# pdp8i.net
KiCad netlist of a schematic drawn in EAGLE
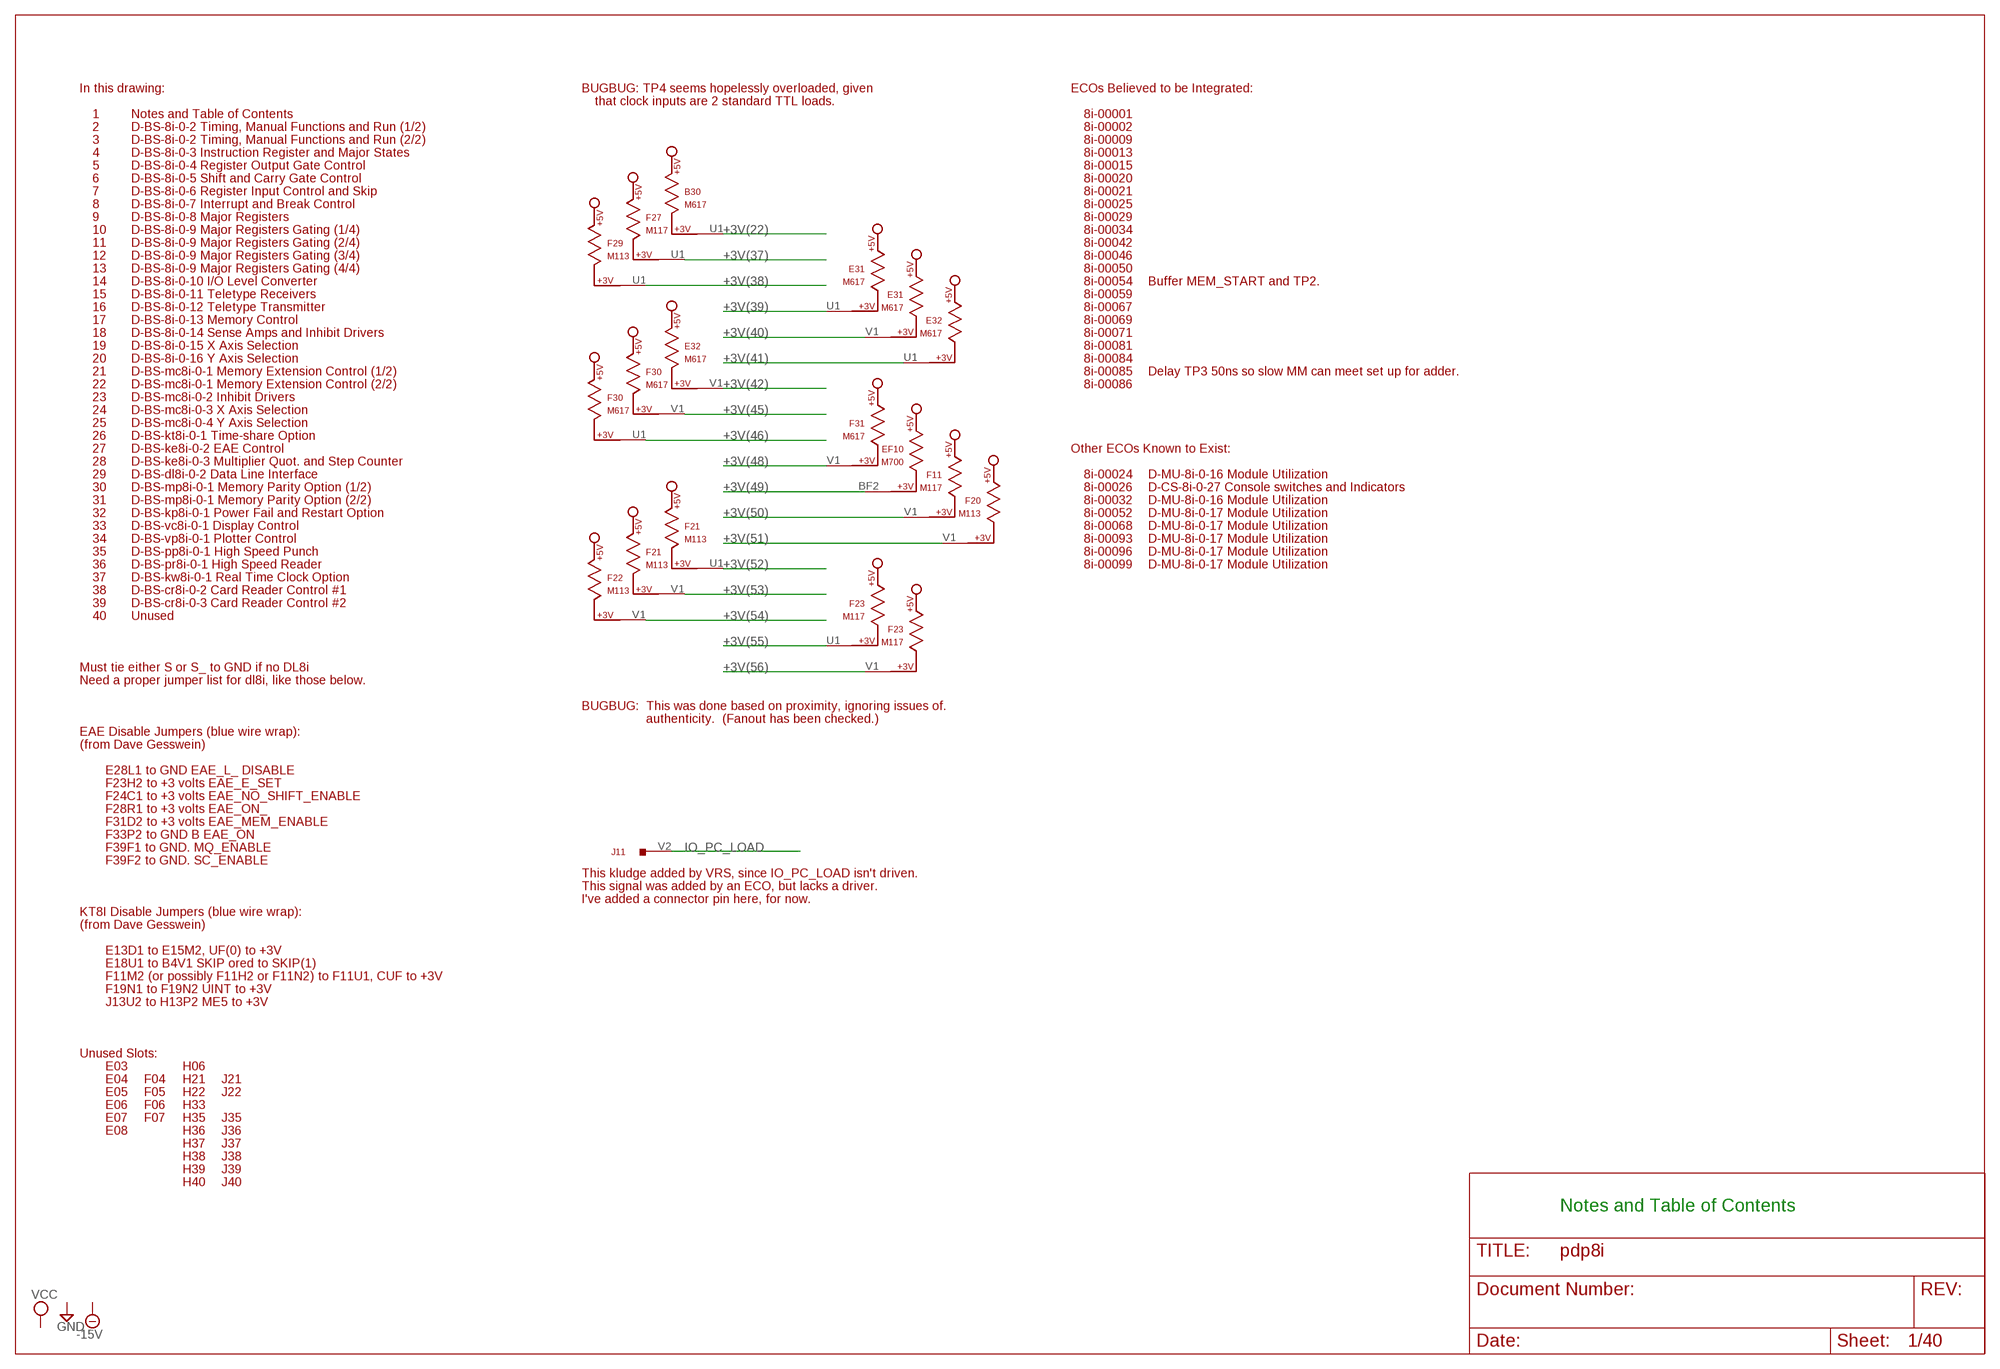
[diagram p0: schematic, sheet 1]
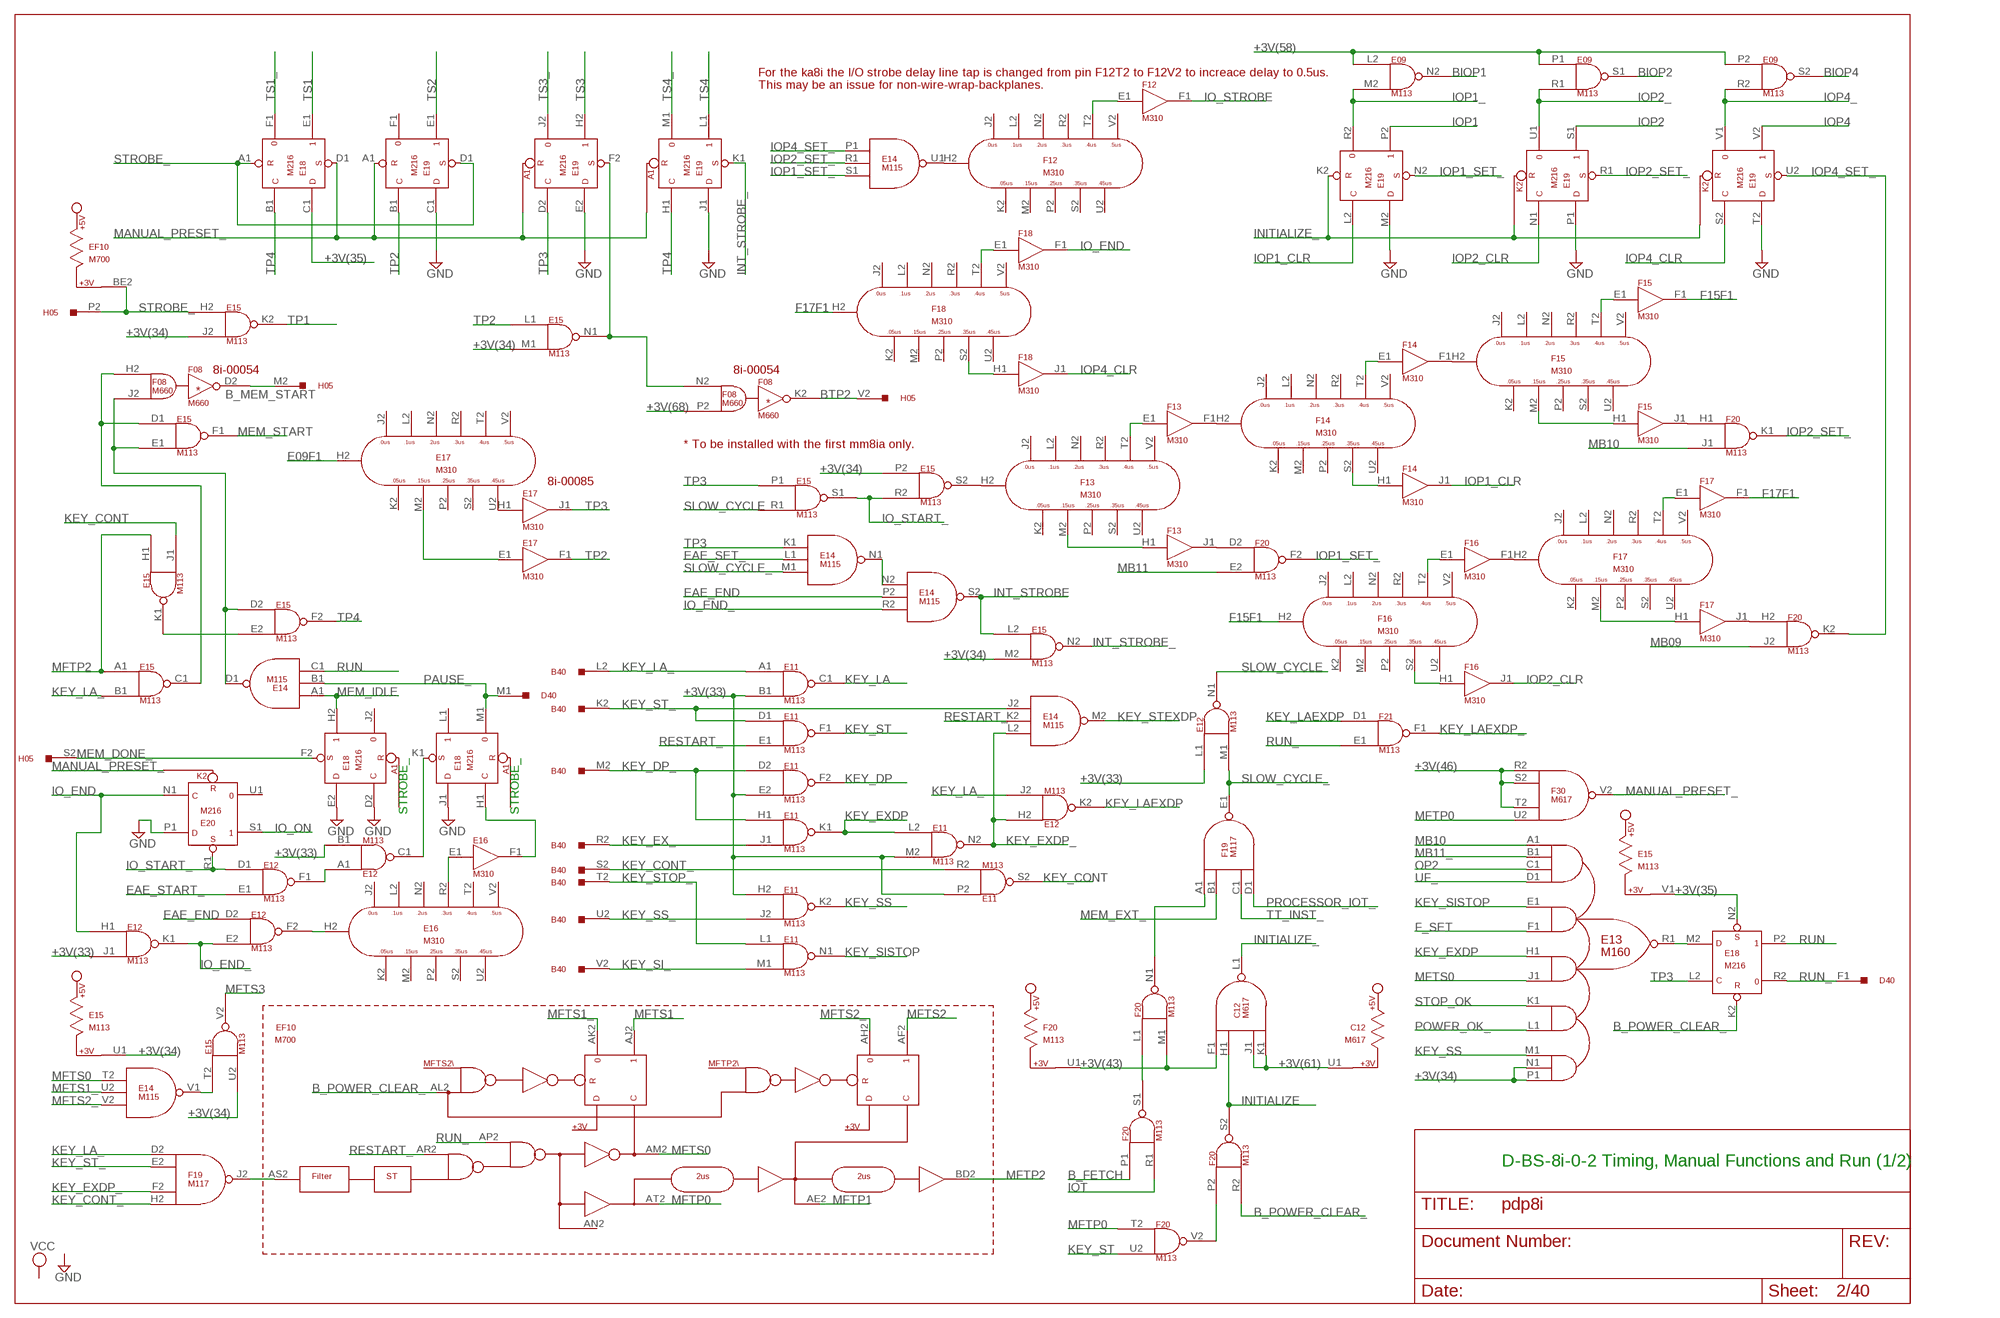
[diagram p1: schematic, sheet 2]
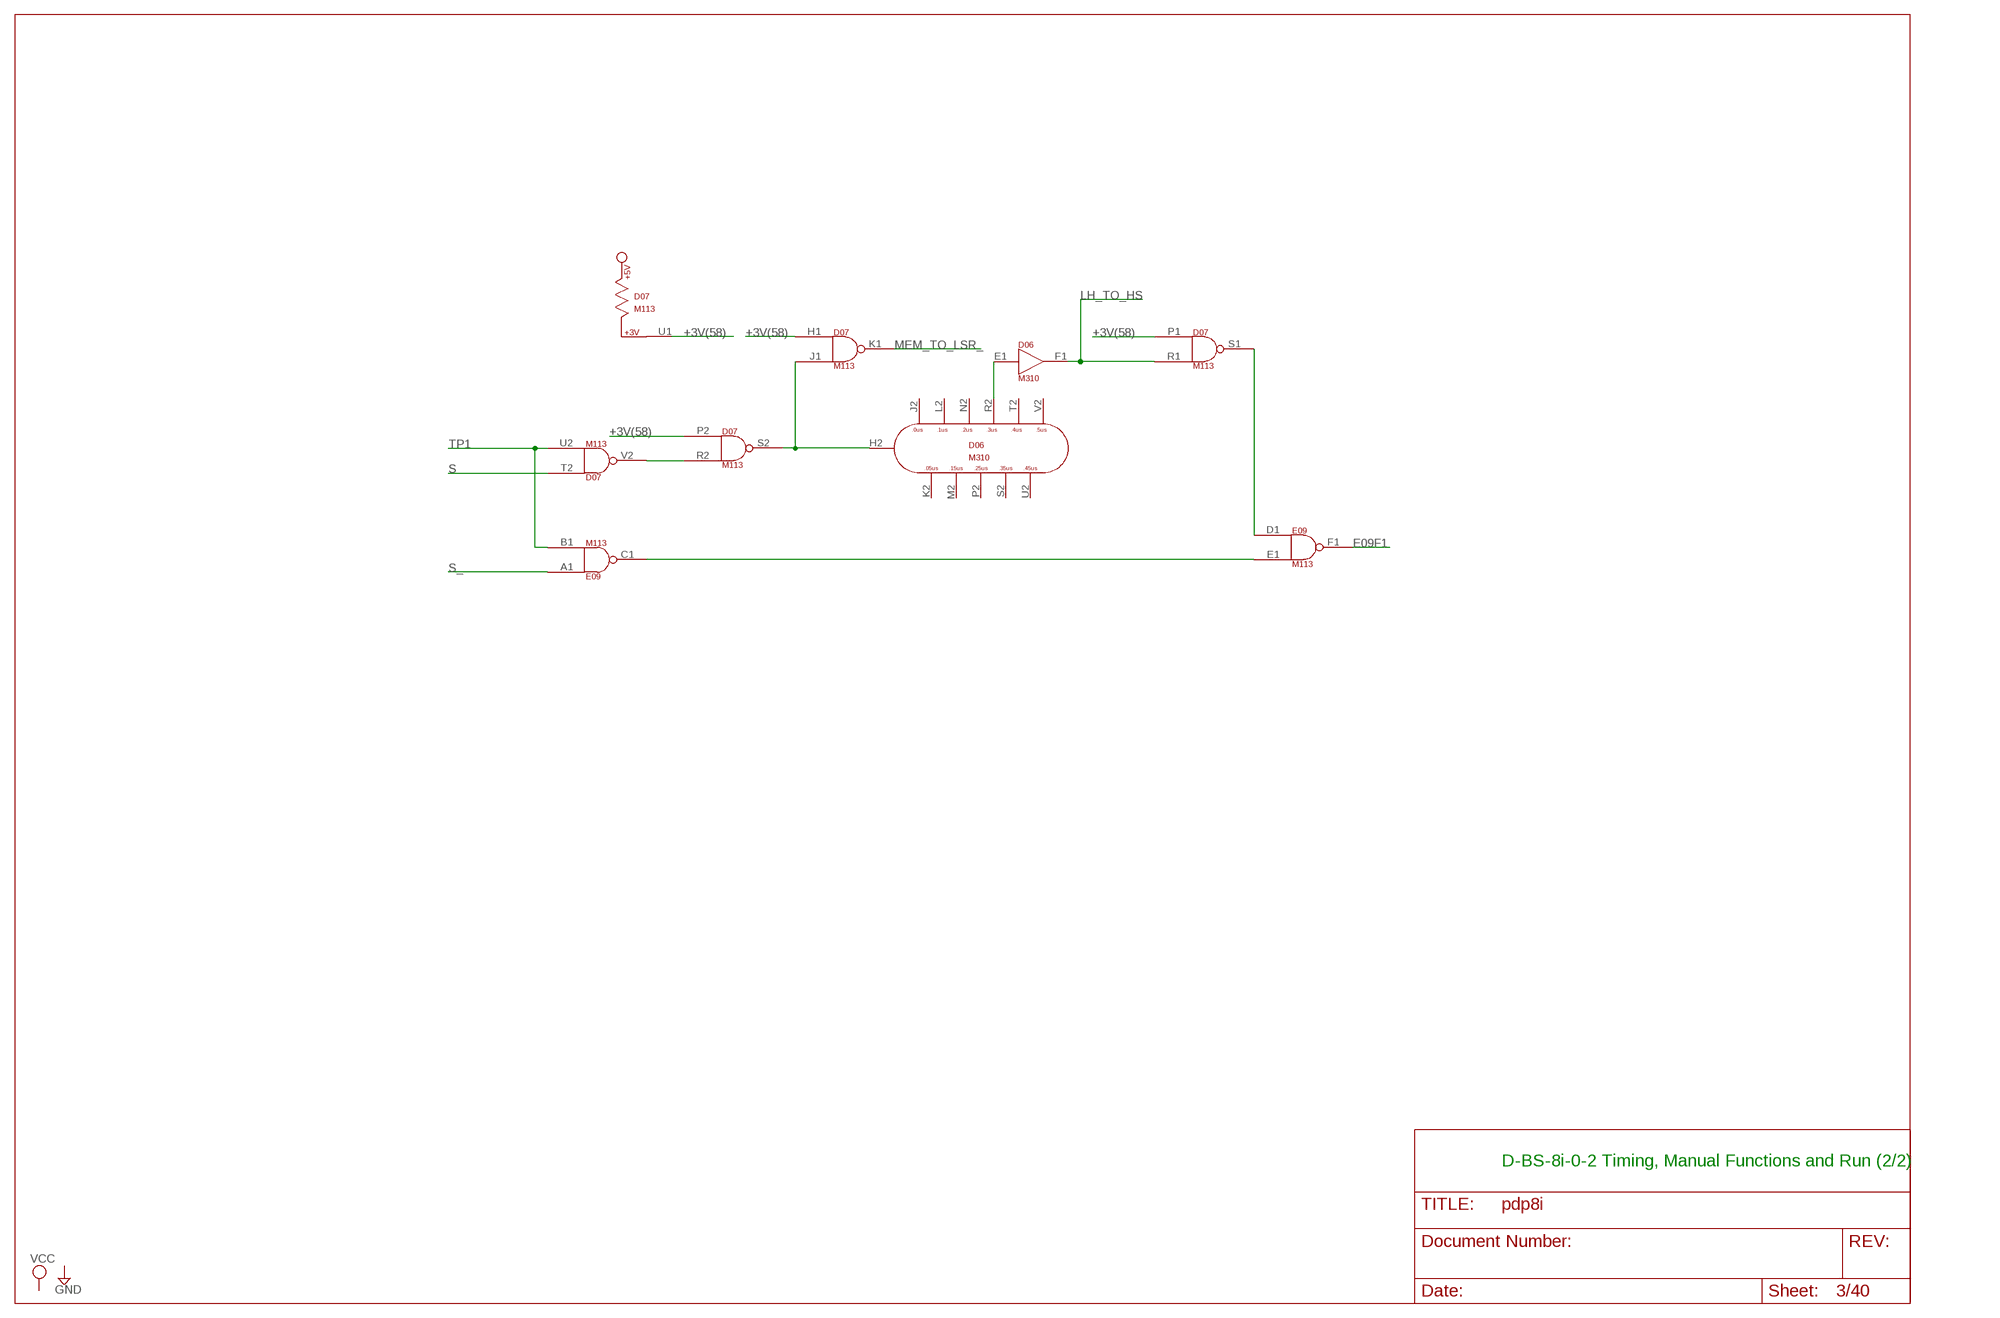
[diagram p2: schematic, sheet 3]
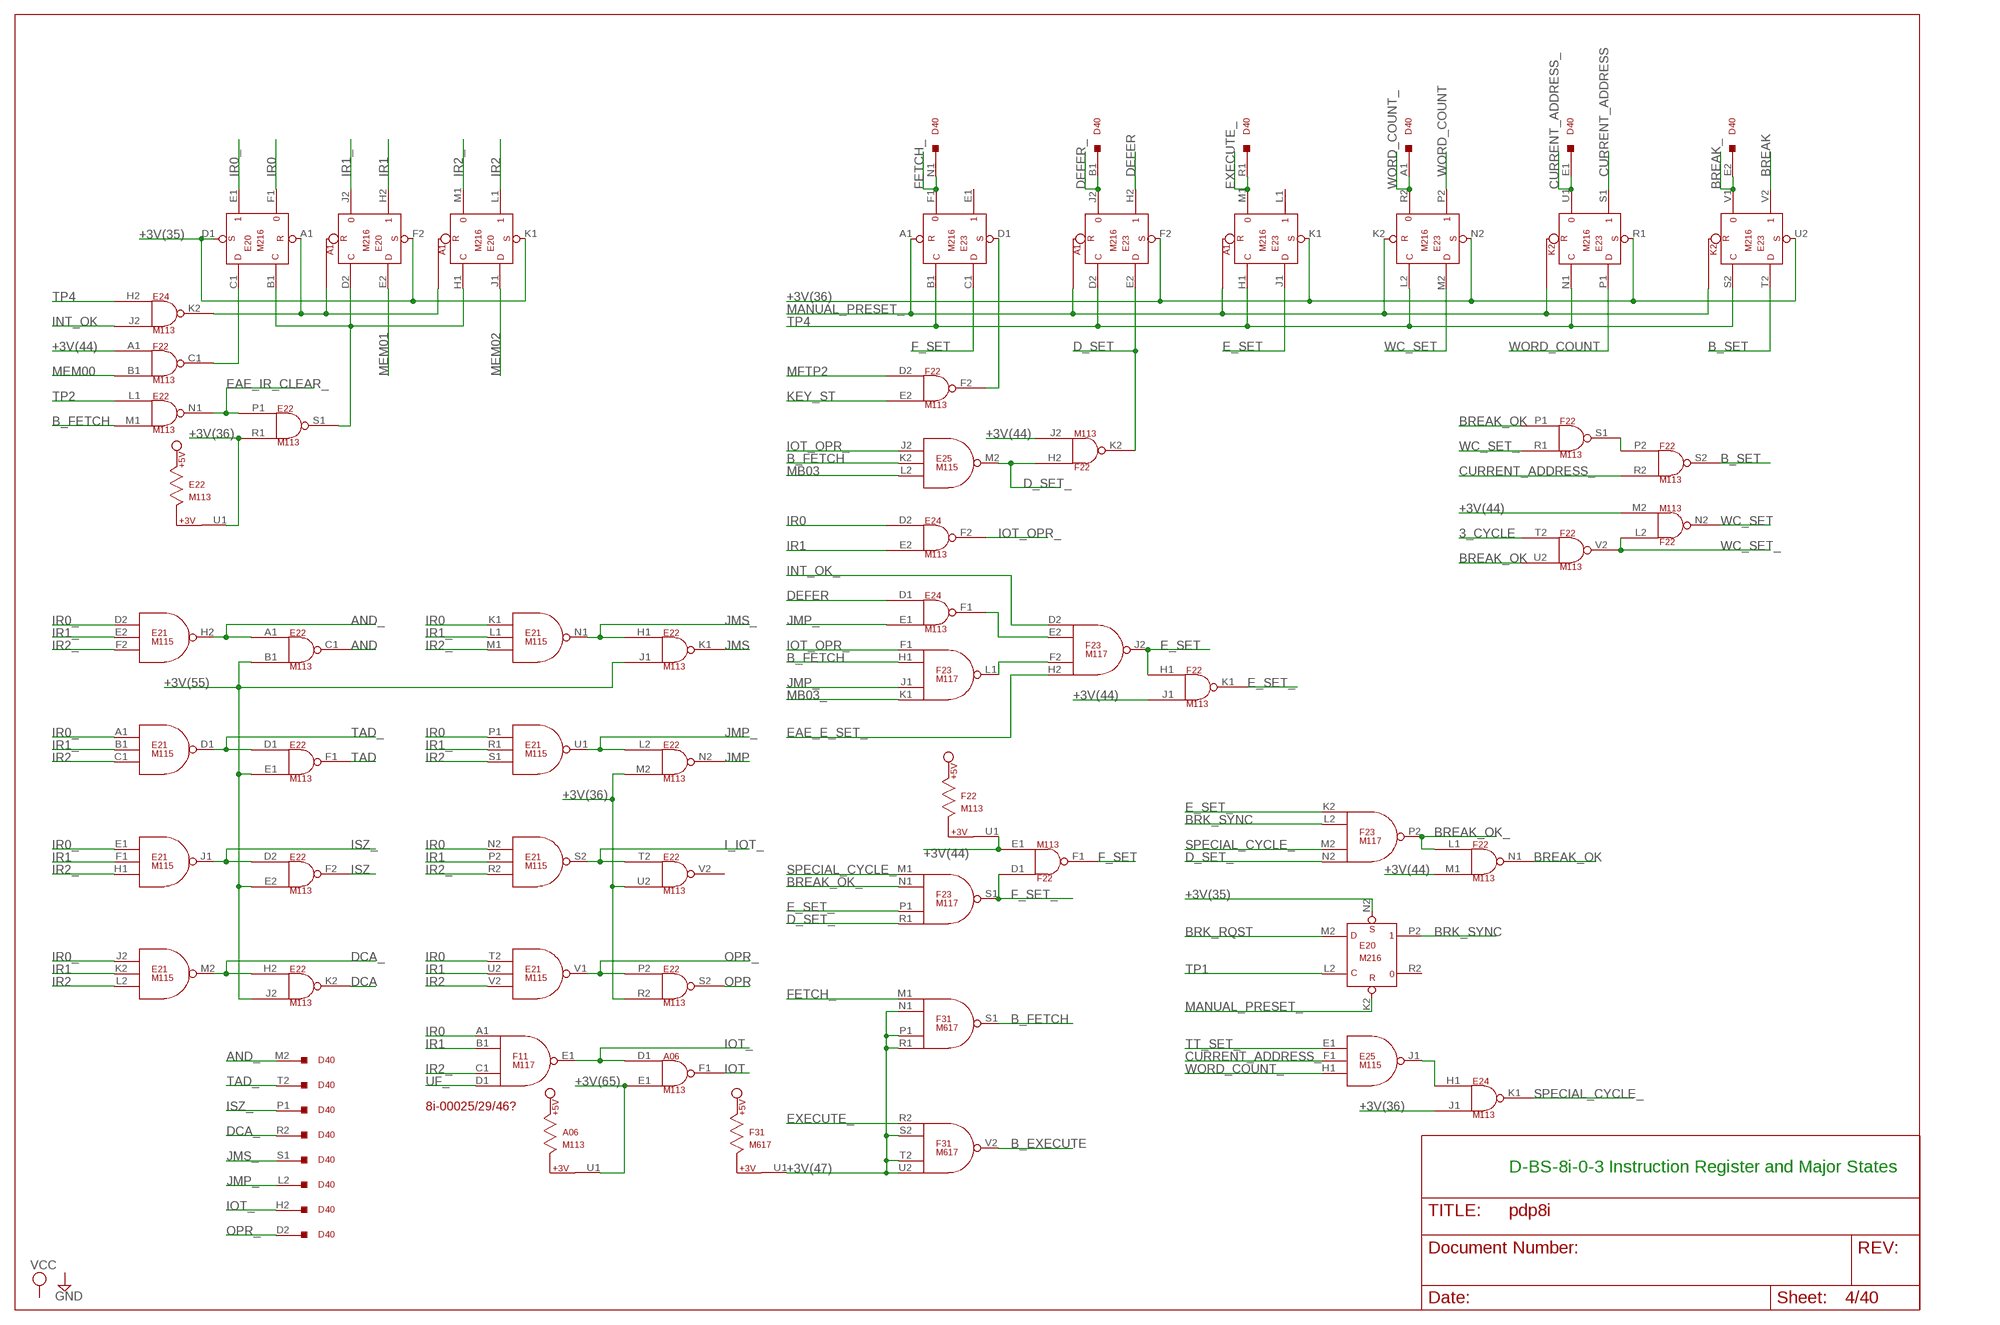
[diagram p3: schematic, sheet 4]
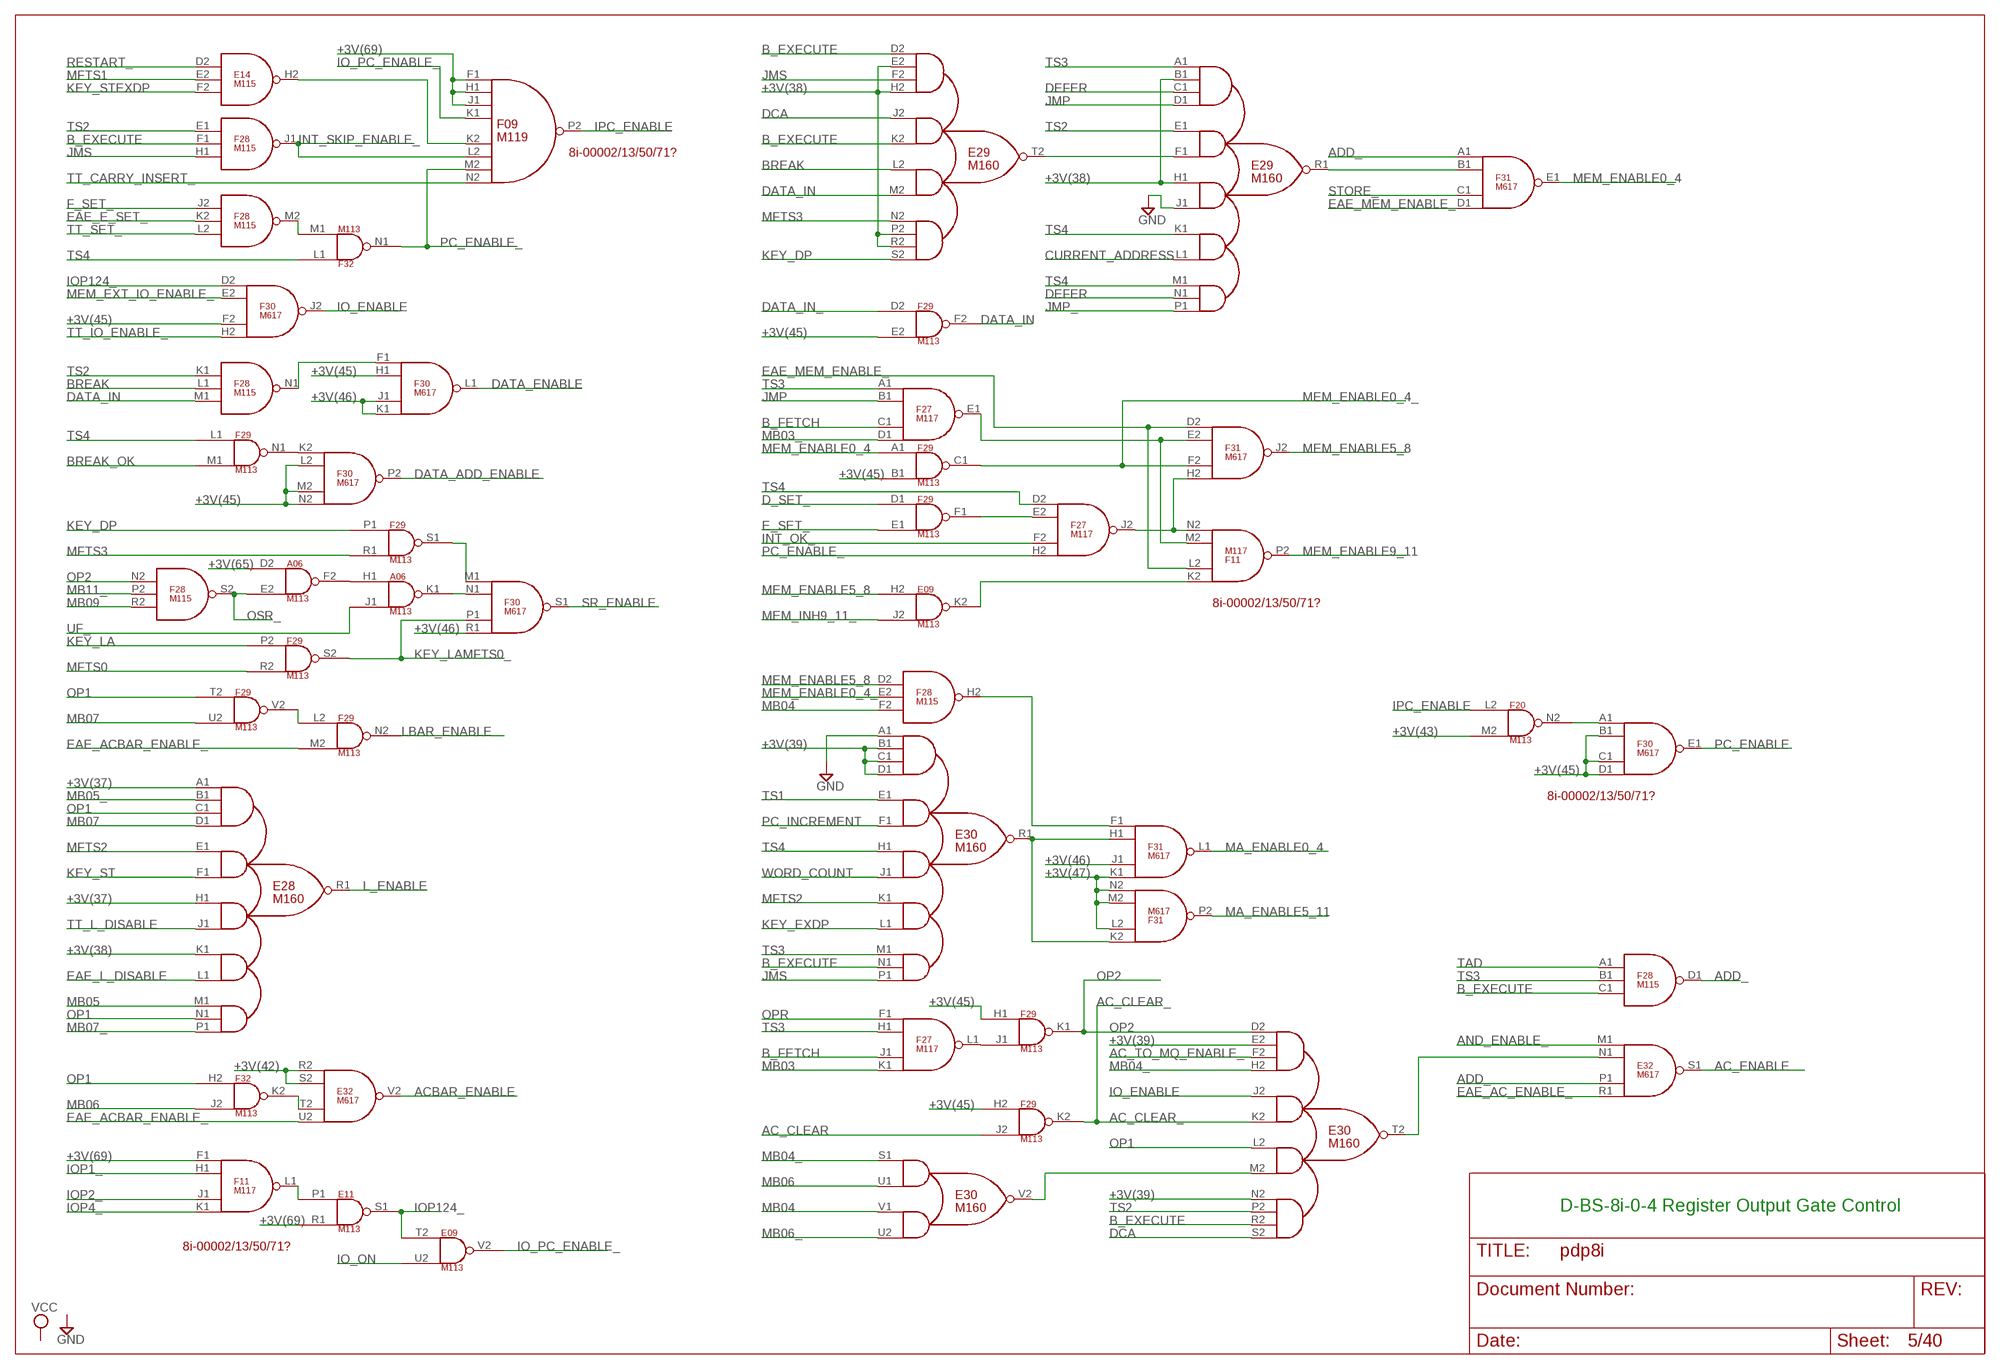
[diagram p4: schematic, sheet 5]
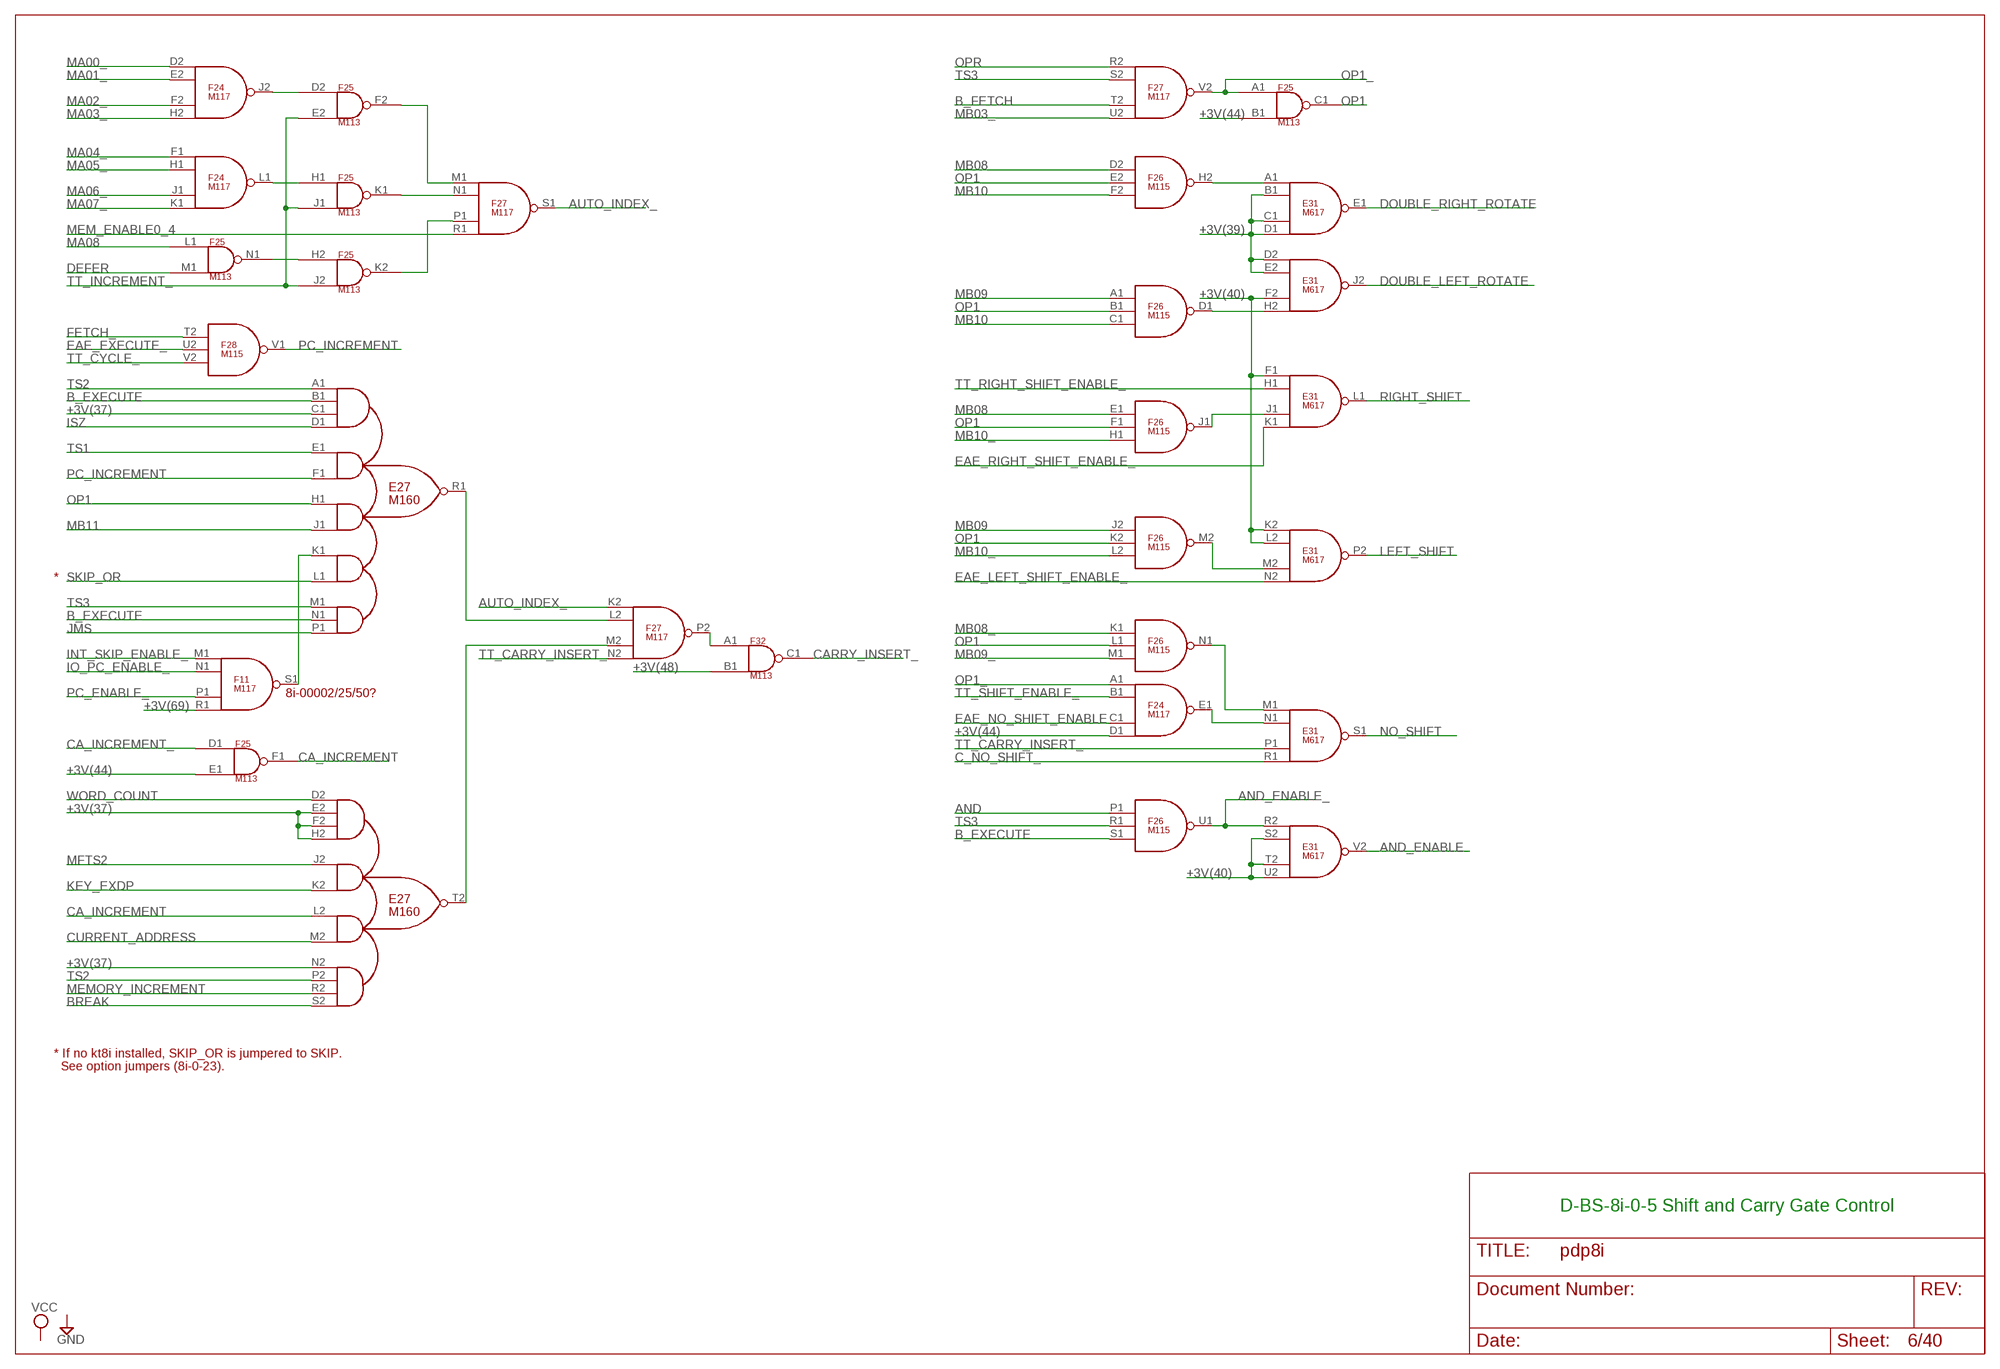
[diagram p5: schematic, sheet 6]
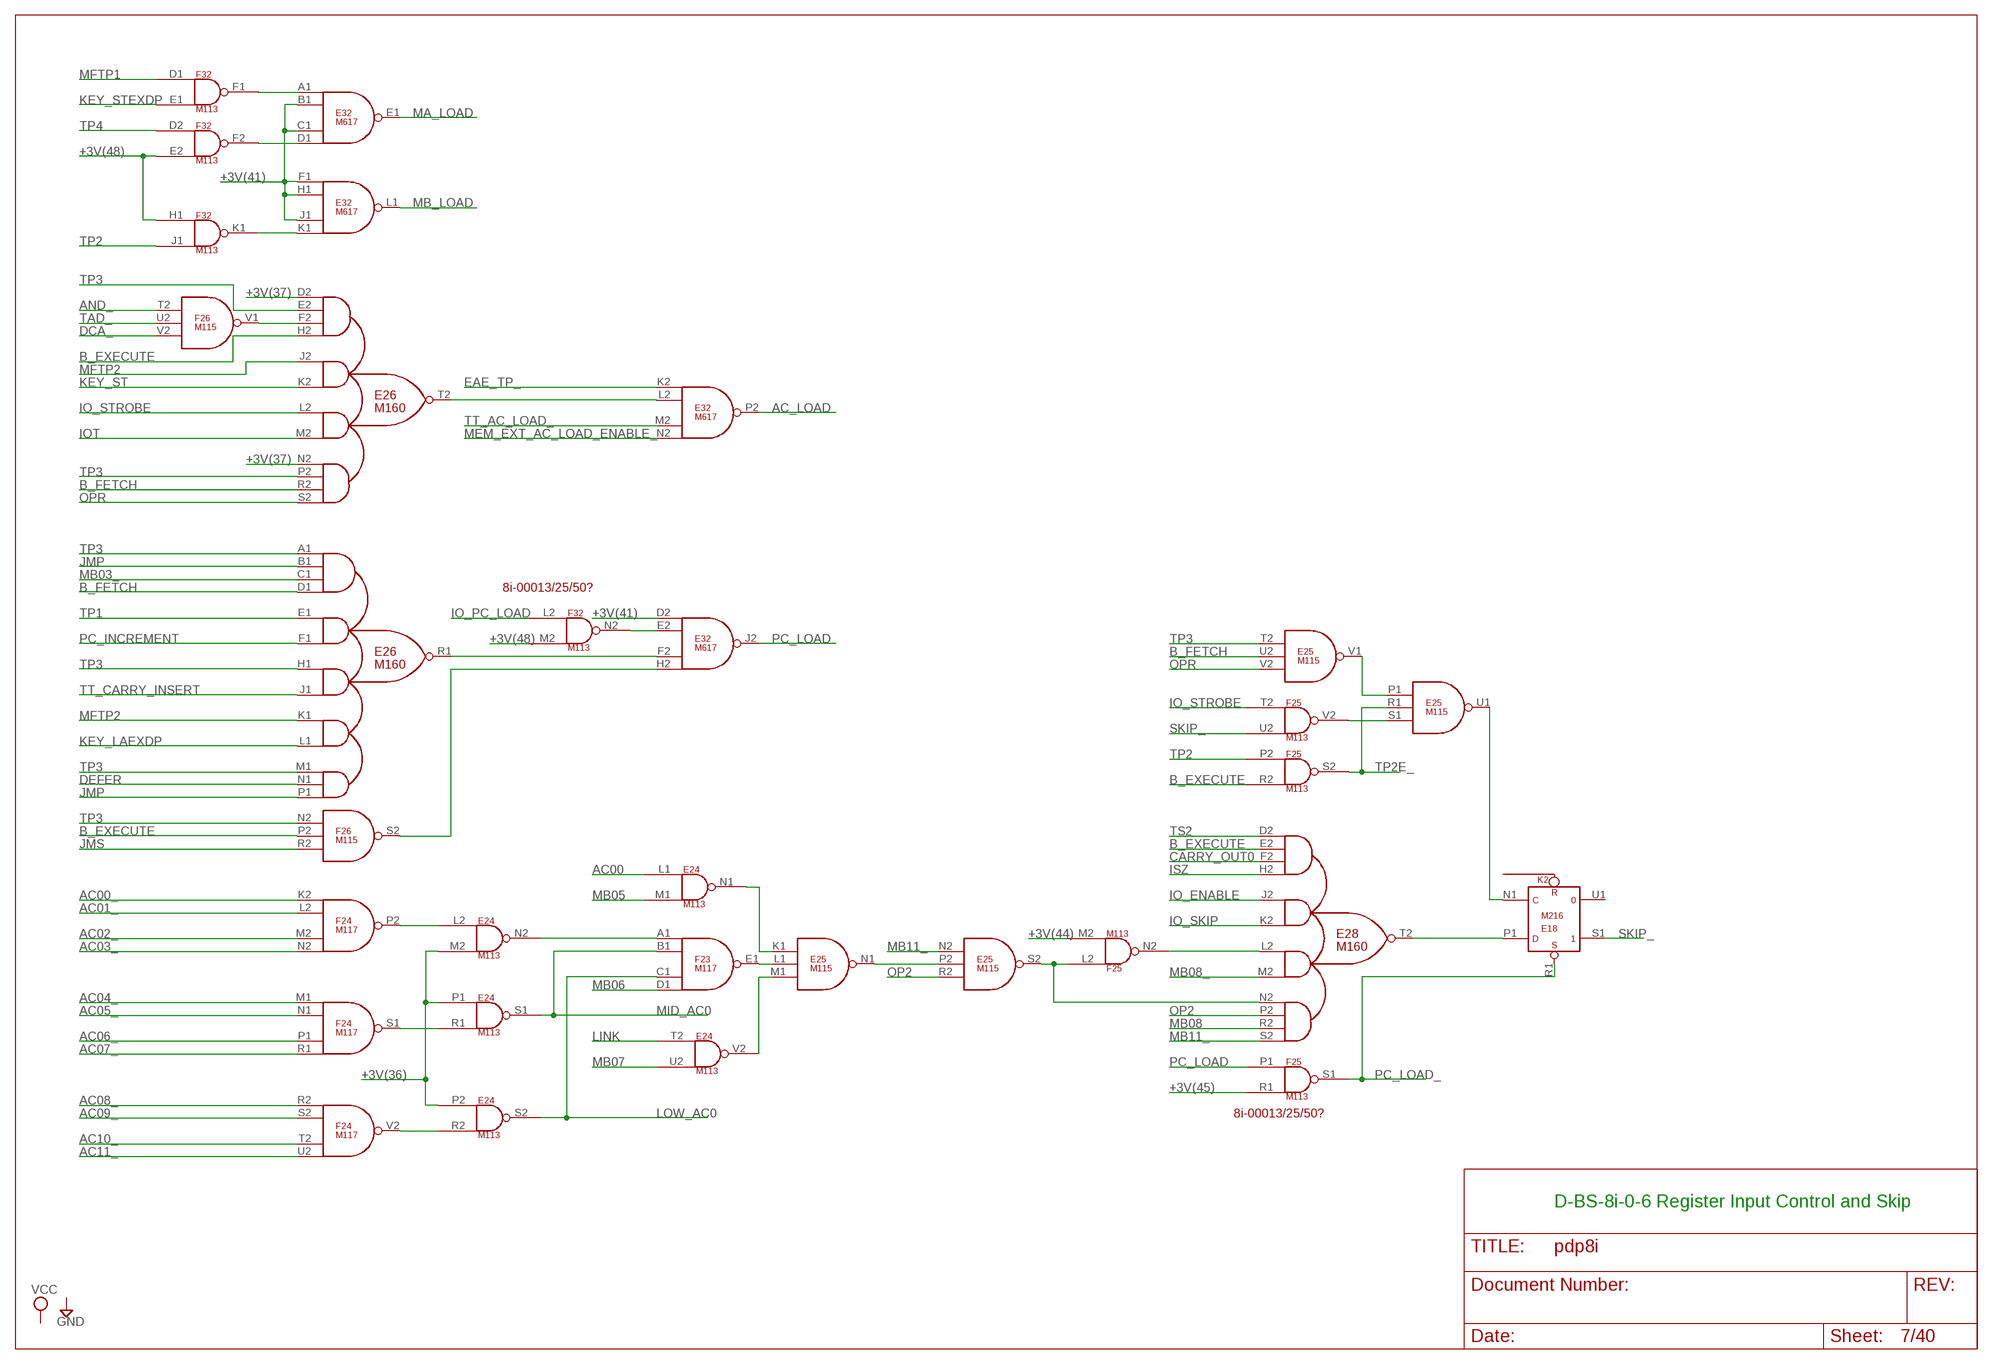
[diagram p6: schematic, sheet 7]
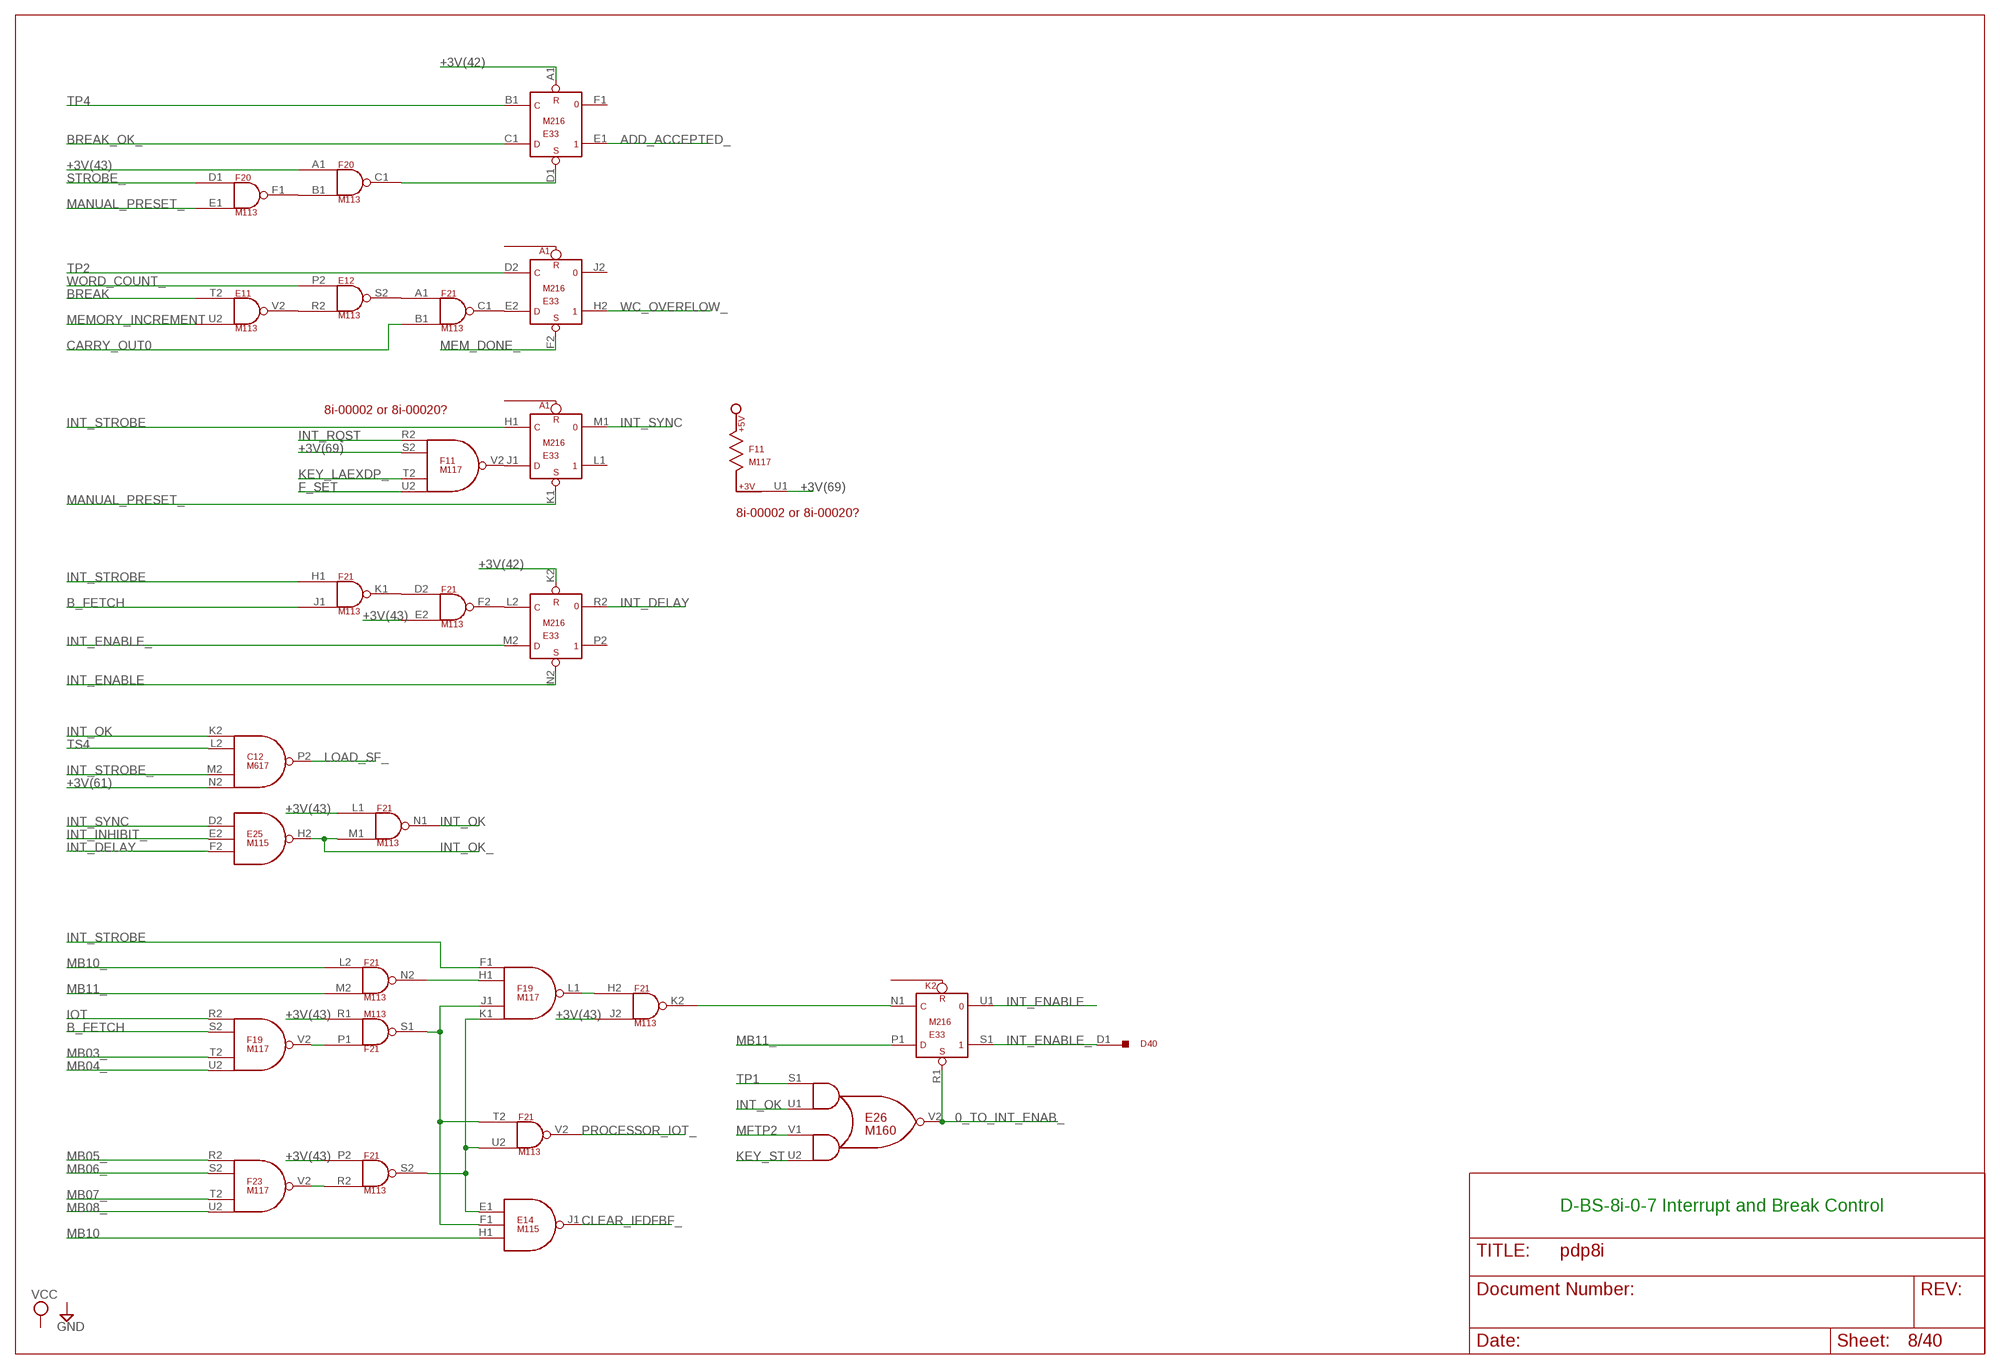
[diagram p7: schematic, sheet 8]
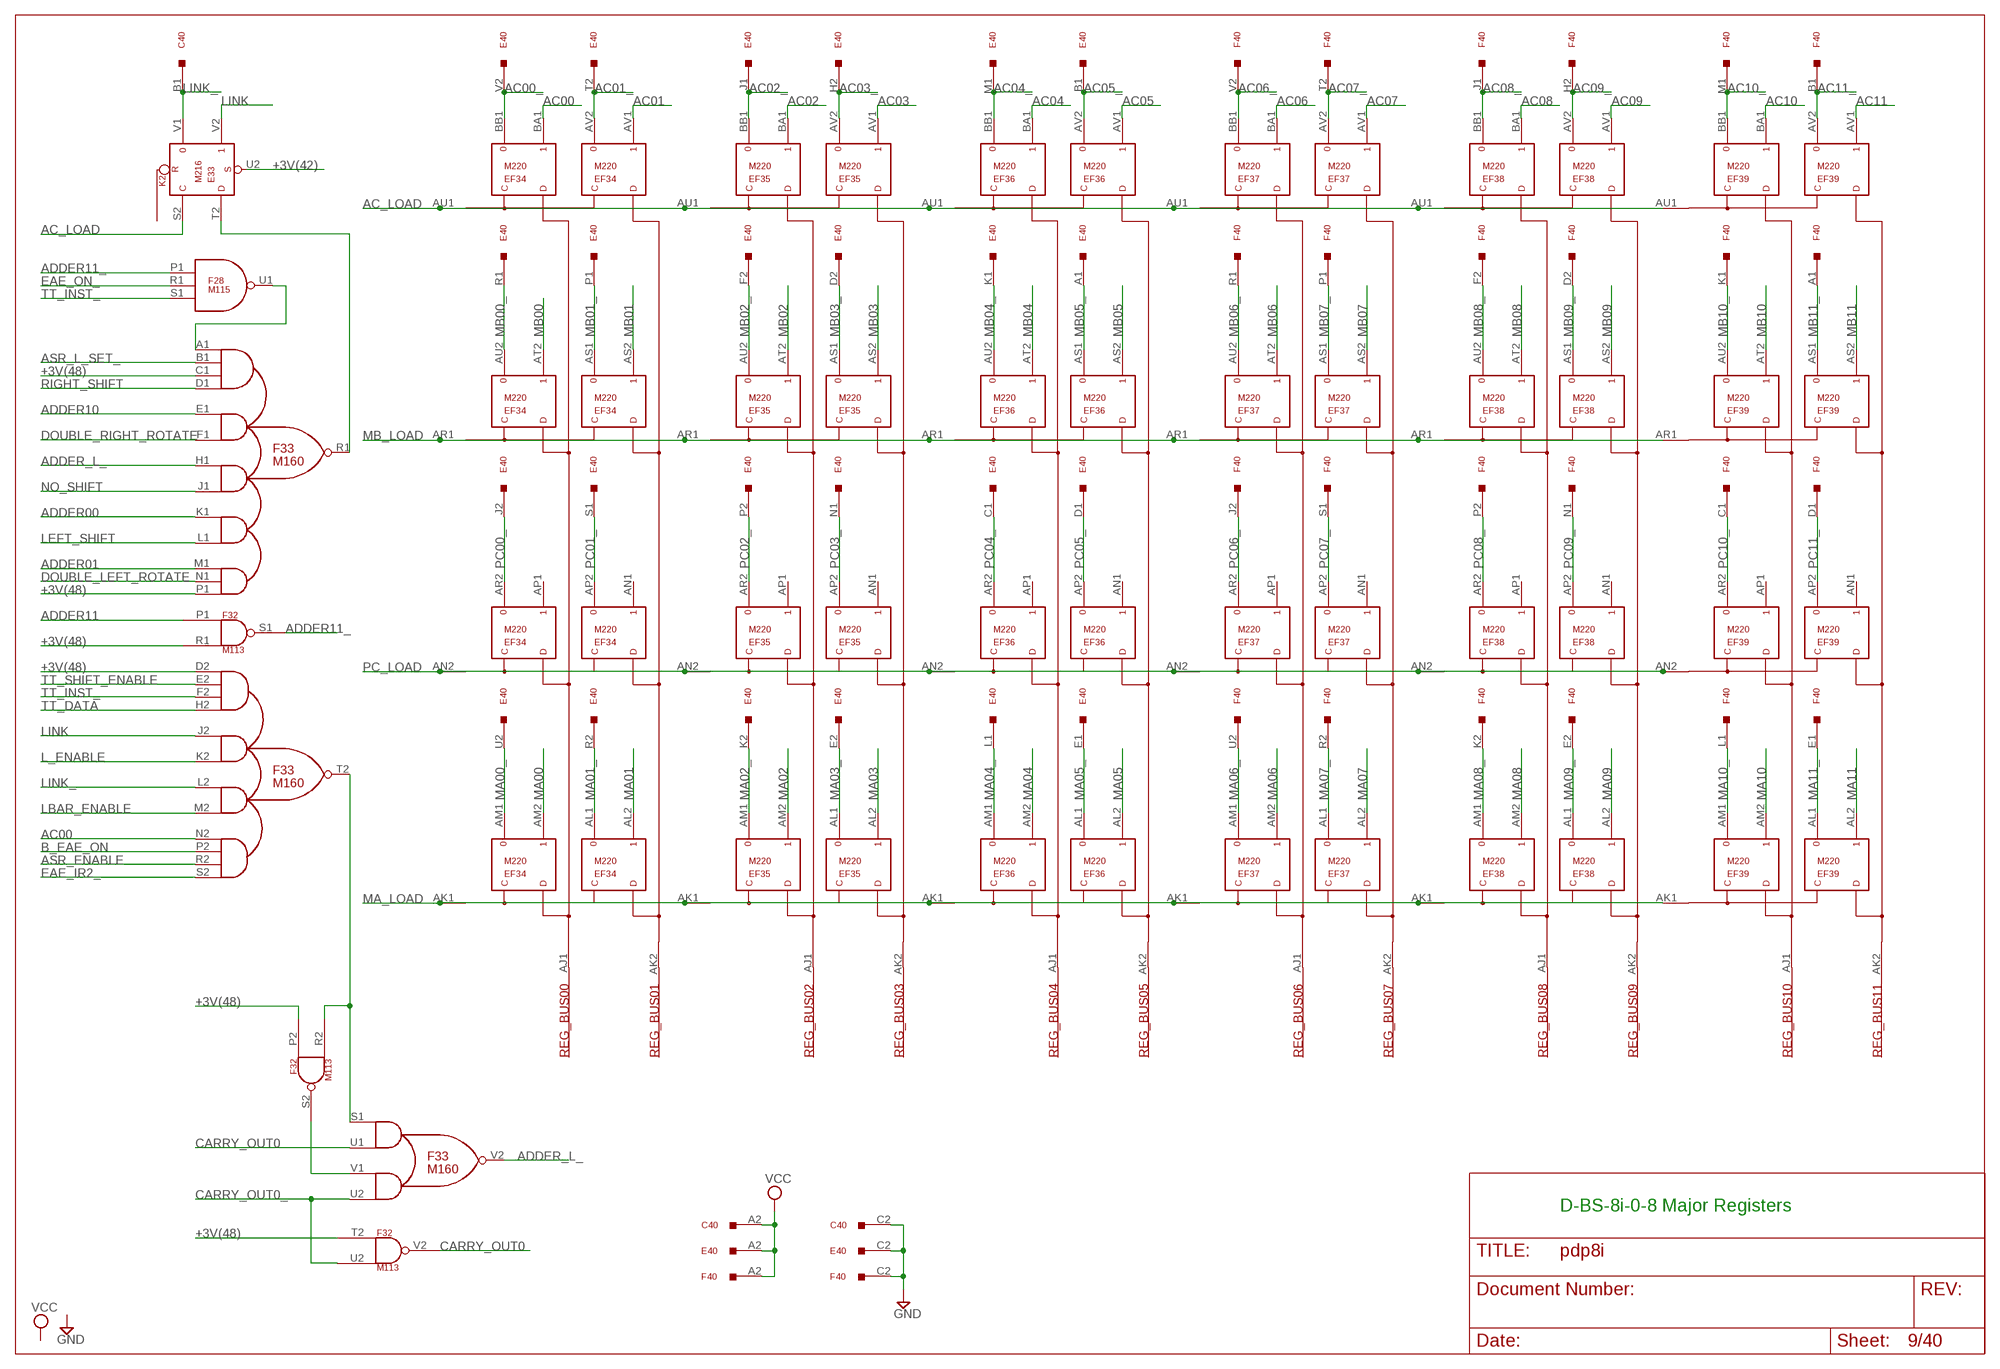
[diagram p8: schematic, sheet 9]
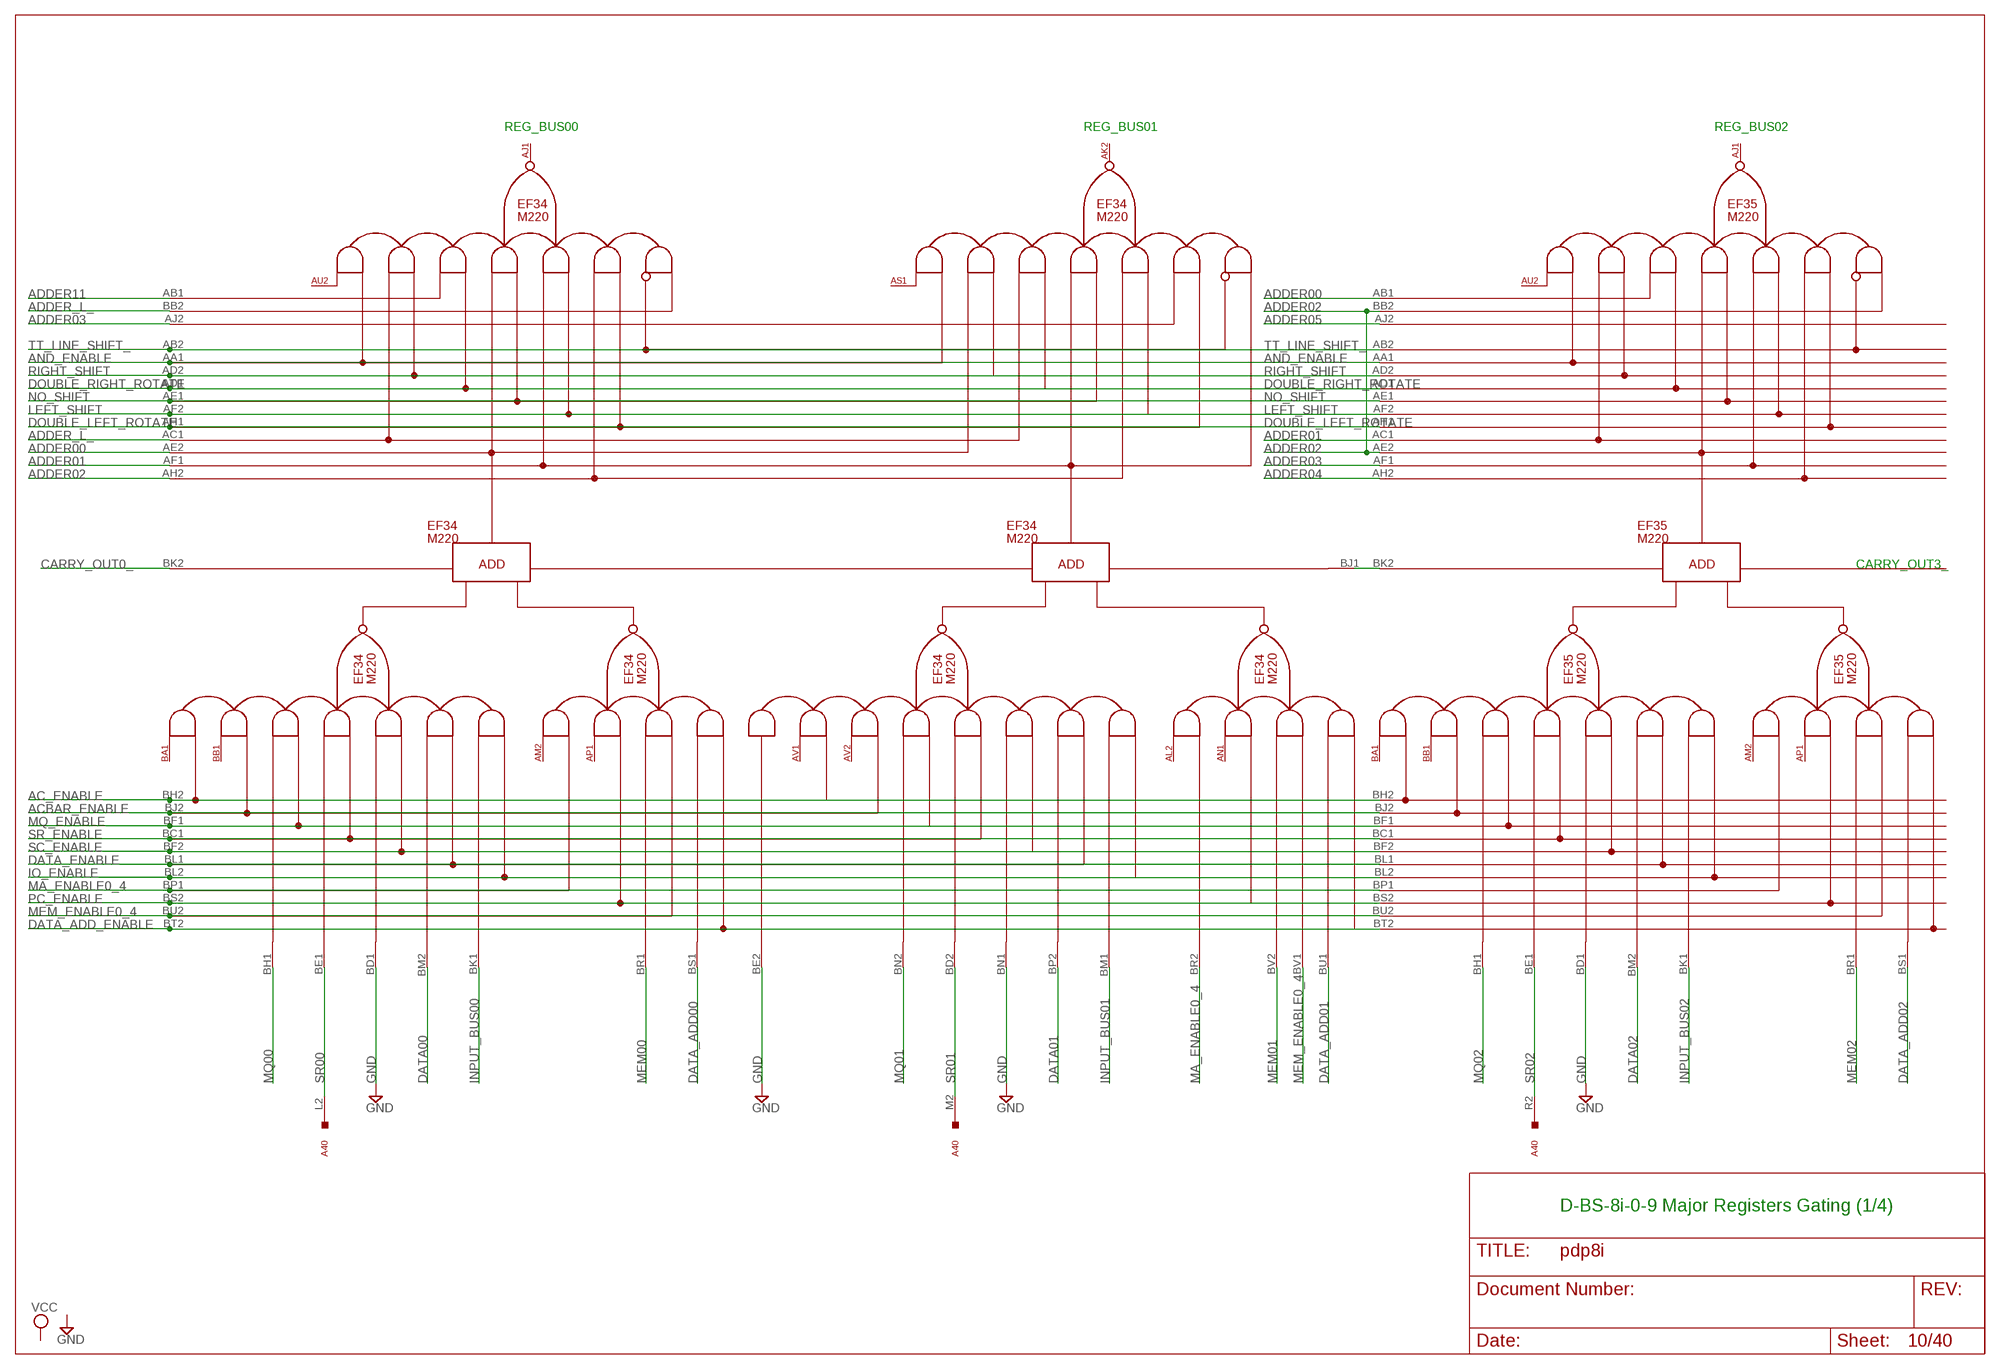
[diagram p9: schematic, sheet 10]
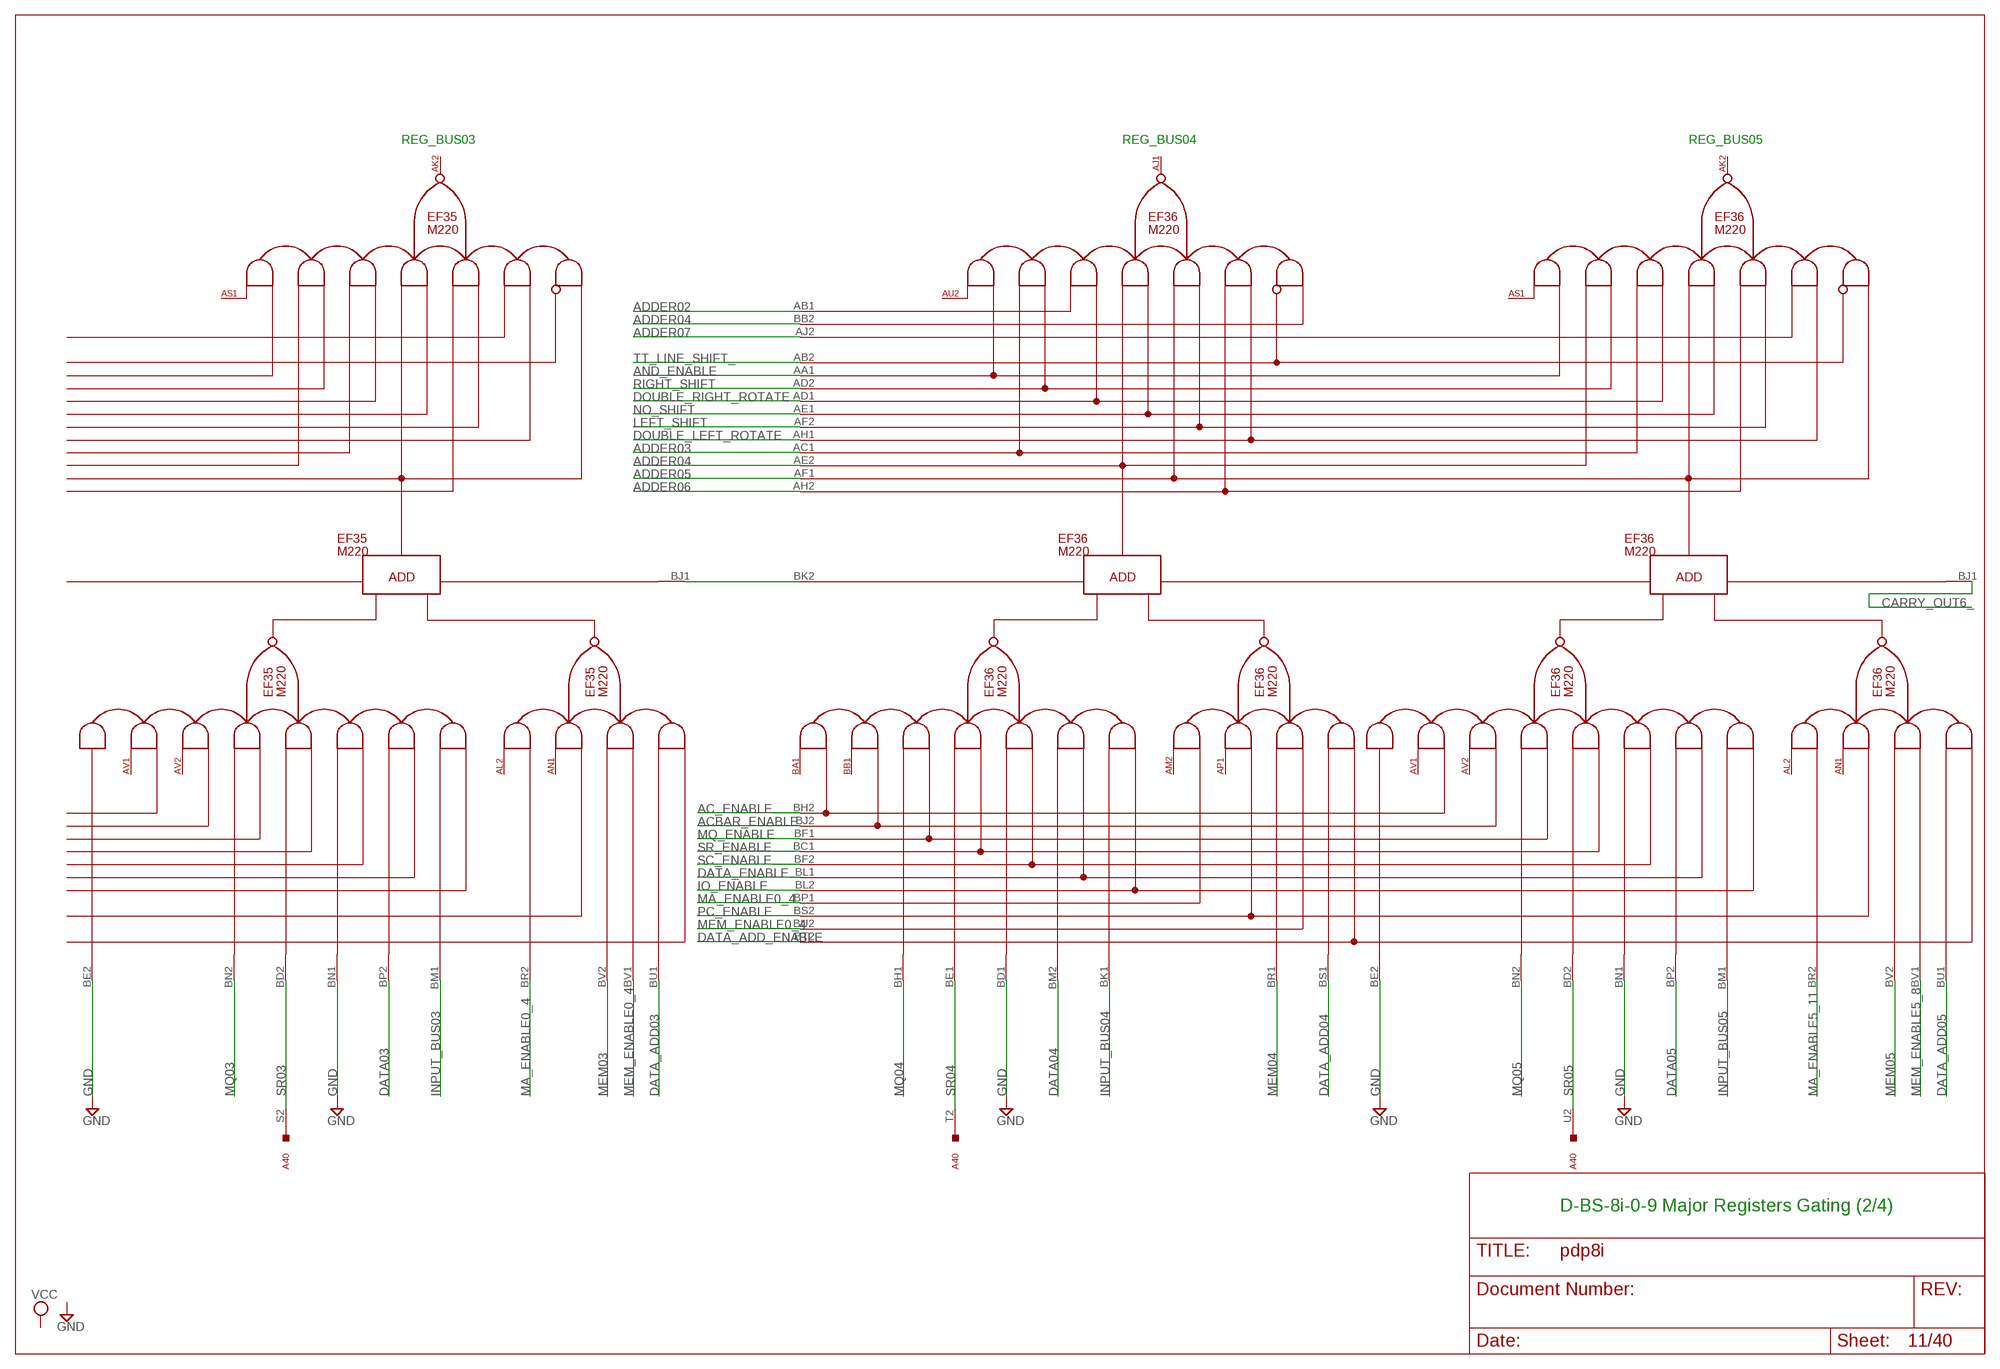
[diagram p10: schematic, sheet 11]
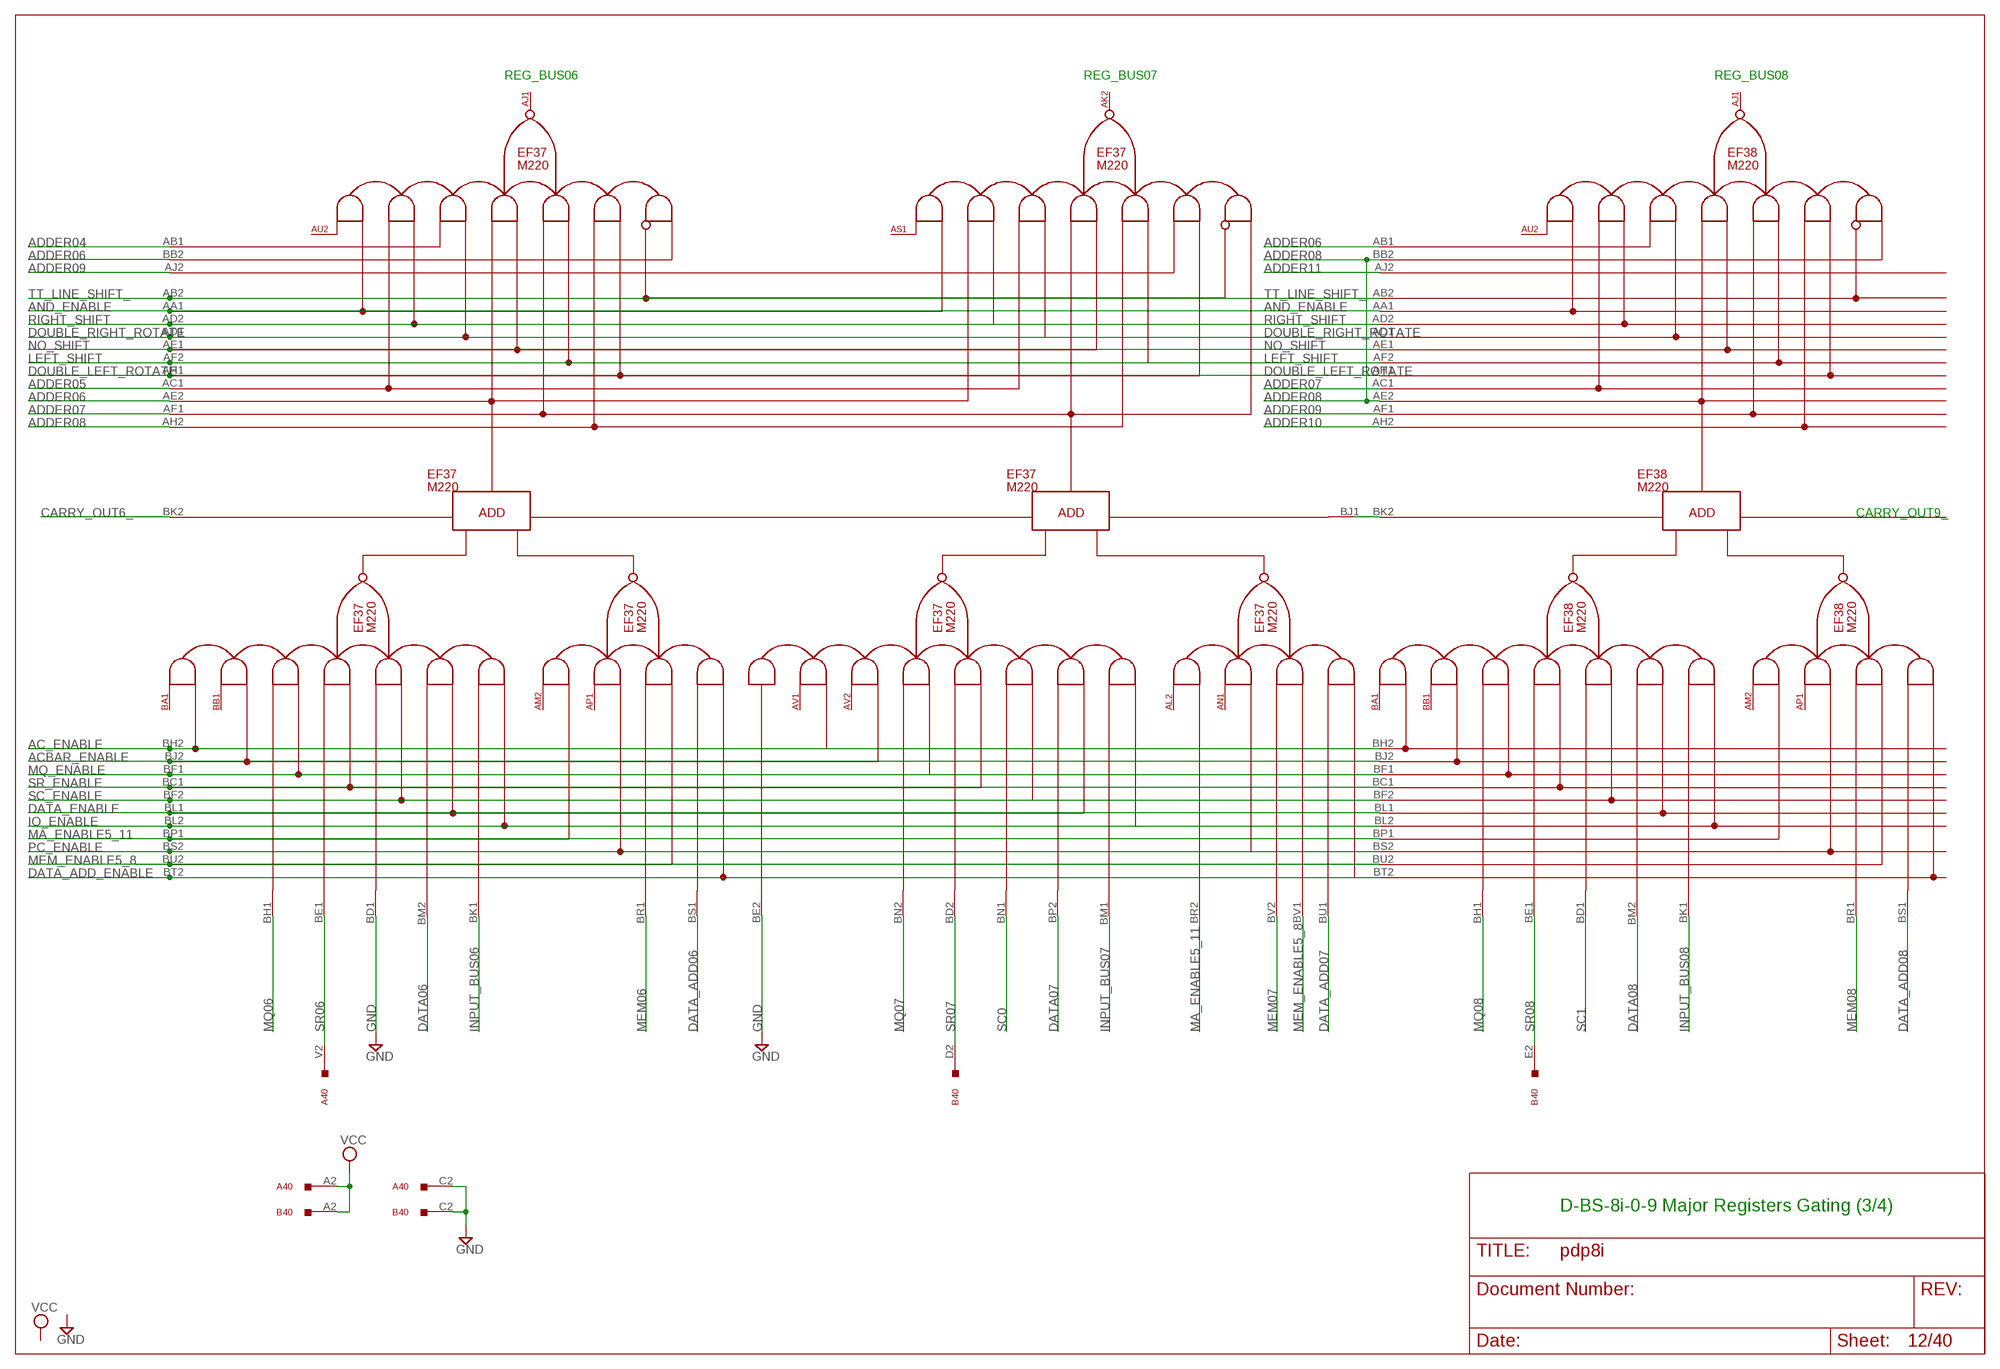
[diagram p11: schematic, sheet 12]
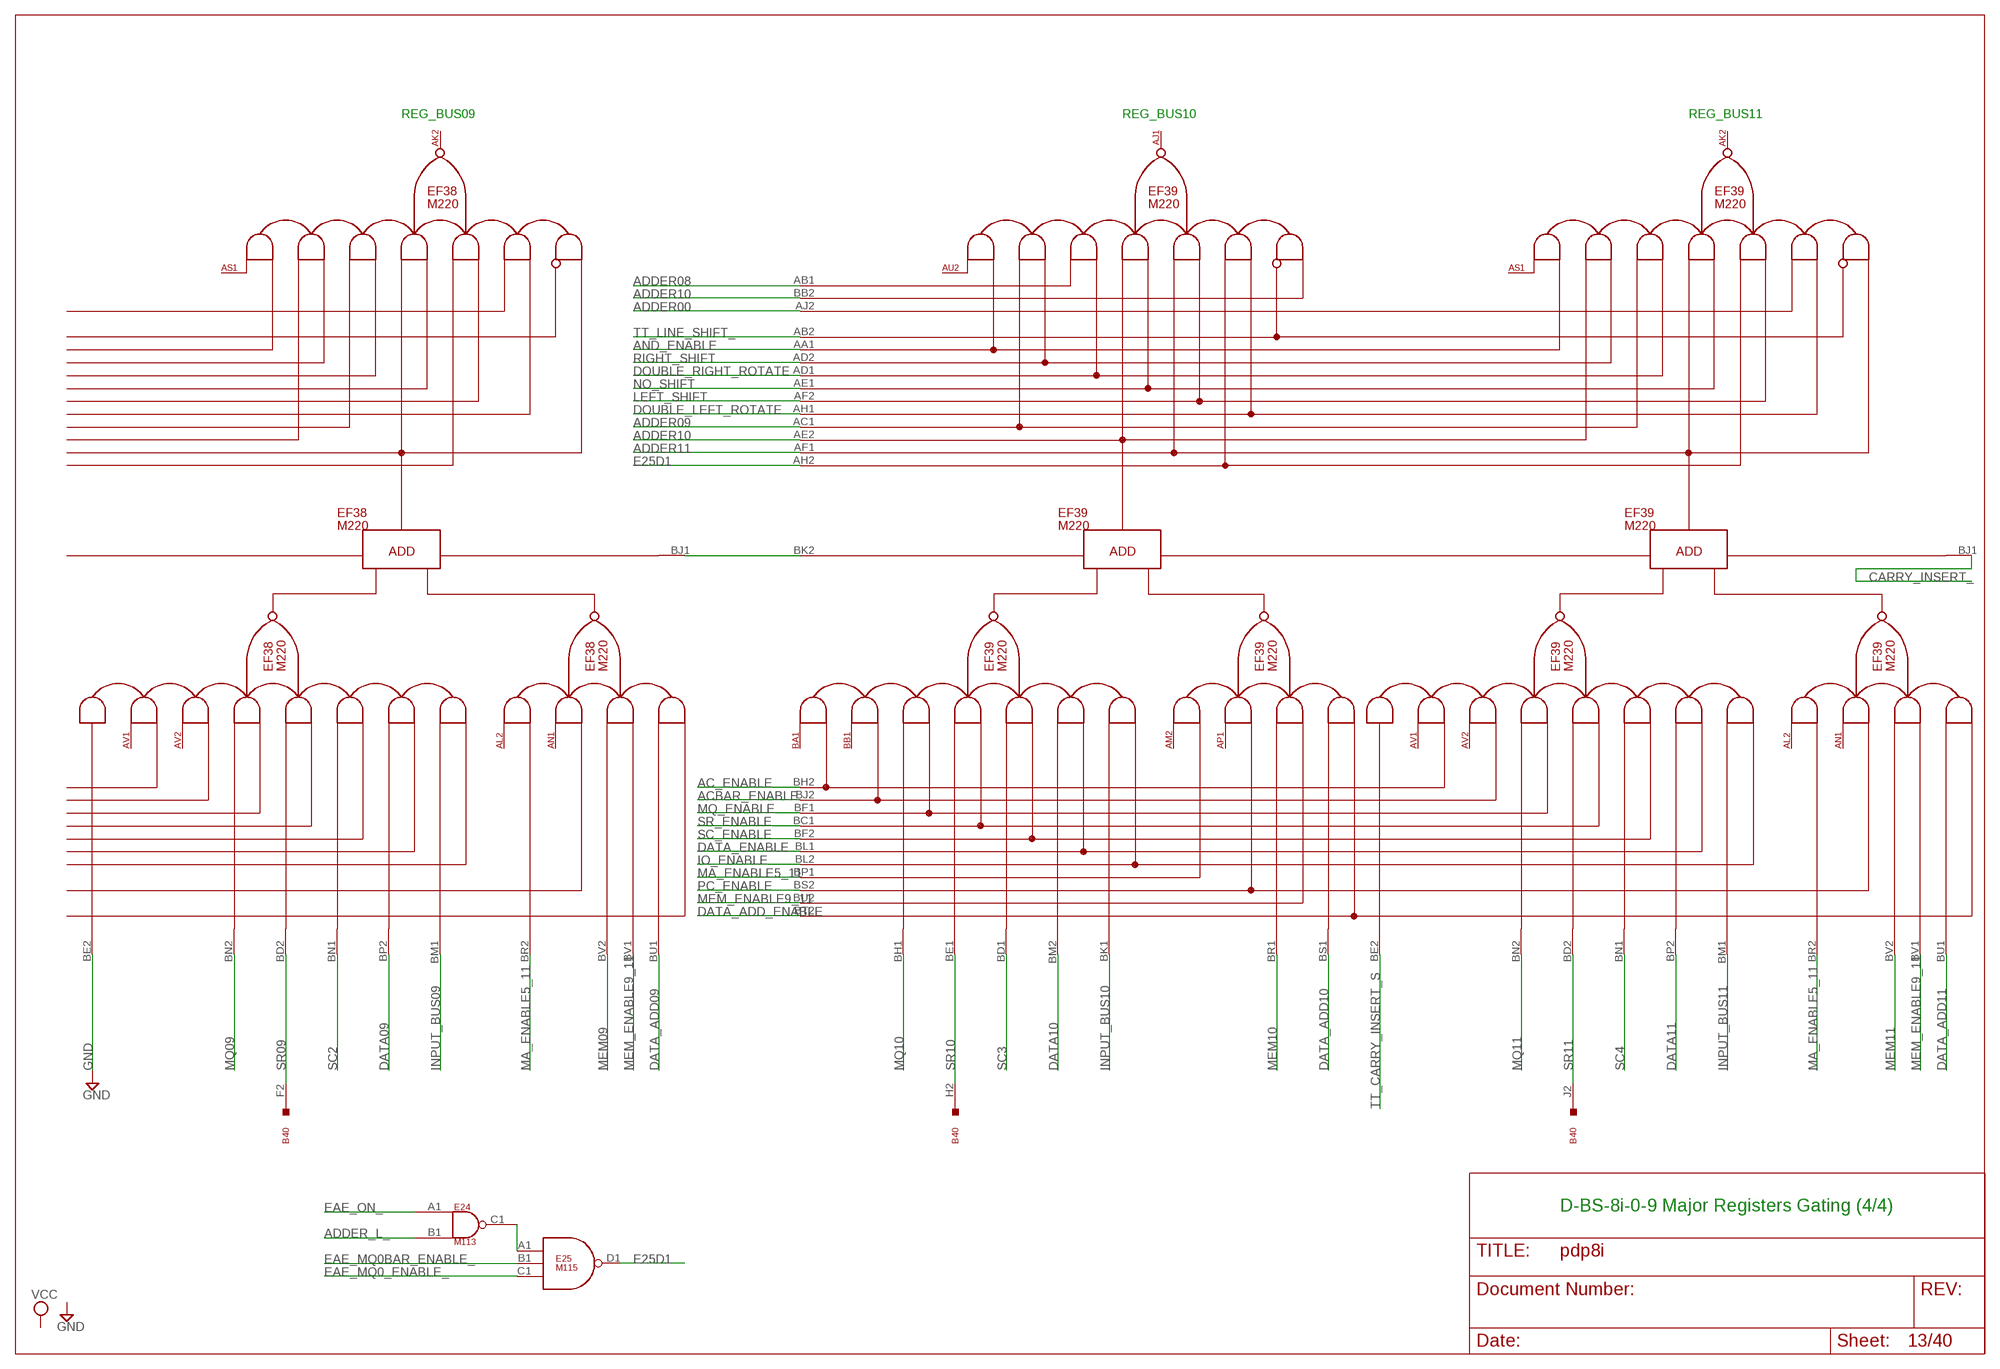
[diagram p12: schematic, sheet 13]
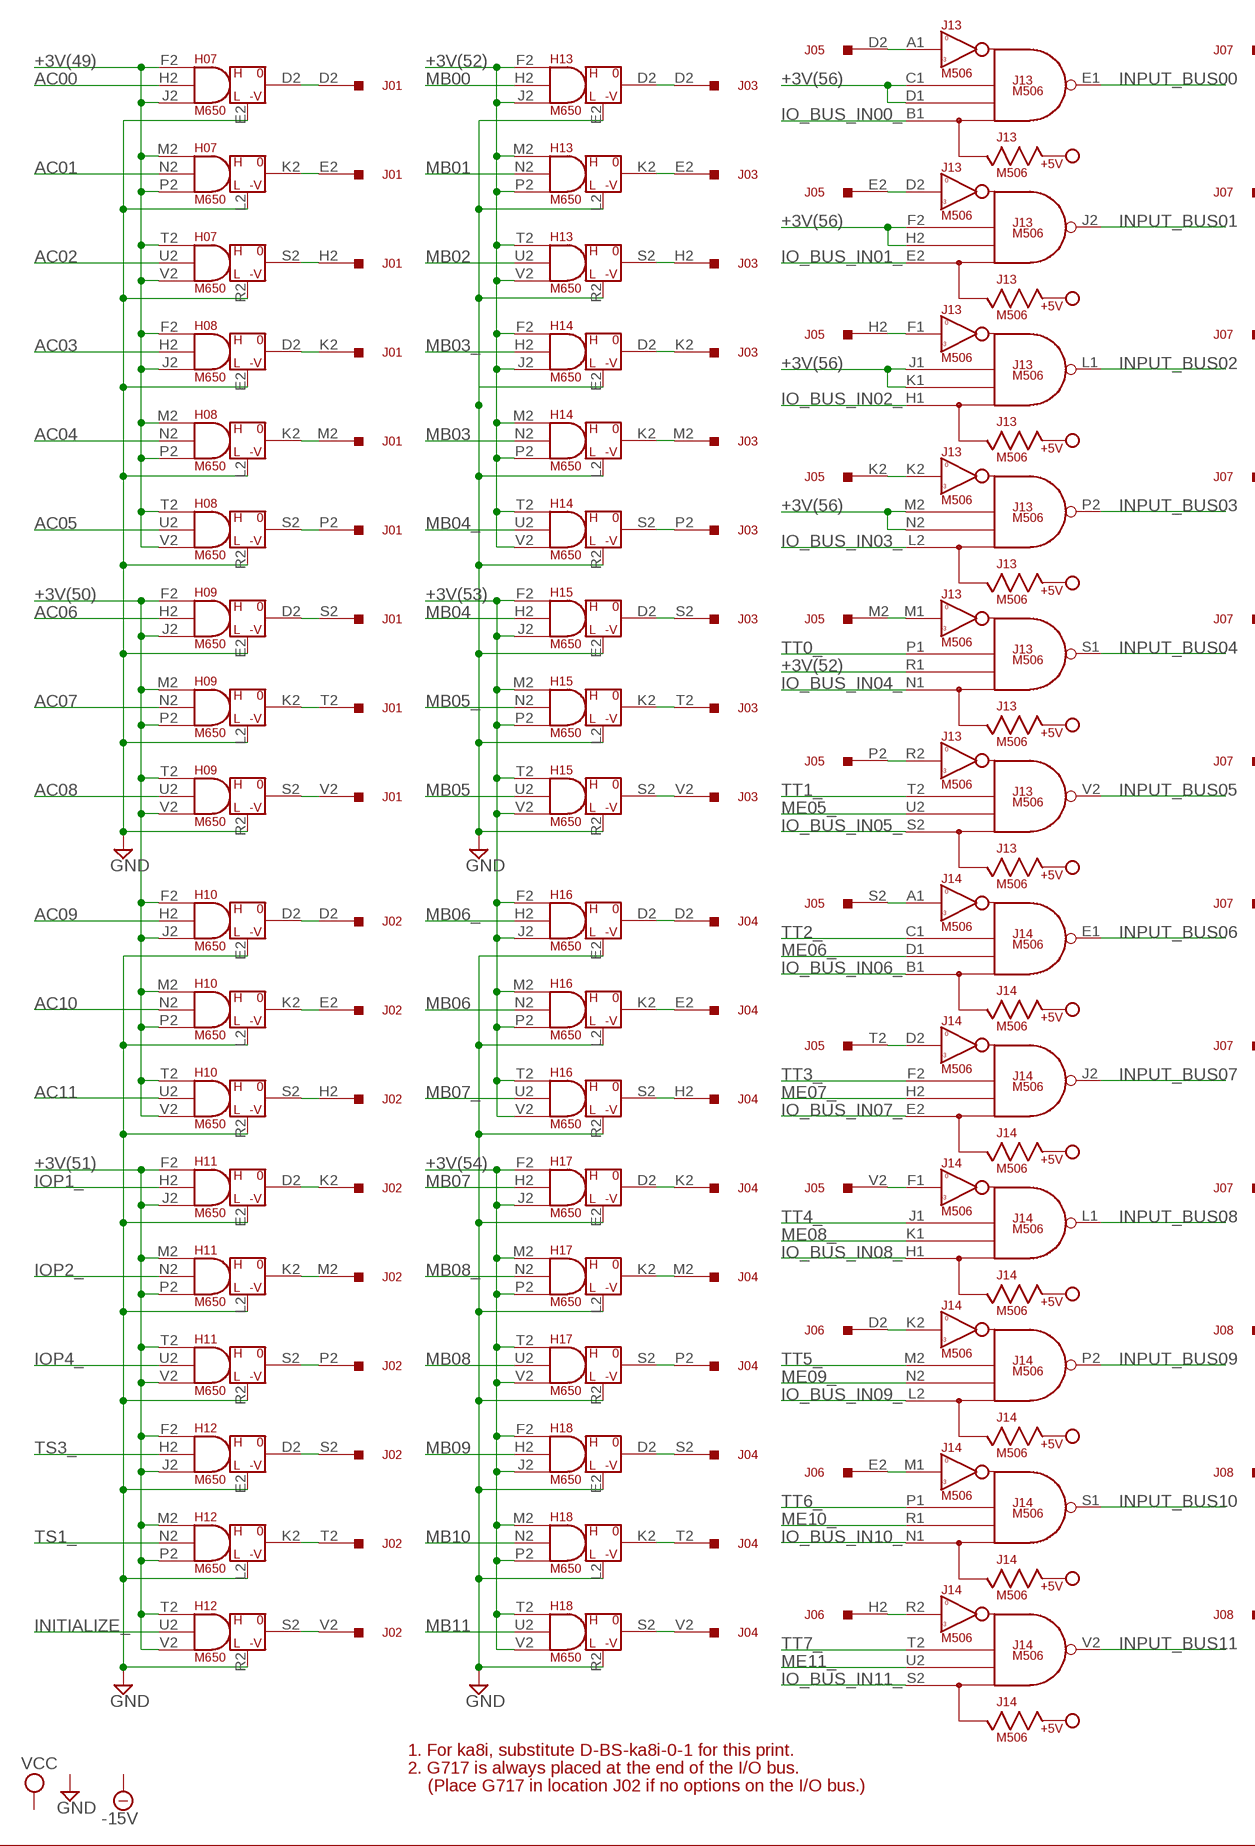
[diagram p13: schematic, sheet 14, part 1 of 2]
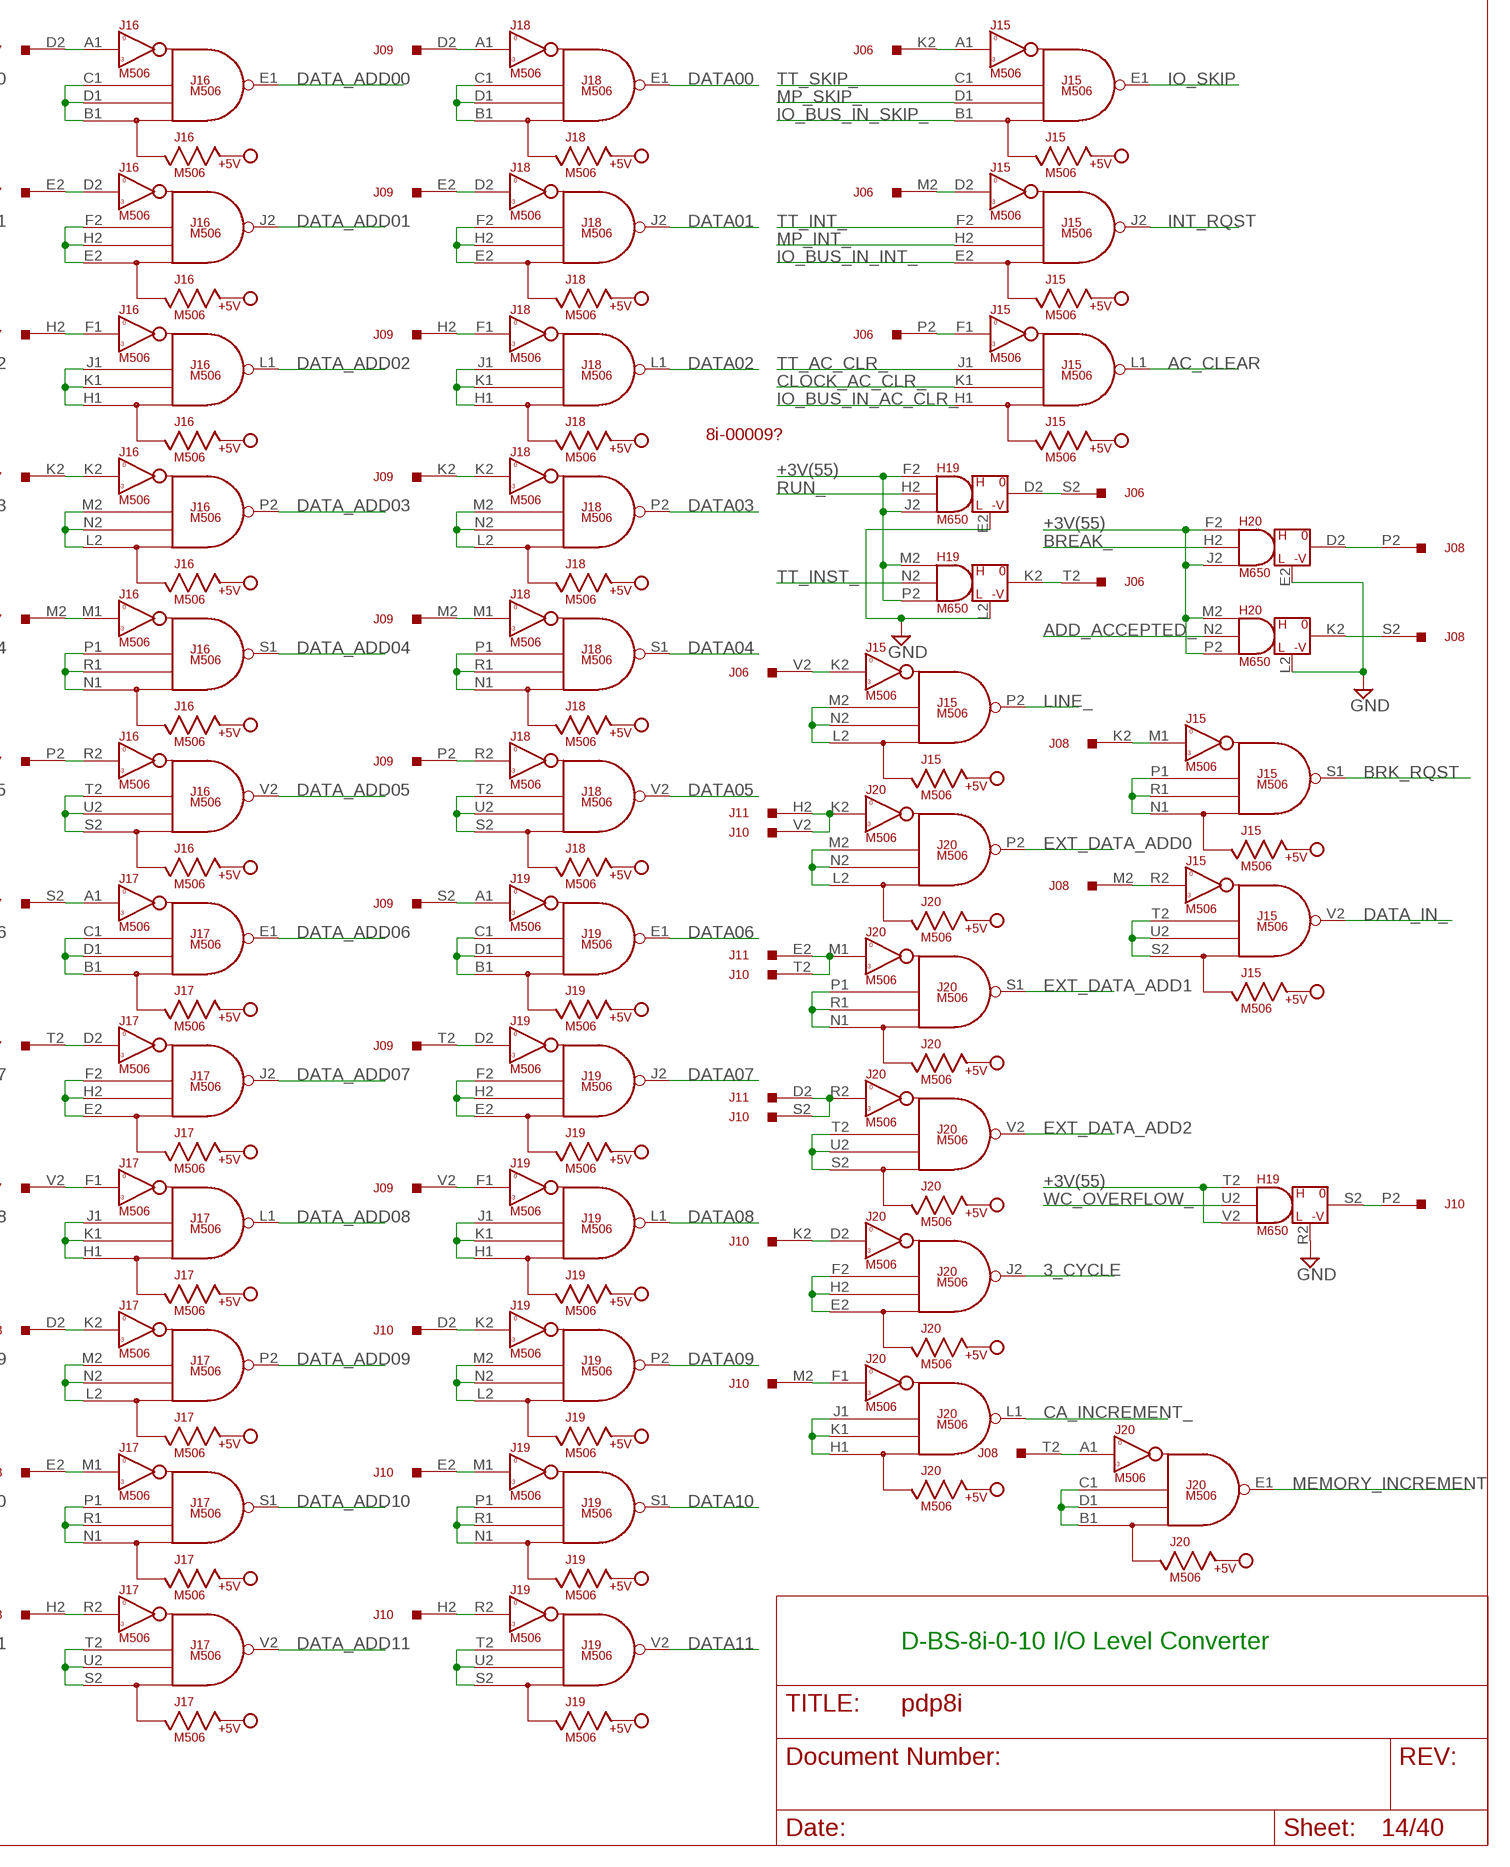
[diagram p14: schematic, sheet 14, part 2 of 2]
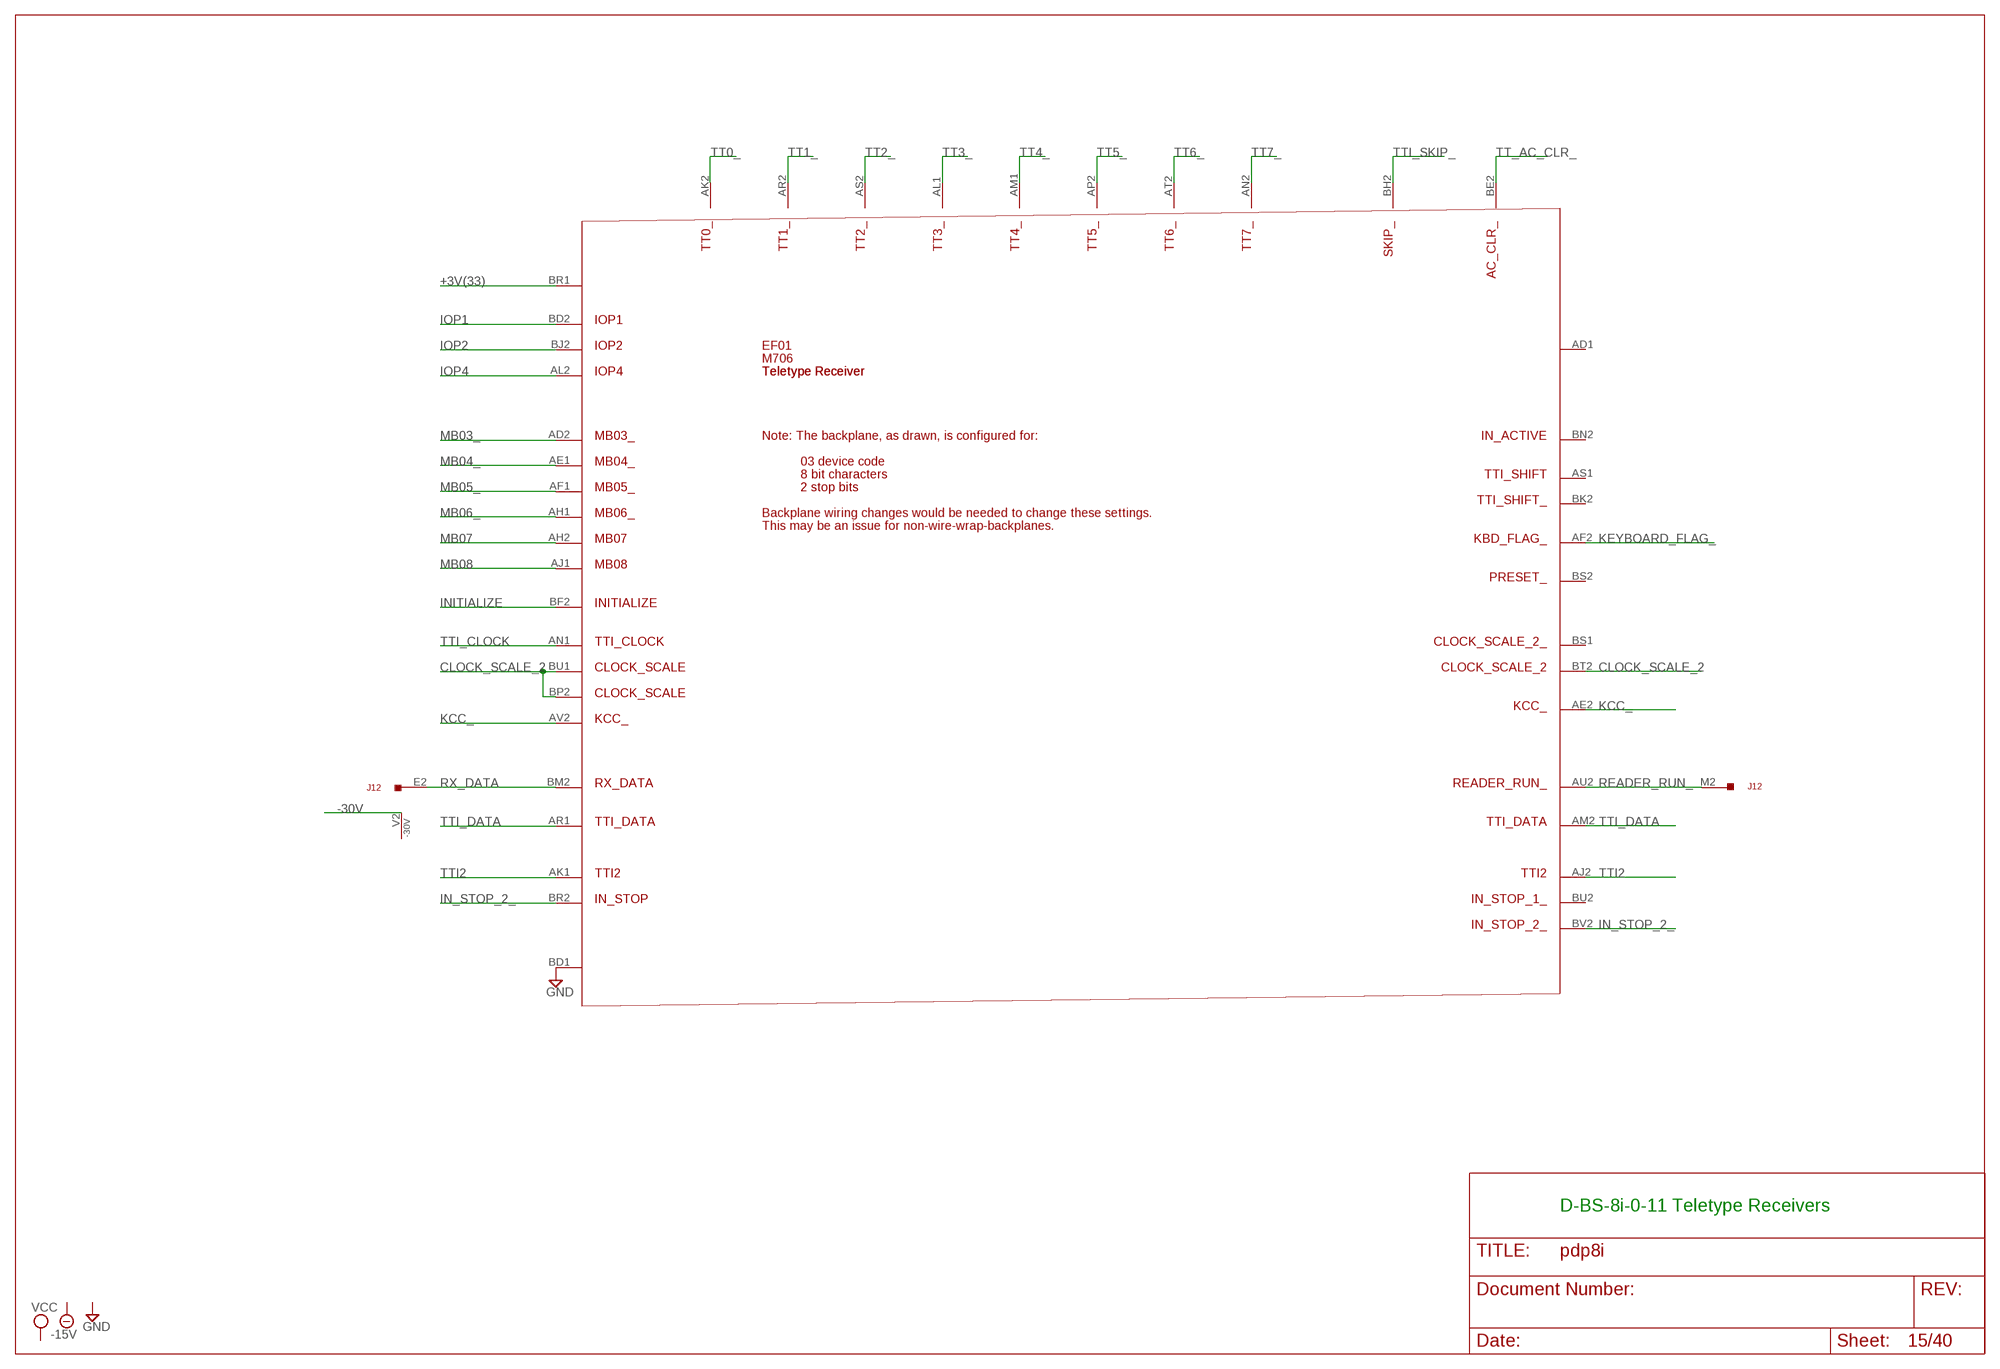
[diagram p15: schematic, sheet 15]
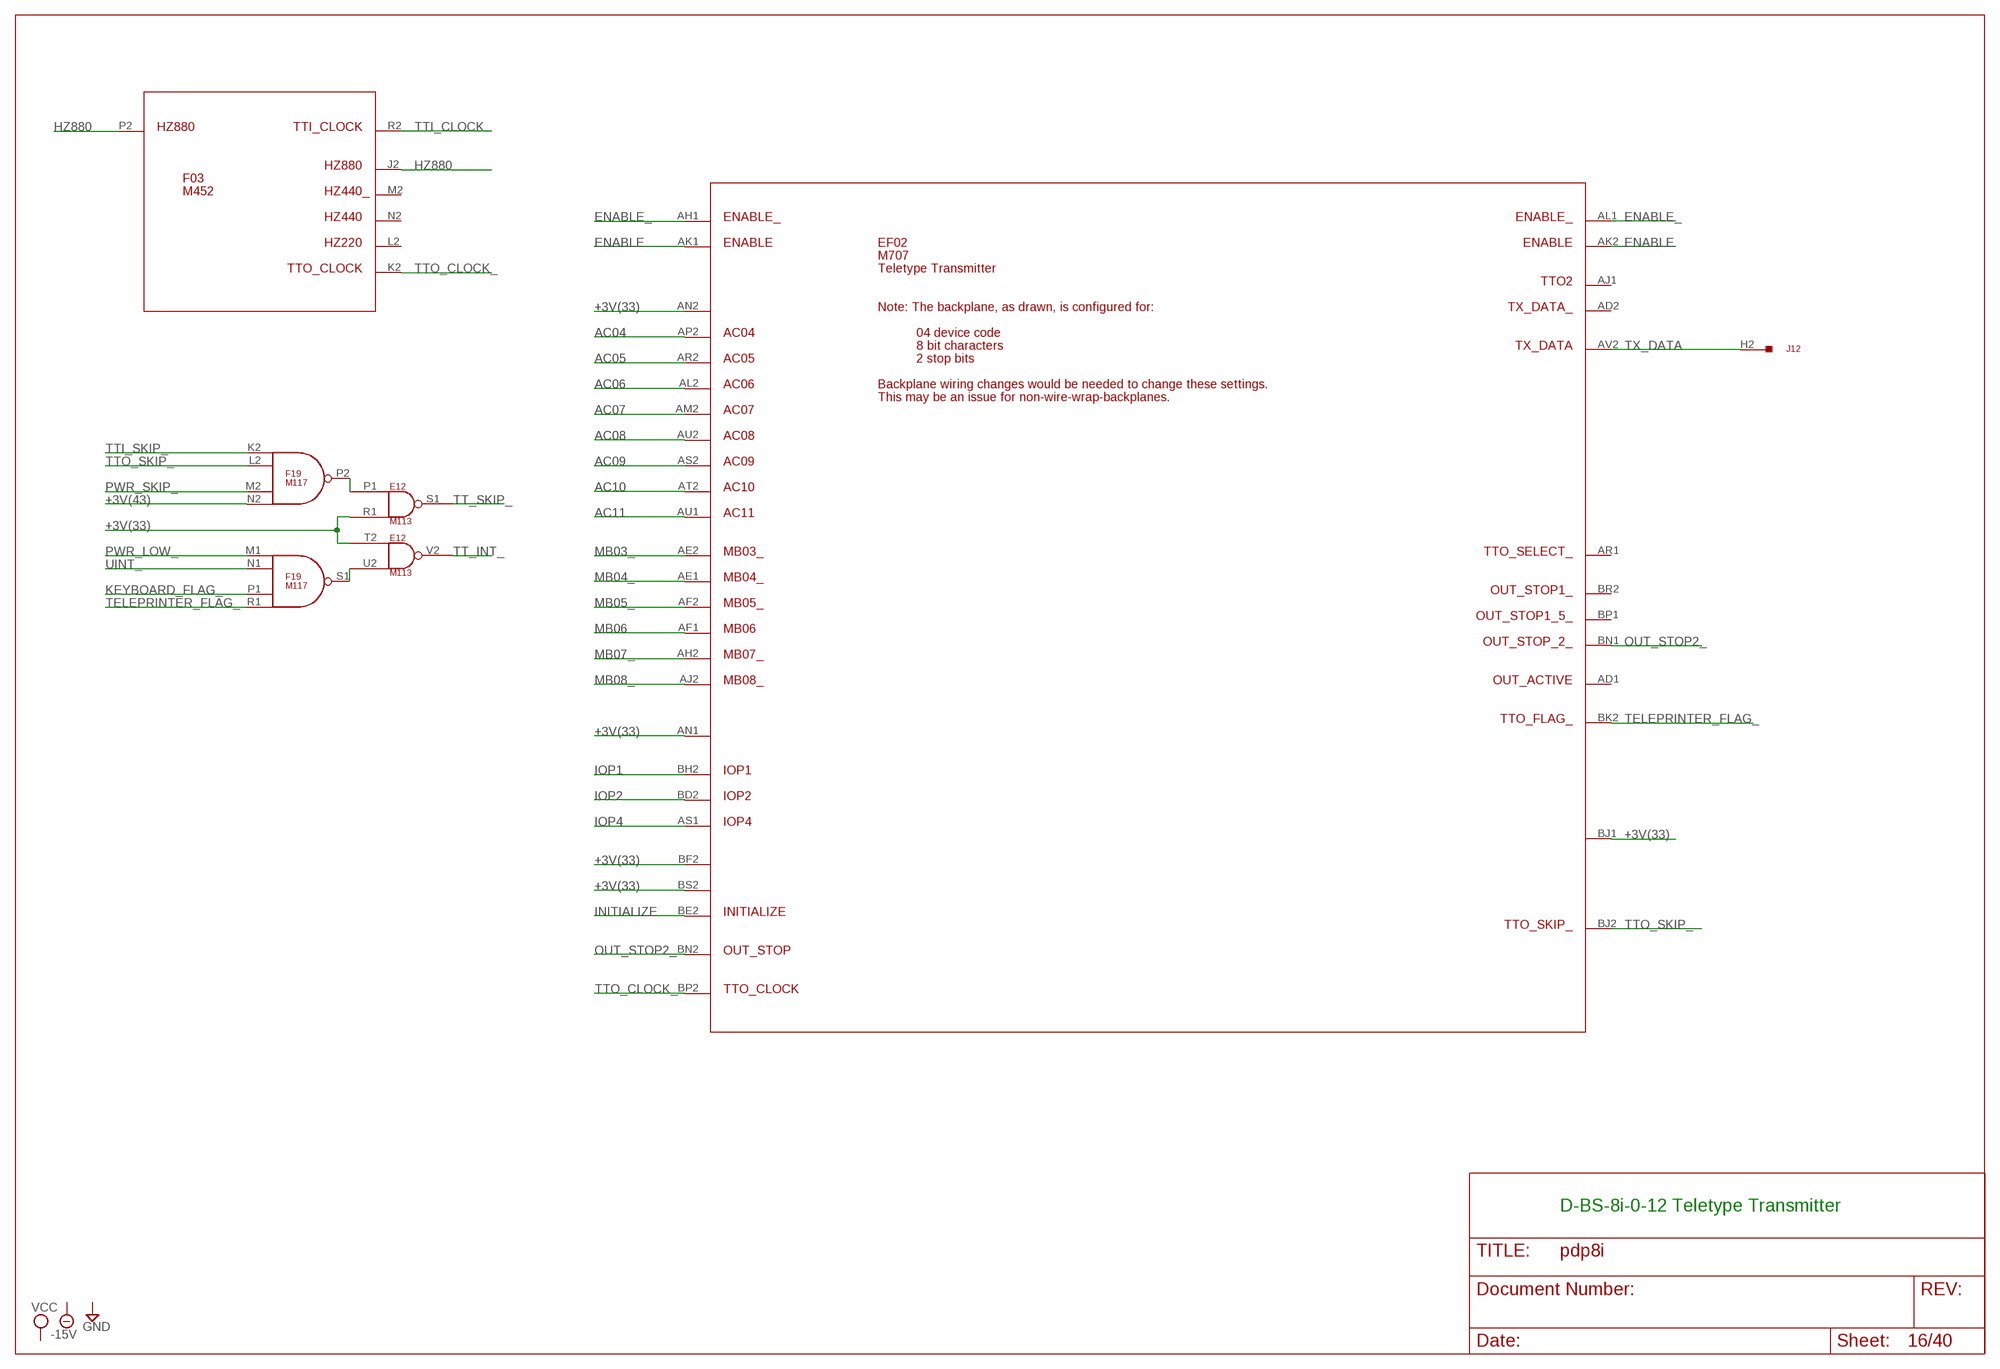
[diagram p16: schematic, sheet 16]
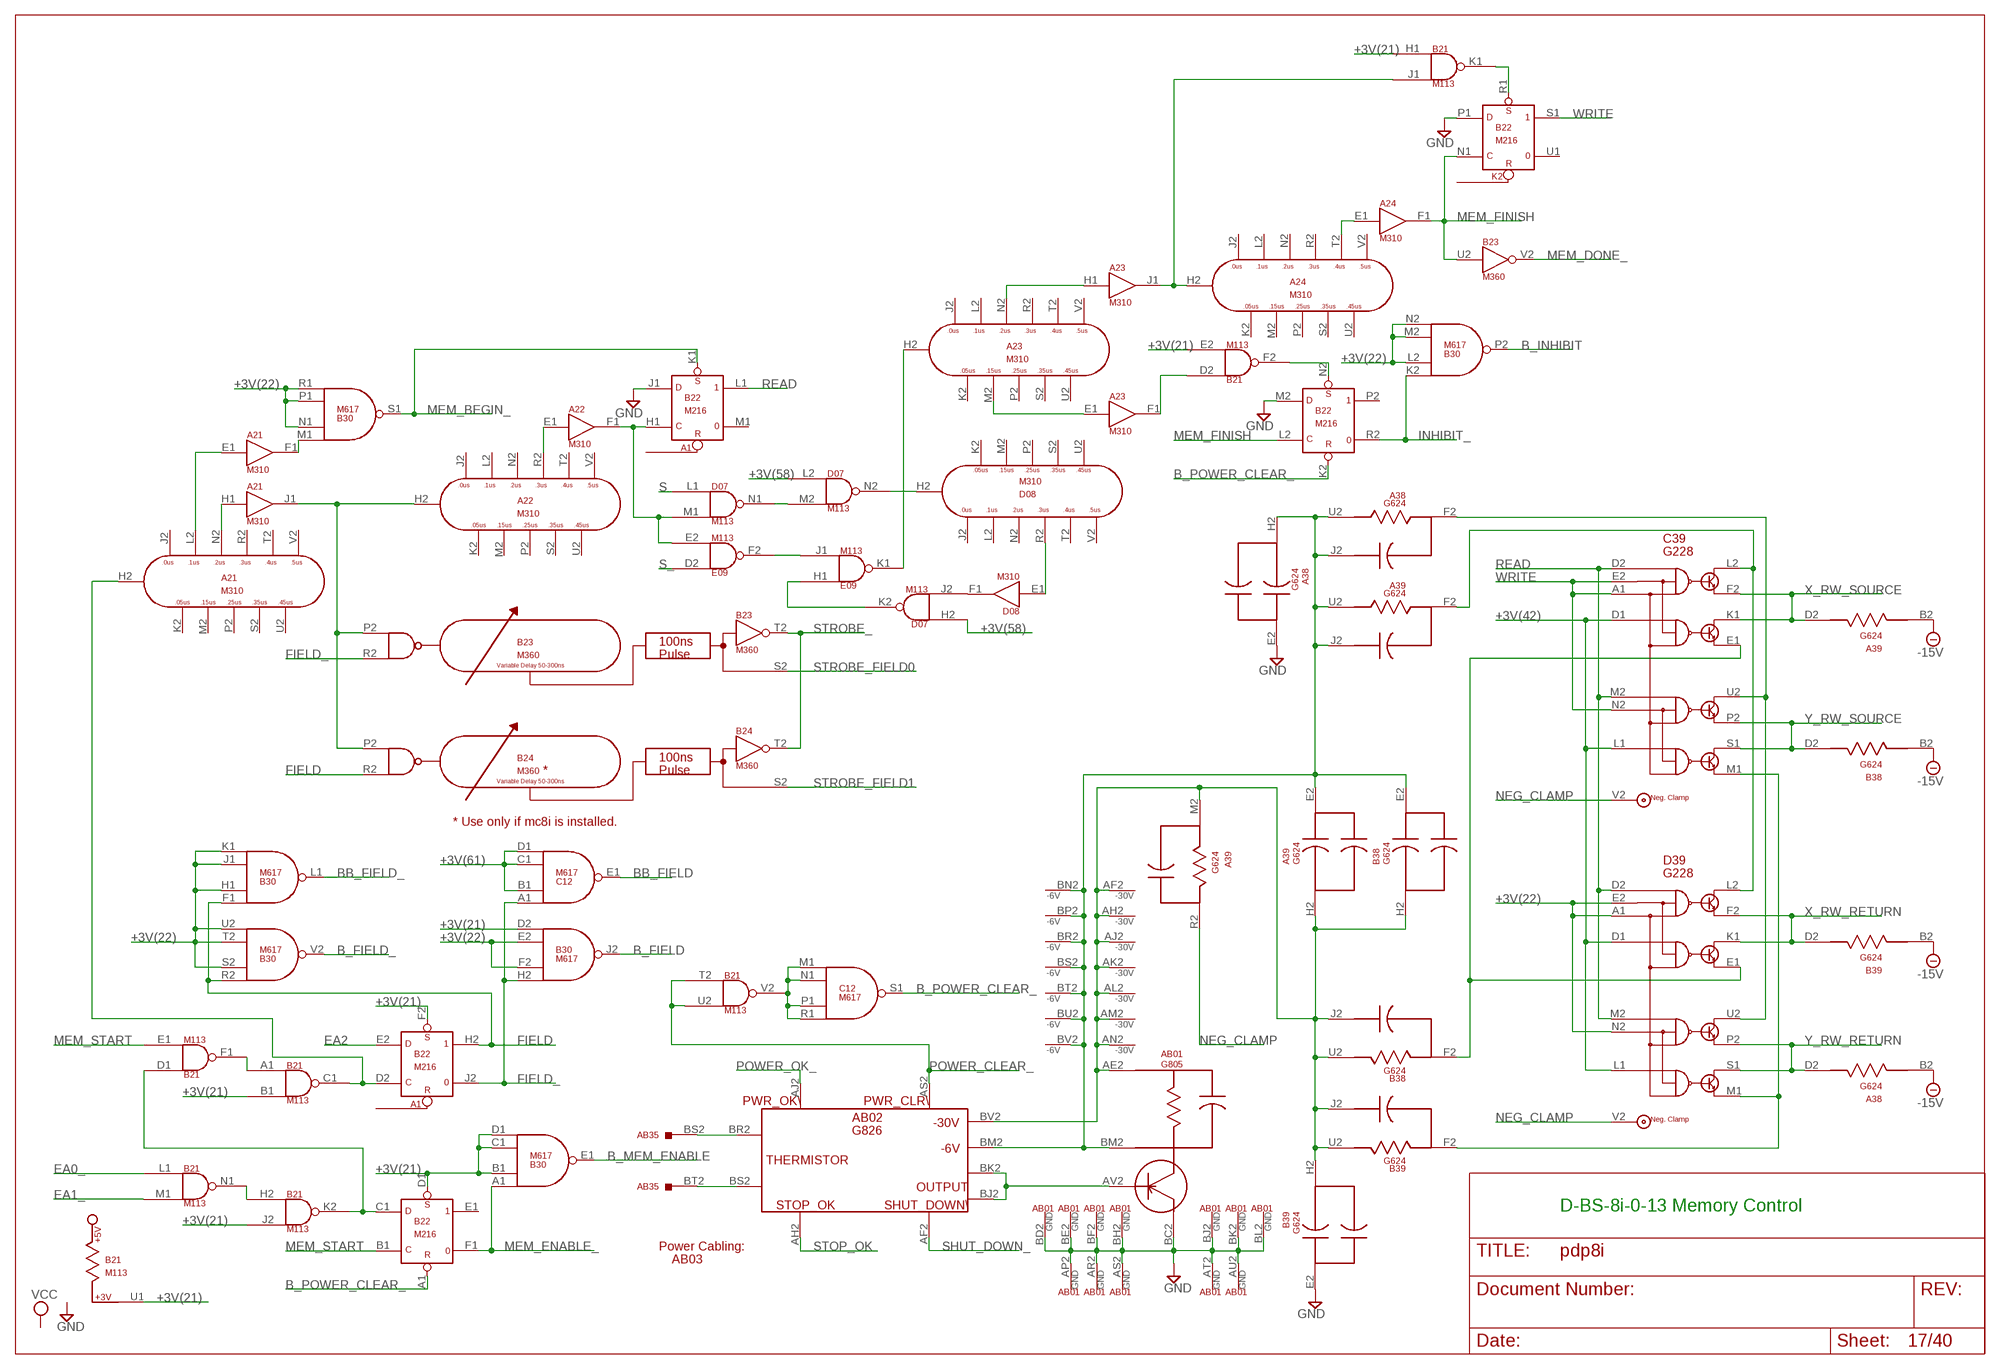
[diagram p17: schematic, sheet 17]
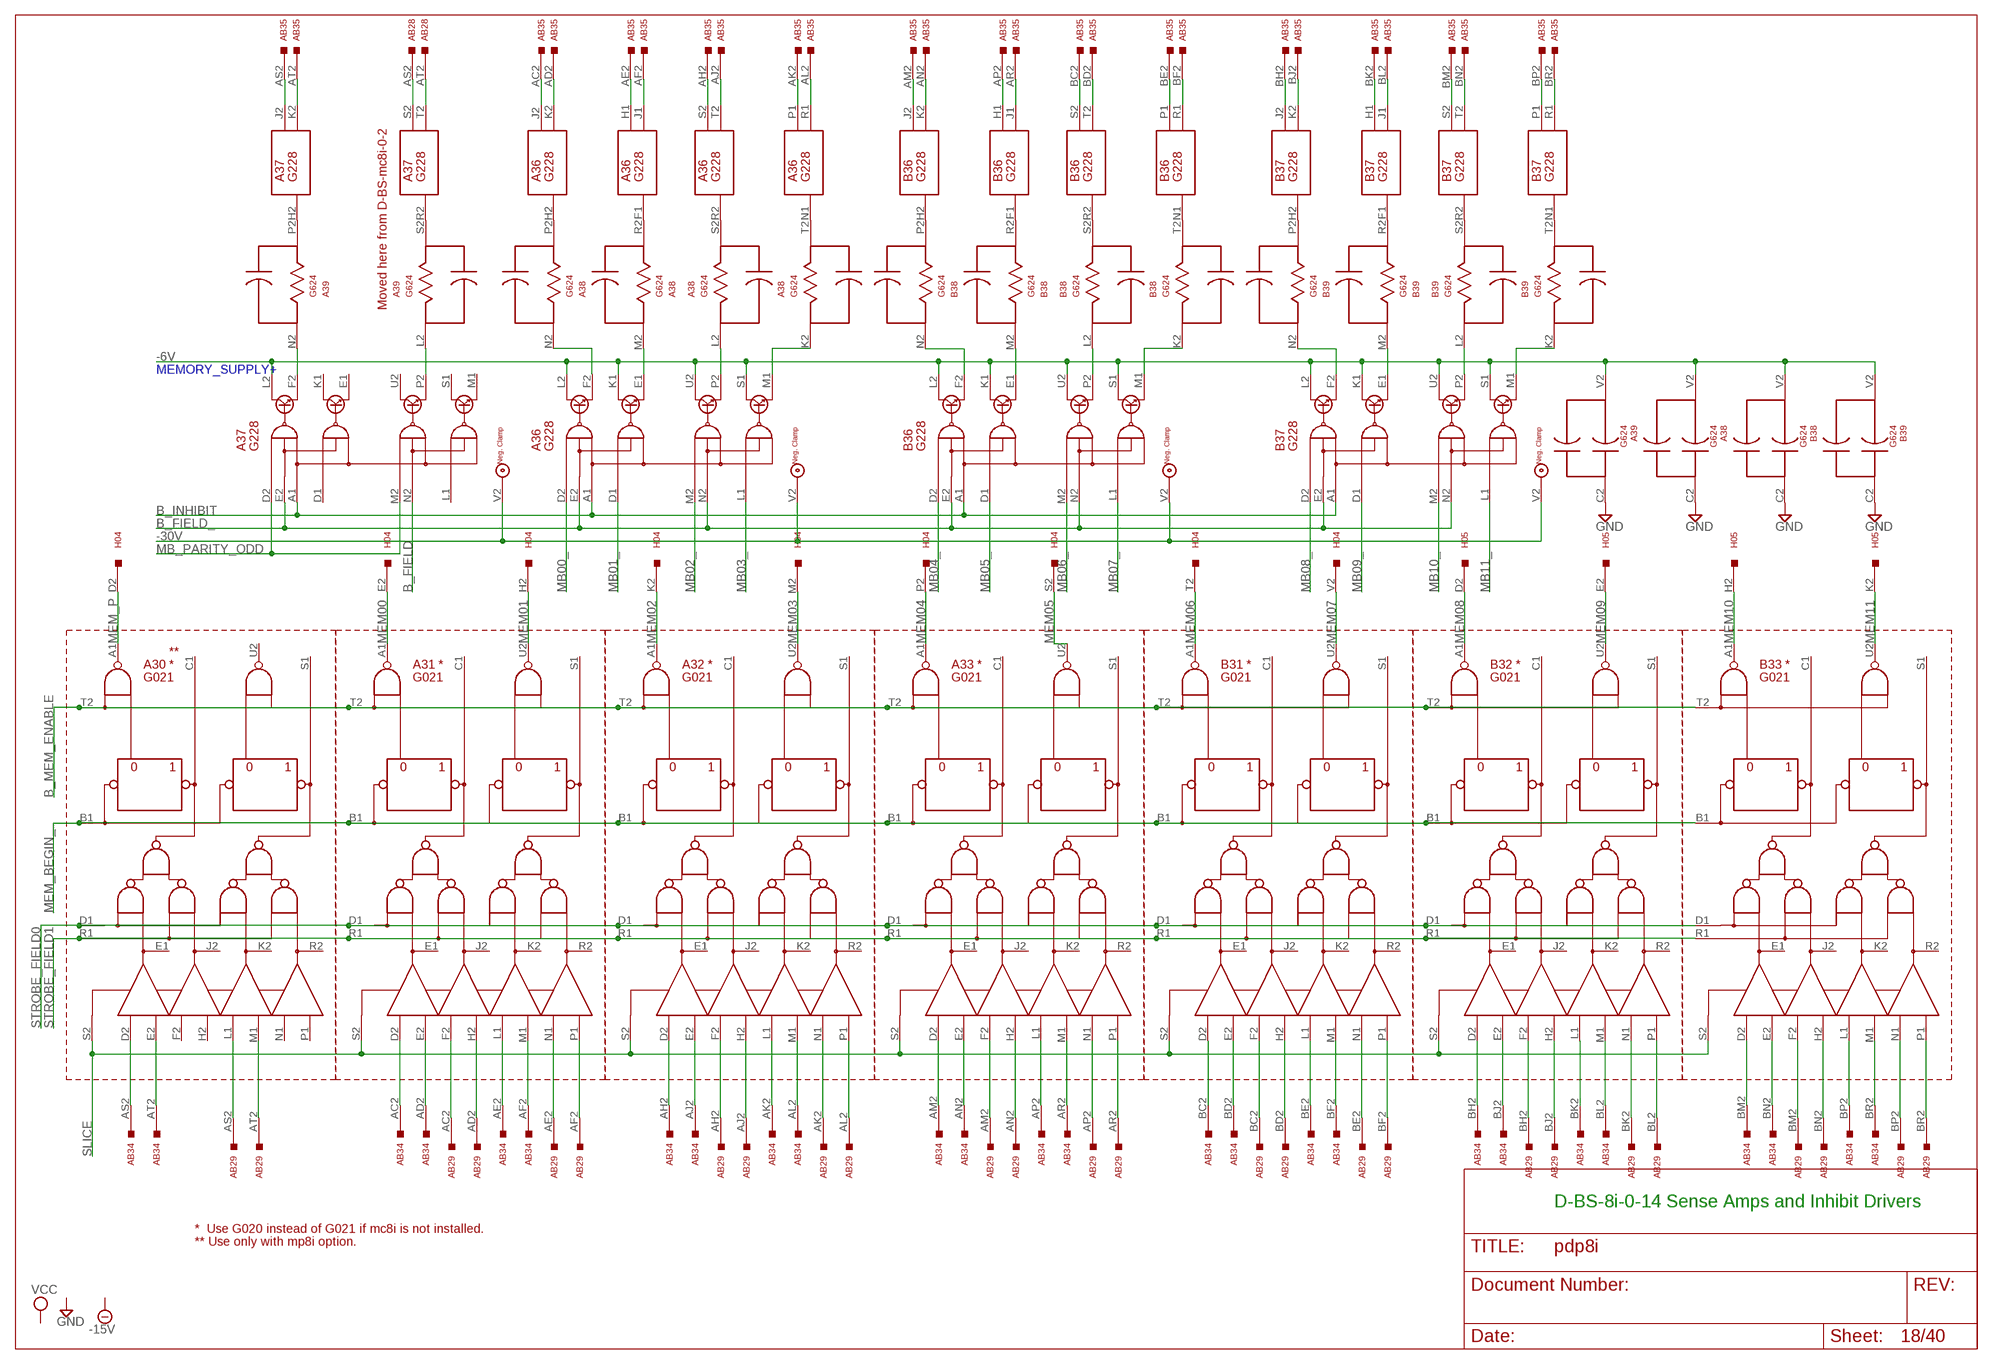
[diagram p18: schematic, sheet 18]
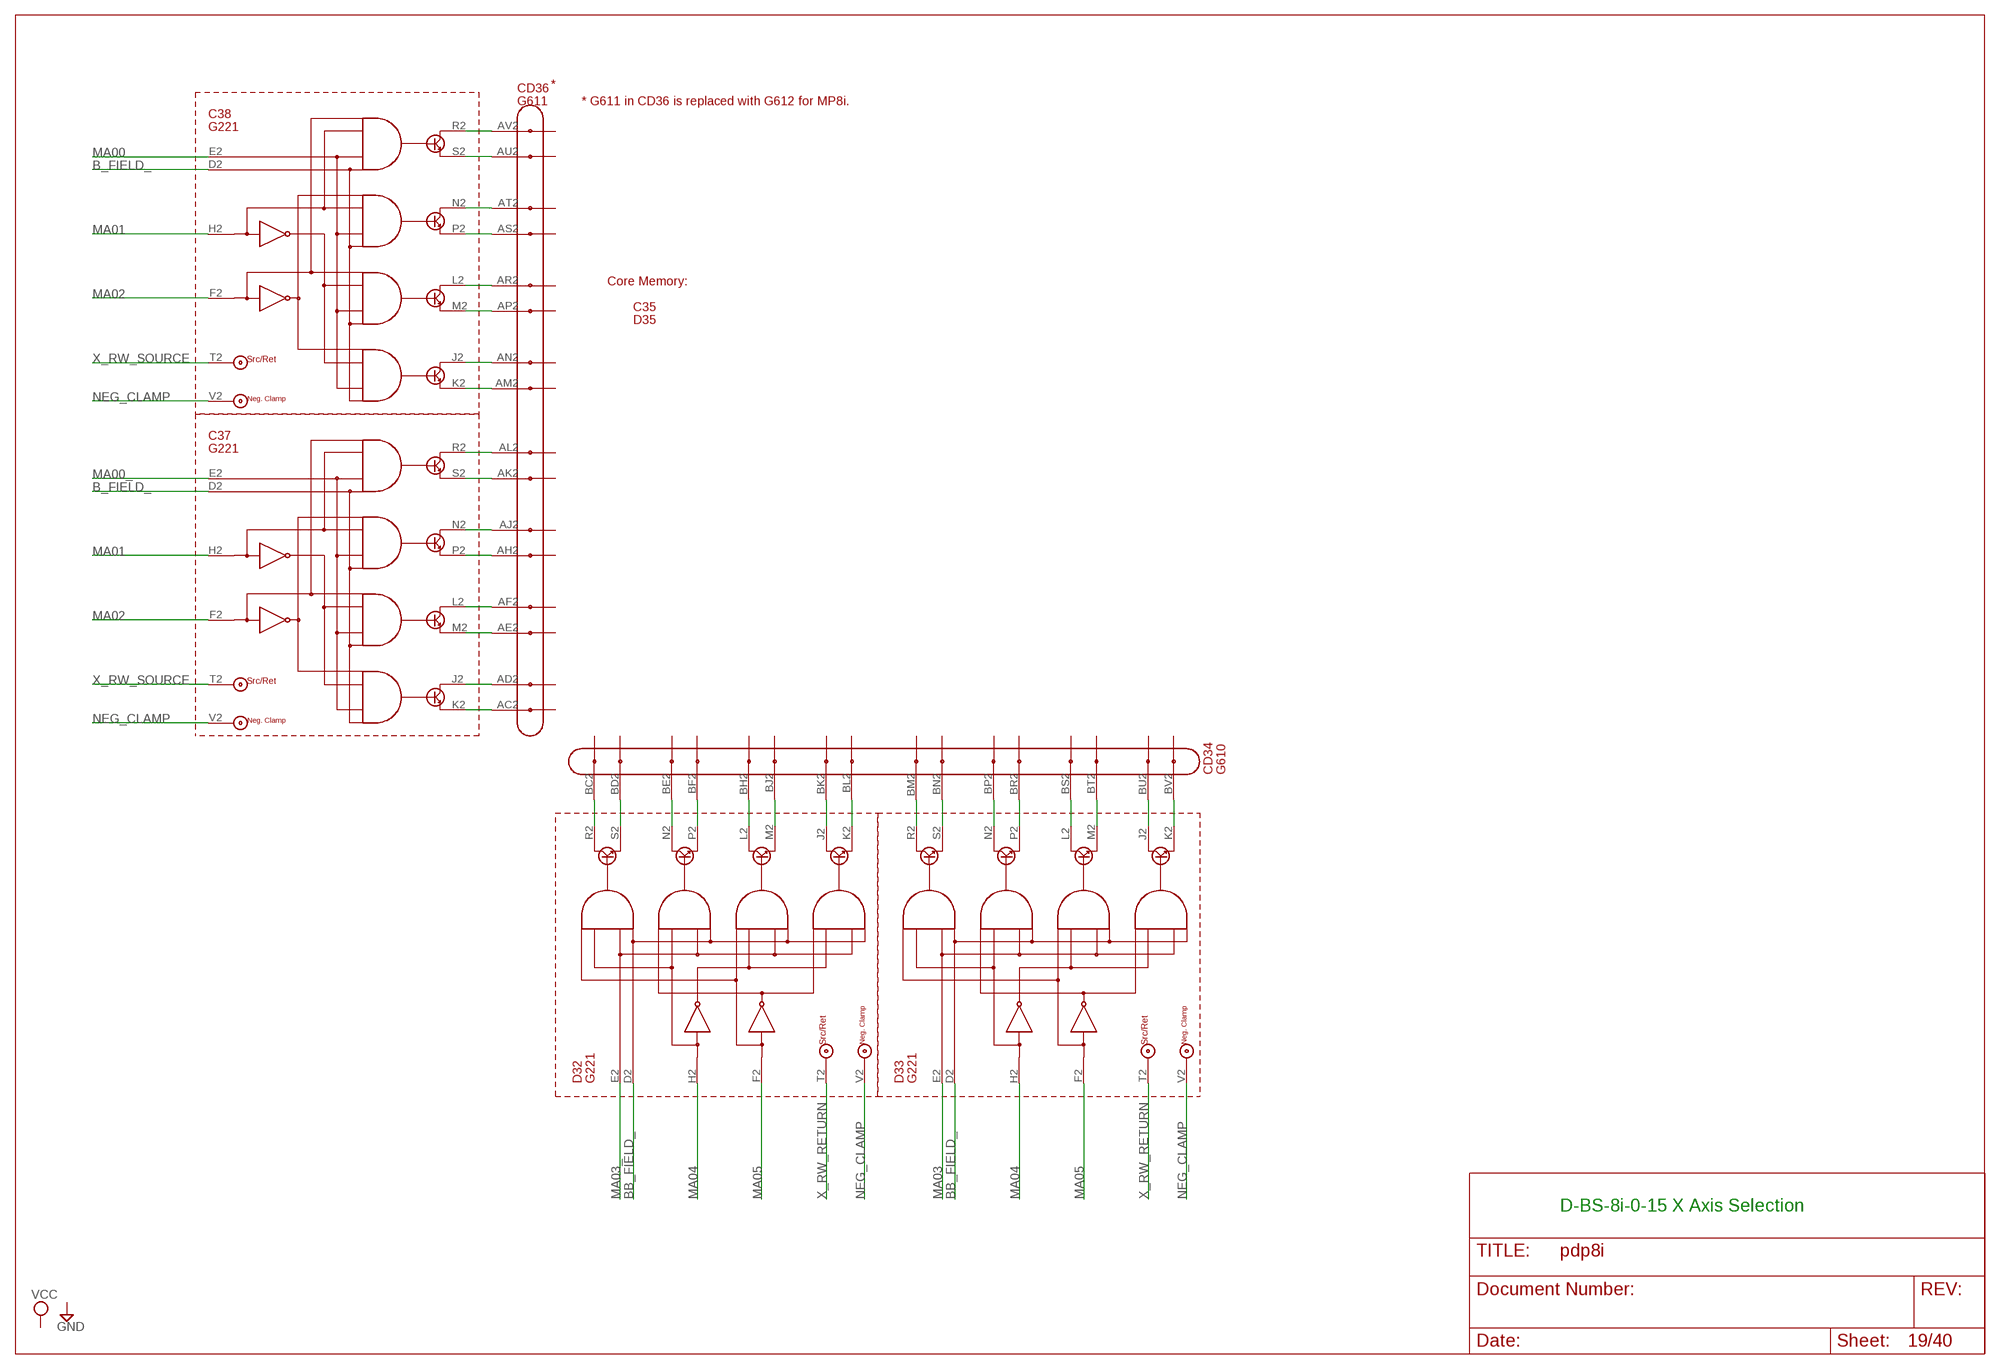
[diagram p19: schematic, sheet 19]
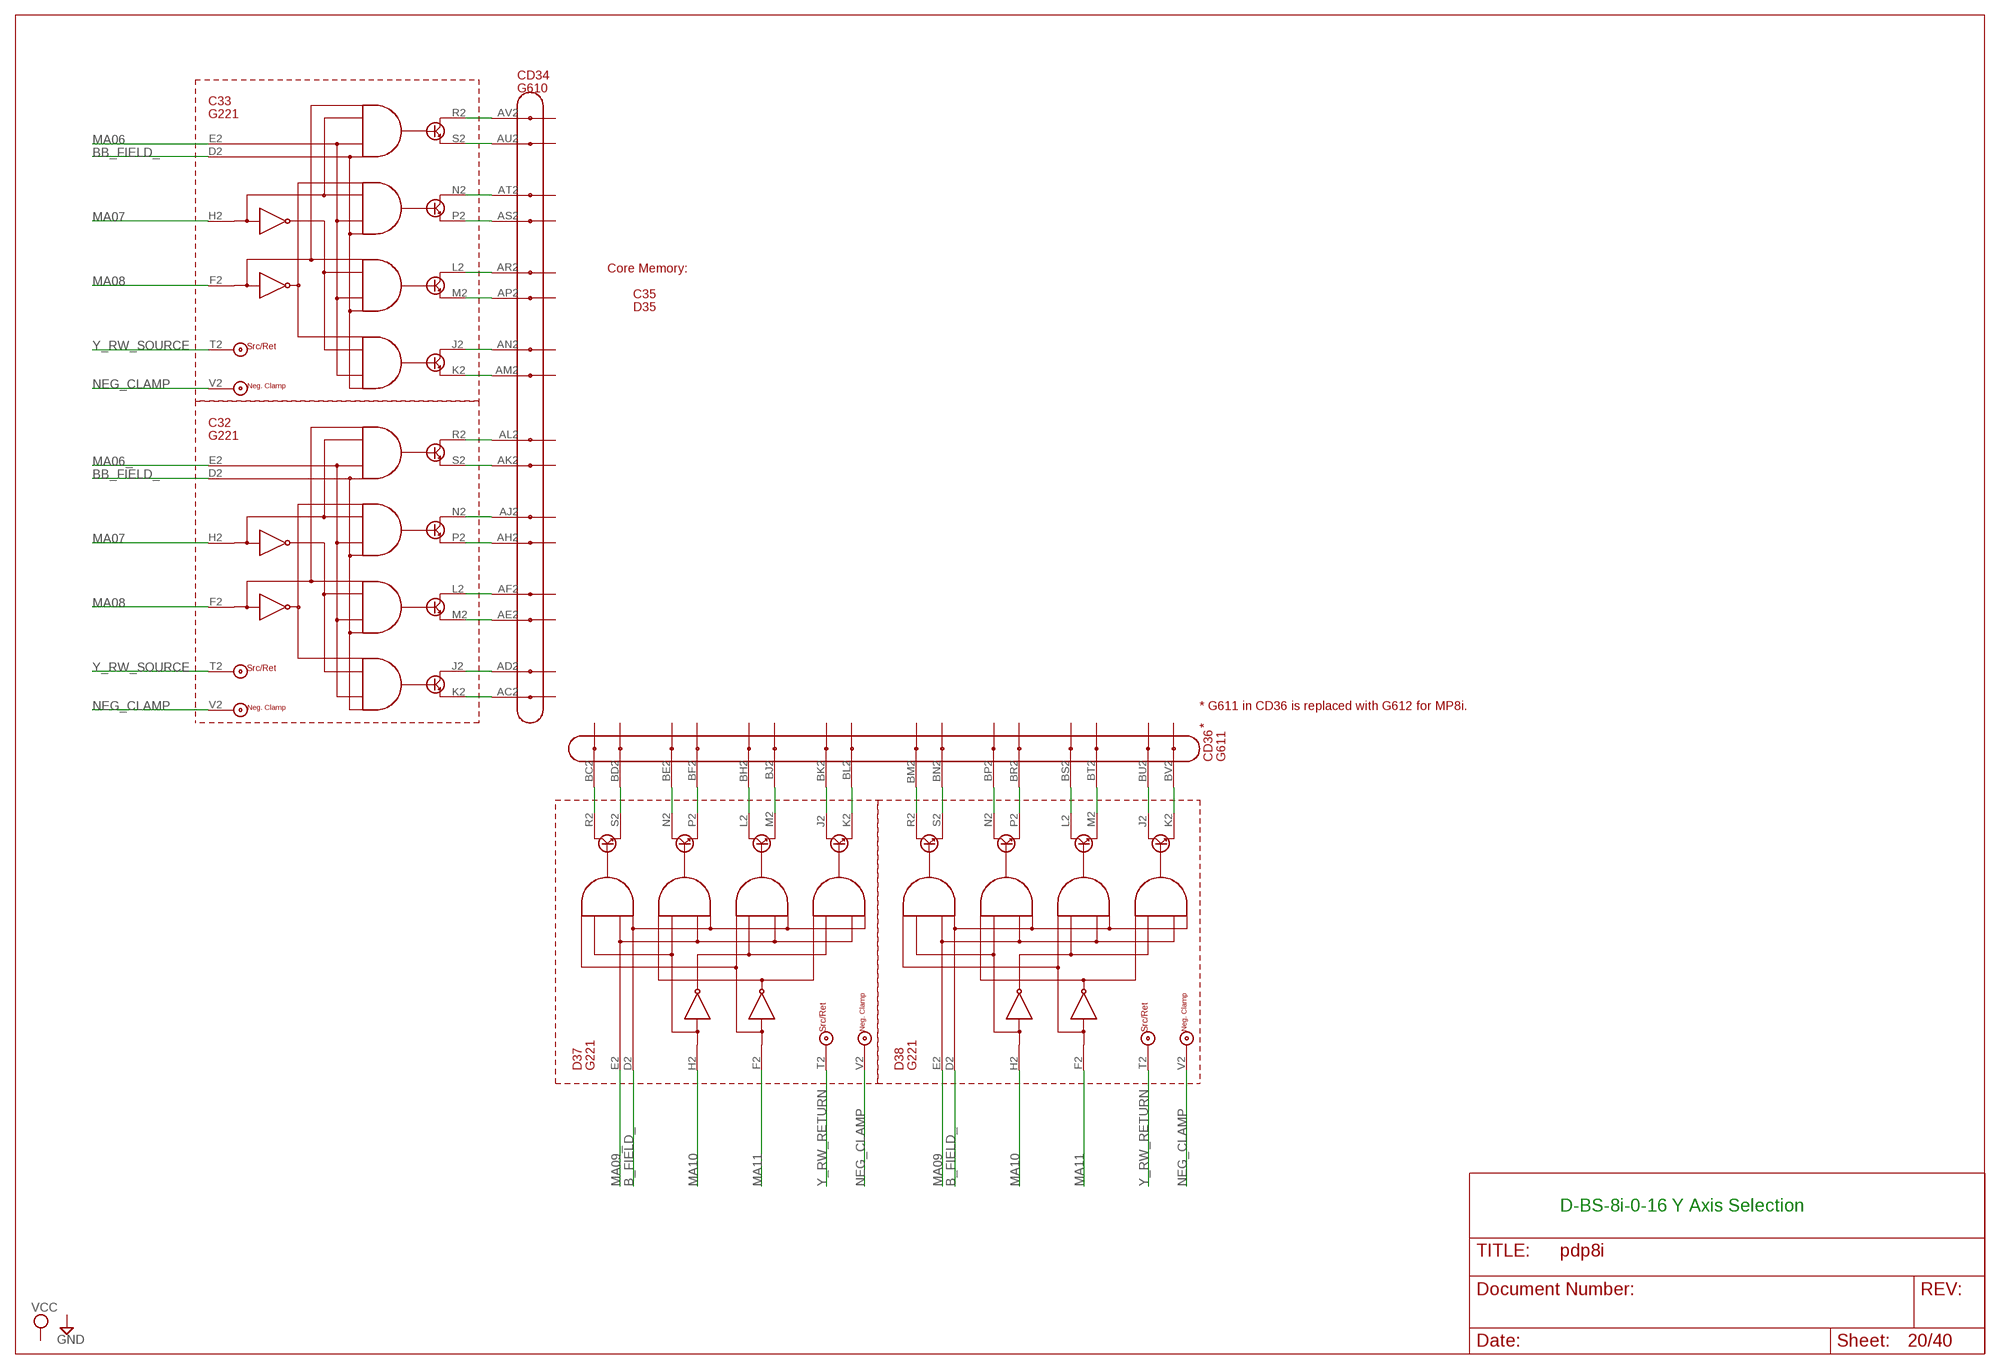
[diagram p20: schematic, sheet 20]
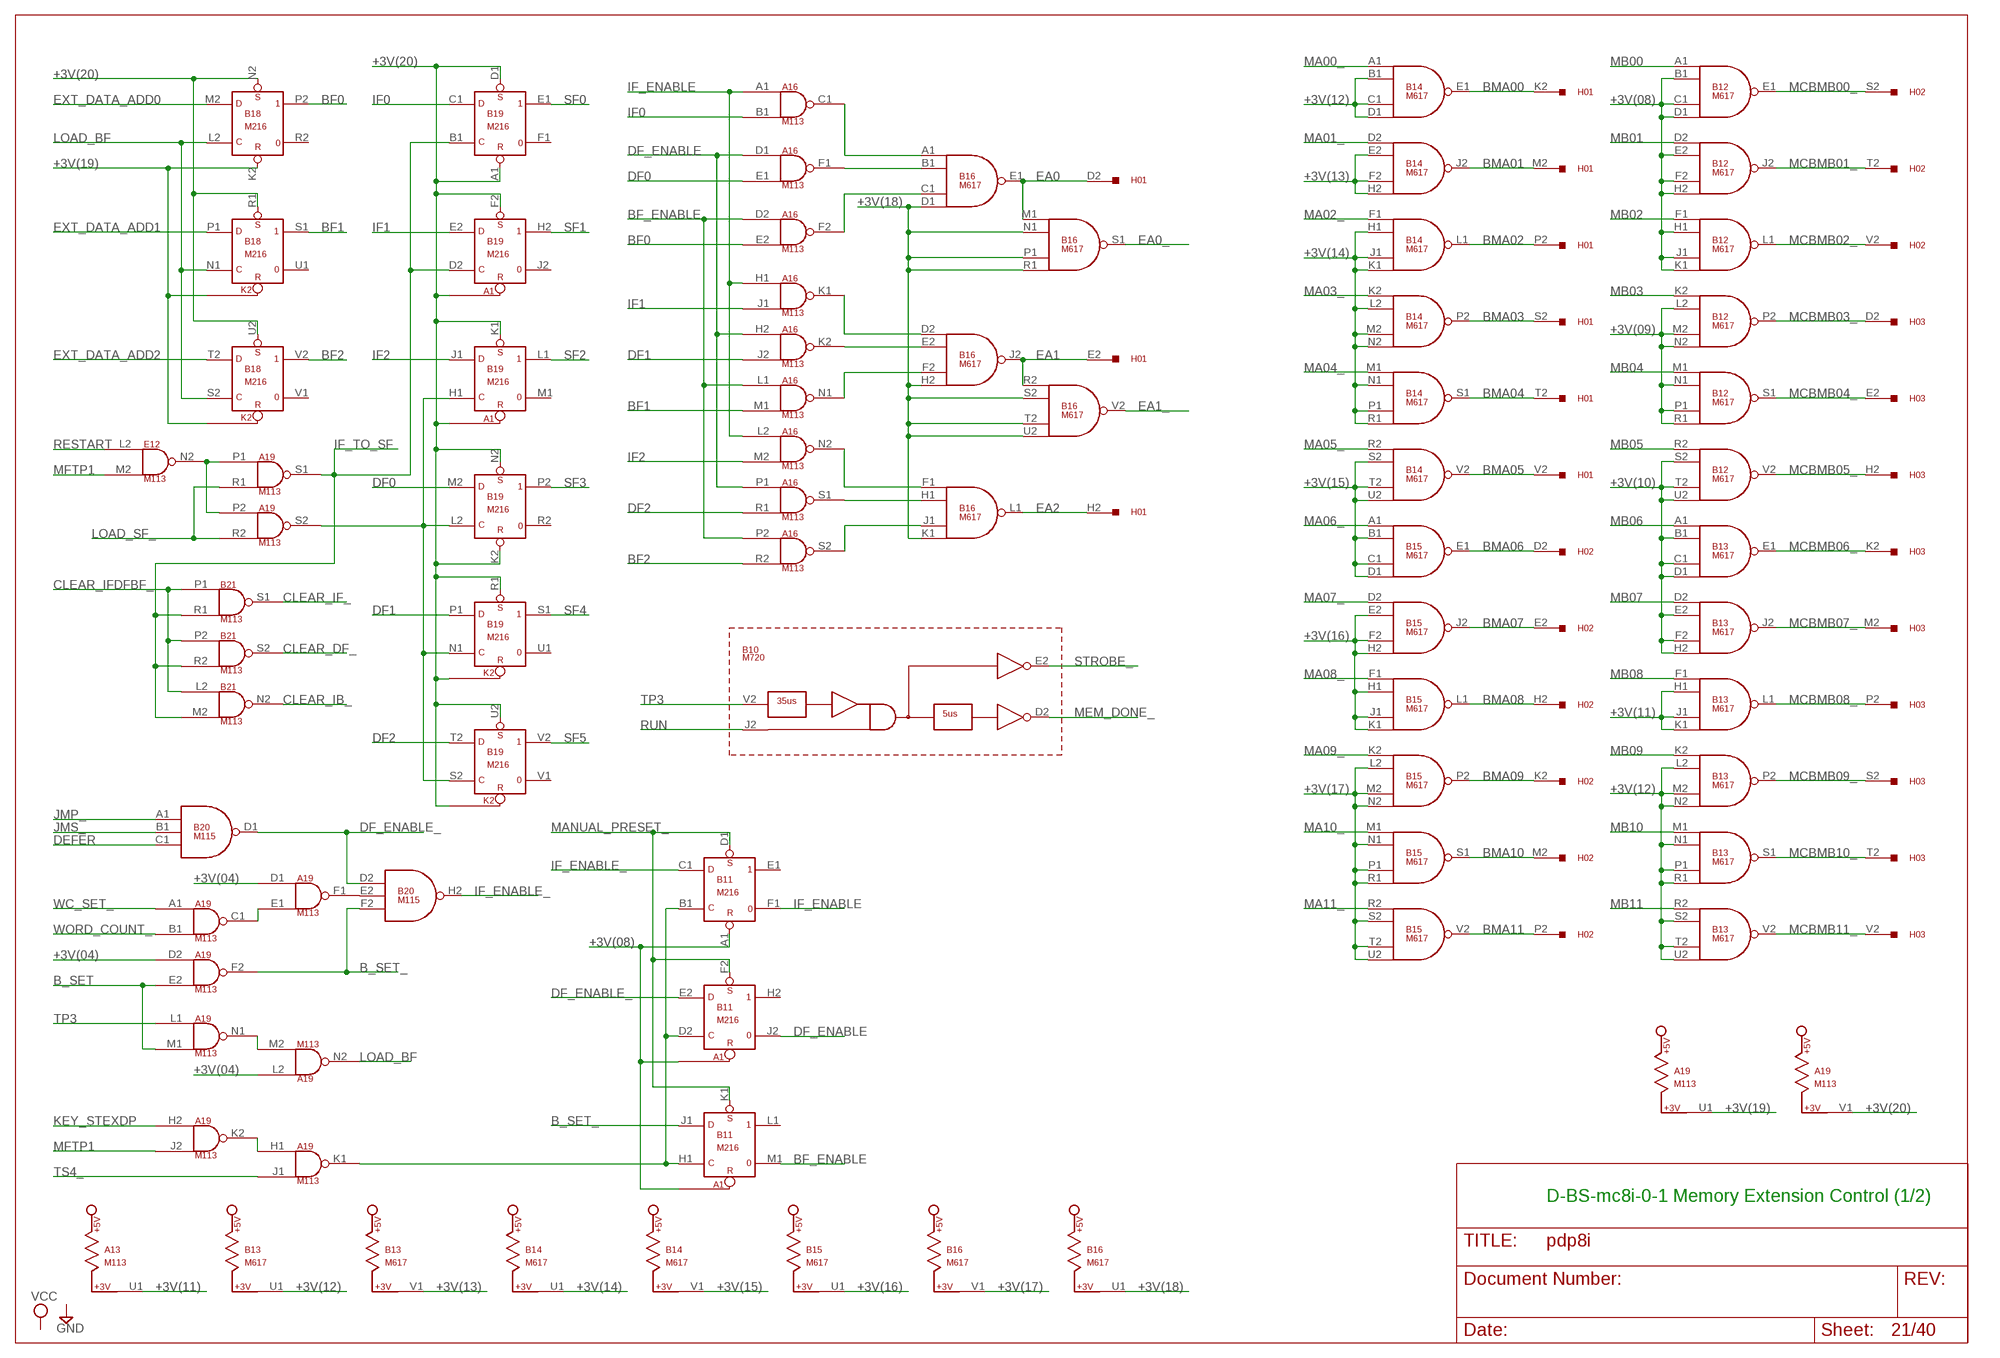
[diagram p21: schematic, sheet 21]
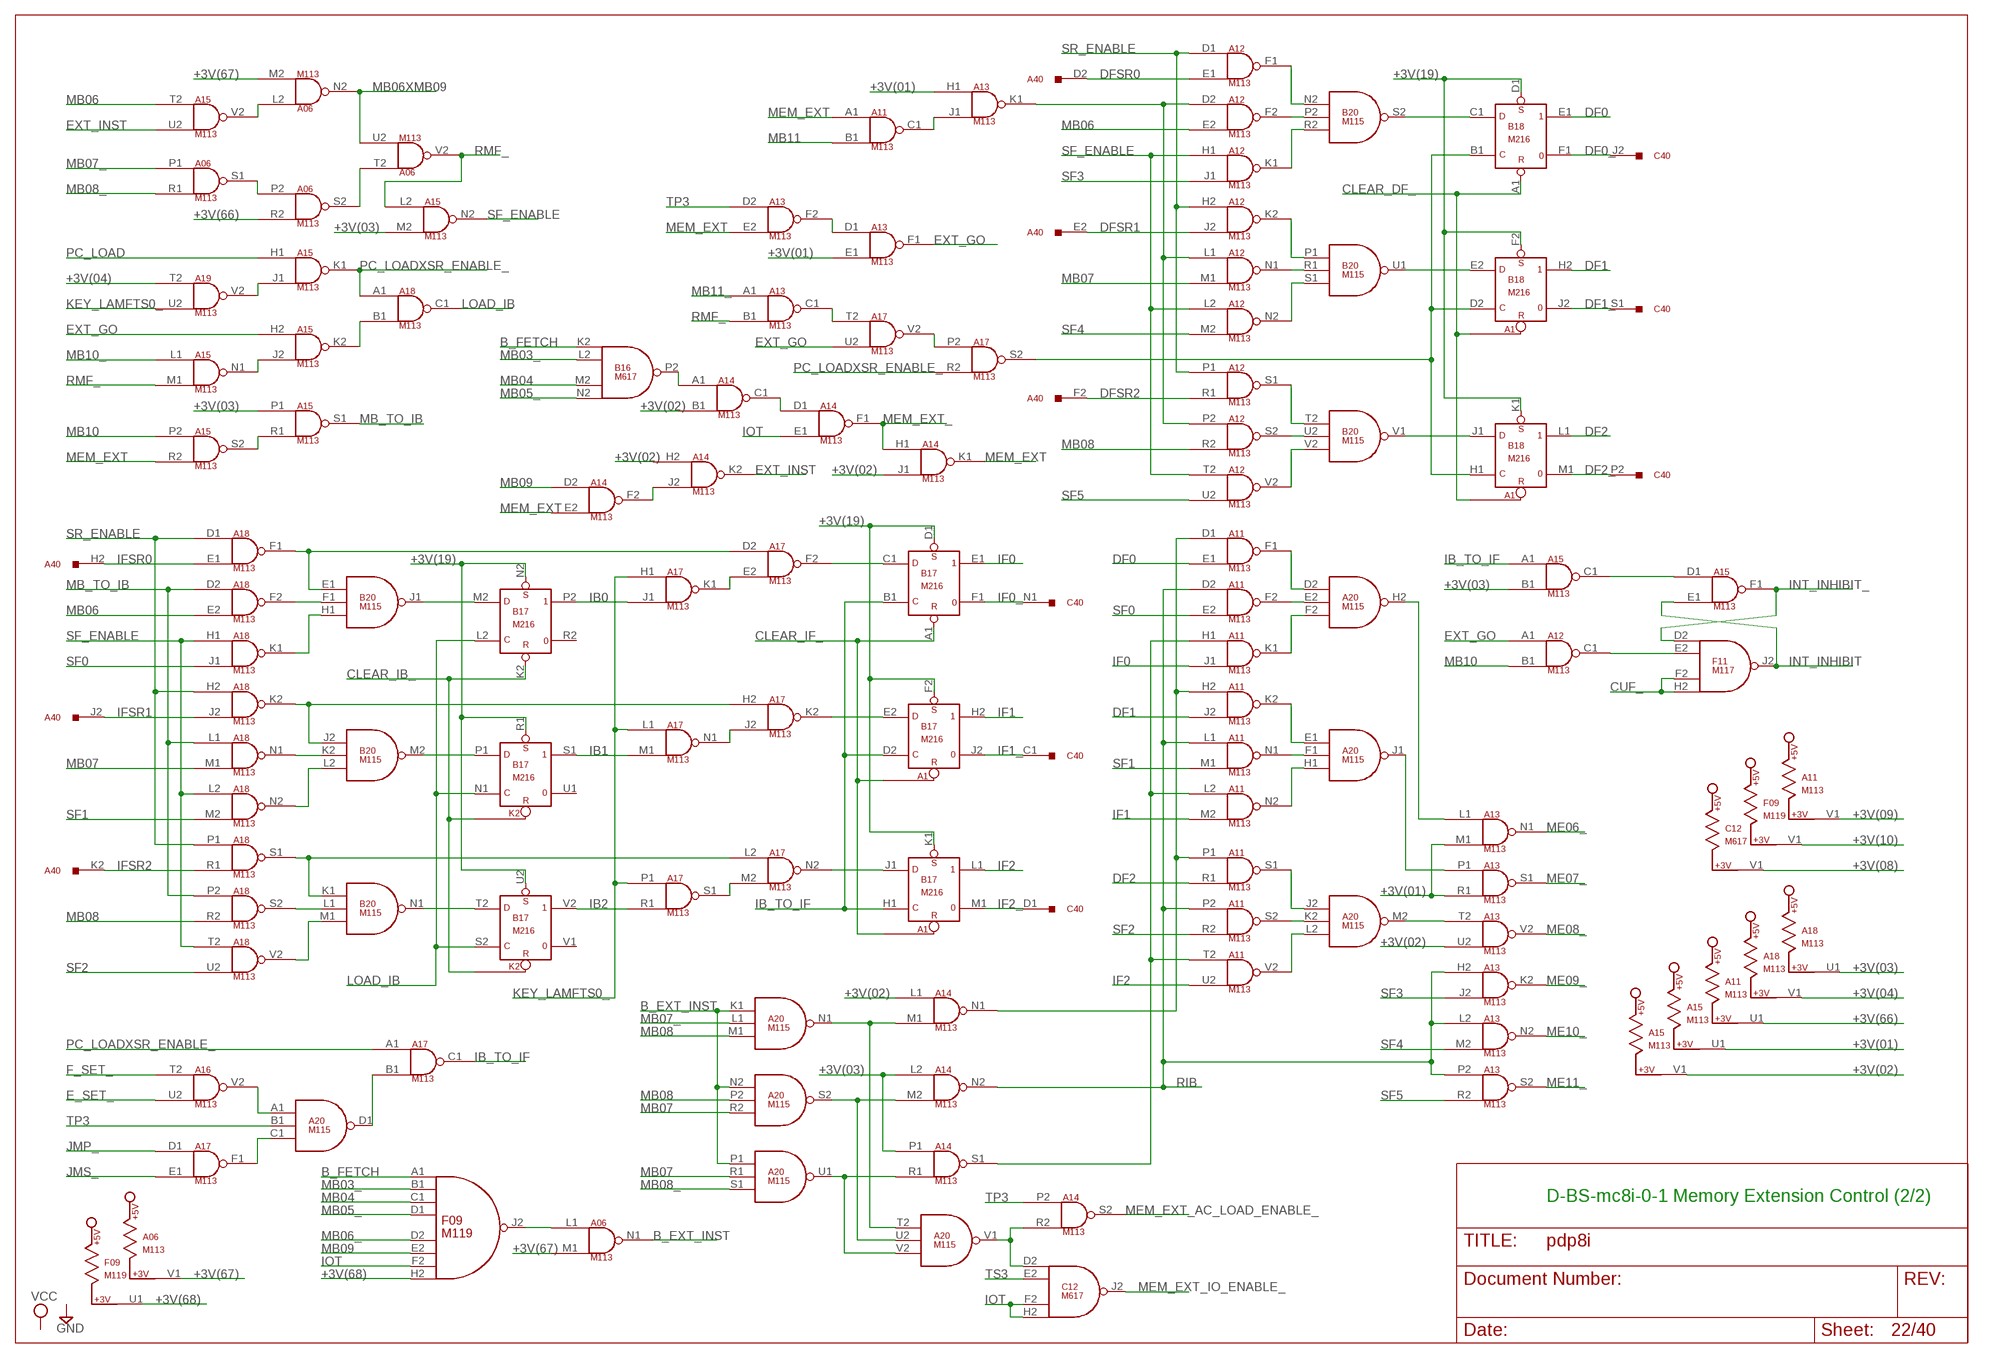
[diagram p22: schematic, sheet 22]
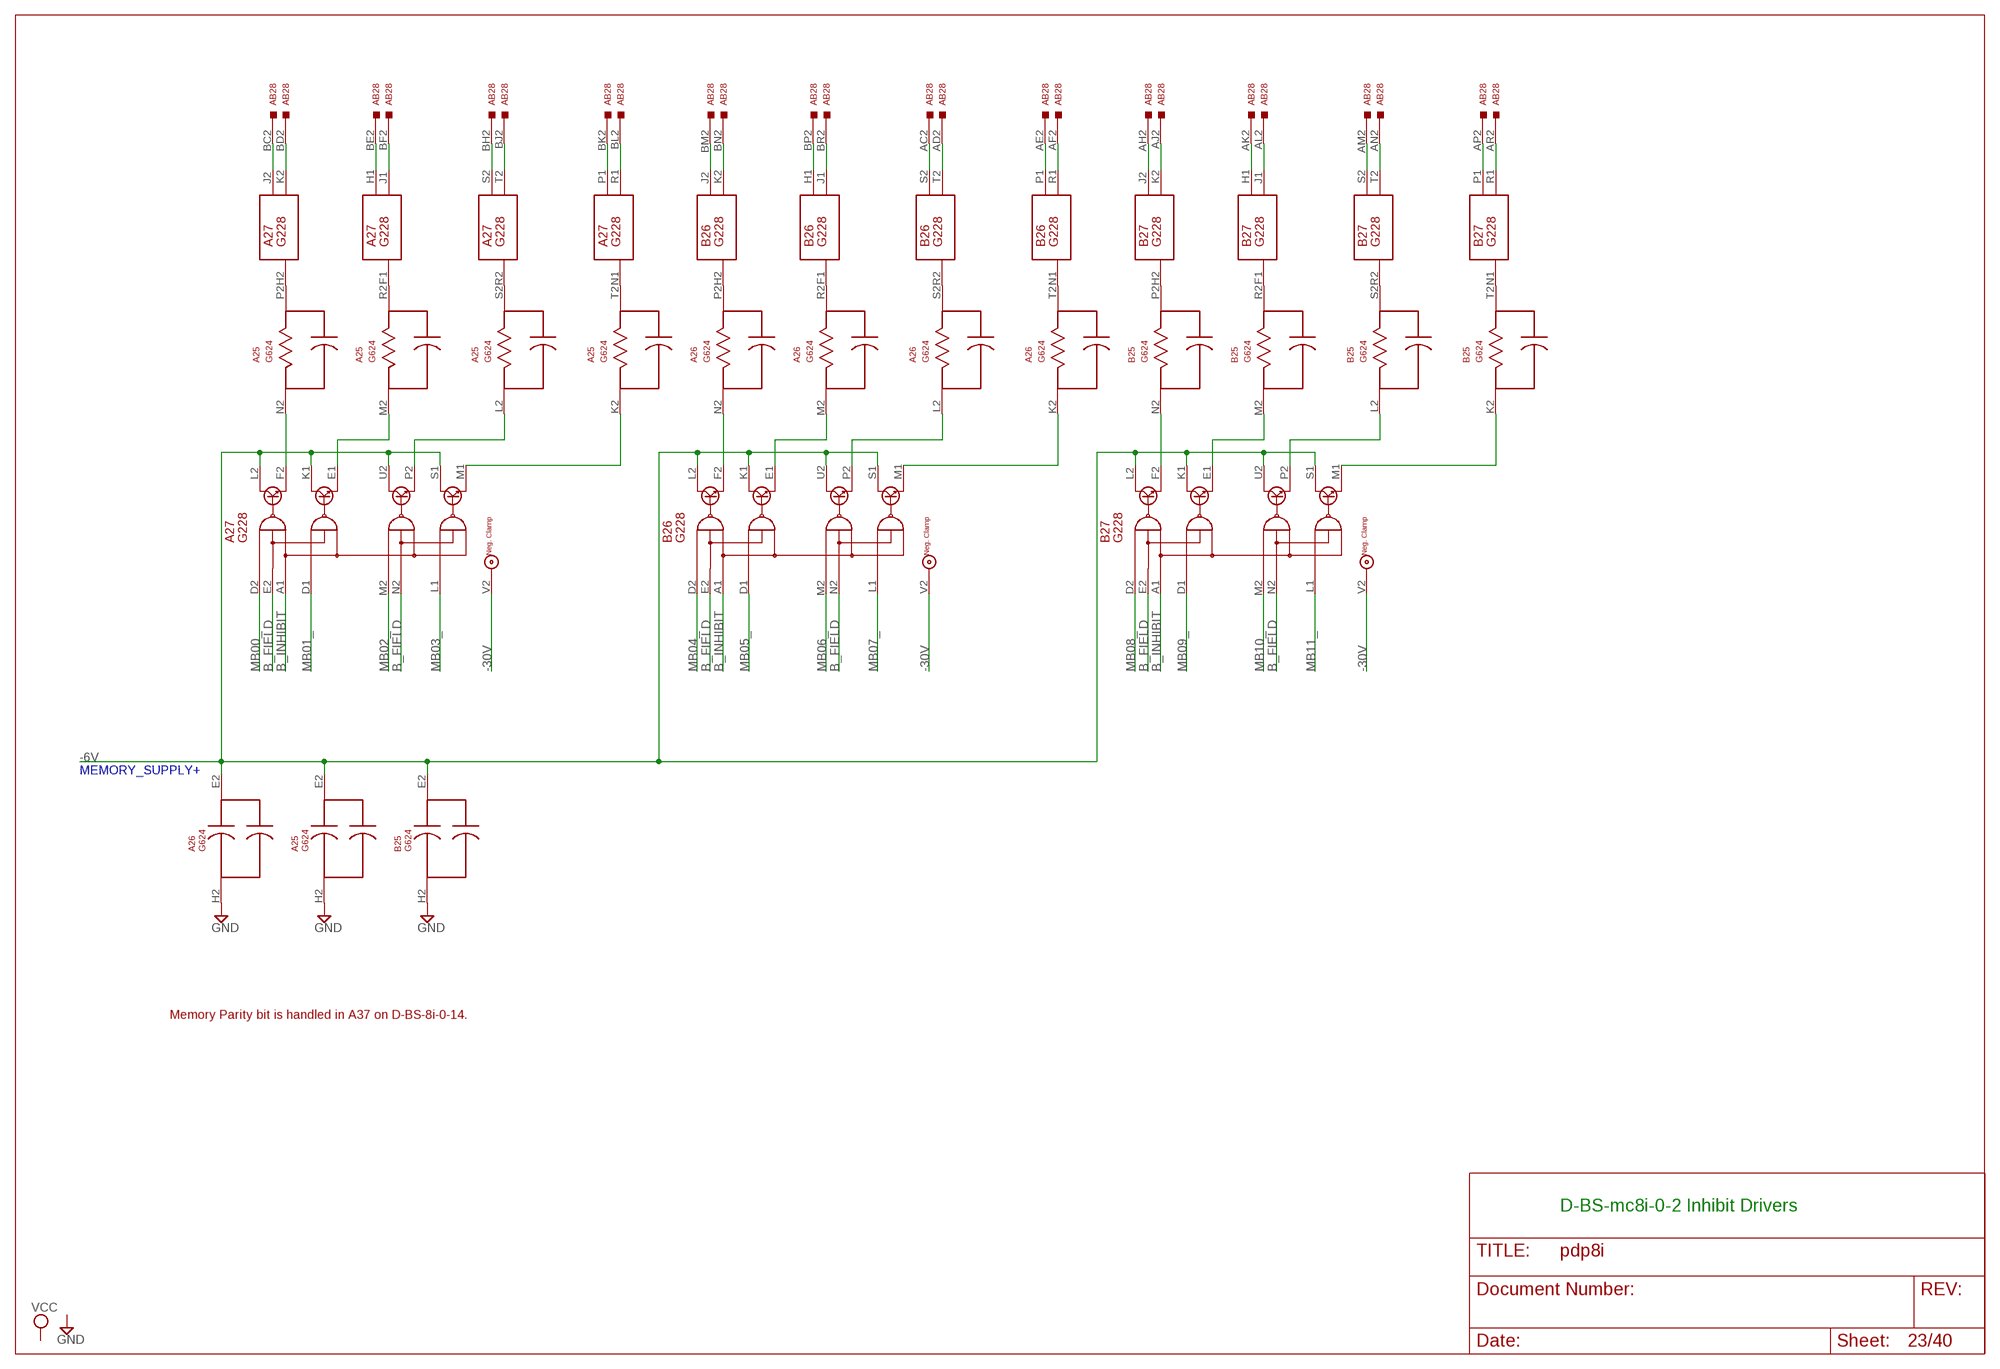
[diagram p23: schematic, sheet 23]
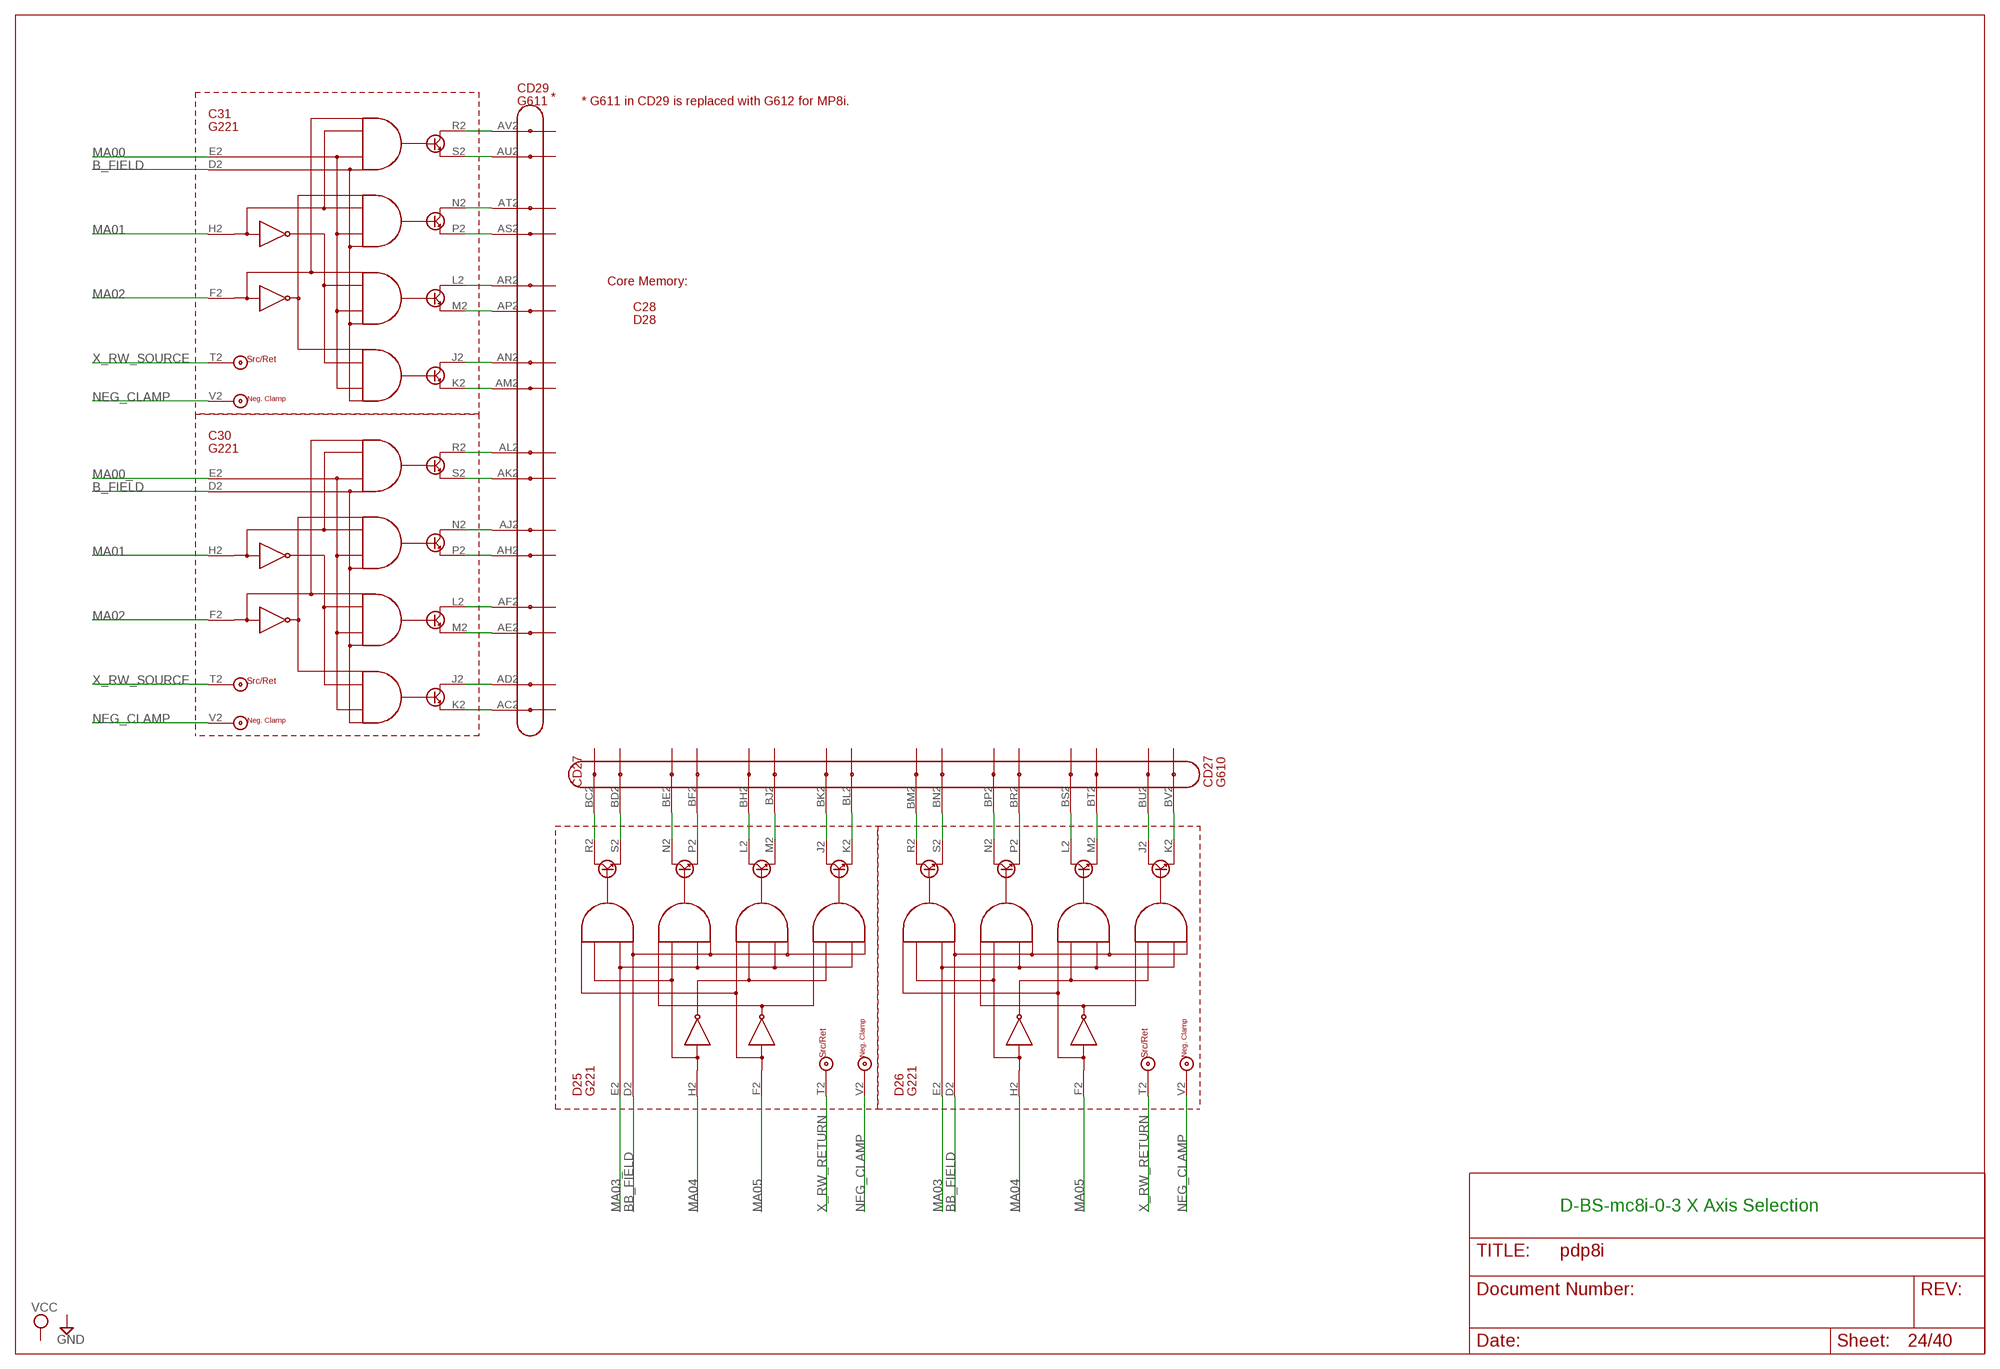
[diagram p24: schematic, sheet 24]
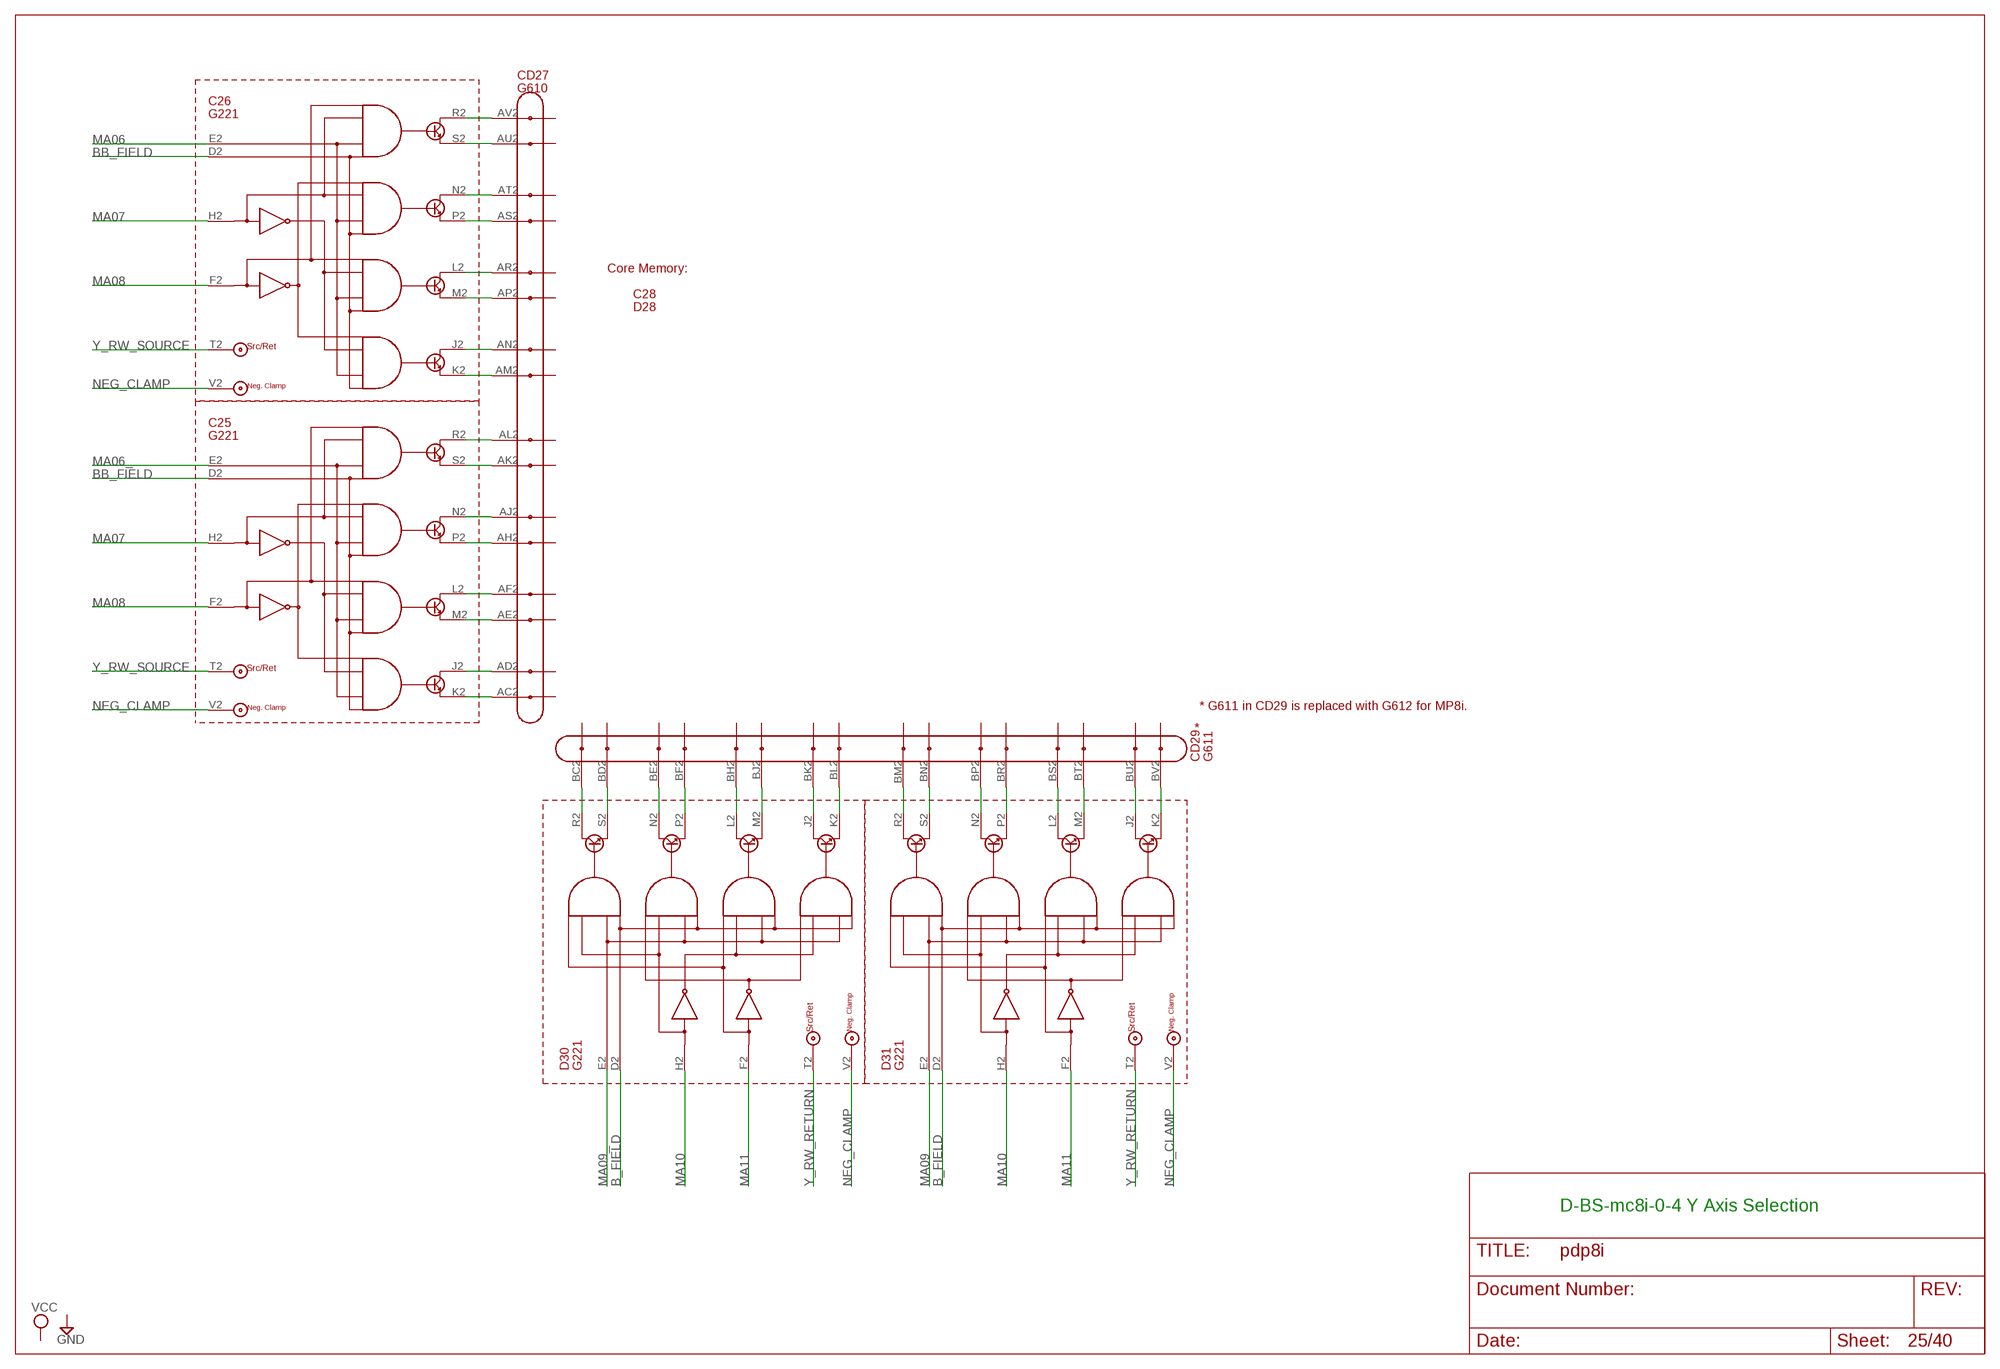
[diagram p25: schematic, sheet 25]
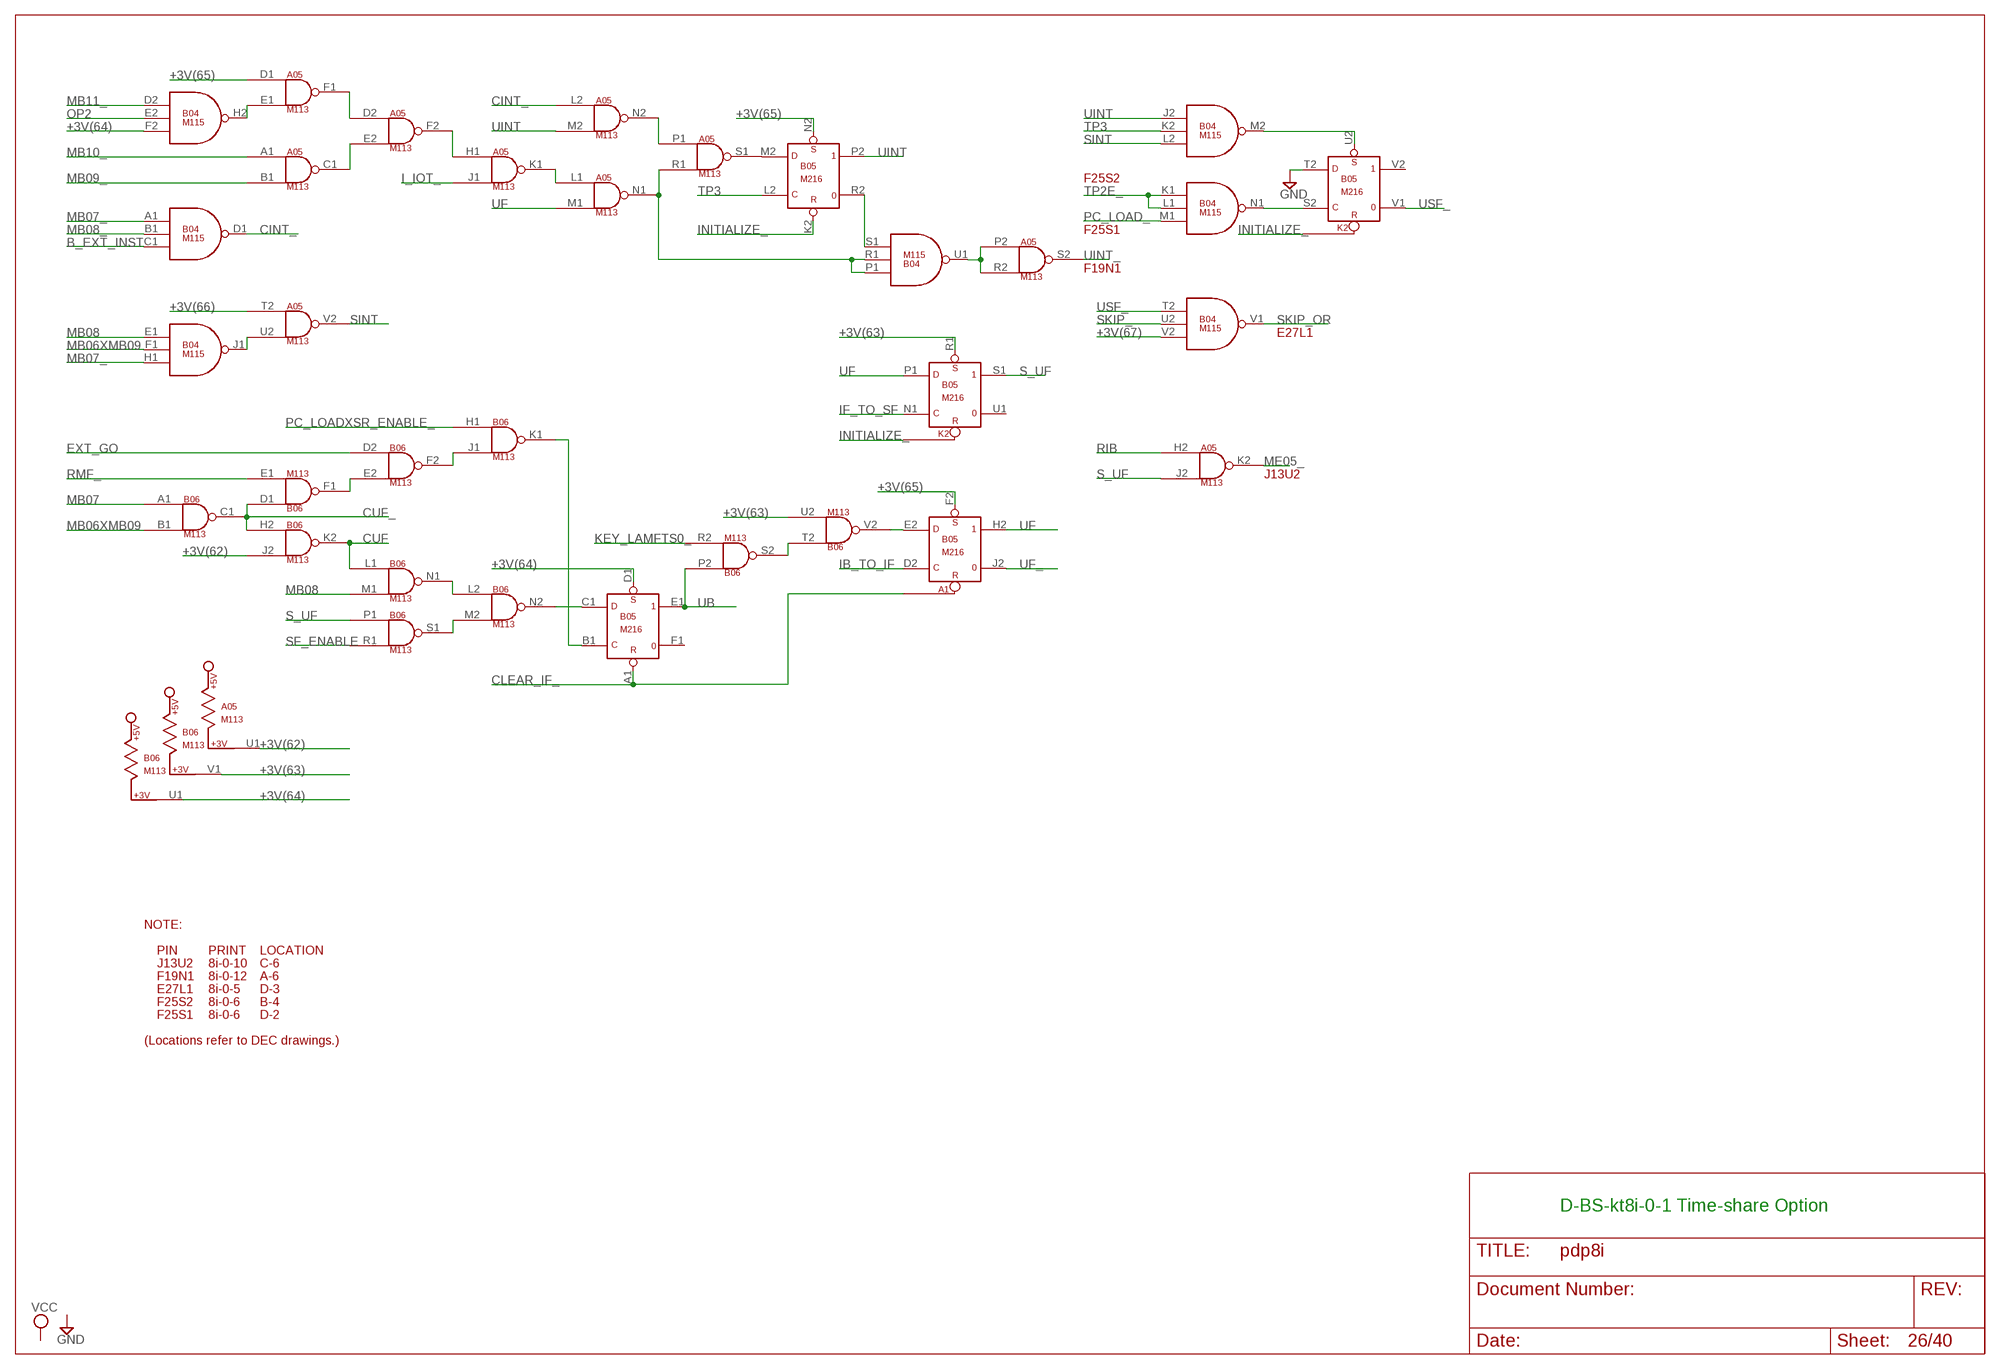
[diagram p26: schematic, sheet 26]
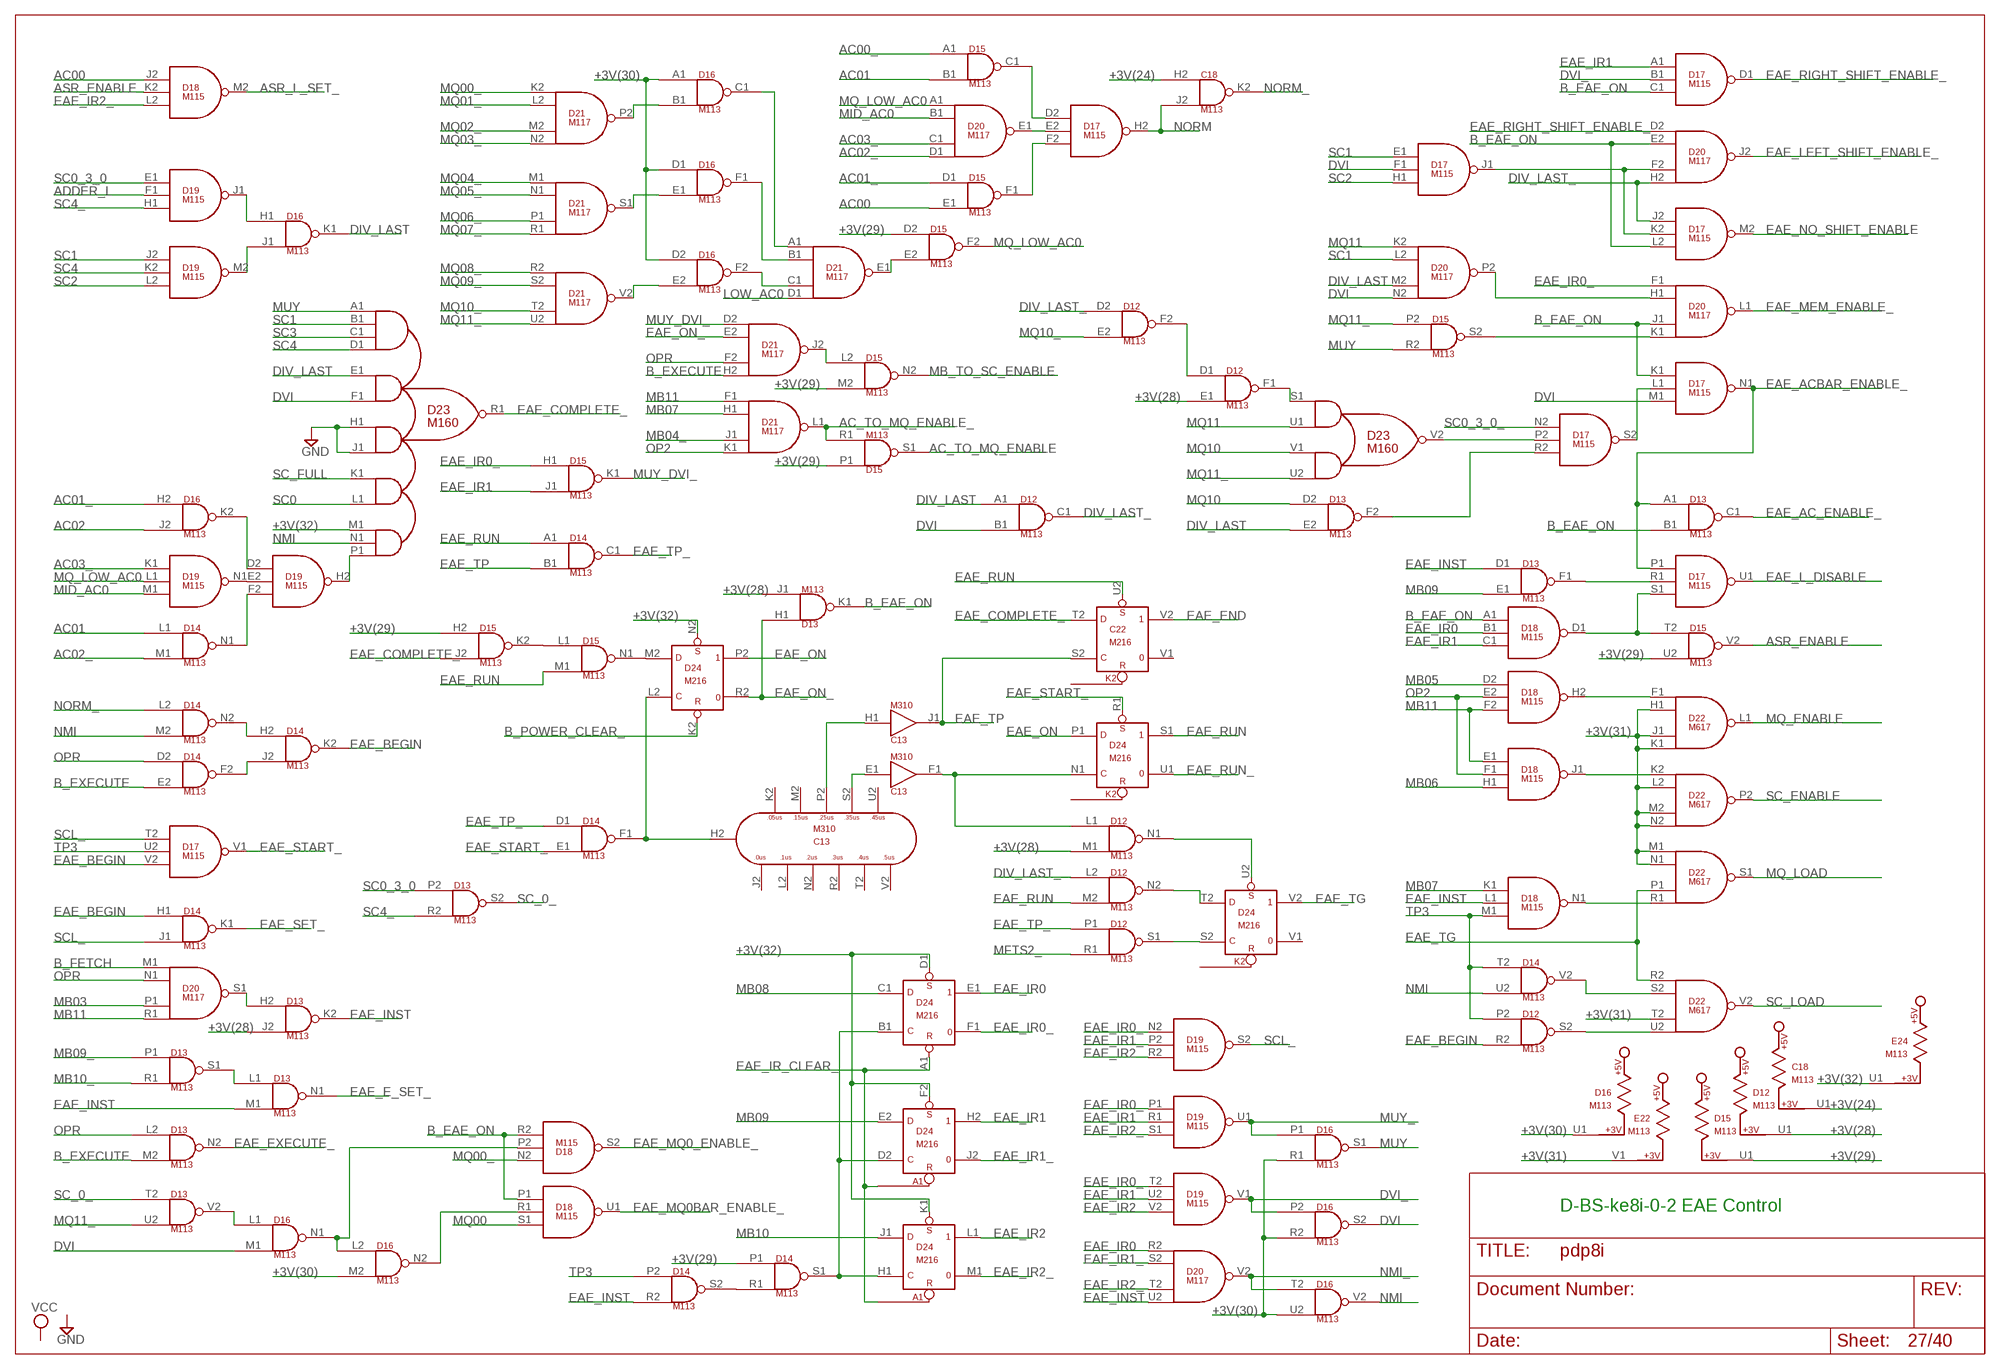
[diagram p27: schematic, sheet 27]
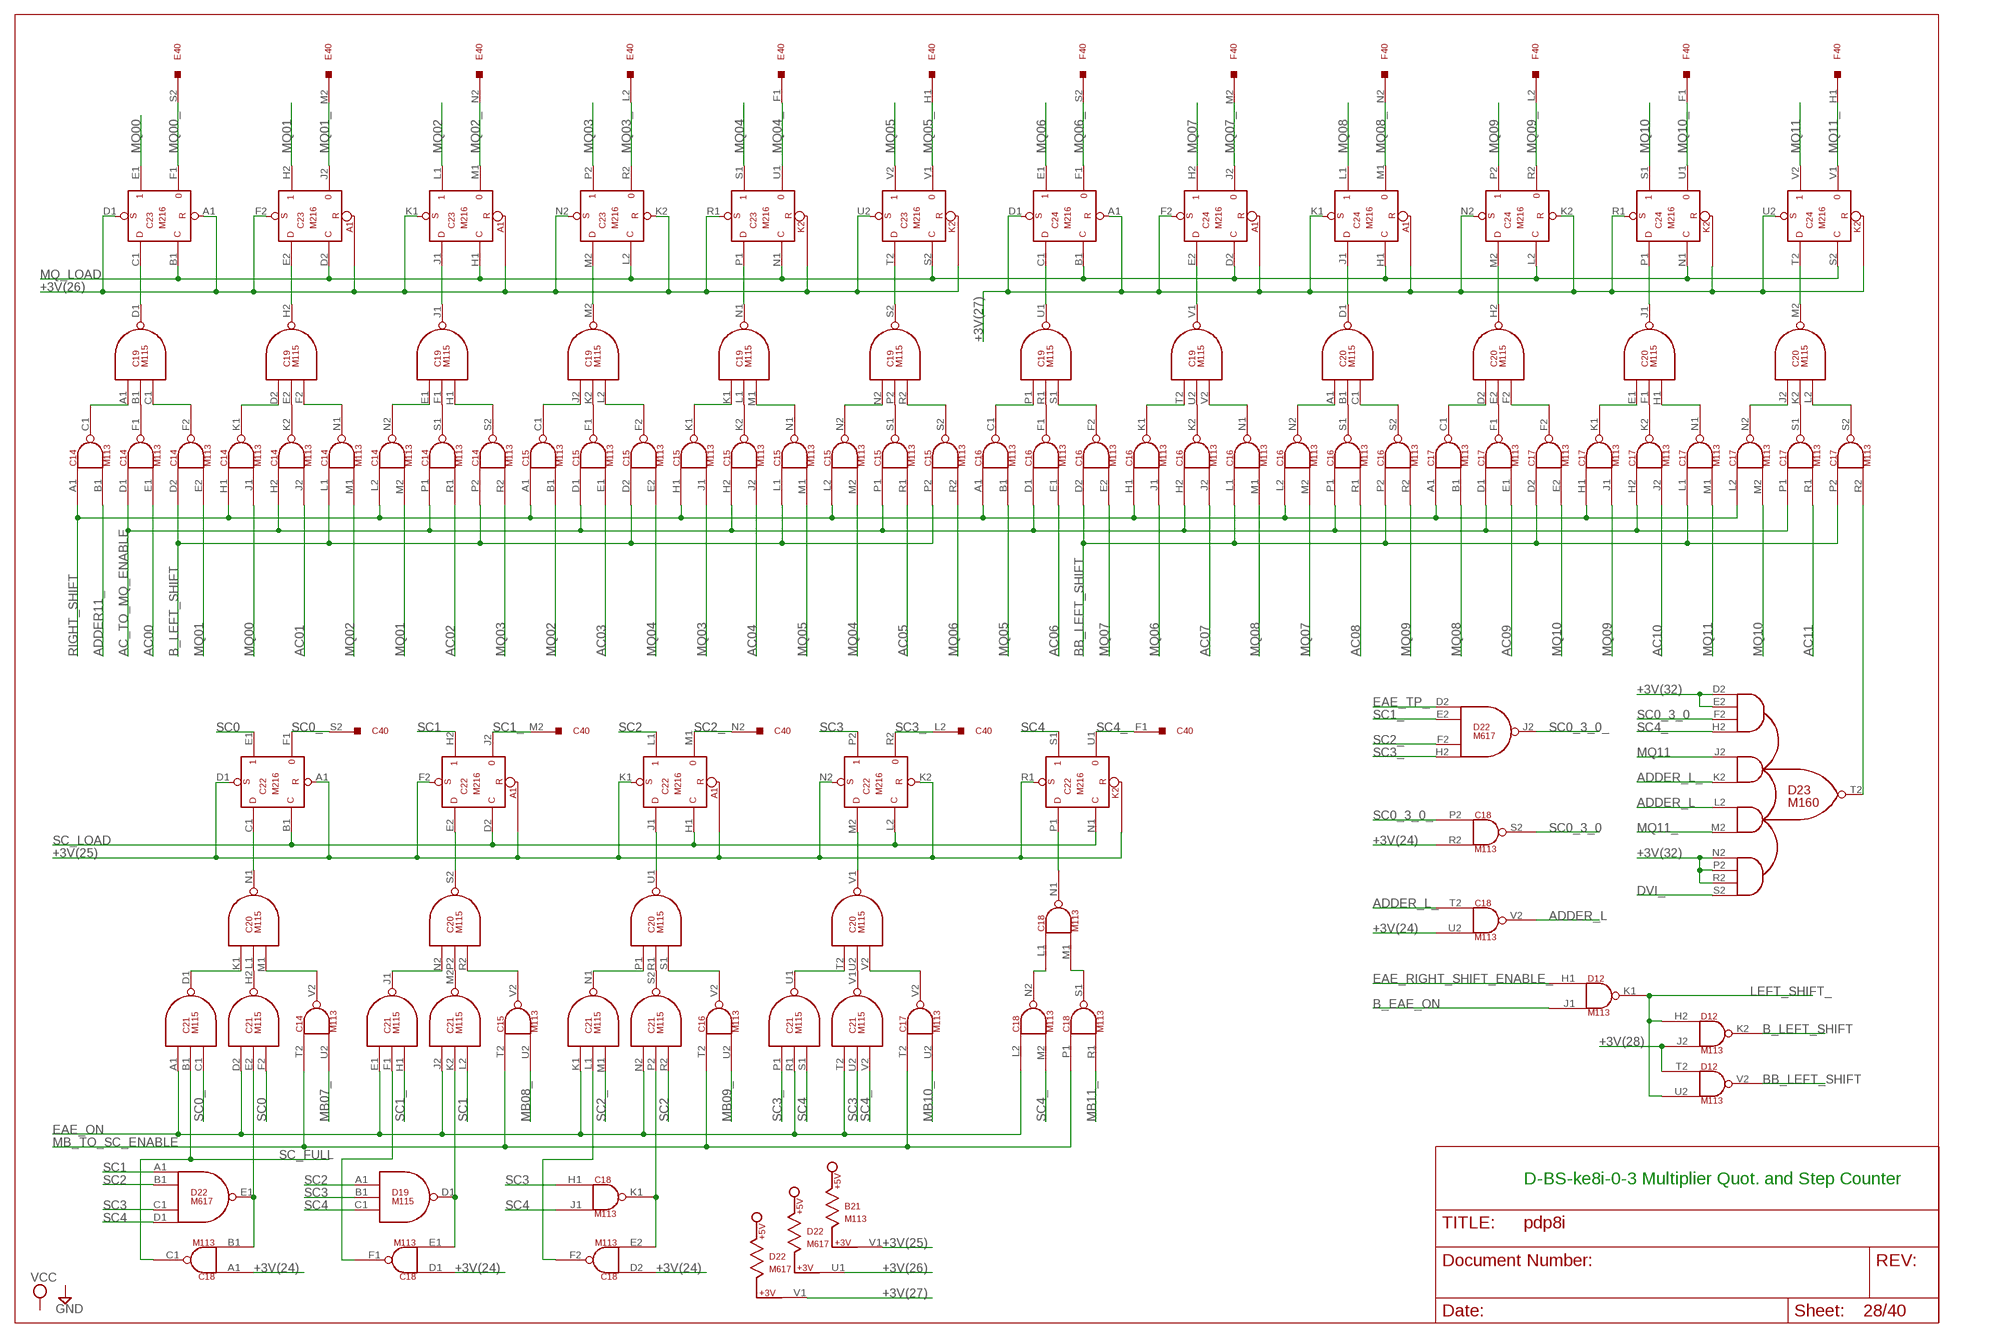
[diagram p28: schematic, sheet 28]
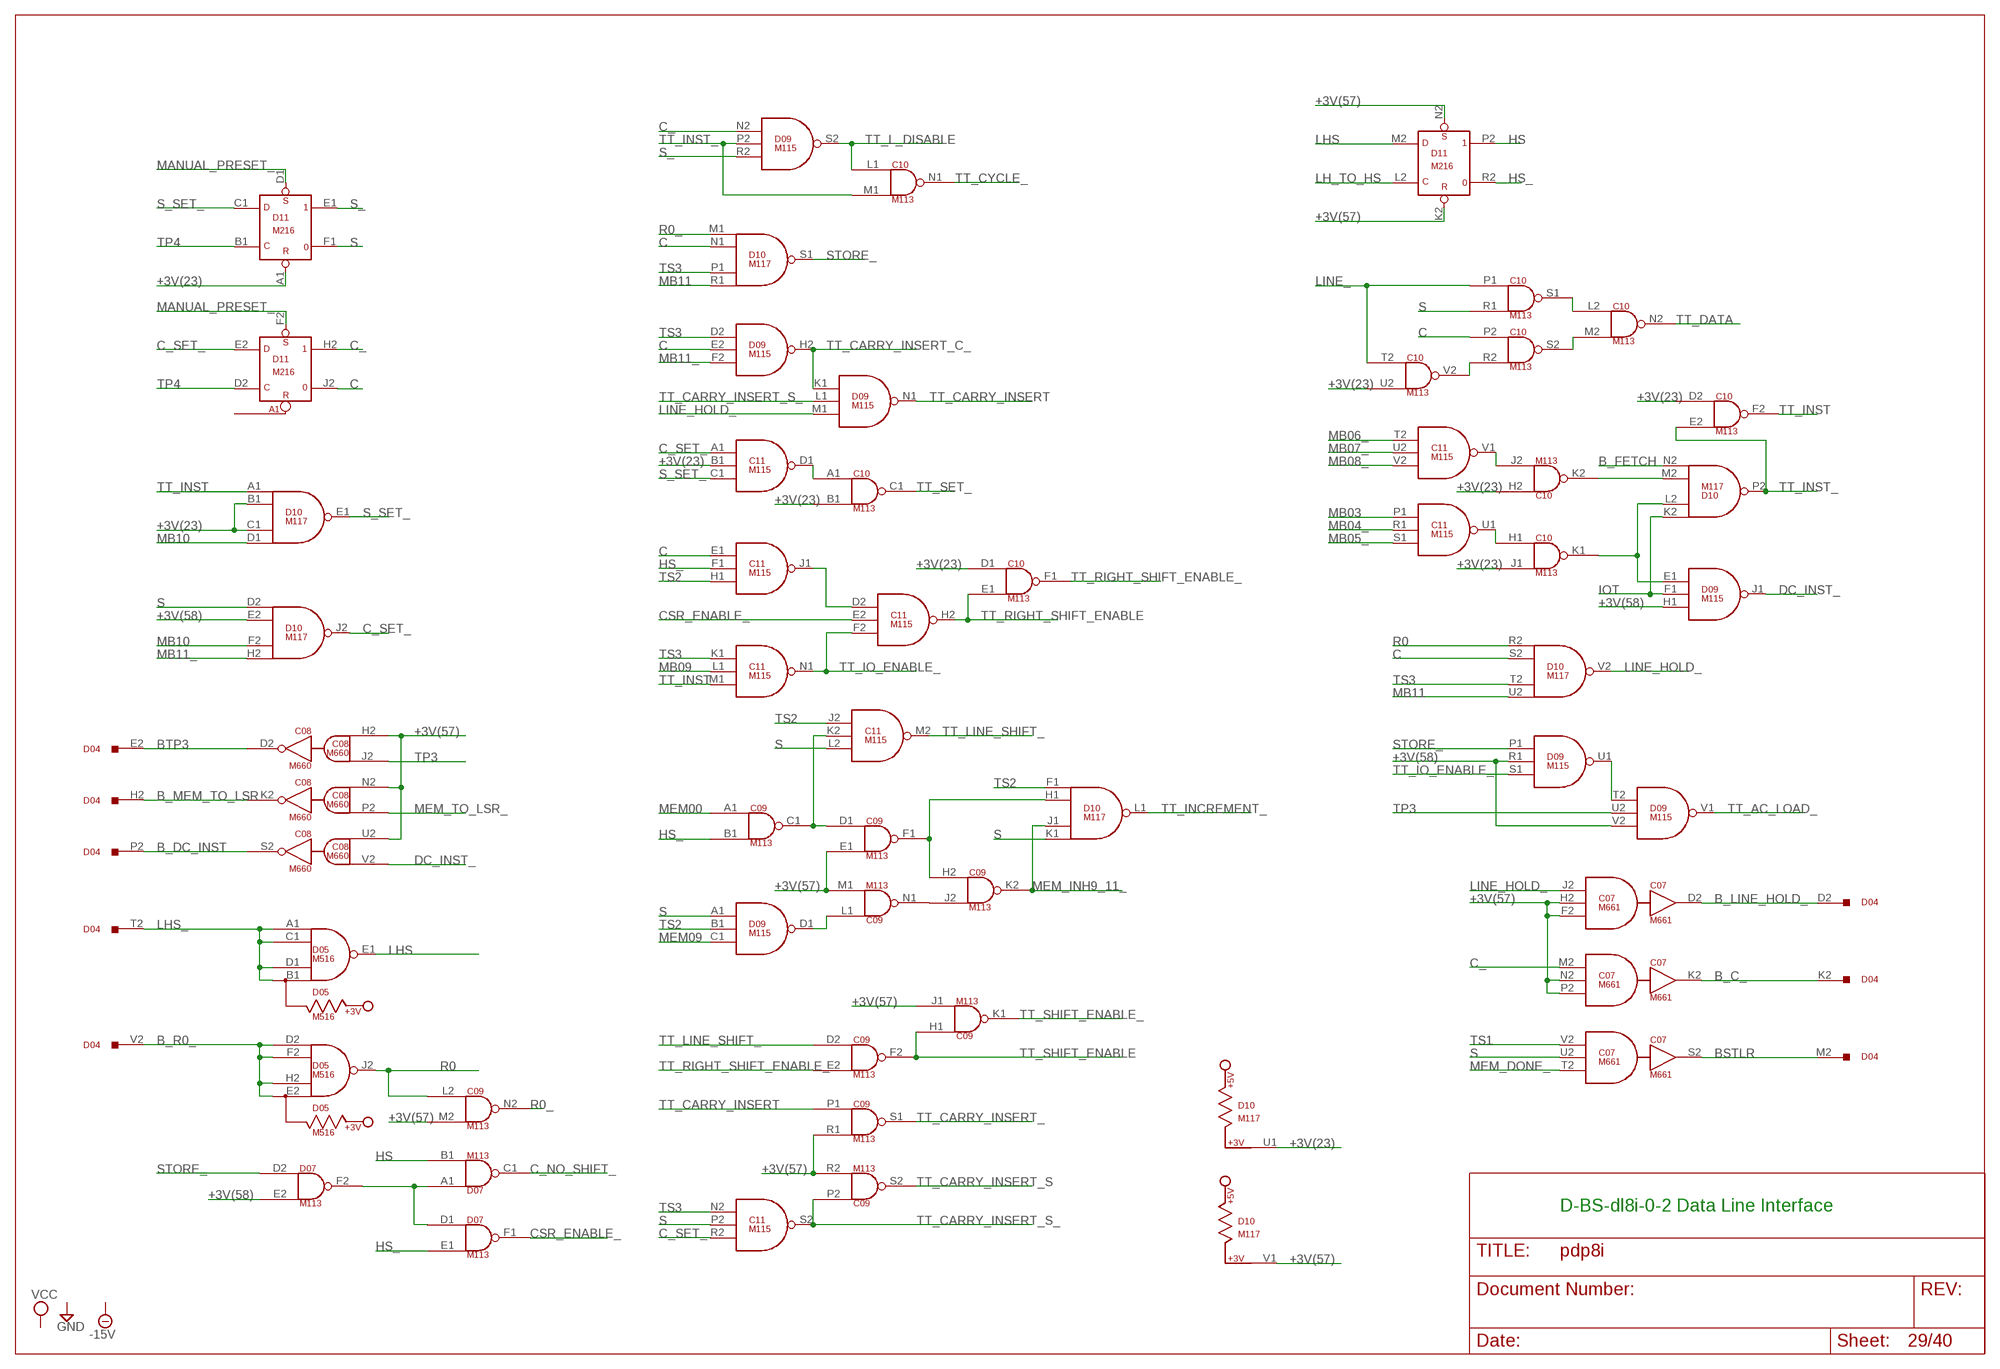
[diagram p29: schematic, sheet 29]
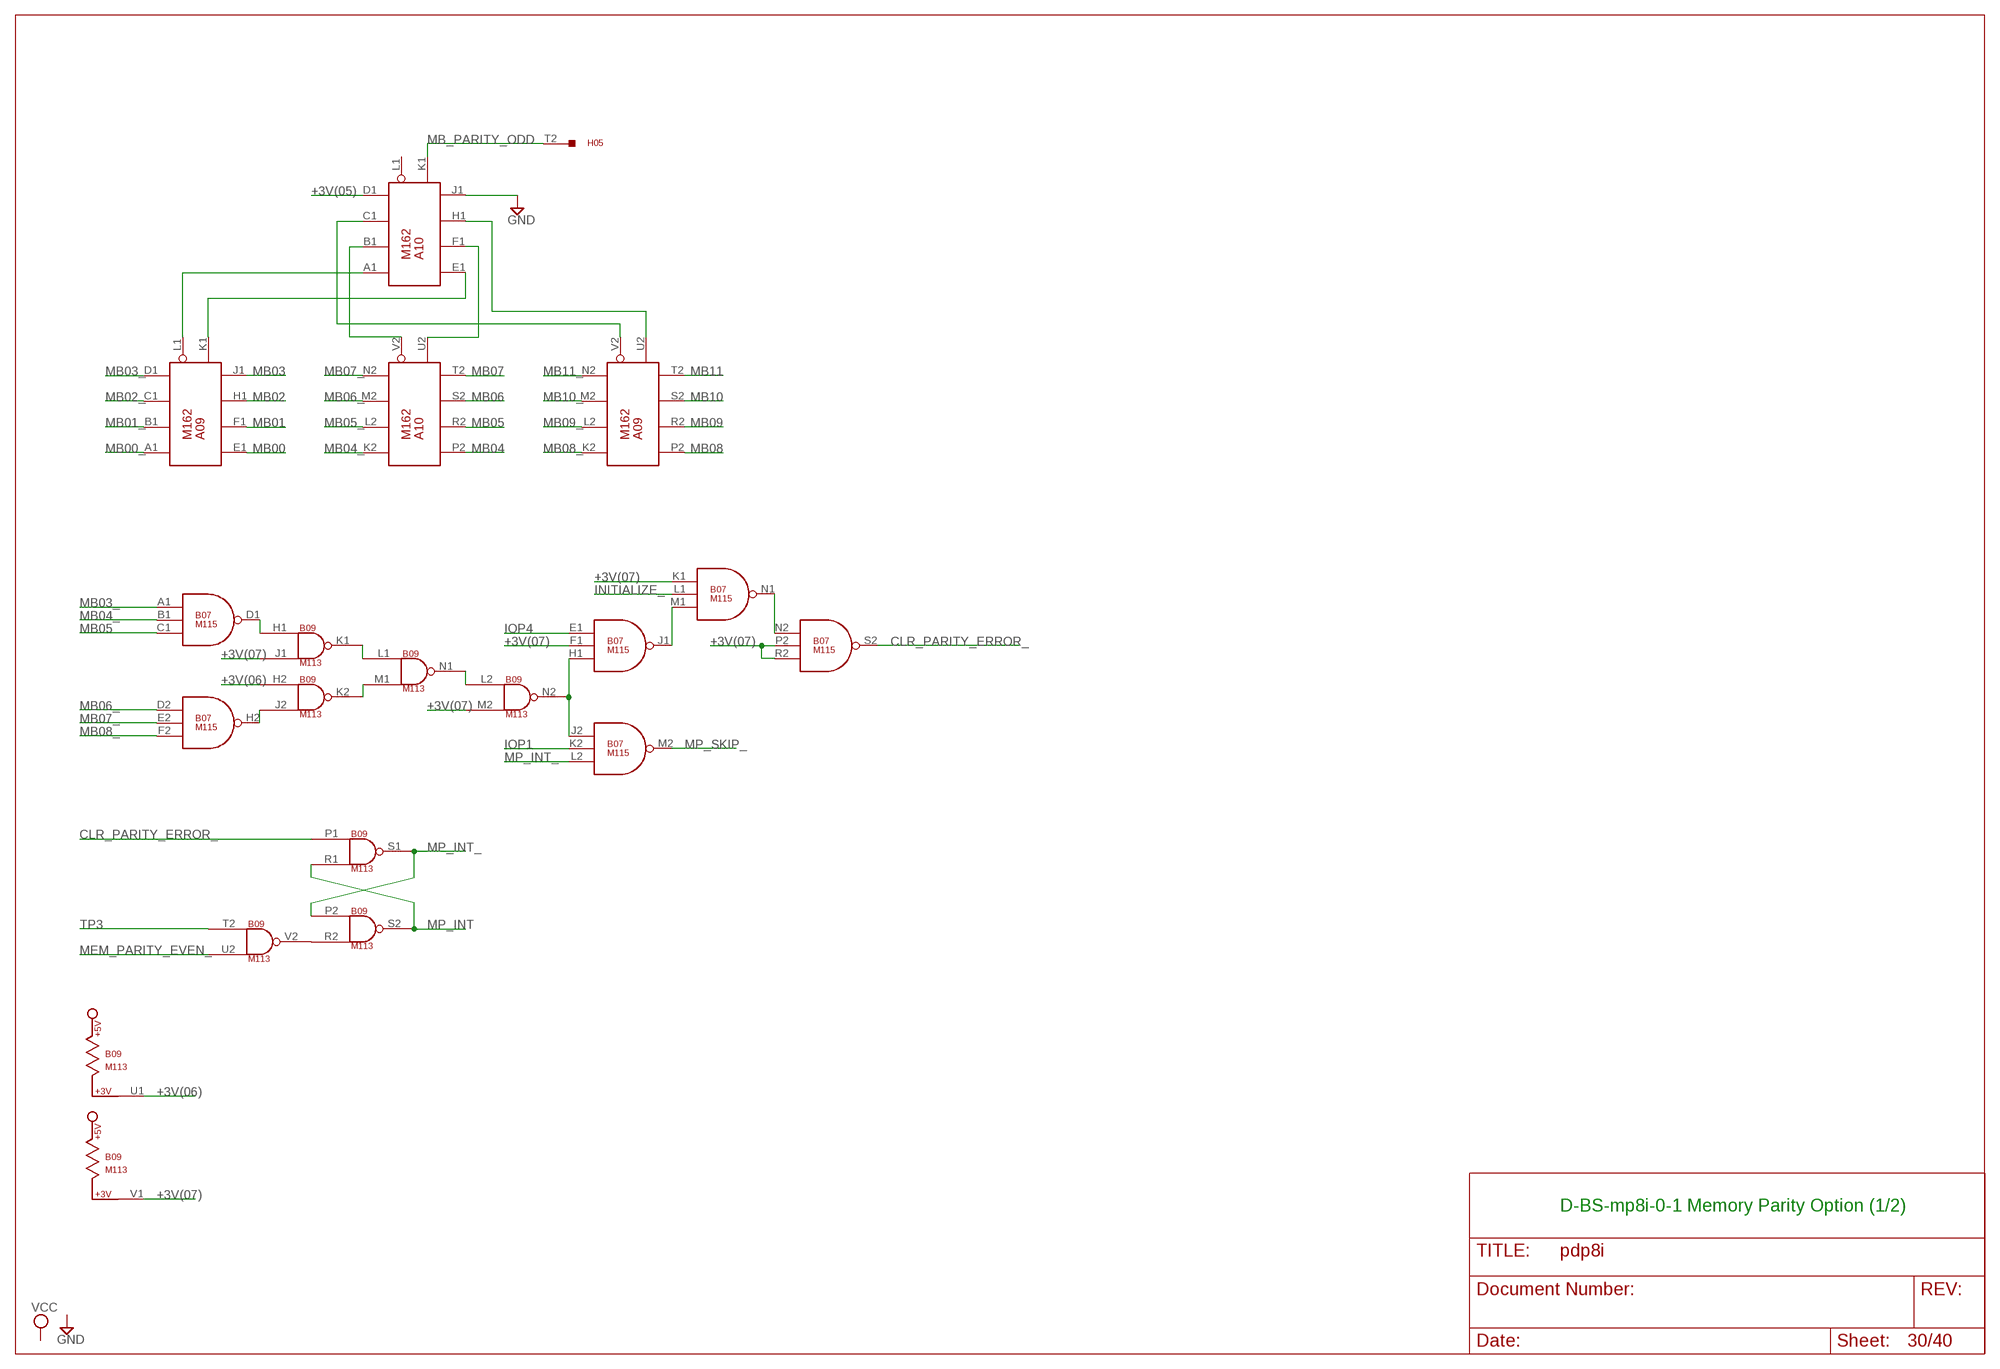
[diagram p30: schematic, sheet 30]
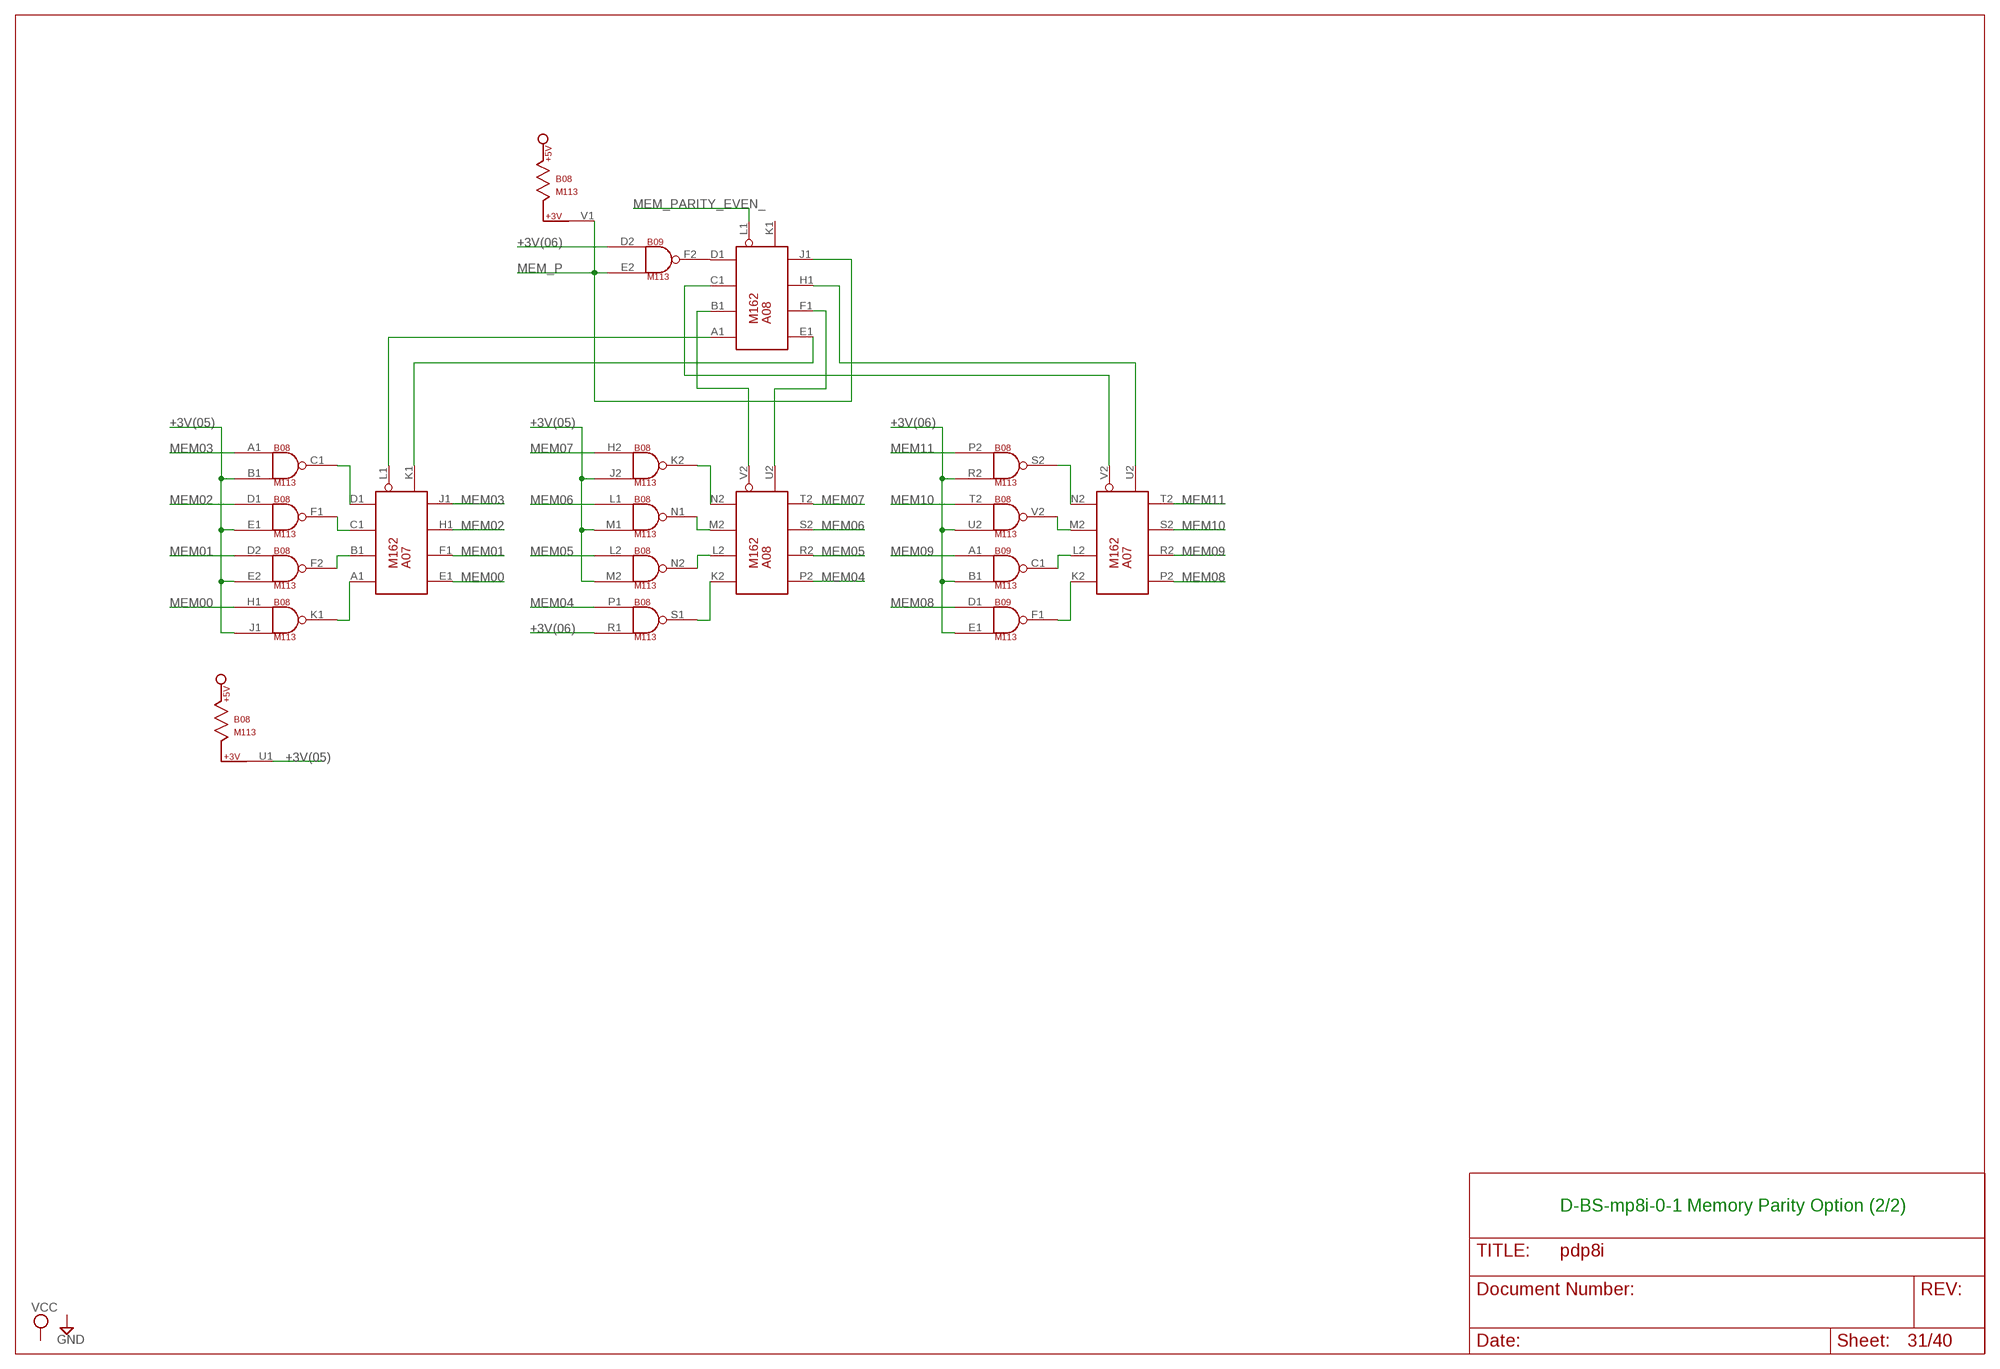
[diagram p31: schematic, sheet 31]
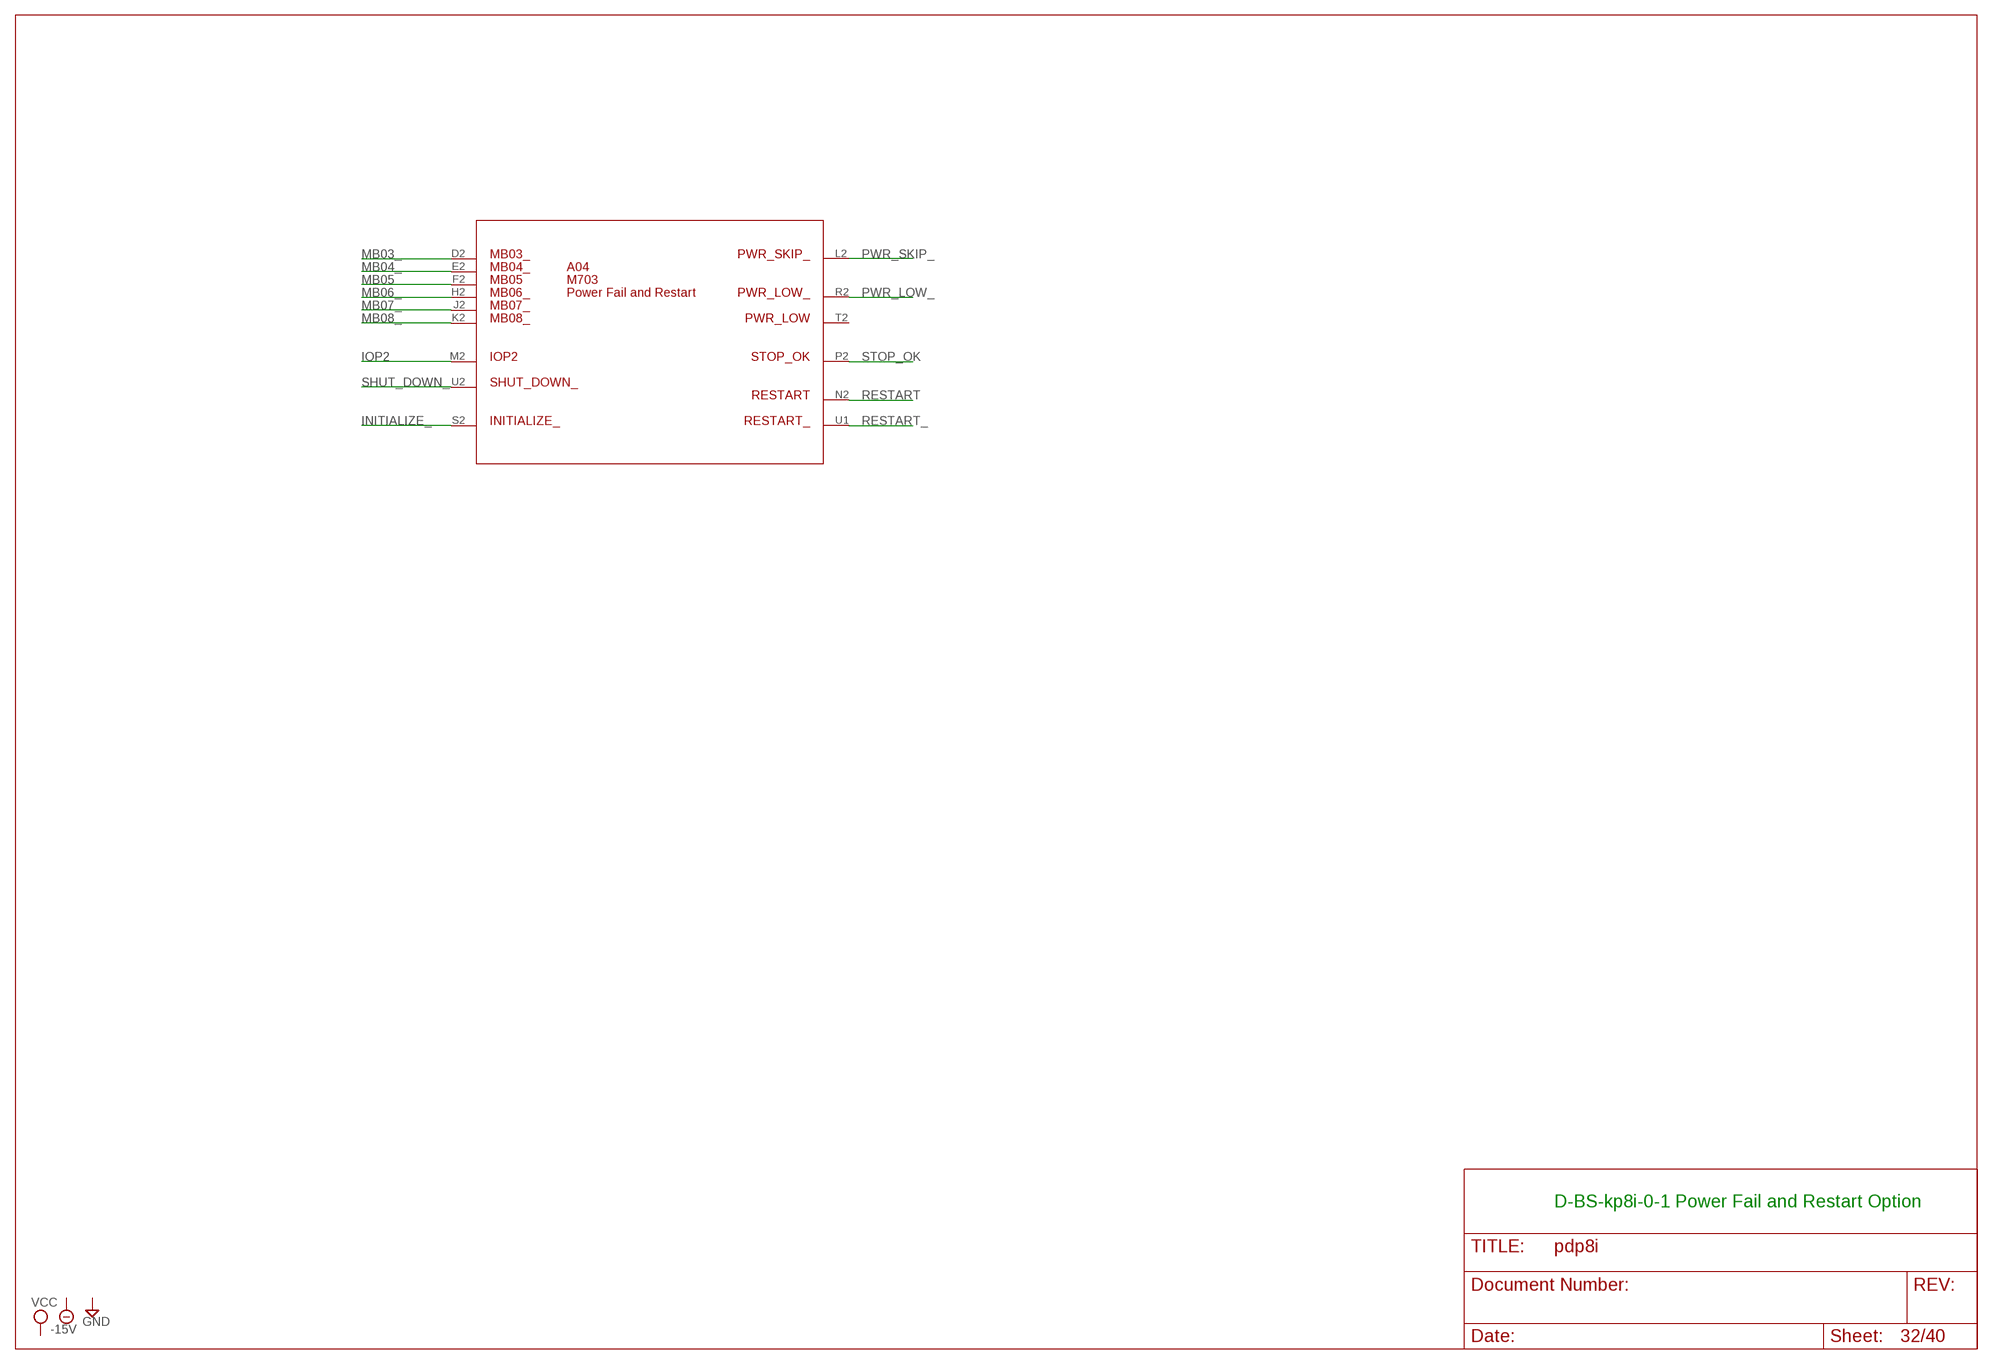
[diagram p32: schematic, sheet 32]
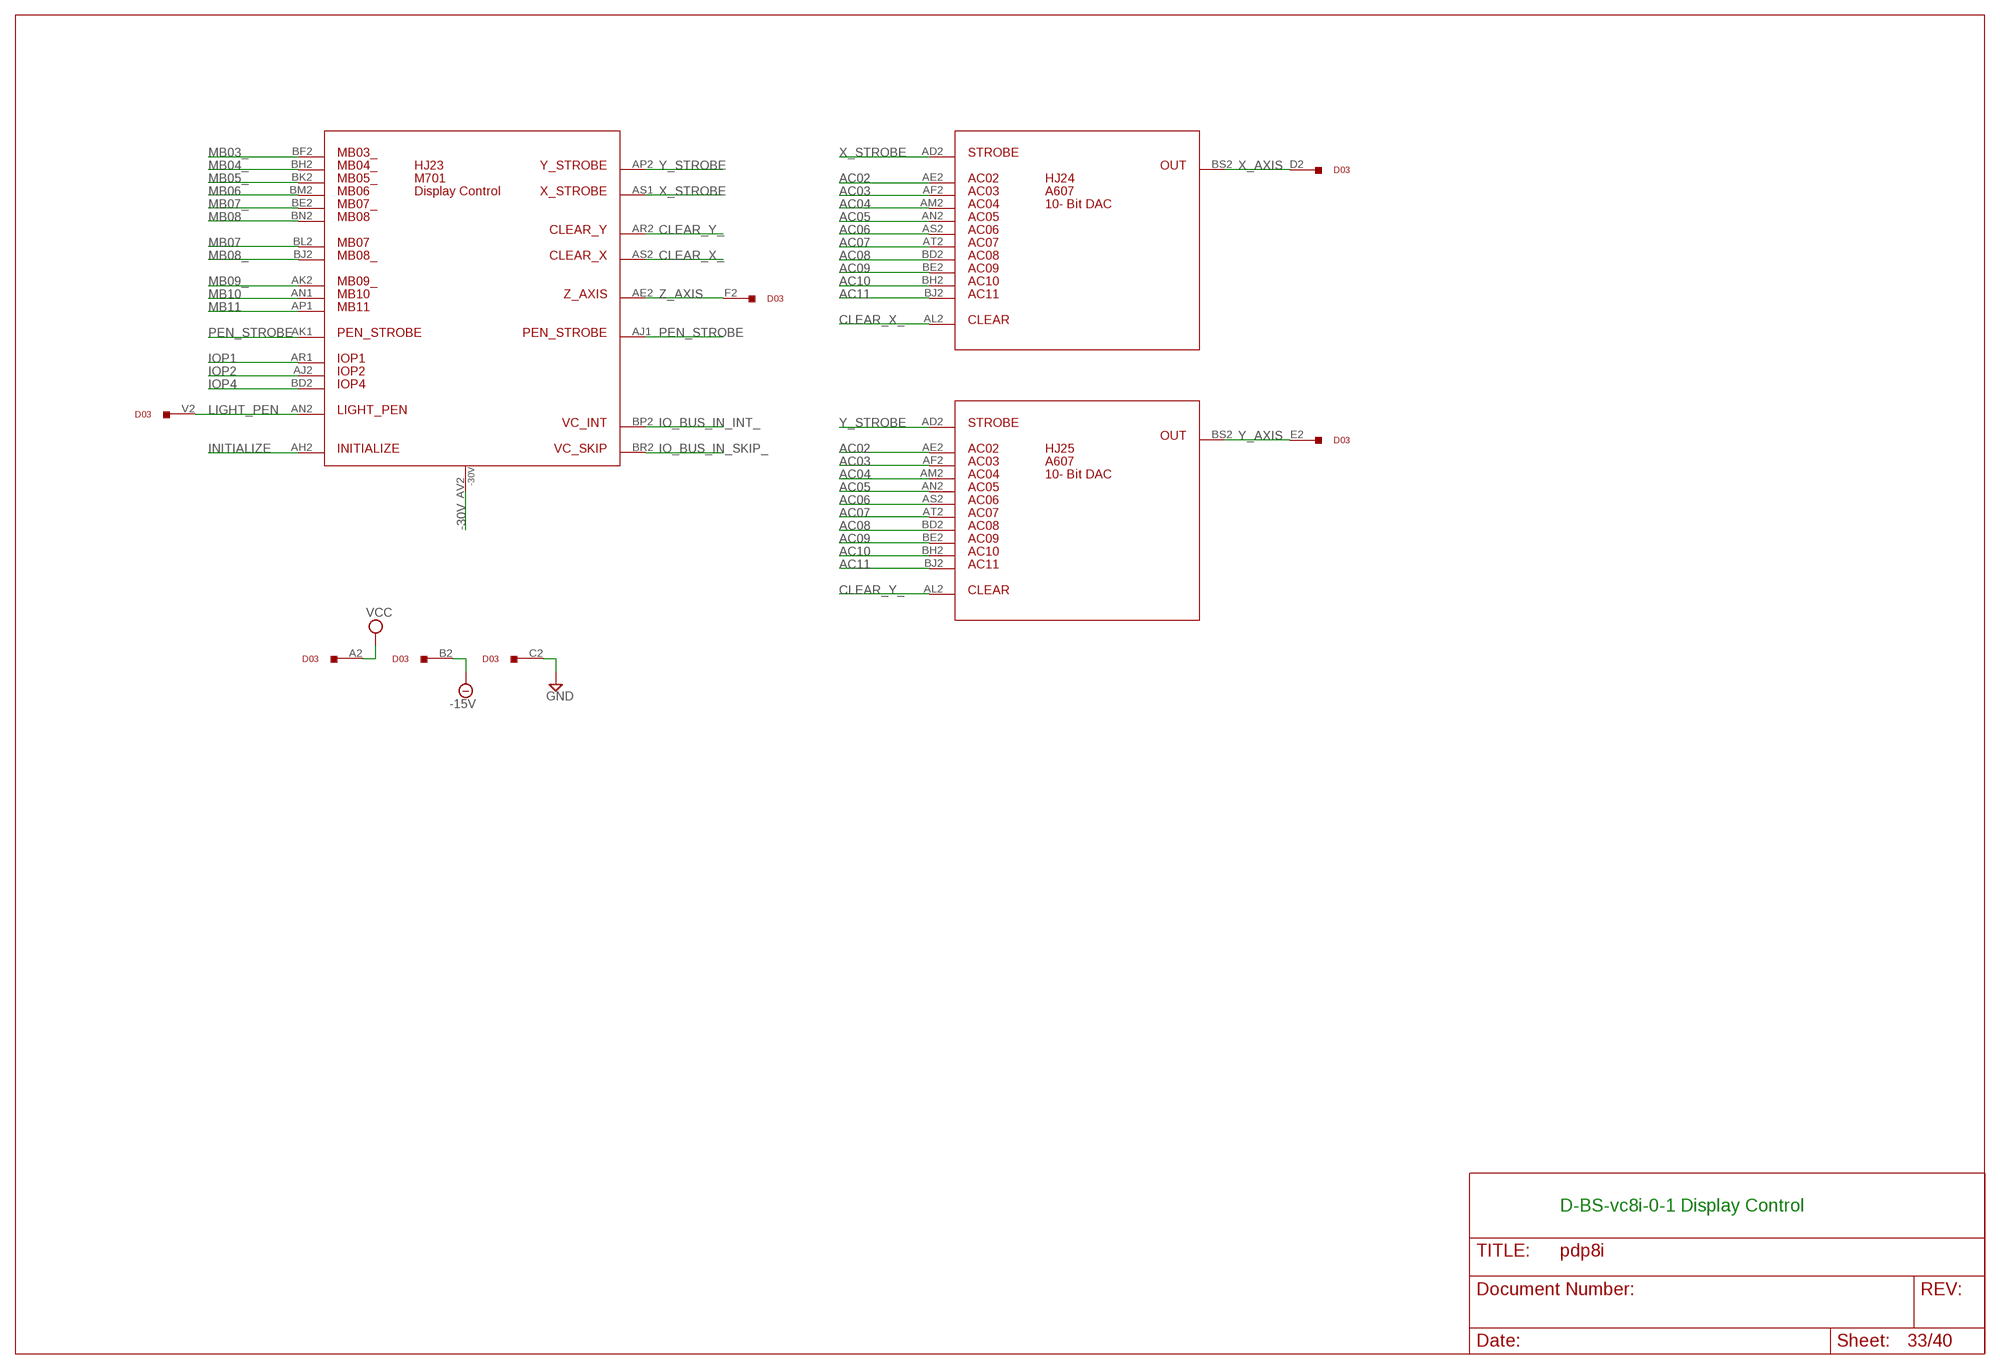
[diagram p33: schematic, sheet 33]
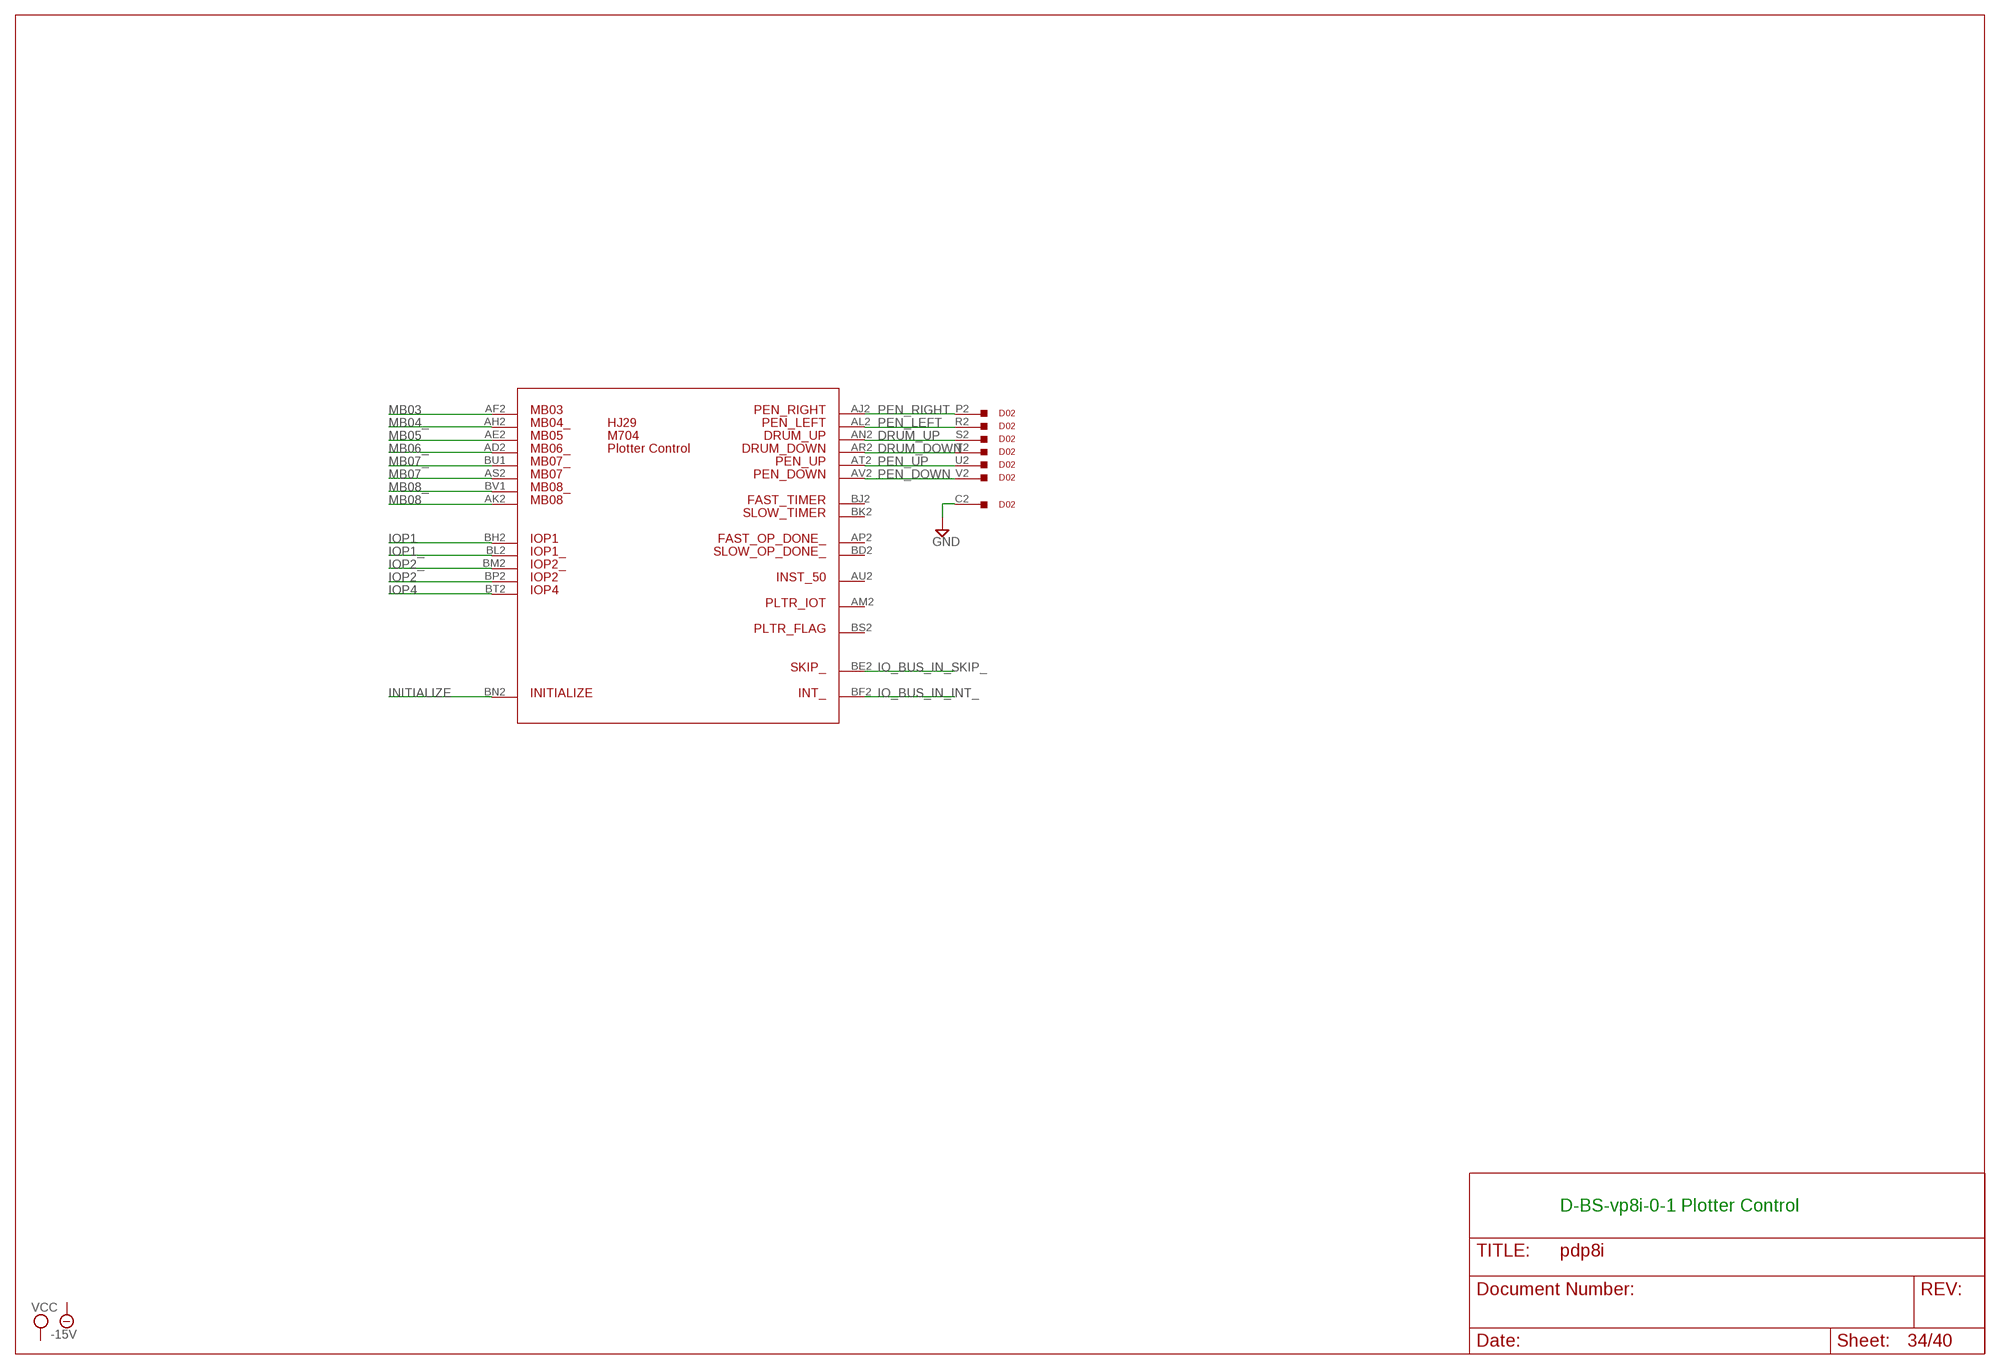
[diagram p34: schematic, sheet 34]
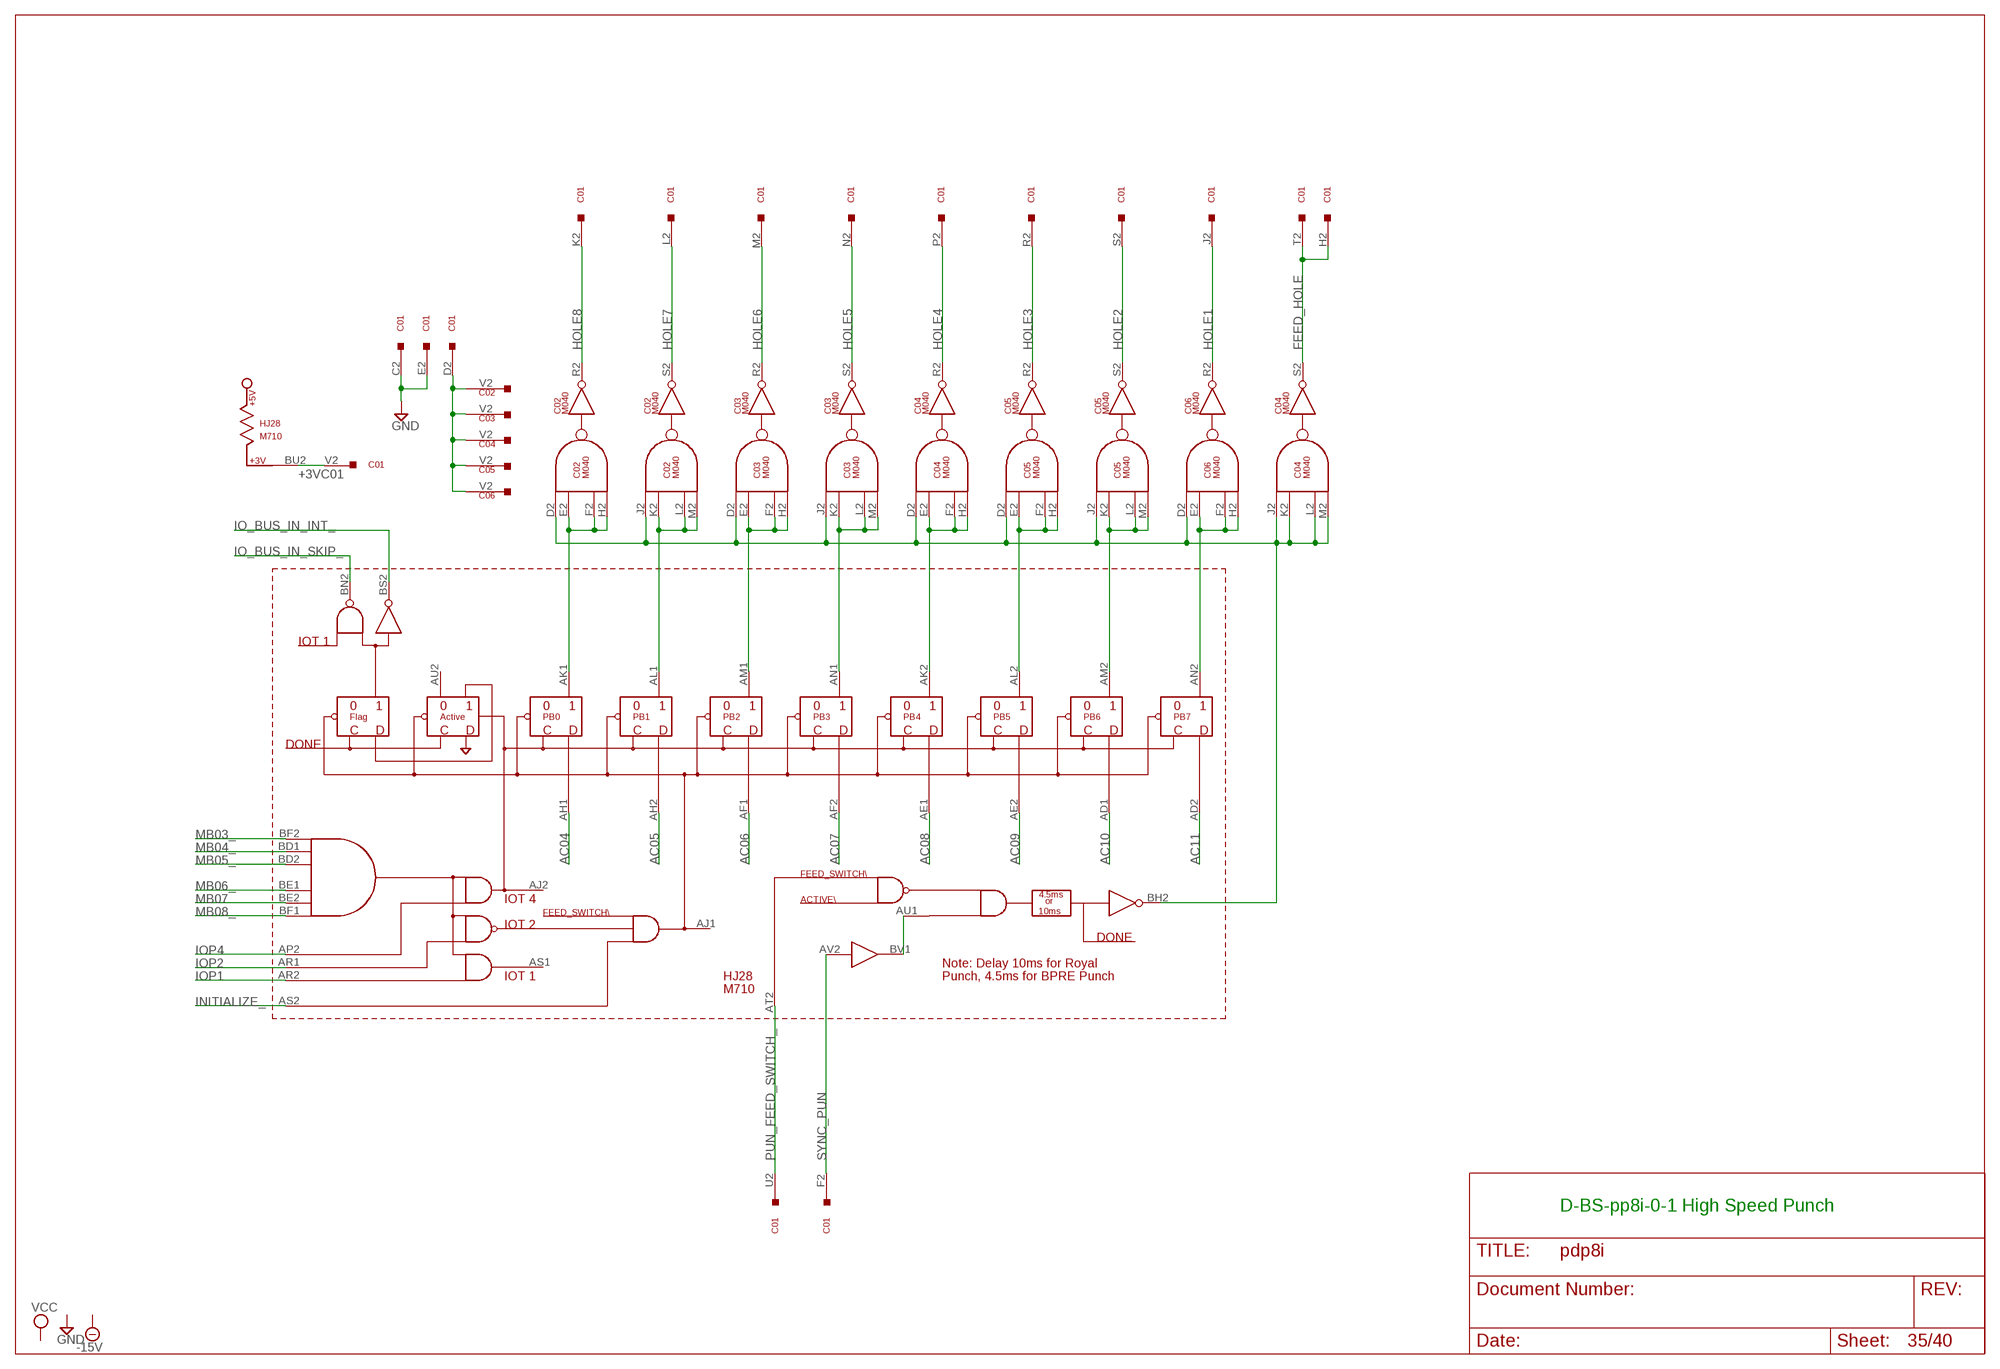
[diagram p35: schematic, sheet 35]
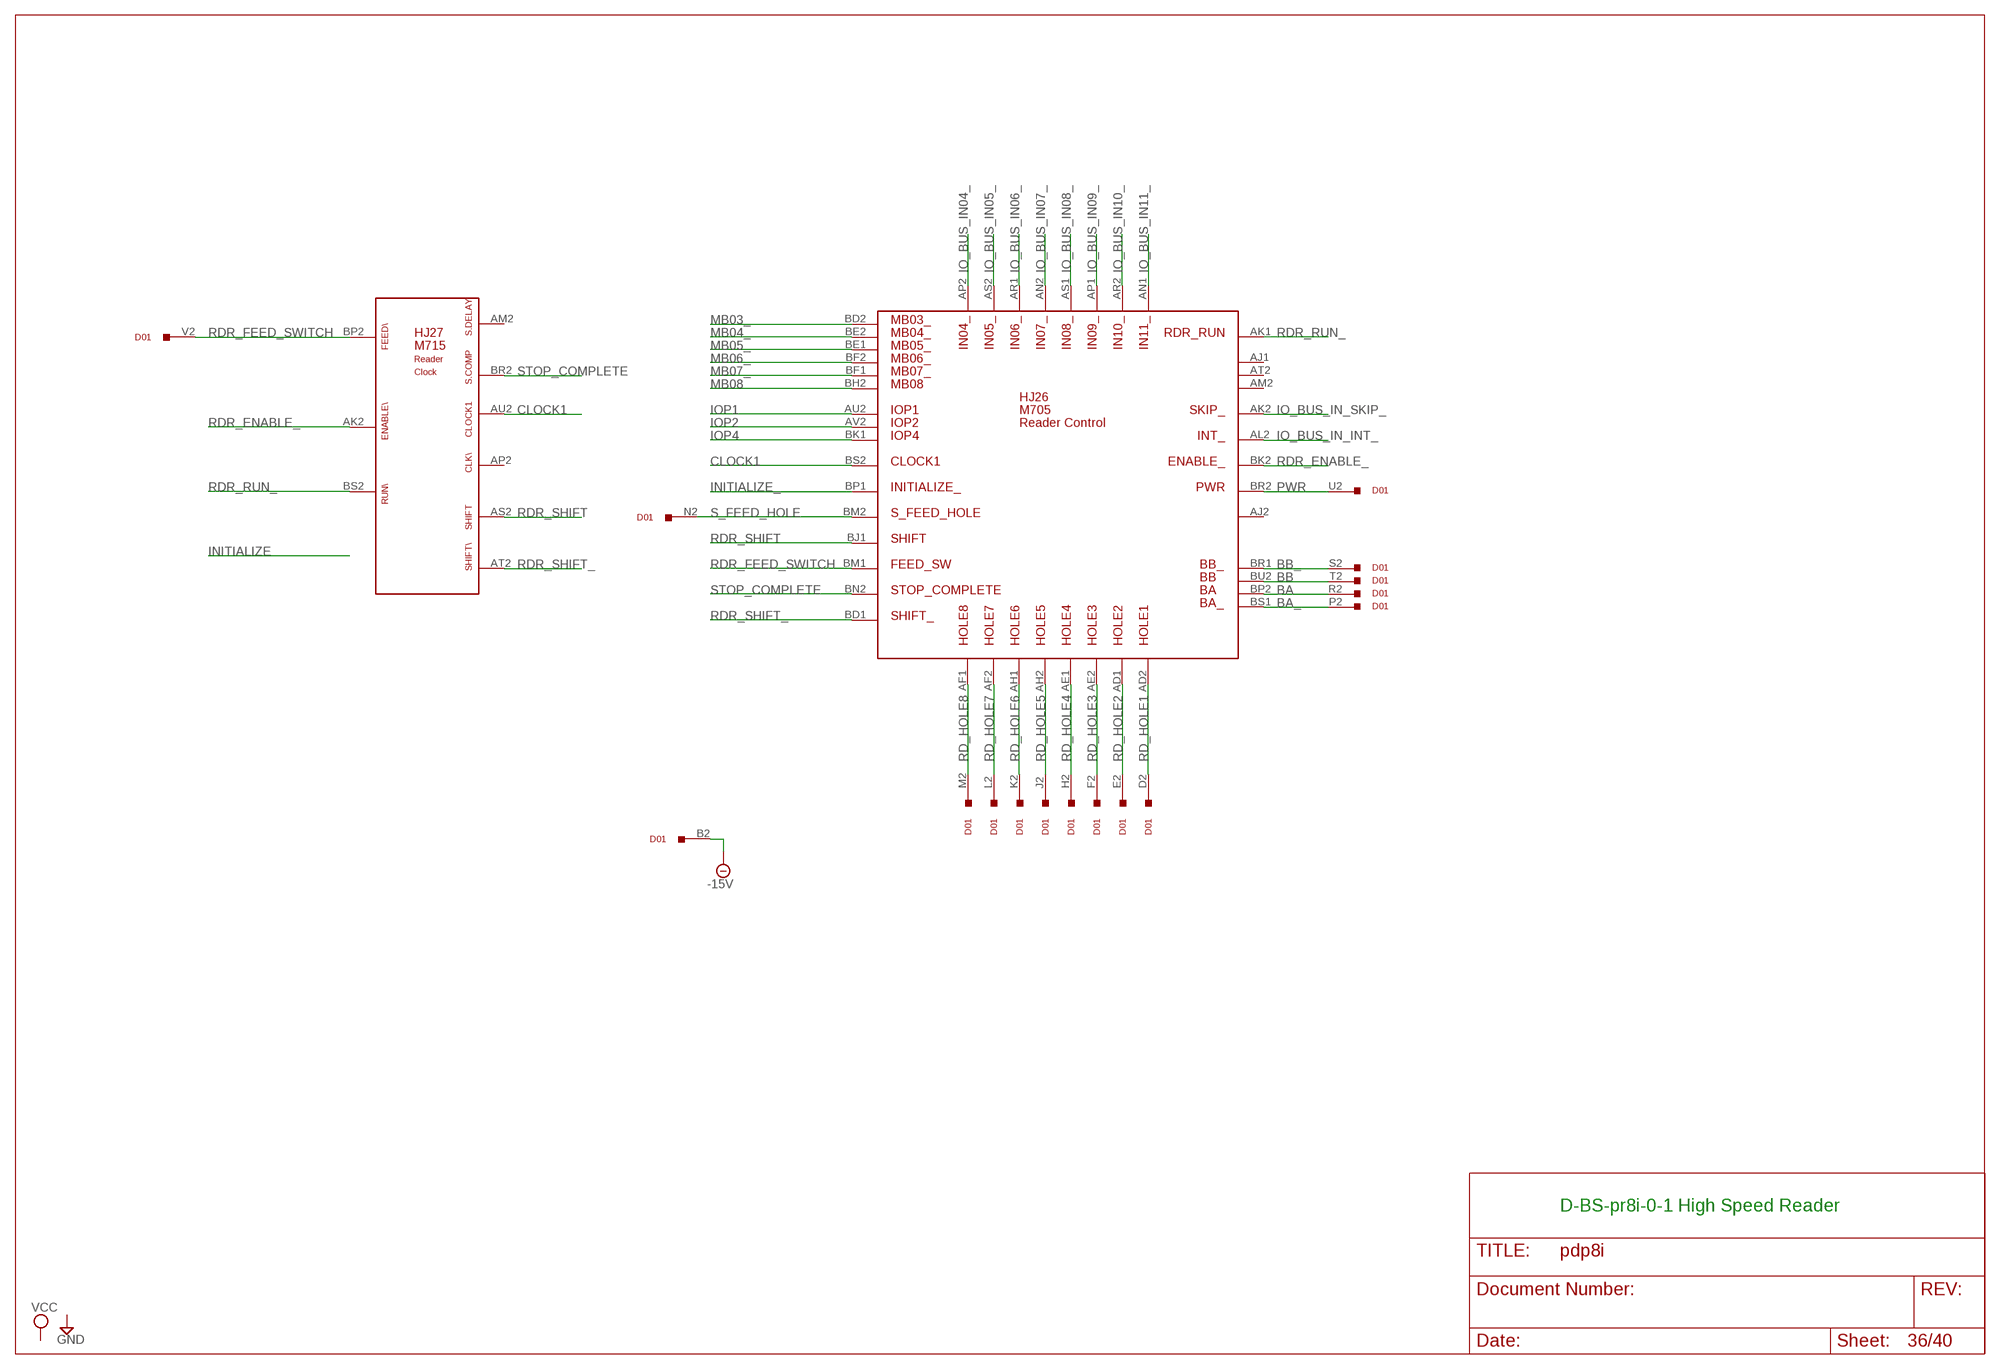
[diagram p36: schematic, sheet 36]
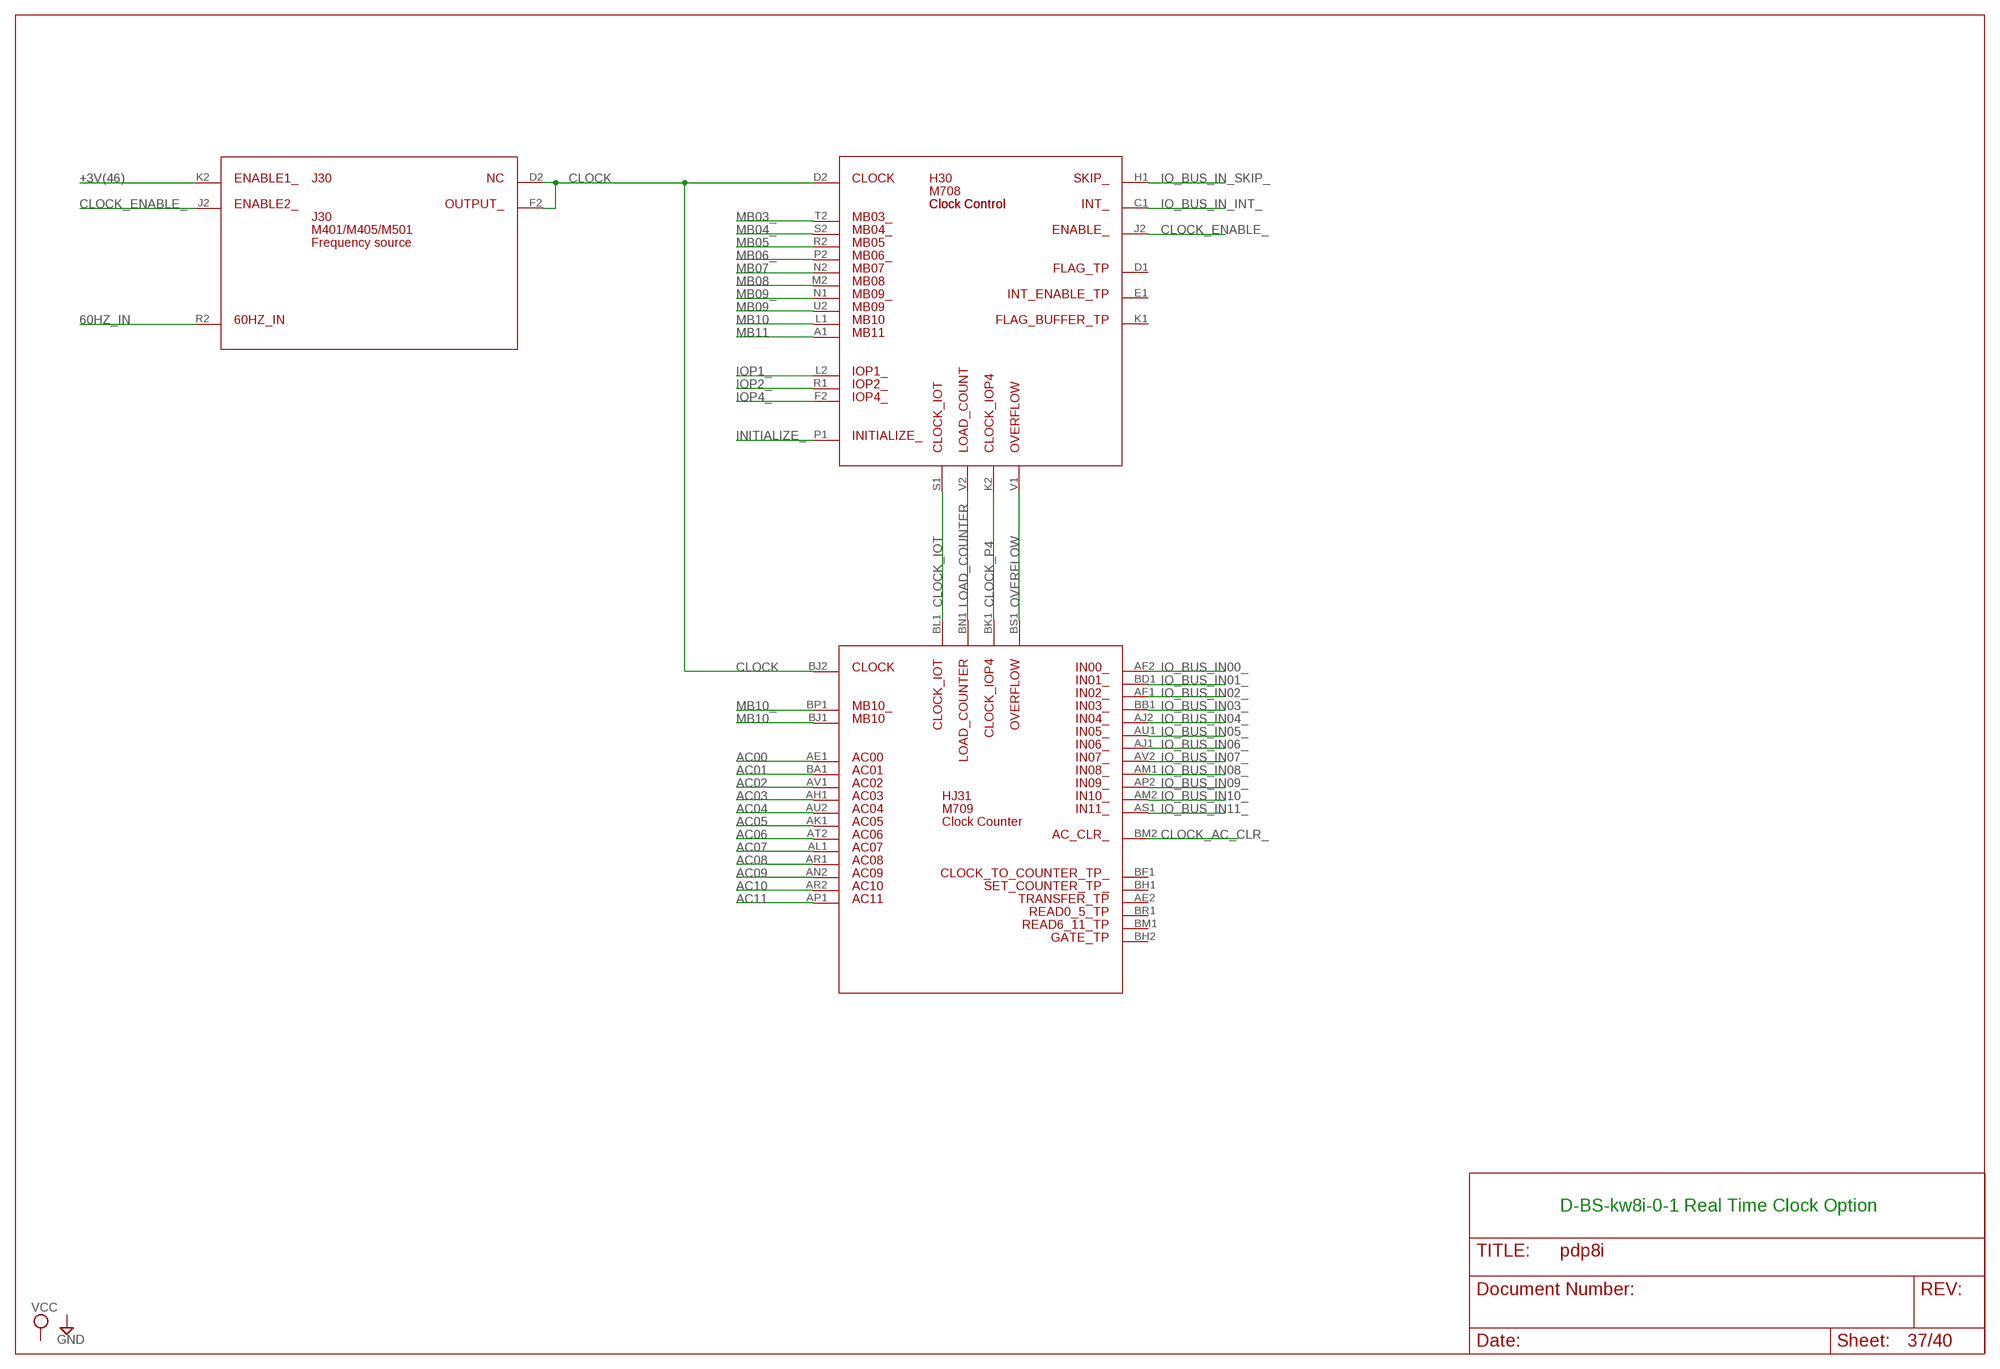
[diagram p37: schematic, sheet 37]
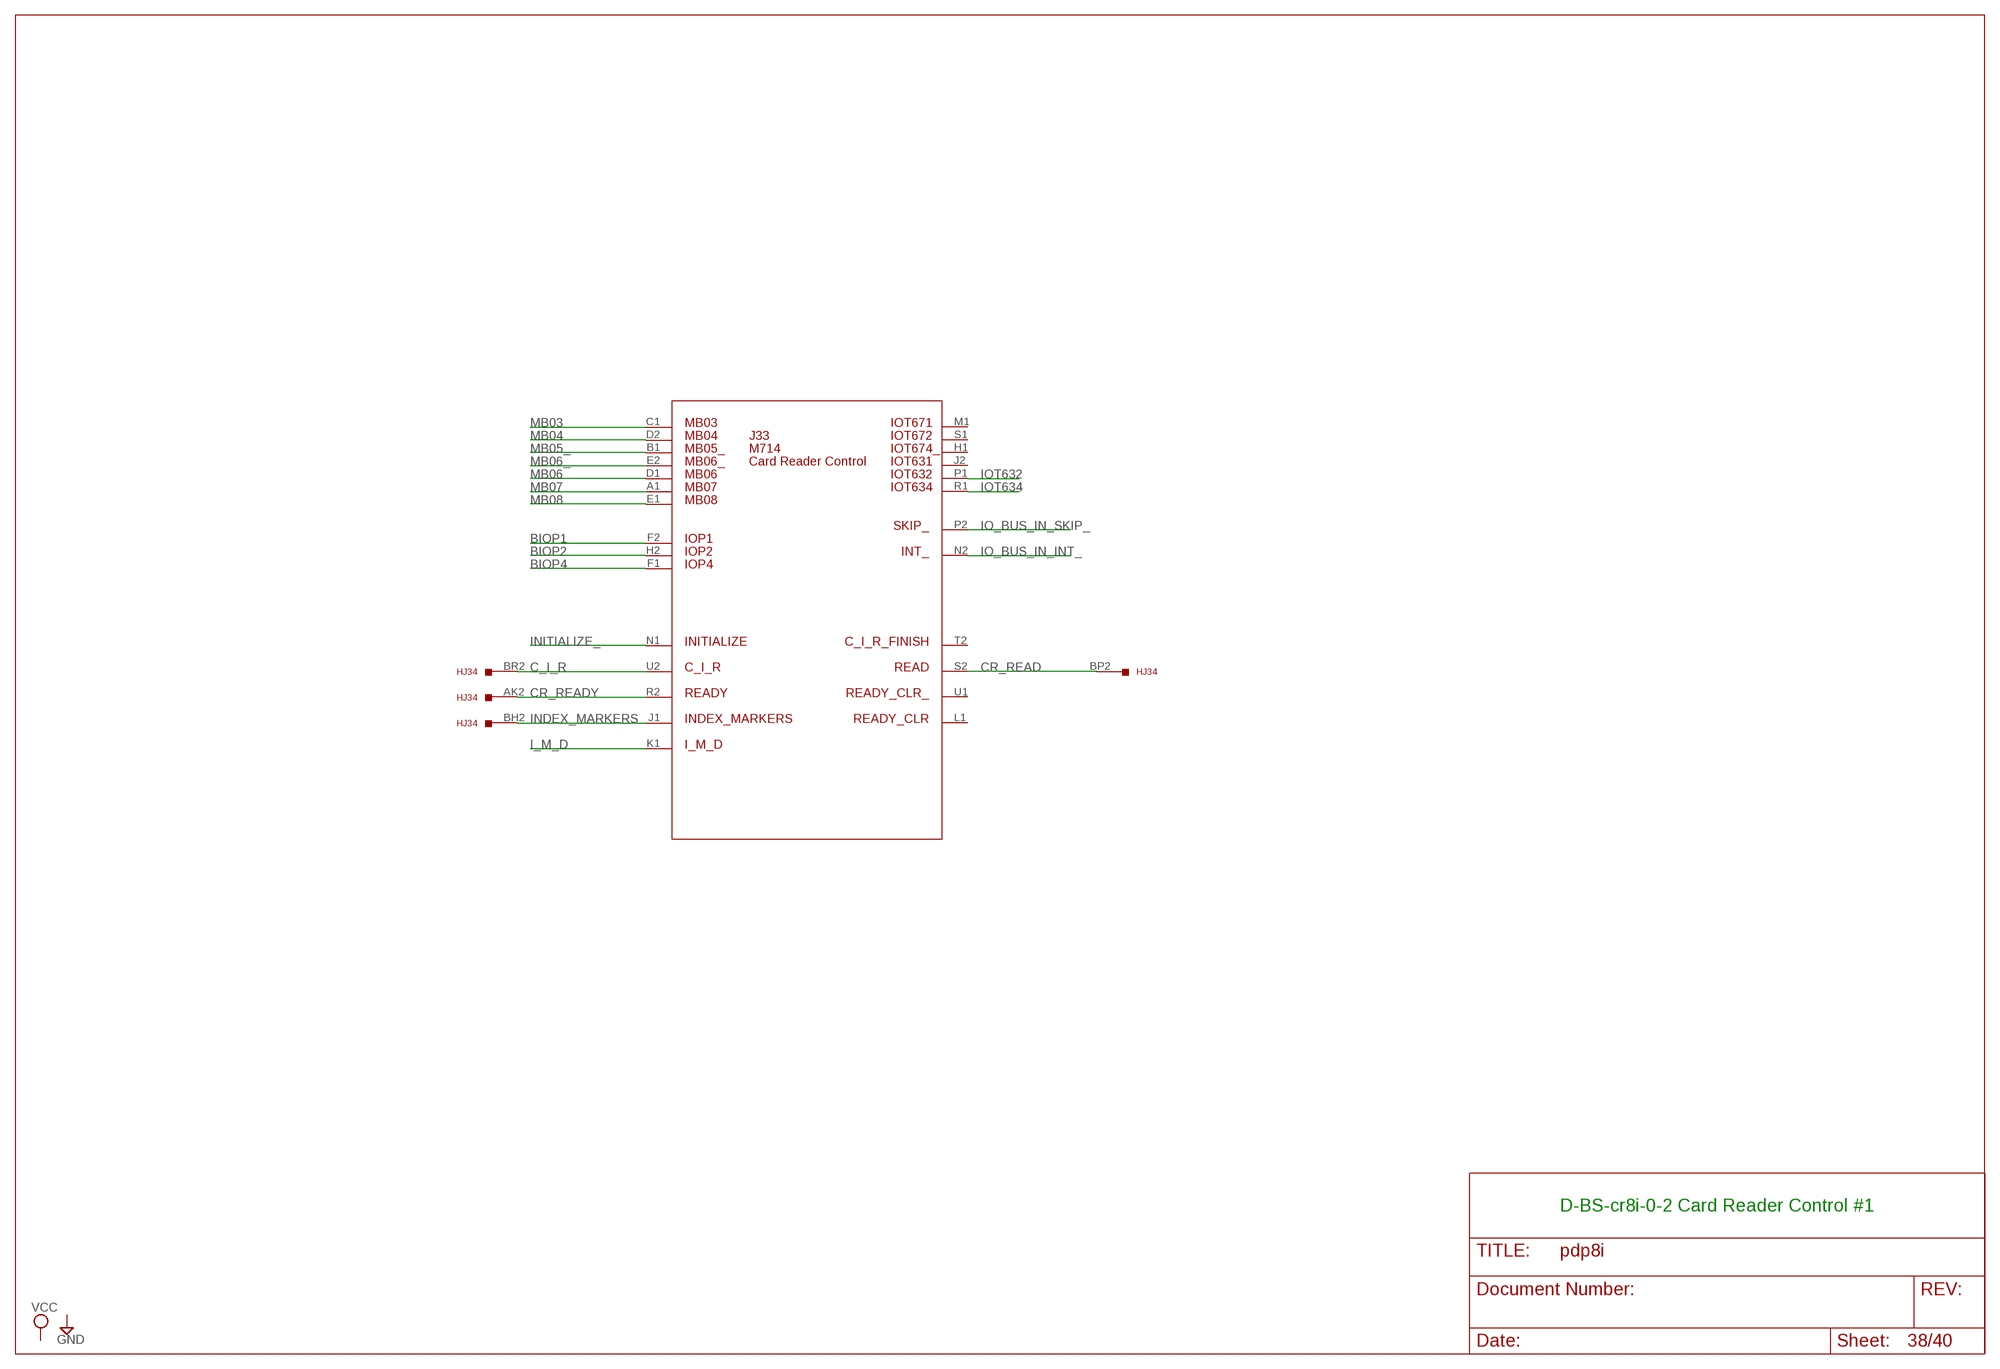
[diagram p38: schematic, sheet 38]
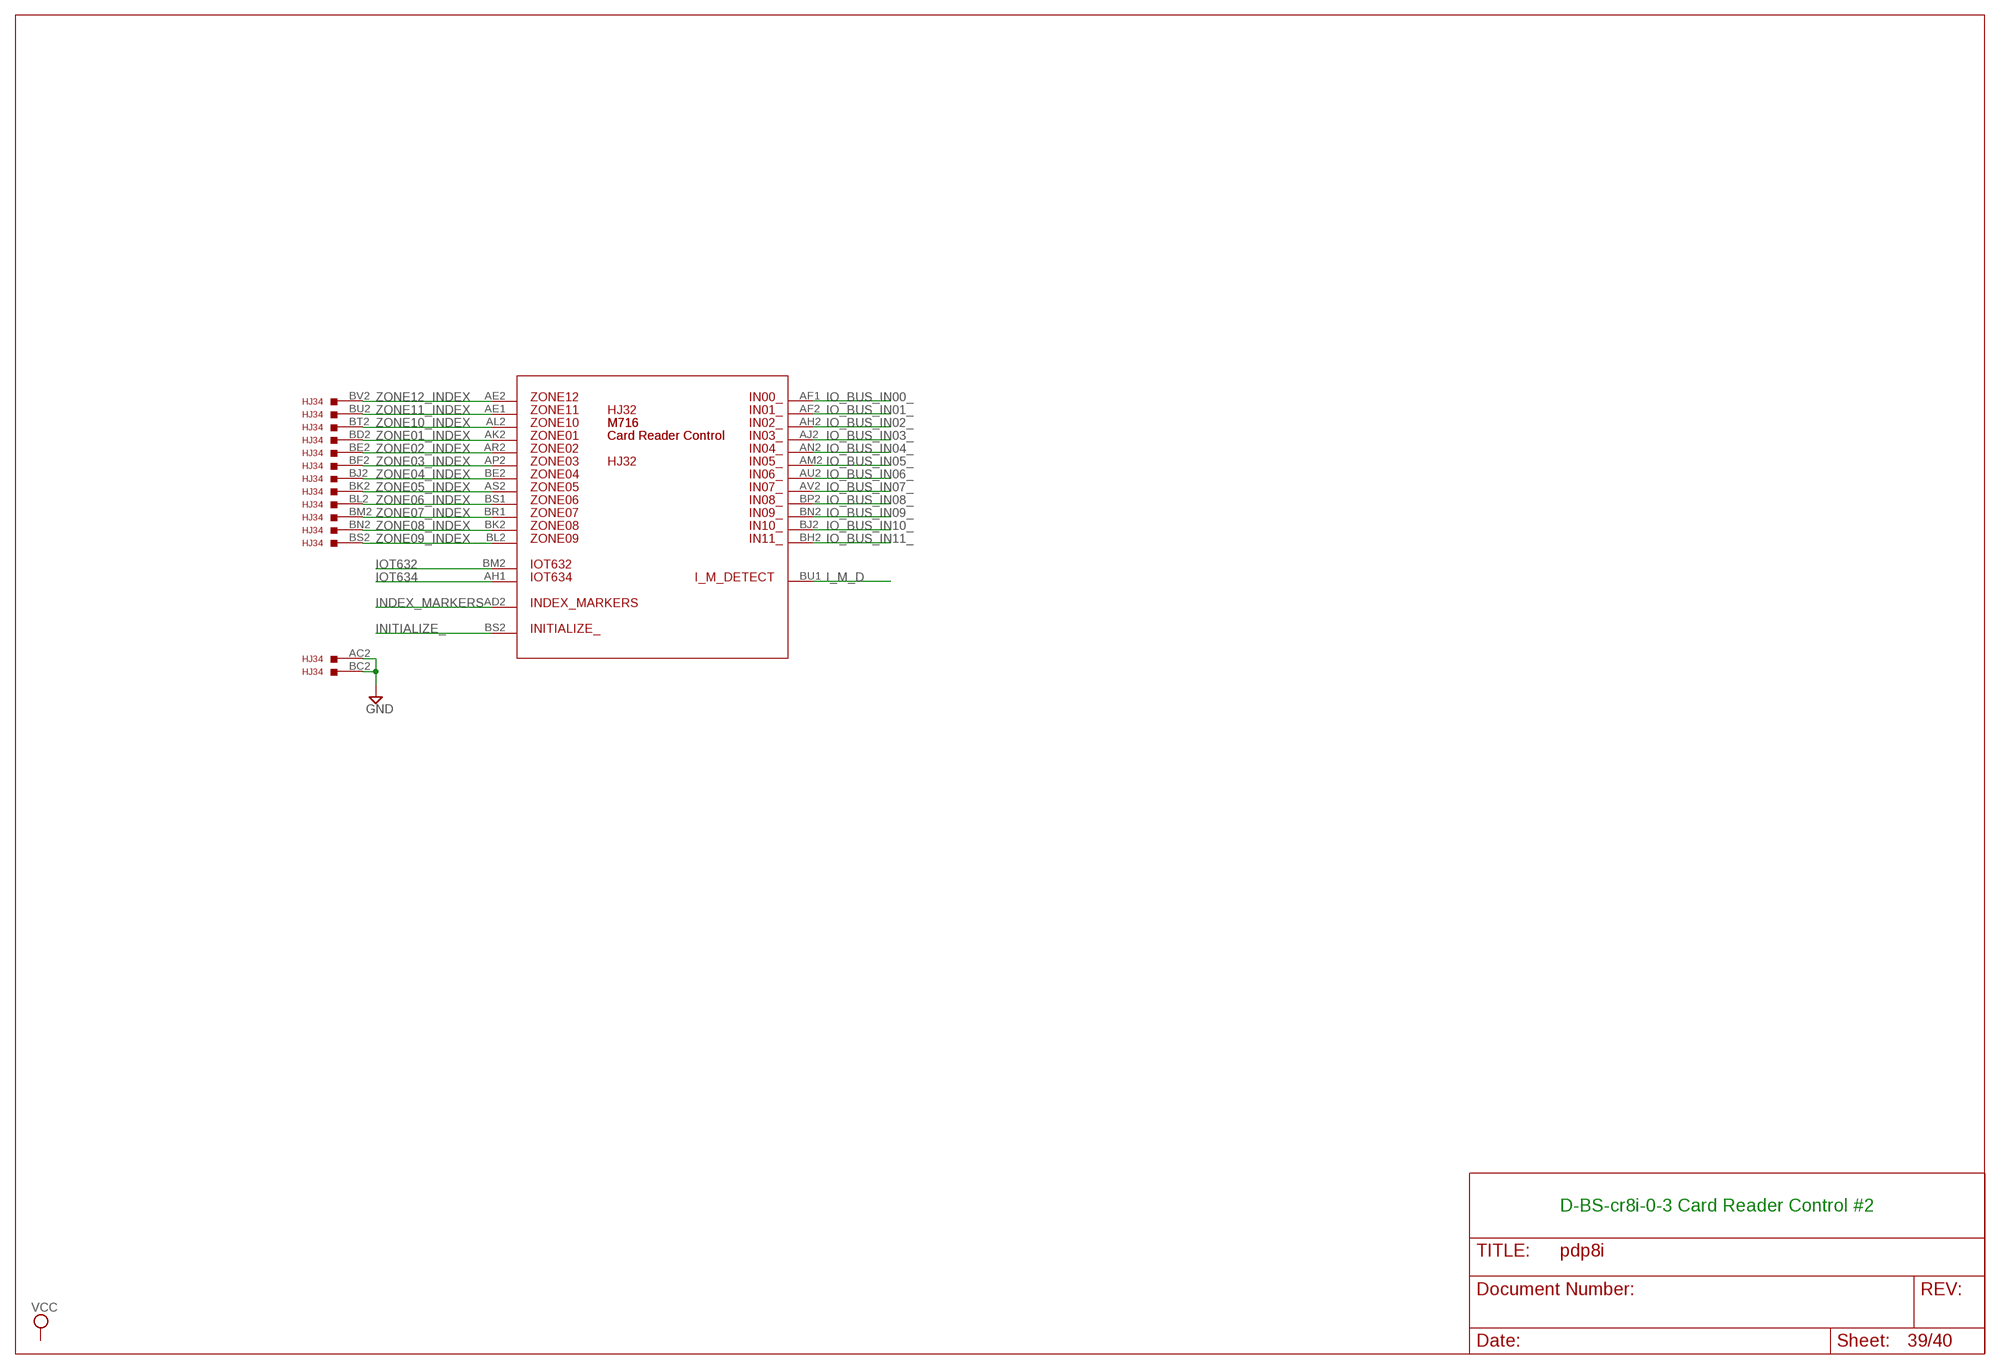
[diagram p39: schematic, sheet 39]
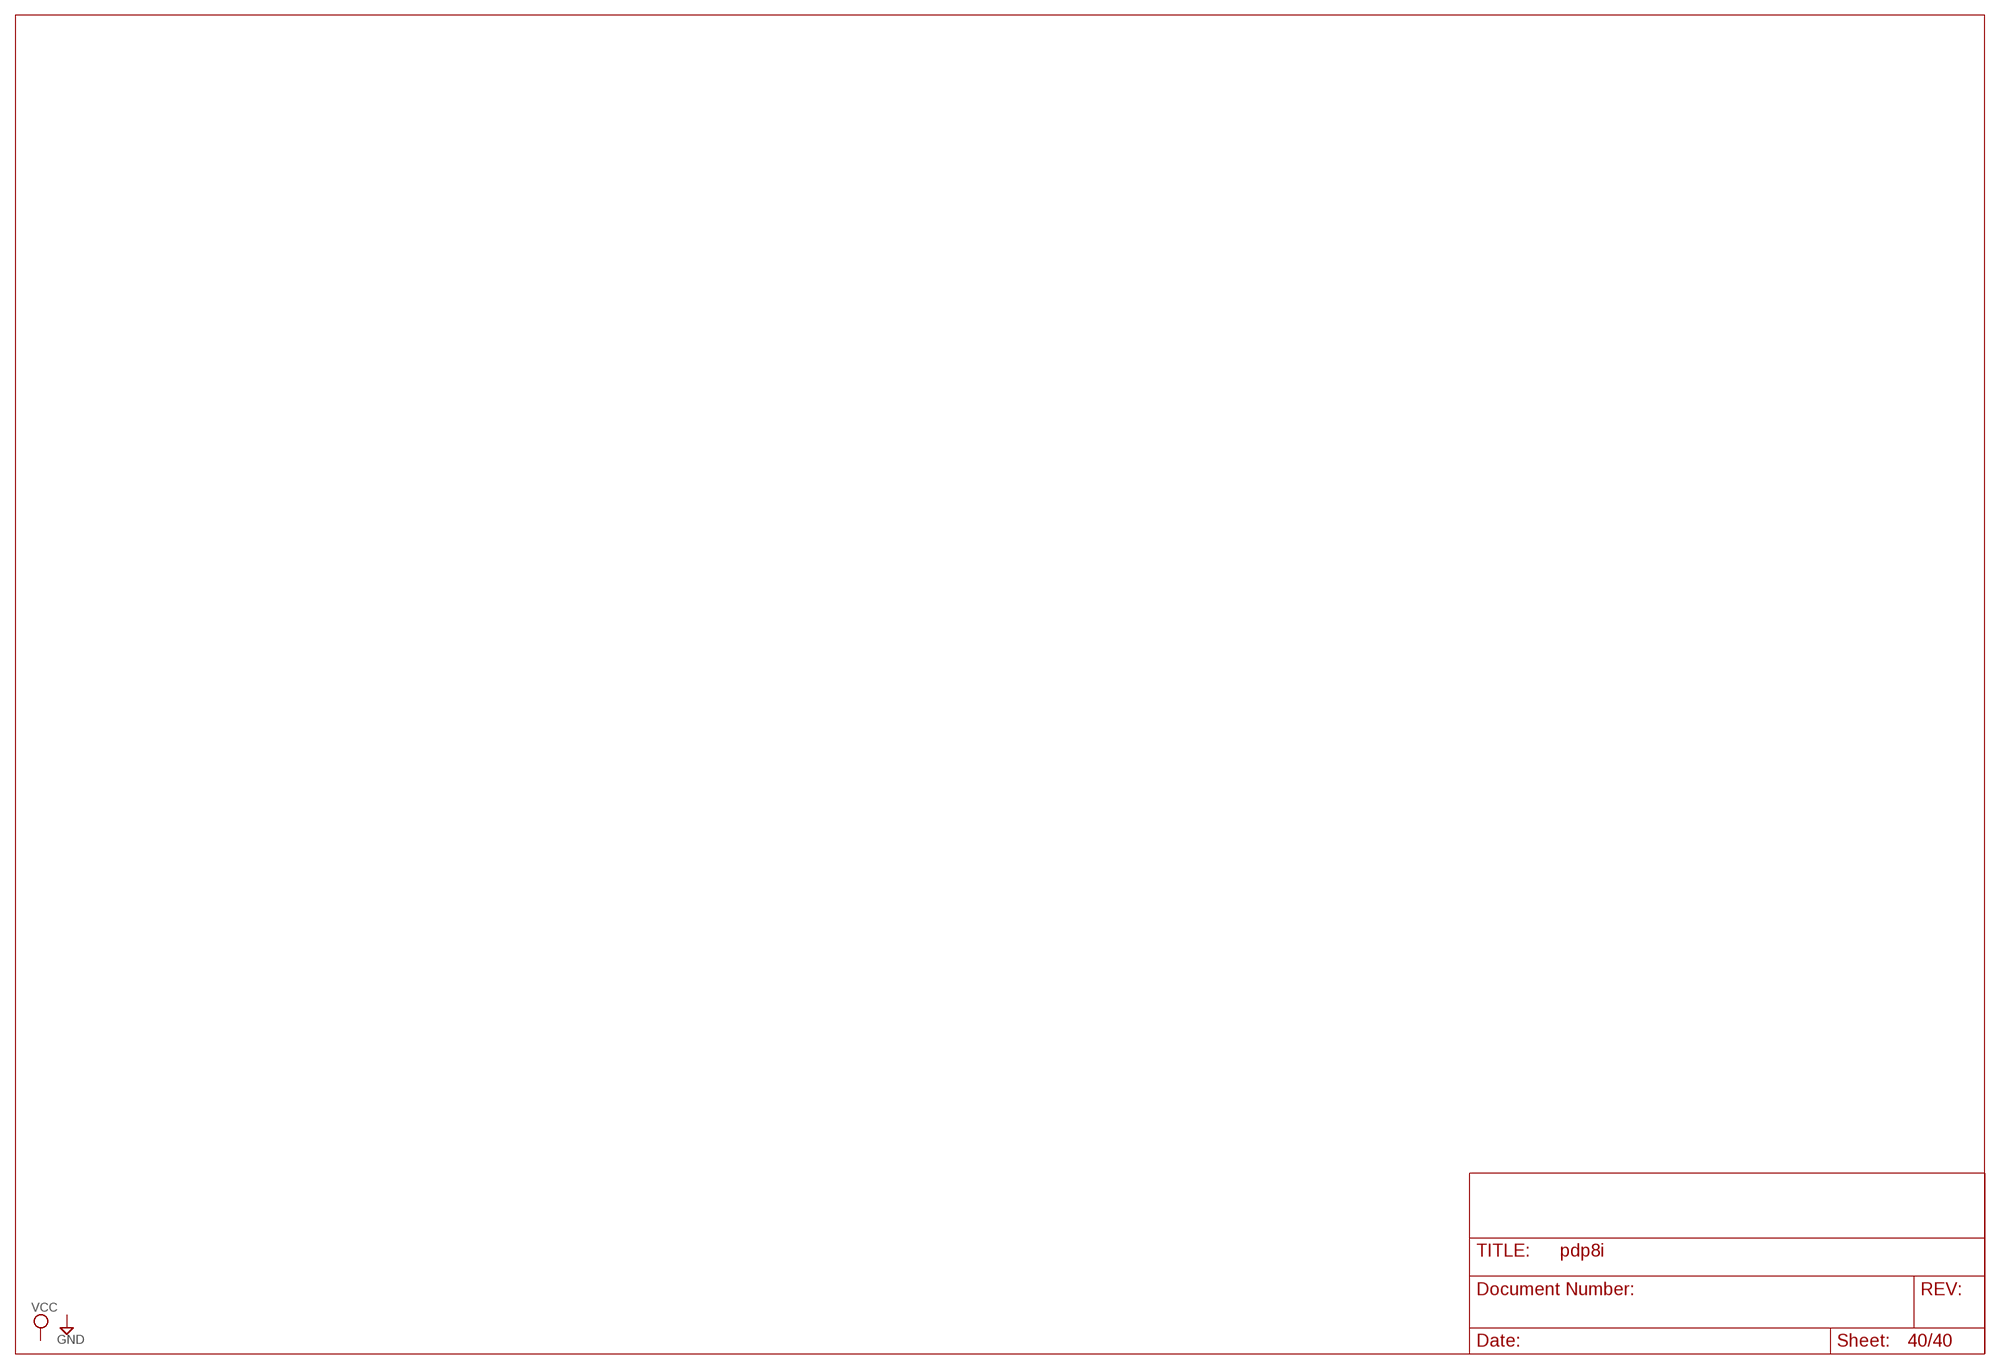
[diagram p40: schematic, sheet 40]

(export (version "E")
  (design (tool "Eeschema 10.0.6"))
  (components
    (comp (ref "E12")
      (value "M113")
      (footprint "eagle-import:H807")
      (libsource (lib "eagle-import") (part "M113"))
    )
    (comp (ref "EF02")
      (value "M707")
      (footprint "eagle-import:H807-2")
      (libsource (lib "eagle-import") (part "M707"))
    )
    (comp (ref "F03")
      (value "M452")
      (footprint "eagle-import:H807")
      (libsource (lib "eagle-import") (part "M452"))
    )
    (comp (ref "F19")
      (value "M117")
      (footprint "eagle-import:H807")
      (libsource (lib "eagle-import") (part "M117"))
    )
    (comp (ref "J12")
      (value "W076")
      (footprint "eagle-import:H807")
      (libsource (lib "eagle-import") (part "W076"))
    )
    (comp (ref "HJ32")
      (value "M716")
      (footprint "eagle-import:H807-2")
      (libsource (lib "eagle-import") (part "M716"))
    )
    (comp (ref "HJ34")
      (value "W991")
      (footprint "eagle-import:H807-2")
      (libsource (lib "eagle-import") (part "W991"))
    )
    (comp (ref "D02")
      (value "W023")
      (footprint "eagle-import:H807")
      (libsource (lib "eagle-import") (part "W023"))
    )
    (comp (ref "HJ29")
      (value "M704")
      (footprint "eagle-import:H807-2")
      (libsource (lib "eagle-import") (part "M704"))
    )
    (comp (ref "B30")
      (value "M617")
      (footprint "eagle-import:H807")
      (libsource (lib "eagle-import") (part "M617"))
    )
    (comp (ref "E03")
      (value "EMPTY")
      (footprint "eagle-import:H807")
      (libsource (lib "eagle-import") (part "EMPTY"))
    )
    (comp (ref "E04")
      (value "EMPTY")
      (footprint "eagle-import:H807")
      (libsource (lib "eagle-import") (part "EMPTY"))
    )
    (comp (ref "E05")
      (value "EMPTY")
      (footprint "eagle-import:H807")
      (libsource (lib "eagle-import") (part "EMPTY"))
    )
    (comp (ref "E06")
      (value "EMPTY")
      (footprint "eagle-import:H807")
      (libsource (lib "eagle-import") (part "EMPTY"))
    )
    (comp (ref "E07")
      (value "EMPTY")
      (footprint "eagle-import:H807")
      (libsource (lib "eagle-import") (part "EMPTY"))
    )
    (comp (ref "E08")
      (value "EMPTY")
      (footprint "eagle-import:H807")
      (libsource (lib "eagle-import") (part "EMPTY"))
    )
    (comp (ref "E31")
      (value "M617")
      (footprint "eagle-import:H807")
      (libsource (lib "eagle-import") (part "M617"))
    )
    (comp (ref "E32")
      (value "M617")
      (footprint "eagle-import:H807")
      (libsource (lib "eagle-import") (part "M617"))
    )
    (comp (ref "EF10")
      (value "M700")
      (footprint "eagle-import:H807-2")
      (libsource (lib "eagle-import") (part "M700"))
    )
    (comp (ref "F04")
      (value "EMPTY")
      (footprint "eagle-import:H807")
      (libsource (lib "eagle-import") (part "EMPTY"))
    )
    (comp (ref "F05")
      (value "EMPTY")
      (footprint "eagle-import:H807")
      (libsource (lib "eagle-import") (part "EMPTY"))
    )
    (comp (ref "F06")
      (value "EMPTY")
      (footprint "eagle-import:H807")
      (libsource (lib "eagle-import") (part "EMPTY"))
    )
    (comp (ref "F07")
      (value "EMPTY")
      (footprint "eagle-import:H807")
      (libsource (lib "eagle-import") (part "EMPTY"))
    )
    (comp (ref "F11")
      (value "M117")
      (footprint "eagle-import:H807")
      (libsource (lib "eagle-import") (part "M117"))
    )
    (comp (ref "F20")
      (value "M113")
      (footprint "eagle-import:H807")
      (libsource (lib "eagle-import") (part "M113"))
    )
    (comp (ref "F21")
      (value "M113")
      (footprint "eagle-import:H807")
      (libsource (lib "eagle-import") (part "M113"))
    )
    (comp (ref "F22")
      (value "M113")
      (footprint "eagle-import:H807")
      (libsource (lib "eagle-import") (part "M113"))
    )
    (comp (ref "F23")
      (value "M117")
      (footprint "eagle-import:H807")
      (libsource (lib "eagle-import") (part "M117"))
    )
    (comp (ref "F27")
      (value "M117")
      (footprint "eagle-import:H807")
      (libsource (lib "eagle-import") (part "M117"))
    )
    (comp (ref "F29")
      (value "M113")
      (footprint "eagle-import:H807")
      (libsource (lib "eagle-import") (part "M113"))
    )
    (comp (ref "F30")
      (value "M617")
      (footprint "eagle-import:H807")
      (libsource (lib "eagle-import") (part "M617"))
    )
    (comp (ref "F31")
      (value "M617")
      (footprint "eagle-import:H807")
      (libsource (lib "eagle-import") (part "M617"))
    )
    (comp (ref "H06")
      (value "EMPTY")
      (footprint "eagle-import:H807")
      (libsource (lib "eagle-import") (part "EMPTY"))
    )
    (comp (ref "H21")
      (value "EMPTY")
      (footprint "eagle-import:H807")
      (libsource (lib "eagle-import") (part "EMPTY"))
    )
    (comp (ref "H22")
      (value "EMPTY")
      (footprint "eagle-import:H807")
      (libsource (lib "eagle-import") (part "EMPTY"))
    )
    (comp (ref "H33")
      (value "EMPTY")
      (footprint "eagle-import:H807")
      (libsource (lib "eagle-import") (part "EMPTY"))
    )
    (comp (ref "H35")
      (value "EMPTY")
      (footprint "eagle-import:H807")
      (libsource (lib "eagle-import") (part "EMPTY"))
    )
    (comp (ref "H36")
      (value "EMPTY")
      (footprint "eagle-import:H807")
      (libsource (lib "eagle-import") (part "EMPTY"))
    )
    (comp (ref "H37")
      (value "EMPTY")
      (footprint "eagle-import:H807")
      (libsource (lib "eagle-import") (part "EMPTY"))
    )
    (comp (ref "H38")
      (value "EMPTY")
      (footprint "eagle-import:H807")
      (libsource (lib "eagle-import") (part "EMPTY"))
    )
    (comp (ref "H39")
      (value "EMPTY")
      (footprint "eagle-import:H807")
      (libsource (lib "eagle-import") (part "EMPTY"))
    )
    (comp (ref "H40")
      (value "EMPTY")
      (footprint "eagle-import:H807")
      (libsource (lib "eagle-import") (part "EMPTY"))
    )
    (comp (ref "J11")
      (value "W011")
      (footprint "eagle-import:H807")
      (libsource (lib "eagle-import") (part "W011"))
    )
    (comp (ref "J21")
      (value "EMPTY")
      (footprint "eagle-import:H807")
      (libsource (lib "eagle-import") (part "EMPTY"))
    )
    (comp (ref "J22")
      (value "EMPTY")
      (footprint "eagle-import:H807")
      (libsource (lib "eagle-import") (part "EMPTY"))
    )
    (comp (ref "J35")
      (value "EMPTY")
      (footprint "eagle-import:H807")
      (libsource (lib "eagle-import") (part "EMPTY"))
    )
    (comp (ref "J36")
      (value "EMPTY")
      (footprint "eagle-import:H807")
      (libsource (lib "eagle-import") (part "EMPTY"))
    )
    (comp (ref "J37")
      (value "EMPTY")
      (footprint "eagle-import:H807")
      (libsource (lib "eagle-import") (part "EMPTY"))
    )
    (comp (ref "J38")
      (value "EMPTY")
      (footprint "eagle-import:H807")
      (libsource (lib "eagle-import") (part "EMPTY"))
    )
    (comp (ref "J39")
      (value "EMPTY")
      (footprint "eagle-import:H807")
      (libsource (lib "eagle-import") (part "EMPTY"))
    )
    (comp (ref "J40")
      (value "EMPTY")
      (footprint "eagle-import:H807")
      (libsource (lib "eagle-import") (part "EMPTY"))
    )
    (comp (ref "A13")
      (value "M113")
      (footprint "eagle-import:H807")
      (libsource (lib "eagle-import") (part "M113"))
    )
    (comp (ref "A16")
      (value "M113")
      (footprint "eagle-import:H807")
      (libsource (lib "eagle-import") (part "M113"))
    )
    (comp (ref "A19")
      (value "M113")
      (footprint "eagle-import:H807")
      (libsource (lib "eagle-import") (part "M113"))
    )
    (comp (ref "B10")
      (value "M720")
      (footprint "eagle-import:H807")
      (libsource (lib "eagle-import") (part "M720"))
    )
    (comp (ref "B11")
      (value "M216")
      (footprint "eagle-import:H807")
      (libsource (lib "eagle-import") (part "M216"))
    )
    (comp (ref "B12")
      (value "M617")
      (footprint "eagle-import:H807")
      (libsource (lib "eagle-import") (part "M617"))
    )
    (comp (ref "B13")
      (value "M617")
      (footprint "eagle-import:H807")
      (libsource (lib "eagle-import") (part "M617"))
    )
    (comp (ref "B14")
      (value "M617")
      (footprint "eagle-import:H807")
      (libsource (lib "eagle-import") (part "M617"))
    )
    (comp (ref "B15")
      (value "M617")
      (footprint "eagle-import:H807")
      (libsource (lib "eagle-import") (part "M617"))
    )
    (comp (ref "B16")
      (value "M617")
      (footprint "eagle-import:H807")
      (libsource (lib "eagle-import") (part "M617"))
    )
    (comp (ref "B18")
      (value "M216")
      (footprint "eagle-import:H807")
      (libsource (lib "eagle-import") (part "M216"))
    )
    (comp (ref "B19")
      (value "M216")
      (footprint "eagle-import:H807")
      (libsource (lib "eagle-import") (part "M216"))
    )
    (comp (ref "B20")
      (value "M115")
      (footprint "eagle-import:H807")
      (libsource (lib "eagle-import") (part "M115"))
    )
    (comp (ref "B21")
      (value "M113")
      (footprint "eagle-import:H807")
      (libsource (lib "eagle-import") (part "M113"))
    )
    (comp (ref "H01")
      (value "W011")
      (footprint "eagle-import:H807")
      (libsource (lib "eagle-import") (part "W011"))
    )
    (comp (ref "H02")
      (value "W011")
      (footprint "eagle-import:H807")
      (libsource (lib "eagle-import") (part "W011"))
    )
    (comp (ref "H03")
      (value "W011")
      (footprint "eagle-import:H807")
      (libsource (lib "eagle-import") (part "W011"))
    )
    (comp (ref "B40")
      (value "W077")
      (footprint "eagle-import:H807")
      (libsource (lib "eagle-import") (part "M916"))
    )
    (comp (ref "C12")
      (value "M617")
      (footprint "eagle-import:H807")
      (libsource (lib "eagle-import") (part "M617"))
    )
    (comp (ref "D40")
      (value "M900")
      (footprint "eagle-import:H807")
      (libsource (lib "eagle-import") (part "M916"))
    )
    (comp (ref "E09")
      (value "M113")
      (footprint "eagle-import:H807")
      (libsource (lib "eagle-import") (part "M113"))
    )
    (comp (ref "E11")
      (value "M113")
      (footprint "eagle-import:H807")
      (libsource (lib "eagle-import") (part "M113"))
    )
    (comp (ref "E13")
      (value "M160")
      (footprint "eagle-import:H807")
      (libsource (lib "eagle-import") (part "M160"))
    )
    (comp (ref "E14")
      (value "M115")
      (footprint "eagle-import:H807")
      (libsource (lib "eagle-import") (part "M115"))
    )
    (comp (ref "E15")
      (value "M113")
      (footprint "eagle-import:H807")
      (libsource (lib "eagle-import") (part "M113"))
    )
    (comp (ref "E16")
      (value "M310")
      (footprint "eagle-import:H807")
      (libsource (lib "eagle-import") (part "M310"))
    )
    (comp (ref "E17")
      (value "M310")
      (footprint "eagle-import:H807")
      (libsource (lib "eagle-import") (part "M310"))
    )
    (comp (ref "E18")
      (value "M216")
      (footprint "eagle-import:H807")
      (libsource (lib "eagle-import") (part "M206X"))
    )
    (comp (ref "E19")
      (value "M216")
      (footprint "eagle-import:H807")
      (libsource (lib "eagle-import") (part "M206X"))
    )
    (comp (ref "E20")
      (value "M216")
      (footprint "eagle-import:H807")
      (libsource (lib "eagle-import") (part "M206X"))
    )
    (comp (ref "F08")
      (value "M660")
      (footprint "eagle-import:H807")
      (libsource (lib "eagle-import") (part "M660"))
    )
    (comp (ref "F12")
      (value "M310")
      (footprint "eagle-import:H807")
      (libsource (lib "eagle-import") (part "M310"))
    )
    (comp (ref "F13")
      (value "M310")
      (footprint "eagle-import:H807")
      (libsource (lib "eagle-import") (part "M310"))
    )
    (comp (ref "F14")
      (value "M310")
      (footprint "eagle-import:H807")
      (libsource (lib "eagle-import") (part "M310"))
    )
    (comp (ref "F15")
      (value "M310")
      (footprint "eagle-import:H807")
      (libsource (lib "eagle-import") (part "M310"))
    )
    (comp (ref "F16")
      (value "M310")
      (footprint "eagle-import:H807")
      (libsource (lib "eagle-import") (part "M310"))
    )
    (comp (ref "F17")
      (value "M310")
      (footprint "eagle-import:H807")
      (libsource (lib "eagle-import") (part "M310"))
    )
    (comp (ref "F18")
      (value "M310")
      (footprint "eagle-import:H807")
      (libsource (lib "eagle-import") (part "M310"))
    )
    (comp (ref "H05")
      (value "W011")
      (footprint "eagle-import:H807")
      (libsource (lib "eagle-import") (part "W011"))
    )
    (comp (ref "A06")
      (value "M113")
      (footprint "eagle-import:H807")
      (libsource (lib "eagle-import") (part "M113"))
    )
    (comp (ref "E21")
      (value "M115")
      (footprint "eagle-import:H807")
      (libsource (lib "eagle-import") (part "M115"))
    )
    (comp (ref "E22")
      (value "M113")
      (footprint "eagle-import:H807")
      (libsource (lib "eagle-import") (part "M113"))
    )
    (comp (ref "E23")
      (value "M216")
      (footprint "eagle-import:H807")
      (libsource (lib "eagle-import") (part "M206X"))
    )
    (comp (ref "E24")
      (value "M113")
      (footprint "eagle-import:H807")
      (libsource (lib "eagle-import") (part "M113"))
    )
    (comp (ref "E25")
      (value "M115")
      (footprint "eagle-import:H807")
      (libsource (lib "eagle-import") (part "M115"))
    )
    (comp (ref "E26")
      (value "M160")
      (footprint "eagle-import:H807")
      (libsource (lib "eagle-import") (part "M160"))
    )
    (comp (ref "E33")
      (value "M216")
      (footprint "eagle-import:H807")
      (libsource (lib "eagle-import") (part "M206X"))
    )
    (comp (ref "C14")
      (value "M113")
      (footprint "eagle-import:H807")
      (libsource (lib "eagle-import") (part "M113"))
    )
    (comp (ref "C15")
      (value "M113")
      (footprint "eagle-import:H807")
      (libsource (lib "eagle-import") (part "M113"))
    )
    (comp (ref "C16")
      (value "M113")
      (footprint "eagle-import:H807")
      (libsource (lib "eagle-import") (part "M113"))
    )
    (comp (ref "C17")
      (value "M113")
      (footprint "eagle-import:H807")
      (libsource (lib "eagle-import") (part "M113"))
    )
    (comp (ref "C18")
      (value "M113")
      (footprint "eagle-import:H807")
      (libsource (lib "eagle-import") (part "M113"))
    )
    (comp (ref "C19")
      (value "M115")
      (footprint "eagle-import:H807")
      (libsource (lib "eagle-import") (part "M115"))
    )
    (comp (ref "C20")
      (value "M115")
      (footprint "eagle-import:H807")
      (libsource (lib "eagle-import") (part "M115"))
    )
    (comp (ref "C21")
      (value "M115")
      (footprint "eagle-import:H807")
      (libsource (lib "eagle-import") (part "M115"))
    )
    (comp (ref "C22")
      (value "M216")
      (footprint "eagle-import:H807")
      (libsource (lib "eagle-import") (part "M216"))
    )
    (comp (ref "C23")
      (value "M216")
      (footprint "eagle-import:H807")
      (libsource (lib "eagle-import") (part "M216"))
    )
    (comp (ref "C24")
      (value "M216")
      (footprint "eagle-import:H807")
      (libsource (lib "eagle-import") (part "M216"))
    )
    (comp (ref "C40")
      (value "M900")
      (footprint "eagle-import:H807")
      (libsource (lib "eagle-import") (part "M916"))
    )
    (comp (ref "D12")
      (value "M113")
      (footprint "eagle-import:H807")
      (libsource (lib "eagle-import") (part "M113"))
    )
    (comp (ref "D19")
      (value "M115")
      (footprint "eagle-import:H807")
      (libsource (lib "eagle-import") (part "M115"))
    )
    (comp (ref "D22")
      (value "M617")
      (footprint "eagle-import:H807")
      (libsource (lib "eagle-import") (part "M617"))
    )
    (comp (ref "D23")
      (value "M160")
      (footprint "eagle-import:H807")
      (libsource (lib "eagle-import") (part "M160"))
    )
    (comp (ref "E40")
      (value "M900")
      (footprint "eagle-import:H807")
      (libsource (lib "eagle-import") (part "M916"))
    )
    (comp (ref "F40")
      (value "M900")
      (footprint "eagle-import:H807")
      (libsource (lib "eagle-import") (part "M916"))
    )
    (comp (ref "A07")
      (value "M162")
      (footprint "eagle-import:H807")
      (libsource (lib "eagle-import") (part "M162"))
    )
    (comp (ref "A08")
      (value "M162")
      (footprint "eagle-import:H807")
      (libsource (lib "eagle-import") (part "M162"))
    )
    (comp (ref "B08")
      (value "M113")
      (footprint "eagle-import:H807")
      (libsource (lib "eagle-import") (part "M113"))
    )
    (comp (ref "B09")
      (value "M113")
      (footprint "eagle-import:H807")
      (libsource (lib "eagle-import") (part "M113"))
    )
    (comp (ref "A25")
      (value "G624")
      (footprint "eagle-import:H807")
      (libsource (lib "eagle-import") (part "G624"))
    )
    (comp (ref "A26")
      (value "G624")
      (footprint "eagle-import:H807")
      (libsource (lib "eagle-import") (part "G624"))
    )
    (comp (ref "A27")
      (value "G228")
      (footprint "eagle-import:H807")
      (libsource (lib "eagle-import") (part "G228"))
    )
    (comp (ref "AB28")
      (value "W025")
      (footprint "eagle-import:H807-2")
      (libsource (lib "eagle-import") (part "W025"))
    )
    (comp (ref "B25")
      (value "G624")
      (footprint "eagle-import:H807")
      (libsource (lib "eagle-import") (part "G624"))
    )
    (comp (ref "B26")
      (value "G228")
      (footprint "eagle-import:H807")
      (libsource (lib "eagle-import") (part "G228"))
    )
    (comp (ref "B27")
      (value "G228")
      (footprint "eagle-import:H807")
      (libsource (lib "eagle-import") (part "G228"))
    )
    (comp (ref "C32")
      (value "G221")
      (footprint "eagle-import:H807")
      (libsource (lib "eagle-import") (part "G221"))
    )
    (comp (ref "C33")
      (value "G221")
      (footprint "eagle-import:H807")
      (libsource (lib "eagle-import") (part "G221"))
    )
    (comp (ref "CD34")
      (value "G610")
      (footprint "eagle-import:H807-2")
      (libsource (lib "eagle-import") (part "G610"))
    )
    (comp (ref "CD36")
      (value "G611")
      (footprint "eagle-import:H807-2")
      (libsource (lib "eagle-import") (part "G610"))
    )
    (comp (ref "D37")
      (value "G221")
      (footprint "eagle-import:H807")
      (libsource (lib "eagle-import") (part "G221"))
    )
    (comp (ref "D38")
      (value "G221")
      (footprint "eagle-import:H807")
      (libsource (lib "eagle-import") (part "G221"))
    )
    (comp (ref "A04")
      (value "M703")
      (footprint "eagle-import:H807")
      (libsource (lib "eagle-import") (part "M703"))
    )
    (comp (ref "H07")
      (value "M650")
      (footprint "eagle-import:H807")
      (libsource (lib "eagle-import") (part "M650"))
    )
    (comp (ref "H08")
      (value "M650")
      (footprint "eagle-import:H807")
      (libsource (lib "eagle-import") (part "M650"))
    )
    (comp (ref "H09")
      (value "M650")
      (footprint "eagle-import:H807")
      (libsource (lib "eagle-import") (part "M650"))
    )
    (comp (ref "H10")
      (value "M650")
      (footprint "eagle-import:H807")
      (libsource (lib "eagle-import") (part "M650"))
    )
    (comp (ref "H11")
      (value "M650")
      (footprint "eagle-import:H807")
      (libsource (lib "eagle-import") (part "M650"))
    )
    (comp (ref "H12")
      (value "M650")
      (footprint "eagle-import:H807")
      (libsource (lib "eagle-import") (part "M650"))
    )
    (comp (ref "H13")
      (value "M650")
      (footprint "eagle-import:H807")
      (libsource (lib "eagle-import") (part "M650"))
    )
    (comp (ref "H14")
      (value "M650")
      (footprint "eagle-import:H807")
      (libsource (lib "eagle-import") (part "M650"))
    )
    (comp (ref "H15")
      (value "M650")
      (footprint "eagle-import:H807")
      (libsource (lib "eagle-import") (part "M650"))
    )
    (comp (ref "H16")
      (value "M650")
      (footprint "eagle-import:H807")
      (libsource (lib "eagle-import") (part "M650"))
    )
    (comp (ref "H17")
      (value "M650")
      (footprint "eagle-import:H807")
      (libsource (lib "eagle-import") (part "M650"))
    )
    (comp (ref "H18")
      (value "M650")
      (footprint "eagle-import:H807")
      (libsource (lib "eagle-import") (part "M650"))
    )
    (comp (ref "H19")
      (value "M650")
      (footprint "eagle-import:H807")
      (libsource (lib "eagle-import") (part "M650"))
    )
    (comp (ref "H20")
      (value "M650")
      (footprint "eagle-import:H807")
      (libsource (lib "eagle-import") (part "M650"))
    )
    (comp (ref "J01")
      (value "W011")
      (footprint "eagle-import:H807")
      (libsource (lib "eagle-import") (part "W011"))
    )
    (comp (ref "J02")
      (value "W011")
      (footprint "eagle-import:H807")
      (libsource (lib "eagle-import") (part "W011"))
    )
    (comp (ref "J03")
      (value "W011")
      (footprint "eagle-import:H807")
      (libsource (lib "eagle-import") (part "W011"))
    )
    (comp (ref "J04")
      (value "W011")
      (footprint "eagle-import:H807")
      (libsource (lib "eagle-import") (part "W011"))
    )
    (comp (ref "J05")
      (value "W011")
      (footprint "eagle-import:H807")
      (libsource (lib "eagle-import") (part "W011"))
    )
    (comp (ref "J06")
      (value "W011")
      (footprint "eagle-import:H807")
      (libsource (lib "eagle-import") (part "W011"))
    )
    (comp (ref "J07")
      (value "W011")
      (footprint "eagle-import:H807")
      (libsource (lib "eagle-import") (part "W011"))
    )
    (comp (ref "J08")
      (value "W011")
      (footprint "eagle-import:H807")
      (libsource (lib "eagle-import") (part "W011"))
    )
    (comp (ref "J09")
      (value "W011")
      (footprint "eagle-import:H807")
      (libsource (lib "eagle-import") (part "W011"))
    )
    (comp (ref "J10")
      (value "W011")
      (footprint "eagle-import:H807")
      (libsource (lib "eagle-import") (part "W011"))
    )
    (comp (ref "J13")
      (value "M506")
      (footprint "eagle-import:H807")
      (libsource (lib "eagle-import") (part "M506"))
    )
    (comp (ref "J14")
      (value "M506")
      (footprint "eagle-import:H807")
      (libsource (lib "eagle-import") (part "M506"))
    )
    (comp (ref "J15")
      (value "M506")
      (footprint "eagle-import:H807")
      (libsource (lib "eagle-import") (part "M506"))
    )
    (comp (ref "J16")
      (value "M506")
      (footprint "eagle-import:H807")
      (libsource (lib "eagle-import") (part "M506"))
    )
    (comp (ref "J17")
      (value "M506")
      (footprint "eagle-import:H807")
      (libsource (lib "eagle-import") (part "M506"))
    )
    (comp (ref "J18")
      (value "M506")
      (footprint "eagle-import:H807")
      (libsource (lib "eagle-import") (part "M506"))
    )
    (comp (ref "J19")
      (value "M506")
      (footprint "eagle-import:H807")
      (libsource (lib "eagle-import") (part "M506"))
    )
    (comp (ref "J20")
      (value "M506")
      (footprint "eagle-import:H807")
      (libsource (lib "eagle-import") (part "M506"))
    )
    (comp (ref "C25")
      (value "G221")
      (footprint "eagle-import:H807")
      (libsource (lib "eagle-import") (part "G221"))
    )
    (comp (ref "C26")
      (value "G221")
      (footprint "eagle-import:H807")
      (libsource (lib "eagle-import") (part "G221"))
    )
    (comp (ref "CD27")
      (value "G610")
      (footprint "eagle-import:H807-2")
      (libsource (lib "eagle-import") (part "G610"))
    )
    (comp (ref "CD29")
      (value "G611")
      (footprint "eagle-import:H807-2")
      (libsource (lib "eagle-import") (part "G610"))
    )
    (comp (ref "D30")
      (value "G221")
      (footprint "eagle-import:H807")
      (libsource (lib "eagle-import") (part "G221"))
    )
    (comp (ref "D31")
      (value "G221")
      (footprint "eagle-import:H807")
      (libsource (lib "eagle-import") (part "G221"))
    )
    (comp (ref "E28")
      (value "M160")
      (footprint "eagle-import:H807")
      (libsource (lib "eagle-import") (part "M160"))
    )
    (comp (ref "E29")
      (value "M160")
      (footprint "eagle-import:H807")
      (libsource (lib "eagle-import") (part "M160"))
    )
    (comp (ref "E30")
      (value "M160")
      (footprint "eagle-import:H807")
      (libsource (lib "eagle-import") (part "M160"))
    )
    (comp (ref "F09")
      (value "M119")
      (footprint "eagle-import:H807")
      (libsource (lib "eagle-import") (part "M119"))
    )
    (comp (ref "F28")
      (value "M115")
      (footprint "eagle-import:H807")
      (libsource (lib "eagle-import") (part "M115"))
    )
    (comp (ref "F32")
      (value "M113")
      (footprint "eagle-import:H807")
      (libsource (lib "eagle-import") (part "M113"))
    )
    (comp (ref "F24")
      (value "M117")
      (footprint "eagle-import:H807")
      (libsource (lib "eagle-import") (part "M117"))
    )
    (comp (ref "F25")
      (value "M113")
      (footprint "eagle-import:H807")
      (libsource (lib "eagle-import") (part "M113"))
    )
    (comp (ref "F26")
      (value "M115")
      (footprint "eagle-import:H807")
      (libsource (lib "eagle-import") (part "M115"))
    )
    (comp (ref "C07")
      (value "M661")
      (footprint "eagle-import:H807")
      (libsource (lib "eagle-import") (part "M661"))
    )
    (comp (ref "C08")
      (value "M660")
      (footprint "eagle-import:H807")
      (libsource (lib "eagle-import") (part "M660"))
    )
    (comp (ref "C09")
      (value "M113")
      (footprint "eagle-import:H807")
      (libsource (lib "eagle-import") (part "M113"))
    )
    (comp (ref "C10")
      (value "M113")
      (footprint "eagle-import:H807")
      (libsource (lib "eagle-import") (part "M113"))
    )
    (comp (ref "C11")
      (value "M115")
      (footprint "eagle-import:H807")
      (libsource (lib "eagle-import") (part "M115"))
    )
    (comp (ref "D04")
      (value "W011")
      (footprint "eagle-import:H807")
      (libsource (lib "eagle-import") (part "W011"))
    )
    (comp (ref "D05")
      (value "M516")
      (footprint "eagle-import:H807")
      (libsource (lib "eagle-import") (part "M516"))
    )
    (comp (ref "D07")
      (value "M113")
      (footprint "eagle-import:H807")
      (libsource (lib "eagle-import") (part "M113"))
    )
    (comp (ref "D09")
      (value "M115")
      (footprint "eagle-import:H807")
      (libsource (lib "eagle-import") (part "M115"))
    )
    (comp (ref "D10")
      (value "M117")
      (footprint "eagle-import:H807")
      (libsource (lib "eagle-import") (part "M117"))
    )
    (comp (ref "D11")
      (value "M216")
      (footprint "eagle-import:H807")
      (libsource (lib "eagle-import") (part "M216"))
    )
    (comp (ref "C13")
      (value "M310")
      (footprint "eagle-import:H807")
      (libsource (lib "eagle-import") (part "M310"))
    )
    (comp (ref "D13")
      (value "M113")
      (footprint "eagle-import:H807")
      (libsource (lib "eagle-import") (part "M113"))
    )
    (comp (ref "D14")
      (value "M113")
      (footprint "eagle-import:H807")
      (libsource (lib "eagle-import") (part "M113"))
    )
    (comp (ref "D15")
      (value "M113")
      (footprint "eagle-import:H807")
      (libsource (lib "eagle-import") (part "M113"))
    )
    (comp (ref "D16")
      (value "M113")
      (footprint "eagle-import:H807")
      (libsource (lib "eagle-import") (part "M113"))
    )
    (comp (ref "D17")
      (value "M115")
      (footprint "eagle-import:H807")
      (libsource (lib "eagle-import") (part "M115"))
    )
    (comp (ref "D18")
      (value "M115")
      (footprint "eagle-import:H807")
      (libsource (lib "eagle-import") (part "M115"))
    )
    (comp (ref "D20")
      (value "M117")
      (footprint "eagle-import:H807")
      (libsource (lib "eagle-import") (part "M117"))
    )
    (comp (ref "D21")
      (value "M117")
      (footprint "eagle-import:H807")
      (libsource (lib "eagle-import") (part "M117"))
    )
    (comp (ref "D24")
      (value "M216")
      (footprint "eagle-import:H807")
      (libsource (lib "eagle-import") (part "M216"))
    )
    (comp (ref "A40")
      (value "W077")
      (footprint "eagle-import:H807")
      (libsource (lib "eagle-import") (part "M916"))
    )
    (comp (ref "EF35")
      (value "M220")
      (footprint "eagle-import:H807-2")
      (libsource (lib "eagle-import") (part "M220"))
    )
    (comp (ref "EF36")
      (value "M220")
      (footprint "eagle-import:H807-2")
      (libsource (lib "eagle-import") (part "M220"))
    )
    (comp (ref "EF38")
      (value "M220")
      (footprint "eagle-import:H807-2")
      (libsource (lib "eagle-import") (part "M220"))
    )
    (comp (ref "EF39")
      (value "M220")
      (footprint "eagle-import:H807-2")
      (libsource (lib "eagle-import") (part "M220"))
    )
    (comp (ref "D06")
      (value "M310")
      (footprint "eagle-import:H807")
      (libsource (lib "eagle-import") (part "M310"))
    )
    (comp (ref "C01")
      (value "W023")
      (footprint "eagle-import:H807")
      (libsource (lib "eagle-import") (part "W023"))
    )
    (comp (ref "C02")
      (value "M040")
      (footprint "eagle-import:H807")
      (libsource (lib "eagle-import") (part "M040"))
    )
    (comp (ref "C03")
      (value "M040")
      (footprint "eagle-import:H807")
      (libsource (lib "eagle-import") (part "M040"))
    )
    (comp (ref "C04")
      (value "M040")
      (footprint "eagle-import:H807")
      (libsource (lib "eagle-import") (part "M040"))
    )
    (comp (ref "C05")
      (value "M040")
      (footprint "eagle-import:H807")
      (libsource (lib "eagle-import") (part "M040"))
    )
    (comp (ref "C06")
      (value "M040")
      (footprint "eagle-import:H807")
      (libsource (lib "eagle-import") (part "M040"))
    )
    (comp (ref "HJ28")
      (value "M710")
      (footprint "eagle-import:H807-2")
      (libsource (lib "eagle-import") (part "M710"))
    )
    (comp (ref "H30")
      (value "M708")
      (footprint "eagle-import:H807")
      (libsource (lib "eagle-import") (part "M708"))
    )
    (comp (ref "HJ31")
      (value "M709")
      (footprint "eagle-import:H807-2")
      (libsource (lib "eagle-import") (part "M709"))
    )
    (comp (ref "J30")
      (value "M401/M405/M501")
      (footprint "eagle-import:H807")
      (libsource (lib "eagle-import") (part "M501"))
    )
    (comp (ref "EF34")
      (value "M220")
      (footprint "eagle-import:H807-2")
      (libsource (lib "eagle-import") (part "M220"))
    )
    (comp (ref "A21")
      (value "M310")
      (footprint "eagle-import:H807")
      (libsource (lib "eagle-import") (part "M310"))
    )
    (comp (ref "A22")
      (value "M310")
      (footprint "eagle-import:H807")
      (libsource (lib "eagle-import") (part "M310"))
    )
    (comp (ref "A23")
      (value "M310")
      (footprint "eagle-import:H807")
      (libsource (lib "eagle-import") (part "M310"))
    )
    (comp (ref "A24")
      (value "M310")
      (footprint "eagle-import:H807")
      (libsource (lib "eagle-import") (part "M310"))
    )
    (comp (ref "A38")
      (value "G624")
      (footprint "eagle-import:H807")
      (libsource (lib "eagle-import") (part "G624"))
    )
    (comp (ref "A39")
      (value "G624")
      (footprint "eagle-import:H807")
      (libsource (lib "eagle-import") (part "G624"))
    )
    (comp (ref "AB01")
      (value "G805")
      (footprint "eagle-import:H807-2")
      (libsource (lib "eagle-import") (part "G805"))
    )
    (comp (ref "AB02")
      (value "G826")
      (footprint "eagle-import:H807-2")
      (libsource (lib "eagle-import") (part "G826"))
    )
    (comp (ref "AB03")
      (value "G792")
      (footprint "eagle-import:H807-2")
      (libsource (lib "eagle-import") (part "G792"))
    )
    (comp (ref "AB35")
      (value "W025")
      (footprint "eagle-import:H807-2")
      (libsource (lib "eagle-import") (part "W025"))
    )
    (comp (ref "B22")
      (value "M216")
      (footprint "eagle-import:H807")
      (libsource (lib "eagle-import") (part "M206X"))
    )
    (comp (ref "B23")
      (value "M360")
      (footprint "eagle-import:H807")
      (libsource (lib "eagle-import") (part "M360"))
    )
    (comp (ref "B24")
      (value "M360")
      (footprint "eagle-import:H807")
      (libsource (lib "eagle-import") (part "M360"))
    )
    (comp (ref "B38")
      (value "G624")
      (footprint "eagle-import:H807")
      (libsource (lib "eagle-import") (part "G624"))
    )
    (comp (ref "B39")
      (value "G624")
      (footprint "eagle-import:H807")
      (libsource (lib "eagle-import") (part "G624"))
    )
    (comp (ref "C39")
      (value "G228")
      (footprint "eagle-import:H807")
      (libsource (lib "eagle-import") (part "G228"))
    )
    (comp (ref "D08")
      (value "M310")
      (footprint "eagle-import:H807")
      (libsource (lib "eagle-import") (part "M310"))
    )
    (comp (ref "D39")
      (value "G228")
      (footprint "eagle-import:H807")
      (libsource (lib "eagle-import") (part "G228"))
    )
    (comp (ref "D03")
      (value "W023")
      (footprint "eagle-import:H807")
      (libsource (lib "eagle-import") (part "W023"))
    )
    (comp (ref "HJ23")
      (value "M701")
      (footprint "eagle-import:H807-2")
      (libsource (lib "eagle-import") (part "M701"))
    )
    (comp (ref "HJ24")
      (value "A607")
      (footprint "eagle-import:H807-2")
      (libsource (lib "eagle-import") (part "A607"))
    )
    (comp (ref "HJ25")
      (value "A607")
      (footprint "eagle-import:H807-2")
      (libsource (lib "eagle-import") (part "A607"))
    )
    (comp (ref "E27")
      (value "M160")
      (footprint "eagle-import:H807")
      (libsource (lib "eagle-import") (part "M160"))
    )
    (comp (ref "EF01")
      (value "M706")
      (footprint "eagle-import:H807-2")
      (libsource (lib "eagle-import") (part "M706"))
    )
    (comp (ref "J33")
      (value "M714")
      (footprint "eagle-import:H807")
      (libsource (lib "eagle-import") (part "M714"))
    )
    (comp (ref "EF37")
      (value "M220")
      (footprint "eagle-import:H807-2")
      (libsource (lib "eagle-import") (part "M220"))
    )
    (comp (ref "F33")
      (value "M160")
      (footprint "eagle-import:H807")
      (libsource (lib "eagle-import") (part "M160"))
    )
    (comp (ref "A09")
      (value "M162")
      (footprint "eagle-import:H807")
      (libsource (lib "eagle-import") (part "M162"))
    )
    (comp (ref "A10")
      (value "M162")
      (footprint "eagle-import:H807")
      (libsource (lib "eagle-import") (part "M162"))
    )
    (comp (ref "B07")
      (value "M115")
      (footprint "eagle-import:H807")
      (libsource (lib "eagle-import") (part "M115"))
    )
    (comp (ref "C35")
      (value "H807")
      (footprint "eagle-import:H807")
      (libsource (lib "eagle-import") (part "H807"))
    )
    (comp (ref "C37")
      (value "G221")
      (footprint "eagle-import:H807")
      (libsource (lib "eagle-import") (part "G221"))
    )
    (comp (ref "C38")
      (value "G221")
      (footprint "eagle-import:H807")
      (libsource (lib "eagle-import") (part "G221"))
    )
    (comp (ref "D32")
      (value "G221")
      (footprint "eagle-import:H807")
      (libsource (lib "eagle-import") (part "G221"))
    )
    (comp (ref "D33")
      (value "G221")
      (footprint "eagle-import:H807")
      (libsource (lib "eagle-import") (part "G221"))
    )
    (comp (ref "D35")
      (value "H807")
      (footprint "eagle-import:H807")
      (libsource (lib "eagle-import") (part "H807"))
    )
    (comp (ref "D01")
      (value "W077")
      (footprint "eagle-import:H807")
      (libsource (lib "eagle-import") (part "W023"))
    )
    (comp (ref "HJ26")
      (value "M705")
      (footprint "eagle-import:H807-2")
      (libsource (lib "eagle-import") (part "M705"))
    )
    (comp (ref "HJ27")
      (value "M715")
      (footprint "eagle-import:H807-2")
      (libsource (lib "eagle-import") (part "M715"))
    )
    (comp (ref "A11")
      (value "M113")
      (footprint "eagle-import:H807")
      (libsource (lib "eagle-import") (part "M113"))
    )
    (comp (ref "A12")
      (value "M113")
      (footprint "eagle-import:H807")
      (libsource (lib "eagle-import") (part "M113"))
    )
    (comp (ref "A14")
      (value "M113")
      (footprint "eagle-import:H807")
      (libsource (lib "eagle-import") (part "M113"))
    )
    (comp (ref "A15")
      (value "M113")
      (footprint "eagle-import:H807")
      (libsource (lib "eagle-import") (part "M113"))
    )
    (comp (ref "A17")
      (value "M113")
      (footprint "eagle-import:H807")
      (libsource (lib "eagle-import") (part "M113"))
    )
    (comp (ref "A18")
      (value "M113")
      (footprint "eagle-import:H807")
      (libsource (lib "eagle-import") (part "M113"))
    )
    (comp (ref "A20")
      (value "M115")
      (footprint "eagle-import:H807")
      (libsource (lib "eagle-import") (part "M115"))
    )
    (comp (ref "B17")
      (value "M216")
      (footprint "eagle-import:H807")
      (libsource (lib "eagle-import") (part "M216"))
    )
    (comp (ref "A30")
      (value "G021")
      (footprint "eagle-import:H807")
      (libsource (lib "eagle-import") (part "G021"))
    )
    (comp (ref "A31")
      (value "G021")
      (footprint "eagle-import:H807")
      (libsource (lib "eagle-import") (part "G021"))
    )
    (comp (ref "A32")
      (value "G021")
      (footprint "eagle-import:H807")
      (libsource (lib "eagle-import") (part "G021"))
    )
    (comp (ref "A33")
      (value "G021")
      (footprint "eagle-import:H807")
      (libsource (lib "eagle-import") (part "G021"))
    )
    (comp (ref "A36")
      (value "G228")
      (footprint "eagle-import:H807")
      (libsource (lib "eagle-import") (part "G228"))
    )
    (comp (ref "A37")
      (value "G228")
      (footprint "eagle-import:H807")
      (libsource (lib "eagle-import") (part "G228"))
    )
    (comp (ref "AB29")
      (value "W025")
      (footprint "eagle-import:H807-2")
      (libsource (lib "eagle-import") (part "W025"))
    )
    (comp (ref "AB34")
      (value "W025")
      (footprint "eagle-import:H807-2")
      (libsource (lib "eagle-import") (part "W025"))
    )
    (comp (ref "B31")
      (value "G021")
      (footprint "eagle-import:H807")
      (libsource (lib "eagle-import") (part "G021"))
    )
    (comp (ref "B32")
      (value "G021")
      (footprint "eagle-import:H807")
      (libsource (lib "eagle-import") (part "G021"))
    )
    (comp (ref "B33")
      (value "G021")
      (footprint "eagle-import:H807")
      (libsource (lib "eagle-import") (part "G021"))
    )
    (comp (ref "B36")
      (value "G228")
      (footprint "eagle-import:H807")
      (libsource (lib "eagle-import") (part "G228"))
    )
    (comp (ref "B37")
      (value "G228")
      (footprint "eagle-import:H807")
      (libsource (lib "eagle-import") (part "G228"))
    )
    (comp (ref "H04")
      (value "W011")
      (footprint "eagle-import:H807")
      (libsource (lib "eagle-import") (part "W011"))
    )
    (comp (ref "A05")
      (value "M113")
      (footprint "eagle-import:H807")
      (libsource (lib "eagle-import") (part "M113"))
    )
    (comp (ref "B04")
      (value "M115")
      (footprint "eagle-import:H807")
      (libsource (lib "eagle-import") (part "M115"))
    )
    (comp (ref "B05")
      (value "M216")
      (footprint "eagle-import:H807")
      (libsource (lib "eagle-import") (part "M216"))
    )
    (comp (ref "B06")
      (value "M113")
      (footprint "eagle-import:H807")
      (libsource (lib "eagle-import") (part "M113"))
    )
    (comp (ref "C28")
      (value "H807")
      (footprint "eagle-import:H807")
      (libsource (lib "eagle-import") (part "H807"))
    )
    (comp (ref "C30")
      (value "G221")
      (footprint "eagle-import:H807")
      (libsource (lib "eagle-import") (part "G221"))
    )
    (comp (ref "C31")
      (value "G221")
      (footprint "eagle-import:H807")
      (libsource (lib "eagle-import") (part "G221"))
    )
    (comp (ref "D25")
      (value "G221")
      (footprint "eagle-import:H807")
      (libsource (lib "eagle-import") (part "G221"))
    )
    (comp (ref "D26")
      (value "G221")
      (footprint "eagle-import:H807")
      (libsource (lib "eagle-import") (part "G221"))
    )
    (comp (ref "D28")
      (value "H807")
      (footprint "eagle-import:H807")
      (libsource (lib "eagle-import") (part "H807"))
    )
  )
  (nets
    (net (code "1") (name "+3V(01)") (class "Default")
      (node (ref "A13") (pin "E1") (pinfunction "IN2_E1") (pintype "input"))
      (node (ref "A13") (pin "H1") (pinfunction "IN1_H1") (pintype "input"))
      (node (ref "A13") (pin "M1") (pinfunction "IN2_M1") (pintype "input"))
      (node (ref "A13") (pin "R1") (pinfunction "IN2_R1") (pintype "input"))
      (node (ref "A15") (pin "U1") (pinfunction "P$1_U1") (pintype "passive"))
    )
    (net (code "2") (name "+3V(02)") (class "Default")
      (node (ref "A13") (pin "U2") (pinfunction "IN2_U2") (pintype "input"))
      (node (ref "A14") (pin "B1") (pinfunction "IN2_B1") (pintype "input"))
      (node (ref "A14") (pin "H2") (pinfunction "IN1_H2") (pintype "input"))
      (node (ref "A14") (pin "J1") (pinfunction "IN2_J1") (pintype "input"))
      (node (ref "A14") (pin "L1") (pinfunction "IN1_L1") (pintype "input"))
      (node (ref "A15") (pin "V1") (pinfunction "P$1_V1") (pintype "passive"))
    )
    (net (code "3") (name "+3V(03)") (class "Default")
      (node (ref "A14") (pin "L2") (pinfunction "IN1_L2") (pintype "input"))
      (node (ref "A14") (pin "P1") (pinfunction "IN1_P1") (pintype "input"))
      (node (ref "A15") (pin "B1") (pinfunction "IN2_B1") (pintype "input"))
      (node (ref "A15") (pin "M2") (pinfunction "IN2_M2") (pintype "input"))
      (node (ref "A15") (pin "P1") (pinfunction "IN1_P1") (pintype "input"))
      (node (ref "A18") (pin "U1") (pinfunction "P$1_U1") (pintype "passive"))
    )
    (net (code "4") (name "+3V(04)") (class "Default")
      (node (ref "A18") (pin "V1") (pinfunction "P$1_V1") (pintype "passive"))
      (node (ref "A19") (pin "D1") (pinfunction "IN1_D1") (pintype "input"))
      (node (ref "A19") (pin "D2") (pinfunction "IN1_D2") (pintype "input"))
      (node (ref "A19") (pin "L2") (pinfunction "IN1_L2") (pintype "input"))
      (node (ref "A19") (pin "T2") (pinfunction "IN1_T2") (pintype "input"))
    )
    (net (code "5") (name "+3V(05)") (class "Default")
      (node (ref "A10") (pin "D1") (pinfunction "8B_D1") (pintype "input"))
      (node (ref "B08") (pin "B1") (pinfunction "IN2_B1") (pintype "input"))
      (node (ref "B08") (pin "E1") (pinfunction "IN2_E1") (pintype "input"))
      (node (ref "B08") (pin "E2") (pinfunction "IN2_E2") (pintype "input"))
      (node (ref "B08") (pin "J1") (pinfunction "IN2_J1") (pintype "input"))
      (node (ref "B08") (pin "J2") (pinfunction "IN2_J2") (pintype "input"))
      (node (ref "B08") (pin "M1") (pinfunction "IN2_M1") (pintype "input"))
      (node (ref "B08") (pin "M2") (pinfunction "IN2_M2") (pintype "input"))
      (node (ref "B08") (pin "U1") (pinfunction "P$1_U1") (pintype "passive"))
    )
    (net (code "6") (name "+3V(06)") (class "Default")
      (node (ref "B08") (pin "R1") (pinfunction "IN2_R1") (pintype "input"))
      (node (ref "B08") (pin "R2") (pinfunction "IN2_R2") (pintype "input"))
      (node (ref "B08") (pin "U2") (pinfunction "IN2_U2") (pintype "input"))
      (node (ref "B09") (pin "B1") (pinfunction "IN2_B1") (pintype "input"))
      (node (ref "B09") (pin "D2") (pinfunction "IN1_D2") (pintype "input"))
      (node (ref "B09") (pin "E1") (pinfunction "IN2_E1") (pintype "input"))
      (node (ref "B09") (pin "H2") (pinfunction "IN1_H2") (pintype "input"))
      (node (ref "B09") (pin "U1") (pinfunction "P$1_U1") (pintype "passive"))
    )
    (net (code "7") (name "+3V(07)") (class "Default")
      (node (ref "B07") (pin "F1") (pinfunction "IN2_F1") (pintype "input"))
      (node (ref "B07") (pin "K1") (pinfunction "IN1_K1") (pintype "input"))
      (node (ref "B07") (pin "P2") (pinfunction "IN2_P2") (pintype "input"))
      (node (ref "B07") (pin "R2") (pinfunction "IN3_R2") (pintype "input"))
      (node (ref "B09") (pin "J1") (pinfunction "IN2_J1") (pintype "input"))
      (node (ref "B09") (pin "M2") (pinfunction "IN2_M2") (pintype "input"))
      (node (ref "B09") (pin "V1") (pinfunction "P$1_V1") (pintype "passive"))
    )
    (net (code "8") (name "+3V(08)") (class "Default")
      (node (ref "B11") (pin "A1") (pinfunction "R_A1") (pintype "input"))
      (node (ref "B12") (pin "B1") (pinfunction "IN2_B1") (pintype "input"))
      (node (ref "B12") (pin "C1") (pinfunction "IN3_C1") (pintype "input"))
      (node (ref "B12") (pin "D1") (pinfunction "IN4_D1") (pintype "input"))
      (node (ref "B12") (pin "E2") (pinfunction "IN2_E2") (pintype "input"))
      (node (ref "B12") (pin "F2") (pinfunction "IN3_F2") (pintype "input"))
      (node (ref "B12") (pin "H1") (pinfunction "IN2_H1") (pintype "input"))
      (node (ref "B12") (pin "H2") (pinfunction "IN4_H2") (pintype "input"))
      (node (ref "B12") (pin "J1") (pinfunction "IN3_J1") (pintype "input"))
      (node (ref "B12") (pin "K1") (pinfunction "IN4_K1") (pintype "input"))
      (node (ref "C12") (pin "V1") (pinfunction "P$1_V1") (pintype "passive"))
    )
    (net (code "9") (name "+3V(09)") (class "Default")
      (node (ref "A11") (pin "V1") (pinfunction "P$1_V1") (pintype "passive"))
      (node (ref "B12") (pin "L2") (pinfunction "IN2_L2") (pintype "input"))
      (node (ref "B12") (pin "M2") (pinfunction "IN3_M2") (pintype "input"))
      (node (ref "B12") (pin "N1") (pinfunction "IN2_N1") (pintype "input"))
      (node (ref "B12") (pin "N2") (pinfunction "IN4_N2") (pintype "input"))
      (node (ref "B12") (pin "P1") (pinfunction "IN3_P1") (pintype "input"))
      (node (ref "B12") (pin "R1") (pinfunction "IN4_R1") (pintype "input"))
    )
    (net (code "10") (name "+3V(10)") (class "Default")
      (node (ref "B12") (pin "S2") (pinfunction "IN2_S2") (pintype "input"))
      (node (ref "B12") (pin "T2") (pinfunction "IN3_T2") (pintype "input"))
      (node (ref "B12") (pin "U2") (pinfunction "IN4_U2") (pintype "input"))
      (node (ref "B13") (pin "B1") (pinfunction "IN2_B1") (pintype "input"))
      (node (ref "B13") (pin "C1") (pinfunction "IN3_C1") (pintype "input"))
      (node (ref "B13") (pin "D1") (pinfunction "IN4_D1") (pintype "input"))
      (node (ref "B13") (pin "E2") (pinfunction "IN2_E2") (pintype "input"))
      (node (ref "B13") (pin "F2") (pinfunction "IN3_F2") (pintype "input"))
      (node (ref "B13") (pin "H2") (pinfunction "IN4_H2") (pintype "input"))
      (node (ref "F09") (pin "V1") (pinfunction "P$1_V1") (pintype "passive"))
    )
    (net (code "11") (name "+3V(11)") (class "Default")
      (node (ref "A13") (pin "U1") (pinfunction "P$1_U1") (pintype "passive"))
      (node (ref "B13") (pin "H1") (pinfunction "IN2_H1") (pintype "input"))
      (node (ref "B13") (pin "J1") (pinfunction "IN3_J1") (pintype "input"))
      (node (ref "B13") (pin "K1") (pinfunction "IN4_K1") (pintype "input"))
    )
    (net (code "12") (name "+3V(12)") (class "Default")
      (node (ref "B13") (pin "L2") (pinfunction "IN2_L2") (pintype "input"))
      (node (ref "B13") (pin "M2") (pinfunction "IN3_M2") (pintype "input"))
      (node (ref "B13") (pin "N1") (pinfunction "IN2_N1") (pintype "input"))
      (node (ref "B13") (pin "N2") (pinfunction "IN4_N2") (pintype "input"))
      (node (ref "B13") (pin "P1") (pinfunction "IN3_P1") (pintype "input"))
      (node (ref "B13") (pin "R1") (pinfunction "IN4_R1") (pintype "input"))
      (node (ref "B13") (pin "S2") (pinfunction "IN2_S2") (pintype "input"))
      (node (ref "B13") (pin "T2") (pinfunction "IN3_T2") (pintype "input"))
      (node (ref "B13") (pin "U1") (pinfunction "P$1_U1") (pintype "passive"))
      (node (ref "B13") (pin "U2") (pinfunction "IN4_U2") (pintype "input"))
      (node (ref "B14") (pin "B1") (pinfunction "IN2_B1") (pintype "input"))
      (node (ref "B14") (pin "C1") (pinfunction "IN3_C1") (pintype "input"))
      (node (ref "B14") (pin "D1") (pinfunction "IN4_D1") (pintype "input"))
    )
    (net (code "13") (name "+3V(13)") (class "Default")
      (node (ref "B13") (pin "V1") (pinfunction "P$1_V1") (pintype "passive"))
      (node (ref "B14") (pin "E2") (pinfunction "IN2_E2") (pintype "input"))
      (node (ref "B14") (pin "F2") (pinfunction "IN3_F2") (pintype "input"))
      (node (ref "B14") (pin "H2") (pinfunction "IN4_H2") (pintype "input"))
    )
    (net (code "14") (name "+3V(14)") (class "Default")
      (node (ref "B14") (pin "H1") (pinfunction "IN2_H1") (pintype "input"))
      (node (ref "B14") (pin "J1") (pinfunction "IN3_J1") (pintype "input"))
      (node (ref "B14") (pin "K1") (pinfunction "IN4_K1") (pintype "input"))
      (node (ref "B14") (pin "L2") (pinfunction "IN2_L2") (pintype "input"))
      (node (ref "B14") (pin "M2") (pinfunction "IN3_M2") (pintype "input"))
      (node (ref "B14") (pin "N1") (pinfunction "IN2_N1") (pintype "input"))
      (node (ref "B14") (pin "N2") (pinfunction "IN4_N2") (pintype "input"))
      (node (ref "B14") (pin "P1") (pinfunction "IN3_P1") (pintype "input"))
      (node (ref "B14") (pin "R1") (pinfunction "IN4_R1") (pintype "input"))
      (node (ref "B14") (pin "U1") (pinfunction "P$1_U1") (pintype "passive"))
    )
    (net (code "15") (name "+3V(15)") (class "Default")
      (node (ref "B14") (pin "S2") (pinfunction "IN2_S2") (pintype "input"))
      (node (ref "B14") (pin "T2") (pinfunction "IN3_T2") (pintype "input"))
      (node (ref "B14") (pin "U2") (pinfunction "IN4_U2") (pintype "input"))
      (node (ref "B14") (pin "V1") (pinfunction "P$1_V1") (pintype "passive"))
      (node (ref "B15") (pin "B1") (pinfunction "IN2_B1") (pintype "input"))
      (node (ref "B15") (pin "C1") (pinfunction "IN3_C1") (pintype "input"))
      (node (ref "B15") (pin "D1") (pinfunction "IN4_D1") (pintype "input"))
    )
    (net (code "16") (name "+3V(16)") (class "Default")
      (node (ref "B15") (pin "E2") (pinfunction "IN2_E2") (pintype "input"))
      (node (ref "B15") (pin "F2") (pinfunction "IN3_F2") (pintype "input"))
      (node (ref "B15") (pin "H1") (pinfunction "IN2_H1") (pintype "input"))
      (node (ref "B15") (pin "H2") (pinfunction "IN4_H2") (pintype "input"))
      (node (ref "B15") (pin "J1") (pinfunction "IN3_J1") (pintype "input"))
      (node (ref "B15") (pin "K1") (pinfunction "IN4_K1") (pintype "input"))
      (node (ref "B15") (pin "U1") (pinfunction "P$1_U1") (pintype "passive"))
    )
    (net (code "17") (name "+3V(17)") (class "Default")
      (node (ref "B15") (pin "L2") (pinfunction "IN2_L2") (pintype "input"))
      (node (ref "B15") (pin "M2") (pinfunction "IN3_M2") (pintype "input"))
      (node (ref "B15") (pin "N1") (pinfunction "IN2_N1") (pintype "input"))
      (node (ref "B15") (pin "N2") (pinfunction "IN4_N2") (pintype "input"))
      (node (ref "B15") (pin "P1") (pinfunction "IN3_P1") (pintype "input"))
      (node (ref "B15") (pin "R1") (pinfunction "IN4_R1") (pintype "input"))
      (node (ref "B15") (pin "S2") (pinfunction "IN2_S2") (pintype "input"))
      (node (ref "B15") (pin "T2") (pinfunction "IN3_T2") (pintype "input"))
      (node (ref "B15") (pin "U2") (pinfunction "IN4_U2") (pintype "input"))
      (node (ref "B16") (pin "V1") (pinfunction "P$1_V1") (pintype "passive"))
    )
    (net (code "18") (name "+3V(18)") (class "Default")
      (node (ref "B16") (pin "D1") (pinfunction "IN4_D1") (pintype "input"))
      (node (ref "B16") (pin "H2") (pinfunction "IN4_H2") (pintype "input"))
      (node (ref "B16") (pin "K1") (pinfunction "IN4_K1") (pintype "input"))
      (node (ref "B16") (pin "N1") (pinfunction "IN2_N1") (pintype "input"))
      (node (ref "B16") (pin "P1") (pinfunction "IN3_P1") (pintype "input"))
      (node (ref "B16") (pin "R1") (pinfunction "IN4_R1") (pintype "input"))
      (node (ref "B16") (pin "S2") (pinfunction "IN2_S2") (pintype "input"))
      (node (ref "B16") (pin "T2") (pinfunction "IN3_T2") (pintype "input"))
      (node (ref "B16") (pin "U1") (pinfunction "P$1_U1") (pintype "passive"))
      (node (ref "B16") (pin "U2") (pinfunction "IN4_U2") (pintype "input"))
    )
    (net (code "19") (name "+3V(19)") (class "Default")
      (node (ref "A19") (pin "U1") (pinfunction "P$1_U1") (pintype "passive"))
      (node (ref "B17") (pin "D1") (pinfunction "S_D1") (pintype "input"))
      (node (ref "B17") (pin "F2") (pinfunction "S_F2") (pintype "input"))
      (node (ref "B17") (pin "K1") (pinfunction "S_K1") (pintype "input"))
      (node (ref "B17") (pin "N2") (pinfunction "S_N2") (pintype "input"))
      (node (ref "B17") (pin "R1") (pinfunction "S_R1") (pintype "input"))
      (node (ref "B17") (pin "U2") (pinfunction "S_U2") (pintype "input"))
      (node (ref "B18") (pin "D1") (pinfunction "S_D1") (pintype "input"))
      (node (ref "B18") (pin "F2") (pinfunction "S_F2") (pintype "input"))
      (node (ref "B18") (pin "K1") (pinfunction "S_K1") (pintype "input"))
      (node (ref "B18") (pin "K2") (pinfunction "R_K2") (pintype "input"))
    )
    (net (code "20") (name "+3V(20)") (class "Default")
      (node (ref "A19") (pin "V1") (pinfunction "P$1_V1") (pintype "passive"))
      (node (ref "B18") (pin "N2") (pinfunction "S_N2") (pintype "input"))
      (node (ref "B18") (pin "R1") (pinfunction "S_R1") (pintype "input"))
      (node (ref "B18") (pin "U2") (pinfunction "S_U2") (pintype "input"))
      (node (ref "B19") (pin "A1") (pinfunction "R_A1") (pintype "input"))
      (node (ref "B19") (pin "D1") (pinfunction "S_D1") (pintype "input"))
      (node (ref "B19") (pin "F2") (pinfunction "S_F2") (pintype "input"))
      (node (ref "B19") (pin "K1") (pinfunction "S_K1") (pintype "input"))
      (node (ref "B19") (pin "K2") (pinfunction "R_K2") (pintype "input"))
      (node (ref "B19") (pin "N2") (pinfunction "S_N2") (pintype "input"))
      (node (ref "B19") (pin "R1") (pinfunction "S_R1") (pintype "input"))
      (node (ref "B19") (pin "U2") (pinfunction "S_U2") (pintype "input"))
    )
    (net (code "21") (name "+3V(21)") (class "Default")
      (node (ref "B21") (pin "B1") (pinfunction "IN2_B1") (pintype "input"))
      (node (ref "B21") (pin "E2") (pinfunction "IN2_E2") (pintype "input"))
      (node (ref "B21") (pin "H1") (pinfunction "IN1_H1") (pintype "input"))
      (node (ref "B21") (pin "J2") (pinfunction "IN2_J2") (pintype "input"))
      (node (ref "B21") (pin "U1") (pinfunction "P$1_U1") (pintype "passive"))
      (node (ref "B22") (pin "D1") (pinfunction "S_D1") (pintype "input"))
      (node (ref "B22") (pin "F2") (pinfunction "S_F2") (pintype "input"))
      (node (ref "B30") (pin "B1") (pinfunction "IN2_B1") (pintype "input"))
      (node (ref "B30") (pin "C1") (pinfunction "IN3_C1") (pintype "input"))
      (node (ref "B30") (pin "D1") (pinfunction "IN4_D1") (pintype "input"))
      (node (ref "B30") (pin "D2") (pinfunction "IN1_D2") (pintype "input"))
    )
    (net (code "22") (name "+3V(22)") (class "Default")
      (node (ref "B30") (pin "E2") (pinfunction "IN2_E2") (pintype "input"))
      (node (ref "B30") (pin "F2") (pinfunction "IN3_F2") (pintype "input"))
      (node (ref "B30") (pin "H1") (pinfunction "IN2_H1") (pintype "input"))
      (node (ref "B30") (pin "J1") (pinfunction "IN3_J1") (pintype "input"))
      (node (ref "B30") (pin "K1") (pinfunction "IN4_K1") (pintype "input"))
      (node (ref "B30") (pin "L2") (pinfunction "IN2_L2") (pintype "input"))
      (node (ref "B30") (pin "M2") (pinfunction "IN3_M2") (pintype "input"))
      (node (ref "B30") (pin "N1") (pinfunction "IN2_N1") (pintype "input"))
      (node (ref "B30") (pin "N2") (pinfunction "IN4_N2") (pintype "input"))
      (node (ref "B30") (pin "P1") (pinfunction "IN3_P1") (pintype "input"))
      (node (ref "B30") (pin "R1") (pinfunction "IN4_R1") (pintype "input"))
      (node (ref "B30") (pin "S2") (pinfunction "IN2_S2") (pintype "input"))
      (node (ref "B30") (pin "T2") (pinfunction "IN3_T2") (pintype "input"))
      (node (ref "B30") (pin "U1") (pinfunction "P$1_U1") (pintype "passive"))
      (node (ref "B30") (pin "U2") (pinfunction "IN4_U2") (pintype "input"))
      (node (ref "D39") (pin "A1") (pinfunction "A1_A1") (pintype "input"))
      (node (ref "D39") (pin "E2") (pinfunction "E2_E2") (pintype "input"))
      (node (ref "D39") (pin "N2") (pinfunction "N2_N2") (pintype "input"))
    )
    (net (code "23") (name "+3V(23)") (class "Default")
      (node (ref "C10") (pin "B1") (pinfunction "IN2_B1") (pintype "input"))
      (node (ref "C10") (pin "D1") (pinfunction "IN1_D1") (pintype "input"))
      (node (ref "C10") (pin "D2") (pinfunction "IN1_D2") (pintype "input"))
      (node (ref "C10") (pin "H2") (pinfunction "IN1_H2") (pintype "input"))
      (node (ref "C10") (pin "J1") (pinfunction "IN2_J1") (pintype "input"))
      (node (ref "C10") (pin "U2") (pinfunction "IN2_U2") (pintype "input"))
      (node (ref "C11") (pin "B1") (pinfunction "IN2_B1") (pintype "input"))
      (node (ref "D10") (pin "B1") (pinfunction "IN2_B1") (pintype "input"))
      (node (ref "D10") (pin "C1") (pinfunction "IN3_C1") (pintype "input"))
      (node (ref "D10") (pin "U1") (pinfunction "P$1_U1") (pintype "passive"))
      (node (ref "D11") (pin "A1") (pinfunction "R_A1") (pintype "input"))
    )
    (net (code "24") (name "+3V(24)") (class "Default")
      (node (ref "C18") (pin "A1") (pinfunction "IN1_A1") (pintype "input"))
      (node (ref "C18") (pin "D1") (pinfunction "IN1_D1") (pintype "input"))
      (node (ref "C18") (pin "D2") (pinfunction "IN1_D2") (pintype "input"))
      (node (ref "C18") (pin "H2") (pinfunction "IN1_H2") (pintype "input"))
      (node (ref "C18") (pin "R2") (pinfunction "IN2_R2") (pintype "input"))
      (node (ref "C18") (pin "U1") (pinfunction "P$1_U1") (pintype "passive"))
      (node (ref "C18") (pin "U2") (pinfunction "IN2_U2") (pintype "input"))
    )
    (net (code "25") (name "+3V(25)") (class "Default")
      (node (ref "B21") (pin "V1") (pinfunction "P$1_V1") (pintype "passive"))
      (node (ref "C22") (pin "A1") (pinfunction "R_A1") (pintype "input"))
      (node (ref "C22") (pin "D1") (pinfunction "S_D1") (pintype "input"))
      (node (ref "C22") (pin "F2") (pinfunction "S_F2") (pintype "input"))
      (node (ref "C22") (pin "K1") (pinfunction "S_K1") (pintype "input"))
      (node (ref "C22") (pin "K2") (pinfunction "R_K2") (pintype "input"))
      (node (ref "C22") (pin "N2") (pinfunction "S_N2") (pintype "input"))
      (node (ref "C22") (pin "R1") (pinfunction "S_R1") (pintype "input"))
    )
    (net (code "26") (name "+3V(26)") (class "Default")
      (node (ref "C23") (pin "A1") (pinfunction "R_A1") (pintype "input"))
      (node (ref "C23") (pin "D1") (pinfunction "S_D1") (pintype "input"))
      (node (ref "C23") (pin "F2") (pinfunction "S_F2") (pintype "input"))
      (node (ref "C23") (pin "K1") (pinfunction "S_K1") (pintype "input"))
      (node (ref "C23") (pin "K2") (pinfunction "R_K2") (pintype "input"))
      (node (ref "C23") (pin "N2") (pinfunction "S_N2") (pintype "input"))
      (node (ref "C23") (pin "R1") (pinfunction "S_R1") (pintype "input"))
      (node (ref "C23") (pin "U2") (pinfunction "S_U2") (pintype "input"))
      (node (ref "D22") (pin "U1") (pinfunction "P$1_U1") (pintype "passive"))
    )
    (net (code "27") (name "+3V(27)") (class "Default")
      (node (ref "C24") (pin "A1") (pinfunction "R_A1") (pintype "input"))
      (node (ref "C24") (pin "D1") (pinfunction "S_D1") (pintype "input"))
      (node (ref "C24") (pin "F2") (pinfunction "S_F2") (pintype "input"))
      (node (ref "C24") (pin "K1") (pinfunction "S_K1") (pintype "input"))
      (node (ref "C24") (pin "K2") (pinfunction "R_K2") (pintype "input"))
      (node (ref "C24") (pin "N2") (pinfunction "S_N2") (pintype "input"))
      (node (ref "C24") (pin "R1") (pinfunction "S_R1") (pintype "input"))
      (node (ref "C24") (pin "U2") (pinfunction "S_U2") (pintype "input"))
      (node (ref "D22") (pin "V1") (pinfunction "P$1_V1") (pintype "passive"))
    )
    (net (code "28") (name "+3V(28)") (class "Default")
      (node (ref "D12") (pin "E1") (pinfunction "IN2_E1") (pintype "input"))
      (node (ref "D12") (pin "J2") (pinfunction "IN2_J2") (pintype "input"))
      (node (ref "D12") (pin "M1") (pinfunction "IN2_M1") (pintype "input"))
      (node (ref "D12") (pin "T2") (pinfunction "IN1_T2") (pintype "input"))
      (node (ref "D12") (pin "U1") (pinfunction "P$1_U1") (pintype "passive"))
      (node (ref "D13") (pin "J1") (pinfunction "IN2_J1") (pintype "input"))
      (node (ref "D13") (pin "J2") (pinfunction "IN2_J2") (pintype "input"))
    )
    (net (code "29") (name "+3V(29)") (class "Default")
      (node (ref "D14") (pin "P1") (pinfunction "IN1_P1") (pintype "input"))
      (node (ref "D15") (pin "D2") (pinfunction "IN1_D2") (pintype "input"))
      (node (ref "D15") (pin "H2") (pinfunction "IN1_H2") (pintype "input"))
      (node (ref "D15") (pin "M2") (pinfunction "IN2_M2") (pintype "input"))
      (node (ref "D15") (pin "P1") (pinfunction "IN1_P1") (pintype "input"))
      (node (ref "D15") (pin "U1") (pinfunction "P$1_U1") (pintype "passive"))
      (node (ref "D15") (pin "U2") (pinfunction "IN2_U2") (pintype "input"))
    )
    (net (code "30") (name "+3V(30)") (class "Default")
      (node (ref "D16") (pin "A1") (pinfunction "IN1_A1") (pintype "input"))
      (node (ref "D16") (pin "D1") (pinfunction "IN1_D1") (pintype "input"))
      (node (ref "D16") (pin "D2") (pinfunction "IN1_D2") (pintype "input"))
      (node (ref "D16") (pin "M2") (pinfunction "IN2_M2") (pintype "input"))
      (node (ref "D16") (pin "R1") (pinfunction "IN2_R1") (pintype "input"))
      (node (ref "D16") (pin "R2") (pinfunction "IN2_R2") (pintype "input"))
      (node (ref "D16") (pin "U1") (pinfunction "P$1_U1") (pintype "passive"))
      (node (ref "D16") (pin "U2") (pinfunction "IN2_U2") (pintype "input"))
    )
    (net (code "31") (name "+3V(31)") (class "Default")
      (node (ref "D22") (pin "H1") (pinfunction "IN2_H1") (pintype "input"))
      (node (ref "D22") (pin "J1") (pinfunction "IN3_J1") (pintype "input"))
      (node (ref "D22") (pin "K1") (pinfunction "IN4_K1") (pintype "input"))
      (node (ref "D22") (pin "L2") (pinfunction "IN2_L2") (pintype "input"))
      (node (ref "D22") (pin "M1") (pinfunction "IN1_M1") (pintype "input"))
      (node (ref "D22") (pin "M2") (pinfunction "IN3_M2") (pintype "input"))
      (node (ref "D22") (pin "N1") (pinfunction "IN2_N1") (pintype "input"))
      (node (ref "D22") (pin "N2") (pinfunction "IN4_N2") (pintype "input"))
      (node (ref "D22") (pin "T2") (pinfunction "IN3_T2") (pintype "input"))
      (node (ref "E22") (pin "V1") (pinfunction "P$1_V1") (pintype "passive"))
    )
    (net (code "32") (name "+3V(32)") (class "Default")
      (node (ref "D23") (pin "D2") (pinfunction "IN1A_D2") (pintype "input"))
      (node (ref "D23") (pin "E2") (pinfunction "IN1B_E2") (pintype "input"))
      (node (ref "D23") (pin "M1") (pinfunction "IN5A_M1") (pintype "input"))
      (node (ref "D23") (pin "N2") (pinfunction "IN4A_N2") (pintype "input"))
      (node (ref "D23") (pin "P2") (pinfunction "IN4B_P2") (pintype "input"))
      (node (ref "D23") (pin "R2") (pinfunction "IN4C_R2") (pintype "input"))
      (node (ref "D24") (pin "D1") (pinfunction "S_D1") (pintype "input"))
      (node (ref "D24") (pin "F2") (pinfunction "S_F2") (pintype "input"))
      (node (ref "D24") (pin "K1") (pinfunction "S_K1") (pintype "input"))
      (node (ref "D24") (pin "N2") (pinfunction "S_N2") (pintype "input"))
      (node (ref "E24") (pin "U1") (pinfunction "P$1_U1") (pintype "passive"))
    )
    (net (code "33") (name "+3V(33)") (class "Default")
      (node (ref "E11") (pin "B1") (pinfunction "IN2_B1") (pintype "input"))
      (node (ref "E11") (pin "E2") (pinfunction "IN2_E2") (pintype "input"))
      (node (ref "E11") (pin "H2") (pinfunction "IN1_H2") (pintype "input"))
      (node (ref "E11") (pin "M2") (pinfunction "IN2_M2") (pintype "input"))
      (node (ref "E11") (pin "P2") (pinfunction "IN1_P2") (pintype "input"))
      (node (ref "E12") (pin "B1") (pinfunction "IN2_B1") (pintype "input"))
      (node (ref "E12") (pin "J1") (pinfunction "IN2_J1") (pintype "input"))
      (node (ref "E12") (pin "L1") (pinfunction "IN1_L1") (pintype "input"))
      (node (ref "E12") (pin "R1") (pinfunction "IN2_R1") (pintype "input"))
      (node (ref "E12") (pin "T2") (pinfunction "IN1_T2") (pintype "input"))
      (node (ref "EF01") (pin "BR1") (pinfunction "BR1_BR1") (pintype "input"))
      (node (ref "EF02") (pin "AN1") (pinfunction "AN1_AN1") (pintype "input"))
      (node (ref "EF02") (pin "AN2") (pinfunction "AN2_AN2") (pintype "input"))
      (node (ref "EF02") (pin "BF2") (pinfunction "BF2_BF2") (pintype "input"))
      (node (ref "EF02") (pin "BJ1") (pinfunction "BJ1_BJ1") (pintype "output"))
      (node (ref "EF02") (pin "BS2") (pinfunction "BS2_BS2") (pintype "input"))
    )
    (net (code "34") (name "+3V(34)") (class "Default")
      (node (ref "E13") (pin "N1") (pinfunction "IN5B_N1") (pintype "input"))
      (node (ref "E13") (pin "P1") (pinfunction "IN5C_P1") (pintype "input"))
      (node (ref "E15") (pin "J2") (pinfunction "IN2_J2") (pintype "input"))
      (node (ref "E15") (pin "M1") (pinfunction "IN2_M1") (pintype "input"))
      (node (ref "E15") (pin "M2") (pinfunction "IN2_M2") (pintype "input"))
      (node (ref "E15") (pin "P2") (pinfunction "IN1_P2") (pintype "input"))
      (node (ref "E15") (pin "U1") (pinfunction "P$1_U1") (pintype "passive"))
      (node (ref "E15") (pin "U2") (pinfunction "IN2_U2") (pintype "input"))
    )
    (net (code "35") (name "+3V(35)") (class "Default")
      (node (ref "E15") (pin "V1") (pinfunction "P$1_V1") (pintype "passive"))
      (node (ref "E18") (pin "C1") (pinfunction "D_C1") (pintype "input"))
      (node (ref "E18") (pin "N2") (pinfunction "S_N2") (pintype "input"))
      (node (ref "E20") (pin "D1") (pinfunction "S_D1") (pintype "input"))
      (node (ref "E20") (pin "F2") (pinfunction "S_F2") (pintype "input"))
      (node (ref "E20") (pin "K1") (pinfunction "S_K1") (pintype "input"))
      (node (ref "E20") (pin "N2") (pinfunction "S_N2") (pintype "input"))
    )
    (net (code "36") (name "+3V(36)") (class "Default")
      (node (ref "E22") (pin "M2") (pinfunction "IN2_M2") (pintype "input"))
      (node (ref "E22") (pin "R1") (pinfunction "IN2_R1") (pintype "input"))
      (node (ref "E22") (pin "R2") (pinfunction "IN2_R2") (pintype "input"))
      (node (ref "E22") (pin "U1") (pinfunction "P$1_U1") (pintype "passive"))
      (node (ref "E22") (pin "U2") (pinfunction "IN2_U2") (pintype "input"))
      (node (ref "E23") (pin "F2") (pinfunction "S_F2") (pintype "input"))
      (node (ref "E23") (pin "K1") (pinfunction "S_K1") (pintype "input"))
      (node (ref "E23") (pin "N2") (pinfunction "S_N2") (pintype "input"))
      (node (ref "E23") (pin "R1") (pinfunction "S_R1") (pintype "input"))
      (node (ref "E23") (pin "U2") (pinfunction "S_U2") (pintype "input"))
      (node (ref "E24") (pin "J1") (pinfunction "IN2_J1") (pintype "input"))
      (node (ref "E24") (pin "M2") (pinfunction "IN2_M2") (pintype "input"))
      (node (ref "E24") (pin "P1") (pinfunction "IN1_P1") (pintype "input"))
      (node (ref "E24") (pin "P2") (pinfunction "IN1_P2") (pintype "input"))
    )
    (net (code "37") (name "+3V(37)") (class "Default")
      (node (ref "E26") (pin "D2") (pinfunction "IN1A_D2") (pintype "input"))
      (node (ref "E26") (pin "N2") (pinfunction "IN4A_N2") (pintype "input"))
      (node (ref "E27") (pin "C1") (pinfunction "IN1C_C1") (pintype "input"))
      (node (ref "E27") (pin "E2") (pinfunction "IN1B_E2") (pintype "input"))
      (node (ref "E27") (pin "F2") (pinfunction "IN1C_F2") (pintype "input"))
      (node (ref "E27") (pin "H2") (pinfunction "IN1D_H2") (pintype "input"))
      (node (ref "E27") (pin "N2") (pinfunction "IN4A_N2") (pintype "input"))
      (node (ref "E28") (pin "A1") (pinfunction "IN1A_A1") (pintype "input"))
      (node (ref "E28") (pin "H1") (pinfunction "IN3A_H1") (pintype "input"))
      (node (ref "F27") (pin "U1") (pinfunction "P$1_U1") (pintype "passive"))
    )
    (net (code "38") (name "+3V(38)") (class "Default")
      (node (ref "E28") (pin "K1") (pinfunction "IN4A_K1") (pintype "input"))
      (node (ref "E29") (pin "B1") (pinfunction "IN1B_B1") (pintype "input"))
      (node (ref "E29") (pin "E2") (pinfunction "IN1B_E2") (pintype "input"))
      (node (ref "E29") (pin "H1") (pinfunction "IN3A_H1") (pintype "input"))
      (node (ref "E29") (pin "H2") (pinfunction "IN1D_H2") (pintype "input"))
      (node (ref "E29") (pin "P2") (pinfunction "IN4B_P2") (pintype "input"))
      (node (ref "E29") (pin "R2") (pinfunction "IN4C_R2") (pintype "input"))
      (node (ref "F29") (pin "U1") (pinfunction "P$1_U1") (pintype "passive"))
    )
    (net (code "39") (name "+3V(39)") (class "Default")
      (node (ref "E30") (pin "B1") (pinfunction "IN1B_B1") (pintype "input"))
      (node (ref "E30") (pin "C1") (pinfunction "IN1C_C1") (pintype "input"))
      (node (ref "E30") (pin "D1") (pinfunction "IN1D_D1") (pintype "input"))
      (node (ref "E30") (pin "E2") (pinfunction "IN1B_E2") (pintype "input"))
      (node (ref "E30") (pin "N2") (pinfunction "IN4A_N2") (pintype "input"))
      (node (ref "E31") (pin "B1") (pinfunction "IN2_B1") (pintype "input"))
      (node (ref "E31") (pin "C1") (pinfunction "IN3_C1") (pintype "input"))
      (node (ref "E31") (pin "D1") (pinfunction "IN4_D1") (pintype "input"))
      (node (ref "E31") (pin "D2") (pinfunction "IN1_D2") (pintype "input"))
      (node (ref "E31") (pin "E2") (pinfunction "IN2_E2") (pintype "input"))
      (node (ref "E31") (pin "U1") (pinfunction "P$1_U1") (pintype "passive"))
    )
    (net (code "40") (name "+3V(40)") (class "Default")
      (node (ref "E31") (pin "F1") (pinfunction "IN1_F1") (pintype "input"))
      (node (ref "E31") (pin "F2") (pinfunction "IN3_F2") (pintype "input"))
      (node (ref "E31") (pin "K2") (pinfunction "IN1_K2") (pintype "input"))
      (node (ref "E31") (pin "L2") (pinfunction "IN2_L2") (pintype "input"))
      (node (ref "E31") (pin "S2") (pinfunction "IN2_S2") (pintype "input"))
      (node (ref "E31") (pin "T2") (pinfunction "IN3_T2") (pintype "input"))
      (node (ref "E31") (pin "U2") (pinfunction "IN4_U2") (pintype "input"))
      (node (ref "E31") (pin "V1") (pinfunction "P$1_V1") (pintype "passive"))
    )
    (net (code "41") (name "+3V(41)") (class "Default")
      (node (ref "E32") (pin "B1") (pinfunction "IN2_B1") (pintype "input"))
      (node (ref "E32") (pin "C1") (pinfunction "IN3_C1") (pintype "input"))
      (node (ref "E32") (pin "D2") (pinfunction "IN1_D2") (pintype "input"))
      (node (ref "E32") (pin "F1") (pinfunction "IN1_F1") (pintype "input"))
      (node (ref "E32") (pin "H1") (pinfunction "IN2_H1") (pintype "input"))
      (node (ref "E32") (pin "J1") (pinfunction "IN3_J1") (pintype "input"))
      (node (ref "E32") (pin "U1") (pinfunction "P$1_U1") (pintype "passive"))
    )
    (net (code "42") (name "+3V(42)") (class "Default")
      (node (ref "C39") (pin "D1") (pinfunction "D1_D1") (pintype "input"))
      (node (ref "C39") (pin "L1") (pinfunction "L1_L1") (pintype "input"))
      (node (ref "D39") (pin "D1") (pinfunction "D1_D1") (pintype "input"))
      (node (ref "D39") (pin "L1") (pinfunction "L1_L1") (pintype "input"))
      (node (ref "E32") (pin "R2") (pinfunction "IN1_R2") (pintype "input"))
      (node (ref "E32") (pin "S2") (pinfunction "IN2_S2") (pintype "input"))
      (node (ref "E32") (pin "V1") (pinfunction "P$1_V1") (pintype "passive"))
      (node (ref "E33") (pin "A1") (pinfunction "R_A1") (pintype "input"))
      (node (ref "E33") (pin "K2") (pinfunction "R_K2") (pintype "input"))
      (node (ref "E33") (pin "U2") (pinfunction "S_U2") (pintype "input"))
    )
    (net (code "43") (name "+3V(43)") (class "Default")
      (node (ref "C12") (pin "F1") (pinfunction "IN1_F1") (pintype "input"))
      (node (ref "F19") (pin "N2") (pinfunction "IN4_N2") (pintype "input"))
      (node (ref "F20") (pin "A1") (pinfunction "IN1_A1") (pintype "input"))
      (node (ref "F20") (pin "M1") (pinfunction "IN2_M1") (pintype "input"))
      (node (ref "F20") (pin "M2") (pinfunction "IN2_M2") (pintype "input"))
      (node (ref "F20") (pin "U1") (pinfunction "P$1_U1") (pintype "passive"))
      (node (ref "F21") (pin "E2") (pinfunction "IN2_E2") (pintype "input"))
      (node (ref "F21") (pin "J2") (pinfunction "IN2_J2") (pintype "input"))
      (node (ref "F21") (pin "L1") (pinfunction "IN1_L1") (pintype "input"))
      (node (ref "F21") (pin "P2") (pinfunction "IN1_P2") (pintype "input"))
      (node (ref "F21") (pin "R1") (pinfunction "IN2_R1") (pintype "input"))
    )
    (net (code "44") (name "+3V(44)") (class "Default")
      (node (ref "F22") (pin "A1") (pinfunction "IN1_A1") (pintype "input"))
      (node (ref "F22") (pin "E1") (pinfunction "IN2_E1") (pintype "input"))
      (node (ref "F22") (pin "J1") (pinfunction "IN2_J1") (pintype "input"))
      (node (ref "F22") (pin "J2") (pinfunction "IN2_J2") (pintype "input"))
      (node (ref "F22") (pin "M1") (pinfunction "IN2_M1") (pintype "input"))
      (node (ref "F22") (pin "M2") (pinfunction "IN2_M2") (pintype "input"))
      (node (ref "F22") (pin "U1") (pinfunction "P$1_U1") (pintype "passive"))
      (node (ref "F24") (pin "D1") (pinfunction "IN4_D1") (pintype "input"))
      (node (ref "F25") (pin "B1") (pinfunction "IN2_B1") (pintype "input"))
      (node (ref "F25") (pin "E1") (pinfunction "IN2_E1") (pintype "input"))
      (node (ref "F25") (pin "M2") (pinfunction "IN2_M2") (pintype "input"))
    )
    (net (code "45") (name "+3V(45)") (class "Default")
      (node (ref "F25") (pin "R1") (pinfunction "IN2_R1") (pintype "input"))
      (node (ref "F29") (pin "B1") (pinfunction "IN2_B1") (pintype "input"))
      (node (ref "F29") (pin "E2") (pinfunction "IN2_E2") (pintype "input"))
      (node (ref "F29") (pin "H1") (pinfunction "IN1_H1") (pintype "input"))
      (node (ref "F29") (pin "H2") (pinfunction "IN1_H2") (pintype "input"))
      (node (ref "F30") (pin "B1") (pinfunction "IN2_B1") (pintype "input"))
      (node (ref "F30") (pin "C1") (pinfunction "IN3_C1") (pintype "input"))
      (node (ref "F30") (pin "D1") (pinfunction "IN4_D1") (pintype "input"))
      (node (ref "F30") (pin "F2") (pinfunction "IN3_F2") (pintype "input"))
      (node (ref "F30") (pin "H1") (pinfunction "IN2_H1") (pintype "input"))
      (node (ref "F30") (pin "L2") (pinfunction "IN2_L2") (pintype "input"))
      (node (ref "F30") (pin "M2") (pinfunction "IN3_M2") (pintype "input"))
      (node (ref "F30") (pin "N2") (pinfunction "IN4_N2") (pintype "input"))
      (node (ref "F30") (pin "V1") (pinfunction "P$1_V1") (pintype "passive"))
    )
    (net (code "46") (name "+3V(46)") (class "Default")
      (node (ref "F30") (pin "J1") (pinfunction "IN3_J1") (pintype "input"))
      (node (ref "F30") (pin "K1") (pinfunction "IN4_K1") (pintype "input"))
      (node (ref "F30") (pin "R1") (pinfunction "IN4_R1") (pintype "input"))
      (node (ref "F30") (pin "R2") (pinfunction "IN1_R2") (pintype "input"))
      (node (ref "F30") (pin "S2") (pinfunction "IN2_S2") (pintype "input"))
      (node (ref "F30") (pin "T2") (pinfunction "IN3_T2") (pintype "input"))
      (node (ref "F30") (pin "U1") (pinfunction "P$1_U1") (pintype "passive"))
      (node (ref "F31") (pin "J1") (pinfunction "IN3_J1") (pintype "input"))
      (node (ref "J30") (pin "K2") (pinfunction "K2_K2") (pintype "input"))
    )
    (net (code "47") (name "+3V(47)") (class "Default")
      (node (ref "F31") (pin "K1") (pinfunction "IN4_K1") (pintype "input"))
      (node (ref "F31") (pin "L2") (pinfunction "IN2_L2") (pintype "input"))
      (node (ref "F31") (pin "M2") (pinfunction "IN3_M2") (pintype "input"))
      (node (ref "F31") (pin "N1") (pinfunction "IN2_N1") (pintype "input"))
      (node (ref "F31") (pin "N2") (pinfunction "IN4_N2") (pintype "input"))
      (node (ref "F31") (pin "P1") (pinfunction "IN3_P1") (pintype "input"))
      (node (ref "F31") (pin "R1") (pinfunction "IN4_R1") (pintype "input"))
      (node (ref "F31") (pin "S2") (pinfunction "IN2_S2") (pintype "input"))
      (node (ref "F31") (pin "T2") (pinfunction "IN3_T2") (pintype "input"))
      (node (ref "F31") (pin "U1") (pinfunction "P$1_U1") (pintype "passive"))
      (node (ref "F31") (pin "U2") (pinfunction "IN4_U2") (pintype "input"))
    )
    (net (code "48") (name "+3V(48)") (class "Default")
      (node (ref "F31") (pin "V1") (pinfunction "P$1_V1") (pintype "passive"))
      (node (ref "F32") (pin "B1") (pinfunction "IN2_B1") (pintype "input"))
      (node (ref "F32") (pin "E2") (pinfunction "IN2_E2") (pintype "input"))
      (node (ref "F32") (pin "H1") (pinfunction "IN1_H1") (pintype "input"))
      (node (ref "F32") (pin "M2") (pinfunction "IN2_M2") (pintype "input"))
      (node (ref "F32") (pin "P2") (pinfunction "IN1_P2") (pintype "input"))
      (node (ref "F32") (pin "R1") (pinfunction "IN2_R1") (pintype "input"))
      (node (ref "F32") (pin "T2") (pinfunction "IN1_T2") (pintype "input"))
      (node (ref "F33") (pin "C1") (pinfunction "IN1C_C1") (pintype "input"))
      (node (ref "F33") (pin "D2") (pinfunction "IN1A_D2") (pintype "input"))
      (node (ref "F33") (pin "P1") (pinfunction "IN5C_P1") (pintype "input"))
    )
    (net (code "49") (name "+3V(49)") (class "Default")
      (node (ref "EF10") (pin "BF2") (pinfunction "P$1_BF2") (pintype "passive"))
      (node (ref "H07") (pin "F2") (pinfunction "IN1_F2") (pintype "input"))
      (node (ref "H07") (pin "J2") (pinfunction "IN3_J2") (pintype "input"))
      (node (ref "H07") (pin "M2") (pinfunction "IN1_M2") (pintype "input"))
      (node (ref "H07") (pin "P2") (pinfunction "IN3_P2") (pintype "input"))
      (node (ref "H07") (pin "T2") (pinfunction "IN1_T2") (pintype "input"))
      (node (ref "H07") (pin "V2") (pinfunction "IN3_V2") (pintype "input"))
      (node (ref "H08") (pin "F2") (pinfunction "IN1_F2") (pintype "input"))
      (node (ref "H08") (pin "J2") (pinfunction "IN3_J2") (pintype "input"))
      (node (ref "H08") (pin "M2") (pinfunction "IN1_M2") (pintype "input"))
      (node (ref "H08") (pin "P2") (pinfunction "IN3_P2") (pintype "input"))
      (node (ref "H08") (pin "T2") (pinfunction "IN1_T2") (pintype "input"))
      (node (ref "H08") (pin "V2") (pinfunction "IN3_V2") (pintype "input"))
    )
    (net (code "50") (name "+3V(50)") (class "Default")
      (node (ref "F11") (pin "V1") (pinfunction "P$1_V1") (pintype "passive"))
      (node (ref "H09") (pin "F2") (pinfunction "IN1_F2") (pintype "input"))
      (node (ref "H09") (pin "J2") (pinfunction "IN3_J2") (pintype "input"))
      (node (ref "H09") (pin "M2") (pinfunction "IN1_M2") (pintype "input"))
      (node (ref "H09") (pin "P2") (pinfunction "IN3_P2") (pintype "input"))
      (node (ref "H09") (pin "T2") (pinfunction "IN1_T2") (pintype "input"))
      (node (ref "H09") (pin "V2") (pinfunction "IN3_V2") (pintype "input"))
      (node (ref "H10") (pin "F2") (pinfunction "IN1_F2") (pintype "input"))
      (node (ref "H10") (pin "J2") (pinfunction "IN3_J2") (pintype "input"))
      (node (ref "H10") (pin "M2") (pinfunction "IN1_M2") (pintype "input"))
      (node (ref "H10") (pin "P2") (pinfunction "IN3_P2") (pintype "input"))
      (node (ref "H10") (pin "T2") (pinfunction "IN1_T2") (pintype "input"))
      (node (ref "H10") (pin "V2") (pinfunction "IN3_V2") (pintype "input"))
    )
    (net (code "51") (name "+3V(51)") (class "Default")
      (node (ref "F20") (pin "V1") (pinfunction "P$1_V1") (pintype "passive"))
      (node (ref "H11") (pin "F2") (pinfunction "IN1_F2") (pintype "input"))
      (node (ref "H11") (pin "J2") (pinfunction "IN3_J2") (pintype "input"))
      (node (ref "H11") (pin "M2") (pinfunction "IN1_M2") (pintype "input"))
      (node (ref "H11") (pin "P2") (pinfunction "IN3_P2") (pintype "input"))
      (node (ref "H11") (pin "T2") (pinfunction "IN1_T2") (pintype "input"))
      (node (ref "H11") (pin "V2") (pinfunction "IN3_V2") (pintype "input"))
      (node (ref "H12") (pin "F2") (pinfunction "IN1_F2") (pintype "input"))
      (node (ref "H12") (pin "J2") (pinfunction "IN3_J2") (pintype "input"))
      (node (ref "H12") (pin "M2") (pinfunction "IN1_M2") (pintype "input"))
      (node (ref "H12") (pin "P2") (pinfunction "IN3_P2") (pintype "input"))
      (node (ref "H12") (pin "T2") (pinfunction "IN1_T2") (pintype "input"))
      (node (ref "H12") (pin "V2") (pinfunction "IN3_V2") (pintype "input"))
    )
    (net (code "52") (name "+3V(52)") (class "Default")
      (node (ref "F21") (pin "U1") (pinfunction "P$1_U1") (pintype "passive"))
      (node (ref "H13") (pin "F2") (pinfunction "IN1_F2") (pintype "input"))
      (node (ref "H13") (pin "J2") (pinfunction "IN3_J2") (pintype "input"))
      (node (ref "H13") (pin "M2") (pinfunction "IN1_M2") (pintype "input"))
      (node (ref "H13") (pin "P2") (pinfunction "IN3_P2") (pintype "input"))
      (node (ref "H13") (pin "T2") (pinfunction "IN1_T2") (pintype "input"))
      (node (ref "H13") (pin "V2") (pinfunction "IN3_V2") (pintype "input"))
      (node (ref "H14") (pin "F2") (pinfunction "IN1_F2") (pintype "input"))
      (node (ref "H14") (pin "J2") (pinfunction "IN3_J2") (pintype "input"))
      (node (ref "H14") (pin "M2") (pinfunction "IN1_M2") (pintype "input"))
      (node (ref "H14") (pin "P2") (pinfunction "IN3_P2") (pintype "input"))
      (node (ref "H14") (pin "T2") (pinfunction "IN1_T2") (pintype "input"))
      (node (ref "H14") (pin "V2") (pinfunction "IN3_V2") (pintype "input"))
      (node (ref "J13") (pin "R1") (pinfunction "IN4_R1") (pintype "input"))
    )
    (net (code "53") (name "+3V(53)") (class "Default")
      (node (ref "F21") (pin "V1") (pinfunction "P$1_V1") (pintype "passive"))
      (node (ref "H15") (pin "F2") (pinfunction "IN1_F2") (pintype "input"))
      (node (ref "H15") (pin "J2") (pinfunction "IN3_J2") (pintype "input"))
      (node (ref "H15") (pin "M2") (pinfunction "IN1_M2") (pintype "input"))
      (node (ref "H15") (pin "P2") (pinfunction "IN3_P2") (pintype "input"))
      (node (ref "H15") (pin "T2") (pinfunction "IN1_T2") (pintype "input"))
      (node (ref "H15") (pin "V2") (pinfunction "IN3_V2") (pintype "input"))
      (node (ref "H16") (pin "F2") (pinfunction "IN1_F2") (pintype "input"))
      (node (ref "H16") (pin "J2") (pinfunction "IN3_J2") (pintype "input"))
      (node (ref "H16") (pin "M2") (pinfunction "IN1_M2") (pintype "input"))
      (node (ref "H16") (pin "P2") (pinfunction "IN3_P2") (pintype "input"))
      (node (ref "H16") (pin "T2") (pinfunction "IN1_T2") (pintype "input"))
      (node (ref "H16") (pin "V2") (pinfunction "IN3_V2") (pintype "input"))
    )
    (net (code "54") (name "+3V(54)") (class "Default")
      (node (ref "F22") (pin "V1") (pinfunction "P$1_V1") (pintype "passive"))
      (node (ref "H17") (pin "F2") (pinfunction "IN1_F2") (pintype "input"))
      (node (ref "H17") (pin "J2") (pinfunction "IN3_J2") (pintype "input"))
      (node (ref "H17") (pin "M2") (pinfunction "IN1_M2") (pintype "input"))
      (node (ref "H17") (pin "P2") (pinfunction "IN3_P2") (pintype "input"))
      (node (ref "H17") (pin "T2") (pinfunction "IN1_T2") (pintype "input"))
      (node (ref "H17") (pin "V2") (pinfunction "IN3_V2") (pintype "input"))
      (node (ref "H18") (pin "F2") (pinfunction "IN1_F2") (pintype "input"))
      (node (ref "H18") (pin "J2") (pinfunction "IN3_J2") (pintype "input"))
      (node (ref "H18") (pin "M2") (pinfunction "IN1_M2") (pintype "input"))
      (node (ref "H18") (pin "P2") (pinfunction "IN3_P2") (pintype "input"))
      (node (ref "H18") (pin "T2") (pinfunction "IN1_T2") (pintype "input"))
      (node (ref "H18") (pin "V2") (pinfunction "IN3_V2") (pintype "input"))
    )
    (net (code "55") (name "+3V(55)") (class "Default")
      (node (ref "E22") (pin "B1") (pinfunction "IN2_B1") (pintype "input"))
      (node (ref "E22") (pin "E1") (pinfunction "IN2_E1") (pintype "input"))
      (node (ref "E22") (pin "E2") (pinfunction "IN2_E2") (pintype "input"))
      (node (ref "E22") (pin "J1") (pinfunction "IN2_J1") (pintype "input"))
      (node (ref "E22") (pin "J2") (pinfunction "IN2_J2") (pintype "input"))
      (node (ref "F23") (pin "U1") (pinfunction "P$1_U1") (pintype "passive"))
      (node (ref "H19") (pin "F2") (pinfunction "IN1_F2") (pintype "input"))
      (node (ref "H19") (pin "J2") (pinfunction "IN3_J2") (pintype "input"))
      (node (ref "H19") (pin "M2") (pinfunction "IN1_M2") (pintype "input"))
      (node (ref "H19") (pin "P2") (pinfunction "IN3_P2") (pintype "input"))
      (node (ref "H19") (pin "T2") (pinfunction "IN1_T2") (pintype "input"))
      (node (ref "H19") (pin "V2") (pinfunction "IN3_V2") (pintype "input"))
      (node (ref "H20") (pin "F2") (pinfunction "IN1_F2") (pintype "input"))
      (node (ref "H20") (pin "J2") (pinfunction "IN3_J2") (pintype "input"))
      (node (ref "H20") (pin "M2") (pinfunction "IN1_M2") (pintype "input"))
      (node (ref "H20") (pin "P2") (pinfunction "IN3_P2") (pintype "input"))
    )
    (net (code "56") (name "+3V(56)") (class "Default")
      (node (ref "F23") (pin "V1") (pinfunction "P$1_V1") (pintype "passive"))
      (node (ref "J13") (pin "C1") (pinfunction "IN3_C1") (pintype "input"))
      (node (ref "J13") (pin "D1") (pinfunction "IN4_D1") (pintype "input"))
      (node (ref "J13") (pin "F2") (pinfunction "IN3_F2") (pintype "input"))
      (node (ref "J13") (pin "H2") (pinfunction "IN4_H2") (pintype "input"))
      (node (ref "J13") (pin "J1") (pinfunction "IN3_J1") (pintype "input"))
      (node (ref "J13") (pin "K1") (pinfunction "IN4_K1") (pintype "input"))
      (node (ref "J13") (pin "M2") (pinfunction "IN3_M2") (pintype "input"))
      (node (ref "J13") (pin "N2") (pinfunction "IN4_N2") (pintype "input"))
    )
    (net (code "57") (name "+3V(57)") (class "Default")
      (node (ref "C07") (pin "F2") (pinfunction "IN3_F2") (pintype "input"))
      (node (ref "C07") (pin "H2") (pinfunction "IN2_H2") (pintype "input"))
      (node (ref "C07") (pin "N2") (pinfunction "IN2_N2") (pintype "input"))
      (node (ref "C07") (pin "P2") (pinfunction "IN3_P2") (pintype "input"))
      (node (ref "C08") (pin "H2") (pinfunction "IN1_H2") (pintype "input"))
      (node (ref "C08") (pin "N2") (pinfunction "IN1_N2") (pintype "input"))
      (node (ref "C08") (pin "U2") (pinfunction "IN1_U2") (pintype "input"))
      (node (ref "C09") (pin "E1") (pinfunction "IN2_E1") (pintype "input"))
      (node (ref "C09") (pin "J1") (pinfunction "IN2_J1") (pintype "input"))
      (node (ref "C09") (pin "M1") (pinfunction "IN2_M1") (pintype "input"))
      (node (ref "C09") (pin "M2") (pinfunction "IN2_M2") (pintype "input"))
      (node (ref "C09") (pin "R1") (pinfunction "IN2_R1") (pintype "input"))
      (node (ref "C09") (pin "R2") (pinfunction "IN2_R2") (pintype "input"))
      (node (ref "D10") (pin "V1") (pinfunction "P$1_V1") (pintype "passive"))
      (node (ref "D11") (pin "K2") (pinfunction "R_K2") (pintype "input"))
      (node (ref "D11") (pin "N2") (pinfunction "S_N2") (pintype "input"))
    )
    (net (code "58") (name "+3V(58)") (class "Default")
      (node (ref "D07") (pin "E2") (pinfunction "IN2_E2") (pintype "input"))
      (node (ref "D07") (pin "H1") (pinfunction "IN1_H1") (pintype "input"))
      (node (ref "D07") (pin "H2") (pinfunction "IN1_H2") (pintype "input"))
      (node (ref "D07") (pin "L2") (pinfunction "IN1_L2") (pintype "input"))
      (node (ref "D07") (pin "P1") (pinfunction "IN1_P1") (pintype "input"))
      (node (ref "D07") (pin "P2") (pinfunction "IN1_P2") (pintype "input"))
      (node (ref "D07") (pin "U1") (pinfunction "P$1_U1") (pintype "passive"))
      (node (ref "D09") (pin "H1") (pinfunction "IN3_H1") (pintype "input"))
      (node (ref "D09") (pin "R1") (pinfunction "IN2_R1") (pintype "input"))
      (node (ref "D09") (pin "V2") (pinfunction "IN3_V2") (pintype "input"))
      (node (ref "D10") (pin "E2") (pinfunction "IN2_E2") (pintype "input"))
      (node (ref "E09") (pin "L2") (pinfunction "IN1_L2") (pintype "input"))
      (node (ref "E09") (pin "P1") (pinfunction "IN1_P1") (pintype "input"))
      (node (ref "E09") (pin "P2") (pinfunction "IN1_P2") (pintype "input"))
    )
    (net (code "59") (name "+3V(61)") (class "Default")
      (node (ref "C12") (pin "B1") (pinfunction "IN2_B1") (pintype "input"))
      (node (ref "C12") (pin "C1") (pinfunction "IN3_C1") (pintype "input"))
      (node (ref "C12") (pin "D1") (pinfunction "IN4_D1") (pintype "input"))
      (node (ref "C12") (pin "J1") (pinfunction "IN3_J1") (pintype "input"))
      (node (ref "C12") (pin "K1") (pinfunction "IN4_K1") (pintype "input"))
      (node (ref "C12") (pin "N2") (pinfunction "IN4_N2") (pintype "input"))
      (node (ref "C12") (pin "U1") (pinfunction "P$1_U1") (pintype "passive"))
    )
    (net (code "60") (name "+3V(62)") (class "Default")
      (node (ref "A05") (pin "U1") (pinfunction "P$1_U1") (pintype "passive"))
      (node (ref "B06") (pin "J2") (pinfunction "IN2_J2") (pintype "input"))
    )
    (net (code "61") (name "+3V(63)") (class "Default")
      (node (ref "B05") (pin "R1") (pinfunction "S_R1") (pintype "input"))
      (node (ref "B06") (pin "U2") (pinfunction "IN2_U2") (pintype "input"))
      (node (ref "B06") (pin "V1") (pinfunction "P$1_V1") (pintype "passive"))
    )
    (net (code "62") (name "+3V(64)") (class "Default")
      (node (ref "B04") (pin "F2") (pinfunction "IN3_F2") (pintype "input"))
      (node (ref "B05") (pin "D1") (pinfunction "S_D1") (pintype "input"))
      (node (ref "B06") (pin "U1") (pinfunction "P$1_U1") (pintype "passive"))
    )
    (net (code "63") (name "+3V(65)") (class "Default")
      (node (ref "A05") (pin "D1") (pinfunction "IN1_D1") (pintype "input"))
      (node (ref "A06") (pin "D2") (pinfunction "IN1_D2") (pintype "input"))
      (node (ref "A06") (pin "E1") (pinfunction "IN2_E1") (pintype "input"))
      (node (ref "A06") (pin "U1") (pinfunction "P$1_U1") (pintype "passive"))
      (node (ref "B05") (pin "F2") (pinfunction "S_F2") (pintype "input"))
      (node (ref "B05") (pin "N2") (pinfunction "S_N2") (pintype "input"))
    )
    (net (code "64") (name "+3V(66)") (class "Default")
      (node (ref "A05") (pin "T2") (pinfunction "IN1_T2") (pintype "input"))
      (node (ref "A06") (pin "R2") (pinfunction "IN2_R2") (pintype "input"))
      (node (ref "A11") (pin "U1") (pinfunction "P$1_U1") (pintype "passive"))
    )
    (net (code "65") (name "+3V(67)") (class "Default")
      (node (ref "A06") (pin "M1") (pinfunction "IN2_M1") (pintype "input"))
      (node (ref "A06") (pin "M2") (pinfunction "IN2_M2") (pintype "input"))
      (node (ref "A06") (pin "V1") (pinfunction "P$1_V1") (pintype "passive"))
      (node (ref "B04") (pin "V2") (pinfunction "IN3_V2") (pintype "input"))
    )
    (net (code "66") (name "+3V(68)") (class "Default")
      (node (ref "F08") (pin "P2") (pinfunction "IN2_P2") (pintype "input"))
      (node (ref "F09") (pin "H2") (pinfunction "IN8_H2") (pintype "input"))
      (node (ref "F09") (pin "U1") (pinfunction "P$1_U1") (pintype "passive"))
    )
    (net (code "67") (name "+3V(69)") (class "Default")
      (node (ref "E11") (pin "R1") (pinfunction "IN2_R1") (pintype "input"))
      (node (ref "F09") (pin "F1") (pinfunction "IN1_F1") (pintype "input"))
      (node (ref "F09") (pin "H1") (pinfunction "IN2_H1") (pintype "input"))
      (node (ref "F09") (pin "J1") (pinfunction "IN3_J1") (pintype "input"))
      (node (ref "F11") (pin "F1") (pinfunction "IN1_F1") (pintype "input"))
      (node (ref "F11") (pin "R1") (pinfunction "IN4_R1") (pintype "input"))
      (node (ref "F11") (pin "S2") (pinfunction "IN2_S2") (pintype "input"))
      (node (ref "F11") (pin "U1") (pinfunction "P$1_U1") (pintype "passive"))
    )
    (net (code "68") (name "+3VC01") (class "Default")
      (node (ref "C01") (pin "V2") (pinfunction "P$2_V2") (pintype "bidirectional"))
      (node (ref "HJ28") (pin "BU2") (pinfunction "P$1_BU2") (pintype "passive"))
    )
    (net (code "69") (name "-6V") (class "Default")
      (node (ref "A25") (pin "E2") (pinfunction "P$2_E2") (pintype "passive"))
      (node (ref "A26") (pin "E2") (pinfunction "P$2_E2") (pintype "passive"))
      (node (ref "A27") (pin "K1") (pinfunction "K1_K1") (pintype "passive"))
      (node (ref "A27") (pin "L2") (pinfunction "L2_L2") (pintype "passive"))
      (node (ref "A27") (pin "S1") (pinfunction "S1_S1") (pintype "passive"))
      (node (ref "A27") (pin "U2") (pinfunction "U2_U2") (pintype "passive"))
      (node (ref "A36") (pin "K1") (pinfunction "K1_K1") (pintype "passive"))
      (node (ref "A36") (pin "L2") (pinfunction "L2_L2") (pintype "passive"))
      (node (ref "A36") (pin "S1") (pinfunction "S1_S1") (pintype "passive"))
      (node (ref "A36") (pin "U2") (pinfunction "U2_U2") (pintype "passive"))
      (node (ref "A37") (pin "L2") (pinfunction "L2_L2") (pintype "passive"))
      (node (ref "A38") (pin "H2") (pinfunction "P$1_H2") (pintype "passive"))
      (node (ref "A38") (pin "J2") (pinfunction "P$3_J2") (pintype "passive"))
      (node (ref "A38") (pin "U2") (pinfunction "P$2_U2") (pintype "passive"))
      (node (ref "A38") (pin "V2") (pinfunction "P$1_V2") (pintype "passive"))
      (node (ref "A39") (pin "E2") (pinfunction "P$2_E2") (pintype "passive"))
      (node (ref "A39") (pin "J2") (pinfunction "P$3_J2") (pintype "passive"))
      (node (ref "A39") (pin "U2") (pinfunction "P$2_U2") (pintype "passive"))
      (node (ref "A39") (pin "V2") (pinfunction "P$1_V2") (pintype "passive"))
      (node (ref "AB01") (pin "BM2") (pinfunction "-6V_BM2") (pintype "power_in"))
      (node (ref "AB01") (pin "BN2") (pinfunction "-6V_BN2") (pintype "power_in"))
      (node (ref "AB01") (pin "BP2") (pinfunction "-6V_BP2") (pintype "power_in"))
      (node (ref "AB01") (pin "BR2") (pinfunction "-6V_BR2") (pintype "power_in"))
      (node (ref "AB01") (pin "BS2") (pinfunction "-6V_BS2") (pintype "power_in"))
      (node (ref "AB01") (pin "BT2") (pinfunction "-6V_BT2") (pintype "power_in"))
      (node (ref "AB01") (pin "BU2") (pinfunction "-6V_BU2") (pintype "power_in"))
      (node (ref "AB01") (pin "BV2") (pinfunction "-6V_BV2") (pintype "power_in"))
      (node (ref "AB02") (pin "BM2") (pinfunction "-6V_BM2") (pintype "power_in"))
      (node (ref "B25") (pin "E2") (pinfunction "P$2_E2") (pintype "passive"))
      (node (ref "B26") (pin "K1") (pinfunction "K1_K1") (pintype "passive"))
      (node (ref "B26") (pin "L2") (pinfunction "L2_L2") (pintype "passive"))
      (node (ref "B26") (pin "S1") (pinfunction "S1_S1") (pintype "passive"))
      (node (ref "B26") (pin "U2") (pinfunction "U2_U2") (pintype "passive"))
      (node (ref "B27") (pin "K1") (pinfunction "K1_K1") (pintype "passive"))
      (node (ref "B27") (pin "L2") (pinfunction "L2_L2") (pintype "passive"))
      (node (ref "B27") (pin "S1") (pinfunction "S1_S1") (pintype "passive"))
      (node (ref "B27") (pin "U2") (pinfunction "U2_U2") (pintype "passive"))
      (node (ref "B36") (pin "K1") (pinfunction "K1_K1") (pintype "passive"))
      (node (ref "B36") (pin "L2") (pinfunction "L2_L2") (pintype "passive"))
      (node (ref "B36") (pin "S1") (pinfunction "S1_S1") (pintype "passive"))
      (node (ref "B36") (pin "U2") (pinfunction "U2_U2") (pintype "passive"))
      (node (ref "B37") (pin "K1") (pinfunction "K1_K1") (pintype "passive"))
      (node (ref "B37") (pin "L2") (pinfunction "L2_L2") (pintype "passive"))
      (node (ref "B37") (pin "S1") (pinfunction "S1_S1") (pintype "passive"))
      (node (ref "B37") (pin "U2") (pinfunction "U2_U2") (pintype "passive"))
      (node (ref "B38") (pin "E2") (pinfunction "P$2_E2") (pintype "passive"))
      (node (ref "B38") (pin "V2") (pinfunction "P$1_V2") (pintype "passive"))
      (node (ref "B39") (pin "V2") (pinfunction "P$1_V2") (pintype "passive"))
    )
    (net (code "70") (name "-15V") (class "Default")
      (node (ref "A38") (pin "B2") (pinfunction "P$1_B2") (pintype "passive"))
      (node (ref "A39") (pin "B2") (pinfunction "P$1_B2") (pintype "passive"))
      (node (ref "B38") (pin "B2") (pinfunction "P$1_B2") (pintype "passive"))
      (node (ref "B39") (pin "B2") (pinfunction "P$1_B2") (pintype "passive"))
      (node (ref "D01") (pin "B2") (pinfunction "P$2_B2") (pintype "bidirectional"))
      (node (ref "D03") (pin "B2") (pinfunction "P$2_B2") (pintype "bidirectional"))
    )
    (net (code "71") (name "-30V") (class "Default")
      (node (ref "A27") (pin "V2") (pinfunction "V2_V2") (pintype "input"))
      (node (ref "A36") (pin "V2") (pinfunction "V2_V2") (pintype "input"))
      (node (ref "A37") (pin "V2") (pinfunction "V2_V2") (pintype "input"))
      (node (ref "A39") (pin "H2") (pinfunction "P$1_H2") (pintype "passive"))
      (node (ref "A39") (pin "M2") (pinfunction "P$1_M2") (pintype "passive"))
      (node (ref "AB01") (pin "AE2") (pinfunction "-30V_AE2") (pintype "power_in"))
      (node (ref "AB01") (pin "AF2") (pinfunction "-30V_AF2") (pintype "power_in"))
      (node (ref "AB01") (pin "AH2") (pinfunction "-30V_AH2") (pintype "power_in"))
      (node (ref "AB01") (pin "AJ2") (pinfunction "-30V_AJ2") (pintype "power_in"))
      (node (ref "AB01") (pin "AK2") (pinfunction "-30V_AK2") (pintype "power_in"))
      (node (ref "AB01") (pin "AL2") (pinfunction "-30V_AL2") (pintype "power_in"))
      (node (ref "AB01") (pin "AM2") (pinfunction "-30V_AM2") (pintype "power_in"))
      (node (ref "AB01") (pin "AN2") (pinfunction "-30V_AN2") (pintype "power_in"))
      (node (ref "AB02") (pin "BV2") (pinfunction "-30V_BV2") (pintype "power_in"))
      (node (ref "B26") (pin "V2") (pinfunction "V2_V2") (pintype "input"))
      (node (ref "B27") (pin "V2") (pinfunction "V2_V2") (pintype "input"))
      (node (ref "B36") (pin "V2") (pinfunction "V2_V2") (pintype "input"))
      (node (ref "B37") (pin "V2") (pinfunction "V2_V2") (pintype "input"))
      (node (ref "B38") (pin "H2") (pinfunction "P$1_H2") (pintype "passive"))
      (node (ref "B38") (pin "J2") (pinfunction "P$3_J2") (pintype "passive"))
      (node (ref "B38") (pin "U2") (pinfunction "P$2_U2") (pintype "passive"))
      (node (ref "B39") (pin "H2") (pinfunction "P$1_H2") (pintype "passive"))
      (node (ref "B39") (pin "J2") (pinfunction "P$3_J2") (pintype "passive"))
      (node (ref "B39") (pin "U2") (pinfunction "P$2_U2") (pintype "passive"))
      (node (ref "HJ23") (pin "AV2") (pinfunction "-30V_AV2") (pintype "power_in"))
      (node (ref "J12") (pin "V2") (pinfunction "-30V_V2") (pintype "power_in"))
    )
    (net (code "72") (name "0_TO_INT_ENAB_") (class "Default")
      (node (ref "E26") (pin "V2") (pinfunction "OUT_V2") (pintype "output"))
      (node (ref "E33") (pin "R1") (pinfunction "S_R1") (pintype "input"))
    )
    (net (code "73") (name "3_CYCLE") (class "Default")
      (node (ref "F22") (pin "T2") (pinfunction "IN1_T2") (pintype "input"))
      (node (ref "J20") (pin "J2") (pinfunction "OUT_J2") (pintype "output"))
    )
    (net (code "74") (name "60HZ_IN") (class "Default")
      (node (ref "J30") (pin "R2") (pinfunction "R2_R2") (pintype "input"))
    )
    (net (code "75") (name "AC00") (class "Default")
      (node (ref "C14") (pin "E1") (pinfunction "IN2_E1") (pintype "input"))
      (node (ref "D15") (pin "E1") (pinfunction "IN2_E1") (pintype "input"))
      (node (ref "D18") (pin "J2") (pinfunction "IN1_J2") (pintype "input"))
      (node (ref "E24") (pin "L1") (pinfunction "IN1_L1") (pintype "input"))
      (node (ref "EF34") (pin "BA1") (pinfunction "BA1_BA1") (pintype "output"))
      (node (ref "F33") (pin "N2") (pinfunction "IN4A_N2") (pintype "input"))
      (node (ref "H07") (pin "H2") (pinfunction "IN2_H2") (pintype "input"))
      (node (ref "HJ31") (pin "AE1") (pinfunction "AE1_AE1") (pintype "input"))
    )
    (net (code "76") (name "AC00_") (class "Default")
      (node (ref "D15") (pin "A1") (pinfunction "IN1_A1") (pintype "input"))
      (node (ref "E40") (pin "V2") (pinfunction "P$2_V2") (pintype "bidirectional"))
      (node (ref "EF34") (pin "BB1") (pinfunction "BB1_BB1") (pintype "output"))
      (node (ref "F24") (pin "K2") (pinfunction "IN1_K2") (pintype "input"))
    )
    (net (code "77") (name "AC01") (class "Default")
      (node (ref "C14") (pin "J2") (pinfunction "IN2_J2") (pintype "input"))
      (node (ref "D14") (pin "L1") (pinfunction "IN1_L1") (pintype "input"))
      (node (ref "D15") (pin "B1") (pinfunction "IN2_B1") (pintype "input"))
      (node (ref "EF34") (pin "AV1") (pinfunction "AV1_AV1") (pintype "output"))
      (node (ref "H07") (pin "N2") (pinfunction "IN2_N2") (pintype "input"))
      (node (ref "HJ31") (pin "BA1") (pinfunction "BA1_BA1") (pintype "input"))
    )
    (net (code "78") (name "AC01_") (class "Default")
      (node (ref "D15") (pin "D1") (pinfunction "IN1_D1") (pintype "input"))
      (node (ref "D16") (pin "H2") (pinfunction "IN1_H2") (pintype "input"))
      (node (ref "E40") (pin "T2") (pinfunction "P$2_T2") (pintype "bidirectional"))
      (node (ref "EF34") (pin "AV2") (pinfunction "AV2_AV2") (pintype "output"))
      (node (ref "F24") (pin "L2") (pinfunction "IN2_L2") (pintype "input"))
    )
    (net (code "79") (name "AC02") (class "Default")
      (node (ref "C14") (pin "R1") (pinfunction "IN2_R1") (pintype "input"))
      (node (ref "D16") (pin "J2") (pinfunction "IN2_J2") (pintype "input"))
      (node (ref "EF35") (pin "BA1") (pinfunction "BA1_BA1") (pintype "output"))
      (node (ref "H07") (pin "U2") (pinfunction "IN2_U2") (pintype "input"))
      (node (ref "HJ24") (pin "AE2") (pinfunction "AE2_AE2") (pintype "input"))
      (node (ref "HJ25") (pin "AE2") (pinfunction "AE2_AE2") (pintype "input"))
      (node (ref "HJ31") (pin "AV1") (pinfunction "AV1_AV1") (pintype "input"))
    )
    (net (code "80") (name "AC02_") (class "Default")
      (node (ref "D14") (pin "M1") (pinfunction "IN2_M1") (pintype "input"))
      (node (ref "D20") (pin "D1") (pinfunction "IN4_D1") (pintype "input"))
      (node (ref "E40") (pin "J1") (pinfunction "P$2_J1") (pintype "bidirectional"))
      (node (ref "EF35") (pin "BB1") (pinfunction "BB1_BB1") (pintype "output"))
      (node (ref "F24") (pin "M2") (pinfunction "IN3_M2") (pintype "input"))
    )
    (net (code "81") (name "AC03") (class "Default")
      (node (ref "C15") (pin "E1") (pinfunction "IN2_E1") (pintype "input"))
      (node (ref "EF35") (pin "AV1") (pinfunction "AV1_AV1") (pintype "output"))
      (node (ref "H08") (pin "H2") (pinfunction "IN2_H2") (pintype "input"))
      (node (ref "HJ24") (pin "AF2") (pinfunction "AF2_AF2") (pintype "input"))
      (node (ref "HJ25") (pin "AF2") (pinfunction "AF2_AF2") (pintype "input"))
      (node (ref "HJ31") (pin "AH1") (pinfunction "AH1_AH1") (pintype "input"))
    )
    (net (code "82") (name "AC03_") (class "Default")
      (node (ref "D19") (pin "K1") (pinfunction "IN1_K1") (pintype "input"))
      (node (ref "D20") (pin "C1") (pinfunction "IN3_C1") (pintype "input"))
      (node (ref "E40") (pin "H2") (pinfunction "P$2_H2") (pintype "bidirectional"))
      (node (ref "EF35") (pin "AV2") (pinfunction "AV2_AV2") (pintype "output"))
      (node (ref "F24") (pin "N2") (pinfunction "IN4_N2") (pintype "input"))
    )
    (net (code "83") (name "AC04") (class "Default")
      (node (ref "C15") (pin "J2") (pinfunction "IN2_J2") (pintype "input"))
      (node (ref "EF02") (pin "AP2") (pinfunction "AP2_AP2") (pintype "input"))
      (node (ref "EF36") (pin "BA1") (pinfunction "BA1_BA1") (pintype "output"))
      (node (ref "H08") (pin "N2") (pinfunction "IN2_N2") (pintype "input"))
      (node (ref "HJ24") (pin "AM2") (pinfunction "AM2_AM2") (pintype "input"))
      (node (ref "HJ25") (pin "AM2") (pinfunction "AM2_AM2") (pintype "input"))
      (node (ref "HJ28") (pin "AH1") (pinfunction "AH1_AH1") (pintype "input"))
      (node (ref "HJ31") (pin "AU2") (pinfunction "AU2_AU2") (pintype "input"))
    )
    (net (code "84") (name "AC04_") (class "Default")
      (node (ref "E40") (pin "M1") (pinfunction "P$2_M1") (pintype "bidirectional"))
      (node (ref "EF36") (pin "BB1") (pinfunction "BB1_BB1") (pintype "output"))
      (node (ref "F24") (pin "M1") (pinfunction "IN1_M1") (pintype "input"))
    )
    (net (code "85") (name "AC05") (class "Default")
      (node (ref "C15") (pin "R1") (pinfunction "IN2_R1") (pintype "input"))
      (node (ref "EF02") (pin "AR2") (pinfunction "AR2_AR2") (pintype "input"))
      (node (ref "EF36") (pin "AV1") (pinfunction "AV1_AV1") (pintype "output"))
      (node (ref "H08") (pin "U2") (pinfunction "IN2_U2") (pintype "input"))
      (node (ref "HJ24") (pin "AN2") (pinfunction "AN2_AN2") (pintype "input"))
      (node (ref "HJ25") (pin "AN2") (pinfunction "AN2_AN2") (pintype "input"))
      (node (ref "HJ28") (pin "AH2") (pinfunction "AH2_AH2") (pintype "input"))
      (node (ref "HJ31") (pin "AK1") (pinfunction "AK1_AK1") (pintype "input"))
    )
    (net (code "86") (name "AC05_") (class "Default")
      (node (ref "E40") (pin "B1") (pinfunction "P$2_B1") (pintype "bidirectional"))
      (node (ref "EF36") (pin "AV2") (pinfunction "AV2_AV2") (pintype "output"))
      (node (ref "F24") (pin "N1") (pinfunction "IN2_N1") (pintype "input"))
    )
    (net (code "87") (name "AC06") (class "Default")
      (node (ref "C16") (pin "E1") (pinfunction "IN2_E1") (pintype "input"))
      (node (ref "EF02") (pin "AL2") (pinfunction "AL2_AL2") (pintype "input"))
      (node (ref "EF37") (pin "BA1") (pinfunction "BA1_BA1") (pintype "output"))
      (node (ref "H09") (pin "H2") (pinfunction "IN2_H2") (pintype "input"))
      (node (ref "HJ24") (pin "AS2") (pinfunction "AS2_AS2") (pintype "input"))
      (node (ref "HJ25") (pin "AS2") (pinfunction "AS2_AS2") (pintype "input"))
      (node (ref "HJ28") (pin "AF1") (pinfunction "AF1_AF1") (pintype "input"))
      (node (ref "HJ31") (pin "AT2") (pinfunction "AT2_AT2") (pintype "input"))
    )
    (net (code "88") (name "AC06_") (class "Default")
      (node (ref "EF37") (pin "BB1") (pinfunction "BB1_BB1") (pintype "output"))
      (node (ref "F24") (pin "P1") (pinfunction "IN3_P1") (pintype "input"))
      (node (ref "F40") (pin "V2") (pinfunction "P$2_V2") (pintype "bidirectional"))
    )
    (net (code "89") (name "AC07") (class "Default")
      (node (ref "C16") (pin "J2") (pinfunction "IN2_J2") (pintype "input"))
      (node (ref "EF02") (pin "AM2") (pinfunction "AM2_AM2") (pintype "input"))
      (node (ref "EF37") (pin "AV1") (pinfunction "AV1_AV1") (pintype "output"))
      (node (ref "H09") (pin "N2") (pinfunction "IN2_N2") (pintype "input"))
      (node (ref "HJ24") (pin "AT2") (pinfunction "AT2_AT2") (pintype "input"))
      (node (ref "HJ25") (pin "AT2") (pinfunction "AT2_AT2") (pintype "input"))
      (node (ref "HJ28") (pin "AF2") (pinfunction "AF2_AF2") (pintype "input"))
      (node (ref "HJ31") (pin "AL1") (pinfunction "AL1_AL1") (pintype "input"))
    )
    (net (code "90") (name "AC07_") (class "Default")
      (node (ref "EF37") (pin "AV2") (pinfunction "AV2_AV2") (pintype "output"))
      (node (ref "F24") (pin "R1") (pinfunction "IN4_R1") (pintype "input"))
      (node (ref "F40") (pin "T2") (pinfunction "P$2_T2") (pintype "bidirectional"))
    )
    (net (code "91") (name "AC08") (class "Default")
      (node (ref "C16") (pin "R1") (pinfunction "IN2_R1") (pintype "input"))
      (node (ref "EF02") (pin "AU2") (pinfunction "AU2_AU2") (pintype "input"))
      (node (ref "EF38") (pin "BA1") (pinfunction "BA1_BA1") (pintype "output"))
      (node (ref "H09") (pin "U2") (pinfunction "IN2_U2") (pintype "input"))
      (node (ref "HJ24") (pin "BD2") (pinfunction "BD2_BD2") (pintype "input"))
      (node (ref "HJ25") (pin "BD2") (pinfunction "BD2_BD2") (pintype "input"))
      (node (ref "HJ28") (pin "AE1") (pinfunction "AE1_AE1") (pintype "input"))
      (node (ref "HJ31") (pin "AR1") (pinfunction "AR1_AR1") (pintype "input"))
    )
    (net (code "92") (name "AC08_") (class "Default")
      (node (ref "EF38") (pin "BB1") (pinfunction "BB1_BB1") (pintype "output"))
      (node (ref "F24") (pin "R2") (pinfunction "IN1_R2") (pintype "input"))
      (node (ref "F40") (pin "J1") (pinfunction "P$2_J1") (pintype "bidirectional"))
    )
    (net (code "93") (name "AC09") (class "Default")
      (node (ref "C17") (pin "E1") (pinfunction "IN2_E1") (pintype "input"))
      (node (ref "EF02") (pin "AS2") (pinfunction "AS2_AS2") (pintype "input"))
      (node (ref "EF38") (pin "AV1") (pinfunction "AV1_AV1") (pintype "output"))
      (node (ref "H10") (pin "H2") (pinfunction "IN2_H2") (pintype "input"))
      (node (ref "HJ24") (pin "BE2") (pinfunction "BE2_BE2") (pintype "input"))
      (node (ref "HJ25") (pin "BE2") (pinfunction "BE2_BE2") (pintype "input"))
      (node (ref "HJ28") (pin "AE2") (pinfunction "AE2_AE2") (pintype "input"))
      (node (ref "HJ31") (pin "AN2") (pinfunction "AN2_AN2") (pintype "input"))
    )
    (net (code "94") (name "AC09_") (class "Default")
      (node (ref "EF38") (pin "AV2") (pinfunction "AV2_AV2") (pintype "output"))
      (node (ref "F24") (pin "S2") (pinfunction "IN2_S2") (pintype "input"))
      (node (ref "F40") (pin "H2") (pinfunction "P$2_H2") (pintype "bidirectional"))
    )
    (net (code "95") (name "AC10") (class "Default")
      (node (ref "C17") (pin "J2") (pinfunction "IN2_J2") (pintype "input"))
      (node (ref "EF02") (pin "AT2") (pinfunction "AT2_AT2") (pintype "input"))
      (node (ref "EF39") (pin "BA1") (pinfunction "BA1_BA1") (pintype "output"))
      (node (ref "H10") (pin "N2") (pinfunction "IN2_N2") (pintype "input"))
      (node (ref "HJ24") (pin "BH2") (pinfunction "BH2_BH2") (pintype "input"))
      (node (ref "HJ25") (pin "BH2") (pinfunction "BH2_BH2") (pintype "input"))
      (node (ref "HJ28") (pin "AD1") (pinfunction "AD1_AD1") (pintype "input"))
      (node (ref "HJ31") (pin "AR2") (pinfunction "AR2_AR2") (pintype "input"))
    )
    (net (code "96") (name "AC10_") (class "Default")
      (node (ref "EF39") (pin "BB1") (pinfunction "BB1_BB1") (pintype "output"))
      (node (ref "F24") (pin "T2") (pinfunction "IN3_T2") (pintype "input"))
      (node (ref "F40") (pin "M1") (pinfunction "P$2_M1") (pintype "bidirectional"))
    )
    (net (code "97") (name "AC11") (class "Default")
      (node (ref "C17") (pin "R1") (pinfunction "IN2_R1") (pintype "input"))
      (node (ref "EF02") (pin "AU1") (pinfunction "AU1_AU1") (pintype "input"))
      (node (ref "EF39") (pin "AV1") (pinfunction "AV1_AV1") (pintype "output"))
      (node (ref "H10") (pin "U2") (pinfunction "IN2_U2") (pintype "input"))
      (node (ref "HJ24") (pin "BJ2") (pinfunction "BJ2_BJ2") (pintype "input"))
      (node (ref "HJ25") (pin "BJ2") (pinfunction "BJ2_BJ2") (pintype "input"))
      (node (ref "HJ28") (pin "AD2") (pinfunction "AD2_AD2") (pintype "input"))
      (node (ref "HJ31") (pin "AP1") (pinfunction "AP1_AP1") (pintype "input"))
    )
    (net (code "98") (name "AC11_") (class "Default")
      (node (ref "EF39") (pin "AV2") (pinfunction "AV2_AV2") (pintype "output"))
      (node (ref "F24") (pin "U2") (pinfunction "IN4_U2") (pintype "input"))
      (node (ref "F40") (pin "B1") (pinfunction "P$2_B1") (pintype "bidirectional"))
    )
    (net (code "99") (name "ACBAR_ENABLE") (class "Default")
      (node (ref "E32") (pin "V2") (pinfunction "OUT_V2") (pintype "open_collector"))
      (node (ref "EF34") (pin "BJ2") (pinfunction "BJ2_BJ2") (pintype "input"))
      (node (ref "EF35") (pin "BJ2") (pinfunction "BJ2_BJ2") (pintype "input"))
      (node (ref "EF36") (pin "BJ2") (pinfunction "BJ2_BJ2") (pintype "input"))
      (node (ref "EF37") (pin "BJ2") (pinfunction "BJ2_BJ2") (pintype "input"))
      (node (ref "EF38") (pin "BJ2") (pinfunction "BJ2_BJ2") (pintype "input"))
      (node (ref "EF39") (pin "BJ2") (pinfunction "BJ2_BJ2") (pintype "input"))
    )
    (net (code "100") (name "AC_CLEAR") (class "Default")
      (node (ref "F29") (pin "J2") (pinfunction "IN2_J2") (pintype "input"))
      (node (ref "J15") (pin "L1") (pinfunction "OUT_L1") (pintype "output"))
    )
    (net (code "101") (name "AC_CLEAR_") (class "Default")
      (node (ref "E30") (pin "K2") (pinfunction "IN2B_K2") (pintype "input"))
      (node (ref "F29") (pin "K2") (pinfunction "OUT_K2") (pintype "output"))
    )
    (net (code "102") (name "AC_ENABLE") (class "Default")
      (node (ref "E32") (pin "S1") (pinfunction "OUT_S1") (pintype "open_collector"))
      (node (ref "EF34") (pin "BH2") (pinfunction "BH2_BH2") (pintype "input"))
      (node (ref "EF35") (pin "BH2") (pinfunction "BH2_BH2") (pintype "input"))
      (node (ref "EF36") (pin "BH2") (pinfunction "BH2_BH2") (pintype "input"))
      (node (ref "EF37") (pin "BH2") (pinfunction "BH2_BH2") (pintype "input"))
      (node (ref "EF38") (pin "BH2") (pinfunction "BH2_BH2") (pintype "input"))
      (node (ref "EF39") (pin "BH2") (pinfunction "BH2_BH2") (pintype "input"))
    )
    (net (code "103") (name "AC_LOAD") (class "Default")
      (node (ref "E32") (pin "P2") (pinfunction "OUT_P2") (pintype "open_collector"))
      (node (ref "E33") (pin "S2") (pinfunction "C_S2") (pintype "input"))
      (node (ref "EF34") (pin "AU1") (pinfunction "AU1_AU1") (pintype "input"))
      (node (ref "EF35") (pin "AU1") (pinfunction "AU1_AU1") (pintype "input"))
      (node (ref "EF36") (pin "AU1") (pinfunction "AU1_AU1") (pintype "input"))
      (node (ref "EF37") (pin "AU1") (pinfunction "AU1_AU1") (pintype "input"))
      (node (ref "EF38") (pin "AU1") (pinfunction "AU1_AU1") (pintype "input"))
      (node (ref "EF39") (pin "AU1") (pinfunction "AU1_AU1") (pintype "input"))
    )
    (net (code "104") (name "AC_TO_MQ_ENABLE") (class "Default")
      (node (ref "C14") (pin "D1") (pinfunction "IN1_D1") (pintype "input"))
      (node (ref "C14") (pin "H2") (pinfunction "IN1_H2") (pintype "input"))
      (node (ref "C14") (pin "P1") (pinfunction "IN1_P1") (pintype "input"))
      (node (ref "C15") (pin "D1") (pinfunction "IN1_D1") (pintype "input"))
      (node (ref "C15") (pin "H2") (pinfunction "IN1_H2") (pintype "input"))
      (node (ref "C15") (pin "P1") (pinfunction "IN1_P1") (pintype "input"))
      (node (ref "C16") (pin "D1") (pinfunction "IN1_D1") (pintype "input"))
      (node (ref "C16") (pin "H2") (pinfunction "IN1_H2") (pintype "input"))
      (node (ref "C16") (pin "P1") (pinfunction "IN1_P1") (pintype "input"))
      (node (ref "C17") (pin "D1") (pinfunction "IN1_D1") (pintype "input"))
      (node (ref "C17") (pin "H2") (pinfunction "IN1_H2") (pintype "input"))
      (node (ref "C17") (pin "P1") (pinfunction "IN1_P1") (pintype "input"))
      (node (ref "D15") (pin "S1") (pinfunction "OUT_S1") (pintype "output"))
    )
    (net (code "105") (name "AC_TO_MQ_ENABLE_") (class "Default")
      (node (ref "D15") (pin "R1") (pinfunction "IN2_R1") (pintype "input"))
      (node (ref "D21") (pin "L1") (pinfunction "OUT_L1") (pintype "output"))
      (node (ref "E30") (pin "F2") (pinfunction "IN1C_F2") (pintype "input"))
    )
    (net (code "106") (name "ADDER00") (class "Default")
      (node (ref "EF34") (pin "AE2") (pinfunction "AE2_AE2") (pintype "output"))
      (node (ref "EF35") (pin "AB1") (pinfunction "AB1_AB1") (pintype "input"))
      (node (ref "EF39") (pin "AJ2") (pinfunction "AJ2_AJ2") (pintype "input"))
      (node (ref "F33") (pin "K1") (pinfunction "IN4A_K1") (pintype "input"))
    )
    (net (code "107") (name "ADDER01") (class "Default")
      (node (ref "EF34") (pin "AF1") (pinfunction "AF1_AF1") (pintype "output"))
      (node (ref "EF35") (pin "AC1") (pinfunction "AC1_AC1") (pintype "input"))
      (node (ref "F33") (pin "M1") (pinfunction "IN5A_M1") (pintype "input"))
    )
    (net (code "108") (name "ADDER02") (class "Default")
      (node (ref "EF34") (pin "AH2") (pinfunction "AH2_AH2") (pintype "input"))
      (node (ref "EF35") (pin "AE2") (pinfunction "AE2_AE2") (pintype "output"))
      (node (ref "EF35") (pin "BB2") (pinfunction "BB2_BB2") (pintype "input"))
      (node (ref "EF36") (pin "AB1") (pinfunction "AB1_AB1") (pintype "input"))
    )
    (net (code "109") (name "ADDER03") (class "Default")
      (node (ref "EF34") (pin "AJ2") (pinfunction "AJ2_AJ2") (pintype "input"))
      (node (ref "EF35") (pin "AF1") (pinfunction "AF1_AF1") (pintype "output"))
      (node (ref "EF36") (pin "AC1") (pinfunction "AC1_AC1") (pintype "input"))
    )
    (net (code "110") (name "ADDER04") (class "Default")
      (node (ref "EF35") (pin "AH2") (pinfunction "AH2_AH2") (pintype "input"))
      (node (ref "EF36") (pin "AE2") (pinfunction "AE2_AE2") (pintype "output"))
      (node (ref "EF36") (pin "BB2") (pinfunction "BB2_BB2") (pintype "input"))
      (node (ref "EF37") (pin "AB1") (pinfunction "AB1_AB1") (pintype "input"))
    )
    (net (code "111") (name "ADDER05") (class "Default")
      (node (ref "EF35") (pin "AJ2") (pinfunction "AJ2_AJ2") (pintype "input"))
      (node (ref "EF36") (pin "AF1") (pinfunction "AF1_AF1") (pintype "output"))
      (node (ref "EF37") (pin "AC1") (pinfunction "AC1_AC1") (pintype "input"))
    )
    (net (code "112") (name "ADDER06") (class "Default")
      (node (ref "EF36") (pin "AH2") (pinfunction "AH2_AH2") (pintype "input"))
      (node (ref "EF37") (pin "AE2") (pinfunction "AE2_AE2") (pintype "output"))
      (node (ref "EF37") (pin "BB2") (pinfunction "BB2_BB2") (pintype "input"))
      (node (ref "EF38") (pin "AB1") (pinfunction "AB1_AB1") (pintype "input"))
    )
    (net (code "113") (name "ADDER07") (class "Default")
      (node (ref "EF36") (pin "AJ2") (pinfunction "AJ2_AJ2") (pintype "input"))
      (node (ref "EF37") (pin "AF1") (pinfunction "AF1_AF1") (pintype "output"))
      (node (ref "EF38") (pin "AC1") (pinfunction "AC1_AC1") (pintype "input"))
    )
    (net (code "114") (name "ADDER08") (class "Default")
      (node (ref "EF37") (pin "AH2") (pinfunction "AH2_AH2") (pintype "input"))
      (node (ref "EF38") (pin "AE2") (pinfunction "AE2_AE2") (pintype "output"))
      (node (ref "EF38") (pin "BB2") (pinfunction "BB2_BB2") (pintype "input"))
      (node (ref "EF39") (pin "AB1") (pinfunction "AB1_AB1") (pintype "input"))
    )
    (net (code "115") (name "ADDER09") (class "Default")
      (node (ref "EF37") (pin "AJ2") (pinfunction "AJ2_AJ2") (pintype "input"))
      (node (ref "EF38") (pin "AF1") (pinfunction "AF1_AF1") (pintype "output"))
      (node (ref "EF39") (pin "AC1") (pinfunction "AC1_AC1") (pintype "input"))
    )
    (net (code "116") (name "ADDER10") (class "Default")
      (node (ref "EF38") (pin "AH2") (pinfunction "AH2_AH2") (pintype "input"))
      (node (ref "EF39") (pin "AE2") (pinfunction "AE2_AE2") (pintype "output"))
      (node (ref "EF39") (pin "BB2") (pinfunction "BB2_BB2") (pintype "input"))
      (node (ref "F33") (pin "E1") (pinfunction "IN2A_E1") (pintype "input"))
    )
    (net (code "117") (name "ADDER11") (class "Default")
      (node (ref "EF34") (pin "AB1") (pinfunction "AB1_AB1") (pintype "input"))
      (node (ref "EF38") (pin "AJ2") (pinfunction "AJ2_AJ2") (pintype "input"))
      (node (ref "EF39") (pin "AF1") (pinfunction "AF1_AF1") (pintype "output"))
      (node (ref "F32") (pin "P1") (pinfunction "IN1_P1") (pintype "input"))
    )
    (net (code "118") (name "ADDER11_") (class "Default")
      (node (ref "C14") (pin "B1") (pinfunction "IN2_B1") (pintype "input"))
      (node (ref "F28") (pin "P1") (pinfunction "IN1_P1") (pintype "input"))
      (node (ref "F32") (pin "S1") (pinfunction "OUT_S1") (pintype "output"))
    )
    (net (code "119") (name "ADDER_L") (class "Default")
      (node (ref "C18") (pin "V2") (pinfunction "OUT_V2") (pintype "output"))
      (node (ref "D19") (pin "F1") (pinfunction "IN2_F1") (pintype "input"))
      (node (ref "D23") (pin "L2") (pinfunction "IN3A_L2") (pintype "input"))
    )
    (net (code "120") (name "ADDER_L_") (class "Default")
      (node (ref "C18") (pin "T2") (pinfunction "IN1_T2") (pintype "input"))
      (node (ref "D23") (pin "K2") (pinfunction "IN2B_K2") (pintype "input"))
      (node (ref "E24") (pin "B1") (pinfunction "IN2_B1") (pintype "input"))
      (node (ref "EF34") (pin "AC1") (pinfunction "AC1_AC1") (pintype "input"))
      (node (ref "EF34") (pin "BB2") (pinfunction "BB2_BB2") (pintype "input"))
      (node (ref "F33") (pin "H1") (pinfunction "IN3A_H1") (pintype "input"))
      (node (ref "F33") (pin "V2") (pinfunction "OUT_V2") (pintype "output"))
    )
    (net (code "121") (name "ADD_") (class "Default")
      (node (ref "E32") (pin "P1") (pinfunction "IN3_P1") (pintype "input"))
      (node (ref "F28") (pin "D1") (pinfunction "OUT_D1") (pintype "output"))
      (node (ref "F31") (pin "A1") (pinfunction "IN1_A1") (pintype "input"))
    )
    (net (code "122") (name "ADD_ACCEPTED_") (class "Default")
      (node (ref "E33") (pin "E1") (pinfunction "1_E1") (pintype "output"))
      (node (ref "H20") (pin "N2") (pinfunction "IN2_N2") (pintype "input"))
    )
    (net (code "123") (name "AND") (class "Default")
      (node (ref "E22") (pin "C1") (pinfunction "OUT_C1") (pintype "output"))
      (node (ref "F26") (pin "P1") (pinfunction "IN1_P1") (pintype "input"))
    )
    (net (code "124") (name "AND_") (class "Default")
      (node (ref "D40") (pin "M2") (pinfunction "P$2_M2") (pintype "bidirectional"))
      (node (ref "E21") (pin "H2") (pinfunction "OUT_H2") (pintype "output"))
      (node (ref "E22") (pin "A1") (pinfunction "IN1_A1") (pintype "input"))
      (node (ref "F26") (pin "T2") (pinfunction "IN1_T2") (pintype "input"))
    )
    (net (code "125") (name "AND_ENABLE") (class "Default")
      (node (ref "E31") (pin "V2") (pinfunction "OUT_V2") (pintype "open_collector"))
      (node (ref "EF34") (pin "AA1") (pinfunction "AA1_AA1") (pintype "input"))
      (node (ref "EF35") (pin "AA1") (pinfunction "AA1_AA1") (pintype "input"))
      (node (ref "EF36") (pin "AA1") (pinfunction "AA1_AA1") (pintype "input"))
      (node (ref "EF37") (pin "AA1") (pinfunction "AA1_AA1") (pintype "input"))
      (node (ref "EF38") (pin "AA1") (pinfunction "AA1_AA1") (pintype "input"))
      (node (ref "EF39") (pin "AA1") (pinfunction "AA1_AA1") (pintype "input"))
    )
    (net (code "126") (name "AND_ENABLE_") (class "Default")
      (node (ref "E31") (pin "R2") (pinfunction "IN1_R2") (pintype "input"))
      (node (ref "E32") (pin "M1") (pinfunction "IN1_M1") (pintype "input"))
      (node (ref "F26") (pin "U1") (pinfunction "OUT_U1") (pintype "output"))
    )
    (net (code "127") (name "ASR_ENABLE") (class "Default")
      (node (ref "D15") (pin "V2") (pinfunction "OUT_V2") (pintype "output"))
      (node (ref "D18") (pin "K2") (pinfunction "IN2_K2") (pintype "input"))
      (node (ref "F33") (pin "R2") (pinfunction "IN4C_R2") (pintype "input"))
    )
    (net (code "128") (name "ASR_L_SET_") (class "Default")
      (node (ref "D18") (pin "M2") (pinfunction "OUT_M2") (pintype "output"))
      (node (ref "F33") (pin "B1") (pinfunction "IN1B_B1") (pintype "input"))
    )
    (net (code "129") (name "AUTO_INDEX_") (class "Default")
      (node (ref "F27") (pin "K2") (pinfunction "IN1_K2") (pintype "input"))
      (node (ref "F27") (pin "S1") (pinfunction "OUT_S1") (pintype "output"))
    )
    (net (code "130") (name "BA") (class "Default")
      (node (ref "D01") (pin "R2") (pinfunction "P$2_R2") (pintype "bidirectional"))
      (node (ref "HJ26") (pin "BP2") (pinfunction "BP2_BP2") (pintype "output"))
    )
    (net (code "131") (name "BA_") (class "Default")
      (node (ref "D01") (pin "P2") (pinfunction "P$2_P2") (pintype "bidirectional"))
      (node (ref "HJ26") (pin "BS1") (pinfunction "BS1_BS1") (pintype "output"))
    )
    (net (code "132") (name "BB") (class "Default")
      (node (ref "D01") (pin "T2") (pinfunction "P$2_T2") (pintype "bidirectional"))
      (node (ref "HJ26") (pin "BU2") (pinfunction "BU2_BU2") (pintype "output"))
    )
    (net (code "133") (name "BB_") (class "Default")
      (node (ref "D01") (pin "S2") (pinfunction "P$2_S2") (pintype "bidirectional"))
      (node (ref "HJ26") (pin "BR1") (pinfunction "BR1_BR1") (pintype "output"))
    )
    (net (code "134") (name "BB_FIELD") (class "Default")
      (node (ref "C12") (pin "E1") (pinfunction "OUT_E1") (pintype "open_collector"))
      (node (ref "C25") (pin "D2") (pinfunction "D2_D2") (pintype "input"))
      (node (ref "C26") (pin "D2") (pinfunction "D2_D2") (pintype "input"))
      (node (ref "D25") (pin "D2") (pinfunction "D2_D2") (pintype "input"))
      (node (ref "D26") (pin "D2") (pinfunction "D2_D2") (pintype "input"))
    )
    (net (code "135") (name "BB_FIELD_") (class "Default")
      (node (ref "B30") (pin "L1") (pinfunction "OUT_L1") (pintype "open_collector"))
      (node (ref "C32") (pin "D2") (pinfunction "D2_D2") (pintype "input"))
      (node (ref "C33") (pin "D2") (pinfunction "D2_D2") (pintype "input"))
      (node (ref "D32") (pin "D2") (pinfunction "D2_D2") (pintype "input"))
      (node (ref "D33") (pin "D2") (pinfunction "D2_D2") (pintype "input"))
    )
    (net (code "136") (name "BB_LEFT_SHIFT") (class "Default")
      (node (ref "C16") (pin "D2") (pinfunction "IN1_D2") (pintype "input"))
      (node (ref "C16") (pin "L1") (pinfunction "IN1_L1") (pintype "input"))
      (node (ref "C16") (pin "P2") (pinfunction "IN1_P2") (pintype "input"))
      (node (ref "C17") (pin "D2") (pinfunction "IN1_D2") (pintype "input"))
      (node (ref "C17") (pin "L1") (pinfunction "IN1_L1") (pintype "input"))
      (node (ref "C17") (pin "P2") (pinfunction "IN1_P2") (pintype "input"))
      (node (ref "D12") (pin "V2") (pinfunction "OUT_V2") (pintype "output"))
    )
    (net (code "137") (name "BF0") (class "Default")
      (node (ref "A16") (pin "E2") (pinfunction "IN2_E2") (pintype "input"))
      (node (ref "B18") (pin "P2") (pinfunction "1_P2") (pintype "output"))
    )
    (net (code "138") (name "BF1") (class "Default")
      (node (ref "A16") (pin "M1") (pinfunction "IN2_M1") (pintype "input"))
      (node (ref "B18") (pin "S1") (pinfunction "1_S1") (pintype "output"))
    )
    (net (code "139") (name "BF2") (class "Default")
      (node (ref "A16") (pin "R2") (pinfunction "IN2_R2") (pintype "input"))
      (node (ref "B18") (pin "V2") (pinfunction "1_V2") (pintype "output"))
    )
    (net (code "140") (name "BF_ENABLE") (class "Default")
      (node (ref "A16") (pin "D2") (pinfunction "IN1_D2") (pintype "input"))
      (node (ref "A16") (pin "L1") (pinfunction "IN1_L1") (pintype "input"))
      (node (ref "A16") (pin "P2") (pinfunction "IN1_P2") (pintype "input"))
      (node (ref "B11") (pin "M1") (pinfunction "0_M1") (pintype "output"))
    )
    (net (code "141") (name "BIOP1") (class "Default")
      (node (ref "E09") (pin "N2") (pinfunction "OUT_N2") (pintype "output"))
      (node (ref "J33") (pin "F2") (pinfunction "F2_F2") (pintype "input"))
    )
    (net (code "142") (name "BIOP2") (class "Default")
      (node (ref "E09") (pin "S1") (pinfunction "OUT_S1") (pintype "output"))
      (node (ref "J33") (pin "H2") (pinfunction "H2_H2") (pintype "input"))
    )
    (net (code "143") (name "BIOP4") (class "Default")
      (node (ref "E09") (pin "S2") (pinfunction "OUT_S2") (pintype "output"))
      (node (ref "J33") (pin "F1") (pinfunction "F1_F1") (pintype "input"))
    )
    (net (code "144") (name "BMA00") (class "Default")
      (node (ref "B14") (pin "E1") (pinfunction "OUT_E1") (pintype "open_collector"))
      (node (ref "H01") (pin "K2") (pinfunction "P$2_K2") (pintype "bidirectional"))
    )
    (net (code "145") (name "BMA01") (class "Default")
      (node (ref "B14") (pin "J2") (pinfunction "OUT_J2") (pintype "open_collector"))
      (node (ref "H01") (pin "M2") (pinfunction "P$2_M2") (pintype "bidirectional"))
    )
    (net (code "146") (name "BMA02") (class "Default")
      (node (ref "B14") (pin "L1") (pinfunction "OUT_L1") (pintype "open_collector"))
      (node (ref "H01") (pin "P2") (pinfunction "P$2_P2") (pintype "bidirectional"))
    )
    (net (code "147") (name "BMA03") (class "Default")
      (node (ref "B14") (pin "P2") (pinfunction "OUT_P2") (pintype "open_collector"))
      (node (ref "H01") (pin "S2") (pinfunction "P$2_S2") (pintype "bidirectional"))
    )
    (net (code "148") (name "BMA04") (class "Default")
      (node (ref "B14") (pin "S1") (pinfunction "OUT_S1") (pintype "open_collector"))
      (node (ref "H01") (pin "T2") (pinfunction "P$2_T2") (pintype "bidirectional"))
    )
    (net (code "149") (name "BMA05") (class "Default")
      (node (ref "B14") (pin "V2") (pinfunction "OUT_V2") (pintype "open_collector"))
      (node (ref "H01") (pin "V2") (pinfunction "P$2_V2") (pintype "bidirectional"))
    )
    (net (code "150") (name "BMA06") (class "Default")
      (node (ref "B15") (pin "E1") (pinfunction "OUT_E1") (pintype "open_collector"))
      (node (ref "H02") (pin "D2") (pinfunction "P$2_D2") (pintype "bidirectional"))
    )
    (net (code "151") (name "BMA07") (class "Default")
      (node (ref "B15") (pin "J2") (pinfunction "OUT_J2") (pintype "open_collector"))
      (node (ref "H02") (pin "E2") (pinfunction "P$2_E2") (pintype "bidirectional"))
    )
    (net (code "152") (name "BMA08") (class "Default")
      (node (ref "B15") (pin "L1") (pinfunction "OUT_L1") (pintype "open_collector"))
      (node (ref "H02") (pin "H2") (pinfunction "P$2_H2") (pintype "bidirectional"))
    )
    (net (code "153") (name "BMA09") (class "Default")
      (node (ref "B15") (pin "P2") (pinfunction "OUT_P2") (pintype "open_collector"))
      (node (ref "H02") (pin "K2") (pinfunction "P$2_K2") (pintype "bidirectional"))
    )
    (net (code "154") (name "BMA10") (class "Default")
      (node (ref "B15") (pin "S1") (pinfunction "OUT_S1") (pintype "open_collector"))
      (node (ref "H02") (pin "M2") (pinfunction "P$2_M2") (pintype "bidirectional"))
    )
    (net (code "155") (name "BMA11") (class "Default")
      (node (ref "B15") (pin "V2") (pinfunction "OUT_V2") (pintype "open_collector"))
      (node (ref "H02") (pin "P2") (pinfunction "P$2_P2") (pintype "bidirectional"))
    )
    (net (code "156") (name "BREAK") (class "Default")
      (node (ref "E11") (pin "T2") (pinfunction "IN1_T2") (pintype "input"))
      (node (ref "E23") (pin "V2") (pinfunction "1_V2") (pintype "output"))
      (node (ref "E27") (pin "S2") (pinfunction "IN4D_S2") (pintype "input"))
      (node (ref "E29") (pin "L2") (pinfunction "IN3A_L2") (pintype "input"))
      (node (ref "F28") (pin "L1") (pinfunction "IN2_L1") (pintype "input"))
    )
    (net (code "157") (name "BREAK_") (class "Default")
      (node (ref "D40") (pin "E2") (pinfunction "P$2_E2") (pintype "bidirectional"))
      (node (ref "E23") (pin "V1") (pinfunction "0_V1") (pintype "output"))
      (node (ref "H20") (pin "H2") (pinfunction "IN2_H2") (pintype "input"))
    )
    (net (code "158") (name "BREAK_OK") (class "Default")
      (node (ref "F22") (pin "N1") (pinfunction "OUT_N1") (pintype "output"))
      (node (ref "F22") (pin "P1") (pinfunction "IN1_P1") (pintype "input"))
      (node (ref "F22") (pin "U2") (pinfunction "IN2_U2") (pintype "input"))
      (node (ref "F29") (pin "M1") (pinfunction "IN2_M1") (pintype "input"))
    )
    (net (code "159") (name "BREAK_OK_") (class "Default")
      (node (ref "E33") (pin "C1") (pinfunction "D_C1") (pintype "input"))
      (node (ref "F22") (pin "L1") (pinfunction "IN1_L1") (pintype "input"))
      (node (ref "F23") (pin "N1") (pinfunction "IN2_N1") (pintype "input"))
      (node (ref "F23") (pin "P2") (pinfunction "OUT_P2") (pintype "output"))
    )
    (net (code "160") (name "BRK_RQST") (class "Default")
      (node (ref "E20") (pin "M2") (pinfunction "D_M2") (pintype "input"))
      (node (ref "J15") (pin "S1") (pinfunction "OUT_S1") (pintype "output"))
    )
    (net (code "161") (name "BRK_SYNC") (class "Default")
      (node (ref "E20") (pin "P2") (pinfunction "1_P2") (pintype "output"))
      (node (ref "F23") (pin "L2") (pinfunction "IN2_L2") (pintype "input"))
    )
    (net (code "162") (name "BSTLR") (class "Default")
      (node (ref "C07") (pin "S2") (pinfunction "OUT_S2") (pintype "output"))
      (node (ref "D04") (pin "M2") (pinfunction "P$2_M2") (pintype "bidirectional"))
    )
    (net (code "163") (name "BTP2") (class "Default")
      (node (ref "F08") (pin "K2") (pinfunction "OUT_K2") (pintype "output"))
      (node (ref "H05") (pin "V2") (pinfunction "P$2_V2") (pintype "bidirectional"))
    )
    (net (code "164") (name "BTP3") (class "Default")
      (node (ref "C08") (pin "D2") (pinfunction "OUT_D2") (pintype "output"))
      (node (ref "D04") (pin "E2") (pinfunction "P$2_E2") (pintype "bidirectional"))
    )
    (net (code "165") (name "B_C_") (class "Default")
      (node (ref "C07") (pin "K2") (pinfunction "OUT_K2") (pintype "output"))
      (node (ref "D04") (pin "K2") (pinfunction "P$2_K2") (pintype "bidirectional"))
    )
    (net (code "166") (name "B_DC_INST") (class "Default")
      (node (ref "C08") (pin "S2") (pinfunction "OUT_S2") (pintype "output"))
      (node (ref "D04") (pin "P2") (pinfunction "P$2_P2") (pintype "bidirectional"))
    )
    (net (code "167") (name "B_EAE_ON") (class "Default")
      (node (ref "D12") (pin "J1") (pinfunction "IN2_J1") (pintype "input"))
      (node (ref "D13") (pin "B1") (pinfunction "IN2_B1") (pintype "input"))
      (node (ref "D13") (pin "K1") (pinfunction "OUT_K1") (pintype "output"))
      (node (ref "D17") (pin "C1") (pinfunction "IN3_C1") (pintype "input"))
      (node (ref "D17") (pin "K1") (pinfunction "IN1_K1") (pintype "input"))
      (node (ref "D17") (pin "L2") (pinfunction "IN3_L2") (pintype "input"))
      (node (ref "D18") (pin "A1") (pinfunction "IN1_A1") (pintype "input"))
      (node (ref "D18") (pin "P1") (pinfunction "IN1_P1") (pintype "input"))
      (node (ref "D18") (pin "R2") (pinfunction "IN3_R2") (pintype "input"))
      (node (ref "D20") (pin "E2") (pinfunction "IN2_E2") (pintype "input"))
      (node (ref "D20") (pin "J1") (pinfunction "IN3_J1") (pintype "input"))
      (node (ref "F33") (pin "P2") (pinfunction "IN4B_P2") (pintype "input"))
    )
    (net (code "168") (name "B_EXECUTE") (class "Default")
      (node (ref "D13") (pin "M2") (pinfunction "IN2_M2") (pintype "input"))
      (node (ref "D14") (pin "E2") (pinfunction "IN2_E2") (pintype "input"))
      (node (ref "D21") (pin "H2") (pinfunction "IN4_H2") (pintype "input"))
      (node (ref "E26") (pin "H2") (pinfunction "IN1D_H2") (pintype "input"))
      (node (ref "E27") (pin "B1") (pinfunction "IN1B_B1") (pintype "input"))
      (node (ref "E27") (pin "N1") (pinfunction "IN5B_N1") (pintype "input"))
      (node (ref "E28") (pin "E2") (pinfunction "IN1B_E2") (pintype "input"))
      (node (ref "E29") (pin "D2") (pinfunction "IN1A_D2") (pintype "input"))
      (node (ref "E29") (pin "K2") (pinfunction "IN2B_K2") (pintype "input"))
      (node (ref "E30") (pin "N1") (pinfunction "IN5B_N1") (pintype "input"))
      (node (ref "E30") (pin "R2") (pinfunction "IN4C_R2") (pintype "input"))
      (node (ref "F25") (pin "R2") (pinfunction "IN2_R2") (pintype "input"))
      (node (ref "F26") (pin "P2") (pinfunction "IN2_P2") (pintype "input"))
      (node (ref "F26") (pin "S1") (pinfunction "IN3_S1") (pintype "input"))
      (node (ref "F28") (pin "C1") (pinfunction "IN3_C1") (pintype "input"))
      (node (ref "F28") (pin "F1") (pinfunction "IN2_F1") (pintype "input"))
      (node (ref "F31") (pin "V2") (pinfunction "OUT_V2") (pintype "open_collector"))
    )
    (net (code "169") (name "B_EXT_INST") (class "Default")
      (node (ref "A06") (pin "N1") (pinfunction "OUT_N1") (pintype "output"))
      (node (ref "A20") (pin "K1") (pinfunction "IN1_K1") (pintype "input"))
      (node (ref "A20") (pin "N2") (pinfunction "IN1_N2") (pintype "input"))
      (node (ref "A20") (pin "P1") (pinfunction "IN1_P1") (pintype "input"))
      (node (ref "B04") (pin "C1") (pinfunction "IN3_C1") (pintype "input"))
    )
    (net (code "170") (name "B_FETCH") (class "Default")
      (node (ref "B16") (pin "K2") (pinfunction "IN1_K2") (pintype "input"))
      (node (ref "D10") (pin "N2") (pinfunction "IN4_N2") (pintype "input"))
      (node (ref "D20") (pin "M1") (pinfunction "IN1_M1") (pintype "input"))
      (node (ref "E22") (pin "M1") (pinfunction "IN2_M1") (pintype "input"))
      (node (ref "E25") (pin "K2") (pinfunction "IN2_K2") (pintype "input"))
      (node (ref "E25") (pin "U2") (pinfunction "IN2_U2") (pintype "input"))
      (node (ref "E26") (pin "D1") (pinfunction "IN1D_D1") (pintype "input"))
      (node (ref "E26") (pin "R2") (pinfunction "IN4C_R2") (pintype "input"))
      (node (ref "F09") (pin "A1") (pinfunction "IN1_A1") (pintype "input"))
      (node (ref "F19") (pin "S2") (pinfunction "IN2_S2") (pintype "input"))
      (node (ref "F20") (pin "P1") (pinfunction "IN1_P1") (pintype "input"))
      (node (ref "F21") (pin "J1") (pinfunction "IN2_J1") (pintype "input"))
      (node (ref "F23") (pin "H1") (pinfunction "IN2_H1") (pintype "input"))
      (node (ref "F27") (pin "C1") (pinfunction "IN3_C1") (pintype "input"))
      (node (ref "F27") (pin "J1") (pinfunction "IN3_J1") (pintype "input"))
      (node (ref "F27") (pin "T2") (pinfunction "IN3_T2") (pintype "input"))
      (node (ref "F31") (pin "S1") (pinfunction "OUT_S1") (pintype "open_collector"))
    )
    (net (code "171") (name "B_FIELD") (class "Default")
      (node (ref "A27") (pin "E2") (pinfunction "E2_E2") (pintype "input"))
      (node (ref "A27") (pin "N2") (pinfunction "N2_N2") (pintype "input"))
      (node (ref "A37") (pin "N2") (pinfunction "N2_N2") (pintype "input"))
      (node (ref "B26") (pin "E2") (pinfunction "E2_E2") (pintype "input"))
      (node (ref "B26") (pin "N2") (pinfunction "N2_N2") (pintype "input"))
      (node (ref "B27") (pin "E2") (pinfunction "E2_E2") (pintype "input"))
      (node (ref "B27") (pin "N2") (pinfunction "N2_N2") (pintype "input"))
      (node (ref "B30") (pin "J2") (pinfunction "OUT_J2") (pintype "open_collector"))
      (node (ref "C30") (pin "D2") (pinfunction "D2_D2") (pintype "input"))
      (node (ref "C31") (pin "D2") (pinfunction "D2_D2") (pintype "input"))
      (node (ref "D30") (pin "D2") (pinfunction "D2_D2") (pintype "input"))
      (node (ref "D31") (pin "D2") (pinfunction "D2_D2") (pintype "input"))
    )
    (net (code "172") (name "B_FIELD_") (class "Default")
      (node (ref "A36") (pin "E2") (pinfunction "E2_E2") (pintype "input"))
      (node (ref "A36") (pin "N2") (pinfunction "N2_N2") (pintype "input"))
      (node (ref "A37") (pin "E2") (pinfunction "E2_E2") (pintype "input"))
      (node (ref "B30") (pin "V2") (pinfunction "OUT_V2") (pintype "open_collector"))
      (node (ref "B36") (pin "E2") (pinfunction "E2_E2") (pintype "input"))
      (node (ref "B36") (pin "N2") (pinfunction "N2_N2") (pintype "input"))
      (node (ref "B37") (pin "E2") (pinfunction "E2_E2") (pintype "input"))
      (node (ref "B37") (pin "N2") (pinfunction "N2_N2") (pintype "input"))
      (node (ref "C37") (pin "D2") (pinfunction "D2_D2") (pintype "input"))
      (node (ref "C38") (pin "D2") (pinfunction "D2_D2") (pintype "input"))
      (node (ref "D37") (pin "D2") (pinfunction "D2_D2") (pintype "input"))
      (node (ref "D38") (pin "D2") (pinfunction "D2_D2") (pintype "input"))
    )
    (net (code "173") (name "B_INHIBIT") (class "Default")
      (node (ref "A27") (pin "A1") (pinfunction "A1_A1") (pintype "input"))
      (node (ref "A36") (pin "A1") (pinfunction "A1_A1") (pintype "input"))
      (node (ref "A37") (pin "A1") (pinfunction "A1_A1") (pintype "input"))
      (node (ref "B26") (pin "A1") (pinfunction "A1_A1") (pintype "input"))
      (node (ref "B27") (pin "A1") (pinfunction "A1_A1") (pintype "input"))
      (node (ref "B30") (pin "P2") (pinfunction "OUT_P2") (pintype "open_collector"))
      (node (ref "B36") (pin "A1") (pinfunction "A1_A1") (pintype "input"))
      (node (ref "B37") (pin "A1") (pinfunction "A1_A1") (pintype "input"))
    )
    (net (code "174") (name "B_LEFT_SHIFT") (class "Default")
      (node (ref "C14") (pin "D2") (pinfunction "IN1_D2") (pintype "input"))
      (node (ref "C14") (pin "L1") (pinfunction "IN1_L1") (pintype "input"))
      (node (ref "C14") (pin "P2") (pinfunction "IN1_P2") (pintype "input"))
      (node (ref "C15") (pin "D2") (pinfunction "IN1_D2") (pintype "input"))
      (node (ref "C15") (pin "L1") (pinfunction "IN1_L1") (pintype "input"))
      (node (ref "C15") (pin "P2") (pinfunction "IN1_P2") (pintype "input"))
      (node (ref "D12") (pin "K2") (pinfunction "OUT_K2") (pintype "output"))
    )
    (net (code "175") (name "B_LINE_HOLD_") (class "Default")
      (node (ref "C07") (pin "D2") (pinfunction "OUT_D2") (pintype "output"))
      (node (ref "D04") (pin "D2") (pinfunction "P$2_D2") (pintype "bidirectional"))
    )
    (net (code "176") (name "B_MEM_ENABLE") (class "Default")
      (node (ref "A30") (pin "T2") (pinfunction "T2_T2") (pintype "input"))
      (node (ref "A31") (pin "T2") (pinfunction "T2_T2") (pintype "input"))
      (node (ref "A32") (pin "T2") (pinfunction "T2_T2") (pintype "input"))
      (node (ref "A33") (pin "T2") (pinfunction "T2_T2") (pintype "input"))
      (node (ref "B30") (pin "E1") (pinfunction "OUT_E1") (pintype "open_collector"))
      (node (ref "B31") (pin "T2") (pinfunction "T2_T2") (pintype "input"))
      (node (ref "B32") (pin "T2") (pinfunction "T2_T2") (pintype "input"))
      (node (ref "B33") (pin "T2") (pinfunction "T2_T2") (pintype "input"))
    )
    (net (code "177") (name "B_MEM_START") (class "Default")
      (node (ref "F08") (pin "D2") (pinfunction "OUT_D2") (pintype "output"))
      (node (ref "H05") (pin "M2") (pinfunction "P$2_M2") (pintype "bidirectional"))
    )
    (net (code "178") (name "B_MEM_TO_LSR") (class "Default")
      (node (ref "C08") (pin "K2") (pinfunction "OUT_K2") (pintype "output"))
      (node (ref "D04") (pin "H2") (pinfunction "P$2_H2") (pintype "bidirectional"))
    )
    (net (code "179") (name "B_POWER_CLEAR_") (class "Default")
      (node (ref "B22") (pin "A1") (pinfunction "R_A1") (pintype "input"))
      (node (ref "B22") (pin "K2") (pinfunction "R_K2") (pintype "input"))
      (node (ref "C12") (pin "S1") (pinfunction "OUT_S1") (pintype "open_collector"))
      (node (ref "D24") (pin "K2") (pinfunction "R_K2") (pintype "input"))
      (node (ref "E18") (pin "K2") (pinfunction "R_K2") (pintype "input"))
      (node (ref "EF10") (pin "AL2") (pinfunction "CL2_AL2") (pintype "input"))
      (node (ref "F20") (pin "R2") (pinfunction "IN2_R2") (pintype "input"))
    )
    (net (code "180") (name "B_R0_") (class "Default")
      (node (ref "D04") (pin "V2") (pinfunction "P$2_V2") (pintype "bidirectional"))
      (node (ref "D05") (pin "D2") (pinfunction "IN_D2") (pintype "input"))
      (node (ref "D05") (pin "E2") (pinfunction "IN2_E2") (pintype "bidirectional"))
      (node (ref "D05") (pin "F2") (pinfunction "IN3_F2") (pintype "input"))
      (node (ref "D05") (pin "H2") (pinfunction "IN4_H2") (pintype "input"))
    )
    (net (code "181") (name "B_SET") (class "Default")
      (node (ref "A19") (pin "E2") (pinfunction "IN2_E2") (pintype "input"))
      (node (ref "A19") (pin "M1") (pinfunction "IN2_M1") (pintype "input"))
      (node (ref "E23") (pin "T2") (pinfunction "D_T2") (pintype "input"))
      (node (ref "F22") (pin "S2") (pinfunction "OUT_S2") (pintype "output"))
    )
    (net (code "182") (name "B_SET_") (class "Default")
      (node (ref "A19") (pin "F2") (pinfunction "OUT_F2") (pintype "output"))
      (node (ref "B11") (pin "J1") (pinfunction "D_J1") (pintype "input"))
      (node (ref "B20") (pin "F2") (pinfunction "IN3_F2") (pintype "input"))
    )
    (net (code "183") (name "C") (class "Default")
      (node (ref "C10") (pin "P2") (pinfunction "IN1_P2") (pintype "input"))
      (node (ref "C11") (pin "E1") (pinfunction "IN1_E1") (pintype "input"))
      (node (ref "D09") (pin "E2") (pinfunction "IN2_E2") (pintype "input"))
      (node (ref "D10") (pin "N1") (pinfunction "IN2_N1") (pintype "input"))
      (node (ref "D10") (pin "S2") (pinfunction "IN2_S2") (pintype "input"))
      (node (ref "D11") (pin "J2") (pinfunction "0_J2") (pintype "output"))
    )
    (net (code "184") (name "CARRY_INSERT_") (class "Default")
      (node (ref "EF39") (pin "BJ1") (pinfunction "BJ1_BJ1") (pintype "input"))
      (node (ref "F32") (pin "C1") (pinfunction "OUT_C1") (pintype "output"))
    )
    (net (code "185") (name "CARRY_OUT0") (class "Default")
      (node (ref "E28") (pin "F2") (pinfunction "IN1C_F2") (pintype "input"))
      (node (ref "F21") (pin "B1") (pinfunction "IN2_B1") (pintype "input"))
      (node (ref "F32") (pin "V2") (pinfunction "OUT_V2") (pintype "output"))
      (node (ref "F33") (pin "U1") (pinfunction "IN1B_U1") (pintype "input"))
    )
    (net (code "186") (name "CARRY_OUT0_") (class "Default")
      (node (ref "EF34") (pin "BK2") (pinfunction "BK2_BK2") (pintype "output"))
      (node (ref "F32") (pin "U2") (pinfunction "IN2_U2") (pintype "input"))
      (node (ref "F33") (pin "U2") (pinfunction "IN2B_U2") (pintype "input"))
    )
    (net (code "187") (name "CARRY_OUT6_") (class "Default")
      (node (ref "EF36") (pin "BJ1") (pinfunction "BJ1_BJ1") (pintype "input"))
      (node (ref "EF37") (pin "BK2") (pinfunction "BK2_BK2") (pintype "output"))
    )
    (net (code "188") (name "CA_INCREMENT") (class "Default")
      (node (ref "E27") (pin "L2") (pinfunction "IN3A_L2") (pintype "input"))
      (node (ref "F25") (pin "F1") (pinfunction "OUT_F1") (pintype "output"))
    )
    (net (code "189") (name "CA_INCREMENT_") (class "Default")
      (node (ref "F25") (pin "D1") (pinfunction "IN1_D1") (pintype "input"))
      (node (ref "J20") (pin "L1") (pinfunction "OUT_L1") (pintype "output"))
    )
    (net (code "190") (name "CINT_") (class "Default")
      (node (ref "A05") (pin "L2") (pinfunction "IN1_L2") (pintype "input"))
      (node (ref "B04") (pin "D1") (pinfunction "OUT_D1") (pintype "output"))
    )
    (net (code "191") (name "CLEAR_DF_") (class "Default")
      (node (ref "B18") (pin "A1") (pinfunction "R_A1") (pintype "input"))
      (node (ref "B21") (pin "S2") (pinfunction "OUT_S2") (pintype "output"))
    )
    (net (code "192") (name "CLEAR_IB_") (class "Default")
      (node (ref "B17") (pin "K2") (pinfunction "R_K2") (pintype "input"))
      (node (ref "B21") (pin "N2") (pinfunction "OUT_N2") (pintype "output"))
    )
    (net (code "193") (name "CLEAR_IFDFBF_") (class "Default")
      (node (ref "B21") (pin "L2") (pinfunction "IN1_L2") (pintype "input"))
      (node (ref "B21") (pin "P1") (pinfunction "IN1_P1") (pintype "input"))
      (node (ref "B21") (pin "P2") (pinfunction "IN1_P2") (pintype "input"))
      (node (ref "E14") (pin "J1") (pinfunction "OUT_J1") (pintype "output"))
    )
    (net (code "194") (name "CLEAR_IF_") (class "Default")
      (node (ref "B05") (pin "A1") (pinfunction "R_A1") (pintype "input"))
      (node (ref "B17") (pin "A1") (pinfunction "R_A1") (pintype "input"))
      (node (ref "B21") (pin "S1") (pinfunction "OUT_S1") (pintype "output"))
    )
    (net (code "195") (name "CLEAR_X_") (class "Default")
      (node (ref "HJ23") (pin "AS2") (pinfunction "AS2_AS2") (pintype "output"))
      (node (ref "HJ24") (pin "AL2") (pinfunction "AL2_AL2") (pintype "bidirectional"))
    )
    (net (code "196") (name "CLEAR_Y_") (class "Default")
      (node (ref "HJ23") (pin "AR2") (pinfunction "AR2_AR2") (pintype "output"))
      (node (ref "HJ25") (pin "AL2") (pinfunction "AL2_AL2") (pintype "bidirectional"))
    )
    (net (code "197") (name "CLOCK") (class "Default")
      (node (ref "H30") (pin "D2") (pinfunction "D2_D2") (pintype "input"))
      (node (ref "HJ31") (pin "BJ2") (pinfunction "BJ2_BJ2") (pintype "input"))
      (node (ref "J30") (pin "D2") (pinfunction "D2_D2") (pintype "output"))
      (node (ref "J30") (pin "F2") (pinfunction "F2_F2") (pintype "bidirectional"))
    )
    (net (code "198") (name "CLOCK1") (class "Default")
      (node (ref "HJ26") (pin "BS2") (pinfunction "BS2_BS2") (pintype "input"))
      (node (ref "HJ27") (pin "AU2") (pinfunction "AU_AU2") (pintype "output"))
    )
    (net (code "199") (name "CLOCK_AC_CLR_") (class "Default")
      (node (ref "HJ31") (pin "BM2") (pinfunction "BM2_BM2") (pintype "open_collector"))
      (node (ref "J15") (pin "K1") (pinfunction "IN4_K1") (pintype "input"))
    )
    (net (code "200") (name "CLOCK_ENABLE_") (class "Default")
      (node (ref "H30") (pin "J2") (pinfunction "J2_J2") (pintype "output"))
      (node (ref "J30") (pin "J2") (pinfunction "J2_J2") (pintype "input"))
    )
    (net (code "201") (name "CLOCK_IOT") (class "Default")
      (node (ref "H30") (pin "S1") (pinfunction "S1_S1") (pintype "output"))
      (node (ref "HJ31") (pin "BL1") (pinfunction "BL1_BL1") (pintype "input"))
    )
    (net (code "202") (name "CLOCK_P4") (class "Default")
      (node (ref "H30") (pin "K2") (pinfunction "K2_K2") (pintype "output"))
      (node (ref "HJ31") (pin "BK1") (pinfunction "BK1_BK1") (pintype "input"))
    )
    (net (code "203") (name "CLOCK_SCALE_2") (class "Default")
      (node (ref "EF01") (pin "BP2") (pinfunction "BP2_BP2") (pintype "input"))
      (node (ref "EF01") (pin "BT2") (pinfunction "BT2_BT2") (pintype "output"))
      (node (ref "EF01") (pin "BU1") (pinfunction "BU1_BU1") (pintype "input"))
    )
    (net (code "204") (name "CLR_PARITY_ERROR_") (class "Default")
      (node (ref "B07") (pin "S2") (pinfunction "OUT_S2") (pintype "output"))
      (node (ref "B09") (pin "P1") (pinfunction "IN1_P1") (pintype "input"))
    )
    (net (code "205") (name "CR_READ") (class "Default")
      (node (ref "HJ34") (pin "BP2") (pinfunction "P$2_BP2") (pintype "bidirectional"))
      (node (ref "J33") (pin "S2") (pinfunction "S2_S2") (pintype "output"))
    )
    (net (code "206") (name "CR_READY") (class "Default")
      (node (ref "HJ34") (pin "AK2") (pinfunction "P$2_AK2") (pintype "bidirectional"))
      (node (ref "J33") (pin "R2") (pinfunction "R2_R2") (pintype "input"))
    )
    (net (code "207") (name "CSR_ENABLE_") (class "Default")
      (node (ref "C11") (pin "E2") (pinfunction "IN2_E2") (pintype "input"))
      (node (ref "D07") (pin "F1") (pinfunction "OUT_F1") (pintype "output"))
    )
    (net (code "208") (name "CUF") (class "Default")
      (node (ref "B06") (pin "K2") (pinfunction "OUT_K2") (pintype "output"))
      (node (ref "B06") (pin "L1") (pinfunction "IN1_L1") (pintype "input"))
    )
    (net (code "209") (name "CUF_") (class "Default")
      (node (ref "B06") (pin "C1") (pinfunction "OUT_C1") (pintype "output"))
      (node (ref "B06") (pin "D1") (pinfunction "IN1_D1") (pintype "input"))
      (node (ref "B06") (pin "H2") (pinfunction "IN1_H2") (pintype "input"))
      (node (ref "F11") (pin "F2") (pinfunction "IN3_F2") (pintype "input"))
      (node (ref "F11") (pin "H2") (pinfunction "IN4_H2") (pintype "input"))
    )
    (net (code "210") (name "CURRENT_ADDRESS") (class "Default")
      (node (ref "E23") (pin "S1") (pinfunction "1_S1") (pintype "output"))
      (node (ref "E27") (pin "M2") (pinfunction "IN3B_M2") (pintype "input"))
      (node (ref "E29") (pin "L1") (pinfunction "IN4B_L1") (pintype "input"))
    )
    (net (code "211") (name "CURRENT_ADDRESS_") (class "Default")
      (node (ref "D40") (pin "E1") (pinfunction "P$2_E1") (pintype "bidirectional"))
      (node (ref "E23") (pin "U1") (pinfunction "0_U1") (pintype "output"))
      (node (ref "E25") (pin "F1") (pinfunction "IN2_F1") (pintype "input"))
      (node (ref "F22") (pin "R2") (pinfunction "IN2_R2") (pintype "input"))
    )
    (net (code "212") (name "C_") (class "Default")
      (node (ref "C07") (pin "M2") (pinfunction "IN1_M2") (pintype "input"))
      (node (ref "D09") (pin "N2") (pinfunction "IN1_N2") (pintype "input"))
      (node (ref "D11") (pin "H2") (pinfunction "1_H2") (pintype "output"))
    )
    (net (code "213") (name "C_I_R") (class "Default")
      (node (ref "HJ34") (pin "BR2") (pinfunction "P$2_BR2") (pintype "bidirectional"))
      (node (ref "J33") (pin "U2") (pinfunction "U2_U2") (pintype "input"))
    )
    (net (code "214") (name "C_NO_SHIFT_") (class "Default")
      (node (ref "D07") (pin "C1") (pinfunction "OUT_C1") (pintype "output"))
      (node (ref "E31") (pin "R1") (pinfunction "IN4_R1") (pintype "input"))
    )
    (net (code "215") (name "C_SET_") (class "Default")
      (node (ref "C11") (pin "A1") (pinfunction "IN1_A1") (pintype "input"))
      (node (ref "C11") (pin "R2") (pinfunction "IN3_R2") (pintype "input"))
      (node (ref "D10") (pin "J2") (pinfunction "OUT_J2") (pintype "output"))
      (node (ref "D11") (pin "E2") (pinfunction "D_E2") (pintype "input"))
    )
    (net (code "216") (name "DATA00") (class "Default")
      (node (ref "EF34") (pin "BM2") (pinfunction "BM2_BM2") (pintype "input"))
      (node (ref "J18") (pin "E1") (pinfunction "OUT_E1") (pintype "output"))
    )
    (net (code "217") (name "DATA01") (class "Default")
      (node (ref "EF34") (pin "BP2") (pinfunction "BP2_BP2") (pintype "input"))
      (node (ref "J18") (pin "J2") (pinfunction "OUT_J2") (pintype "output"))
    )
    (net (code "218") (name "DATA02") (class "Default")
      (node (ref "EF35") (pin "BM2") (pinfunction "BM2_BM2") (pintype "input"))
      (node (ref "J18") (pin "L1") (pinfunction "OUT_L1") (pintype "output"))
    )
    (net (code "219") (name "DATA03") (class "Default")
      (node (ref "EF35") (pin "BP2") (pinfunction "BP2_BP2") (pintype "input"))
      (node (ref "J18") (pin "P2") (pinfunction "OUT_P2") (pintype "output"))
    )
    (net (code "220") (name "DATA04") (class "Default")
      (node (ref "EF36") (pin "BM2") (pinfunction "BM2_BM2") (pintype "input"))
      (node (ref "J18") (pin "S1") (pinfunction "OUT_S1") (pintype "output"))
    )
    (net (code "221") (name "DATA05") (class "Default")
      (node (ref "EF36") (pin "BP2") (pinfunction "BP2_BP2") (pintype "input"))
      (node (ref "J18") (pin "V2") (pinfunction "OUT_V2") (pintype "output"))
    )
    (net (code "222") (name "DATA06") (class "Default")
      (node (ref "EF37") (pin "BM2") (pinfunction "BM2_BM2") (pintype "input"))
      (node (ref "J19") (pin "E1") (pinfunction "OUT_E1") (pintype "output"))
    )
    (net (code "223") (name "DATA07") (class "Default")
      (node (ref "EF37") (pin "BP2") (pinfunction "BP2_BP2") (pintype "input"))
      (node (ref "J19") (pin "J2") (pinfunction "OUT_J2") (pintype "output"))
    )
    (net (code "224") (name "DATA08") (class "Default")
      (node (ref "EF38") (pin "BM2") (pinfunction "BM2_BM2") (pintype "input"))
      (node (ref "J19") (pin "L1") (pinfunction "OUT_L1") (pintype "output"))
    )
    (net (code "225") (name "DATA09") (class "Default")
      (node (ref "EF38") (pin "BP2") (pinfunction "BP2_BP2") (pintype "input"))
      (node (ref "J19") (pin "P2") (pinfunction "OUT_P2") (pintype "output"))
    )
    (net (code "226") (name "DATA10") (class "Default")
      (node (ref "EF39") (pin "BM2") (pinfunction "BM2_BM2") (pintype "input"))
      (node (ref "J19") (pin "S1") (pinfunction "OUT_S1") (pintype "output"))
    )
    (net (code "227") (name "DATA11") (class "Default")
      (node (ref "EF39") (pin "BP2") (pinfunction "BP2_BP2") (pintype "input"))
      (node (ref "J19") (pin "V2") (pinfunction "OUT_V2") (pintype "output"))
    )
    (net (code "228") (name "DATA_ADD00") (class "Default")
      (node (ref "EF34") (pin "BS1") (pinfunction "BS1_BS1") (pintype "input"))
      (node (ref "J16") (pin "E1") (pinfunction "OUT_E1") (pintype "output"))
    )
    (net (code "229") (name "DATA_ADD01") (class "Default")
      (node (ref "EF34") (pin "BU1") (pinfunction "BU1_BU1") (pintype "input"))
      (node (ref "J16") (pin "J2") (pinfunction "OUT_J2") (pintype "output"))
    )
    (net (code "230") (name "DATA_ADD02") (class "Default")
      (node (ref "EF35") (pin "BS1") (pinfunction "BS1_BS1") (pintype "input"))
      (node (ref "J16") (pin "L1") (pinfunction "OUT_L1") (pintype "output"))
    )
    (net (code "231") (name "DATA_ADD03") (class "Default")
      (node (ref "EF35") (pin "BU1") (pinfunction "BU1_BU1") (pintype "input"))
      (node (ref "J16") (pin "P2") (pinfunction "OUT_P2") (pintype "output"))
    )
    (net (code "232") (name "DATA_ADD04") (class "Default")
      (node (ref "EF36") (pin "BS1") (pinfunction "BS1_BS1") (pintype "input"))
      (node (ref "J16") (pin "S1") (pinfunction "OUT_S1") (pintype "output"))
    )
    (net (code "233") (name "DATA_ADD05") (class "Default")
      (node (ref "EF36") (pin "BU1") (pinfunction "BU1_BU1") (pintype "input"))
      (node (ref "J16") (pin "V2") (pinfunction "OUT_V2") (pintype "output"))
    )
    (net (code "234") (name "DATA_ADD06") (class "Default")
      (node (ref "EF37") (pin "BS1") (pinfunction "BS1_BS1") (pintype "input"))
      (node (ref "J17") (pin "E1") (pinfunction "OUT_E1") (pintype "output"))
    )
    (net (code "235") (name "DATA_ADD07") (class "Default")
      (node (ref "EF37") (pin "BU1") (pinfunction "BU1_BU1") (pintype "input"))
      (node (ref "J17") (pin "J2") (pinfunction "OUT_J2") (pintype "output"))
    )
    (net (code "236") (name "DATA_ADD08") (class "Default")
      (node (ref "EF38") (pin "BS1") (pinfunction "BS1_BS1") (pintype "input"))
      (node (ref "J17") (pin "L1") (pinfunction "OUT_L1") (pintype "output"))
    )
    (net (code "237") (name "DATA_ADD09") (class "Default")
      (node (ref "EF38") (pin "BU1") (pinfunction "BU1_BU1") (pintype "input"))
      (node (ref "J17") (pin "P2") (pinfunction "OUT_P2") (pintype "output"))
    )
    (net (code "238") (name "DATA_ADD10") (class "Default")
      (node (ref "EF39") (pin "BS1") (pinfunction "BS1_BS1") (pintype "input"))
      (node (ref "J17") (pin "S1") (pinfunction "OUT_S1") (pintype "output"))
    )
    (net (code "239") (name "DATA_ADD11") (class "Default")
      (node (ref "EF39") (pin "BU1") (pinfunction "BU1_BU1") (pintype "input"))
      (node (ref "J17") (pin "V2") (pinfunction "OUT_V2") (pintype "output"))
    )
    (net (code "240") (name "DATA_ADD_ENABLE") (class "Default")
      (node (ref "EF34") (pin "BT2") (pinfunction "BT2_BT2") (pintype "input"))
      (node (ref "EF35") (pin "BT2") (pinfunction "BT2_BT2") (pintype "input"))
      (node (ref "EF36") (pin "BT2") (pinfunction "BT2_BT2") (pintype "input"))
      (node (ref "EF37") (pin "BT2") (pinfunction "BT2_BT2") (pintype "input"))
      (node (ref "EF38") (pin "BT2") (pinfunction "BT2_BT2") (pintype "input"))
      (node (ref "EF39") (pin "BT2") (pinfunction "BT2_BT2") (pintype "input"))
      (node (ref "F30") (pin "P2") (pinfunction "OUT_P2") (pintype "open_collector"))
    )
    (net (code "241") (name "DATA_ENABLE") (class "Default")
      (node (ref "EF34") (pin "BL1") (pinfunction "BL1_BL1") (pintype "input"))
      (node (ref "EF35") (pin "BL1") (pinfunction "BL1_BL1") (pintype "input"))
      (node (ref "EF36") (pin "BL1") (pinfunction "BL1_BL1") (pintype "input"))
      (node (ref "EF37") (pin "BL1") (pinfunction "BL1_BL1") (pintype "input"))
      (node (ref "EF38") (pin "BL1") (pinfunction "BL1_BL1") (pintype "input"))
      (node (ref "EF39") (pin "BL1") (pinfunction "BL1_BL1") (pintype "input"))
      (node (ref "F30") (pin "L1") (pinfunction "OUT_L1") (pintype "open_collector"))
    )
    (net (code "242") (name "DATA_IN") (class "Default")
      (node (ref "E29") (pin "M2") (pinfunction "IN3B_M2") (pintype "input"))
      (node (ref "F28") (pin "M1") (pinfunction "IN3_M1") (pintype "input"))
      (node (ref "F29") (pin "F2") (pinfunction "OUT_F2") (pintype "output"))
    )
    (net (code "243") (name "DATA_IN_") (class "Default")
      (node (ref "F29") (pin "D2") (pinfunction "IN1_D2") (pintype "input"))
      (node (ref "J15") (pin "V2") (pinfunction "OUT_V2") (pintype "output"))
    )
    (net (code "244") (name "DCA") (class "Default")
      (node (ref "E22") (pin "K2") (pinfunction "OUT_K2") (pintype "output"))
      (node (ref "E29") (pin "J2") (pinfunction "IN2A_J2") (pintype "input"))
      (node (ref "E30") (pin "S2") (pinfunction "IN4D_S2") (pintype "input"))
    )
    (net (code "245") (name "DCA_") (class "Default")
      (node (ref "D40") (pin "R2") (pinfunction "P$2_R2") (pintype "bidirectional"))
      (node (ref "E21") (pin "M2") (pinfunction "OUT_M2") (pintype "output"))
      (node (ref "E22") (pin "H2") (pinfunction "IN1_H2") (pintype "input"))
      (node (ref "F26") (pin "V2") (pinfunction "IN3_V2") (pintype "input"))
    )
    (net (code "246") (name "DC_INST_") (class "Default")
      (node (ref "C08") (pin "V2") (pinfunction "IN2_V2") (pintype "input"))
      (node (ref "D09") (pin "J1") (pinfunction "OUT_J1") (pintype "output"))
    )
    (net (code "247") (name "DEFER") (class "Default")
      (node (ref "B20") (pin "C1") (pinfunction "IN3_C1") (pintype "input"))
      (node (ref "E23") (pin "H2") (pinfunction "1_H2") (pintype "output"))
      (node (ref "E24") (pin "D1") (pinfunction "IN1_D1") (pintype "input"))
      (node (ref "E26") (pin "N1") (pinfunction "IN5B_N1") (pintype "input"))
      (node (ref "E29") (pin "C1") (pinfunction "IN1C_C1") (pintype "input"))
      (node (ref "E29") (pin "N1") (pinfunction "IN5B_N1") (pintype "input"))
      (node (ref "F25") (pin "M1") (pinfunction "IN2_M1") (pintype "input"))
    )
    (net (code "248") (name "DEFER_") (class "Default")
      (node (ref "D40") (pin "B1") (pinfunction "P$2_B1") (pintype "bidirectional"))
      (node (ref "E23") (pin "J2") (pinfunction "0_J2") (pintype "output"))
    )
    (net (code "249") (name "DF0") (class "Default")
      (node (ref "A11") (pin "E1") (pinfunction "IN2_E1") (pintype "input"))
      (node (ref "A16") (pin "E1") (pinfunction "IN2_E1") (pintype "input"))
      (node (ref "B18") (pin "E1") (pinfunction "1_E1") (pintype "output"))
      (node (ref "B19") (pin "M2") (pinfunction "D_M2") (pintype "input"))
    )
    (net (code "250") (name "DF0_") (class "Default")
      (node (ref "B18") (pin "F1") (pinfunction "0_F1") (pintype "output"))
      (node (ref "C40") (pin "J2") (pinfunction "P$2_J2") (pintype "bidirectional"))
    )
    (net (code "251") (name "DF1") (class "Default")
      (node (ref "A11") (pin "J2") (pinfunction "IN2_J2") (pintype "input"))
      (node (ref "A16") (pin "J2") (pinfunction "IN2_J2") (pintype "input"))
      (node (ref "B18") (pin "H2") (pinfunction "1_H2") (pintype "output"))
      (node (ref "B19") (pin "P1") (pinfunction "D_P1") (pintype "input"))
    )
    (net (code "252") (name "DF1_") (class "Default")
      (node (ref "B18") (pin "J2") (pinfunction "0_J2") (pintype "output"))
      (node (ref "C40") (pin "S1") (pinfunction "P$2_S1") (pintype "bidirectional"))
    )
    (net (code "253") (name "DF2") (class "Default")
      (node (ref "A11") (pin "R1") (pinfunction "IN2_R1") (pintype "input"))
      (node (ref "A16") (pin "R1") (pinfunction "IN2_R1") (pintype "input"))
      (node (ref "B18") (pin "L1") (pinfunction "1_L1") (pintype "output"))
      (node (ref "B19") (pin "T2") (pinfunction "D_T2") (pintype "input"))
    )
    (net (code "254") (name "DF2_") (class "Default")
      (node (ref "B18") (pin "M1") (pinfunction "0_M1") (pintype "output"))
      (node (ref "C40") (pin "P2") (pinfunction "P$2_P2") (pintype "bidirectional"))
    )
    (net (code "255") (name "DFSR0") (class "Default")
      (node (ref "A12") (pin "E1") (pinfunction "IN2_E1") (pintype "input"))
      (node (ref "A40") (pin "D2") (pinfunction "P$2_D2") (pintype "bidirectional"))
    )
    (net (code "256") (name "DFSR1") (class "Default")
      (node (ref "A12") (pin "J2") (pinfunction "IN2_J2") (pintype "input"))
      (node (ref "A40") (pin "E2") (pinfunction "P$2_E2") (pintype "bidirectional"))
    )
    (net (code "257") (name "DFSR2") (class "Default")
      (node (ref "A12") (pin "R1") (pinfunction "IN2_R1") (pintype "input"))
      (node (ref "A40") (pin "F2") (pinfunction "P$2_F2") (pintype "bidirectional"))
    )
    (net (code "258") (name "DF_ENABLE") (class "Default")
      (node (ref "A16") (pin "D1") (pinfunction "IN1_D1") (pintype "input"))
      (node (ref "A16") (pin "H2") (pinfunction "IN1_H2") (pintype "input"))
      (node (ref "A16") (pin "P1") (pinfunction "IN1_P1") (pintype "input"))
      (node (ref "B11") (pin "J2") (pinfunction "0_J2") (pintype "output"))
    )
    (net (code "259") (name "DF_ENABLE_") (class "Default")
      (node (ref "B11") (pin "E2") (pinfunction "D_E2") (pintype "input"))
      (node (ref "B20") (pin "D1") (pinfunction "OUT_D1") (pintype "output"))
      (node (ref "B20") (pin "D2") (pinfunction "IN1_D2") (pintype "input"))
    )
    (net (code "260") (name "DIV_LAST") (class "Default")
      (node (ref "D12") (pin "A1") (pinfunction "IN1_A1") (pintype "input"))
      (node (ref "D13") (pin "E2") (pinfunction "IN2_E2") (pintype "input"))
      (node (ref "D16") (pin "K1") (pinfunction "OUT_K1") (pintype "output"))
      (node (ref "D20") (pin "M2") (pinfunction "IN3_M2") (pintype "input"))
      (node (ref "D23") (pin "E1") (pinfunction "IN2A_E1") (pintype "input"))
    )
    (net (code "261") (name "DIV_LAST_") (class "Default")
      (node (ref "D12") (pin "C1") (pinfunction "OUT_C1") (pintype "output"))
      (node (ref "D12") (pin "D2") (pinfunction "IN1_D2") (pintype "input"))
      (node (ref "D12") (pin "L2") (pinfunction "IN1_L2") (pintype "input"))
      (node (ref "D17") (pin "J2") (pinfunction "IN1_J2") (pintype "input"))
      (node (ref "D20") (pin "H2") (pinfunction "IN4_H2") (pintype "input"))
    )
    (net (code "262") (name "DOUBLE_LEFT_ROTATE") (class "Default")
      (node (ref "E31") (pin "J2") (pinfunction "OUT_J2") (pintype "open_collector"))
      (node (ref "EF34") (pin "AH1") (pinfunction "AH1_AH1") (pintype "input"))
      (node (ref "EF35") (pin "AH1") (pinfunction "AH1_AH1") (pintype "input"))
      (node (ref "EF36") (pin "AH1") (pinfunction "AH1_AH1") (pintype "input"))
      (node (ref "EF37") (pin "AH1") (pinfunction "AH1_AH1") (pintype "input"))
      (node (ref "EF38") (pin "AH1") (pinfunction "AH1_AH1") (pintype "input"))
      (node (ref "EF39") (pin "AH1") (pinfunction "AH1_AH1") (pintype "input"))
      (node (ref "F33") (pin "N1") (pinfunction "IN5B_N1") (pintype "input"))
    )
    (net (code "263") (name "DOUBLE_RIGHT_ROTATE") (class "Default")
      (node (ref "E31") (pin "E1") (pinfunction "OUT_E1") (pintype "open_collector"))
      (node (ref "EF34") (pin "AD1") (pinfunction "AD1_AD1") (pintype "input"))
      (node (ref "EF35") (pin "AD1") (pinfunction "AD1_AD1") (pintype "input"))
      (node (ref "EF36") (pin "AD1") (pinfunction "AD1_AD1") (pintype "input"))
      (node (ref "EF37") (pin "AD1") (pinfunction "AD1_AD1") (pintype "input"))
      (node (ref "EF38") (pin "AD1") (pinfunction "AD1_AD1") (pintype "input"))
      (node (ref "EF39") (pin "AD1") (pinfunction "AD1_AD1") (pintype "input"))
      (node (ref "F33") (pin "F1") (pinfunction "IN2B_F1") (pintype "input"))
    )
    (net (code "264") (name "DRUM_DOWN") (class "Default")
      (node (ref "D02") (pin "T2") (pinfunction "P$2_T2") (pintype "bidirectional"))
      (node (ref "HJ29") (pin "AR2") (pinfunction "AR2_AR2") (pintype "output"))
    )
    (net (code "265") (name "DRUM_UP") (class "Default")
      (node (ref "D02") (pin "S2") (pinfunction "P$2_S2") (pintype "bidirectional"))
      (node (ref "HJ29") (pin "AN2") (pinfunction "AN2_AN2") (pintype "output"))
    )
    (net (code "266") (name "DVI") (class "Default")
      (node (ref "D12") (pin "B1") (pinfunction "IN2_B1") (pintype "input"))
      (node (ref "D16") (pin "M1") (pinfunction "IN2_M1") (pintype "input"))
      (node (ref "D16") (pin "S2") (pinfunction "OUT_S2") (pintype "output"))
      (node (ref "D17") (pin "F1") (pinfunction "IN2_F1") (pintype "input"))
      (node (ref "D17") (pin "M1") (pinfunction "IN3_M1") (pintype "input"))
      (node (ref "D20") (pin "N2") (pinfunction "IN4_N2") (pintype "input"))
      (node (ref "D23") (pin "F1") (pinfunction "IN2B_F1") (pintype "input"))
    )
    (net (code "267") (name "DVI_") (class "Default")
      (node (ref "D16") (pin "P2") (pinfunction "IN1_P2") (pintype "input"))
      (node (ref "D17") (pin "B1") (pinfunction "IN2_B1") (pintype "input"))
      (node (ref "D19") (pin "V1") (pinfunction "OUT_V1") (pintype "output"))
      (node (ref "D23") (pin "S2") (pinfunction "IN4D_S2") (pintype "input"))
    )
    (net (code "268") (name "D_SET") (class "Default")
      (node (ref "E23") (pin "E2") (pinfunction "D_E2") (pintype "input"))
      (node (ref "F22") (pin "K2") (pinfunction "OUT_K2") (pintype "output"))
    )
    (net (code "269") (name "D_SET_") (class "Default")
      (node (ref "E25") (pin "M2") (pinfunction "OUT_M2") (pintype "output"))
      (node (ref "F22") (pin "H2") (pinfunction "IN1_H2") (pintype "input"))
      (node (ref "F23") (pin "N2") (pinfunction "IN4_N2") (pintype "input"))
      (node (ref "F23") (pin "R1") (pinfunction "IN4_R1") (pintype "input"))
      (node (ref "F29") (pin "D1") (pinfunction "IN1_D1") (pintype "input"))
    )
    (net (code "270") (name "E09F1") (class "Default")
      (node (ref "E09") (pin "F1") (pinfunction "OUT_F1") (pintype "output"))
      (node (ref "E17") (pin "H2") (pinfunction "H2_H2") (pintype "input"))
    )
    (net (code "271") (name "E25D1") (class "Default")
      (node (ref "E25") (pin "D1") (pinfunction "OUT_D1") (pintype "output"))
      (node (ref "EF39") (pin "AH2") (pinfunction "AH2_AH2") (pintype "input"))
    )
    (net (code "272") (name "EA0") (class "Default")
      (node (ref "B16") (pin "E1") (pinfunction "OUT_E1") (pintype "open_collector"))
      (node (ref "B16") (pin "M1") (pinfunction "IN1_M1") (pintype "input"))
      (node (ref "H01") (pin "D2") (pinfunction "P$2_D2") (pintype "bidirectional"))
    )
    (net (code "273") (name "EA0_") (class "Default")
      (node (ref "B16") (pin "S1") (pinfunction "OUT_S1") (pintype "open_collector"))
      (node (ref "B21") (pin "L1") (pinfunction "IN1_L1") (pintype "input"))
    )
    (net (code "274") (name "EA1") (class "Default")
      (node (ref "B16") (pin "J2") (pinfunction "OUT_J2") (pintype "open_collector"))
      (node (ref "B16") (pin "R2") (pinfunction "IN1_R2") (pintype "input"))
      (node (ref "H01") (pin "E2") (pinfunction "P$2_E2") (pintype "bidirectional"))
    )
    (net (code "275") (name "EA1_") (class "Default")
      (node (ref "B16") (pin "V2") (pinfunction "OUT_V2") (pintype "open_collector"))
      (node (ref "B21") (pin "M1") (pinfunction "IN2_M1") (pintype "input"))
    )
    (net (code "276") (name "EA2") (class "Default")
      (node (ref "B16") (pin "L1") (pinfunction "OUT_L1") (pintype "open_collector"))
      (node (ref "B22") (pin "E2") (pinfunction "D_E2") (pintype "input"))
      (node (ref "H01") (pin "H2") (pinfunction "P$2_H2") (pintype "bidirectional"))
    )
    (net (code "277") (name "EAE_ACBAR_ENABLE_") (class "Default")
      (node (ref "D13") (pin "A1") (pinfunction "IN1_A1") (pintype "input"))
      (node (ref "D17") (pin "N1") (pinfunction "OUT_N1") (pintype "output"))
      (node (ref "D17") (pin "P1") (pinfunction "IN1_P1") (pintype "input"))
      (node (ref "E32") (pin "U2") (pinfunction "IN4_U2") (pintype "input"))
      (node (ref "F29") (pin "M2") (pinfunction "IN2_M2") (pintype "input"))
    )
    (net (code "278") (name "EAE_AC_ENABLE_") (class "Default")
      (node (ref "D13") (pin "C1") (pinfunction "OUT_C1") (pintype "output"))
      (node (ref "E32") (pin "R1") (pinfunction "IN4_R1") (pintype "input"))
    )
    (net (code "279") (name "EAE_BEGIN") (class "Default")
      (node (ref "D12") (pin "R2") (pinfunction "IN2_R2") (pintype "input"))
      (node (ref "D14") (pin "H1") (pinfunction "IN1_H1") (pintype "input"))
      (node (ref "D14") (pin "K2") (pinfunction "OUT_K2") (pintype "output"))
      (node (ref "D17") (pin "V2") (pinfunction "IN3_V2") (pintype "input"))
    )
    (net (code "280") (name "EAE_COMPLETE_") (class "Default")
      (node (ref "C22") (pin "T2") (pinfunction "D_T2") (pintype "input"))
      (node (ref "D15") (pin "J2") (pinfunction "IN2_J2") (pintype "input"))
      (node (ref "D23") (pin "R1") (pinfunction "OUT_R1") (pintype "output"))
    )
    (net (code "281") (name "EAE_END") (class "Default")
      (node (ref "C22") (pin "V2") (pinfunction "1_V2") (pintype "output"))
      (node (ref "E12") (pin "D2") (pinfunction "IN1_D2") (pintype "input"))
      (node (ref "E14") (pin "P2") (pinfunction "IN2_P2") (pintype "input"))
    )
    (net (code "282") (name "EAE_EXECUTE_") (class "Default")
      (node (ref "D13") (pin "N2") (pinfunction "OUT_N2") (pintype "output"))
      (node (ref "F28") (pin "U2") (pinfunction "IN2_U2") (pintype "input"))
    )
    (net (code "283") (name "EAE_E_SET_") (class "Default")
      (node (ref "D13") (pin "N1") (pinfunction "OUT_N1") (pintype "output"))
      (node (ref "F23") (pin "H2") (pinfunction "IN4_H2") (pintype "input"))
      (node (ref "F28") (pin "K2") (pinfunction "IN2_K2") (pintype "input"))
    )
    (net (code "284") (name "EAE_INST") (class "Default")
      (node (ref "D13") (pin "D1") (pinfunction "IN1_D1") (pintype "input"))
      (node (ref "D13") (pin "K2") (pinfunction "OUT_K2") (pintype "output"))
      (node (ref "D13") (pin "M1") (pinfunction "IN2_M1") (pintype "input"))
      (node (ref "D14") (pin "R2") (pinfunction "IN2_R2") (pintype "input"))
      (node (ref "D18") (pin "L1") (pinfunction "IN2_L1") (pintype "input"))
      (node (ref "D20") (pin "U2") (pinfunction "IN4_U2") (pintype "input"))
    )
    (net (code "285") (name "EAE_IR0") (class "Default")
      (node (ref "D18") (pin "B1") (pinfunction "IN2_B1") (pintype "input"))
      (node (ref "D20") (pin "R2") (pinfunction "IN1_R2") (pintype "input"))
      (node (ref "D24") (pin "E1") (pinfunction "1_E1") (pintype "output"))
    )
    (net (code "286") (name "EAE_IR0_") (class "Default")
      (node (ref "D15") (pin "H1") (pinfunction "IN1_H1") (pintype "input"))
      (node (ref "D19") (pin "N2") (pinfunction "IN1_N2") (pintype "input"))
      (node (ref "D19") (pin "P1") (pinfunction "IN1_P1") (pintype "input"))
      (node (ref "D19") (pin "T2") (pinfunction "IN1_T2") (pintype "input"))
      (node (ref "D20") (pin "F1") (pinfunction "IN1_F1") (pintype "input"))
      (node (ref "D24") (pin "F1") (pinfunction "0_F1") (pintype "output"))
    )
    (net (code "287") (name "EAE_IR1") (class "Default")
      (node (ref "D15") (pin "J1") (pinfunction "IN2_J1") (pintype "input"))
      (node (ref "D17") (pin "A1") (pinfunction "IN1_A1") (pintype "input"))
      (node (ref "D18") (pin "C1") (pinfunction "IN3_C1") (pintype "input"))
      (node (ref "D19") (pin "R1") (pinfunction "IN2_R1") (pintype "input"))
      (node (ref "D19") (pin "U2") (pinfunction "IN2_U2") (pintype "input"))
      (node (ref "D24") (pin "H2") (pinfunction "1_H2") (pintype "output"))
    )
    (net (code "288") (name "EAE_IR1_") (class "Default")
      (node (ref "D19") (pin "P2") (pinfunction "IN2_P2") (pintype "input"))
      (node (ref "D20") (pin "S2") (pinfunction "IN2_S2") (pintype "input"))
      (node (ref "D24") (pin "J2") (pinfunction "0_J2") (pintype "output"))
    )
    (net (code "289") (name "EAE_IR2") (class "Default")
      (node (ref "D19") (pin "R2") (pinfunction "IN3_R2") (pintype "input"))
      (node (ref "D19") (pin "V2") (pinfunction "IN3_V2") (pintype "input"))
      (node (ref "D24") (pin "L1") (pinfunction "1_L1") (pintype "output"))
    )
    (net (code "290") (name "EAE_IR2_") (class "Default")
      (node (ref "D18") (pin "L2") (pinfunction "IN3_L2") (pintype "input"))
      (node (ref "D19") (pin "S1") (pinfunction "IN3_S1") (pintype "input"))
      (node (ref "D20") (pin "T2") (pinfunction "IN3_T2") (pintype "input"))
      (node (ref "D24") (pin "M1") (pinfunction "0_M1") (pintype "output"))
      (node (ref "F33") (pin "S2") (pinfunction "IN4D_S2") (pintype "input"))
    )
    (net (code "291") (name "EAE_IR_CLEAR_") (class "Default")
      (node (ref "D24") (pin "A1") (pinfunction "R_A1") (pintype "input"))
      (node (ref "E22") (pin "N1") (pinfunction "OUT_N1") (pintype "output"))
      (node (ref "E22") (pin "P1") (pinfunction "IN1_P1") (pintype "input"))
    )
    (net (code "292") (name "EAE_LEFT_SHIFT_ENABLE_") (class "Default")
      (node (ref "D20") (pin "J2") (pinfunction "OUT_J2") (pintype "output"))
      (node (ref "E31") (pin "N2") (pinfunction "IN4_N2") (pintype "input"))
    )
    (net (code "293") (name "EAE_L_DISABLE") (class "Default")
      (node (ref "D17") (pin "U1") (pinfunction "OUT_U1") (pintype "output"))
      (node (ref "E28") (pin "L1") (pinfunction "IN4B_L1") (pintype "input"))
    )
    (net (code "294") (name "EAE_MEM_ENABLE_") (class "Default")
      (node (ref "D20") (pin "L1") (pinfunction "OUT_L1") (pintype "output"))
      (node (ref "F11") (pin "L2") (pinfunction "IN2_L2") (pintype "input"))
      (node (ref "F31") (pin "D1") (pinfunction "IN4_D1") (pintype "input"))
      (node (ref "F31") (pin "D2") (pinfunction "IN1_D2") (pintype "input"))
    )
    (net (code "295") (name "EAE_MQ0BAR_ENABLE_") (class "Default")
      (node (ref "D18") (pin "U1") (pinfunction "OUT_U1") (pintype "output"))
      (node (ref "E25") (pin "B1") (pinfunction "IN2_B1") (pintype "input"))
    )
    (net (code "296") (name "EAE_MQ0_ENABLE_") (class "Default")
      (node (ref "D18") (pin "S2") (pinfunction "OUT_S2") (pintype "output"))
      (node (ref "E25") (pin "C1") (pinfunction "IN3_C1") (pintype "input"))
    )
    (net (code "297") (name "EAE_NO_SHIFT_ENABLE") (class "Default")
      (node (ref "D17") (pin "M2") (pinfunction "OUT_M2") (pintype "output"))
      (node (ref "F24") (pin "C1") (pinfunction "IN3_C1") (pintype "input"))
    )
    (net (code "298") (name "EAE_ON") (class "Default")
      (node (ref "C18") (pin "L2") (pinfunction "IN1_L2") (pintype "input"))
      (node (ref "C21") (pin "A1") (pinfunction "IN1_A1") (pintype "input"))
      (node (ref "C21") (pin "D2") (pinfunction "IN1_D2") (pintype "input"))
      (node (ref "C21") (pin "E1") (pinfunction "IN1_E1") (pintype "input"))
      (node (ref "C21") (pin "J2") (pinfunction "IN1_J2") (pintype "input"))
      (node (ref "C21") (pin "K1") (pinfunction "IN1_K1") (pintype "input"))
      (node (ref "C21") (pin "N2") (pinfunction "IN1_N2") (pintype "input"))
      (node (ref "C21") (pin "R1") (pinfunction "IN2_R1") (pintype "input"))
      (node (ref "C21") (pin "T2") (pinfunction "IN1_T2") (pintype "input"))
      (node (ref "D24") (pin "P1") (pinfunction "D_P1") (pintype "input"))
      (node (ref "D24") (pin "P2") (pinfunction "1_P2") (pintype "output"))
    )
    (net (code "299") (name "EAE_ON_") (class "Default")
      (node (ref "D13") (pin "H1") (pinfunction "IN1_H1") (pintype "input"))
      (node (ref "D21") (pin "E2") (pinfunction "IN2_E2") (pintype "input"))
      (node (ref "D24") (pin "R2") (pinfunction "0_R2") (pintype "output"))
      (node (ref "E24") (pin "A1") (pinfunction "IN1_A1") (pintype "input"))
      (node (ref "F28") (pin "R1") (pinfunction "IN2_R1") (pintype "input"))
    )
    (net (code "300") (name "EAE_RIGHT_SHIFT_ENABLE_") (class "Default")
      (node (ref "D12") (pin "H1") (pinfunction "IN1_H1") (pintype "input"))
      (node (ref "D17") (pin "D1") (pinfunction "OUT_D1") (pintype "output"))
      (node (ref "D20") (pin "D2") (pinfunction "IN1_D2") (pintype "input"))
      (node (ref "E31") (pin "K1") (pinfunction "IN4_K1") (pintype "input"))
    )
    (net (code "301") (name "EAE_RUN") (class "Default")
      (node (ref "C22") (pin "U2") (pinfunction "S_U2") (pintype "input"))
      (node (ref "D12") (pin "M2") (pinfunction "IN2_M2") (pintype "input"))
      (node (ref "D14") (pin "A1") (pinfunction "IN1_A1") (pintype "input"))
      (node (ref "D15") (pin "M1") (pinfunction "IN2_M1") (pintype "input"))
      (node (ref "D24") (pin "S1") (pinfunction "1_S1") (pintype "output"))
    )
    (net (code "302") (name "EAE_RUN_") (class "Default")
      (node (ref "D24") (pin "U1") (pinfunction "0_U1") (pintype "output"))
    )
    (net (code "303") (name "EAE_SET_") (class "Default")
      (node (ref "D14") (pin "K1") (pinfunction "OUT_K1") (pintype "output"))
      (node (ref "E14") (pin "L1") (pinfunction "IN2_L1") (pintype "input"))
    )
    (net (code "304") (name "EAE_START_") (class "Default")
      (node (ref "D14") (pin "E1") (pinfunction "IN2_E1") (pintype "input"))
      (node (ref "D17") (pin "V1") (pinfunction "OUT_V1") (pintype "output"))
      (node (ref "D24") (pin "R1") (pinfunction "S_R1") (pintype "input"))
      (node (ref "E12") (pin "E1") (pinfunction "IN2_E1") (pintype "input"))
    )
    (net (code "305") (name "EAE_TG") (class "Default")
      (node (ref "D22") (pin "P1") (pinfunction "IN3_P1") (pintype "input"))
      (node (ref "D22") (pin "R2") (pinfunction "IN1_R2") (pintype "input"))
      (node (ref "D24") (pin "V2") (pinfunction "1_V2") (pintype "output"))
    )
    (net (code "306") (name "EAE_TP") (class "Default")
      (node (ref "C13") (pin "J1") (pinfunction "OUT_J1") (pintype "output"))
      (node (ref "C22") (pin "S2") (pinfunction "C_S2") (pintype "input"))
      (node (ref "D14") (pin "B1") (pinfunction "IN2_B1") (pintype "input"))
    )
    (net (code "307") (name "EAE_TP_") (class "Default")
      (node (ref "D12") (pin "P1") (pinfunction "IN1_P1") (pintype "input"))
      (node (ref "D14") (pin "C1") (pinfunction "OUT_C1") (pintype "output"))
      (node (ref "D14") (pin "D1") (pinfunction "IN1_D1") (pintype "input"))
      (node (ref "D22") (pin "D2") (pinfunction "IN1_D2") (pintype "input"))
      (node (ref "E32") (pin "K2") (pinfunction "IN1_K2") (pintype "input"))
    )
    (net (code "308") (name "ENABLE") (class "Default")
      (node (ref "EF02") (pin "AK1") (pinfunction "AK1_AK1") (pintype "input"))
      (node (ref "EF02") (pin "AK2") (pinfunction "AK2_AK2") (pintype "output"))
    )
    (net (code "309") (name "ENABLE_") (class "Default")
      (node (ref "EF02") (pin "AH1") (pinfunction "AH1_AH1") (pintype "input"))
      (node (ref "EF02") (pin "AL1") (pinfunction "AL1_AL1") (pintype "output"))
    )
    (net (code "310") (name "EXECUTE_") (class "Default")
      (node (ref "D40") (pin "R1") (pinfunction "P$2_R1") (pintype "bidirectional"))
      (node (ref "E23") (pin "M1") (pinfunction "0_M1") (pintype "output"))
      (node (ref "F31") (pin "R2") (pinfunction "IN1_R2") (pintype "input"))
    )
    (net (code "311") (name "EXT_DATA_ADD0") (class "Default")
      (node (ref "B18") (pin "M2") (pinfunction "D_M2") (pintype "input"))
      (node (ref "J20") (pin "P2") (pinfunction "OUT_P2") (pintype "output"))
    )
    (net (code "312") (name "EXT_DATA_ADD1") (class "Default")
      (node (ref "B18") (pin "P1") (pinfunction "D_P1") (pintype "input"))
      (node (ref "J20") (pin "S1") (pinfunction "OUT_S1") (pintype "output"))
    )
    (net (code "313") (name "EXT_DATA_ADD2") (class "Default")
      (node (ref "B18") (pin "T2") (pinfunction "D_T2") (pintype "input"))
      (node (ref "J20") (pin "V2") (pinfunction "OUT_V2") (pintype "output"))
    )
    (net (code "314") (name "EXT_GO") (class "Default")
      (node (ref "A12") (pin "A1") (pinfunction "IN1_A1") (pintype "input"))
      (node (ref "A13") (pin "F1") (pinfunction "OUT_F1") (pintype "output"))
      (node (ref "A15") (pin "H2") (pinfunction "IN1_H2") (pintype "input"))
      (node (ref "A17") (pin "U2") (pinfunction "IN2_U2") (pintype "input"))
      (node (ref "B06") (pin "D2") (pinfunction "IN1_D2") (pintype "input"))
    )
    (net (code "315") (name "EXT_INST") (class "Default")
      (node (ref "A14") (pin "K2") (pinfunction "OUT_K2") (pintype "output"))
      (node (ref "A15") (pin "U2") (pinfunction "IN2_U2") (pintype "input"))
    )
    (net (code "316") (name "E_SET") (class "Default")
      (node (ref "E23") (pin "J1") (pinfunction "D_J1") (pintype "input"))
      (node (ref "F22") (pin "H1") (pinfunction "IN1_H1") (pintype "input"))
      (node (ref "F23") (pin "J2") (pinfunction "OUT_J2") (pintype "output"))
    )
    (net (code "317") (name "E_SET_") (class "Default")
      (node (ref "A16") (pin "U2") (pinfunction "IN2_U2") (pintype "input"))
      (node (ref "F22") (pin "K1") (pinfunction "OUT_K1") (pintype "output"))
      (node (ref "F23") (pin "K2") (pinfunction "IN1_K2") (pintype "input"))
      (node (ref "F23") (pin "P1") (pinfunction "IN3_P1") (pintype "input"))
      (node (ref "F29") (pin "E1") (pinfunction "IN2_E1") (pintype "input"))
    )
    (net (code "318") (name "F15F1") (class "Default")
      (node (ref "F15") (pin "F1") (pinfunction "OUT_F1") (pintype "output"))
      (node (ref "F16") (pin "H2") (pinfunction "H2_H2") (pintype "input"))
    )
    (net (code "319") (name "F17F1") (class "Default")
      (node (ref "F17") (pin "F1") (pinfunction "OUT_F1") (pintype "output"))
      (node (ref "F18") (pin "H2") (pinfunction "H2_H2") (pintype "input"))
    )
    (net (code "320") (name "FEED_HOLE") (class "Default")
      (node (ref "C01") (pin "H2") (pinfunction "P$2_H2") (pintype "bidirectional"))
      (node (ref "C01") (pin "T2") (pinfunction "P$2_T2") (pintype "bidirectional"))
      (node (ref "C04") (pin "S2") (pinfunction "R_S2") (pintype "open_collector"))
    )
    (net (code "321") (name "FETCH_") (class "Default")
      (node (ref "D40") (pin "N1") (pinfunction "P$2_N1") (pintype "bidirectional"))
      (node (ref "E23") (pin "F1") (pinfunction "0_F1") (pintype "output"))
      (node (ref "F28") (pin "T2") (pinfunction "IN1_T2") (pintype "input"))
      (node (ref "F31") (pin "M1") (pinfunction "IN1_M1") (pintype "input"))
    )
    (net (code "322") (name "FIELD") (class "Default")
      (node (ref "B22") (pin "H2") (pinfunction "1_H2") (pintype "output"))
      (node (ref "B24") (pin "R2") (pinfunction "R_R2") (pintype "input"))
      (node (ref "B30") (pin "F1") (pinfunction "IN1_F1") (pintype "input"))
      (node (ref "B30") (pin "R2") (pinfunction "IN1_R2") (pintype "input"))
    )
    (net (code "323") (name "FIELD_") (class "Default")
      (node (ref "B22") (pin "J2") (pinfunction "0_J2") (pintype "output"))
      (node (ref "B23") (pin "R2") (pinfunction "R_R2") (pintype "input"))
      (node (ref "B30") (pin "H2") (pinfunction "IN4_H2") (pintype "input"))
      (node (ref "C12") (pin "A1") (pinfunction "IN1_A1") (pintype "input"))
    )
    (net (code "324") (name "F_SET") (class "Default")
      (node (ref "E13") (pin "F1") (pinfunction "IN2B_F1") (pintype "input"))
      (node (ref "E23") (pin "C1") (pinfunction "D_C1") (pintype "input"))
      (node (ref "F11") (pin "U2") (pinfunction "IN4_U2") (pintype "input"))
      (node (ref "F22") (pin "F1") (pinfunction "OUT_F1") (pintype "output"))
    )
    (net (code "325") (name "F_SET_") (class "Default")
      (node (ref "A16") (pin "T2") (pinfunction "IN1_T2") (pintype "input"))
      (node (ref "F22") (pin "D1") (pinfunction "IN1_D1") (pintype "input"))
      (node (ref "F23") (pin "S1") (pinfunction "OUT_S1") (pintype "output"))
      (node (ref "F28") (pin "J2") (pinfunction "IN1_J2") (pintype "input"))
    )
    (net (code "326") (name "GND") (class "Default")
      (node (ref "A10") (pin "J1") (pinfunction "8A_J1") (pintype "input"))
      (node (ref "A25") (pin "H2") (pinfunction "P$1_H2") (pintype "passive"))
      (node (ref "A26") (pin "H2") (pinfunction "P$1_H2") (pintype "passive"))
      (node (ref "A38") (pin "C2") (pinfunction "P$2_C2") (pintype "passive"))
      (node (ref "A38") (pin "E2") (pinfunction "P$2_E2") (pintype "passive"))
      (node (ref "A39") (pin "C2") (pinfunction "P$2_C2") (pintype "passive"))
      (node (ref "A40") (pin "C2") (pinfunction "P$2_C2") (pintype "bidirectional"))
      (node (ref "AB01") (pin "AP2") (pinfunction "GND_AP2") (pintype "power_in"))
      (node (ref "AB01") (pin "AR2") (pinfunction "GND_AR2") (pintype "power_in"))
      (node (ref "AB01") (pin "AS2") (pinfunction "GND_AS2") (pintype "power_in"))
      (node (ref "AB01") (pin "AT2") (pinfunction "GND_AT2") (pintype "power_in"))
      (node (ref "AB01") (pin "AU2") (pinfunction "GND_AU2") (pintype "power_in"))
      (node (ref "AB01") (pin "BC2") (pinfunction "GND_BC2") (pintype "power_in"))
      (node (ref "AB01") (pin "BD2") (pinfunction "GND_BD2") (pintype "power_in"))
      (node (ref "AB01") (pin "BE2") (pinfunction "GND_BE2") (pintype "power_in"))
      (node (ref "AB01") (pin "BF2") (pinfunction "GND_BF2") (pintype "power_in"))
      (node (ref "AB01") (pin "BH2") (pinfunction "GND_BH2") (pintype "power_in"))
      (node (ref "AB01") (pin "BJ2") (pinfunction "GND_BJ2") (pintype "power_in"))
      (node (ref "AB01") (pin "BK2") (pinfunction "GND_BK2") (pintype "power_in"))
      (node (ref "AB01") (pin "BL2") (pinfunction "GND_BL2") (pintype "power_in"))
      (node (ref "B05") (pin "T2") (pinfunction "D_T2") (pintype "input"))
      (node (ref "B22") (pin "J1") (pinfunction "D_J1") (pintype "input"))
      (node (ref "B22") (pin "M2") (pinfunction "D_M2") (pintype "input"))
      (node (ref "B22") (pin "P1") (pinfunction "D_P1") (pintype "input"))
      (node (ref "B25") (pin "H2") (pinfunction "P$1_H2") (pintype "passive"))
      (node (ref "B38") (pin "C2") (pinfunction "P$2_C2") (pintype "passive"))
      (node (ref "B39") (pin "C2") (pinfunction "P$2_C2") (pintype "passive"))
      (node (ref "B39") (pin "E2") (pinfunction "P$2_E2") (pintype "passive"))
      (node (ref "B40") (pin "C2") (pinfunction "P$2_C2") (pintype "bidirectional"))
      (node (ref "C01") (pin "C2") (pinfunction "P$2_C2") (pintype "bidirectional"))
      (node (ref "C01") (pin "E2") (pinfunction "P$2_E2") (pintype "bidirectional"))
      (node (ref "C40") (pin "C2") (pinfunction "P$2_C2") (pintype "bidirectional"))
      (node (ref "D02") (pin "C2") (pinfunction "P$2_C2") (pintype "bidirectional"))
      (node (ref "D03") (pin "C2") (pinfunction "P$2_C2") (pintype "bidirectional"))
      (node (ref "D23") (pin "H1") (pinfunction "IN3A_H1") (pintype "input"))
      (node (ref "D23") (pin "J1") (pinfunction "IN3B_J1") (pintype "input"))
      (node (ref "E18") (pin "D2") (pinfunction "C_D2") (pintype "input"))
      (node (ref "E18") (pin "E2") (pinfunction "D_E2") (pintype "input"))
      (node (ref "E18") (pin "J1") (pinfunction "D_J1") (pintype "input"))
      (node (ref "E19") (pin "C1") (pinfunction "D_C1") (pintype "input"))
      (node (ref "E19") (pin "E2") (pinfunction "D_E2") (pintype "input"))
      (node (ref "E19") (pin "J1") (pinfunction "D_J1") (pintype "input"))
      (node (ref "E19") (pin "M2") (pinfunction "D_M2") (pintype "input"))
      (node (ref "E19") (pin "P1") (pinfunction "D_P1") (pintype "input"))
      (node (ref "E19") (pin "T2") (pinfunction "D_T2") (pintype "input"))
      (node (ref "E20") (pin "P1") (pinfunction "D_P1") (pintype "input"))
      (node (ref "E29") (pin "J1") (pinfunction "IN3B_J1") (pintype "input"))
      (node (ref "E30") (pin "A1") (pinfunction "IN1A_A1") (pintype "input"))
      (node (ref "E40") (pin "C2") (pinfunction "P$2_C2") (pintype "bidirectional"))
      (node (ref "EF01") (pin "BD1") (pinfunction "BD1_BD1") (pintype "input"))
      (node (ref "EF34") (pin "BD1") (pinfunction "BD1_BD1") (pintype "input"))
      (node (ref "EF34") (pin "BE2") (pinfunction "BE2_BE2") (pintype "input"))
      (node (ref "EF34") (pin "BN1") (pinfunction "BN1_BN1") (pintype "input"))
      (node (ref "EF35") (pin "BD1") (pinfunction "BD1_BD1") (pintype "input"))
      (node (ref "EF35") (pin "BE2") (pinfunction "BE2_BE2") (pintype "input"))
      (node (ref "EF35") (pin "BN1") (pinfunction "BN1_BN1") (pintype "input"))
      (node (ref "EF36") (pin "BD1") (pinfunction "BD1_BD1") (pintype "input"))
      (node (ref "EF36") (pin "BE2") (pinfunction "BE2_BE2") (pintype "input"))
      (node (ref "EF36") (pin "BN1") (pinfunction "BN1_BN1") (pintype "input"))
      (node (ref "EF37") (pin "BD1") (pinfunction "BD1_BD1") (pintype "input"))
      (node (ref "EF37") (pin "BE2") (pinfunction "BE2_BE2") (pintype "input"))
      (node (ref "EF38") (pin "BE2") (pinfunction "BE2_BE2") (pintype "input"))
      (node (ref "F40") (pin "C2") (pinfunction "P$2_C2") (pintype "bidirectional"))
      (node (ref "H07") (pin "E2") (pinfunction "SLOW_E2") (pintype "passive"))
      (node (ref "H07") (pin "L2") (pinfunction "SLOW_L2") (pintype "passive"))
      (node (ref "H07") (pin "R2") (pinfunction "SLOW_R2") (pintype "passive"))
      (node (ref "H08") (pin "E2") (pinfunction "SLOW_E2") (pintype "passive"))
      (node (ref "H08") (pin "L2") (pinfunction "SLOW_L2") (pintype "passive"))
      (node (ref "H08") (pin "R2") (pinfunction "SLOW_R2") (pintype "passive"))
      (node (ref "H09") (pin "E2") (pinfunction "SLOW_E2") (pintype "passive"))
      (node (ref "H09") (pin "L2") (pinfunction "SLOW_L2") (pintype "passive"))
      (node (ref "H09") (pin "R2") (pinfunction "SLOW_R2") (pintype "passive"))
      (node (ref "H10") (pin "E2") (pinfunction "SLOW_E2") (pintype "passive"))
      (node (ref "H10") (pin "L2") (pinfunction "SLOW_L2") (pintype "passive"))
      (node (ref "H10") (pin "R2") (pinfunction "SLOW_R2") (pintype "passive"))
      (node (ref "H11") (pin "E2") (pinfunction "SLOW_E2") (pintype "passive"))
      (node (ref "H11") (pin "L2") (pinfunction "SLOW_L2") (pintype "passive"))
      (node (ref "H11") (pin "R2") (pinfunction "SLOW_R2") (pintype "passive"))
      (node (ref "H12") (pin "E2") (pinfunction "SLOW_E2") (pintype "passive"))
      (node (ref "H12") (pin "L2") (pinfunction "SLOW_L2") (pintype "passive"))
      (node (ref "H12") (pin "R2") (pinfunction "SLOW_R2") (pintype "passive"))
      (node (ref "H13") (pin "E2") (pinfunction "SLOW_E2") (pintype "passive"))
      (node (ref "H13") (pin "L2") (pinfunction "SLOW_L2") (pintype "passive"))
      (node (ref "H13") (pin "R2") (pinfunction "SLOW_R2") (pintype "passive"))
      (node (ref "H14") (pin "E2") (pinfunction "SLOW_E2") (pintype "passive"))
      (node (ref "H14") (pin "L2") (pinfunction "SLOW_L2") (pintype "passive"))
      (node (ref "H14") (pin "R2") (pinfunction "SLOW_R2") (pintype "passive"))
      (node (ref "H15") (pin "E2") (pinfunction "SLOW_E2") (pintype "passive"))
      (node (ref "H15") (pin "L2") (pinfunction "SLOW_L2") (pintype "passive"))
      (node (ref "H15") (pin "R2") (pinfunction "SLOW_R2") (pintype "passive"))
      (node (ref "H16") (pin "E2") (pinfunction "SLOW_E2") (pintype "passive"))
      (node (ref "H16") (pin "L2") (pinfunction "SLOW_L2") (pintype "passive"))
      (node (ref "H16") (pin "R2") (pinfunction "SLOW_R2") (pintype "passive"))
      (node (ref "H17") (pin "E2") (pinfunction "SLOW_E2") (pintype "passive"))
      (node (ref "H17") (pin "L2") (pinfunction "SLOW_L2") (pintype "passive"))
      (node (ref "H17") (pin "R2") (pinfunction "SLOW_R2") (pintype "passive"))
      (node (ref "H18") (pin "E2") (pinfunction "SLOW_E2") (pintype "passive"))
      (node (ref "H18") (pin "L2") (pinfunction "SLOW_L2") (pintype "passive"))
      (node (ref "H18") (pin "R2") (pinfunction "SLOW_R2") (pintype "passive"))
      (node (ref "H19") (pin "E2") (pinfunction "SLOW_E2") (pintype "passive"))
      (node (ref "H19") (pin "L2") (pinfunction "SLOW_L2") (pintype "passive"))
      (node (ref "H19") (pin "R2") (pinfunction "SLOW_R2") (pintype "passive"))
      (node (ref "H20") (pin "E2") (pinfunction "SLOW_E2") (pintype "passive"))
      (node (ref "H20") (pin "L2") (pinfunction "SLOW_L2") (pintype "passive"))
      (node (ref "HJ34") (pin "AC2") (pinfunction "P$2_AC2") (pintype "bidirectional"))
      (node (ref "HJ34") (pin "BC2") (pinfunction "P$2_BC2") (pintype "bidirectional"))
    )
    (net (code "327") (name "HOLE1") (class "Default")
      (node (ref "C01") (pin "J2") (pinfunction "P$2_J2") (pintype "bidirectional"))
      (node (ref "C06") (pin "R2") (pinfunction "R_R2") (pintype "open_collector"))
    )
    (net (code "328") (name "HOLE2") (class "Default")
      (node (ref "C01") (pin "S2") (pinfunction "P$2_S2") (pintype "bidirectional"))
      (node (ref "C05") (pin "S2") (pinfunction "R_S2") (pintype "open_collector"))
    )
    (net (code "329") (name "HOLE3") (class "Default")
      (node (ref "C01") (pin "R2") (pinfunction "P$2_R2") (pintype "bidirectional"))
      (node (ref "C05") (pin "R2") (pinfunction "R_R2") (pintype "open_collector"))
    )
    (net (code "330") (name "HOLE4") (class "Default")
      (node (ref "C01") (pin "P2") (pinfunction "P$2_P2") (pintype "bidirectional"))
      (node (ref "C04") (pin "R2") (pinfunction "R_R2") (pintype "open_collector"))
    )
    (net (code "331") (name "HOLE5") (class "Default")
      (node (ref "C01") (pin "N2") (pinfunction "P$2_N2") (pintype "bidirectional"))
      (node (ref "C03") (pin "S2") (pinfunction "R_S2") (pintype "open_collector"))
    )
    (net (code "332") (name "HOLE6") (class "Default")
      (node (ref "C01") (pin "M2") (pinfunction "P$2_M2") (pintype "bidirectional"))
      (node (ref "C03") (pin "R2") (pinfunction "R_R2") (pintype "open_collector"))
    )
    (net (code "333") (name "HOLE7") (class "Default")
      (node (ref "C01") (pin "L2") (pinfunction "P$2_L2") (pintype "bidirectional"))
      (node (ref "C02") (pin "S2") (pinfunction "R_S2") (pintype "open_collector"))
    )
    (net (code "334") (name "HOLE8") (class "Default")
      (node (ref "C01") (pin "K2") (pinfunction "P$2_K2") (pintype "bidirectional"))
      (node (ref "C02") (pin "R2") (pinfunction "R_R2") (pintype "open_collector"))
    )
    (net (code "335") (name "HS") (class "Default")
      (node (ref "D07") (pin "B1") (pinfunction "IN2_B1") (pintype "input"))
      (node (ref "D11") (pin "P2") (pinfunction "1_P2") (pintype "output"))
    )
    (net (code "336") (name "HS_") (class "Default")
      (node (ref "C09") (pin "B1") (pinfunction "IN2_B1") (pintype "input"))
      (node (ref "C11") (pin "F1") (pinfunction "IN2_F1") (pintype "input"))
      (node (ref "D07") (pin "E1") (pinfunction "IN2_E1") (pintype "input"))
      (node (ref "D11") (pin "R2") (pinfunction "0_R2") (pintype "output"))
    )
    (net (code "337") (name "HZ880") (class "Default")
      (node (ref "F03") (pin "J2") (pinfunction "J2_J2") (pintype "output"))
      (node (ref "F03") (pin "P2") (pinfunction "P2_P2") (pintype "input"))
    )
    (net (code "338") (name "IB0") (class "Default")
      (node (ref "A17") (pin "J1") (pinfunction "IN2_J1") (pintype "input"))
      (node (ref "B17") (pin "P2") (pinfunction "1_P2") (pintype "output"))
    )
    (net (code "339") (name "IB1") (class "Default")
      (node (ref "A17") (pin "M1") (pinfunction "IN2_M1") (pintype "input"))
      (node (ref "B17") (pin "S1") (pinfunction "1_S1") (pintype "output"))
    )
    (net (code "340") (name "IB2") (class "Default")
      (node (ref "A17") (pin "R1") (pinfunction "IN2_R1") (pintype "input"))
      (node (ref "B17") (pin "V2") (pinfunction "1_V2") (pintype "output"))
    )
    (net (code "341") (name "IB_TO_IF") (class "Default")
      (node (ref "A15") (pin "A1") (pinfunction "IN1_A1") (pintype "input"))
      (node (ref "A17") (pin "C1") (pinfunction "OUT_C1") (pintype "output"))
      (node (ref "B05") (pin "D2") (pinfunction "C_D2") (pintype "input"))
      (node (ref "B17") (pin "B1") (pinfunction "C_B1") (pintype "input"))
      (node (ref "B17") (pin "D2") (pinfunction "C_D2") (pintype "input"))
      (node (ref "B17") (pin "H1") (pinfunction "C_H1") (pintype "input"))
    )
    (net (code "342") (name "IF0") (class "Default")
      (node (ref "A11") (pin "J1") (pinfunction "IN2_J1") (pintype "input"))
      (node (ref "A16") (pin "B1") (pinfunction "IN2_B1") (pintype "input"))
      (node (ref "B17") (pin "E1") (pinfunction "1_E1") (pintype "output"))
      (node (ref "B19") (pin "C1") (pinfunction "D_C1") (pintype "input"))
    )
    (net (code "343") (name "IF0_") (class "Default")
      (node (ref "B17") (pin "F1") (pinfunction "0_F1") (pintype "output"))
      (node (ref "C40") (pin "N1") (pinfunction "P$2_N1") (pintype "bidirectional"))
    )
    (net (code "344") (name "IF1") (class "Default")
      (node (ref "A11") (pin "M2") (pinfunction "IN2_M2") (pintype "input"))
      (node (ref "A16") (pin "J1") (pinfunction "IN2_J1") (pintype "input"))
      (node (ref "B17") (pin "H2") (pinfunction "1_H2") (pintype "output"))
      (node (ref "B19") (pin "E2") (pinfunction "D_E2") (pintype "input"))
    )
    (net (code "345") (name "IF1_") (class "Default")
      (node (ref "B17") (pin "J2") (pinfunction "0_J2") (pintype "output"))
      (node (ref "C40") (pin "C1") (pinfunction "P$2_C1") (pintype "bidirectional"))
    )
    (net (code "346") (name "IF2") (class "Default")
      (node (ref "A11") (pin "U2") (pinfunction "IN2_U2") (pintype "input"))
      (node (ref "A16") (pin "M2") (pinfunction "IN2_M2") (pintype "input"))
      (node (ref "B17") (pin "L1") (pinfunction "1_L1") (pintype "output"))
      (node (ref "B19") (pin "J1") (pinfunction "D_J1") (pintype "input"))
    )
    (net (code "347") (name "IF2_") (class "Default")
      (node (ref "B17") (pin "M1") (pinfunction "0_M1") (pintype "output"))
      (node (ref "C40") (pin "D1") (pinfunction "P$2_D1") (pintype "bidirectional"))
    )
    (net (code "348") (name "IFSR0") (class "Default")
      (node (ref "A18") (pin "E1") (pinfunction "IN2_E1") (pintype "input"))
      (node (ref "A40") (pin "H2") (pinfunction "P$2_H2") (pintype "bidirectional"))
    )
    (net (code "349") (name "IFSR1") (class "Default")
      (node (ref "A18") (pin "J2") (pinfunction "IN2_J2") (pintype "input"))
      (node (ref "A40") (pin "J2") (pinfunction "P$2_J2") (pintype "bidirectional"))
    )
    (net (code "350") (name "IFSR2") (class "Default")
      (node (ref "A18") (pin "R1") (pinfunction "IN2_R1") (pintype "input"))
      (node (ref "A40") (pin "K2") (pinfunction "P$2_K2") (pintype "bidirectional"))
    )
    (net (code "351") (name "IF_ENABLE") (class "Default")
      (node (ref "A16") (pin "A1") (pinfunction "IN1_A1") (pintype "input"))
      (node (ref "A16") (pin "H1") (pinfunction "IN1_H1") (pintype "input"))
      (node (ref "A16") (pin "L2") (pinfunction "IN1_L2") (pintype "input"))
      (node (ref "B11") (pin "F1") (pinfunction "0_F1") (pintype "output"))
    )
    (net (code "352") (name "IF_ENABLE_") (class "Default")
      (node (ref "B11") (pin "C1") (pinfunction "D_C1") (pintype "input"))
      (node (ref "B20") (pin "H2") (pinfunction "OUT_H2") (pintype "output"))
    )
    (net (code "353") (name "IF_TO_SF") (class "Default")
      (node (ref "A19") (pin "S1") (pinfunction "OUT_S1") (pintype "output"))
      (node (ref "B05") (pin "N1") (pinfunction "C_N1") (pintype "input"))
      (node (ref "B19") (pin "B1") (pinfunction "C_B1") (pintype "input"))
      (node (ref "B19") (pin "D2") (pinfunction "C_D2") (pintype "input"))
      (node (ref "B21") (pin "M2") (pinfunction "IN2_M2") (pintype "input"))
      (node (ref "B21") (pin "R1") (pinfunction "IN2_R1") (pintype "input"))
      (node (ref "B21") (pin "R2") (pinfunction "IN2_R2") (pintype "input"))
    )
    (net (code "354") (name "INDEX_MARKERS") (class "Default")
      (node (ref "HJ32") (pin "AD2") (pinfunction "AD2_AD2") (pintype "input"))
      (node (ref "HJ34") (pin "BH2") (pinfunction "P$2_BH2") (pintype "bidirectional"))
      (node (ref "J33") (pin "J1") (pinfunction "J1_J1") (pintype "input"))
    )
    (net (code "355") (name "INHIBIT_") (class "Default")
      (node (ref "B22") (pin "R2") (pinfunction "0_R2") (pintype "output"))
      (node (ref "B30") (pin "K2") (pinfunction "IN1_K2") (pintype "input"))
    )
    (net (code "356") (name "INITIALIZE") (class "Default")
      (node (ref "C12") (pin "H1") (pinfunction "IN2_H1") (pintype "input"))
      (node (ref "EF01") (pin "BF2") (pinfunction "BF2_BF2") (pintype "input"))
      (node (ref "EF02") (pin "BE2") (pinfunction "BE2_BE2") (pintype "input"))
      (node (ref "F20") (pin "S2") (pinfunction "OUT_S2") (pintype "output"))
      (node (ref "HJ23") (pin "AH2") (pinfunction "AH2_AH2") (pintype "input"))
      (node (ref "HJ29") (pin "BN2") (pinfunction "BN2_BN2") (pintype "input"))
    )
    (net (code "357") (name "INITIALIZE_") (class "Default")
      (node (ref "A04") (pin "S2") (pinfunction "S2_S2") (pintype "input"))
      (node (ref "B05") (pin "K2") (pinfunction "R_K2") (pintype "input"))
      (node (ref "B07") (pin "L1") (pinfunction "IN2_L1") (pintype "input"))
      (node (ref "C12") (pin "L1") (pinfunction "OUT_L1") (pintype "open_collector"))
      (node (ref "E19") (pin "K2") (pinfunction "R_K2") (pintype "input"))
      (node (ref "H12") (pin "U2") (pinfunction "IN2_U2") (pintype "input"))
      (node (ref "H30") (pin "P1") (pinfunction "P1_P1") (pintype "input"))
      (node (ref "HJ26") (pin "BP1") (pinfunction "BP1_BP1") (pintype "input"))
      (node (ref "HJ28") (pin "AS2") (pinfunction "AS2_AS2") (pintype "input"))
      (node (ref "HJ32") (pin "BS2") (pinfunction "BS2_BS2") (pintype "input"))
      (node (ref "J33") (pin "N1") (pinfunction "N1_N1") (pintype "input"))
    )
    (net (code "358") (name "INPUT_BUS00") (class "Default")
      (node (ref "EF34") (pin "BK1") (pinfunction "BK1_BK1") (pintype "input"))
      (node (ref "J13") (pin "E1") (pinfunction "OUT_E1") (pintype "output"))
    )
    (net (code "359") (name "INPUT_BUS01") (class "Default")
      (node (ref "EF34") (pin "BM1") (pinfunction "BM1_BM1") (pintype "input"))
      (node (ref "J13") (pin "J2") (pinfunction "OUT_J2") (pintype "output"))
    )
    (net (code "360") (name "INPUT_BUS02") (class "Default")
      (node (ref "EF35") (pin "BK1") (pinfunction "BK1_BK1") (pintype "input"))
      (node (ref "J13") (pin "L1") (pinfunction "OUT_L1") (pintype "output"))
    )
    (net (code "361") (name "INPUT_BUS03") (class "Default")
      (node (ref "EF35") (pin "BM1") (pinfunction "BM1_BM1") (pintype "input"))
      (node (ref "J13") (pin "P2") (pinfunction "OUT_P2") (pintype "output"))
    )
    (net (code "362") (name "INPUT_BUS04") (class "Default")
      (node (ref "EF36") (pin "BK1") (pinfunction "BK1_BK1") (pintype "input"))
      (node (ref "J13") (pin "S1") (pinfunction "OUT_S1") (pintype "output"))
    )
    (net (code "363") (name "INPUT_BUS05") (class "Default")
      (node (ref "EF36") (pin "BM1") (pinfunction "BM1_BM1") (pintype "input"))
      (node (ref "J13") (pin "V2") (pinfunction "OUT_V2") (pintype "output"))
    )
    (net (code "364") (name "INPUT_BUS06") (class "Default")
      (node (ref "EF37") (pin "BK1") (pinfunction "BK1_BK1") (pintype "input"))
      (node (ref "J14") (pin "E1") (pinfunction "OUT_E1") (pintype "output"))
    )
    (net (code "365") (name "INPUT_BUS07") (class "Default")
      (node (ref "EF37") (pin "BM1") (pinfunction "BM1_BM1") (pintype "input"))
      (node (ref "J14") (pin "J2") (pinfunction "OUT_J2") (pintype "output"))
    )
    (net (code "366") (name "INPUT_BUS08") (class "Default")
      (node (ref "EF38") (pin "BK1") (pinfunction "BK1_BK1") (pintype "input"))
      (node (ref "J14") (pin "L1") (pinfunction "OUT_L1") (pintype "output"))
    )
    (net (code "367") (name "INPUT_BUS09") (class "Default")
      (node (ref "EF38") (pin "BM1") (pinfunction "BM1_BM1") (pintype "input"))
      (node (ref "J14") (pin "P2") (pinfunction "OUT_P2") (pintype "output"))
    )
    (net (code "368") (name "INPUT_BUS10") (class "Default")
      (node (ref "EF39") (pin "BK1") (pinfunction "BK1_BK1") (pintype "input"))
      (node (ref "J14") (pin "S1") (pinfunction "OUT_S1") (pintype "output"))
    )
    (net (code "369") (name "INPUT_BUS11") (class "Default")
      (node (ref "EF39") (pin "BM1") (pinfunction "BM1_BM1") (pintype "input"))
      (node (ref "J14") (pin "V2") (pinfunction "OUT_V2") (pintype "output"))
    )
    (net (code "370") (name "INT_DELAY") (class "Default")
      (node (ref "E25") (pin "F2") (pinfunction "IN3_F2") (pintype "input"))
      (node (ref "E33") (pin "R2") (pinfunction "0_R2") (pintype "output"))
    )
    (net (code "371") (name "INT_ENABLE") (class "Default")
      (node (ref "E33") (pin "N2") (pinfunction "S_N2") (pintype "input"))
      (node (ref "E33") (pin "U1") (pinfunction "0_U1") (pintype "output"))
    )
    (net (code "372") (name "INT_ENABLE_") (class "Default")
      (node (ref "D40") (pin "D1") (pinfunction "P$2_D1") (pintype "bidirectional"))
      (node (ref "E33") (pin "M2") (pinfunction "D_M2") (pintype "input"))
      (node (ref "E33") (pin "S1") (pinfunction "1_S1") (pintype "output"))
    )
    (net (code "373") (name "INT_INHIBIT") (class "Default")
      (node (ref "A15") (pin "E1") (pinfunction "IN2_E1") (pintype "input"))
      (node (ref "F11") (pin "J2") (pinfunction "OUT_J2") (pintype "output"))
    )
    (net (code "374") (name "INT_INHIBIT_") (class "Default")
      (node (ref "A15") (pin "F1") (pinfunction "OUT_F1") (pintype "output"))
      (node (ref "E25") (pin "E2") (pinfunction "IN2_E2") (pintype "input"))
      (node (ref "F11") (pin "D2") (pinfunction "IN1_D2") (pintype "input"))
    )
    (net (code "375") (name "INT_OK") (class "Default")
      (node (ref "C12") (pin "K2") (pinfunction "IN1_K2") (pintype "input"))
      (node (ref "E24") (pin "J2") (pinfunction "IN2_J2") (pintype "input"))
      (node (ref "E26") (pin "U1") (pinfunction "IN1B_U1") (pintype "input"))
      (node (ref "F21") (pin "N1") (pinfunction "OUT_N1") (pintype "output"))
    )
    (net (code "376") (name "INT_OK_") (class "Default")
      (node (ref "E25") (pin "H2") (pinfunction "OUT_H2") (pintype "output"))
      (node (ref "F21") (pin "M1") (pinfunction "IN2_M1") (pintype "input"))
      (node (ref "F23") (pin "D2") (pinfunction "IN1_D2") (pintype "input"))
      (node (ref "F27") (pin "F2") (pinfunction "IN3_F2") (pintype "input"))
    )
    (net (code "377") (name "INT_RQST") (class "Default")
      (node (ref "F11") (pin "R2") (pinfunction "IN1_R2") (pintype "input"))
      (node (ref "J15") (pin "J2") (pinfunction "OUT_J2") (pintype "output"))
    )
    (net (code "378") (name "INT_SKIP_ENABLE_") (class "Default")
      (node (ref "F09") (pin "L2") (pinfunction "IN6_L2") (pintype "input"))
      (node (ref "F11") (pin "M1") (pinfunction "IN1_M1") (pintype "input"))
      (node (ref "F28") (pin "J1") (pinfunction "OUT_J1") (pintype "output"))
    )
    (net (code "379") (name "INT_STROBE") (class "Default")
      (node (ref "E14") (pin "S2") (pinfunction "OUT_S2") (pintype "output"))
      (node (ref "E15") (pin "L2") (pinfunction "IN1_L2") (pintype "input"))
      (node (ref "E33") (pin "H1") (pinfunction "C_H1") (pintype "input"))
      (node (ref "F19") (pin "F1") (pinfunction "IN1_F1") (pintype "input"))
      (node (ref "F21") (pin "H1") (pinfunction "IN1_H1") (pintype "input"))
    )
    (net (code "380") (name "INT_STROBE_") (class "Default")
      (node (ref "C12") (pin "M2") (pinfunction "IN3_M2") (pintype "input"))
      (node (ref "E15") (pin "N2") (pinfunction "OUT_N2") (pintype "output"))
      (node (ref "E19") (pin "K1") (pinfunction "S_K1") (pintype "input"))
    )
    (net (code "381") (name "INT_SYNC") (class "Default")
      (node (ref "E25") (pin "D2") (pinfunction "IN1_D2") (pintype "input"))
      (node (ref "E33") (pin "M1") (pinfunction "0_M1") (pintype "output"))
    )
    (net (code "382") (name "IN_STOP_2_") (class "Default")
      (node (ref "EF01") (pin "BR2") (pinfunction "BR2_BR2") (pintype "input"))
      (node (ref "EF01") (pin "BV2") (pinfunction "BV2_BV2") (pintype "output"))
    )
    (net (code "383") (name "IOP1") (class "Default")
      (node (ref "B07") (pin "K2") (pinfunction "IN2_K2") (pintype "input"))
      (node (ref "E19") (pin "P2") (pinfunction "1_P2") (pintype "output"))
      (node (ref "EF01") (pin "BD2") (pinfunction "BD2_BD2") (pintype "input"))
      (node (ref "EF02") (pin "BH2") (pinfunction "BH2_BH2") (pintype "input"))
      (node (ref "HJ23") (pin "AR1") (pinfunction "AR1_AR1") (pintype "input"))
      (node (ref "HJ26") (pin "AU2") (pinfunction "AU2_AU2") (pintype "input"))
      (node (ref "HJ28") (pin "AR2") (pinfunction "AR2_AR2") (pintype "input"))
      (node (ref "HJ29") (pin "BH2") (pinfunction "BH2_BH2") (pintype "input"))
    )
    (net (code "384") (name "IOP1_") (class "Default")
      (node (ref "E09") (pin "M2") (pinfunction "IN2_M2") (pintype "input"))
      (node (ref "E19") (pin "R2") (pinfunction "0_R2") (pintype "output"))
      (node (ref "F11") (pin "H1") (pinfunction "IN2_H1") (pintype "input"))
      (node (ref "H11") (pin "H2") (pinfunction "IN2_H2") (pintype "input"))
      (node (ref "H30") (pin "L2") (pinfunction "L2_L2") (pintype "input"))
      (node (ref "HJ29") (pin "BL2") (pinfunction "BL2_BL2") (pintype "input"))
    )
    (net (code "385") (name "IOP1_CLR") (class "Default")
      (node (ref "E19") (pin "L2") (pinfunction "C_L2") (pintype "input"))
      (node (ref "F14") (pin "J1") (pinfunction "OUT_J1") (pintype "output"))
    )
    (net (code "386") (name "IOP1_SET_") (class "Default")
      (node (ref "E14") (pin "S1") (pinfunction "IN3_S1") (pintype "input"))
      (node (ref "E19") (pin "N2") (pinfunction "S_N2") (pintype "input"))
      (node (ref "F20") (pin "F2") (pinfunction "OUT_F2") (pintype "output"))
    )
    (net (code "387") (name "IOP2") (class "Default")
      (node (ref "A04") (pin "M2") (pinfunction "M2_M2") (pintype "input"))
      (node (ref "E19") (pin "S1") (pinfunction "1_S1") (pintype "output"))
      (node (ref "EF01") (pin "BJ2") (pinfunction "BJ2_BJ2") (pintype "input"))
      (node (ref "EF02") (pin "BD2") (pinfunction "BD2_BD2") (pintype "input"))
      (node (ref "HJ23") (pin "AJ2") (pinfunction "AJ2_AJ2") (pintype "input"))
      (node (ref "HJ26") (pin "AV2") (pinfunction "AV2_AV2") (pintype "input"))
      (node (ref "HJ28") (pin "AR1") (pinfunction "AR1_AR1") (pintype "input"))
      (node (ref "HJ29") (pin "BP2") (pinfunction "BP2_BP2") (pintype "input"))
    )
    (net (code "388") (name "IOP2_") (class "Default")
      (node (ref "E09") (pin "R1") (pinfunction "IN2_R1") (pintype "input"))
      (node (ref "E19") (pin "U1") (pinfunction "0_U1") (pintype "output"))
      (node (ref "F11") (pin "J1") (pinfunction "IN3_J1") (pintype "input"))
      (node (ref "H11") (pin "N2") (pinfunction "IN2_N2") (pintype "input"))
      (node (ref "H30") (pin "R1") (pinfunction "R1_R1") (pintype "input"))
      (node (ref "HJ29") (pin "BM2") (pinfunction "BM2_BM2") (pintype "input"))
    )
    (net (code "389") (name "IOP2_CLR") (class "Default")
      (node (ref "E19") (pin "N1") (pinfunction "C_N1") (pintype "input"))
      (node (ref "F16") (pin "J1") (pinfunction "OUT_J1") (pintype "output"))
    )
    (net (code "390") (name "IOP2_SET_") (class "Default")
      (node (ref "E14") (pin "R1") (pinfunction "IN2_R1") (pintype "input"))
      (node (ref "E19") (pin "R1") (pinfunction "S_R1") (pintype "input"))
      (node (ref "F20") (pin "K1") (pinfunction "OUT_K1") (pintype "output"))
    )
    (net (code "391") (name "IOP4") (class "Default")
      (node (ref "B07") (pin "E1") (pinfunction "IN1_E1") (pintype "input"))
      (node (ref "E19") (pin "V2") (pinfunction "1_V2") (pintype "output"))
      (node (ref "EF01") (pin "AL2") (pinfunction "AL2_AL2") (pintype "input"))
      (node (ref "EF02") (pin "AS1") (pinfunction "AS1_AS1") (pintype "input"))
      (node (ref "HJ23") (pin "BD2") (pinfunction "BD2_BD2") (pintype "input"))
      (node (ref "HJ26") (pin "BK1") (pinfunction "BK1_BK1") (pintype "input"))
      (node (ref "HJ28") (pin "AP2") (pinfunction "AP2_AP2") (pintype "input"))
      (node (ref "HJ29") (pin "BT2") (pinfunction "BT2_BT2") (pintype "input"))
    )
    (net (code "392") (name "IOP4_") (class "Default")
      (node (ref "E09") (pin "R2") (pinfunction "IN2_R2") (pintype "input"))
      (node (ref "E19") (pin "V1") (pinfunction "0_V1") (pintype "output"))
      (node (ref "F11") (pin "K1") (pinfunction "IN4_K1") (pintype "input"))
      (node (ref "H11") (pin "U2") (pinfunction "IN2_U2") (pintype "input"))
      (node (ref "H30") (pin "F2") (pinfunction "F2_F2") (pintype "input"))
    )
    (net (code "393") (name "IOP4_CLR") (class "Default")
      (node (ref "E19") (pin "S2") (pinfunction "C_S2") (pintype "input"))
      (node (ref "F18") (pin "J1") (pinfunction "OUT_J1") (pintype "output"))
    )
    (net (code "394") (name "IOP4_SET_") (class "Default")
      (node (ref "E14") (pin "P1") (pinfunction "IN1_P1") (pintype "input"))
      (node (ref "E19") (pin "U2") (pinfunction "S_U2") (pintype "input"))
      (node (ref "F20") (pin "K2") (pinfunction "OUT_K2") (pintype "output"))
    )
    (net (code "395") (name "IOP124_") (class "Default")
      (node (ref "E09") (pin "T2") (pinfunction "IN1_T2") (pintype "input"))
      (node (ref "E11") (pin "S1") (pinfunction "OUT_S1") (pintype "output"))
      (node (ref "F30") (pin "D2") (pinfunction "IN1_D2") (pintype "input"))
    )
    (net (code "396") (name "IOT") (class "Default")
      (node (ref "A06") (pin "F1") (pinfunction "OUT_F1") (pintype "output"))
      (node (ref "A14") (pin "E1") (pinfunction "IN2_E1") (pintype "input"))
      (node (ref "C12") (pin "F2") (pinfunction "IN3_F2") (pintype "input"))
      (node (ref "C12") (pin "H2") (pinfunction "IN4_H2") (pintype "input"))
      (node (ref "D09") (pin "F1") (pinfunction "IN2_F1") (pintype "input"))
      (node (ref "D10") (pin "K2") (pinfunction "IN1_K2") (pintype "input"))
      (node (ref "E26") (pin "M2") (pinfunction "IN3B_M2") (pintype "input"))
      (node (ref "F09") (pin "F2") (pinfunction "IN7_F2") (pintype "input"))
      (node (ref "F19") (pin "R2") (pinfunction "IN1_R2") (pintype "input"))
      (node (ref "F20") (pin "R1") (pinfunction "IN2_R1") (pintype "input"))
    )
    (net (code "397") (name "IOT632") (class "Default")
      (node (ref "HJ32") (pin "BM2") (pinfunction "BM2_BM2") (pintype "input"))
      (node (ref "J33") (pin "P1") (pinfunction "P1_P1") (pintype "output"))
    )
    (net (code "398") (name "IOT634") (class "Default")
      (node (ref "HJ32") (pin "AH1") (pinfunction "AH1_AH1") (pintype "input"))
      (node (ref "J33") (pin "R1") (pinfunction "R1_R1") (pintype "output"))
    )
    (net (code "399") (name "IOT_") (class "Default")
      (node (ref "A06") (pin "D1") (pinfunction "IN1_D1") (pintype "input"))
      (node (ref "D40") (pin "H2") (pinfunction "P$2_H2") (pintype "bidirectional"))
      (node (ref "F11") (pin "E1") (pinfunction "OUT_E1") (pintype "output"))
    )
    (net (code "400") (name "IOT_OPR_") (class "Default")
      (node (ref "E24") (pin "F2") (pinfunction "OUT_F2") (pintype "output"))
      (node (ref "E25") (pin "J2") (pinfunction "IN1_J2") (pintype "input"))
      (node (ref "F23") (pin "F1") (pinfunction "IN1_F1") (pintype "input"))
    )
    (net (code "401") (name "IO_BUS_IN00_") (class "Default")
      (node (ref "HJ31") (pin "AF2") (pinfunction "AF2_AF2") (pintype "open_collector"))
      (node (ref "HJ32") (pin "AF1") (pinfunction "AF1_AF1") (pintype "open_collector"))
      (node (ref "J13") (pin "B1") (pinfunction "IN2_B1") (pintype "passive"))
    )
    (net (code "402") (name "IO_BUS_IN01_") (class "Default")
      (node (ref "HJ31") (pin "BD1") (pinfunction "BD1_BD1") (pintype "open_collector"))
      (node (ref "HJ32") (pin "AF2") (pinfunction "AF2_AF2") (pintype "open_collector"))
      (node (ref "J13") (pin "E2") (pinfunction "IN2_E2") (pintype "passive"))
    )
    (net (code "403") (name "IO_BUS_IN02_") (class "Default")
      (node (ref "HJ31") (pin "AF1") (pinfunction "AF1_AF1") (pintype "open_collector"))
      (node (ref "HJ32") (pin "AH2") (pinfunction "AH2_AH2") (pintype "open_collector"))
      (node (ref "J13") (pin "H1") (pinfunction "IN2_H1") (pintype "passive"))
    )
    (net (code "404") (name "IO_BUS_IN03_") (class "Default")
      (node (ref "HJ31") (pin "BB1") (pinfunction "BB1_BB1") (pintype "open_collector"))
      (node (ref "HJ32") (pin "AJ2") (pinfunction "AJ2_AJ2") (pintype "open_collector"))
      (node (ref "J13") (pin "L2") (pinfunction "IN2_L2") (pintype "passive"))
    )
    (net (code "405") (name "IO_BUS_IN04_") (class "Default")
      (node (ref "HJ26") (pin "AP2") (pinfunction "AP2_AP2") (pintype "open_collector"))
      (node (ref "HJ31") (pin "AJ2") (pinfunction "AJ2_AJ2") (pintype "open_collector"))
      (node (ref "HJ32") (pin "AN2") (pinfunction "AN2_AN2") (pintype "open_collector"))
      (node (ref "J13") (pin "N1") (pinfunction "IN2_N1") (pintype "passive"))
    )
    (net (code "406") (name "IO_BUS_IN05_") (class "Default")
      (node (ref "HJ26") (pin "AS2") (pinfunction "AS2_AS2") (pintype "open_collector"))
      (node (ref "HJ31") (pin "AU1") (pinfunction "AU1_AU1") (pintype "open_collector"))
      (node (ref "HJ32") (pin "AM2") (pinfunction "AM2_AM2") (pintype "open_collector"))
      (node (ref "J13") (pin "S2") (pinfunction "IN2_S2") (pintype "passive"))
    )
    (net (code "407") (name "IO_BUS_IN06_") (class "Default")
      (node (ref "HJ26") (pin "AR1") (pinfunction "AR1_AR1") (pintype "open_collector"))
      (node (ref "HJ31") (pin "AJ1") (pinfunction "AJ1_AJ1") (pintype "open_collector"))
      (node (ref "HJ32") (pin "AU2") (pinfunction "AU2_AU2") (pintype "open_collector"))
      (node (ref "J14") (pin "B1") (pinfunction "IN2_B1") (pintype "passive"))
    )
    (net (code "408") (name "IO_BUS_IN07_") (class "Default")
      (node (ref "HJ26") (pin "AN2") (pinfunction "AN2_AN2") (pintype "open_collector"))
      (node (ref "HJ31") (pin "AV2") (pinfunction "AV2_AV2") (pintype "open_collector"))
      (node (ref "HJ32") (pin "AV2") (pinfunction "AV2_AV2") (pintype "open_collector"))
      (node (ref "J14") (pin "E2") (pinfunction "IN2_E2") (pintype "passive"))
    )
    (net (code "409") (name "IO_BUS_IN08_") (class "Default")
      (node (ref "HJ26") (pin "AS1") (pinfunction "AS1_AS1") (pintype "open_collector"))
      (node (ref "HJ31") (pin "AM1") (pinfunction "AM1_AM1") (pintype "open_collector"))
      (node (ref "HJ32") (pin "BP2") (pinfunction "BP2_BP2") (pintype "open_collector"))
      (node (ref "J14") (pin "H1") (pinfunction "IN2_H1") (pintype "passive"))
    )
    (net (code "410") (name "IO_BUS_IN09_") (class "Default")
      (node (ref "HJ26") (pin "AP1") (pinfunction "AP1_AP1") (pintype "open_collector"))
      (node (ref "HJ31") (pin "AP2") (pinfunction "AP2_AP2") (pintype "open_collector"))
      (node (ref "HJ32") (pin "BN2") (pinfunction "BN2_BN2") (pintype "open_collector"))
      (node (ref "J14") (pin "L2") (pinfunction "IN2_L2") (pintype "passive"))
    )
    (net (code "411") (name "IO_BUS_IN10_") (class "Default")
      (node (ref "HJ26") (pin "AR2") (pinfunction "AR2_AR2") (pintype "open_collector"))
      (node (ref "HJ31") (pin "AM2") (pinfunction "AM2_AM2") (pintype "open_collector"))
      (node (ref "HJ32") (pin "BJ2") (pinfunction "BJ2_BJ2") (pintype "open_collector"))
      (node (ref "J14") (pin "N1") (pinfunction "IN2_N1") (pintype "passive"))
    )
    (net (code "412") (name "IO_BUS_IN11_") (class "Default")
      (node (ref "HJ26") (pin "AN1") (pinfunction "AN1_AN1") (pintype "open_collector"))
      (node (ref "HJ31") (pin "AS1") (pinfunction "AS1_AS1") (pintype "open_collector"))
      (node (ref "HJ32") (pin "BH2") (pinfunction "BH2_BH2") (pintype "open_collector"))
      (node (ref "J14") (pin "S2") (pinfunction "IN2_S2") (pintype "passive"))
    )
    (net (code "413") (name "IO_BUS_IN_AC_CLR_") (class "Default")
      (node (ref "J15") (pin "H1") (pinfunction "IN2_H1") (pintype "passive"))
    )
    (net (code "414") (name "IO_BUS_IN_INT_") (class "Default")
      (node (ref "H30") (pin "C1") (pinfunction "C1_C1") (pintype "open_collector"))
      (node (ref "HJ23") (pin "BP2") (pinfunction "BP2_BP2") (pintype "open_collector"))
      (node (ref "HJ26") (pin "AL2") (pinfunction "AL2_AL2") (pintype "open_collector"))
      (node (ref "HJ28") (pin "BS2") (pinfunction "BS2_BS2") (pintype "open_collector"))
      (node (ref "HJ29") (pin "BF2") (pinfunction "BF2_BF2") (pintype "open_collector"))
      (node (ref "J15") (pin "E2") (pinfunction "IN2_E2") (pintype "passive"))
      (node (ref "J33") (pin "N2") (pinfunction "N2_N2") (pintype "open_collector"))
    )
    (net (code "415") (name "IO_BUS_IN_SKIP_") (class "Default")
      (node (ref "H30") (pin "H1") (pinfunction "H1_H1") (pintype "open_collector"))
      (node (ref "HJ23") (pin "BR2") (pinfunction "BR2_BR2") (pintype "open_collector"))
      (node (ref "HJ26") (pin "AK2") (pinfunction "AK2_AK2") (pintype "open_collector"))
      (node (ref "HJ28") (pin "BN2") (pinfunction "BN2_BN2") (pintype "open_collector"))
      (node (ref "HJ29") (pin "BE2") (pinfunction "BE2_BE2") (pintype "open_collector"))
      (node (ref "J15") (pin "B1") (pinfunction "IN2_B1") (pintype "passive"))
      (node (ref "J33") (pin "P2") (pinfunction "P2_P2") (pintype "open_collector"))
    )
    (net (code "416") (name "IO_ENABLE") (class "Default")
      (node (ref "E28") (pin "J2") (pinfunction "IN2A_J2") (pintype "input"))
      (node (ref "E30") (pin "J2") (pinfunction "IN2A_J2") (pintype "input"))
      (node (ref "EF34") (pin "BL2") (pinfunction "BL2_BL2") (pintype "input"))
      (node (ref "EF35") (pin "BL2") (pinfunction "BL2_BL2") (pintype "input"))
      (node (ref "EF36") (pin "BL2") (pinfunction "BL2_BL2") (pintype "input"))
      (node (ref "EF37") (pin "BL2") (pinfunction "BL2_BL2") (pintype "input"))
      (node (ref "EF38") (pin "BL2") (pinfunction "BL2_BL2") (pintype "input"))
      (node (ref "EF39") (pin "BL2") (pinfunction "BL2_BL2") (pintype "input"))
      (node (ref "F30") (pin "J2") (pinfunction "OUT_J2") (pintype "open_collector"))
    )
    (net (code "417") (name "IO_END") (class "Default")
      (node (ref "E12") (pin "H1") (pinfunction "IN1_H1") (pintype "input"))
      (node (ref "E20") (pin "N1") (pinfunction "C_N1") (pintype "input"))
      (node (ref "F18") (pin "F1") (pinfunction "OUT_F1") (pintype "output"))
    )
    (net (code "418") (name "IO_END_") (class "Default")
      (node (ref "E12") (pin "E2") (pinfunction "IN2_E2") (pintype "input"))
      (node (ref "E12") (pin "K1") (pinfunction "OUT_K1") (pintype "output"))
      (node (ref "E14") (pin "R2") (pinfunction "IN3_R2") (pintype "input"))
    )
    (net (code "419") (name "IO_ON") (class "Default")
      (node (ref "E09") (pin "U2") (pinfunction "IN2_U2") (pintype "input"))
      (node (ref "E20") (pin "S1") (pinfunction "1_S1") (pintype "output"))
    )
    (net (code "420") (name "IO_PC_ENABLE_") (class "Default")
      (node (ref "E09") (pin "V2") (pinfunction "OUT_V2") (pintype "output"))
      (node (ref "F09") (pin "K1") (pinfunction "IN4_K1") (pintype "input"))
      (node (ref "F11") (pin "N1") (pinfunction "IN2_N1") (pintype "input"))
    )
    (net (code "421") (name "IO_PC_LOAD") (class "Default")
      (node (ref "F32") (pin "L2") (pinfunction "IN1_L2") (pintype "input"))
      (node (ref "J11") (pin "V2") (pinfunction "P$2_V2") (pintype "bidirectional"))
    )
    (net (code "422") (name "IO_SKIP") (class "Default")
      (node (ref "E28") (pin "K2") (pinfunction "IN2B_K2") (pintype "input"))
      (node (ref "J15") (pin "E1") (pinfunction "OUT_E1") (pintype "output"))
    )
    (net (code "423") (name "IO_START_") (class "Default")
      (node (ref "E12") (pin "D1") (pinfunction "IN1_D1") (pintype "input"))
      (node (ref "E15") (pin "R2") (pinfunction "IN2_R2") (pintype "input"))
      (node (ref "E15") (pin "S1") (pinfunction "OUT_S1") (pintype "output"))
      (node (ref "E20") (pin "R1") (pinfunction "S_R1") (pintype "input"))
    )
    (net (code "424") (name "IO_STROBE") (class "Default")
      (node (ref "E26") (pin "L2") (pinfunction "IN3A_L2") (pintype "input"))
      (node (ref "F12") (pin "F1") (pinfunction "OUT_F1") (pintype "output"))
      (node (ref "F25") (pin "T2") (pinfunction "IN1_T2") (pintype "input"))
    )
    (net (code "425") (name "IPC_ENABLE") (class "Default")
      (node (ref "F09") (pin "P2") (pinfunction "OUT_P2") (pintype "output"))
      (node (ref "F20") (pin "L2") (pinfunction "IN1_L2") (pintype "input"))
    )
    (net (code "426") (name "IR0") (class "Default")
      (node (ref "E20") (pin "F1") (pinfunction "0_F1") (pintype "output"))
      (node (ref "E21") (pin "K1") (pinfunction "IN1_K1") (pintype "input"))
      (node (ref "E21") (pin "N2") (pinfunction "IN1_N2") (pintype "input"))
      (node (ref "E21") (pin "P1") (pinfunction "IN1_P1") (pintype "input"))
      (node (ref "E21") (pin "T2") (pinfunction "IN1_T2") (pintype "input"))
      (node (ref "E24") (pin "D2") (pinfunction "IN1_D2") (pintype "input"))
      (node (ref "F11") (pin "A1") (pinfunction "IN1_A1") (pintype "input"))
    )
    (net (code "427") (name "IR0_") (class "Default")
      (node (ref "E20") (pin "E1") (pinfunction "1_E1") (pintype "output"))
      (node (ref "E21") (pin "A1") (pinfunction "IN1_A1") (pintype "input"))
      (node (ref "E21") (pin "D2") (pinfunction "IN1_D2") (pintype "input"))
      (node (ref "E21") (pin "E1") (pinfunction "IN1_E1") (pintype "input"))
      (node (ref "E21") (pin "J2") (pinfunction "IN1_J2") (pintype "input"))
    )
    (net (code "428") (name "IR1") (class "Default")
      (node (ref "E20") (pin "H2") (pinfunction "1_H2") (pintype "output"))
      (node (ref "E21") (pin "F1") (pinfunction "IN2_F1") (pintype "input"))
      (node (ref "E21") (pin "K2") (pinfunction "IN2_K2") (pintype "input"))
      (node (ref "E21") (pin "P2") (pinfunction "IN2_P2") (pintype "input"))
      (node (ref "E21") (pin "U2") (pinfunction "IN2_U2") (pintype "input"))
      (node (ref "E24") (pin "E2") (pinfunction "IN2_E2") (pintype "input"))
      (node (ref "F11") (pin "B1") (pinfunction "IN2_B1") (pintype "input"))
    )
    (net (code "429") (name "IR1_") (class "Default")
      (node (ref "E20") (pin "J2") (pinfunction "0_J2") (pintype "output"))
      (node (ref "E21") (pin "B1") (pinfunction "IN2_B1") (pintype "input"))
      (node (ref "E21") (pin "E2") (pinfunction "IN2_E2") (pintype "input"))
      (node (ref "E21") (pin "L1") (pinfunction "IN2_L1") (pintype "input"))
      (node (ref "E21") (pin "R1") (pinfunction "IN2_R1") (pintype "input"))
    )
    (net (code "430") (name "IR2") (class "Default")
      (node (ref "E20") (pin "L1") (pinfunction "1_L1") (pintype "output"))
      (node (ref "E21") (pin "C1") (pinfunction "IN3_C1") (pintype "input"))
      (node (ref "E21") (pin "L2") (pinfunction "IN3_L2") (pintype "input"))
      (node (ref "E21") (pin "S1") (pinfunction "IN3_S1") (pintype "input"))
      (node (ref "E21") (pin "V2") (pinfunction "IN3_V2") (pintype "input"))
    )
    (net (code "431") (name "IR2_") (class "Default")
      (node (ref "E20") (pin "M1") (pinfunction "0_M1") (pintype "output"))
      (node (ref "E21") (pin "F2") (pinfunction "IN3_F2") (pintype "input"))
      (node (ref "E21") (pin "H1") (pinfunction "IN3_H1") (pintype "input"))
      (node (ref "E21") (pin "M1") (pinfunction "IN3_M1") (pintype "input"))
      (node (ref "E21") (pin "R2") (pinfunction "IN3_R2") (pintype "input"))
      (node (ref "F11") (pin "C1") (pinfunction "IN3_C1") (pintype "input"))
    )
    (net (code "432") (name "ISZ") (class "Default")
      (node (ref "E22") (pin "F2") (pinfunction "OUT_F2") (pintype "output"))
      (node (ref "E27") (pin "D1") (pinfunction "IN1D_D1") (pintype "input"))
      (node (ref "E28") (pin "H2") (pinfunction "IN1D_H2") (pintype "input"))
    )
    (net (code "433") (name "ISZ_") (class "Default")
      (node (ref "D40") (pin "P1") (pinfunction "P$2_P1") (pintype "bidirectional"))
      (node (ref "E21") (pin "J1") (pinfunction "OUT_J1") (pintype "output"))
      (node (ref "E22") (pin "D2") (pinfunction "IN1_D2") (pintype "input"))
    )
    (net (code "434") (name "I_IOT_") (class "Default")
      (node (ref "A05") (pin "J1") (pinfunction "IN2_J1") (pintype "input"))
      (node (ref "E21") (pin "S2") (pinfunction "OUT_S2") (pintype "output"))
      (node (ref "E22") (pin "T2") (pinfunction "IN1_T2") (pintype "input"))
    )
    (net (code "435") (name "I_M_D") (class "Default")
      (node (ref "HJ32") (pin "BU1") (pinfunction "BU1_BU1") (pintype "output"))
      (node (ref "J33") (pin "K1") (pinfunction "K1_K1") (pintype "input"))
    )
    (net (code "436") (name "JMP") (class "Default")
      (node (ref "E22") (pin "N2") (pinfunction "OUT_N2") (pintype "output"))
      (node (ref "E26") (pin "B1") (pinfunction "IN1B_B1") (pintype "input"))
      (node (ref "E26") (pin "P1") (pinfunction "IN5C_P1") (pintype "input"))
      (node (ref "E29") (pin "D1") (pinfunction "IN1D_D1") (pintype "input"))
      (node (ref "F27") (pin "B1") (pinfunction "IN2_B1") (pintype "input"))
    )
    (net (code "437") (name "JMP_") (class "Default")
      (node (ref "A17") (pin "D1") (pinfunction "IN1_D1") (pintype "input"))
      (node (ref "B20") (pin "A1") (pinfunction "IN1_A1") (pintype "input"))
      (node (ref "D40") (pin "L2") (pinfunction "P$2_L2") (pintype "bidirectional"))
      (node (ref "E21") (pin "U1") (pinfunction "OUT_U1") (pintype "output"))
      (node (ref "E22") (pin "L2") (pinfunction "IN1_L2") (pintype "input"))
      (node (ref "E24") (pin "E1") (pinfunction "IN2_E1") (pintype "input"))
      (node (ref "E29") (pin "P1") (pinfunction "IN5C_P1") (pintype "input"))
      (node (ref "F23") (pin "J1") (pinfunction "IN3_J1") (pintype "input"))
    )
    (net (code "438") (name "JMS") (class "Default")
      (node (ref "E22") (pin "K1") (pinfunction "OUT_K1") (pintype "output"))
      (node (ref "E27") (pin "P1") (pinfunction "IN5C_P1") (pintype "input"))
      (node (ref "E29") (pin "F2") (pinfunction "IN1C_F2") (pintype "input"))
      (node (ref "E30") (pin "P1") (pinfunction "IN5C_P1") (pintype "input"))
      (node (ref "F26") (pin "R2") (pinfunction "IN3_R2") (pintype "input"))
      (node (ref "F28") (pin "H1") (pinfunction "IN3_H1") (pintype "input"))
    )
    (net (code "439") (name "JMS_") (class "Default")
      (node (ref "A17") (pin "E1") (pinfunction "IN2_E1") (pintype "input"))
      (node (ref "B20") (pin "B1") (pinfunction "IN2_B1") (pintype "input"))
      (node (ref "D40") (pin "S1") (pinfunction "P$2_S1") (pintype "bidirectional"))
      (node (ref "E21") (pin "N1") (pinfunction "OUT_N1") (pintype "output"))
      (node (ref "E22") (pin "H1") (pinfunction "IN1_H1") (pintype "input"))
    )
    (net (code "440") (name "KCC_") (class "Default")
      (node (ref "EF01") (pin "AE2") (pinfunction "AE2_AE2") (pintype "output"))
      (node (ref "EF01") (pin "AV2") (pinfunction "AV2_AV2") (pintype "input"))
    )
    (net (code "441") (name "KEYBOARD_FLAG_") (class "Default")
      (node (ref "EF01") (pin "AF2") (pinfunction "AF2_AF2") (pintype "output"))
      (node (ref "F19") (pin "P1") (pinfunction "IN3_P1") (pintype "input"))
    )
    (net (code "442") (name "KEY_CONT") (class "Default")
      (node (ref "E11") (pin "S2") (pinfunction "OUT_S2") (pintype "output"))
      (node (ref "E15") (pin "J1") (pinfunction "IN2_J1") (pintype "input"))
    )
    (net (code "443") (name "KEY_CONT_") (class "Default")
      (node (ref "B40") (pin "S2") (pinfunction "P$2_S2") (pintype "bidirectional"))
      (node (ref "E11") (pin "R2") (pinfunction "IN2_R2") (pintype "input"))
      (node (ref "F19") (pin "H2") (pinfunction "IN4_H2") (pintype "input"))
    )
    (net (code "444") (name "KEY_DP") (class "Default")
      (node (ref "E11") (pin "F2") (pinfunction "OUT_F2") (pintype "output"))
      (node (ref "E29") (pin "S2") (pinfunction "IN4D_S2") (pintype "input"))
      (node (ref "F29") (pin "P1") (pinfunction "IN1_P1") (pintype "input"))
    )
    (net (code "445") (name "KEY_DP_") (class "Default")
      (node (ref "B40") (pin "M2") (pinfunction "P$2_M2") (pintype "bidirectional"))
      (node (ref "E11") (pin "D2") (pinfunction "IN1_D2") (pintype "input"))
      (node (ref "E11") (pin "H1") (pinfunction "IN1_H1") (pintype "input"))
    )
    (net (code "446") (name "KEY_EXDP") (class "Default")
      (node (ref "E11") (pin "K1") (pinfunction "OUT_K1") (pintype "output"))
      (node (ref "E11") (pin "L2") (pinfunction "IN1_L2") (pintype "input"))
      (node (ref "E13") (pin "H1") (pinfunction "IN3A_H1") (pintype "input"))
      (node (ref "E27") (pin "K2") (pinfunction "IN2B_K2") (pintype "input"))
      (node (ref "E30") (pin "L1") (pinfunction "IN4B_L1") (pintype "input"))
    )
    (net (code "447") (name "KEY_EXDP_") (class "Default")
      (node (ref "E11") (pin "N2") (pinfunction "OUT_N2") (pintype "output"))
      (node (ref "E12") (pin "H2") (pinfunction "IN1_H2") (pintype "input"))
      (node (ref "E14") (pin "L2") (pinfunction "IN3_L2") (pintype "input"))
      (node (ref "F19") (pin "F2") (pinfunction "IN3_F2") (pintype "input"))
    )
    (net (code "448") (name "KEY_EX_") (class "Default")
      (node (ref "B40") (pin "R2") (pinfunction "P$2_R2") (pintype "bidirectional"))
      (node (ref "E11") (pin "J1") (pinfunction "IN2_J1") (pintype "input"))
    )
    (net (code "449") (name "KEY_LA") (class "Default")
      (node (ref "E11") (pin "C1") (pinfunction "OUT_C1") (pintype "output"))
      (node (ref "F29") (pin "P2") (pinfunction "IN1_P2") (pintype "input"))
    )
    (net (code "450") (name "KEY_LAEXDP") (class "Default")
      (node (ref "E12") (pin "K2") (pinfunction "OUT_K2") (pintype "output"))
      (node (ref "E26") (pin "L1") (pinfunction "IN4B_L1") (pintype "input"))
      (node (ref "F21") (pin "D1") (pinfunction "IN1_D1") (pintype "input"))
    )
    (net (code "451") (name "KEY_LAEXDP_") (class "Default")
      (node (ref "F11") (pin "T2") (pinfunction "IN3_T2") (pintype "input"))
      (node (ref "F21") (pin "F1") (pinfunction "OUT_F1") (pintype "output"))
    )
    (net (code "452") (name "KEY_LAMFTS0_") (class "Default")
      (node (ref "A17") (pin "H1") (pinfunction "IN1_H1") (pintype "input"))
      (node (ref "A17") (pin "L1") (pinfunction "IN1_L1") (pintype "input"))
      (node (ref "A17") (pin "P1") (pinfunction "IN1_P1") (pintype "input"))
      (node (ref "A19") (pin "U2") (pinfunction "IN2_U2") (pintype "input"))
      (node (ref "B06") (pin "R2") (pinfunction "IN2_R2") (pintype "input"))
      (node (ref "F29") (pin "S2") (pinfunction "OUT_S2") (pintype "output"))
      (node (ref "F30") (pin "P1") (pinfunction "IN3_P1") (pintype "input"))
    )
    (net (code "453") (name "KEY_LA_") (class "Default")
      (node (ref "B40") (pin "L2") (pinfunction "P$2_L2") (pintype "bidirectional"))
      (node (ref "E11") (pin "A1") (pinfunction "IN1_A1") (pintype "input"))
      (node (ref "E12") (pin "J2") (pinfunction "IN2_J2") (pintype "input"))
      (node (ref "E15") (pin "B1") (pinfunction "IN2_B1") (pintype "input"))
      (node (ref "F19") (pin "D2") (pinfunction "IN1_D2") (pintype "input"))
    )
    (net (code "454") (name "KEY_SISTOP") (class "Default")
      (node (ref "E11") (pin "N1") (pinfunction "OUT_N1") (pintype "output"))
      (node (ref "E13") (pin "E1") (pinfunction "IN2A_E1") (pintype "input"))
    )
    (net (code "455") (name "KEY_SI_") (class "Default")
      (node (ref "B40") (pin "V2") (pinfunction "P$2_V2") (pintype "bidirectional"))
      (node (ref "E11") (pin "M1") (pinfunction "IN2_M1") (pintype "input"))
    )
    (net (code "456") (name "KEY_SS") (class "Default")
      (node (ref "E11") (pin "K2") (pinfunction "OUT_K2") (pintype "output"))
      (node (ref "E13") (pin "M1") (pinfunction "IN5A_M1") (pintype "input"))
    )
    (net (code "457") (name "KEY_SS_") (class "Default")
      (node (ref "B40") (pin "U2") (pinfunction "P$2_U2") (pintype "bidirectional"))
      (node (ref "E11") (pin "J2") (pinfunction "IN2_J2") (pintype "input"))
    )
    (net (code "458") (name "KEY_ST") (class "Default")
      (node (ref "E11") (pin "F1") (pinfunction "OUT_F1") (pintype "output"))
      (node (ref "E26") (pin "K2") (pinfunction "IN2B_K2") (pintype "input"))
      (node (ref "E26") (pin "U2") (pinfunction "IN2B_U2") (pintype "input"))
      (node (ref "E28") (pin "F1") (pinfunction "IN2B_F1") (pintype "input"))
      (node (ref "F20") (pin "U2") (pinfunction "IN2_U2") (pintype "input"))
      (node (ref "F22") (pin "E2") (pinfunction "IN2_E2") (pintype "input"))
    )
    (net (code "459") (name "KEY_STEXDP") (class "Default")
      (node (ref "A19") (pin "H2") (pinfunction "IN1_H2") (pintype "input"))
      (node (ref "E14") (pin "F2") (pinfunction "IN3_F2") (pintype "input"))
      (node (ref "E14") (pin "M2") (pinfunction "OUT_M2") (pintype "output"))
      (node (ref "F32") (pin "E1") (pinfunction "IN2_E1") (pintype "input"))
    )
    (net (code "460") (name "KEY_STOP_") (class "Default")
      (node (ref "B40") (pin "T2") (pinfunction "P$2_T2") (pintype "bidirectional"))
      (node (ref "E11") (pin "L1") (pinfunction "IN1_L1") (pintype "input"))
    )
    (net (code "461") (name "KEY_ST_") (class "Default")
      (node (ref "B40") (pin "K2") (pinfunction "P$2_K2") (pintype "bidirectional"))
      (node (ref "E11") (pin "D1") (pinfunction "IN1_D1") (pintype "input"))
      (node (ref "E14") (pin "J2") (pinfunction "IN1_J2") (pintype "input"))
      (node (ref "F19") (pin "E2") (pinfunction "IN2_E2") (pintype "input"))
    )
    (net (code "462") (name "LBAR_ENABLE") (class "Default")
      (node (ref "F29") (pin "N2") (pinfunction "OUT_N2") (pintype "output"))
      (node (ref "F33") (pin "M2") (pinfunction "IN3B_M2") (pintype "input"))
    )
    (net (code "463") (name "LEFT_SHIFT") (class "Default")
      (node (ref "E31") (pin "P2") (pinfunction "OUT_P2") (pintype "open_collector"))
      (node (ref "EF34") (pin "AF2") (pinfunction "AF2_AF2") (pintype "input"))
      (node (ref "EF35") (pin "AF2") (pinfunction "AF2_AF2") (pintype "input"))
      (node (ref "EF36") (pin "AF2") (pinfunction "AF2_AF2") (pintype "input"))
      (node (ref "EF37") (pin "AF2") (pinfunction "AF2_AF2") (pintype "input"))
      (node (ref "EF38") (pin "AF2") (pinfunction "AF2_AF2") (pintype "input"))
      (node (ref "EF39") (pin "AF2") (pinfunction "AF2_AF2") (pintype "input"))
      (node (ref "F33") (pin "L1") (pinfunction "IN4B_L1") (pintype "input"))
    )
    (net (code "464") (name "LEFT_SHIFT_") (class "Default")
      (node (ref "D12") (pin "H2") (pinfunction "IN1_H2") (pintype "input"))
      (node (ref "D12") (pin "K1") (pinfunction "OUT_K1") (pintype "output"))
      (node (ref "D12") (pin "U2") (pinfunction "IN2_U2") (pintype "input"))
    )
    (net (code "465") (name "LHS") (class "Default")
      (node (ref "D05") (pin "E1") (pinfunction "OUT_E1") (pintype "output"))
      (node (ref "D11") (pin "M2") (pinfunction "D_M2") (pintype "input"))
    )
    (net (code "466") (name "LHS_") (class "Default")
      (node (ref "D04") (pin "T2") (pinfunction "P$2_T2") (pintype "bidirectional"))
      (node (ref "D05") (pin "A1") (pinfunction "IN_A1") (pintype "input"))
      (node (ref "D05") (pin "B1") (pinfunction "IN2_B1") (pintype "bidirectional"))
      (node (ref "D05") (pin "C1") (pinfunction "IN3_C1") (pintype "input"))
      (node (ref "D05") (pin "D1") (pinfunction "IN4_D1") (pintype "input"))
    )
    (net (code "467") (name "LH_TO_HS") (class "Default")
      (node (ref "D06") (pin "F1") (pinfunction "OUT_F1") (pintype "output"))
      (node (ref "D07") (pin "R1") (pinfunction "IN2_R1") (pintype "input"))
      (node (ref "D11") (pin "L2") (pinfunction "C_L2") (pintype "input"))
    )
    (net (code "468") (name "LIGHT_PEN") (class "Default")
      (node (ref "D03") (pin "V2") (pinfunction "P$2_V2") (pintype "bidirectional"))
      (node (ref "HJ23") (pin "AN2") (pinfunction "AN2_AN2") (pintype "input"))
    )
    (net (code "469") (name "LINE_") (class "Default")
      (node (ref "C10") (pin "P1") (pinfunction "IN1_P1") (pintype "input"))
      (node (ref "C10") (pin "T2") (pinfunction "IN1_T2") (pintype "input"))
      (node (ref "J15") (pin "P2") (pinfunction "OUT_P2") (pintype "output"))
    )
    (net (code "470") (name "LINE_HOLD_") (class "Default")
      (node (ref "C07") (pin "J2") (pinfunction "IN1_J2") (pintype "input"))
      (node (ref "D09") (pin "M1") (pinfunction "IN3_M1") (pintype "input"))
      (node (ref "D10") (pin "V2") (pinfunction "OUT_V2") (pintype "output"))
    )
    (net (code "471") (name "LINK") (class "Default")
      (node (ref "E24") (pin "T2") (pinfunction "IN1_T2") (pintype "input"))
      (node (ref "E33") (pin "V2") (pinfunction "1_V2") (pintype "output"))
      (node (ref "F33") (pin "J2") (pinfunction "IN2A_J2") (pintype "input"))
    )
    (net (code "472") (name "LINK_") (class "Default")
      (node (ref "C40") (pin "B1") (pinfunction "P$2_B1") (pintype "bidirectional"))
      (node (ref "E33") (pin "V1") (pinfunction "0_V1") (pintype "output"))
      (node (ref "F33") (pin "L2") (pinfunction "IN3A_L2") (pintype "input"))
    )
    (net (code "473") (name "LOAD_BF") (class "Default")
      (node (ref "A19") (pin "N2") (pinfunction "OUT_N2") (pintype "output"))
      (node (ref "B18") (pin "L2") (pinfunction "C_L2") (pintype "input"))
      (node (ref "B18") (pin "N1") (pinfunction "C_N1") (pintype "input"))
      (node (ref "B18") (pin "S2") (pinfunction "C_S2") (pintype "input"))
    )
    (net (code "474") (name "LOAD_COUNTER") (class "Default")
      (node (ref "H30") (pin "V2") (pinfunction "V2_V2") (pintype "input"))
      (node (ref "HJ31") (pin "BN1") (pinfunction "BN1_BN1") (pintype "output"))
    )
    (net (code "475") (name "LOAD_IB") (class "Default")
      (node (ref "A18") (pin "C1") (pinfunction "OUT_C1") (pintype "output"))
      (node (ref "B17") (pin "L2") (pinfunction "C_L2") (pintype "input"))
      (node (ref "B17") (pin "N1") (pinfunction "C_N1") (pintype "input"))
      (node (ref "B17") (pin "S2") (pinfunction "C_S2") (pintype "input"))
    )
    (net (code "476") (name "LOAD_SF_") (class "Default")
      (node (ref "A19") (pin "R1") (pinfunction "IN2_R1") (pintype "input"))
      (node (ref "A19") (pin "R2") (pinfunction "IN2_R2") (pintype "input"))
      (node (ref "C12") (pin "P2") (pinfunction "OUT_P2") (pintype "open_collector"))
    )
    (net (code "477") (name "LOW_AC0") (class "Default")
      (node (ref "D21") (pin "D1") (pinfunction "IN4_D1") (pintype "input"))
      (node (ref "E24") (pin "S2") (pinfunction "OUT_S2") (pintype "output"))
      (node (ref "F23") (pin "C1") (pinfunction "IN3_C1") (pintype "input"))
    )
    (net (code "478") (name "L_ENABLE") (class "Default")
      (node (ref "E28") (pin "R1") (pinfunction "OUT_R1") (pintype "output"))
      (node (ref "F33") (pin "K2") (pinfunction "IN2B_K2") (pintype "input"))
    )
    (net (code "479") (name "MA00") (class "Default")
      (node (ref "C31") (pin "E2") (pinfunction "E2_E2") (pintype "input"))
      (node (ref "C38") (pin "E2") (pinfunction "E2_E2") (pintype "input"))
      (node (ref "EF34") (pin "AM2") (pinfunction "AM2_AM2") (pintype "output"))
    )
    (net (code "480") (name "MA00_") (class "Default")
      (node (ref "B14") (pin "A1") (pinfunction "IN1_A1") (pintype "input"))
      (node (ref "C30") (pin "E2") (pinfunction "E2_E2") (pintype "input"))
      (node (ref "C37") (pin "E2") (pinfunction "E2_E2") (pintype "input"))
      (node (ref "E40") (pin "U2") (pinfunction "P$2_U2") (pintype "bidirectional"))
      (node (ref "EF34") (pin "AM1") (pinfunction "AM1_AM1") (pintype "output"))
      (node (ref "F24") (pin "D2") (pinfunction "IN1_D2") (pintype "input"))
    )
    (net (code "481") (name "MA01") (class "Default")
      (node (ref "C30") (pin "H2") (pinfunction "H2_H2") (pintype "input"))
      (node (ref "C31") (pin "H2") (pinfunction "H2_H2") (pintype "input"))
      (node (ref "C37") (pin "H2") (pinfunction "H2_H2") (pintype "input"))
      (node (ref "C38") (pin "H2") (pinfunction "H2_H2") (pintype "input"))
      (node (ref "EF34") (pin "AL2") (pinfunction "AL2_AL2") (pintype "output"))
    )
    (net (code "482") (name "MA01_") (class "Default")
      (node (ref "B14") (pin "D2") (pinfunction "IN1_D2") (pintype "input"))
      (node (ref "E40") (pin "R2") (pinfunction "P$2_R2") (pintype "bidirectional"))
      (node (ref "EF34") (pin "AL1") (pinfunction "AL1_AL1") (pintype "output"))
      (node (ref "F24") (pin "E2") (pinfunction "IN2_E2") (pintype "input"))
    )
    (net (code "483") (name "MA02") (class "Default")
      (node (ref "C30") (pin "F2") (pinfunction "F2_F2") (pintype "input"))
      (node (ref "C31") (pin "F2") (pinfunction "F2_F2") (pintype "input"))
      (node (ref "C37") (pin "F2") (pinfunction "F2_F2") (pintype "input"))
      (node (ref "C38") (pin "F2") (pinfunction "F2_F2") (pintype "input"))
      (node (ref "EF35") (pin "AM2") (pinfunction "AM2_AM2") (pintype "output"))
    )
    (net (code "484") (name "MA02_") (class "Default")
      (node (ref "B14") (pin "F1") (pinfunction "IN1_F1") (pintype "input"))
      (node (ref "E40") (pin "K2") (pinfunction "P$2_K2") (pintype "bidirectional"))
      (node (ref "EF35") (pin "AM1") (pinfunction "AM1_AM1") (pintype "output"))
      (node (ref "F24") (pin "F2") (pinfunction "IN3_F2") (pintype "input"))
    )
    (net (code "485") (name "MA03") (class "Default")
      (node (ref "D26") (pin "E2") (pinfunction "E2_E2") (pintype "input"))
      (node (ref "D33") (pin "E2") (pinfunction "E2_E2") (pintype "input"))
      (node (ref "EF35") (pin "AL2") (pinfunction "AL2_AL2") (pintype "output"))
    )
    (net (code "486") (name "MA03_") (class "Default")
      (node (ref "B14") (pin "K2") (pinfunction "IN1_K2") (pintype "input"))
      (node (ref "D25") (pin "E2") (pinfunction "E2_E2") (pintype "input"))
      (node (ref "D32") (pin "E2") (pinfunction "E2_E2") (pintype "input"))
      (node (ref "E40") (pin "E2") (pinfunction "P$2_E2") (pintype "bidirectional"))
      (node (ref "EF35") (pin "AL1") (pinfunction "AL1_AL1") (pintype "output"))
      (node (ref "F24") (pin "H2") (pinfunction "IN4_H2") (pintype "input"))
    )
    (net (code "487") (name "MA04") (class "Default")
      (node (ref "D25") (pin "H2") (pinfunction "H2_H2") (pintype "input"))
      (node (ref "D26") (pin "H2") (pinfunction "H2_H2") (pintype "input"))
      (node (ref "D32") (pin "H2") (pinfunction "H2_H2") (pintype "input"))
      (node (ref "D33") (pin "H2") (pinfunction "H2_H2") (pintype "input"))
      (node (ref "EF36") (pin "AM2") (pinfunction "AM2_AM2") (pintype "output"))
    )
    (net (code "488") (name "MA04_") (class "Default")
      (node (ref "B14") (pin "M1") (pinfunction "IN1_M1") (pintype "input"))
      (node (ref "E40") (pin "L1") (pinfunction "P$2_L1") (pintype "bidirectional"))
      (node (ref "EF36") (pin "AM1") (pinfunction "AM1_AM1") (pintype "output"))
      (node (ref "F24") (pin "F1") (pinfunction "IN1_F1") (pintype "input"))
    )
    (net (code "489") (name "MA05") (class "Default")
      (node (ref "D25") (pin "F2") (pinfunction "F2_F2") (pintype "input"))
      (node (ref "D26") (pin "F2") (pinfunction "F2_F2") (pintype "input"))
      (node (ref "D32") (pin "F2") (pinfunction "F2_F2") (pintype "input"))
      (node (ref "D33") (pin "F2") (pinfunction "F2_F2") (pintype "input"))
      (node (ref "EF36") (pin "AL2") (pinfunction "AL2_AL2") (pintype "output"))
    )
    (net (code "490") (name "MA05_") (class "Default")
      (node (ref "B14") (pin "R2") (pinfunction "IN1_R2") (pintype "input"))
      (node (ref "E40") (pin "E1") (pinfunction "P$2_E1") (pintype "bidirectional"))
      (node (ref "EF36") (pin "AL1") (pinfunction "AL1_AL1") (pintype "output"))
      (node (ref "F24") (pin "H1") (pinfunction "IN2_H1") (pintype "input"))
    )
    (net (code "491") (name "MA06") (class "Default")
      (node (ref "C26") (pin "E2") (pinfunction "E2_E2") (pintype "input"))
      (node (ref "C33") (pin "E2") (pinfunction "E2_E2") (pintype "input"))
      (node (ref "EF37") (pin "AM2") (pinfunction "AM2_AM2") (pintype "output"))
    )
    (net (code "492") (name "MA06_") (class "Default")
      (node (ref "B15") (pin "A1") (pinfunction "IN1_A1") (pintype "input"))
      (node (ref "C25") (pin "E2") (pinfunction "E2_E2") (pintype "input"))
      (node (ref "C32") (pin "E2") (pinfunction "E2_E2") (pintype "input"))
      (node (ref "EF37") (pin "AM1") (pinfunction "AM1_AM1") (pintype "output"))
      (node (ref "F24") (pin "J1") (pinfunction "IN3_J1") (pintype "input"))
      (node (ref "F40") (pin "U2") (pinfunction "P$2_U2") (pintype "bidirectional"))
    )
    (net (code "493") (name "MA07") (class "Default")
      (node (ref "C25") (pin "H2") (pinfunction "H2_H2") (pintype "input"))
      (node (ref "C26") (pin "H2") (pinfunction "H2_H2") (pintype "input"))
      (node (ref "C32") (pin "H2") (pinfunction "H2_H2") (pintype "input"))
      (node (ref "C33") (pin "H2") (pinfunction "H2_H2") (pintype "input"))
      (node (ref "EF37") (pin "AL2") (pinfunction "AL2_AL2") (pintype "output"))
    )
    (net (code "494") (name "MA07_") (class "Default")
      (node (ref "B15") (pin "D2") (pinfunction "IN1_D2") (pintype "input"))
      (node (ref "EF37") (pin "AL1") (pinfunction "AL1_AL1") (pintype "output"))
      (node (ref "F24") (pin "K1") (pinfunction "IN4_K1") (pintype "input"))
      (node (ref "F40") (pin "R2") (pinfunction "P$2_R2") (pintype "bidirectional"))
    )
    (net (code "495") (name "MA08") (class "Default")
      (node (ref "C25") (pin "F2") (pinfunction "F2_F2") (pintype "input"))
      (node (ref "C26") (pin "F2") (pinfunction "F2_F2") (pintype "input"))
      (node (ref "C32") (pin "F2") (pinfunction "F2_F2") (pintype "input"))
      (node (ref "C33") (pin "F2") (pinfunction "F2_F2") (pintype "input"))
      (node (ref "EF38") (pin "AM2") (pinfunction "AM2_AM2") (pintype "output"))
      (node (ref "F25") (pin "L1") (pinfunction "IN1_L1") (pintype "input"))
    )
    (net (code "496") (name "MA08_") (class "Default")
      (node (ref "B15") (pin "F1") (pinfunction "IN1_F1") (pintype "input"))
      (node (ref "EF38") (pin "AM1") (pinfunction "AM1_AM1") (pintype "output"))
      (node (ref "F40") (pin "K2") (pinfunction "P$2_K2") (pintype "bidirectional"))
    )
    (net (code "497") (name "MA09") (class "Default")
      (node (ref "D31") (pin "E2") (pinfunction "E2_E2") (pintype "input"))
      (node (ref "D38") (pin "E2") (pinfunction "E2_E2") (pintype "input"))
      (node (ref "EF38") (pin "AL2") (pinfunction "AL2_AL2") (pintype "output"))
    )
    (net (code "498") (name "MA09_") (class "Default")
      (node (ref "B15") (pin "K2") (pinfunction "IN1_K2") (pintype "input"))
      (node (ref "D30") (pin "E2") (pinfunction "E2_E2") (pintype "input"))
      (node (ref "D37") (pin "E2") (pinfunction "E2_E2") (pintype "input"))
      (node (ref "EF38") (pin "AL1") (pinfunction "AL1_AL1") (pintype "output"))
      (node (ref "F40") (pin "E2") (pinfunction "P$2_E2") (pintype "bidirectional"))
    )
    (net (code "499") (name "MA10") (class "Default")
      (node (ref "D30") (pin "H2") (pinfunction "H2_H2") (pintype "input"))
      (node (ref "D31") (pin "H2") (pinfunction "H2_H2") (pintype "input"))
      (node (ref "D37") (pin "H2") (pinfunction "H2_H2") (pintype "input"))
      (node (ref "D38") (pin "H2") (pinfunction "H2_H2") (pintype "input"))
      (node (ref "EF39") (pin "AM2") (pinfunction "AM2_AM2") (pintype "output"))
    )
    (net (code "500") (name "MA10_") (class "Default")
      (node (ref "B15") (pin "M1") (pinfunction "IN1_M1") (pintype "input"))
      (node (ref "EF39") (pin "AM1") (pinfunction "AM1_AM1") (pintype "output"))
      (node (ref "F40") (pin "L1") (pinfunction "P$2_L1") (pintype "bidirectional"))
    )
    (net (code "501") (name "MA11") (class "Default")
      (node (ref "D30") (pin "F2") (pinfunction "F2_F2") (pintype "input"))
      (node (ref "D31") (pin "F2") (pinfunction "F2_F2") (pintype "input"))
      (node (ref "D37") (pin "F2") (pinfunction "F2_F2") (pintype "input"))
      (node (ref "D38") (pin "F2") (pinfunction "F2_F2") (pintype "input"))
      (node (ref "EF39") (pin "AL2") (pinfunction "AL2_AL2") (pintype "output"))
    )
    (net (code "502") (name "MA11_") (class "Default")
      (node (ref "B15") (pin "R2") (pinfunction "IN1_R2") (pintype "input"))
      (node (ref "EF39") (pin "AL1") (pinfunction "AL1_AL1") (pintype "output"))
      (node (ref "F40") (pin "E1") (pinfunction "P$2_E1") (pintype "bidirectional"))
    )
    (net (code "503") (name "MANUAL_PRESET_") (class "Default")
      (node (ref "B11") (pin "D1") (pinfunction "S_D1") (pintype "input"))
      (node (ref "B11") (pin "F2") (pinfunction "S_F2") (pintype "input"))
      (node (ref "B11") (pin "K1") (pinfunction "S_K1") (pintype "input"))
      (node (ref "D11") (pin "D1") (pinfunction "S_D1") (pintype "input"))
      (node (ref "D11") (pin "F2") (pinfunction "S_F2") (pintype "input"))
      (node (ref "E18") (pin "D1") (pinfunction "S_D1") (pintype "input"))
      (node (ref "E19") (pin "A1") (pinfunction "R_A1") (pintype "input"))
      (node (ref "E20") (pin "K2") (pinfunction "R_K2") (pintype "input"))
      (node (ref "E23") (pin "A1") (pinfunction "R_A1") (pintype "input"))
      (node (ref "E23") (pin "K2") (pinfunction "R_K2") (pintype "input"))
      (node (ref "E33") (pin "K1") (pinfunction "S_K1") (pintype "input"))
      (node (ref "F20") (pin "E1") (pinfunction "IN2_E1") (pintype "input"))
      (node (ref "F30") (pin "V2") (pinfunction "OUT_V2") (pintype "open_collector"))
    )
    (net (code "504") (name "MA_ENABLE0_4") (class "Default")
      (node (ref "EF34") (pin "BP1") (pinfunction "BP1_BP1") (pintype "input"))
      (node (ref "EF34") (pin "BR2") (pinfunction "BR2_BR2") (pintype "input"))
      (node (ref "EF35") (pin "BP1") (pinfunction "BP1_BP1") (pintype "input"))
      (node (ref "EF35") (pin "BR2") (pinfunction "BR2_BR2") (pintype "input"))
      (node (ref "EF36") (pin "BP1") (pinfunction "BP1_BP1") (pintype "input"))
      (node (ref "F31") (pin "L1") (pinfunction "OUT_L1") (pintype "open_collector"))
    )
    (net (code "505") (name "MA_ENABLE5_11") (class "Default")
      (node (ref "EF36") (pin "BR2") (pinfunction "BR2_BR2") (pintype "input"))
      (node (ref "EF37") (pin "BP1") (pinfunction "BP1_BP1") (pintype "input"))
      (node (ref "EF37") (pin "BR2") (pinfunction "BR2_BR2") (pintype "input"))
      (node (ref "EF38") (pin "BP1") (pinfunction "BP1_BP1") (pintype "input"))
      (node (ref "EF38") (pin "BR2") (pinfunction "BR2_BR2") (pintype "input"))
      (node (ref "EF39") (pin "BP1") (pinfunction "BP1_BP1") (pintype "input"))
      (node (ref "EF39") (pin "BR2") (pinfunction "BR2_BR2") (pintype "input"))
      (node (ref "F31") (pin "P2") (pinfunction "OUT_P2") (pintype "open_collector"))
    )
    (net (code "506") (name "MA_LOAD") (class "Default")
      (node (ref "E32") (pin "E1") (pinfunction "OUT_E1") (pintype "open_collector"))
      (node (ref "EF34") (pin "AK1") (pinfunction "AK1_AK1") (pintype "input"))
      (node (ref "EF35") (pin "AK1") (pinfunction "AK1_AK1") (pintype "input"))
      (node (ref "EF36") (pin "AK1") (pinfunction "AK1_AK1") (pintype "input"))
      (node (ref "EF37") (pin "AK1") (pinfunction "AK1_AK1") (pintype "input"))
      (node (ref "EF38") (pin "AK1") (pinfunction "AK1_AK1") (pintype "input"))
      (node (ref "EF39") (pin "AK1") (pinfunction "AK1_AK1") (pintype "input"))
    )
    (net (code "507") (name "MB00") (class "Default")
      (node (ref "A09") (pin "E1") (pinfunction "1A_E1") (pintype "input"))
      (node (ref "B12") (pin "A1") (pinfunction "IN1_A1") (pintype "input"))
      (node (ref "EF34") (pin "AT2") (pinfunction "AT2_AT2") (pintype "output"))
      (node (ref "H13") (pin "H2") (pinfunction "IN2_H2") (pintype "input"))
    )
    (net (code "508") (name "MB00_") (class "Default")
      (node (ref "A09") (pin "A1") (pinfunction "1B_A1") (pintype "input"))
      (node (ref "A27") (pin "D2") (pinfunction "D2_D2") (pintype "input"))
      (node (ref "A36") (pin "D2") (pinfunction "D2_D2") (pintype "input"))
      (node (ref "E40") (pin "R1") (pinfunction "P$2_R1") (pintype "bidirectional"))
      (node (ref "EF34") (pin "AU2") (pinfunction "AU2_AU2") (pintype "output"))
    )
    (net (code "509") (name "MB01") (class "Default")
      (node (ref "A09") (pin "F1") (pinfunction "2A_F1") (pintype "input"))
      (node (ref "B12") (pin "D2") (pinfunction "IN1_D2") (pintype "input"))
      (node (ref "EF34") (pin "AS2") (pinfunction "AS2_AS2") (pintype "output"))
      (node (ref "H13") (pin "N2") (pinfunction "IN2_N2") (pintype "input"))
    )
    (net (code "510") (name "MB01_") (class "Default")
      (node (ref "A09") (pin "B1") (pinfunction "2B_B1") (pintype "input"))
      (node (ref "A27") (pin "D1") (pinfunction "D1_D1") (pintype "input"))
      (node (ref "A36") (pin "D1") (pinfunction "D1_D1") (pintype "input"))
      (node (ref "E40") (pin "P1") (pinfunction "P$2_P1") (pintype "bidirectional"))
      (node (ref "EF34") (pin "AS1") (pinfunction "AS1_AS1") (pintype "output"))
    )
    (net (code "511") (name "MB02") (class "Default")
      (node (ref "A09") (pin "H1") (pinfunction "4A_H1") (pintype "input"))
      (node (ref "B12") (pin "F1") (pinfunction "IN1_F1") (pintype "input"))
      (node (ref "EF35") (pin "AT2") (pinfunction "AT2_AT2") (pintype "output"))
      (node (ref "H13") (pin "U2") (pinfunction "IN2_U2") (pintype "input"))
    )
    (net (code "512") (name "MB02_") (class "Default")
      (node (ref "A09") (pin "C1") (pinfunction "4B_C1") (pintype "input"))
      (node (ref "A27") (pin "M2") (pinfunction "M2_M2") (pintype "input"))
      (node (ref "A36") (pin "M2") (pinfunction "M2_M2") (pintype "input"))
      (node (ref "E40") (pin "F2") (pinfunction "P$2_F2") (pintype "bidirectional"))
      (node (ref "EF35") (pin "AU2") (pinfunction "AU2_AU2") (pintype "output"))
    )
    (net (code "513") (name "MB03") (class "Default")
      (node (ref "A09") (pin "J1") (pinfunction "8A_J1") (pintype "input"))
      (node (ref "B12") (pin "K2") (pinfunction "IN1_K2") (pintype "input"))
      (node (ref "C11") (pin "P1") (pinfunction "IN1_P1") (pintype "input"))
      (node (ref "D20") (pin "P1") (pinfunction "IN3_P1") (pintype "input"))
      (node (ref "E25") (pin "L2") (pinfunction "IN3_L2") (pintype "input"))
      (node (ref "EF35") (pin "AS2") (pinfunction "AS2_AS2") (pintype "output"))
      (node (ref "F27") (pin "K1") (pinfunction "IN4_K1") (pintype "input"))
      (node (ref "H14") (pin "N2") (pinfunction "IN2_N2") (pintype "input"))
      (node (ref "HJ29") (pin "AF2") (pinfunction "AF2_AF2") (pintype "input"))
      (node (ref "J33") (pin "C1") (pinfunction "C1_C1") (pintype "input"))
    )
    (net (code "514") (name "MB03_") (class "Default")
      (node (ref "A04") (pin "D2") (pinfunction "D2_D2") (pintype "input"))
      (node (ref "A09") (pin "D1") (pinfunction "8B_D1") (pintype "input"))
      (node (ref "A27") (pin "L1") (pinfunction "L1_L1") (pintype "input"))
      (node (ref "A36") (pin "L1") (pinfunction "L1_L1") (pintype "input"))
      (node (ref "B07") (pin "A1") (pinfunction "IN1_A1") (pintype "input"))
      (node (ref "B16") (pin "L2") (pinfunction "IN2_L2") (pintype "input"))
      (node (ref "E26") (pin "C1") (pinfunction "IN1C_C1") (pintype "input"))
      (node (ref "E40") (pin "D2") (pinfunction "P$2_D2") (pintype "bidirectional"))
      (node (ref "EF01") (pin "AD2") (pinfunction "AD2_AD2") (pintype "input"))
      (node (ref "EF02") (pin "AE2") (pinfunction "AE2_AE2") (pintype "input"))
      (node (ref "EF35") (pin "AS1") (pinfunction "AS1_AS1") (pintype "output"))
      (node (ref "F09") (pin "B1") (pinfunction "IN2_B1") (pintype "input"))
      (node (ref "F19") (pin "T2") (pinfunction "IN3_T2") (pintype "input"))
      (node (ref "F23") (pin "K1") (pinfunction "IN4_K1") (pintype "input"))
      (node (ref "F27") (pin "D1") (pinfunction "IN4_D1") (pintype "input"))
      (node (ref "F27") (pin "U2") (pinfunction "IN4_U2") (pintype "input"))
      (node (ref "H14") (pin "H2") (pinfunction "IN2_H2") (pintype "input"))
      (node (ref "H30") (pin "T2") (pinfunction "T2_T2") (pintype "input"))
      (node (ref "HJ23") (pin "BF2") (pinfunction "BF2_BF2") (pintype "input"))
      (node (ref "HJ26") (pin "BD2") (pinfunction "BD2_BD2") (pintype "input"))
      (node (ref "HJ28") (pin "BF2") (pinfunction "BF2_BF2") (pintype "input"))
    )
    (net (code "515") (name "MB04") (class "Default")
      (node (ref "A10") (pin "P2") (pinfunction "1A_P2") (pintype "input"))
      (node (ref "B12") (pin "M1") (pinfunction "IN1_M1") (pintype "input"))
      (node (ref "B16") (pin "M2") (pinfunction "IN3_M2") (pintype "input"))
      (node (ref "E30") (pin "V1") (pinfunction "IN2A_V1") (pintype "input"))
      (node (ref "EF36") (pin "AT2") (pinfunction "AT2_AT2") (pintype "output"))
      (node (ref "F09") (pin "C1") (pinfunction "IN3_C1") (pintype "input"))
      (node (ref "F28") (pin "F2") (pinfunction "IN3_F2") (pintype "input"))
      (node (ref "H15") (pin "H2") (pinfunction "IN2_H2") (pintype "input"))
      (node (ref "J33") (pin "D2") (pinfunction "D2_D2") (pintype "input"))
    )
    (net (code "516") (name "MB04_") (class "Default")
      (node (ref "A04") (pin "E2") (pinfunction "E2_E2") (pintype "input"))
      (node (ref "A10") (pin "K2") (pinfunction "1B_K2") (pintype "input"))
      (node (ref "B07") (pin "B1") (pinfunction "IN2_B1") (pintype "input"))
      (node (ref "B26") (pin "D2") (pinfunction "D2_D2") (pintype "input"))
      (node (ref "B36") (pin "D2") (pinfunction "D2_D2") (pintype "input"))
      (node (ref "C11") (pin "R1") (pinfunction "IN2_R1") (pintype "input"))
      (node (ref "D21") (pin "J1") (pinfunction "IN3_J1") (pintype "input"))
      (node (ref "E30") (pin "H2") (pinfunction "IN1D_H2") (pintype "input"))
      (node (ref "E30") (pin "S1") (pinfunction "IN1A_S1") (pintype "input"))
      (node (ref "E40") (pin "K1") (pinfunction "P$2_K1") (pintype "bidirectional"))
      (node (ref "EF01") (pin "AE1") (pinfunction "AE1_AE1") (pintype "input"))
      (node (ref "EF02") (pin "AE1") (pinfunction "AE1_AE1") (pintype "input"))
      (node (ref "EF36") (pin "AU2") (pinfunction "AU2_AU2") (pintype "output"))
      (node (ref "F19") (pin "U2") (pinfunction "IN4_U2") (pintype "input"))
      (node (ref "H14") (pin "U2") (pinfunction "IN2_U2") (pintype "input"))
      (node (ref "H30") (pin "S2") (pinfunction "S2_S2") (pintype "input"))
      (node (ref "HJ23") (pin "BH2") (pinfunction "BH2_BH2") (pintype "input"))
      (node (ref "HJ26") (pin "BE2") (pinfunction "BE2_BE2") (pintype "input"))
      (node (ref "HJ28") (pin "BD1") (pinfunction "BD1_BD1") (pintype "input"))
      (node (ref "HJ29") (pin "AH2") (pinfunction "AH2_AH2") (pintype "input"))
    )
    (net (code "517") (name "MB05") (class "Default")
      (node (ref "A04") (pin "F2") (pinfunction "F2_F2") (pintype "input"))
      (node (ref "A10") (pin "R2") (pinfunction "2A_R2") (pintype "input"))
      (node (ref "B07") (pin "C1") (pinfunction "IN3_C1") (pintype "input"))
      (node (ref "B12") (pin "R2") (pinfunction "IN1_R2") (pintype "input"))
      (node (ref "D18") (pin "D2") (pinfunction "IN1_D2") (pintype "input"))
      (node (ref "E24") (pin "M1") (pinfunction "IN2_M1") (pintype "input"))
      (node (ref "E28") (pin "M1") (pinfunction "IN5A_M1") (pintype "input"))
      (node (ref "EF36") (pin "AS2") (pinfunction "AS2_AS2") (pintype "output"))
      (node (ref "H15") (pin "U2") (pinfunction "IN2_U2") (pintype "input"))
      (node (ref "H30") (pin "R2") (pinfunction "R2_R2") (pintype "input"))
      (node (ref "HJ29") (pin "AE2") (pinfunction "AE2_AE2") (pintype "input"))
    )
    (net (code "518") (name "MB05_") (class "Default")
      (node (ref "A10") (pin "L2") (pinfunction "2B_L2") (pintype "input"))
      (node (ref "B16") (pin "N2") (pinfunction "IN4_N2") (pintype "input"))
      (node (ref "B26") (pin "D1") (pinfunction "D1_D1") (pintype "input"))
      (node (ref "B36") (pin "D1") (pinfunction "D1_D1") (pintype "input"))
      (node (ref "C11") (pin "S1") (pinfunction "IN3_S1") (pintype "input"))
      (node (ref "E28") (pin "B1") (pinfunction "IN1B_B1") (pintype "input"))
      (node (ref "E40") (pin "A1") (pinfunction "P$2_A1") (pintype "bidirectional"))
      (node (ref "EF01") (pin "AF1") (pinfunction "AF1_AF1") (pintype "input"))
      (node (ref "EF02") (pin "AF2") (pinfunction "AF2_AF2") (pintype "input"))
      (node (ref "EF36") (pin "AS1") (pinfunction "AS1_AS1") (pintype "output"))
      (node (ref "F09") (pin "D1") (pinfunction "IN4_D1") (pintype "input"))
      (node (ref "F23") (pin "R2") (pinfunction "IN1_R2") (pintype "input"))
      (node (ref "H15") (pin "N2") (pinfunction "IN2_N2") (pintype "input"))
      (node (ref "HJ23") (pin "BK2") (pinfunction "BK2_BK2") (pintype "input"))
      (node (ref "HJ26") (pin "BE1") (pinfunction "BE1_BE1") (pintype "input"))
      (node (ref "HJ28") (pin "BD2") (pinfunction "BD2_BD2") (pintype "input"))
      (node (ref "J33") (pin "B1") (pinfunction "B1_B1") (pintype "input"))
    )
    (net (code "519") (name "MB06") (class "Default")
      (node (ref "A10") (pin "S2") (pinfunction "4A_S2") (pintype "input"))
      (node (ref "A12") (pin "E2") (pinfunction "IN2_E2") (pintype "input"))
      (node (ref "A15") (pin "T2") (pinfunction "IN1_T2") (pintype "input"))
      (node (ref "A18") (pin "E2") (pinfunction "IN2_E2") (pintype "input"))
      (node (ref "B13") (pin "A1") (pinfunction "IN1_A1") (pintype "input"))
      (node (ref "D18") (pin "H1") (pinfunction "IN3_H1") (pintype "input"))
      (node (ref "E30") (pin "U1") (pinfunction "IN1B_U1") (pintype "input"))
      (node (ref "EF02") (pin "AF1") (pinfunction "AF1_AF1") (pintype "input"))
      (node (ref "EF37") (pin "AT2") (pinfunction "AT2_AT2") (pintype "output"))
      (node (ref "F23") (pin "D1") (pinfunction "IN4_D1") (pintype "input"))
      (node (ref "F32") (pin "J2") (pinfunction "IN2_J2") (pintype "input"))
      (node (ref "H16") (pin "N2") (pinfunction "IN2_N2") (pintype "input"))
      (node (ref "HJ23") (pin "BM2") (pinfunction "BM2_BM2") (pintype "input"))
      (node (ref "J33") (pin "D1") (pinfunction "D1_D1") (pintype "input"))
    )
    (net (code "520") (name "MB06XMB09") (class "Default")
      (node (ref "A06") (pin "N2") (pinfunction "OUT_N2") (pintype "output"))
      (node (ref "A06") (pin "U2") (pinfunction "IN2_U2") (pintype "input"))
      (node (ref "B04") (pin "F1") (pinfunction "IN2_F1") (pintype "input"))
      (node (ref "B06") (pin "B1") (pinfunction "IN2_B1") (pintype "input"))
    )
    (net (code "521") (name "MB06_") (class "Default")
      (node (ref "A04") (pin "H2") (pinfunction "H2_H2") (pintype "input"))
      (node (ref "A10") (pin "M2") (pinfunction "4B_M2") (pintype "input"))
      (node (ref "B07") (pin "D2") (pinfunction "IN1_D2") (pintype "input"))
      (node (ref "B26") (pin "M2") (pinfunction "M2_M2") (pintype "input"))
      (node (ref "B36") (pin "M2") (pinfunction "M2_M2") (pintype "input"))
      (node (ref "C11") (pin "T2") (pinfunction "IN1_T2") (pintype "input"))
      (node (ref "E30") (pin "U2") (pinfunction "IN2B_U2") (pintype "input"))
      (node (ref "EF01") (pin "AH1") (pinfunction "AH1_AH1") (pintype "input"))
      (node (ref "EF37") (pin "AU2") (pinfunction "AU2_AU2") (pintype "output"))
      (node (ref "F09") (pin "D2") (pinfunction "IN5_D2") (pintype "input"))
      (node (ref "F23") (pin "S2") (pinfunction "IN2_S2") (pintype "input"))
      (node (ref "F40") (pin "R1") (pinfunction "P$2_R1") (pintype "bidirectional"))
      (node (ref "H16") (pin "H2") (pinfunction "IN2_H2") (pintype "input"))
      (node (ref "H30") (pin "P2") (pinfunction "P2_P2") (pintype "input"))
      (node (ref "HJ26") (pin "BF2") (pinfunction "BF2_BF2") (pintype "input"))
      (node (ref "HJ28") (pin "BE1") (pinfunction "BE1_BE1") (pintype "input"))
      (node (ref "HJ29") (pin "AD2") (pinfunction "AD2_AD2") (pintype "input"))
      (node (ref "J33") (pin "E2") (pinfunction "E2_E2") (pintype "input"))
    )
    (net (code "522") (name "MB07") (class "Default")
      (node (ref "A10") (pin "T2") (pinfunction "8A_T2") (pintype "input"))
      (node (ref "A12") (pin "M1") (pinfunction "IN2_M1") (pintype "input"))
      (node (ref "A18") (pin "M1") (pinfunction "IN2_M1") (pintype "input"))
      (node (ref "A20") (pin "R1") (pinfunction "IN2_R1") (pintype "input"))
      (node (ref "A20") (pin "R2") (pinfunction "IN3_R2") (pintype "input"))
      (node (ref "B06") (pin "A1") (pinfunction "IN1_A1") (pintype "input"))
      (node (ref "B13") (pin "D2") (pinfunction "IN1_D2") (pintype "input"))
      (node (ref "D18") (pin "K1") (pinfunction "IN1_K1") (pintype "input"))
      (node (ref "D21") (pin "H1") (pinfunction "IN2_H1") (pintype "input"))
      (node (ref "E24") (pin "U2") (pinfunction "IN2_U2") (pintype "input"))
      (node (ref "E28") (pin "D1") (pinfunction "IN1D_D1") (pintype "input"))
      (node (ref "EF01") (pin "AH2") (pinfunction "AH2_AH2") (pintype "input"))
      (node (ref "EF37") (pin "AS2") (pinfunction "AS2_AS2") (pintype "output"))
      (node (ref "F29") (pin "U2") (pinfunction "IN2_U2") (pintype "input"))
      (node (ref "H17") (pin "H2") (pinfunction "IN2_H2") (pintype "input"))
      (node (ref "H30") (pin "N2") (pinfunction "N2_N2") (pintype "input"))
      (node (ref "HJ23") (pin "BL2") (pinfunction "BL2_BL2") (pintype "input"))
      (node (ref "HJ28") (pin "BE2") (pinfunction "BE2_BE2") (pintype "input"))
      (node (ref "HJ29") (pin "AS2") (pinfunction "AS2_AS2") (pintype "input"))
      (node (ref "J33") (pin "A1") (pinfunction "A1_A1") (pintype "input"))
    )
    (net (code "523") (name "MB07_") (class "Default")
      (node (ref "A04") (pin "J2") (pinfunction "J2_J2") (pintype "input"))
      (node (ref "A06") (pin "P1") (pinfunction "IN1_P1") (pintype "input"))
      (node (ref "A10") (pin "N2") (pinfunction "8B_N2") (pintype "input"))
      (node (ref "A20") (pin "L1") (pinfunction "IN2_L1") (pintype "input"))
      (node (ref "B04") (pin "A1") (pinfunction "IN1_A1") (pintype "input"))
      (node (ref "B04") (pin "H1") (pinfunction "IN3_H1") (pintype "input"))
      (node (ref "B07") (pin "E2") (pinfunction "IN2_E2") (pintype "input"))
      (node (ref "B26") (pin "L1") (pinfunction "L1_L1") (pintype "input"))
      (node (ref "B36") (pin "L1") (pinfunction "L1_L1") (pintype "input"))
      (node (ref "C11") (pin "U2") (pinfunction "IN2_U2") (pintype "input"))
      (node (ref "C14") (pin "U2") (pinfunction "IN2_U2") (pintype "input"))
      (node (ref "E28") (pin "P1") (pinfunction "IN5C_P1") (pintype "input"))
      (node (ref "EF02") (pin "AH2") (pinfunction "AH2_AH2") (pintype "input"))
      (node (ref "EF37") (pin "AS1") (pinfunction "AS1_AS1") (pintype "output"))
      (node (ref "F23") (pin "T2") (pinfunction "IN3_T2") (pintype "input"))
      (node (ref "F40") (pin "P1") (pinfunction "P$2_P1") (pintype "bidirectional"))
      (node (ref "H16") (pin "U2") (pinfunction "IN2_U2") (pintype "input"))
      (node (ref "HJ23") (pin "BE2") (pinfunction "BE2_BE2") (pintype "input"))
      (node (ref "HJ26") (pin "BF1") (pinfunction "BF1_BF1") (pintype "input"))
      (node (ref "HJ29") (pin "BU1") (pinfunction "BU1_BU1") (pintype "input"))
    )
    (net (code "524") (name "MB08") (class "Default")
      (node (ref "A09") (pin "P2") (pinfunction "1A_P2") (pintype "input"))
      (node (ref "A12") (pin "R2") (pinfunction "IN2_R2") (pintype "input"))
      (node (ref "A18") (pin "R2") (pinfunction "IN2_R2") (pintype "input"))
      (node (ref "A20") (pin "M1") (pinfunction "IN3_M1") (pintype "input"))
      (node (ref "A20") (pin "P2") (pinfunction "IN2_P2") (pintype "input"))
      (node (ref "B04") (pin "E1") (pinfunction "IN1_E1") (pintype "input"))
      (node (ref "B06") (pin "M1") (pinfunction "IN2_M1") (pintype "input"))
      (node (ref "B13") (pin "F1") (pinfunction "IN1_F1") (pintype "input"))
      (node (ref "D24") (pin "C1") (pinfunction "D_C1") (pintype "input"))
      (node (ref "E28") (pin "R2") (pinfunction "IN4C_R2") (pintype "input"))
      (node (ref "EF01") (pin "AJ1") (pinfunction "AJ1_AJ1") (pintype "input"))
      (node (ref "EF38") (pin "AT2") (pinfunction "AT2_AT2") (pintype "output"))
      (node (ref "F26") (pin "D2") (pinfunction "IN1_D2") (pintype "input"))
      (node (ref "F26") (pin "E1") (pinfunction "IN1_E1") (pintype "input"))
      (node (ref "H17") (pin "U2") (pinfunction "IN2_U2") (pintype "input"))
      (node (ref "H30") (pin "M2") (pinfunction "M2_M2") (pintype "input"))
      (node (ref "HJ23") (pin "BN2") (pinfunction "BN2_BN2") (pintype "input"))
      (node (ref "HJ26") (pin "BH2") (pinfunction "BH2_BH2") (pintype "input"))
      (node (ref "HJ29") (pin "AK2") (pinfunction "AK2_AK2") (pintype "input"))
      (node (ref "J33") (pin "E1") (pinfunction "E1_E1") (pintype "input"))
    )
    (net (code "525") (name "MB08_") (class "Default")
      (node (ref "A04") (pin "K2") (pinfunction "K2_K2") (pintype "input"))
      (node (ref "A06") (pin "R1") (pinfunction "IN2_R1") (pintype "input"))
      (node (ref "A09") (pin "K2") (pinfunction "1B_K2") (pintype "input"))
      (node (ref "A20") (pin "S1") (pinfunction "IN3_S1") (pintype "input"))
      (node (ref "B04") (pin "B1") (pinfunction "IN2_B1") (pintype "input"))
      (node (ref "B07") (pin "F2") (pinfunction "IN3_F2") (pintype "input"))
      (node (ref "B27") (pin "D2") (pinfunction "D2_D2") (pintype "input"))
      (node (ref "B37") (pin "D2") (pinfunction "D2_D2") (pintype "input"))
      (node (ref "C11") (pin "V2") (pinfunction "IN3_V2") (pintype "input"))
      (node (ref "C15") (pin "U2") (pinfunction "IN2_U2") (pintype "input"))
      (node (ref "E28") (pin "M2") (pinfunction "IN3B_M2") (pintype "input"))
      (node (ref "EF02") (pin "AJ2") (pinfunction "AJ2_AJ2") (pintype "input"))
      (node (ref "EF38") (pin "AU2") (pinfunction "AU2_AU2") (pintype "output"))
      (node (ref "F23") (pin "U2") (pinfunction "IN4_U2") (pintype "input"))
      (node (ref "F26") (pin "K1") (pinfunction "IN1_K1") (pintype "input"))
      (node (ref "F40") (pin "F2") (pinfunction "P$2_F2") (pintype "bidirectional"))
      (node (ref "H17") (pin "N2") (pinfunction "IN2_N2") (pintype "input"))
      (node (ref "HJ23") (pin "BJ2") (pinfunction "BJ2_BJ2") (pintype "input"))
      (node (ref "HJ28") (pin "BF1") (pinfunction "BF1_BF1") (pintype "input"))
      (node (ref "HJ29") (pin "BV1") (pinfunction "BV1_BV1") (pintype "input"))
    )
    (net (code "526") (name "MB09") (class "Default")
      (node (ref "A09") (pin "R2") (pinfunction "2A_R2") (pintype "input"))
      (node (ref "A14") (pin "D2") (pinfunction "IN1_D2") (pintype "input"))
      (node (ref "B13") (pin "K2") (pinfunction "IN1_K2") (pintype "input"))
      (node (ref "C11") (pin "L1") (pinfunction "IN2_L1") (pintype "input"))
      (node (ref "D13") (pin "E1") (pinfunction "IN2_E1") (pintype "input"))
      (node (ref "D24") (pin "E2") (pinfunction "D_E2") (pintype "input"))
      (node (ref "EF38") (pin "AS2") (pinfunction "AS2_AS2") (pintype "output"))
      (node (ref "F09") (pin "E2") (pinfunction "IN6_E2") (pintype "input"))
      (node (ref "F20") (pin "J2") (pinfunction "IN2_J2") (pintype "input"))
      (node (ref "F26") (pin "A1") (pinfunction "IN1_A1") (pintype "input"))
      (node (ref "F26") (pin "J2") (pinfunction "IN1_J2") (pintype "input"))
      (node (ref "F28") (pin "R2") (pinfunction "IN3_R2") (pintype "input"))
      (node (ref "H18") (pin "H2") (pinfunction "IN2_H2") (pintype "input"))
      (node (ref "H30") (pin "U2") (pinfunction "U2_U2") (pintype "input"))
    )
    (net (code "527") (name "MB09_") (class "Default")
      (node (ref "A05") (pin "B1") (pinfunction "IN2_B1") (pintype "input"))
      (node (ref "A09") (pin "L2") (pinfunction "2B_L2") (pintype "input"))
      (node (ref "B27") (pin "D1") (pinfunction "D1_D1") (pintype "input"))
      (node (ref "B37") (pin "D1") (pinfunction "D1_D1") (pintype "input"))
      (node (ref "C16") (pin "U2") (pinfunction "IN2_U2") (pintype "input"))
      (node (ref "D13") (pin "P1") (pinfunction "IN1_P1") (pintype "input"))
      (node (ref "EF38") (pin "AS1") (pinfunction "AS1_AS1") (pintype "output"))
      (node (ref "F26") (pin "M1") (pinfunction "IN3_M1") (pintype "input"))
      (node (ref "F40") (pin "D2") (pinfunction "P$2_D2") (pintype "bidirectional"))
      (node (ref "H30") (pin "N1") (pinfunction "N1_N1") (pintype "input"))
      (node (ref "HJ23") (pin "AK2") (pinfunction "AK2_AK2") (pintype "input"))
    )
    (net (code "528") (name "MB10") (class "Default")
      (node (ref "A09") (pin "S2") (pinfunction "4A_S2") (pintype "input"))
      (node (ref "A12") (pin "B1") (pinfunction "IN2_B1") (pintype "input"))
      (node (ref "A15") (pin "P2") (pinfunction "IN1_P2") (pintype "input"))
      (node (ref "B13") (pin "M1") (pinfunction "IN1_M1") (pintype "input"))
      (node (ref "D10") (pin "D1") (pinfunction "IN4_D1") (pintype "input"))
      (node (ref "D10") (pin "F2") (pinfunction "IN3_F2") (pintype "input"))
      (node (ref "D24") (pin "J1") (pinfunction "D_J1") (pintype "input"))
      (node (ref "E13") (pin "A1") (pinfunction "IN1A_A1") (pintype "input"))
      (node (ref "E14") (pin "H1") (pinfunction "IN3_H1") (pintype "input"))
      (node (ref "EF39") (pin "AT2") (pinfunction "AT2_AT2") (pintype "output"))
      (node (ref "F20") (pin "J1") (pinfunction "IN2_J1") (pintype "input"))
      (node (ref "F26") (pin "C1") (pinfunction "IN3_C1") (pintype "input"))
      (node (ref "F26") (pin "F2") (pinfunction "IN3_F2") (pintype "input"))
      (node (ref "H18") (pin "N2") (pinfunction "IN2_N2") (pintype "input"))
      (node (ref "H30") (pin "L1") (pinfunction "L1_L1") (pintype "input"))
      (node (ref "HJ23") (pin "AN1") (pinfunction "AN1_AN1") (pintype "input"))
      (node (ref "HJ31") (pin "BJ1") (pinfunction "BJ1_BJ1") (pintype "input"))
    )
    (net (code "529") (name "MB10_") (class "Default")
      (node (ref "A05") (pin "A1") (pinfunction "IN1_A1") (pintype "input"))
      (node (ref "A09") (pin "M2") (pinfunction "4B_M2") (pintype "input"))
      (node (ref "A15") (pin "L1") (pinfunction "IN1_L1") (pintype "input"))
      (node (ref "B27") (pin "M2") (pinfunction "M2_M2") (pintype "input"))
      (node (ref "B37") (pin "M2") (pinfunction "M2_M2") (pintype "input"))
      (node (ref "C17") (pin "U2") (pinfunction "IN2_U2") (pintype "input"))
      (node (ref "D13") (pin "R1") (pinfunction "IN2_R1") (pintype "input"))
      (node (ref "EF39") (pin "AU2") (pinfunction "AU2_AU2") (pintype "output"))
      (node (ref "F21") (pin "L2") (pinfunction "IN1_L2") (pintype "input"))
      (node (ref "F26") (pin "H1") (pinfunction "IN3_H1") (pintype "input"))
      (node (ref "F26") (pin "L2") (pinfunction "IN3_L2") (pintype "input"))
      (node (ref "F40") (pin "K1") (pinfunction "P$2_K1") (pintype "bidirectional"))
      (node (ref "HJ31") (pin "BP1") (pinfunction "BP1_BP1") (pintype "input"))
    )
    (net (code "530") (name "MB11") (class "Default")
      (node (ref "A09") (pin "T2") (pinfunction "8A_T2") (pintype "input"))
      (node (ref "A11") (pin "B1") (pinfunction "IN2_B1") (pintype "input"))
      (node (ref "B13") (pin "R2") (pinfunction "IN1_R2") (pintype "input"))
      (node (ref "D10") (pin "R1") (pinfunction "IN4_R1") (pintype "input"))
      (node (ref "D10") (pin "U2") (pinfunction "IN4_U2") (pintype "input"))
      (node (ref "D18") (pin "E1") (pinfunction "IN1_E1") (pintype "input"))
      (node (ref "D18") (pin "F2") (pinfunction "IN3_F2") (pintype "input"))
      (node (ref "D20") (pin "R1") (pinfunction "IN4_R1") (pintype "input"))
      (node (ref "D21") (pin "F1") (pinfunction "IN1_F1") (pintype "input"))
      (node (ref "E27") (pin "J1") (pinfunction "IN3B_J1") (pintype "input"))
      (node (ref "EF39") (pin "AS2") (pinfunction "AS2_AS2") (pintype "output"))
      (node (ref "F20") (pin "E2") (pinfunction "IN2_E2") (pintype "input"))
      (node (ref "H18") (pin "U2") (pinfunction "IN2_U2") (pintype "input"))
      (node (ref "H30") (pin "A1") (pinfunction "A1_A1") (pintype "input"))
      (node (ref "HJ23") (pin "AP1") (pinfunction "AP1_AP1") (pintype "input"))
    )
    (net (code "531") (name "MB11_") (class "Default")
      (node (ref "A09") (pin "N2") (pinfunction "8B_N2") (pintype "input"))
      (node (ref "A13") (pin "A1") (pinfunction "IN1_A1") (pintype "input"))
      (node (ref "B04") (pin "D2") (pinfunction "IN1_D2") (pintype "input"))
      (node (ref "B27") (pin "L1") (pinfunction "L1_L1") (pintype "input"))
      (node (ref "B37") (pin "L1") (pinfunction "L1_L1") (pintype "input"))
      (node (ref "C18") (pin "R1") (pinfunction "IN2_R1") (pintype "input"))
      (node (ref "D09") (pin "F2") (pinfunction "IN3_F2") (pintype "input"))
      (node (ref "D10") (pin "H2") (pinfunction "IN4_H2") (pintype "input"))
      (node (ref "E13") (pin "B1") (pinfunction "IN1B_B1") (pintype "input"))
      (node (ref "E25") (pin "N2") (pinfunction "IN1_N2") (pintype "input"))
      (node (ref "E28") (pin "S2") (pinfunction "IN4D_S2") (pintype "input"))
      (node (ref "E33") (pin "P1") (pinfunction "D_P1") (pintype "input"))
      (node (ref "EF39") (pin "AS1") (pinfunction "AS1_AS1") (pintype "output"))
      (node (ref "F21") (pin "M2") (pinfunction "IN2_M2") (pintype "input"))
      (node (ref "F28") (pin "P2") (pinfunction "IN2_P2") (pintype "input"))
      (node (ref "F40") (pin "A1") (pinfunction "P$2_A1") (pintype "bidirectional"))
    )
    (net (code "532") (name "MB_LOAD") (class "Default")
      (node (ref "E32") (pin "L1") (pinfunction "OUT_L1") (pintype "open_collector"))
      (node (ref "EF34") (pin "AR1") (pinfunction "AR1_AR1") (pintype "input"))
      (node (ref "EF35") (pin "AR1") (pinfunction "AR1_AR1") (pintype "input"))
      (node (ref "EF36") (pin "AR1") (pinfunction "AR1_AR1") (pintype "input"))
      (node (ref "EF37") (pin "AR1") (pinfunction "AR1_AR1") (pintype "input"))
      (node (ref "EF38") (pin "AR1") (pinfunction "AR1_AR1") (pintype "input"))
      (node (ref "EF39") (pin "AR1") (pinfunction "AR1_AR1") (pintype "input"))
    )
    (net (code "533") (name "MB_PARITY_ODD") (class "Default")
      (node (ref "A10") (pin "K1") (pinfunction "ODD_K1") (pintype "output"))
      (node (ref "A37") (pin "D2") (pinfunction "D2_D2") (pintype "input"))
      (node (ref "A37") (pin "M2") (pinfunction "M2_M2") (pintype "input"))
      (node (ref "H05") (pin "T2") (pinfunction "P$2_T2") (pintype "bidirectional"))
    )
    (net (code "534") (name "MB_TO_IB") (class "Default")
      (node (ref "A15") (pin "S1") (pinfunction "OUT_S1") (pintype "output"))
      (node (ref "A18") (pin "D2") (pinfunction "IN1_D2") (pintype "input"))
      (node (ref "A18") (pin "L1") (pinfunction "IN1_L1") (pintype "input"))
      (node (ref "A18") (pin "P2") (pinfunction "IN1_P2") (pintype "input"))
    )
    (net (code "535") (name "MB_TO_SC_ENABLE") (class "Default")
      (node (ref "C14") (pin "T2") (pinfunction "IN1_T2") (pintype "input"))
      (node (ref "C15") (pin "T2") (pinfunction "IN1_T2") (pintype "input"))
      (node (ref "C16") (pin "T2") (pinfunction "IN1_T2") (pintype "input"))
      (node (ref "C17") (pin "T2") (pinfunction "IN1_T2") (pintype "input"))
      (node (ref "C18") (pin "P1") (pinfunction "IN1_P1") (pintype "input"))
      (node (ref "D15") (pin "N2") (pinfunction "OUT_N2") (pintype "output"))
    )
    (net (code "536") (name "MCBMB00_") (class "Default")
      (node (ref "B12") (pin "E1") (pinfunction "OUT_E1") (pintype "open_collector"))
      (node (ref "H02") (pin "S2") (pinfunction "P$2_S2") (pintype "bidirectional"))
    )
    (net (code "537") (name "MCBMB01_") (class "Default")
      (node (ref "B12") (pin "J2") (pinfunction "OUT_J2") (pintype "open_collector"))
      (node (ref "H02") (pin "T2") (pinfunction "P$2_T2") (pintype "bidirectional"))
    )
    (net (code "538") (name "MCBMB02_") (class "Default")
      (node (ref "B12") (pin "L1") (pinfunction "OUT_L1") (pintype "open_collector"))
      (node (ref "H02") (pin "V2") (pinfunction "P$2_V2") (pintype "bidirectional"))
    )
    (net (code "539") (name "MCBMB03_") (class "Default")
      (node (ref "B12") (pin "P2") (pinfunction "OUT_P2") (pintype "open_collector"))
      (node (ref "H03") (pin "D2") (pinfunction "P$2_D2") (pintype "bidirectional"))
    )
    (net (code "540") (name "MCBMB04_") (class "Default")
      (node (ref "B12") (pin "S1") (pinfunction "OUT_S1") (pintype "open_collector"))
      (node (ref "H03") (pin "E2") (pinfunction "P$2_E2") (pintype "bidirectional"))
    )
    (net (code "541") (name "MCBMB05_") (class "Default")
      (node (ref "B12") (pin "V2") (pinfunction "OUT_V2") (pintype "open_collector"))
      (node (ref "H03") (pin "H2") (pinfunction "P$2_H2") (pintype "bidirectional"))
    )
    (net (code "542") (name "MCBMB06_") (class "Default")
      (node (ref "B13") (pin "E1") (pinfunction "OUT_E1") (pintype "open_collector"))
      (node (ref "H03") (pin "K2") (pinfunction "P$2_K2") (pintype "bidirectional"))
    )
    (net (code "543") (name "MCBMB07_") (class "Default")
      (node (ref "B13") (pin "J2") (pinfunction "OUT_J2") (pintype "open_collector"))
      (node (ref "H03") (pin "M2") (pinfunction "P$2_M2") (pintype "bidirectional"))
    )
    (net (code "544") (name "MCBMB08_") (class "Default")
      (node (ref "B13") (pin "L1") (pinfunction "OUT_L1") (pintype "open_collector"))
      (node (ref "H03") (pin "P2") (pinfunction "P$2_P2") (pintype "bidirectional"))
    )
    (net (code "545") (name "MCBMB09_") (class "Default")
      (node (ref "B13") (pin "P2") (pinfunction "OUT_P2") (pintype "open_collector"))
      (node (ref "H03") (pin "S2") (pinfunction "P$2_S2") (pintype "bidirectional"))
    )
    (net (code "546") (name "MCBMB10_") (class "Default")
      (node (ref "B13") (pin "S1") (pinfunction "OUT_S1") (pintype "open_collector"))
      (node (ref "H03") (pin "T2") (pinfunction "P$2_T2") (pintype "bidirectional"))
    )
    (net (code "547") (name "MCBMB11_") (class "Default")
      (node (ref "B13") (pin "V2") (pinfunction "OUT_V2") (pintype "open_collector"))
      (node (ref "H03") (pin "V2") (pinfunction "P$2_V2") (pintype "bidirectional"))
    )
    (net (code "548") (name "ME05_") (class "Default")
      (node (ref "A05") (pin "K2") (pinfunction "OUT_K2") (pintype "output"))
      (node (ref "J13") (pin "U2") (pinfunction "IN4_U2") (pintype "input"))
    )
    (net (code "549") (name "ME06_") (class "Default")
      (node (ref "A13") (pin "N1") (pinfunction "OUT_N1") (pintype "output"))
      (node (ref "J14") (pin "D1") (pinfunction "IN4_D1") (pintype "input"))
    )
    (net (code "550") (name "ME07_") (class "Default")
      (node (ref "A13") (pin "S1") (pinfunction "OUT_S1") (pintype "output"))
      (node (ref "J14") (pin "H2") (pinfunction "IN4_H2") (pintype "input"))
    )
    (net (code "551") (name "ME08_") (class "Default")
      (node (ref "A13") (pin "V2") (pinfunction "OUT_V2") (pintype "output"))
      (node (ref "J14") (pin "K1") (pinfunction "IN4_K1") (pintype "input"))
    )
    (net (code "552") (name "ME09_") (class "Default")
      (node (ref "A13") (pin "K2") (pinfunction "OUT_K2") (pintype "output"))
      (node (ref "J14") (pin "N2") (pinfunction "IN4_N2") (pintype "input"))
    )
    (net (code "553") (name "ME10_") (class "Default")
      (node (ref "A13") (pin "N2") (pinfunction "OUT_N2") (pintype "output"))
      (node (ref "J14") (pin "R1") (pinfunction "IN4_R1") (pintype "input"))
    )
    (net (code "554") (name "ME11_") (class "Default")
      (node (ref "A13") (pin "S2") (pinfunction "OUT_S2") (pintype "output"))
      (node (ref "J14") (pin "U2") (pinfunction "IN4_U2") (pintype "input"))
    )
    (net (code "555") (name "MEM00") (class "Default")
      (node (ref "A07") (pin "E1") (pinfunction "1A_E1") (pintype "input"))
      (node (ref "A31") (pin "A1") (pinfunction "A1_A1") (pintype "open_collector"))
      (node (ref "B08") (pin "H1") (pinfunction "IN1_H1") (pintype "input"))
      (node (ref "C09") (pin "A1") (pinfunction "IN1_A1") (pintype "input"))
      (node (ref "EF34") (pin "BR1") (pinfunction "BR1_BR1") (pintype "input"))
      (node (ref "F22") (pin "B1") (pinfunction "IN2_B1") (pintype "input"))
      (node (ref "H04") (pin "E2") (pinfunction "P$2_E2") (pintype "bidirectional"))
    )
    (net (code "556") (name "MEM01") (class "Default")
      (node (ref "A07") (pin "F1") (pinfunction "2A_F1") (pintype "input"))
      (node (ref "A31") (pin "U2") (pinfunction "U2_U2") (pintype "open_collector"))
      (node (ref "B08") (pin "D2") (pinfunction "IN1_D2") (pintype "input"))
      (node (ref "E20") (pin "E2") (pinfunction "D_E2") (pintype "input"))
      (node (ref "EF34") (pin "BV2") (pinfunction "BV2_BV2") (pintype "input"))
      (node (ref "H04") (pin "H2") (pinfunction "P$2_H2") (pintype "bidirectional"))
    )
    (net (code "557") (name "MEM02") (class "Default")
      (node (ref "A07") (pin "H1") (pinfunction "4A_H1") (pintype "input"))
      (node (ref "A32") (pin "A1") (pinfunction "A1_A1") (pintype "open_collector"))
      (node (ref "B08") (pin "D1") (pinfunction "IN1_D1") (pintype "input"))
      (node (ref "E20") (pin "J1") (pinfunction "D_J1") (pintype "input"))
      (node (ref "EF35") (pin "BR1") (pinfunction "BR1_BR1") (pintype "input"))
      (node (ref "H04") (pin "K2") (pinfunction "P$2_K2") (pintype "bidirectional"))
    )
    (net (code "558") (name "MEM03") (class "Default")
      (node (ref "A07") (pin "J1") (pinfunction "8A_J1") (pintype "input"))
      (node (ref "A32") (pin "U2") (pinfunction "U2_U2") (pintype "open_collector"))
      (node (ref "B08") (pin "A1") (pinfunction "IN1_A1") (pintype "input"))
      (node (ref "EF35") (pin "BV2") (pinfunction "BV2_BV2") (pintype "input"))
      (node (ref "H04") (pin "M2") (pinfunction "P$2_M2") (pintype "bidirectional"))
    )
    (net (code "559") (name "MEM04") (class "Default")
      (node (ref "A08") (pin "P2") (pinfunction "1A_P2") (pintype "input"))
      (node (ref "A33") (pin "A1") (pinfunction "A1_A1") (pintype "open_collector"))
      (node (ref "B08") (pin "P1") (pinfunction "IN1_P1") (pintype "input"))
      (node (ref "EF36") (pin "BR1") (pinfunction "BR1_BR1") (pintype "input"))
      (node (ref "H04") (pin "P2") (pinfunction "P$2_P2") (pintype "bidirectional"))
    )
    (net (code "560") (name "MEM05") (class "Default")
      (node (ref "A08") (pin "R2") (pinfunction "2A_R2") (pintype "input"))
      (node (ref "A33") (pin "U2") (pinfunction "U2_U2") (pintype "open_collector"))
      (node (ref "B08") (pin "L2") (pinfunction "IN1_L2") (pintype "input"))
      (node (ref "EF36") (pin "BV2") (pinfunction "BV2_BV2") (pintype "input"))
      (node (ref "H04") (pin "S2") (pinfunction "P$2_S2") (pintype "bidirectional"))
    )
    (net (code "561") (name "MEM06") (class "Default")
      (node (ref "A08") (pin "S2") (pinfunction "4A_S2") (pintype "input"))
      (node (ref "B08") (pin "L1") (pinfunction "IN1_L1") (pintype "input"))
      (node (ref "B31") (pin "A1") (pinfunction "A1_A1") (pintype "open_collector"))
      (node (ref "EF37") (pin "BR1") (pinfunction "BR1_BR1") (pintype "input"))
      (node (ref "H04") (pin "T2") (pinfunction "P$2_T2") (pintype "bidirectional"))
    )
    (net (code "562") (name "MEM07") (class "Default")
      (node (ref "A08") (pin "T2") (pinfunction "8A_T2") (pintype "input"))
      (node (ref "B08") (pin "H2") (pinfunction "IN1_H2") (pintype "input"))
      (node (ref "B31") (pin "U2") (pinfunction "U2_U2") (pintype "open_collector"))
      (node (ref "EF37") (pin "BV2") (pinfunction "BV2_BV2") (pintype "input"))
      (node (ref "H04") (pin "V2") (pinfunction "P$2_V2") (pintype "bidirectional"))
    )
    (net (code "563") (name "MEM08") (class "Default")
      (node (ref "A07") (pin "P2") (pinfunction "1A_P2") (pintype "input"))
      (node (ref "B09") (pin "D1") (pinfunction "IN1_D1") (pintype "input"))
      (node (ref "B32") (pin "A1") (pinfunction "A1_A1") (pintype "open_collector"))
      (node (ref "EF38") (pin "BR1") (pinfunction "BR1_BR1") (pintype "input"))
      (node (ref "H05") (pin "D2") (pinfunction "P$2_D2") (pintype "bidirectional"))
    )
    (net (code "564") (name "MEM09") (class "Default")
      (node (ref "A07") (pin "R2") (pinfunction "2A_R2") (pintype "input"))
      (node (ref "B09") (pin "A1") (pinfunction "IN1_A1") (pintype "input"))
      (node (ref "B32") (pin "U2") (pinfunction "U2_U2") (pintype "open_collector"))
      (node (ref "D09") (pin "C1") (pinfunction "IN3_C1") (pintype "input"))
      (node (ref "EF38") (pin "BV2") (pinfunction "BV2_BV2") (pintype "input"))
      (node (ref "H05") (pin "E2") (pinfunction "P$2_E2") (pintype "bidirectional"))
    )
    (net (code "565") (name "MEM10") (class "Default")
      (node (ref "A07") (pin "S2") (pinfunction "4A_S2") (pintype "input"))
      (node (ref "B08") (pin "T2") (pinfunction "IN1_T2") (pintype "input"))
      (node (ref "B33") (pin "A1") (pinfunction "A1_A1") (pintype "open_collector"))
      (node (ref "EF39") (pin "BR1") (pinfunction "BR1_BR1") (pintype "input"))
      (node (ref "H05") (pin "H2") (pinfunction "P$2_H2") (pintype "bidirectional"))
    )
    (net (code "566") (name "MEM11") (class "Default")
      (node (ref "A07") (pin "T2") (pinfunction "8A_T2") (pintype "input"))
      (node (ref "B08") (pin "P2") (pinfunction "IN1_P2") (pintype "input"))
      (node (ref "B33") (pin "U2") (pinfunction "U2_U2") (pintype "open_collector"))
      (node (ref "EF39") (pin "BV2") (pinfunction "BV2_BV2") (pintype "input"))
      (node (ref "H05") (pin "K2") (pinfunction "P$2_K2") (pintype "bidirectional"))
    )
    (net (code "567") (name "MEMORY_INCREMENT") (class "Default")
      (node (ref "E11") (pin "U2") (pinfunction "IN2_U2") (pintype "input"))
      (node (ref "E27") (pin "R2") (pinfunction "IN4C_R2") (pintype "input"))
      (node (ref "J20") (pin "E1") (pinfunction "OUT_E1") (pintype "output"))
    )
    (net (code "568") (name "MEM_BEGIN_") (class "Default")
      (node (ref "A30") (pin "B1") (pinfunction "B1_B1") (pintype "input"))
      (node (ref "A31") (pin "B1") (pinfunction "B1_B1") (pintype "input"))
      (node (ref "A32") (pin "B1") (pinfunction "B1_B1") (pintype "input"))
      (node (ref "A33") (pin "B1") (pinfunction "B1_B1") (pintype "input"))
      (node (ref "B22") (pin "K1") (pinfunction "S_K1") (pintype "input"))
      (node (ref "B30") (pin "S1") (pinfunction "OUT_S1") (pintype "open_collector"))
      (node (ref "B31") (pin "B1") (pinfunction "B1_B1") (pintype "input"))
      (node (ref "B32") (pin "B1") (pinfunction "B1_B1") (pintype "input"))
      (node (ref "B33") (pin "B1") (pinfunction "B1_B1") (pintype "input"))
    )
    (net (code "569") (name "MEM_DONE_") (class "Default")
      (node (ref "B10") (pin "D2") (pinfunction "D2_D2") (pintype "open_collector"))
      (node (ref "B23") (pin "V2") (pinfunction "OUT_V2") (pintype "open_collector"))
      (node (ref "C07") (pin "T2") (pinfunction "IN3_T2") (pintype "input"))
      (node (ref "E18") (pin "F2") (pinfunction "S_F2") (pintype "input"))
      (node (ref "E33") (pin "F2") (pinfunction "S_F2") (pintype "input"))
      (node (ref "H05") (pin "S2") (pinfunction "P$2_S2") (pintype "bidirectional"))
    )
    (net (code "570") (name "MEM_ENABLE0_4") (class "Default")
      (node (ref "EF34") (pin "BU2") (pinfunction "BU2_BU2") (pintype "input"))
      (node (ref "EF34") (pin "BV1") (pinfunction "BV1_BV1") (pintype "input"))
      (node (ref "EF35") (pin "BU2") (pinfunction "BU2_BU2") (pintype "input"))
      (node (ref "EF35") (pin "BV1") (pinfunction "BV1_BV1") (pintype "input"))
      (node (ref "EF36") (pin "BU2") (pinfunction "BU2_BU2") (pintype "input"))
      (node (ref "F27") (pin "R1") (pinfunction "IN4_R1") (pintype "input"))
      (node (ref "F29") (pin "A1") (pinfunction "IN1_A1") (pintype "input"))
      (node (ref "F31") (pin "E1") (pinfunction "OUT_E1") (pintype "open_collector"))
    )
    (net (code "571") (name "MEM_ENABLE0_4_") (class "Default")
      (node (ref "F28") (pin "E2") (pinfunction "IN2_E2") (pintype "input"))
      (node (ref "F29") (pin "C1") (pinfunction "OUT_C1") (pintype "output"))
      (node (ref "F31") (pin "F2") (pinfunction "IN3_F2") (pintype "input"))
    )
    (net (code "572") (name "MEM_ENABLE5_8") (class "Default")
      (node (ref "E09") (pin "H2") (pinfunction "IN1_H2") (pintype "input"))
      (node (ref "EF36") (pin "BV1") (pinfunction "BV1_BV1") (pintype "input"))
      (node (ref "EF37") (pin "BU2") (pinfunction "BU2_BU2") (pintype "input"))
      (node (ref "EF37") (pin "BV1") (pinfunction "BV1_BV1") (pintype "input"))
      (node (ref "EF38") (pin "BU2") (pinfunction "BU2_BU2") (pintype "input"))
      (node (ref "F28") (pin "D2") (pinfunction "IN1_D2") (pintype "input"))
      (node (ref "F31") (pin "J2") (pinfunction "OUT_J2") (pintype "open_collector"))
    )
    (net (code "573") (name "MEM_ENABLE9_11") (class "Default")
      (node (ref "EF38") (pin "BV1") (pinfunction "BV1_BV1") (pintype "input"))
      (node (ref "EF39") (pin "BU2") (pinfunction "BU2_BU2") (pintype "input"))
      (node (ref "EF39") (pin "BV1") (pinfunction "BV1_BV1") (pintype "input"))
      (node (ref "F11") (pin "P2") (pinfunction "OUT_P2") (pintype "output"))
    )
    (net (code "574") (name "MEM_ENABLE_") (class "Default")
      (node (ref "B22") (pin "F1") (pinfunction "0_F1") (pintype "output"))
      (node (ref "B30") (pin "A1") (pinfunction "IN1_A1") (pintype "input"))
    )
    (net (code "575") (name "MEM_EXT") (class "Default")
      (node (ref "A11") (pin "A1") (pinfunction "IN1_A1") (pintype "input"))
      (node (ref "A13") (pin "E2") (pinfunction "IN2_E2") (pintype "input"))
      (node (ref "A14") (pin "E2") (pinfunction "IN2_E2") (pintype "input"))
      (node (ref "A14") (pin "K1") (pinfunction "OUT_K1") (pintype "output"))
      (node (ref "A15") (pin "R2") (pinfunction "IN2_R2") (pintype "input"))
    )
    (net (code "576") (name "MEM_EXT_") (class "Default")
      (node (ref "A14") (pin "F1") (pinfunction "OUT_F1") (pintype "output"))
      (node (ref "A14") (pin "H1") (pinfunction "IN1_H1") (pintype "input"))
      (node (ref "F19") (pin "B1") (pinfunction "IN2_B1") (pintype "input"))
    )
    (net (code "577") (name "MEM_EXT_AC_LOAD_ENABLE_") (class "Default")
      (node (ref "A14") (pin "S2") (pinfunction "OUT_S2") (pintype "output"))
      (node (ref "E32") (pin "N2") (pinfunction "IN4_N2") (pintype "input"))
    )
    (net (code "578") (name "MEM_EXT_IO_ENABLE_") (class "Default")
      (node (ref "C12") (pin "J2") (pinfunction "OUT_J2") (pintype "open_collector"))
      (node (ref "F30") (pin "E2") (pinfunction "IN2_E2") (pintype "input"))
    )
    (net (code "579") (name "MEM_FINISH") (class "Default")
      (node (ref "A24") (pin "F1") (pinfunction "OUT_F1") (pintype "output"))
      (node (ref "B22") (pin "L2") (pinfunction "C_L2") (pintype "input"))
      (node (ref "B22") (pin "N1") (pinfunction "C_N1") (pintype "input"))
      (node (ref "B23") (pin "U2") (pinfunction "IN_U2") (pintype "input"))
    )
    (net (code "580") (name "MEM_IDLE") (class "Default")
      (node (ref "E14") (pin "A1") (pinfunction "IN1_A1") (pintype "input"))
      (node (ref "E18") (pin "H2") (pinfunction "1_H2") (pintype "output"))
    )
    (net (code "581") (name "MEM_INH9_11_") (class "Default")
      (node (ref "C09") (pin "K2") (pinfunction "OUT_K2") (pintype "output"))
      (node (ref "D10") (pin "J1") (pinfunction "IN3_J1") (pintype "input"))
      (node (ref "E09") (pin "J2") (pinfunction "IN2_J2") (pintype "input"))
    )
    (net (code "582") (name "MEM_P") (class "Default")
      (node (ref "A08") (pin "J1") (pinfunction "8A_J1") (pintype "input"))
      (node (ref "A30") (pin "A1") (pinfunction "A1_A1") (pintype "open_collector"))
      (node (ref "B08") (pin "V1") (pinfunction "P$1_V1") (pintype "passive"))
      (node (ref "B09") (pin "E2") (pinfunction "IN2_E2") (pintype "input"))
      (node (ref "H04") (pin "D2") (pinfunction "P$2_D2") (pintype "bidirectional"))
    )
    (net (code "583") (name "MEM_PARITY_EVEN_") (class "Default")
      (node (ref "A08") (pin "L1") (pinfunction "EVEN_L1") (pintype "output"))
      (node (ref "B09") (pin "U2") (pinfunction "IN2_U2") (pintype "input"))
    )
    (net (code "584") (name "MEM_START") (class "Default")
      (node (ref "B21") (pin "E1") (pinfunction "IN2_E1") (pintype "input"))
      (node (ref "B22") (pin "B1") (pinfunction "C_B1") (pintype "input"))
      (node (ref "E15") (pin "F1") (pinfunction "OUT_F1") (pintype "output"))
    )
    (net (code "585") (name "MEM_TO_LSR_") (class "Default")
      (node (ref "C08") (pin "P2") (pinfunction "IN2_P2") (pintype "input"))
      (node (ref "D07") (pin "K1") (pinfunction "OUT_K1") (pintype "output"))
    )
    (net (code "586") (name "MFTP0") (class "Default")
      (node (ref "EF10") (pin "AT2") (pinfunction "CT2_AT2") (pintype "output"))
      (node (ref "F20") (pin "T2") (pinfunction "IN1_T2") (pintype "input"))
      (node (ref "F30") (pin "U2") (pinfunction "IN4_U2") (pintype "input"))
    )
    (net (code "587") (name "MFTP1") (class "Default")
      (node (ref "A19") (pin "J2") (pinfunction "IN2_J2") (pintype "input"))
      (node (ref "E12") (pin "M2") (pinfunction "IN2_M2") (pintype "input"))
      (node (ref "EF10") (pin "AE2") (pinfunction "CE2_AE2") (pintype "output"))
      (node (ref "F32") (pin "D1") (pinfunction "IN1_D1") (pintype "input"))
    )
    (net (code "588") (name "MFTP2") (class "Default")
      (node (ref "E15") (pin "A1") (pinfunction "IN1_A1") (pintype "input"))
      (node (ref "E15") (pin "H1") (pinfunction "IN1_H1") (pintype "input"))
      (node (ref "E26") (pin "J2") (pinfunction "IN2A_J2") (pintype "input"))
      (node (ref "E26") (pin "K1") (pinfunction "IN4A_K1") (pintype "input"))
      (node (ref "E26") (pin "V1") (pinfunction "IN2A_V1") (pintype "input"))
      (node (ref "EF10") (pin "BD2") (pinfunction "DD2_BD2") (pintype "output"))
      (node (ref "F22") (pin "D2") (pinfunction "IN1_D2") (pintype "input"))
    )
    (net (code "589") (name "MFTS0") (class "Default")
      (node (ref "E13") (pin "J1") (pinfunction "IN3B_J1") (pintype "input"))
      (node (ref "E14") (pin "T2") (pinfunction "IN1_T2") (pintype "input"))
      (node (ref "EF10") (pin "AM2") (pinfunction "CM2_AM2") (pintype "output"))
      (node (ref "F29") (pin "R2") (pinfunction "IN2_R2") (pintype "input"))
    )
    (net (code "590") (name "MFTS1") (class "Default")
      (node (ref "E14") (pin "E2") (pinfunction "IN2_E2") (pintype "input"))
      (node (ref "EF10") (pin "AJ2") (pinfunction "CJ2_AJ2") (pintype "output"))
    )
    (net (code "591") (name "MFTS1_") (class "Default")
      (node (ref "E14") (pin "U2") (pinfunction "IN2_U2") (pintype "input"))
      (node (ref "EF10") (pin "AK2") (pinfunction "CK2_AK2") (pintype "output"))
    )
    (net (code "592") (name "MFTS2") (class "Default")
      (node (ref "E27") (pin "J2") (pinfunction "IN2A_J2") (pintype "input"))
      (node (ref "E28") (pin "E1") (pinfunction "IN2A_E1") (pintype "input"))
      (node (ref "E30") (pin "K1") (pinfunction "IN4A_K1") (pintype "input"))
      (node (ref "EF10") (pin "AF2") (pinfunction "CF2_AF2") (pintype "output"))
    )
    (net (code "593") (name "MFTS2_") (class "Default")
      (node (ref "D12") (pin "R1") (pinfunction "IN2_R1") (pintype "input"))
      (node (ref "E14") (pin "V2") (pinfunction "IN3_V2") (pintype "input"))
      (node (ref "EF10") (pin "AH2") (pinfunction "CH2_AH2") (pintype "output"))
    )
    (net (code "594") (name "MFTS3") (class "Default")
      (node (ref "E15") (pin "V2") (pinfunction "OUT_V2") (pintype "output"))
      (node (ref "E29") (pin "N2") (pinfunction "IN4A_N2") (pintype "input"))
      (node (ref "F29") (pin "R1") (pinfunction "IN2_R1") (pintype "input"))
    )
    (net (code "595") (name "MID_AC0") (class "Default")
      (node (ref "D19") (pin "M1") (pinfunction "IN3_M1") (pintype "input"))
      (node (ref "D20") (pin "B1") (pinfunction "IN2_B1") (pintype "input"))
      (node (ref "E24") (pin "S1") (pinfunction "OUT_S1") (pintype "output"))
      (node (ref "F23") (pin "B1") (pinfunction "IN2_B1") (pintype "input"))
    )
    (net (code "596") (name "MP_INT") (class "Default")
      (node (ref "B09") (pin "R1") (pinfunction "IN2_R1") (pintype "input"))
      (node (ref "B09") (pin "S2") (pinfunction "OUT_S2") (pintype "output"))
    )
    (net (code "597") (name "MP_INT_") (class "Default")
      (node (ref "B07") (pin "L2") (pinfunction "IN3_L2") (pintype "input"))
      (node (ref "B09") (pin "P2") (pinfunction "IN1_P2") (pintype "input"))
      (node (ref "B09") (pin "S1") (pinfunction "OUT_S1") (pintype "output"))
      (node (ref "J15") (pin "H2") (pinfunction "IN4_H2") (pintype "input"))
    )
    (net (code "598") (name "MP_SKIP_") (class "Default")
      (node (ref "B07") (pin "M2") (pinfunction "OUT_M2") (pintype "output"))
      (node (ref "J15") (pin "D1") (pinfunction "IN4_D1") (pintype "input"))
    )
    (net (code "599") (name "MQ00") (class "Default")
      (node (ref "C14") (pin "J1") (pinfunction "IN2_J1") (pintype "input"))
      (node (ref "C23") (pin "E1") (pinfunction "1_E1") (pintype "output"))
      (node (ref "D18") (pin "S1") (pinfunction "IN3_S1") (pintype "input"))
      (node (ref "EF34") (pin "BH1") (pinfunction "BH1_BH1") (pintype "input"))
    )
    (net (code "600") (name "MQ00_") (class "Default")
      (node (ref "C23") (pin "F1") (pinfunction "0_F1") (pintype "output"))
      (node (ref "D18") (pin "N2") (pinfunction "IN1_N2") (pintype "input"))
      (node (ref "D21") (pin "K2") (pinfunction "IN1_K2") (pintype "input"))
      (node (ref "E40") (pin "S2") (pinfunction "P$2_S2") (pintype "bidirectional"))
    )
    (net (code "601") (name "MQ01") (class "Default")
      (node (ref "C14") (pin "E2") (pinfunction "IN2_E2") (pintype "input"))
      (node (ref "C14") (pin "M2") (pinfunction "IN2_M2") (pintype "input"))
      (node (ref "C23") (pin "H2") (pinfunction "1_H2") (pintype "output"))
      (node (ref "EF34") (pin "BN2") (pinfunction "BN2_BN2") (pintype "input"))
    )
    (net (code "602") (name "MQ01_") (class "Default")
      (node (ref "C23") (pin "J2") (pinfunction "0_J2") (pintype "output"))
      (node (ref "D21") (pin "L2") (pinfunction "IN2_L2") (pintype "input"))
      (node (ref "E40") (pin "M2") (pinfunction "P$2_M2") (pintype "bidirectional"))
    )
    (net (code "603") (name "MQ02") (class "Default")
      (node (ref "C14") (pin "M1") (pinfunction "IN2_M1") (pintype "input"))
      (node (ref "C15") (pin "B1") (pinfunction "IN2_B1") (pintype "input"))
      (node (ref "C23") (pin "L1") (pinfunction "1_L1") (pintype "output"))
      (node (ref "EF35") (pin "BH1") (pinfunction "BH1_BH1") (pintype "input"))
    )
    (net (code "604") (name "MQ02_") (class "Default")
      (node (ref "C23") (pin "M1") (pinfunction "0_M1") (pintype "output"))
      (node (ref "D21") (pin "M2") (pinfunction "IN3_M2") (pintype "input"))
      (node (ref "E40") (pin "N2") (pinfunction "P$2_N2") (pintype "bidirectional"))
    )
    (net (code "605") (name "MQ03") (class "Default")
      (node (ref "C14") (pin "R2") (pinfunction "IN2_R2") (pintype "input"))
      (node (ref "C15") (pin "J1") (pinfunction "IN2_J1") (pintype "input"))
      (node (ref "C23") (pin "P2") (pinfunction "1_P2") (pintype "output"))
      (node (ref "EF35") (pin "BN2") (pinfunction "BN2_BN2") (pintype "input"))
    )
    (net (code "606") (name "MQ03_") (class "Default")
      (node (ref "C23") (pin "R2") (pinfunction "0_R2") (pintype "output"))
      (node (ref "D21") (pin "N2") (pinfunction "IN4_N2") (pintype "input"))
      (node (ref "E40") (pin "L2") (pinfunction "P$2_L2") (pintype "bidirectional"))
    )
    (net (code "607") (name "MQ04") (class "Default")
      (node (ref "C15") (pin "E2") (pinfunction "IN2_E2") (pintype "input"))
      (node (ref "C15") (pin "M2") (pinfunction "IN2_M2") (pintype "input"))
      (node (ref "C23") (pin "S1") (pinfunction "1_S1") (pintype "output"))
      (node (ref "EF36") (pin "BH1") (pinfunction "BH1_BH1") (pintype "input"))
    )
    (net (code "608") (name "MQ04_") (class "Default")
      (node (ref "C23") (pin "U1") (pinfunction "0_U1") (pintype "output"))
      (node (ref "D21") (pin "M1") (pinfunction "IN1_M1") (pintype "input"))
      (node (ref "E40") (pin "F1") (pinfunction "P$2_F1") (pintype "bidirectional"))
    )
    (net (code "609") (name "MQ05") (class "Default")
      (node (ref "C15") (pin "M1") (pinfunction "IN2_M1") (pintype "input"))
      (node (ref "C16") (pin "B1") (pinfunction "IN2_B1") (pintype "input"))
      (node (ref "C23") (pin "V2") (pinfunction "1_V2") (pintype "output"))
      (node (ref "EF36") (pin "BN2") (pinfunction "BN2_BN2") (pintype "input"))
    )
    (net (code "610") (name "MQ05_") (class "Default")
      (node (ref "C23") (pin "V1") (pinfunction "0_V1") (pintype "output"))
      (node (ref "D21") (pin "N1") (pinfunction "IN2_N1") (pintype "input"))
      (node (ref "E40") (pin "H1") (pinfunction "P$2_H1") (pintype "bidirectional"))
    )
    (net (code "611") (name "MQ06") (class "Default")
      (node (ref "C15") (pin "R2") (pinfunction "IN2_R2") (pintype "input"))
      (node (ref "C16") (pin "J1") (pinfunction "IN2_J1") (pintype "input"))
      (node (ref "C24") (pin "E1") (pinfunction "1_E1") (pintype "output"))
      (node (ref "EF37") (pin "BH1") (pinfunction "BH1_BH1") (pintype "input"))
    )
    (net (code "612") (name "MQ06_") (class "Default")
      (node (ref "C24") (pin "F1") (pinfunction "0_F1") (pintype "output"))
      (node (ref "D21") (pin "P1") (pinfunction "IN3_P1") (pintype "input"))
      (node (ref "F40") (pin "S2") (pinfunction "P$2_S2") (pintype "bidirectional"))
    )
    (net (code "613") (name "MQ07") (class "Default")
      (node (ref "C16") (pin "E2") (pinfunction "IN2_E2") (pintype "input"))
      (node (ref "C16") (pin "M2") (pinfunction "IN2_M2") (pintype "input"))
      (node (ref "C24") (pin "H2") (pinfunction "1_H2") (pintype "output"))
      (node (ref "EF37") (pin "BN2") (pinfunction "BN2_BN2") (pintype "input"))
    )
    (net (code "614") (name "MQ07_") (class "Default")
      (node (ref "C24") (pin "J2") (pinfunction "0_J2") (pintype "output"))
      (node (ref "D21") (pin "R1") (pinfunction "IN4_R1") (pintype "input"))
      (node (ref "F40") (pin "M2") (pinfunction "P$2_M2") (pintype "bidirectional"))
    )
    (net (code "615") (name "MQ08") (class "Default")
      (node (ref "C16") (pin "M1") (pinfunction "IN2_M1") (pintype "input"))
      (node (ref "C17") (pin "B1") (pinfunction "IN2_B1") (pintype "input"))
      (node (ref "C24") (pin "L1") (pinfunction "1_L1") (pintype "output"))
      (node (ref "EF38") (pin "BH1") (pinfunction "BH1_BH1") (pintype "input"))
    )
    (net (code "616") (name "MQ08_") (class "Default")
      (node (ref "C24") (pin "M1") (pinfunction "0_M1") (pintype "output"))
      (node (ref "D21") (pin "R2") (pinfunction "IN1_R2") (pintype "input"))
      (node (ref "F40") (pin "N2") (pinfunction "P$2_N2") (pintype "bidirectional"))
    )
    (net (code "617") (name "MQ09") (class "Default")
      (node (ref "C16") (pin "R2") (pinfunction "IN2_R2") (pintype "input"))
      (node (ref "C17") (pin "J1") (pinfunction "IN2_J1") (pintype "input"))
      (node (ref "C24") (pin "P2") (pinfunction "1_P2") (pintype "output"))
      (node (ref "EF38") (pin "BN2") (pinfunction "BN2_BN2") (pintype "input"))
    )
    (net (code "618") (name "MQ09_") (class "Default")
      (node (ref "C24") (pin "R2") (pinfunction "0_R2") (pintype "output"))
      (node (ref "D21") (pin "S2") (pinfunction "IN2_S2") (pintype "input"))
      (node (ref "F40") (pin "L2") (pinfunction "P$2_L2") (pintype "bidirectional"))
    )
    (net (code "619") (name "MQ10") (class "Default")
      (node (ref "C17") (pin "E2") (pinfunction "IN2_E2") (pintype "input"))
      (node (ref "C17") (pin "M2") (pinfunction "IN2_M2") (pintype "input"))
      (node (ref "C24") (pin "S1") (pinfunction "1_S1") (pintype "output"))
      (node (ref "D13") (pin "D2") (pinfunction "IN1_D2") (pintype "input"))
      (node (ref "D23") (pin "V1") (pinfunction "IN2A_V1") (pintype "input"))
      (node (ref "EF39") (pin "BH1") (pinfunction "BH1_BH1") (pintype "input"))
    )
    (net (code "620") (name "MQ10_") (class "Default")
      (node (ref "C24") (pin "U1") (pinfunction "0_U1") (pintype "output"))
      (node (ref "D12") (pin "E2") (pinfunction "IN2_E2") (pintype "input"))
      (node (ref "D21") (pin "T2") (pinfunction "IN3_T2") (pintype "input"))
      (node (ref "F40") (pin "F1") (pinfunction "P$2_F1") (pintype "bidirectional"))
    )
    (net (code "621") (name "MQ11") (class "Default")
      (node (ref "C17") (pin "M1") (pinfunction "IN2_M1") (pintype "input"))
      (node (ref "C24") (pin "V2") (pinfunction "1_V2") (pintype "output"))
      (node (ref "D20") (pin "K2") (pinfunction "IN1_K2") (pintype "input"))
      (node (ref "D23") (pin "J2") (pinfunction "IN2A_J2") (pintype "input"))
      (node (ref "D23") (pin "U1") (pinfunction "IN1B_U1") (pintype "input"))
      (node (ref "EF39") (pin "BN2") (pinfunction "BN2_BN2") (pintype "input"))
    )
    (net (code "622") (name "MQ11_") (class "Default")
      (node (ref "C24") (pin "V1") (pinfunction "0_V1") (pintype "output"))
      (node (ref "D13") (pin "U2") (pinfunction "IN2_U2") (pintype "input"))
      (node (ref "D15") (pin "P2") (pinfunction "IN1_P2") (pintype "input"))
      (node (ref "D21") (pin "U2") (pinfunction "IN4_U2") (pintype "input"))
      (node (ref "D23") (pin "M2") (pinfunction "IN3B_M2") (pintype "input"))
      (node (ref "D23") (pin "U2") (pinfunction "IN2B_U2") (pintype "input"))
      (node (ref "F40") (pin "H1") (pinfunction "P$2_H1") (pintype "bidirectional"))
    )
    (net (code "623") (name "MQ_ENABLE") (class "Default")
      (node (ref "D22") (pin "L1") (pinfunction "OUT_L1") (pintype "open_collector"))
      (node (ref "EF34") (pin "BF1") (pinfunction "BF1_BF1") (pintype "input"))
      (node (ref "EF35") (pin "BF1") (pinfunction "BF1_BF1") (pintype "input"))
      (node (ref "EF36") (pin "BF1") (pinfunction "BF1_BF1") (pintype "input"))
      (node (ref "EF37") (pin "BF1") (pinfunction "BF1_BF1") (pintype "input"))
      (node (ref "EF38") (pin "BF1") (pinfunction "BF1_BF1") (pintype "input"))
      (node (ref "EF39") (pin "BF1") (pinfunction "BF1_BF1") (pintype "input"))
    )
    (net (code "624") (name "MQ_LOAD") (class "Default")
      (node (ref "C23") (pin "B1") (pinfunction "C_B1") (pintype "input"))
      (node (ref "C23") (pin "D2") (pinfunction "C_D2") (pintype "input"))
      (node (ref "C23") (pin "H1") (pinfunction "C_H1") (pintype "input"))
      (node (ref "C23") (pin "L2") (pinfunction "C_L2") (pintype "input"))
      (node (ref "C23") (pin "N1") (pinfunction "C_N1") (pintype "input"))
      (node (ref "C23") (pin "S2") (pinfunction "C_S2") (pintype "input"))
      (node (ref "C24") (pin "B1") (pinfunction "C_B1") (pintype "input"))
      (node (ref "C24") (pin "D2") (pinfunction "C_D2") (pintype "input"))
      (node (ref "C24") (pin "H1") (pinfunction "C_H1") (pintype "input"))
      (node (ref "C24") (pin "L2") (pinfunction "C_L2") (pintype "input"))
      (node (ref "C24") (pin "N1") (pinfunction "C_N1") (pintype "input"))
      (node (ref "C24") (pin "S2") (pinfunction "C_S2") (pintype "input"))
      (node (ref "D22") (pin "S1") (pinfunction "OUT_S1") (pintype "open_collector"))
    )
    (net (code "625") (name "MQ_LOW_AC0") (class "Default")
      (node (ref "D15") (pin "F2") (pinfunction "OUT_F2") (pintype "output"))
      (node (ref "D19") (pin "L1") (pinfunction "IN2_L1") (pintype "input"))
      (node (ref "D20") (pin "A1") (pinfunction "IN1_A1") (pintype "input"))
    )
    (net (code "626") (name "MUY") (class "Default")
      (node (ref "D15") (pin "R2") (pinfunction "IN2_R2") (pintype "input"))
      (node (ref "D16") (pin "S1") (pinfunction "OUT_S1") (pintype "output"))
      (node (ref "D23") (pin "A1") (pinfunction "IN1A_A1") (pintype "input"))
    )
    (net (code "627") (name "MUY_") (class "Default")
      (node (ref "D16") (pin "P1") (pinfunction "IN1_P1") (pintype "input"))
      (node (ref "D19") (pin "U1") (pinfunction "OUT_U1") (pintype "output"))
    )
    (net (code "628") (name "MUY_DVI_") (class "Default")
      (node (ref "D15") (pin "K1") (pinfunction "OUT_K1") (pintype "output"))
      (node (ref "D21") (pin "D2") (pinfunction "IN1_D2") (pintype "input"))
    )
    (net (code "629") (name "NEG_CLAMP") (class "Default")
      (node (ref "A39") (pin "R2") (pinfunction "P$2_R2") (pintype "passive"))
      (node (ref "C25") (pin "V2") (pinfunction "V2_V2") (pintype "input"))
      (node (ref "C26") (pin "V2") (pinfunction "V2_V2") (pintype "input"))
      (node (ref "C30") (pin "V2") (pinfunction "V2_V2") (pintype "input"))
      (node (ref "C31") (pin "V2") (pinfunction "V2_V2") (pintype "input"))
      (node (ref "C32") (pin "V2") (pinfunction "V2_V2") (pintype "input"))
      (node (ref "C33") (pin "V2") (pinfunction "V2_V2") (pintype "input"))
      (node (ref "C37") (pin "V2") (pinfunction "V2_V2") (pintype "input"))
      (node (ref "C38") (pin "V2") (pinfunction "V2_V2") (pintype "input"))
      (node (ref "C39") (pin "V2") (pinfunction "V2_V2") (pintype "input"))
      (node (ref "D25") (pin "V2") (pinfunction "V2_V2") (pintype "input"))
      (node (ref "D26") (pin "V2") (pinfunction "V2_V2") (pintype "input"))
      (node (ref "D30") (pin "V2") (pinfunction "V2_V2") (pintype "input"))
      (node (ref "D31") (pin "V2") (pinfunction "V2_V2") (pintype "input"))
      (node (ref "D32") (pin "V2") (pinfunction "V2_V2") (pintype "input"))
      (node (ref "D33") (pin "V2") (pinfunction "V2_V2") (pintype "input"))
      (node (ref "D37") (pin "V2") (pinfunction "V2_V2") (pintype "input"))
      (node (ref "D38") (pin "V2") (pinfunction "V2_V2") (pintype "input"))
      (node (ref "D39") (pin "V2") (pinfunction "V2_V2") (pintype "input"))
    )
    (net (code "630") (name "NMI") (class "Default")
      (node (ref "D14") (pin "M2") (pinfunction "IN2_M2") (pintype "input"))
      (node (ref "D14") (pin "U2") (pinfunction "IN2_U2") (pintype "input"))
      (node (ref "D16") (pin "V2") (pinfunction "OUT_V2") (pintype "output"))
      (node (ref "D23") (pin "N1") (pinfunction "IN5B_N1") (pintype "input"))
    )
    (net (code "631") (name "NMI_") (class "Default")
      (node (ref "D16") (pin "T2") (pinfunction "IN1_T2") (pintype "input"))
      (node (ref "D20") (pin "V2") (pinfunction "OUT_V2") (pintype "output"))
    )
    (net (code "632") (name "NORM") (class "Default")
      (node (ref "C18") (pin "J2") (pinfunction "IN2_J2") (pintype "input"))
      (node (ref "D17") (pin "H2") (pinfunction "OUT_H2") (pintype "output"))
    )
    (net (code "633") (name "NORM_") (class "Default")
      (node (ref "C18") (pin "K2") (pinfunction "OUT_K2") (pintype "output"))
      (node (ref "D14") (pin "L2") (pinfunction "IN1_L2") (pintype "input"))
    )
    (net (code "634") (name "NO_SHIFT") (class "Default")
      (node (ref "E31") (pin "S1") (pinfunction "OUT_S1") (pintype "open_collector"))
      (node (ref "EF34") (pin "AE1") (pinfunction "AE1_AE1") (pintype "input"))
      (node (ref "EF35") (pin "AE1") (pinfunction "AE1_AE1") (pintype "input"))
      (node (ref "EF36") (pin "AE1") (pinfunction "AE1_AE1") (pintype "input"))
      (node (ref "EF37") (pin "AE1") (pinfunction "AE1_AE1") (pintype "input"))
      (node (ref "EF38") (pin "AE1") (pinfunction "AE1_AE1") (pintype "input"))
      (node (ref "EF39") (pin "AE1") (pinfunction "AE1_AE1") (pintype "input"))
      (node (ref "F33") (pin "J1") (pinfunction "IN3B_J1") (pintype "input"))
    )
    (net (code "635") (name "Net-(A05A-OUT)") (class "Default")
      (node (ref "A05") (pin "C1") (pinfunction "OUT_C1") (pintype "output"))
      (node (ref "A05") (pin "E2") (pinfunction "IN2_E2") (pintype "input"))
    )
    (net (code "636") (name "Net-(A05B-IN2)") (class "Default")
      (node (ref "A05") (pin "E1") (pinfunction "IN2_E1") (pintype "input"))
      (node (ref "B04") (pin "H2") (pinfunction "OUT_H2") (pintype "output"))
    )
    (net (code "637") (name "Net-(A05B-OUT)") (class "Default")
      (node (ref "A05") (pin "D2") (pinfunction "IN1_D2") (pintype "input"))
      (node (ref "A05") (pin "F1") (pinfunction "OUT_F1") (pintype "output"))
    )
    (net (code "638") (name "Net-(A05C-OUT)") (class "Default")
      (node (ref "A05") (pin "F2") (pinfunction "OUT_F2") (pintype "output"))
      (node (ref "A05") (pin "H1") (pinfunction "IN1_H1") (pintype "input"))
    )
    (net (code "639") (name "Net-(A05F-OUT)") (class "Default")
      (node (ref "A05") (pin "K1") (pinfunction "OUT_K1") (pintype "output"))
      (node (ref "A05") (pin "L1") (pinfunction "IN1_L1") (pintype "input"))
    )
    (net (code "640") (name "Net-(A05H-OUT)") (class "Default")
      (node (ref "A05") (pin "N1") (pinfunction "OUT_N1") (pintype "output"))
      (node (ref "A05") (pin "R1") (pinfunction "IN2_R1") (pintype "input"))
      (node (ref "B04") (pin "P1") (pinfunction "IN1_P1") (pintype "input"))
      (node (ref "B04") (pin "R1") (pinfunction "IN2_R1") (pintype "input"))
    )
    (net (code "641") (name "Net-(A05I-OUT)") (class "Default")
      (node (ref "A05") (pin "N2") (pinfunction "OUT_N2") (pintype "output"))
      (node (ref "A05") (pin "P1") (pinfunction "IN1_P1") (pintype "input"))
    )
    (net (code "642") (name "Net-(A05J-OUT)") (class "Default")
      (node (ref "A05") (pin "S1") (pinfunction "OUT_S1") (pintype "output"))
      (node (ref "B05") (pin "M2") (pinfunction "D_M2") (pintype "input"))
    )
    (net (code "643") (name "Net-(A05K-IN1)") (class "Default")
      (node (ref "A05") (pin "P2") (pinfunction "IN1_P2") (pintype "input"))
      (node (ref "A05") (pin "R2") (pinfunction "IN2_R2") (pintype "input"))
      (node (ref "B04") (pin "U1") (pinfunction "OUT_U1") (pintype "output"))
    )
    (net (code "644") (name "Net-(A05N-IN2)") (class "Default")
      (node (ref "A05") (pin "U2") (pinfunction "IN2_U2") (pintype "input"))
      (node (ref "B04") (pin "J1") (pinfunction "OUT_J1") (pintype "output"))
    )
    (net (code "645") (name "Net-(A06C-OUT)") (class "Default")
      (node (ref "A06") (pin "F2") (pinfunction "OUT_F2") (pintype "output"))
      (node (ref "A06") (pin "H1") (pinfunction "IN1_H1") (pintype "input"))
    )
    (net (code "646") (name "Net-(A06F-OUT)") (class "Default")
      (node (ref "A06") (pin "K1") (pinfunction "OUT_K1") (pintype "output"))
      (node (ref "F30") (pin "N1") (pinfunction "IN2_N1") (pintype "input"))
    )
    (net (code "647") (name "Net-(A06H-IN1)") (class "Default")
      (node (ref "A06") (pin "L1") (pinfunction "IN1_L1") (pintype "input"))
      (node (ref "F09") (pin "J2") (pinfunction "OUT_J2") (pintype "output"))
    )
    (net (code "648") (name "Net-(A06I-IN1)") (class "Default")
      (node (ref "A06") (pin "L2") (pinfunction "IN1_L2") (pintype "input"))
      (node (ref "A15") (pin "V2") (pinfunction "OUT_V2") (pintype "output"))
    )
    (net (code "649") (name "Net-(A06J-OUT)") (class "Default")
      (node (ref "A06") (pin "P2") (pinfunction "IN1_P2") (pintype "input"))
      (node (ref "A06") (pin "S1") (pinfunction "OUT_S1") (pintype "output"))
    )
    (net (code "650") (name "Net-(A06K-OUT)") (class "Default")
      (node (ref "A06") (pin "S2") (pinfunction "OUT_S2") (pintype "output"))
      (node (ref "A06") (pin "T2") (pinfunction "IN1_T2") (pintype "input"))
    )
    (net (code "651") (name "Net-(A07C-1B)") (class "Default")
      (node (ref "A07") (pin "A1") (pinfunction "1B_A1") (pintype "input"))
      (node (ref "B08") (pin "K1") (pinfunction "OUT_K1") (pintype "output"))
    )
    (net (code "652") (name "Net-(A07C-2B)") (class "Default")
      (node (ref "A07") (pin "B1") (pinfunction "2B_B1") (pintype "input"))
      (node (ref "B08") (pin "F2") (pinfunction "OUT_F2") (pintype "output"))
    )
    (net (code "653") (name "Net-(A07C-4B)") (class "Default")
      (node (ref "A07") (pin "C1") (pinfunction "4B_C1") (pintype "input"))
      (node (ref "B08") (pin "F1") (pinfunction "OUT_F1") (pintype "output"))
    )
    (net (code "654") (name "Net-(A07C-8B)") (class "Default")
      (node (ref "A07") (pin "D1") (pinfunction "8B_D1") (pintype "input"))
      (node (ref "B08") (pin "C1") (pinfunction "OUT_C1") (pintype "output"))
    )
    (net (code "655") (name "Net-(A07C-EVEN)") (class "Default")
      (node (ref "A07") (pin "L1") (pinfunction "EVEN_L1") (pintype "output"))
      (node (ref "A08") (pin "A1") (pinfunction "1B_A1") (pintype "input"))
    )
    (net (code "656") (name "Net-(A07C-ODD)") (class "Default")
      (node (ref "A07") (pin "K1") (pinfunction "ODD_K1") (pintype "output"))
      (node (ref "A08") (pin "E1") (pinfunction "1A_E1") (pintype "input"))
    )
    (net (code "657") (name "Net-(A07D-1B)") (class "Default")
      (node (ref "A07") (pin "K2") (pinfunction "1B_K2") (pintype "input"))
      (node (ref "B09") (pin "F1") (pinfunction "OUT_F1") (pintype "output"))
    )
    (net (code "658") (name "Net-(A07D-2B)") (class "Default")
      (node (ref "A07") (pin "L2") (pinfunction "2B_L2") (pintype "input"))
      (node (ref "B09") (pin "C1") (pinfunction "OUT_C1") (pintype "output"))
    )
    (net (code "659") (name "Net-(A07D-4B)") (class "Default")
      (node (ref "A07") (pin "M2") (pinfunction "4B_M2") (pintype "input"))
      (node (ref "B08") (pin "V2") (pinfunction "OUT_V2") (pintype "output"))
    )
    (net (code "660") (name "Net-(A07D-8B)") (class "Default")
      (node (ref "A07") (pin "N2") (pinfunction "8B_N2") (pintype "input"))
      (node (ref "B08") (pin "S2") (pinfunction "OUT_S2") (pintype "output"))
    )
    (net (code "661") (name "Net-(A07D-EVEN)") (class "Default")
      (node (ref "A07") (pin "V2") (pinfunction "EVEN_V2") (pintype "output"))
      (node (ref "A08") (pin "C1") (pinfunction "4B_C1") (pintype "input"))
    )
    (net (code "662") (name "Net-(A07D-ODD)") (class "Default")
      (node (ref "A07") (pin "U2") (pinfunction "ODD_U2") (pintype "output"))
      (node (ref "A08") (pin "H1") (pinfunction "4A_H1") (pintype "input"))
    )
    (net (code "663") (name "Net-(A08C-2A)") (class "Default")
      (node (ref "A08") (pin "F1") (pinfunction "2A_F1") (pintype "input"))
      (node (ref "A08") (pin "U2") (pinfunction "ODD_U2") (pintype "output"))
    )
    (net (code "664") (name "Net-(A08C-2B)") (class "Default")
      (node (ref "A08") (pin "B1") (pinfunction "2B_B1") (pintype "input"))
      (node (ref "A08") (pin "V2") (pinfunction "EVEN_V2") (pintype "output"))
    )
    (net (code "665") (name "Net-(A08C-8B)") (class "Default")
      (node (ref "A08") (pin "D1") (pinfunction "8B_D1") (pintype "input"))
      (node (ref "B09") (pin "F2") (pinfunction "OUT_F2") (pintype "output"))
    )
    (net (code "666") (name "Net-(A08D-1B)") (class "Default")
      (node (ref "A08") (pin "K2") (pinfunction "1B_K2") (pintype "input"))
      (node (ref "B08") (pin "S1") (pinfunction "OUT_S1") (pintype "output"))
    )
    (net (code "667") (name "Net-(A08D-2B)") (class "Default")
      (node (ref "A08") (pin "L2") (pinfunction "2B_L2") (pintype "input"))
      (node (ref "B08") (pin "N2") (pinfunction "OUT_N2") (pintype "output"))
    )
    (net (code "668") (name "Net-(A08D-4B)") (class "Default")
      (node (ref "A08") (pin "M2") (pinfunction "4B_M2") (pintype "input"))
      (node (ref "B08") (pin "N1") (pinfunction "OUT_N1") (pintype "output"))
    )
    (net (code "669") (name "Net-(A08D-8B)") (class "Default")
      (node (ref "A08") (pin "N2") (pinfunction "8B_N2") (pintype "input"))
      (node (ref "B08") (pin "K2") (pinfunction "OUT_K2") (pintype "output"))
    )
    (net (code "670") (name "Net-(A09C-EVEN)") (class "Default")
      (node (ref "A09") (pin "L1") (pinfunction "EVEN_L1") (pintype "output"))
      (node (ref "A10") (pin "A1") (pinfunction "1B_A1") (pintype "input"))
    )
    (net (code "671") (name "Net-(A09C-ODD)") (class "Default")
      (node (ref "A09") (pin "K1") (pinfunction "ODD_K1") (pintype "output"))
      (node (ref "A10") (pin "E1") (pinfunction "1A_E1") (pintype "input"))
    )
    (net (code "672") (name "Net-(A09D-EVEN)") (class "Default")
      (node (ref "A09") (pin "V2") (pinfunction "EVEN_V2") (pintype "output"))
      (node (ref "A10") (pin "C1") (pinfunction "4B_C1") (pintype "input"))
    )
    (net (code "673") (name "Net-(A09D-ODD)") (class "Default")
      (node (ref "A09") (pin "U2") (pinfunction "ODD_U2") (pintype "output"))
      (node (ref "A10") (pin "H1") (pinfunction "4A_H1") (pintype "input"))
    )
    (net (code "674") (name "Net-(A10C-2A)") (class "Default")
      (node (ref "A10") (pin "F1") (pinfunction "2A_F1") (pintype "input"))
      (node (ref "A10") (pin "U2") (pinfunction "ODD_U2") (pintype "output"))
    )
    (net (code "675") (name "Net-(A10C-2B)") (class "Default")
      (node (ref "A10") (pin "B1") (pinfunction "2B_B1") (pintype "input"))
      (node (ref "A10") (pin "V2") (pinfunction "EVEN_V2") (pintype "output"))
    )
    (net (code "676") (name "Net-(A11A-OUT)") (class "Default")
      (node (ref "A11") (pin "C1") (pinfunction "OUT_C1") (pintype "output"))
      (node (ref "A13") (pin "J1") (pinfunction "IN2_J1") (pintype "input"))
    )
    (net (code "677") (name "Net-(A11B-IN1)") (class "Default")
      (node (ref "A11") (pin "D1") (pinfunction "IN1_D1") (pintype "input"))
      (node (ref "A11") (pin "H2") (pinfunction "IN1_H2") (pintype "input"))
      (node (ref "A11") (pin "P1") (pinfunction "IN1_P1") (pintype "input"))
      (node (ref "A14") (pin "N1") (pinfunction "OUT_N1") (pintype "output"))
    )
    (net (code "678") (name "Net-(A11B-OUT)") (class "Default")
      (node (ref "A11") (pin "F1") (pinfunction "OUT_F1") (pintype "output"))
      (node (ref "A20") (pin "D2") (pinfunction "IN1_D2") (pintype "input"))
    )
    (net (code "679") (name "Net-(A11C-OUT)") (class "Default")
      (node (ref "A11") (pin "F2") (pinfunction "OUT_F2") (pintype "output"))
      (node (ref "A20") (pin "E2") (pinfunction "IN2_E2") (pintype "input"))
    )
    (net (code "680") (name "Net-(A11F-IN1)") (class "Default")
      (node (ref "A11") (pin "H1") (pinfunction "IN1_H1") (pintype "input"))
      (node (ref "A11") (pin "L2") (pinfunction "IN1_L2") (pintype "input"))
      (node (ref "A11") (pin "T2") (pinfunction "IN1_T2") (pintype "input"))
      (node (ref "A14") (pin "S1") (pinfunction "OUT_S1") (pintype "output"))
    )
    (net (code "681") (name "Net-(A11F-OUT)") (class "Default")
      (node (ref "A11") (pin "K1") (pinfunction "OUT_K1") (pintype "output"))
      (node (ref "A20") (pin "F2") (pinfunction "IN3_F2") (pintype "input"))
    )
    (net (code "682") (name "Net-(A11G-OUT)") (class "Default")
      (node (ref "A11") (pin "K2") (pinfunction "OUT_K2") (pintype "output"))
      (node (ref "A20") (pin "E1") (pinfunction "IN1_E1") (pintype "input"))
    )
    (net (code "683") (name "Net-(A11H-OUT)") (class "Default")
      (node (ref "A11") (pin "N1") (pinfunction "OUT_N1") (pintype "output"))
      (node (ref "A20") (pin "F1") (pinfunction "IN2_F1") (pintype "input"))
    )
    (net (code "684") (name "Net-(A11I-OUT)") (class "Default")
      (node (ref "A11") (pin "N2") (pinfunction "OUT_N2") (pintype "output"))
      (node (ref "A20") (pin "H1") (pinfunction "IN3_H1") (pintype "input"))
    )
    (net (code "685") (name "Net-(A11J-OUT)") (class "Default")
      (node (ref "A11") (pin "S1") (pinfunction "OUT_S1") (pintype "output"))
      (node (ref "A20") (pin "J2") (pinfunction "IN1_J2") (pintype "input"))
    )
    (net (code "686") (name "Net-(A11K-OUT)") (class "Default")
      (node (ref "A11") (pin "S2") (pinfunction "OUT_S2") (pintype "output"))
      (node (ref "A20") (pin "K2") (pinfunction "IN2_K2") (pintype "input"))
    )
    (net (code "687") (name "Net-(A11N-OUT)") (class "Default")
      (node (ref "A11") (pin "V2") (pinfunction "OUT_V2") (pintype "output"))
      (node (ref "A20") (pin "L2") (pinfunction "IN3_L2") (pintype "input"))
    )
    (net (code "688") (name "Net-(A12A-OUT)") (class "Default")
      (node (ref "A12") (pin "C1") (pinfunction "OUT_C1") (pintype "output"))
      (node (ref "F11") (pin "E2") (pinfunction "IN2_E2") (pintype "input"))
    )
    (net (code "689") (name "Net-(A12B-OUT)") (class "Default")
      (node (ref "A12") (pin "F1") (pinfunction "OUT_F1") (pintype "output"))
      (node (ref "B20") (pin "N2") (pinfunction "IN1_N2") (pintype "input"))
    )
    (net (code "690") (name "Net-(A12C-IN1)") (class "Default")
      (node (ref "A12") (pin "D2") (pinfunction "IN1_D2") (pintype "input"))
      (node (ref "A12") (pin "L1") (pinfunction "IN1_L1") (pintype "input"))
      (node (ref "A12") (pin "P2") (pinfunction "IN1_P2") (pintype "input"))
      (node (ref "A13") (pin "K1") (pinfunction "OUT_K1") (pintype "output"))
    )
    (net (code "691") (name "Net-(A12C-OUT)") (class "Default")
      (node (ref "A12") (pin "F2") (pinfunction "OUT_F2") (pintype "output"))
      (node (ref "B20") (pin "P2") (pinfunction "IN2_P2") (pintype "input"))
    )
    (net (code "692") (name "Net-(A12F-OUT)") (class "Default")
      (node (ref "A12") (pin "K1") (pinfunction "OUT_K1") (pintype "output"))
      (node (ref "B20") (pin "R2") (pinfunction "IN3_R2") (pintype "input"))
    )
    (net (code "693") (name "Net-(A12G-OUT)") (class "Default")
      (node (ref "A12") (pin "K2") (pinfunction "OUT_K2") (pintype "output"))
      (node (ref "B20") (pin "P1") (pinfunction "IN1_P1") (pintype "input"))
    )
    (net (code "694") (name "Net-(A12H-OUT)") (class "Default")
      (node (ref "A12") (pin "N1") (pinfunction "OUT_N1") (pintype "output"))
      (node (ref "B20") (pin "R1") (pinfunction "IN2_R1") (pintype "input"))
    )
    (net (code "695") (name "Net-(A12I-OUT)") (class "Default")
      (node (ref "A12") (pin "N2") (pinfunction "OUT_N2") (pintype "output"))
      (node (ref "B20") (pin "S1") (pinfunction "IN3_S1") (pintype "input"))
    )
    (net (code "696") (name "Net-(A12J-OUT)") (class "Default")
      (node (ref "A12") (pin "S1") (pinfunction "OUT_S1") (pintype "output"))
      (node (ref "B20") (pin "T2") (pinfunction "IN1_T2") (pintype "input"))
    )
    (net (code "697") (name "Net-(A12K-OUT)") (class "Default")
      (node (ref "A12") (pin "S2") (pinfunction "OUT_S2") (pintype "output"))
      (node (ref "B20") (pin "U2") (pinfunction "IN2_U2") (pintype "input"))
    )
    (net (code "698") (name "Net-(A12N-OUT)") (class "Default")
      (node (ref "A12") (pin "V2") (pinfunction "OUT_V2") (pintype "output"))
      (node (ref "B20") (pin "V2") (pinfunction "IN3_V2") (pintype "input"))
    )
    (net (code "699") (name "Net-(A13A-OUT)") (class "Default")
      (node (ref "A13") (pin "C1") (pinfunction "OUT_C1") (pintype "output"))
      (node (ref "A17") (pin "T2") (pinfunction "IN1_T2") (pintype "input"))
    )
    (net (code "700") (name "Net-(A13B-IN1)") (class "Default")
      (node (ref "A13") (pin "D1") (pinfunction "IN1_D1") (pintype "input"))
      (node (ref "A13") (pin "F2") (pinfunction "OUT_F2") (pintype "output"))
    )
    (net (code "701") (name "Net-(A13H-IN1)") (class "Default")
      (node (ref "A13") (pin "L1") (pinfunction "IN1_L1") (pintype "input"))
      (node (ref "A20") (pin "H2") (pinfunction "OUT_H2") (pintype "output"))
    )
    (net (code "702") (name "Net-(A13J-IN1)") (class "Default")
      (node (ref "A13") (pin "P1") (pinfunction "IN1_P1") (pintype "input"))
      (node (ref "A20") (pin "J1") (pinfunction "OUT_J1") (pintype "output"))
    )
    (net (code "703") (name "Net-(A13N-IN1)") (class "Default")
      (node (ref "A13") (pin "T2") (pinfunction "IN1_T2") (pintype "input"))
      (node (ref "A20") (pin "M2") (pinfunction "OUT_M2") (pintype "output"))
    )
    (net (code "704") (name "Net-(A14A-IN1)") (class "Default")
      (node (ref "A14") (pin "A1") (pinfunction "IN1_A1") (pintype "input"))
      (node (ref "B16") (pin "P2") (pinfunction "OUT_P2") (pintype "open_collector"))
    )
    (net (code "705") (name "Net-(A14A-OUT)") (class "Default")
      (node (ref "A14") (pin "C1") (pinfunction "OUT_C1") (pintype "output"))
      (node (ref "A14") (pin "D1") (pinfunction "IN1_D1") (pintype "input"))
    )
    (net (code "706") (name "Net-(A14C-OUT)") (class "Default")
      (node (ref "A14") (pin "F2") (pinfunction "OUT_F2") (pintype "output"))
      (node (ref "A14") (pin "J2") (pinfunction "IN2_J2") (pintype "input"))
    )
    (net (code "707") (name "Net-(A14H-IN2)") (class "Default")
      (node (ref "A14") (pin "M1") (pinfunction "IN2_M1") (pintype "input"))
      (node (ref "A20") (pin "N1") (pinfunction "OUT_N1") (pintype "output"))
      (node (ref "A20") (pin "T2") (pinfunction "IN1_T2") (pintype "input"))
    )
    (net (code "708") (name "Net-(A14I-IN2)") (class "Default")
      (node (ref "A14") (pin "M2") (pinfunction "IN2_M2") (pintype "input"))
      (node (ref "A20") (pin "S2") (pinfunction "OUT_S2") (pintype "output"))
      (node (ref "A20") (pin "U2") (pinfunction "IN2_U2") (pintype "input"))
    )
    (net (code "709") (name "Net-(A14J-IN2)") (class "Default")
      (node (ref "A14") (pin "R1") (pinfunction "IN2_R1") (pintype "input"))
      (node (ref "A20") (pin "U1") (pinfunction "OUT_U1") (pintype "output"))
      (node (ref "A20") (pin "V2") (pinfunction "IN3_V2") (pintype "input"))
    )
    (net (code "710") (name "Net-(A14K-IN2)") (class "Default")
      (node (ref "A14") (pin "R2") (pinfunction "IN2_R2") (pintype "input"))
      (node (ref "A20") (pin "V1") (pinfunction "OUT_V1") (pintype "output"))
      (node (ref "C12") (pin "D2") (pinfunction "IN1_D2") (pintype "input"))
    )
    (net (code "711") (name "Net-(A15A-OUT)") (class "Default")
      (node (ref "A15") (pin "C1") (pinfunction "OUT_C1") (pintype "output"))
      (node (ref "A15") (pin "D1") (pinfunction "IN1_D1") (pintype "input"))
    )
    (net (code "712") (name "Net-(A15F-IN2)") (class "Default")
      (node (ref "A15") (pin "J1") (pinfunction "IN2_J1") (pintype "input"))
      (node (ref "A19") (pin "V2") (pinfunction "OUT_V2") (pintype "output"))
    )
    (net (code "713") (name "Net-(A15G-IN2)") (class "Default")
      (node (ref "A15") (pin "J2") (pinfunction "IN2_J2") (pintype "input"))
      (node (ref "A15") (pin "N1") (pinfunction "OUT_N1") (pintype "output"))
    )
    (net (code "714") (name "Net-(A15G-OUT)") (class "Default")
      (node (ref "A15") (pin "K2") (pinfunction "OUT_K2") (pintype "output"))
      (node (ref "A18") (pin "B1") (pinfunction "IN2_B1") (pintype "input"))
    )
    (net (code "715") (name "Net-(A15J-IN2)") (class "Default")
      (node (ref "A15") (pin "R1") (pinfunction "IN2_R1") (pintype "input"))
      (node (ref "A15") (pin "S2") (pinfunction "OUT_S2") (pintype "output"))
    )
    (net (code "716") (name "Net-(A16A-OUT)") (class "Default")
      (node (ref "A16") (pin "C1") (pinfunction "OUT_C1") (pintype "output"))
      (node (ref "B16") (pin "A1") (pinfunction "IN1_A1") (pintype "input"))
    )
    (net (code "717") (name "Net-(A16B-OUT)") (class "Default")
      (node (ref "A16") (pin "F1") (pinfunction "OUT_F1") (pintype "output"))
      (node (ref "B16") (pin "B1") (pinfunction "IN2_B1") (pintype "input"))
    )
    (net (code "718") (name "Net-(A16C-OUT)") (class "Default")
      (node (ref "A16") (pin "F2") (pinfunction "OUT_F2") (pintype "output"))
      (node (ref "B16") (pin "C1") (pinfunction "IN3_C1") (pintype "input"))
    )
    (net (code "719") (name "Net-(A16F-OUT)") (class "Default")
      (node (ref "A16") (pin "K1") (pinfunction "OUT_K1") (pintype "output"))
      (node (ref "B16") (pin "D2") (pinfunction "IN1_D2") (pintype "input"))
    )
    (net (code "720") (name "Net-(A16G-OUT)") (class "Default")
      (node (ref "A16") (pin "K2") (pinfunction "OUT_K2") (pintype "output"))
      (node (ref "B16") (pin "E2") (pinfunction "IN2_E2") (pintype "input"))
    )
    (net (code "721") (name "Net-(A16H-OUT)") (class "Default")
      (node (ref "A16") (pin "N1") (pinfunction "OUT_N1") (pintype "output"))
      (node (ref "B16") (pin "F2") (pinfunction "IN3_F2") (pintype "input"))
    )
    (net (code "722") (name "Net-(A16I-OUT)") (class "Default")
      (node (ref "A16") (pin "N2") (pinfunction "OUT_N2") (pintype "output"))
      (node (ref "B16") (pin "F1") (pinfunction "IN1_F1") (pintype "input"))
    )
    (net (code "723") (name "Net-(A16J-OUT)") (class "Default")
      (node (ref "A16") (pin "S1") (pinfunction "OUT_S1") (pintype "output"))
      (node (ref "B16") (pin "H1") (pinfunction "IN2_H1") (pintype "input"))
    )
    (net (code "724") (name "Net-(A16K-OUT)") (class "Default")
      (node (ref "A16") (pin "S2") (pinfunction "OUT_S2") (pintype "output"))
      (node (ref "B16") (pin "J1") (pinfunction "IN3_J1") (pintype "input"))
    )
    (net (code "725") (name "Net-(A16N-OUT)") (class "Default")
      (node (ref "A16") (pin "V2") (pinfunction "OUT_V2") (pintype "output"))
      (node (ref "A20") (pin "A1") (pinfunction "IN1_A1") (pintype "input"))
    )
    (net (code "726") (name "Net-(A17A-IN2)") (class "Default")
      (node (ref "A17") (pin "B1") (pinfunction "IN2_B1") (pintype "input"))
      (node (ref "A20") (pin "D1") (pinfunction "OUT_D1") (pintype "output"))
    )
    (net (code "727") (name "Net-(A17B-OUT)") (class "Default")
      (node (ref "A17") (pin "F1") (pinfunction "OUT_F1") (pintype "output"))
      (node (ref "A20") (pin "C1") (pinfunction "IN3_C1") (pintype "input"))
    )
    (net (code "728") (name "Net-(A17C-IN1)") (class "Default")
      (node (ref "A17") (pin "D2") (pinfunction "IN1_D2") (pintype "input"))
      (node (ref "A18") (pin "F1") (pinfunction "OUT_F1") (pintype "output"))
      (node (ref "B20") (pin "E1") (pinfunction "IN1_E1") (pintype "input"))
    )
    (net (code "729") (name "Net-(A17C-IN2)") (class "Default")
      (node (ref "A17") (pin "E2") (pinfunction "IN2_E2") (pintype "input"))
      (node (ref "A17") (pin "K1") (pinfunction "OUT_K1") (pintype "output"))
    )
    (net (code "730") (name "Net-(A17C-OUT)") (class "Default")
      (node (ref "A17") (pin "F2") (pinfunction "OUT_F2") (pintype "output"))
      (node (ref "B17") (pin "C1") (pinfunction "D_C1") (pintype "input"))
    )
    (net (code "731") (name "Net-(A17G-IN1)") (class "Default")
      (node (ref "A17") (pin "H2") (pinfunction "IN1_H2") (pintype "input"))
      (node (ref "A18") (pin "K2") (pinfunction "OUT_K2") (pintype "output"))
      (node (ref "B20") (pin "J2") (pinfunction "IN1_J2") (pintype "input"))
    )
    (net (code "732") (name "Net-(A17G-IN2)") (class "Default")
      (node (ref "A17") (pin "J2") (pinfunction "IN2_J2") (pintype "input"))
      (node (ref "A17") (pin "N1") (pinfunction "OUT_N1") (pintype "output"))
    )
    (net (code "733") (name "Net-(A17G-OUT)") (class "Default")
      (node (ref "A17") (pin "K2") (pinfunction "OUT_K2") (pintype "output"))
      (node (ref "B17") (pin "E2") (pinfunction "D_E2") (pintype "input"))
    )
    (net (code "734") (name "Net-(A17I-IN1)") (class "Default")
      (node (ref "A17") (pin "L2") (pinfunction "IN1_L2") (pintype "input"))
      (node (ref "A18") (pin "S1") (pinfunction "OUT_S1") (pintype "output"))
      (node (ref "B20") (pin "K1") (pinfunction "IN1_K1") (pintype "input"))
    )
    (net (code "735") (name "Net-(A17I-IN2)") (class "Default")
      (node (ref "A17") (pin "M2") (pinfunction "IN2_M2") (pintype "input"))
      (node (ref "A17") (pin "S1") (pinfunction "OUT_S1") (pintype "output"))
    )
    (net (code "736") (name "Net-(A17I-OUT)") (class "Default")
      (node (ref "A17") (pin "N2") (pinfunction "OUT_N2") (pintype "output"))
      (node (ref "B17") (pin "J1") (pinfunction "D_J1") (pintype "input"))
    )
    (net (code "737") (name "Net-(A17K-IN1)") (class "Default")
      (node (ref "A17") (pin "P2") (pinfunction "IN1_P2") (pintype "input"))
      (node (ref "A17") (pin "V2") (pinfunction "OUT_V2") (pintype "output"))
    )
    (net (code "738") (name "Net-(A17K-OUT)") (class "Default")
      (node (ref "A17") (pin "S2") (pinfunction "OUT_S2") (pintype "output"))
      (node (ref "B18") (pin "B1") (pinfunction "C_B1") (pintype "input"))
      (node (ref "B18") (pin "D2") (pinfunction "C_D2") (pintype "input"))
      (node (ref "B18") (pin "H1") (pinfunction "C_H1") (pintype "input"))
    )
    (net (code "739") (name "Net-(A18C-OUT)") (class "Default")
      (node (ref "A18") (pin "F2") (pinfunction "OUT_F2") (pintype "output"))
      (node (ref "B20") (pin "F1") (pinfunction "IN2_F1") (pintype "input"))
    )
    (net (code "740") (name "Net-(A18F-OUT)") (class "Default")
      (node (ref "A18") (pin "K1") (pinfunction "OUT_K1") (pintype "output"))
      (node (ref "B20") (pin "H1") (pinfunction "IN3_H1") (pintype "input"))
    )
    (net (code "741") (name "Net-(A18H-OUT)") (class "Default")
      (node (ref "A18") (pin "N1") (pinfunction "OUT_N1") (pintype "output"))
      (node (ref "B20") (pin "K2") (pinfunction "IN2_K2") (pintype "input"))
    )
    (net (code "742") (name "Net-(A18I-OUT)") (class "Default")
      (node (ref "A18") (pin "N2") (pinfunction "OUT_N2") (pintype "output"))
      (node (ref "B20") (pin "L2") (pinfunction "IN3_L2") (pintype "input"))
    )
    (net (code "743") (name "Net-(A18K-OUT)") (class "Default")
      (node (ref "A18") (pin "S2") (pinfunction "OUT_S2") (pintype "output"))
      (node (ref "B20") (pin "L1") (pinfunction "IN2_L1") (pintype "input"))
    )
    (net (code "744") (name "Net-(A18N-OUT)") (class "Default")
      (node (ref "A18") (pin "V2") (pinfunction "OUT_V2") (pintype "output"))
      (node (ref "B20") (pin "M1") (pinfunction "IN3_M1") (pintype "input"))
    )
    (net (code "745") (name "Net-(A19A-OUT)") (class "Default")
      (node (ref "A19") (pin "C1") (pinfunction "OUT_C1") (pintype "output"))
      (node (ref "A19") (pin "E1") (pinfunction "IN2_E1") (pintype "input"))
    )
    (net (code "746") (name "Net-(A19B-OUT)") (class "Default")
      (node (ref "A19") (pin "F1") (pinfunction "OUT_F1") (pintype "output"))
      (node (ref "B20") (pin "E2") (pinfunction "IN2_E2") (pintype "input"))
    )
    (net (code "747") (name "Net-(A19F-IN1)") (class "Default")
      (node (ref "A19") (pin "H1") (pinfunction "IN1_H1") (pintype "input"))
      (node (ref "A19") (pin "K2") (pinfunction "OUT_K2") (pintype "output"))
    )
    (net (code "748") (name "Net-(A19F-OUT)") (class "Default")
      (node (ref "A19") (pin "K1") (pinfunction "OUT_K1") (pintype "output"))
      (node (ref "B11") (pin "B1") (pinfunction "C_B1") (pintype "input"))
      (node (ref "B11") (pin "D2") (pinfunction "C_D2") (pintype "input"))
      (node (ref "B11") (pin "H1") (pinfunction "C_H1") (pintype "input"))
    )
    (net (code "749") (name "Net-(A19H-OUT)") (class "Default")
      (node (ref "A19") (pin "M2") (pinfunction "IN2_M2") (pintype "input"))
      (node (ref "A19") (pin "N1") (pinfunction "OUT_N1") (pintype "output"))
    )
    (net (code "750") (name "Net-(A19J-IN1)") (class "Default")
      (node (ref "A19") (pin "P1") (pinfunction "IN1_P1") (pintype "input"))
      (node (ref "A19") (pin "P2") (pinfunction "IN1_P2") (pintype "input"))
      (node (ref "E12") (pin "N2") (pinfunction "OUT_N2") (pintype "output"))
    )
    (net (code "751") (name "Net-(A19K-OUT)") (class "Default")
      (node (ref "A19") (pin "S2") (pinfunction "OUT_S2") (pintype "output"))
      (node (ref "B19") (pin "H1") (pinfunction "C_H1") (pintype "input"))
      (node (ref "B19") (pin "L2") (pinfunction "C_L2") (pintype "input"))
      (node (ref "B19") (pin "N1") (pinfunction "C_N1") (pintype "input"))
      (node (ref "B19") (pin "S2") (pinfunction "C_S2") (pintype "input"))
    )
    (net (code "752") (name "Net-(A21A-IN)") (class "Default")
      (node (ref "A21") (pin "E1") (pinfunction "IN_E1") (pintype "input"))
      (node (ref "A21") (pin "L2") (pinfunction "L2_L2") (pintype "output"))
    )
    (net (code "753") (name "Net-(A21A-OUT)") (class "Default")
      (node (ref "A21") (pin "F1") (pinfunction "OUT_F1") (pintype "output"))
      (node (ref "B30") (pin "M1") (pinfunction "IN1_M1") (pintype "input"))
    )
    (net (code "754") (name "Net-(A21E-IN)") (class "Default")
      (node (ref "A21") (pin "H1") (pinfunction "IN_H1") (pintype "input"))
      (node (ref "A21") (pin "N2") (pinfunction "N2_N2") (pintype "output"))
    )
    (net (code "755") (name "Net-(A21E-OUT)") (class "Default")
      (node (ref "A21") (pin "J1") (pinfunction "OUT_J1") (pintype "output"))
      (node (ref "A22") (pin "H2") (pinfunction "H2_H2") (pintype "input"))
      (node (ref "B23") (pin "P2") (pinfunction "P_P2") (pintype "input"))
      (node (ref "B24") (pin "P2") (pinfunction "P_P2") (pintype "input"))
    )
    (net (code "756") (name "Net-(A22A-IN)") (class "Default")
      (node (ref "A22") (pin "E1") (pinfunction "IN_E1") (pintype "input"))
      (node (ref "A22") (pin "R2") (pinfunction "R2_R2") (pintype "output"))
    )
    (net (code "757") (name "Net-(A22A-OUT)") (class "Default")
      (node (ref "A22") (pin "F1") (pinfunction "OUT_F1") (pintype "output"))
      (node (ref "B22") (pin "H1") (pinfunction "C_H1") (pintype "input"))
      (node (ref "D07") (pin "M1") (pinfunction "IN2_M1") (pintype "input"))
      (node (ref "E09") (pin "E2") (pinfunction "IN2_E2") (pintype "input"))
    )
    (net (code "758") (name "Net-(A23A-IN)") (class "Default")
      (node (ref "A23") (pin "E1") (pinfunction "IN_E1") (pintype "input"))
      (node (ref "A23") (pin "M2") (pinfunction "M2_M2") (pintype "output"))
    )
    (net (code "759") (name "Net-(A23A-OUT)") (class "Default")
      (node (ref "A23") (pin "F1") (pinfunction "OUT_F1") (pintype "output"))
      (node (ref "B21") (pin "D2") (pinfunction "IN1_D2") (pintype "input"))
    )
    (net (code "760") (name "Net-(A23E-IN)") (class "Default")
      (node (ref "A23") (pin "H1") (pinfunction "IN_H1") (pintype "input"))
      (node (ref "A23") (pin "N2") (pinfunction "N2_N2") (pintype "output"))
    )
    (net (code "761") (name "Net-(A23E-OUT)") (class "Default")
      (node (ref "A23") (pin "J1") (pinfunction "OUT_J1") (pintype "output"))
      (node (ref "A24") (pin "H2") (pinfunction "H2_H2") (pintype "input"))
      (node (ref "B21") (pin "J1") (pinfunction "IN2_J1") (pintype "input"))
    )
    (net (code "762") (name "Net-(A24A-IN)") (class "Default")
      (node (ref "A24") (pin "E1") (pinfunction "IN_E1") (pintype "input"))
      (node (ref "A24") (pin "T2") (pinfunction "T2_T2") (pintype "output"))
    )
    (net (code "763") (name "Net-(A25D-P$1)") (class "Default")
      (node (ref "A25") (pin "N2") (pinfunction "P$1_N2") (pintype "passive"))
      (node (ref "A27") (pin "F2") (pinfunction "F2_F2") (pintype "passive"))
    )
    (net (code "764") (name "Net-(A25D-P$2)") (class "Default")
      (node (ref "A25") (pin "P2") (pinfunction "P$2_P2") (pintype "passive"))
      (node (ref "A27") (pin "H2") (pinfunction "H_H2") (pintype "input"))
    )
    (net (code "765") (name "Net-(A25E-P$1)") (class "Default")
      (node (ref "A25") (pin "M2") (pinfunction "P$1_M2") (pintype "passive"))
      (node (ref "A27") (pin "E1") (pinfunction "E1_E1") (pintype "passive"))
    )
    (net (code "766") (name "Net-(A25E-P$2)") (class "Default")
      (node (ref "A25") (pin "R2") (pinfunction "P$2_R2") (pintype "passive"))
      (node (ref "A27") (pin "F1") (pinfunction "H_F1") (pintype "input"))
    )
    (net (code "767") (name "Net-(A25F-P$1)") (class "Default")
      (node (ref "A25") (pin "L2") (pinfunction "P$1_L2") (pintype "passive"))
      (node (ref "A27") (pin "P2") (pinfunction "P2_P2") (pintype "passive"))
    )
    (net (code "768") (name "Net-(A25F-P$2)") (class "Default")
      (node (ref "A25") (pin "S2") (pinfunction "P$2_S2") (pintype "passive"))
      (node (ref "A27") (pin "R2") (pinfunction "H_R2") (pintype "input"))
    )
    (net (code "769") (name "Net-(A25G-P$1)") (class "Default")
      (node (ref "A25") (pin "K2") (pinfunction "P$1_K2") (pintype "passive"))
      (node (ref "A27") (pin "M1") (pinfunction "M1_M1") (pintype "passive"))
    )
    (net (code "770") (name "Net-(A25G-P$2)") (class "Default")
      (node (ref "A25") (pin "T2") (pinfunction "P$2_T2") (pintype "passive"))
      (node (ref "A27") (pin "N1") (pinfunction "H_N1") (pintype "input"))
    )
    (net (code "771") (name "Net-(A26D-P$1)") (class "Default")
      (node (ref "A26") (pin "N2") (pinfunction "P$1_N2") (pintype "passive"))
      (node (ref "B26") (pin "F2") (pinfunction "F2_F2") (pintype "passive"))
    )
    (net (code "772") (name "Net-(A26D-P$2)") (class "Default")
      (node (ref "A26") (pin "P2") (pinfunction "P$2_P2") (pintype "passive"))
      (node (ref "B26") (pin "H2") (pinfunction "H_H2") (pintype "input"))
    )
    (net (code "773") (name "Net-(A26E-P$1)") (class "Default")
      (node (ref "A26") (pin "M2") (pinfunction "P$1_M2") (pintype "passive"))
      (node (ref "B26") (pin "E1") (pinfunction "E1_E1") (pintype "passive"))
    )
    (net (code "774") (name "Net-(A26E-P$2)") (class "Default")
      (node (ref "A26") (pin "R2") (pinfunction "P$2_R2") (pintype "passive"))
      (node (ref "B26") (pin "F1") (pinfunction "H_F1") (pintype "input"))
    )
    (net (code "775") (name "Net-(A26F-P$1)") (class "Default")
      (node (ref "A26") (pin "L2") (pinfunction "P$1_L2") (pintype "passive"))
      (node (ref "B26") (pin "P2") (pinfunction "P2_P2") (pintype "passive"))
    )
    (net (code "776") (name "Net-(A26F-P$2)") (class "Default")
      (node (ref "A26") (pin "S2") (pinfunction "P$2_S2") (pintype "passive"))
      (node (ref "B26") (pin "R2") (pinfunction "H_R2") (pintype "input"))
    )
    (net (code "777") (name "Net-(A26G-P$1)") (class "Default")
      (node (ref "A26") (pin "K2") (pinfunction "P$1_K2") (pintype "passive"))
      (node (ref "B26") (pin "M1") (pinfunction "M1_M1") (pintype "passive"))
    )
    (net (code "778") (name "Net-(A26G-P$2)") (class "Default")
      (node (ref "A26") (pin "T2") (pinfunction "P$2_T2") (pintype "passive"))
      (node (ref "B26") (pin "N1") (pinfunction "H_N1") (pintype "input"))
    )
    (net (code "779") (name "Net-(A27B-J)") (class "Default")
      (node (ref "A27") (pin "H1") (pinfunction "J_H1") (pintype "passive"))
      (node (ref "AB28") (pin "BE2") (pinfunction "P$2_BE2") (pintype "passive"))
    )
    (net (code "780") (name "Net-(A27B-K)") (class "Default")
      (node (ref "A27") (pin "J1") (pinfunction "K_J1") (pintype "passive"))
      (node (ref "AB28") (pin "BF2") (pinfunction "P$2_BF2") (pintype "passive"))
    )
    (net (code "781") (name "Net-(A27D-J)") (class "Default")
      (node (ref "A27") (pin "J2") (pinfunction "J_J2") (pintype "passive"))
      (node (ref "AB28") (pin "BC2") (pinfunction "P$2_BC2") (pintype "passive"))
    )
    (net (code "782") (name "Net-(A27D-K)") (class "Default")
      (node (ref "A27") (pin "K2") (pinfunction "K_K2") (pintype "passive"))
      (node (ref "AB28") (pin "BD2") (pinfunction "P$2_BD2") (pintype "passive"))
    )
    (net (code "783") (name "Net-(A27E-J)") (class "Default")
      (node (ref "A27") (pin "P1") (pinfunction "J_P1") (pintype "passive"))
      (node (ref "AB28") (pin "BK2") (pinfunction "P$2_BK2") (pintype "passive"))
    )
    (net (code "784") (name "Net-(A27E-K)") (class "Default")
      (node (ref "A27") (pin "R1") (pinfunction "K_R1") (pintype "passive"))
      (node (ref "AB28") (pin "BL2") (pinfunction "P$2_BL2") (pintype "passive"))
    )
    (net (code "785") (name "Net-(A27F-J)") (class "Default")
      (node (ref "A27") (pin "S2") (pinfunction "J_S2") (pintype "passive"))
      (node (ref "AB28") (pin "BH2") (pinfunction "P$2_BH2") (pintype "passive"))
    )
    (net (code "786") (name "Net-(A27F-K)") (class "Default")
      (node (ref "A27") (pin "T2") (pinfunction "K_T2") (pintype "passive"))
      (node (ref "AB28") (pin "BJ2") (pinfunction "P$2_BJ2") (pintype "passive"))
    )
    (net (code "787") (name "Net-(A36B-H)") (class "Default")
      (node (ref "A36") (pin "F1") (pinfunction "H_F1") (pintype "input"))
      (node (ref "A38") (pin "R2") (pinfunction "P$2_R2") (pintype "passive"))
    )
    (net (code "788") (name "Net-(A36B-J)") (class "Default")
      (node (ref "A36") (pin "H1") (pinfunction "J_H1") (pintype "passive"))
      (node (ref "AB35") (pin "AE2") (pinfunction "P$2_AE2") (pintype "passive"))
    )
    (net (code "789") (name "Net-(A36B-K)") (class "Default")
      (node (ref "A36") (pin "J1") (pinfunction "K_J1") (pintype "passive"))
      (node (ref "AB35") (pin "AF2") (pinfunction "P$2_AF2") (pintype "passive"))
    )
    (net (code "790") (name "Net-(A36D-H)") (class "Default")
      (node (ref "A36") (pin "H2") (pinfunction "H_H2") (pintype "input"))
      (node (ref "A38") (pin "P2") (pinfunction "P$2_P2") (pintype "passive"))
    )
    (net (code "791") (name "Net-(A36D-J)") (class "Default")
      (node (ref "A36") (pin "J2") (pinfunction "J_J2") (pintype "passive"))
      (node (ref "AB35") (pin "AC2") (pinfunction "P$2_AC2") (pintype "passive"))
    )
    (net (code "792") (name "Net-(A36D-K)") (class "Default")
      (node (ref "A36") (pin "K2") (pinfunction "K_K2") (pintype "passive"))
      (node (ref "AB35") (pin "AD2") (pinfunction "P$2_AD2") (pintype "passive"))
    )
    (net (code "793") (name "Net-(A36E-H)") (class "Default")
      (node (ref "A36") (pin "N1") (pinfunction "H_N1") (pintype "input"))
      (node (ref "A38") (pin "T2") (pinfunction "P$2_T2") (pintype "passive"))
    )
    (net (code "794") (name "Net-(A36E-J)") (class "Default")
      (node (ref "A36") (pin "P1") (pinfunction "J_P1") (pintype "passive"))
      (node (ref "AB35") (pin "AK2") (pinfunction "P$2_AK2") (pintype "passive"))
    )
    (net (code "795") (name "Net-(A36E-K)") (class "Default")
      (node (ref "A36") (pin "R1") (pinfunction "K_R1") (pintype "passive"))
      (node (ref "AB35") (pin "AL2") (pinfunction "P$2_AL2") (pintype "passive"))
    )
    (net (code "796") (name "Net-(A36F-H)") (class "Default")
      (node (ref "A36") (pin "R2") (pinfunction "H_R2") (pintype "input"))
      (node (ref "A38") (pin "S2") (pinfunction "P$2_S2") (pintype "passive"))
    )
    (net (code "797") (name "Net-(A36F-J)") (class "Default")
      (node (ref "A36") (pin "S2") (pinfunction "J_S2") (pintype "passive"))
      (node (ref "AB35") (pin "AH2") (pinfunction "P$2_AH2") (pintype "passive"))
    )
    (net (code "798") (name "Net-(A36F-K)") (class "Default")
      (node (ref "A36") (pin "T2") (pinfunction "K_T2") (pintype "passive"))
      (node (ref "AB35") (pin "AJ2") (pinfunction "P$2_AJ2") (pintype "passive"))
    )
    (net (code "799") (name "Net-(A37D-H)") (class "Default")
      (node (ref "A37") (pin "H2") (pinfunction "H_H2") (pintype "input"))
      (node (ref "A39") (pin "P2") (pinfunction "P$2_P2") (pintype "passive"))
    )
    (net (code "800") (name "Net-(A37D-J)") (class "Default")
      (node (ref "A37") (pin "J2") (pinfunction "J_J2") (pintype "passive"))
      (node (ref "AB35") (pin "AS2") (pinfunction "P$2_AS2") (pintype "passive"))
    )
    (net (code "801") (name "Net-(A37D-K)") (class "Default")
      (node (ref "A37") (pin "K2") (pinfunction "K_K2") (pintype "passive"))
      (node (ref "AB35") (pin "AT2") (pinfunction "P$2_AT2") (pintype "passive"))
    )
    (net (code "802") (name "Net-(A37F-H)") (class "Default")
      (node (ref "A37") (pin "R2") (pinfunction "H_R2") (pintype "input"))
      (node (ref "A39") (pin "S2") (pinfunction "P$2_S2") (pintype "passive"))
    )
    (net (code "803") (name "Net-(A37F-J)") (class "Default")
      (node (ref "A37") (pin "S2") (pinfunction "J_S2") (pintype "passive"))
      (node (ref "AB28") (pin "AS2") (pinfunction "P$2_AS2") (pintype "passive"))
    )
    (net (code "804") (name "Net-(A37F-K)") (class "Default")
      (node (ref "A37") (pin "T2") (pinfunction "K_T2") (pintype "passive"))
      (node (ref "AB28") (pin "AT2") (pinfunction "P$2_AT2") (pintype "passive"))
    )
    (net (code "805") (name "Net-(A38D-P$1)") (class "Default")
      (node (ref "A36") (pin "F2") (pinfunction "F2_F2") (pintype "passive"))
      (node (ref "A38") (pin "N2") (pinfunction "P$1_N2") (pintype "passive"))
    )
    (net (code "806") (name "Net-(A38E-P$1)") (class "Default")
      (node (ref "A36") (pin "E1") (pinfunction "E1_E1") (pintype "passive"))
      (node (ref "A38") (pin "M2") (pinfunction "P$1_M2") (pintype "passive"))
    )
    (net (code "807") (name "Net-(A38F-P$1)") (class "Default")
      (node (ref "A36") (pin "P2") (pinfunction "P2_P2") (pintype "passive"))
      (node (ref "A38") (pin "L2") (pinfunction "P$1_L2") (pintype "passive"))
    )
    (net (code "808") (name "Net-(A38G-P$1)") (class "Default")
      (node (ref "A36") (pin "M1") (pinfunction "M1_M1") (pintype "passive"))
      (node (ref "A38") (pin "K2") (pinfunction "P$1_K2") (pintype "passive"))
    )
    (net (code "809") (name "Net-(A38H-P$1)") (class "Default")
      (node (ref "A38") (pin "F2") (pinfunction "P$1_F2") (pintype "passive"))
      (node (ref "C39") (pin "U2") (pinfunction "U2_U2") (pintype "passive"))
      (node (ref "D39") (pin "U2") (pinfunction "U2_U2") (pintype "passive"))
    )
    (net (code "810") (name "Net-(A39D-P$1)") (class "Default")
      (node (ref "A37") (pin "F2") (pinfunction "F2_F2") (pintype "passive"))
      (node (ref "A39") (pin "N2") (pinfunction "P$1_N2") (pintype "passive"))
    )
    (net (code "811") (name "Net-(A39F-P$1)") (class "Default")
      (node (ref "A37") (pin "P2") (pinfunction "P2_P2") (pintype "passive"))
      (node (ref "A39") (pin "L2") (pinfunction "P$1_L2") (pintype "passive"))
    )
    (net (code "812") (name "Net-(A39H-P$1)") (class "Default")
      (node (ref "A39") (pin "F2") (pinfunction "P$1_F2") (pintype "passive"))
      (node (ref "C39") (pin "L2") (pinfunction "L2_L2") (pintype "passive"))
      (node (ref "D39") (pin "L2") (pinfunction "L2_L2") (pintype "passive"))
    )
    (net (code "813") (name "Net-(AB01-PadAV2)") (class "Default")
      (node (ref "AB01") (pin "AV2") (pinfunction "AV2_AV2") (pintype "input"))
      (node (ref "AB02") (pin "BJ2") (pinfunction "BJ2_BJ2") (pintype "output"))
      (node (ref "AB02") (pin "BK2") (pinfunction "BK2_BK2") (pintype "passive"))
    )
    (net (code "814") (name "Net-(AB28AC-P$2)") (class "Default")
      (node (ref "AB28") (pin "BM2") (pinfunction "P$2_BM2") (pintype "passive"))
      (node (ref "B26") (pin "J2") (pinfunction "J_J2") (pintype "passive"))
    )
    (net (code "815") (name "Net-(AB28AD-P$2)") (class "Default")
      (node (ref "AB28") (pin "BN2") (pinfunction "P$2_BN2") (pintype "passive"))
      (node (ref "B26") (pin "K2") (pinfunction "K_K2") (pintype "passive"))
    )
    (net (code "816") (name "Net-(AB28AE-P$2)") (class "Default")
      (node (ref "AB28") (pin "BP2") (pinfunction "P$2_BP2") (pintype "passive"))
      (node (ref "B26") (pin "H1") (pinfunction "J_H1") (pintype "passive"))
    )
    (net (code "817") (name "Net-(AB28AF-P$2)") (class "Default")
      (node (ref "AB28") (pin "BR2") (pinfunction "P$2_BR2") (pintype "passive"))
      (node (ref "B26") (pin "J1") (pinfunction "K_J1") (pintype "passive"))
    )
    (net (code "818") (name "Net-(AB28C-P$2)") (class "Default")
      (node (ref "AB28") (pin "AC2") (pinfunction "P$2_AC2") (pintype "passive"))
      (node (ref "B26") (pin "S2") (pinfunction "J_S2") (pintype "passive"))
    )
    (net (code "819") (name "Net-(AB28D-P$2)") (class "Default")
      (node (ref "AB28") (pin "AD2") (pinfunction "P$2_AD2") (pintype "passive"))
      (node (ref "B26") (pin "T2") (pinfunction "K_T2") (pintype "passive"))
    )
    (net (code "820") (name "Net-(AB28E-P$2)") (class "Default")
      (node (ref "AB28") (pin "AE2") (pinfunction "P$2_AE2") (pintype "passive"))
      (node (ref "B26") (pin "P1") (pinfunction "J_P1") (pintype "passive"))
    )
    (net (code "821") (name "Net-(AB28F-P$2)") (class "Default")
      (node (ref "AB28") (pin "AF2") (pinfunction "P$2_AF2") (pintype "passive"))
      (node (ref "B26") (pin "R1") (pinfunction "K_R1") (pintype "passive"))
    )
    (net (code "822") (name "Net-(AB28G-P$2)") (class "Default")
      (node (ref "AB28") (pin "AH2") (pinfunction "P$2_AH2") (pintype "passive"))
      (node (ref "B27") (pin "J2") (pinfunction "J_J2") (pintype "passive"))
    )
    (net (code "823") (name "Net-(AB28H-P$2)") (class "Default")
      (node (ref "AB28") (pin "AJ2") (pinfunction "P$2_AJ2") (pintype "passive"))
      (node (ref "B27") (pin "K2") (pinfunction "K_K2") (pintype "passive"))
    )
    (net (code "824") (name "Net-(AB28I-P$2)") (class "Default")
      (node (ref "AB28") (pin "AK2") (pinfunction "P$2_AK2") (pintype "passive"))
      (node (ref "B27") (pin "H1") (pinfunction "J_H1") (pintype "passive"))
    )
    (net (code "825") (name "Net-(AB28J-P$2)") (class "Default")
      (node (ref "AB28") (pin "AL2") (pinfunction "P$2_AL2") (pintype "passive"))
      (node (ref "B27") (pin "J1") (pinfunction "K_J1") (pintype "passive"))
    )
    (net (code "826") (name "Net-(AB28K-P$2)") (class "Default")
      (node (ref "AB28") (pin "AM2") (pinfunction "P$2_AM2") (pintype "passive"))
      (node (ref "B27") (pin "S2") (pinfunction "J_S2") (pintype "passive"))
    )
    (net (code "827") (name "Net-(AB28L-P$2)") (class "Default")
      (node (ref "AB28") (pin "AN2") (pinfunction "P$2_AN2") (pintype "passive"))
      (node (ref "B27") (pin "T2") (pinfunction "K_T2") (pintype "passive"))
    )
    (net (code "828") (name "Net-(AB28M-P$2)") (class "Default")
      (node (ref "AB28") (pin "AP2") (pinfunction "P$2_AP2") (pintype "passive"))
      (node (ref "B27") (pin "P1") (pinfunction "J_P1") (pintype "passive"))
    )
    (net (code "829") (name "Net-(AB28N-P$2)") (class "Default")
      (node (ref "AB28") (pin "AR2") (pinfunction "P$2_AR2") (pintype "passive"))
      (node (ref "B27") (pin "R1") (pinfunction "K_R1") (pintype "passive"))
    )
    (net (code "830") (name "Net-(AB29AA-P$2)") (class "Default")
      (node (ref "AB29") (pin "BK2") (pinfunction "P$2_BK2") (pintype "passive"))
      (node (ref "B32") (pin "N1") (pinfunction "N1_N1") (pintype "input"))
    )
    (net (code "831") (name "Net-(AB29AB-P$2)") (class "Default")
      (node (ref "AB29") (pin "BL2") (pinfunction "P$2_BL2") (pintype "passive"))
      (node (ref "B32") (pin "P1") (pinfunction "P1_P1") (pintype "input"))
    )
    (net (code "832") (name "Net-(AB29AC-P$2)") (class "Default")
      (node (ref "AB29") (pin "BM2") (pinfunction "P$2_BM2") (pintype "passive"))
      (node (ref "B33") (pin "F2") (pinfunction "F2_F2") (pintype "input"))
    )
    (net (code "833") (name "Net-(AB29AD-P$2)") (class "Default")
      (node (ref "AB29") (pin "BN2") (pinfunction "P$2_BN2") (pintype "passive"))
      (node (ref "B33") (pin "H2") (pinfunction "H2_H2") (pintype "input"))
    )
    (net (code "834") (name "Net-(AB29AE-P$2)") (class "Default")
      (node (ref "AB29") (pin "BP2") (pinfunction "P$2_BP2") (pintype "passive"))
      (node (ref "B33") (pin "N1") (pinfunction "N1_N1") (pintype "input"))
    )
    (net (code "835") (name "Net-(AB29AF-P$2)") (class "Default")
      (node (ref "AB29") (pin "BR2") (pinfunction "P$2_BR2") (pintype "passive"))
      (node (ref "B33") (pin "P1") (pinfunction "P1_P1") (pintype "input"))
    )
    (net (code "836") (name "Net-(AB29C-P$2)") (class "Default")
      (node (ref "A31") (pin "F2") (pinfunction "F2_F2") (pintype "input"))
      (node (ref "AB29") (pin "AC2") (pinfunction "P$2_AC2") (pintype "passive"))
    )
    (net (code "837") (name "Net-(AB29D-P$2)") (class "Default")
      (node (ref "A31") (pin "H2") (pinfunction "H2_H2") (pintype "input"))
      (node (ref "AB29") (pin "AD2") (pinfunction "P$2_AD2") (pintype "passive"))
    )
    (net (code "838") (name "Net-(AB29E-P$2)") (class "Default")
      (node (ref "A31") (pin "N1") (pinfunction "N1_N1") (pintype "input"))
      (node (ref "AB29") (pin "AE2") (pinfunction "P$2_AE2") (pintype "passive"))
    )
    (net (code "839") (name "Net-(AB29F-P$2)") (class "Default")
      (node (ref "A31") (pin "P1") (pinfunction "P1_P1") (pintype "input"))
      (node (ref "AB29") (pin "AF2") (pinfunction "P$2_AF2") (pintype "passive"))
    )
    (net (code "840") (name "Net-(AB29G-P$2)") (class "Default")
      (node (ref "A32") (pin "F2") (pinfunction "F2_F2") (pintype "input"))
      (node (ref "AB29") (pin "AH2") (pinfunction "P$2_AH2") (pintype "passive"))
    )
    (net (code "841") (name "Net-(AB29H-P$2)") (class "Default")
      (node (ref "A32") (pin "H2") (pinfunction "H2_H2") (pintype "input"))
      (node (ref "AB29") (pin "AJ2") (pinfunction "P$2_AJ2") (pintype "passive"))
    )
    (net (code "842") (name "Net-(AB29I-P$2)") (class "Default")
      (node (ref "A32") (pin "N1") (pinfunction "N1_N1") (pintype "input"))
      (node (ref "AB29") (pin "AK2") (pinfunction "P$2_AK2") (pintype "passive"))
    )
    (net (code "843") (name "Net-(AB29J-P$2)") (class "Default")
      (node (ref "A32") (pin "P1") (pinfunction "P1_P1") (pintype "input"))
      (node (ref "AB29") (pin "AL2") (pinfunction "P$2_AL2") (pintype "passive"))
    )
    (net (code "844") (name "Net-(AB29K-P$2)") (class "Default")
      (node (ref "A33") (pin "F2") (pinfunction "F2_F2") (pintype "input"))
      (node (ref "AB29") (pin "AM2") (pinfunction "P$2_AM2") (pintype "passive"))
    )
    (net (code "845") (name "Net-(AB29L-P$2)") (class "Default")
      (node (ref "A33") (pin "H2") (pinfunction "H2_H2") (pintype "input"))
      (node (ref "AB29") (pin "AN2") (pinfunction "P$2_AN2") (pintype "passive"))
    )
    (net (code "846") (name "Net-(AB29M-P$2)") (class "Default")
      (node (ref "A33") (pin "N1") (pinfunction "N1_N1") (pintype "input"))
      (node (ref "AB29") (pin "AP2") (pinfunction "P$2_AP2") (pintype "passive"))
    )
    (net (code "847") (name "Net-(AB29N-P$2)") (class "Default")
      (node (ref "A33") (pin "P1") (pinfunction "P1_P1") (pintype "input"))
      (node (ref "AB29") (pin "AR2") (pinfunction "P$2_AR2") (pintype "passive"))
    )
    (net (code "848") (name "Net-(AB29O-P$2)") (class "Default")
      (node (ref "A30") (pin "L1") (pinfunction "L1_L1") (pintype "input"))
      (node (ref "AB29") (pin "AS2") (pinfunction "P$2_AS2") (pintype "passive"))
    )
    (net (code "849") (name "Net-(AB29P-P$2)") (class "Default")
      (node (ref "A30") (pin "M1") (pinfunction "M1_M1") (pintype "input"))
      (node (ref "AB29") (pin "AT2") (pinfunction "P$2_AT2") (pintype "passive"))
    )
    (net (code "850") (name "Net-(AB29U-P$2)") (class "Default")
      (node (ref "AB29") (pin "BC2") (pinfunction "P$2_BC2") (pintype "passive"))
      (node (ref "B31") (pin "F2") (pinfunction "F2_F2") (pintype "input"))
    )
    (net (code "851") (name "Net-(AB29V-P$2)") (class "Default")
      (node (ref "AB29") (pin "BD2") (pinfunction "P$2_BD2") (pintype "passive"))
      (node (ref "B31") (pin "H2") (pinfunction "H2_H2") (pintype "input"))
    )
    (net (code "852") (name "Net-(AB29W-P$2)") (class "Default")
      (node (ref "AB29") (pin "BE2") (pinfunction "P$2_BE2") (pintype "passive"))
      (node (ref "B31") (pin "N1") (pinfunction "N1_N1") (pintype "input"))
    )
    (net (code "853") (name "Net-(AB29X-P$2)") (class "Default")
      (node (ref "AB29") (pin "BF2") (pinfunction "P$2_BF2") (pintype "passive"))
      (node (ref "B31") (pin "P1") (pinfunction "P1_P1") (pintype "input"))
    )
    (net (code "854") (name "Net-(AB29Y-P$2)") (class "Default")
      (node (ref "AB29") (pin "BH2") (pinfunction "P$2_BH2") (pintype "passive"))
      (node (ref "B32") (pin "F2") (pinfunction "F2_F2") (pintype "input"))
    )
    (net (code "855") (name "Net-(AB29Z-P$2)") (class "Default")
      (node (ref "AB29") (pin "BJ2") (pinfunction "P$2_BJ2") (pintype "passive"))
      (node (ref "B32") (pin "H2") (pinfunction "H2_H2") (pintype "input"))
    )
    (net (code "856") (name "Net-(AB34AA-P$2)") (class "Default")
      (node (ref "AB34") (pin "BK2") (pinfunction "P$2_BK2") (pintype "passive"))
      (node (ref "B32") (pin "L1") (pinfunction "L1_L1") (pintype "input"))
    )
    (net (code "857") (name "Net-(AB34AB-P$2)") (class "Default")
      (node (ref "AB34") (pin "BL2") (pinfunction "P$2_BL2") (pintype "passive"))
      (node (ref "B32") (pin "M1") (pinfunction "M1_M1") (pintype "input"))
    )
    (net (code "858") (name "Net-(AB34AC-P$2)") (class "Default")
      (node (ref "AB34") (pin "BM2") (pinfunction "P$2_BM2") (pintype "passive"))
      (node (ref "B33") (pin "D2") (pinfunction "D2_D2") (pintype "input"))
    )
    (net (code "859") (name "Net-(AB34AD-P$2)") (class "Default")
      (node (ref "AB34") (pin "BN2") (pinfunction "P$2_BN2") (pintype "passive"))
      (node (ref "B33") (pin "E2") (pinfunction "E2_E2") (pintype "input"))
    )
    (net (code "860") (name "Net-(AB34AE-P$2)") (class "Default")
      (node (ref "AB34") (pin "BP2") (pinfunction "P$2_BP2") (pintype "passive"))
      (node (ref "B33") (pin "L1") (pinfunction "L1_L1") (pintype "input"))
    )
    (net (code "861") (name "Net-(AB34AF-P$2)") (class "Default")
      (node (ref "AB34") (pin "BR2") (pinfunction "P$2_BR2") (pintype "passive"))
      (node (ref "B33") (pin "M1") (pinfunction "M1_M1") (pintype "input"))
    )
    (net (code "862") (name "Net-(AB34C-P$2)") (class "Default")
      (node (ref "A31") (pin "D2") (pinfunction "D2_D2") (pintype "input"))
      (node (ref "AB34") (pin "AC2") (pinfunction "P$2_AC2") (pintype "passive"))
    )
    (net (code "863") (name "Net-(AB34D-P$2)") (class "Default")
      (node (ref "A31") (pin "E2") (pinfunction "E2_E2") (pintype "input"))
      (node (ref "AB34") (pin "AD2") (pinfunction "P$2_AD2") (pintype "passive"))
    )
    (net (code "864") (name "Net-(AB34E-P$2)") (class "Default")
      (node (ref "A31") (pin "L1") (pinfunction "L1_L1") (pintype "input"))
      (node (ref "AB34") (pin "AE2") (pinfunction "P$2_AE2") (pintype "passive"))
    )
    (net (code "865") (name "Net-(AB34F-P$2)") (class "Default")
      (node (ref "A31") (pin "M1") (pinfunction "M1_M1") (pintype "input"))
      (node (ref "AB34") (pin "AF2") (pinfunction "P$2_AF2") (pintype "passive"))
    )
    (net (code "866") (name "Net-(AB34G-P$2)") (class "Default")
      (node (ref "A32") (pin "D2") (pinfunction "D2_D2") (pintype "input"))
      (node (ref "AB34") (pin "AH2") (pinfunction "P$2_AH2") (pintype "passive"))
    )
    (net (code "867") (name "Net-(AB34H-P$2)") (class "Default")
      (node (ref "A32") (pin "E2") (pinfunction "E2_E2") (pintype "input"))
      (node (ref "AB34") (pin "AJ2") (pinfunction "P$2_AJ2") (pintype "passive"))
    )
    (net (code "868") (name "Net-(AB34I-P$2)") (class "Default")
      (node (ref "A32") (pin "L1") (pinfunction "L1_L1") (pintype "input"))
      (node (ref "AB34") (pin "AK2") (pinfunction "P$2_AK2") (pintype "passive"))
    )
    (net (code "869") (name "Net-(AB34J-P$2)") (class "Default")
      (node (ref "A32") (pin "M1") (pinfunction "M1_M1") (pintype "input"))
      (node (ref "AB34") (pin "AL2") (pinfunction "P$2_AL2") (pintype "passive"))
    )
    (net (code "870") (name "Net-(AB34K-P$2)") (class "Default")
      (node (ref "A33") (pin "D2") (pinfunction "D2_D2") (pintype "input"))
      (node (ref "AB34") (pin "AM2") (pinfunction "P$2_AM2") (pintype "passive"))
    )
    (net (code "871") (name "Net-(AB34L-P$2)") (class "Default")
      (node (ref "A33") (pin "E2") (pinfunction "E2_E2") (pintype "input"))
      (node (ref "AB34") (pin "AN2") (pinfunction "P$2_AN2") (pintype "passive"))
    )
    (net (code "872") (name "Net-(AB34M-P$2)") (class "Default")
      (node (ref "A33") (pin "L1") (pinfunction "L1_L1") (pintype "input"))
      (node (ref "AB34") (pin "AP2") (pinfunction "P$2_AP2") (pintype "passive"))
    )
    (net (code "873") (name "Net-(AB34N-P$2)") (class "Default")
      (node (ref "A33") (pin "M1") (pinfunction "M1_M1") (pintype "input"))
      (node (ref "AB34") (pin "AR2") (pinfunction "P$2_AR2") (pintype "passive"))
    )
    (net (code "874") (name "Net-(AB34O-P$2)") (class "Default")
      (node (ref "A30") (pin "D2") (pinfunction "D2_D2") (pintype "input"))
      (node (ref "AB34") (pin "AS2") (pinfunction "P$2_AS2") (pintype "passive"))
    )
    (net (code "875") (name "Net-(AB34P-P$2)") (class "Default")
      (node (ref "A30") (pin "E2") (pinfunction "E2_E2") (pintype "input"))
      (node (ref "AB34") (pin "AT2") (pinfunction "P$2_AT2") (pintype "passive"))
    )
    (net (code "876") (name "Net-(AB34U-P$2)") (class "Default")
      (node (ref "AB34") (pin "BC2") (pinfunction "P$2_BC2") (pintype "passive"))
      (node (ref "B31") (pin "D2") (pinfunction "D2_D2") (pintype "input"))
    )
    (net (code "877") (name "Net-(AB34V-P$2)") (class "Default")
      (node (ref "AB34") (pin "BD2") (pinfunction "P$2_BD2") (pintype "passive"))
      (node (ref "B31") (pin "E2") (pinfunction "E2_E2") (pintype "input"))
    )
    (net (code "878") (name "Net-(AB34W-P$2)") (class "Default")
      (node (ref "AB34") (pin "BE2") (pinfunction "P$2_BE2") (pintype "passive"))
      (node (ref "B31") (pin "L1") (pinfunction "L1_L1") (pintype "input"))
    )
    (net (code "879") (name "Net-(AB34X-P$2)") (class "Default")
      (node (ref "AB34") (pin "BF2") (pinfunction "P$2_BF2") (pintype "passive"))
      (node (ref "B31") (pin "M1") (pinfunction "M1_M1") (pintype "input"))
    )
    (net (code "880") (name "Net-(AB34Y-P$2)") (class "Default")
      (node (ref "AB34") (pin "BH2") (pinfunction "P$2_BH2") (pintype "passive"))
      (node (ref "B32") (pin "D2") (pinfunction "D2_D2") (pintype "input"))
    )
    (net (code "881") (name "Net-(AB34Z-P$2)") (class "Default")
      (node (ref "AB34") (pin "BJ2") (pinfunction "P$2_BJ2") (pintype "passive"))
      (node (ref "B32") (pin "E2") (pinfunction "E2_E2") (pintype "input"))
    )
    (net (code "882") (name "Net-(AB35AA-P$2)") (class "Default")
      (node (ref "AB35") (pin "BK2") (pinfunction "P$2_BK2") (pintype "passive"))
      (node (ref "B37") (pin "H1") (pinfunction "J_H1") (pintype "passive"))
    )
    (net (code "883") (name "Net-(AB35AB-P$2)") (class "Default")
      (node (ref "AB35") (pin "BL2") (pinfunction "P$2_BL2") (pintype "passive"))
      (node (ref "B37") (pin "J1") (pinfunction "K_J1") (pintype "passive"))
    )
    (net (code "884") (name "Net-(AB35AC-P$2)") (class "Default")
      (node (ref "AB35") (pin "BM2") (pinfunction "P$2_BM2") (pintype "passive"))
      (node (ref "B37") (pin "S2") (pinfunction "J_S2") (pintype "passive"))
    )
    (net (code "885") (name "Net-(AB35AD-P$2)") (class "Default")
      (node (ref "AB35") (pin "BN2") (pinfunction "P$2_BN2") (pintype "passive"))
      (node (ref "B37") (pin "T2") (pinfunction "K_T2") (pintype "passive"))
    )
    (net (code "886") (name "Net-(AB35AE-P$2)") (class "Default")
      (node (ref "AB35") (pin "BP2") (pinfunction "P$2_BP2") (pintype "passive"))
      (node (ref "B37") (pin "P1") (pinfunction "J_P1") (pintype "passive"))
    )
    (net (code "887") (name "Net-(AB35AF-P$2)") (class "Default")
      (node (ref "AB35") (pin "BR2") (pinfunction "P$2_BR2") (pintype "passive"))
      (node (ref "B37") (pin "R1") (pinfunction "K_R1") (pintype "passive"))
    )
    (net (code "888") (name "Net-(AB35AG-P$2)") (class "Default")
      (node (ref "AB02") (pin "BR2") (pinfunction "BR2_BR2") (pintype "passive"))
      (node (ref "AB35") (pin "BS2") (pinfunction "P$2_BS2") (pintype "passive"))
    )
    (net (code "889") (name "Net-(AB35AH-P$2)") (class "Default")
      (node (ref "AB02") (pin "BS2") (pinfunction "BS2_BS2") (pintype "passive"))
      (node (ref "AB35") (pin "BT2") (pinfunction "P$2_BT2") (pintype "passive"))
    )
    (net (code "890") (name "Net-(AB35K-P$2)") (class "Default")
      (node (ref "AB35") (pin "AM2") (pinfunction "P$2_AM2") (pintype "passive"))
      (node (ref "B36") (pin "J2") (pinfunction "J_J2") (pintype "passive"))
    )
    (net (code "891") (name "Net-(AB35L-P$2)") (class "Default")
      (node (ref "AB35") (pin "AN2") (pinfunction "P$2_AN2") (pintype "passive"))
      (node (ref "B36") (pin "K2") (pinfunction "K_K2") (pintype "passive"))
    )
    (net (code "892") (name "Net-(AB35M-P$2)") (class "Default")
      (node (ref "AB35") (pin "AP2") (pinfunction "P$2_AP2") (pintype "passive"))
      (node (ref "B36") (pin "H1") (pinfunction "J_H1") (pintype "passive"))
    )
    (net (code "893") (name "Net-(AB35N-P$2)") (class "Default")
      (node (ref "AB35") (pin "AR2") (pinfunction "P$2_AR2") (pintype "passive"))
      (node (ref "B36") (pin "J1") (pinfunction "K_J1") (pintype "passive"))
    )
    (net (code "894") (name "Net-(AB35U-P$2)") (class "Default")
      (node (ref "AB35") (pin "BC2") (pinfunction "P$2_BC2") (pintype "passive"))
      (node (ref "B36") (pin "S2") (pinfunction "J_S2") (pintype "passive"))
    )
    (net (code "895") (name "Net-(AB35V-P$2)") (class "Default")
      (node (ref "AB35") (pin "BD2") (pinfunction "P$2_BD2") (pintype "passive"))
      (node (ref "B36") (pin "T2") (pinfunction "K_T2") (pintype "passive"))
    )
    (net (code "896") (name "Net-(AB35W-P$2)") (class "Default")
      (node (ref "AB35") (pin "BE2") (pinfunction "P$2_BE2") (pintype "passive"))
      (node (ref "B36") (pin "P1") (pinfunction "J_P1") (pintype "passive"))
    )
    (net (code "897") (name "Net-(AB35X-P$2)") (class "Default")
      (node (ref "AB35") (pin "BF2") (pinfunction "P$2_BF2") (pintype "passive"))
      (node (ref "B36") (pin "R1") (pinfunction "K_R1") (pintype "passive"))
    )
    (net (code "898") (name "Net-(AB35Y-P$2)") (class "Default")
      (node (ref "AB35") (pin "BH2") (pinfunction "P$2_BH2") (pintype "passive"))
      (node (ref "B37") (pin "J2") (pinfunction "J_J2") (pintype "passive"))
    )
    (net (code "899") (name "Net-(AB35Z-P$2)") (class "Default")
      (node (ref "AB35") (pin "BJ2") (pinfunction "P$2_BJ2") (pintype "passive"))
      (node (ref "B37") (pin "K2") (pinfunction "K_K2") (pintype "passive"))
    )
    (net (code "900") (name "Net-(B04F-OUT)") (class "Default")
      (node (ref "B04") (pin "M2") (pinfunction "OUT_M2") (pintype "output"))
      (node (ref "B05") (pin "U2") (pinfunction "S_U2") (pintype "input"))
    )
    (net (code "901") (name "Net-(B04G-OUT)") (class "Default")
      (node (ref "B04") (pin "N1") (pinfunction "OUT_N1") (pintype "output"))
      (node (ref "B05") (pin "S2") (pinfunction "C_S2") (pintype "input"))
    )
    (net (code "902") (name "Net-(B04I-IN3)") (class "Default")
      (node (ref "B04") (pin "S1") (pinfunction "IN3_S1") (pintype "input"))
      (node (ref "B05") (pin "R2") (pinfunction "0_R2") (pintype "output"))
    )
    (net (code "903") (name "Net-(B05A-C)") (class "Default")
      (node (ref "B05") (pin "B1") (pinfunction "C_B1") (pintype "input"))
      (node (ref "B06") (pin "K1") (pinfunction "OUT_K1") (pintype "output"))
    )
    (net (code "904") (name "Net-(B05A-D)") (class "Default")
      (node (ref "B05") (pin "C1") (pinfunction "D_C1") (pintype "input"))
      (node (ref "B06") (pin "N2") (pinfunction "OUT_N2") (pintype "output"))
    )
    (net (code "905") (name "Net-(B05D-D)") (class "Default")
      (node (ref "B05") (pin "E2") (pinfunction "D_E2") (pintype "input"))
      (node (ref "B06") (pin "V2") (pinfunction "OUT_V2") (pintype "output"))
    )
    (net (code "906") (name "Net-(B06B-OUT)") (class "Default")
      (node (ref "B06") (pin "E2") (pinfunction "IN2_E2") (pintype "input"))
      (node (ref "B06") (pin "F1") (pinfunction "OUT_F1") (pintype "output"))
    )
    (net (code "907") (name "Net-(B06C-OUT)") (class "Default")
      (node (ref "B06") (pin "F2") (pinfunction "OUT_F2") (pintype "output"))
      (node (ref "B06") (pin "J1") (pinfunction "IN2_J1") (pintype "input"))
    )
    (net (code "908") (name "Net-(B06H-OUT)") (class "Default")
      (node (ref "B06") (pin "L2") (pinfunction "IN1_L2") (pintype "input"))
      (node (ref "B06") (pin "N1") (pinfunction "OUT_N1") (pintype "output"))
    )
    (net (code "909") (name "Net-(B06I-IN2)") (class "Default")
      (node (ref "B06") (pin "M2") (pinfunction "IN2_M2") (pintype "input"))
      (node (ref "B06") (pin "S1") (pinfunction "OUT_S1") (pintype "output"))
    )
    (net (code "910") (name "Net-(B06K-OUT)") (class "Default")
      (node (ref "B06") (pin "S2") (pinfunction "OUT_S2") (pintype "output"))
      (node (ref "B06") (pin "T2") (pinfunction "IN1_T2") (pintype "input"))
    )
    (net (code "911") (name "Net-(B07A-OUT)") (class "Default")
      (node (ref "B07") (pin "D1") (pinfunction "OUT_D1") (pintype "output"))
      (node (ref "B09") (pin "H1") (pinfunction "IN1_H1") (pintype "input"))
    )
    (net (code "912") (name "Net-(B07D-OUT)") (class "Default")
      (node (ref "B07") (pin "H2") (pinfunction "OUT_H2") (pintype "output"))
      (node (ref "B09") (pin "J2") (pinfunction "IN2_J2") (pintype "input"))
    )
    (net (code "913") (name "Net-(B07E-IN3)") (class "Default")
      (node (ref "B07") (pin "H1") (pinfunction "IN3_H1") (pintype "input"))
      (node (ref "B07") (pin "J2") (pinfunction "IN1_J2") (pintype "input"))
      (node (ref "B09") (pin "N2") (pinfunction "OUT_N2") (pintype "output"))
    )
    (net (code "914") (name "Net-(B07E-OUT)") (class "Default")
      (node (ref "B07") (pin "J1") (pinfunction "OUT_J1") (pintype "output"))
      (node (ref "B07") (pin "M1") (pinfunction "IN3_M1") (pintype "input"))
    )
    (net (code "915") (name "Net-(B07G-OUT)") (class "Default")
      (node (ref "B07") (pin "N1") (pinfunction "OUT_N1") (pintype "output"))
      (node (ref "B07") (pin "N2") (pinfunction "IN1_N2") (pintype "input"))
    )
    (net (code "916") (name "Net-(B09F-OUT)") (class "Default")
      (node (ref "B09") (pin "K1") (pinfunction "OUT_K1") (pintype "output"))
      (node (ref "B09") (pin "L1") (pinfunction "IN1_L1") (pintype "input"))
    )
    (net (code "917") (name "Net-(B09G-OUT)") (class "Default")
      (node (ref "B09") (pin "K2") (pinfunction "OUT_K2") (pintype "output"))
      (node (ref "B09") (pin "M1") (pinfunction "IN2_M1") (pintype "input"))
    )
    (net (code "918") (name "Net-(B09H-OUT)") (class "Default")
      (node (ref "B09") (pin "L2") (pinfunction "IN1_L2") (pintype "input"))
      (node (ref "B09") (pin "N1") (pinfunction "OUT_N1") (pintype "output"))
    )
    (net (code "919") (name "Net-(B09K-IN2)") (class "Default")
      (node (ref "B09") (pin "R2") (pinfunction "IN2_R2") (pintype "input"))
      (node (ref "B09") (pin "V2") (pinfunction "OUT_V2") (pintype "output"))
    )
    (net (code "920") (name "Net-(B17F-D)") (class "Default")
      (node (ref "B17") (pin "M2") (pinfunction "D_M2") (pintype "input"))
      (node (ref "B20") (pin "J1") (pinfunction "OUT_J1") (pintype "output"))
    )
    (net (code "921") (name "Net-(B17G-D)") (class "Default")
      (node (ref "B17") (pin "P1") (pinfunction "D_P1") (pintype "input"))
      (node (ref "B20") (pin "M2") (pinfunction "OUT_M2") (pintype "output"))
    )
    (net (code "922") (name "Net-(B17H-D)") (class "Default")
      (node (ref "B17") (pin "T2") (pinfunction "D_T2") (pintype "input"))
      (node (ref "B20") (pin "N1") (pinfunction "OUT_N1") (pintype "output"))
    )
    (net (code "923") (name "Net-(B18A-D)") (class "Default")
      (node (ref "B18") (pin "C1") (pinfunction "D_C1") (pintype "input"))
      (node (ref "B20") (pin "S2") (pinfunction "OUT_S2") (pintype "output"))
    )
    (net (code "924") (name "Net-(B18D-D)") (class "Default")
      (node (ref "B18") (pin "E2") (pinfunction "D_E2") (pintype "input"))
      (node (ref "B20") (pin "U1") (pinfunction "OUT_U1") (pintype "output"))
    )
    (net (code "925") (name "Net-(B18E-D)") (class "Default")
      (node (ref "B18") (pin "J1") (pinfunction "D_J1") (pintype "input"))
      (node (ref "B20") (pin "V1") (pinfunction "OUT_V1") (pintype "output"))
    )
    (net (code "926") (name "Net-(B21A-IN1)") (class "Default")
      (node (ref "B21") (pin "A1") (pinfunction "IN1_A1") (pintype "input"))
      (node (ref "B21") (pin "F1") (pinfunction "OUT_F1") (pintype "output"))
    )
    (net (code "927") (name "Net-(B21A-OUT)") (class "Default")
      (node (ref "A21") (pin "H2") (pinfunction "H2_H2") (pintype "input"))
      (node (ref "B21") (pin "C1") (pinfunction "OUT_C1") (pintype "output"))
      (node (ref "B22") (pin "D2") (pinfunction "C_D2") (pintype "input"))
    )
    (net (code "928") (name "Net-(B21B-IN1)") (class "Default")
      (node (ref "B21") (pin "D1") (pinfunction "IN1_D1") (pintype "input"))
      (node (ref "B21") (pin "K2") (pinfunction "OUT_K2") (pintype "output"))
      (node (ref "B22") (pin "C1") (pinfunction "D_C1") (pintype "input"))
    )
    (net (code "929") (name "Net-(B21C-OUT)") (class "Default")
      (node (ref "B21") (pin "F2") (pinfunction "OUT_F2") (pintype "output"))
      (node (ref "B22") (pin "N2") (pinfunction "S_N2") (pintype "input"))
    )
    (net (code "930") (name "Net-(B21F-OUT)") (class "Default")
      (node (ref "B21") (pin "K1") (pinfunction "OUT_K1") (pintype "output"))
      (node (ref "B22") (pin "R1") (pinfunction "S_R1") (pintype "input"))
    )
    (net (code "931") (name "Net-(B21G-IN1)") (class "Default")
      (node (ref "B21") (pin "H2") (pinfunction "IN1_H2") (pintype "input"))
      (node (ref "B21") (pin "N1") (pinfunction "OUT_N1") (pintype "output"))
    )
    (net (code "932") (name "Net-(B21N-OUT)") (class "Default")
      (node (ref "B21") (pin "V2") (pinfunction "OUT_V2") (pintype "output"))
      (node (ref "C12") (pin "M1") (pinfunction "IN1_M1") (pintype "input"))
      (node (ref "C12") (pin "N1") (pinfunction "IN2_N1") (pintype "input"))
      (node (ref "C12") (pin "P1") (pinfunction "IN3_P1") (pintype "input"))
      (node (ref "C12") (pin "R1") (pinfunction "IN4_R1") (pintype "input"))
    )
    (net (code "933") (name "Net-(B25D-P$1)") (class "Default")
      (node (ref "B25") (pin "N2") (pinfunction "P$1_N2") (pintype "passive"))
      (node (ref "B27") (pin "F2") (pinfunction "F2_F2") (pintype "passive"))
    )
    (net (code "934") (name "Net-(B25D-P$2)") (class "Default")
      (node (ref "B25") (pin "P2") (pinfunction "P$2_P2") (pintype "passive"))
      (node (ref "B27") (pin "H2") (pinfunction "H_H2") (pintype "input"))
    )
    (net (code "935") (name "Net-(B25E-P$1)") (class "Default")
      (node (ref "B25") (pin "M2") (pinfunction "P$1_M2") (pintype "passive"))
      (node (ref "B27") (pin "E1") (pinfunction "E1_E1") (pintype "passive"))
    )
    (net (code "936") (name "Net-(B25E-P$2)") (class "Default")
      (node (ref "B25") (pin "R2") (pinfunction "P$2_R2") (pintype "passive"))
      (node (ref "B27") (pin "F1") (pinfunction "H_F1") (pintype "input"))
    )
    (net (code "937") (name "Net-(B25F-P$1)") (class "Default")
      (node (ref "B25") (pin "L2") (pinfunction "P$1_L2") (pintype "passive"))
      (node (ref "B27") (pin "P2") (pinfunction "P2_P2") (pintype "passive"))
    )
    (net (code "938") (name "Net-(B25F-P$2)") (class "Default")
      (node (ref "B25") (pin "S2") (pinfunction "P$2_S2") (pintype "passive"))
      (node (ref "B27") (pin "R2") (pinfunction "H_R2") (pintype "input"))
    )
    (net (code "939") (name "Net-(B25G-P$1)") (class "Default")
      (node (ref "B25") (pin "K2") (pinfunction "P$1_K2") (pintype "passive"))
      (node (ref "B27") (pin "M1") (pinfunction "M1_M1") (pintype "passive"))
    )
    (net (code "940") (name "Net-(B25G-P$2)") (class "Default")
      (node (ref "B25") (pin "T2") (pinfunction "P$2_T2") (pintype "passive"))
      (node (ref "B27") (pin "N1") (pinfunction "H_N1") (pintype "input"))
    )
    (net (code "941") (name "Net-(B36B-H)") (class "Default")
      (node (ref "B36") (pin "F1") (pinfunction "H_F1") (pintype "input"))
      (node (ref "B38") (pin "R2") (pinfunction "P$2_R2") (pintype "passive"))
    )
    (net (code "942") (name "Net-(B36D-H)") (class "Default")
      (node (ref "B36") (pin "H2") (pinfunction "H_H2") (pintype "input"))
      (node (ref "B38") (pin "P2") (pinfunction "P$2_P2") (pintype "passive"))
    )
    (net (code "943") (name "Net-(B36E-H)") (class "Default")
      (node (ref "B36") (pin "N1") (pinfunction "H_N1") (pintype "input"))
      (node (ref "B38") (pin "T2") (pinfunction "P$2_T2") (pintype "passive"))
    )
    (net (code "944") (name "Net-(B36F-H)") (class "Default")
      (node (ref "B36") (pin "R2") (pinfunction "H_R2") (pintype "input"))
      (node (ref "B38") (pin "S2") (pinfunction "P$2_S2") (pintype "passive"))
    )
    (net (code "945") (name "Net-(B37B-H)") (class "Default")
      (node (ref "B37") (pin "F1") (pinfunction "H_F1") (pintype "input"))
      (node (ref "B39") (pin "R2") (pinfunction "P$2_R2") (pintype "passive"))
    )
    (net (code "946") (name "Net-(B37D-H)") (class "Default")
      (node (ref "B37") (pin "H2") (pinfunction "H_H2") (pintype "input"))
      (node (ref "B39") (pin "P2") (pinfunction "P$2_P2") (pintype "passive"))
    )
    (net (code "947") (name "Net-(B37E-H)") (class "Default")
      (node (ref "B37") (pin "N1") (pinfunction "H_N1") (pintype "input"))
      (node (ref "B39") (pin "T2") (pinfunction "P$2_T2") (pintype "passive"))
    )
    (net (code "948") (name "Net-(B37F-H)") (class "Default")
      (node (ref "B37") (pin "R2") (pinfunction "H_R2") (pintype "input"))
      (node (ref "B39") (pin "S2") (pinfunction "P$2_S2") (pintype "passive"))
    )
    (net (code "949") (name "Net-(B38D-P$1)") (class "Default")
      (node (ref "B36") (pin "F2") (pinfunction "F2_F2") (pintype "passive"))
      (node (ref "B38") (pin "N2") (pinfunction "P$1_N2") (pintype "passive"))
    )
    (net (code "950") (name "Net-(B38E-P$1)") (class "Default")
      (node (ref "B36") (pin "E1") (pinfunction "E1_E1") (pintype "passive"))
      (node (ref "B38") (pin "M2") (pinfunction "P$1_M2") (pintype "passive"))
    )
    (net (code "951") (name "Net-(B38F-P$1)") (class "Default")
      (node (ref "B36") (pin "P2") (pinfunction "P2_P2") (pintype "passive"))
      (node (ref "B38") (pin "L2") (pinfunction "P$1_L2") (pintype "passive"))
    )
    (net (code "952") (name "Net-(B38G-P$1)") (class "Default")
      (node (ref "B36") (pin "M1") (pinfunction "M1_M1") (pintype "passive"))
      (node (ref "B38") (pin "K2") (pinfunction "P$1_K2") (pintype "passive"))
    )
    (net (code "953") (name "Net-(B38H-P$1)") (class "Default")
      (node (ref "B38") (pin "F2") (pinfunction "P$1_F2") (pintype "passive"))
      (node (ref "C39") (pin "E1") (pinfunction "E1_E1") (pintype "passive"))
      (node (ref "D39") (pin "E1") (pinfunction "E1_E1") (pintype "passive"))
    )
    (net (code "954") (name "Net-(B39D-P$1)") (class "Default")
      (node (ref "B37") (pin "F2") (pinfunction "F2_F2") (pintype "passive"))
      (node (ref "B39") (pin "N2") (pinfunction "P$1_N2") (pintype "passive"))
    )
    (net (code "955") (name "Net-(B39E-P$1)") (class "Default")
      (node (ref "B37") (pin "E1") (pinfunction "E1_E1") (pintype "passive"))
      (node (ref "B39") (pin "M2") (pinfunction "P$1_M2") (pintype "passive"))
    )
    (net (code "956") (name "Net-(B39F-P$1)") (class "Default")
      (node (ref "B37") (pin "P2") (pinfunction "P2_P2") (pintype "passive"))
      (node (ref "B39") (pin "L2") (pinfunction "P$1_L2") (pintype "passive"))
    )
    (net (code "957") (name "Net-(B39G-P$1)") (class "Default")
      (node (ref "B37") (pin "M1") (pinfunction "M1_M1") (pintype "passive"))
      (node (ref "B39") (pin "K2") (pinfunction "P$1_K2") (pintype "passive"))
    )
    (net (code "958") (name "Net-(B39H-P$1)") (class "Default")
      (node (ref "B39") (pin "F2") (pinfunction "P$1_F2") (pintype "passive"))
      (node (ref "C39") (pin "M1") (pinfunction "M1_M1") (pintype "passive"))
      (node (ref "D39") (pin "M1") (pinfunction "M1_M1") (pintype "passive"))
    )
    (net (code "959") (name "Net-(C01D-P$2)") (class "Default")
      (node (ref "C01") (pin "D2") (pinfunction "P$2_D2") (pintype "bidirectional"))
      (node (ref "C02") (pin "V2") (pinfunction "P$1_V2") (pintype "input"))
      (node (ref "C03") (pin "V2") (pinfunction "P$1_V2") (pintype "input"))
      (node (ref "C04") (pin "V2") (pinfunction "P$1_V2") (pintype "input"))
      (node (ref "C05") (pin "V2") (pinfunction "P$1_V2") (pintype "input"))
      (node (ref "C06") (pin "V2") (pinfunction "P$1_V2") (pintype "input"))
    )
    (net (code "960") (name "Net-(C02A-D)") (class "Default")
      (node (ref "C02") (pin "D2") (pinfunction "D_D2") (pintype "input"))
      (node (ref "C02") (pin "J2") (pinfunction "D_J2") (pintype "input"))
      (node (ref "C03") (pin "D2") (pinfunction "D_D2") (pintype "input"))
      (node (ref "C03") (pin "J2") (pinfunction "D_J2") (pintype "input"))
      (node (ref "C04") (pin "D2") (pinfunction "D_D2") (pintype "input"))
      (node (ref "C04") (pin "J2") (pinfunction "D_J2") (pintype "input"))
      (node (ref "C04") (pin "K2") (pinfunction "E_K2") (pintype "input"))
      (node (ref "C04") (pin "L2") (pinfunction "F_L2") (pintype "input"))
      (node (ref "C04") (pin "M2") (pinfunction "H_M2") (pintype "input"))
      (node (ref "C05") (pin "D2") (pinfunction "D_D2") (pintype "input"))
      (node (ref "C05") (pin "J2") (pinfunction "D_J2") (pintype "input"))
      (node (ref "C06") (pin "D2") (pinfunction "D_D2") (pintype "input"))
      (node (ref "HJ28") (pin "BH2") (pinfunction "BH2_BH2") (pintype "output"))
    )
    (net (code "961") (name "Net-(C02A-E)") (class "Default")
      (node (ref "C02") (pin "E2") (pinfunction "E_E2") (pintype "input"))
      (node (ref "C02") (pin "F2") (pinfunction "F_F2") (pintype "input"))
      (node (ref "C02") (pin "H2") (pinfunction "H_H2") (pintype "input"))
      (node (ref "HJ28") (pin "AK1") (pinfunction "AK1_AK1") (pintype "output"))
    )
    (net (code "962") (name "Net-(C02B-E)") (class "Default")
      (node (ref "C02") (pin "K2") (pinfunction "E_K2") (pintype "input"))
      (node (ref "C02") (pin "L2") (pinfunction "F_L2") (pintype "input"))
      (node (ref "C02") (pin "M2") (pinfunction "H_M2") (pintype "input"))
      (node (ref "HJ28") (pin "AL1") (pinfunction "AL1_AL1") (pintype "output"))
    )
    (net (code "963") (name "Net-(C03A-E)") (class "Default")
      (node (ref "C03") (pin "E2") (pinfunction "E_E2") (pintype "input"))
      (node (ref "C03") (pin "F2") (pinfunction "F_F2") (pintype "input"))
      (node (ref "C03") (pin "H2") (pinfunction "H_H2") (pintype "input"))
      (node (ref "HJ28") (pin "AM1") (pinfunction "AM1_AM1") (pintype "output"))
    )
    (net (code "964") (name "Net-(C03B-E)") (class "Default")
      (node (ref "C03") (pin "K2") (pinfunction "E_K2") (pintype "input"))
      (node (ref "C03") (pin "L2") (pinfunction "F_L2") (pintype "input"))
      (node (ref "C03") (pin "M2") (pinfunction "H_M2") (pintype "input"))
      (node (ref "HJ28") (pin "AN1") (pinfunction "AN1_AN1") (pintype "output"))
    )
    (net (code "965") (name "Net-(C04A-E)") (class "Default")
      (node (ref "C04") (pin "E2") (pinfunction "E_E2") (pintype "input"))
      (node (ref "C04") (pin "F2") (pinfunction "F_F2") (pintype "input"))
      (node (ref "C04") (pin "H2") (pinfunction "H_H2") (pintype "input"))
      (node (ref "HJ28") (pin "AK2") (pinfunction "AK2_AK2") (pintype "output"))
    )
    (net (code "966") (name "Net-(C05A-E)") (class "Default")
      (node (ref "C05") (pin "E2") (pinfunction "E_E2") (pintype "input"))
      (node (ref "C05") (pin "F2") (pinfunction "F_F2") (pintype "input"))
      (node (ref "C05") (pin "H2") (pinfunction "H_H2") (pintype "input"))
      (node (ref "HJ28") (pin "AL2") (pinfunction "AL2_AL2") (pintype "output"))
    )
    (net (code "967") (name "Net-(C05B-E)") (class "Default")
      (node (ref "C05") (pin "K2") (pinfunction "E_K2") (pintype "input"))
      (node (ref "C05") (pin "L2") (pinfunction "F_L2") (pintype "input"))
      (node (ref "C05") (pin "M2") (pinfunction "H_M2") (pintype "input"))
      (node (ref "HJ28") (pin "AM2") (pinfunction "AM2_AM2") (pintype "output"))
    )
    (net (code "968") (name "Net-(C06A-E)") (class "Default")
      (node (ref "C06") (pin "E2") (pinfunction "E_E2") (pintype "input"))
      (node (ref "C06") (pin "F2") (pinfunction "F_F2") (pintype "input"))
      (node (ref "C06") (pin "H2") (pinfunction "H_H2") (pintype "input"))
      (node (ref "HJ28") (pin "AN2") (pinfunction "AN2_AN2") (pintype "output"))
    )
    (net (code "969") (name "Net-(C09A-OUT)") (class "Default")
      (node (ref "C09") (pin "C1") (pinfunction "OUT_C1") (pintype "output"))
      (node (ref "C09") (pin "D1") (pinfunction "IN1_D1") (pintype "input"))
      (node (ref "C11") (pin "K2") (pinfunction "IN2_K2") (pintype "input"))
    )
    (net (code "970") (name "Net-(C09B-OUT)") (class "Default")
      (node (ref "C09") (pin "F1") (pinfunction "OUT_F1") (pintype "output"))
      (node (ref "C09") (pin "H2") (pinfunction "IN1_H2") (pintype "input"))
      (node (ref "D10") (pin "H1") (pinfunction "IN2_H1") (pintype "input"))
    )
    (net (code "971") (name "Net-(C09G-IN2)") (class "Default")
      (node (ref "C09") (pin "J2") (pinfunction "IN2_J2") (pintype "input"))
      (node (ref "C09") (pin "N1") (pinfunction "OUT_N1") (pintype "output"))
    )
    (net (code "972") (name "Net-(C09H-IN1)") (class "Default")
      (node (ref "C09") (pin "L1") (pinfunction "IN1_L1") (pintype "input"))
      (node (ref "D09") (pin "D1") (pinfunction "OUT_D1") (pintype "output"))
    )
    (net (code "973") (name "Net-(C10A-IN1)") (class "Default")
      (node (ref "C10") (pin "A1") (pinfunction "IN1_A1") (pintype "input"))
      (node (ref "C11") (pin "D1") (pinfunction "OUT_D1") (pintype "output"))
    )
    (net (code "974") (name "Net-(C10F-IN1)") (class "Default")
      (node (ref "C10") (pin "H1") (pinfunction "IN1_H1") (pintype "input"))
      (node (ref "C11") (pin "U1") (pinfunction "OUT_U1") (pintype "output"))
    )
    (net (code "975") (name "Net-(C10F-OUT)") (class "Default")
      (node (ref "C10") (pin "K1") (pinfunction "OUT_K1") (pintype "output"))
      (node (ref "D09") (pin "E1") (pinfunction "IN1_E1") (pintype "input"))
      (node (ref "D10") (pin "L2") (pinfunction "IN2_L2") (pintype "input"))
    )
    (net (code "976") (name "Net-(C10G-IN2)") (class "Default")
      (node (ref "C10") (pin "J2") (pinfunction "IN2_J2") (pintype "input"))
      (node (ref "C11") (pin "V1") (pinfunction "OUT_V1") (pintype "output"))
    )
    (net (code "977") (name "Net-(C10G-OUT)") (class "Default")
      (node (ref "C10") (pin "K2") (pinfunction "OUT_K2") (pintype "output"))
      (node (ref "D10") (pin "M2") (pinfunction "IN3_M2") (pintype "input"))
    )
    (net (code "978") (name "Net-(C10I-IN1)") (class "Default")
      (node (ref "C10") (pin "L2") (pinfunction "IN1_L2") (pintype "input"))
      (node (ref "C10") (pin "S1") (pinfunction "OUT_S1") (pintype "output"))
    )
    (net (code "979") (name "Net-(C10I-IN2)") (class "Default")
      (node (ref "C10") (pin "M2") (pinfunction "IN2_M2") (pintype "input"))
      (node (ref "C10") (pin "S2") (pinfunction "OUT_S2") (pintype "output"))
    )
    (net (code "980") (name "Net-(C10K-IN2)") (class "Default")
      (node (ref "C10") (pin "R2") (pinfunction "IN2_R2") (pintype "input"))
      (node (ref "C10") (pin "V2") (pinfunction "OUT_V2") (pintype "output"))
    )
    (net (code "981") (name "Net-(C11D-IN1)") (class "Default")
      (node (ref "C11") (pin "D2") (pinfunction "IN1_D2") (pintype "input"))
      (node (ref "C11") (pin "J1") (pinfunction "OUT_J1") (pintype "output"))
    )
    (net (code "982") (name "Net-(C13A-IN)") (class "Default")
      (node (ref "C13") (pin "E1") (pinfunction "IN_E1") (pintype "input"))
      (node (ref "C13") (pin "S2") (pinfunction "S2_S2") (pintype "output"))
    )
    (net (code "983") (name "Net-(C13A-OUT)") (class "Default")
      (node (ref "C13") (pin "F1") (pinfunction "OUT_F1") (pintype "output"))
      (node (ref "D12") (pin "L1") (pinfunction "IN1_L1") (pintype "input"))
      (node (ref "D24") (pin "N1") (pinfunction "C_N1") (pintype "input"))
    )
    (net (code "984") (name "Net-(C13E-IN)") (class "Default")
      (node (ref "C13") (pin "H1") (pinfunction "IN_H1") (pintype "input"))
      (node (ref "C13") (pin "P2") (pinfunction "P2_P2") (pintype "output"))
    )
    (net (code "985") (name "Net-(C14A-OUT)") (class "Default")
      (node (ref "C14") (pin "C1") (pinfunction "OUT_C1") (pintype "output"))
      (node (ref "C19") (pin "A1") (pinfunction "IN1_A1") (pintype "input"))
    )
    (net (code "986") (name "Net-(C14B-OUT)") (class "Default")
      (node (ref "C14") (pin "F1") (pinfunction "OUT_F1") (pintype "output"))
      (node (ref "C19") (pin "B1") (pinfunction "IN2_B1") (pintype "input"))
    )
    (net (code "987") (name "Net-(C14C-OUT)") (class "Default")
      (node (ref "C14") (pin "F2") (pinfunction "OUT_F2") (pintype "output"))
      (node (ref "C19") (pin "C1") (pinfunction "IN3_C1") (pintype "input"))
    )
    (net (code "988") (name "Net-(C14F-OUT)") (class "Default")
      (node (ref "C14") (pin "K1") (pinfunction "OUT_K1") (pintype "output"))
      (node (ref "C19") (pin "D2") (pinfunction "IN1_D2") (pintype "input"))
    )
    (net (code "989") (name "Net-(C14G-OUT)") (class "Default")
      (node (ref "C14") (pin "K2") (pinfunction "OUT_K2") (pintype "output"))
      (node (ref "C19") (pin "E2") (pinfunction "IN2_E2") (pintype "input"))
    )
    (net (code "990") (name "Net-(C14H-OUT)") (class "Default")
      (node (ref "C14") (pin "N1") (pinfunction "OUT_N1") (pintype "output"))
      (node (ref "C19") (pin "F2") (pinfunction "IN3_F2") (pintype "input"))
    )
    (net (code "991") (name "Net-(C14I-OUT)") (class "Default")
      (node (ref "C14") (pin "N2") (pinfunction "OUT_N2") (pintype "output"))
      (node (ref "C19") (pin "E1") (pinfunction "IN1_E1") (pintype "input"))
    )
    (net (code "992") (name "Net-(C14J-OUT)") (class "Default")
      (node (ref "C14") (pin "S1") (pinfunction "OUT_S1") (pintype "output"))
      (node (ref "C19") (pin "F1") (pinfunction "IN2_F1") (pintype "input"))
    )
    (net (code "993") (name "Net-(C14K-OUT)") (class "Default")
      (node (ref "C14") (pin "S2") (pinfunction "OUT_S2") (pintype "output"))
      (node (ref "C19") (pin "H1") (pinfunction "IN3_H1") (pintype "input"))
    )
    (net (code "994") (name "Net-(C14N-OUT)") (class "Default")
      (node (ref "C14") (pin "V2") (pinfunction "OUT_V2") (pintype "output"))
      (node (ref "C20") (pin "M1") (pinfunction "IN3_M1") (pintype "input"))
    )
    (net (code "995") (name "Net-(C15A-OUT)") (class "Default")
      (node (ref "C15") (pin "C1") (pinfunction "OUT_C1") (pintype "output"))
      (node (ref "C19") (pin "J2") (pinfunction "IN1_J2") (pintype "input"))
    )
    (net (code "996") (name "Net-(C15B-OUT)") (class "Default")
      (node (ref "C15") (pin "F1") (pinfunction "OUT_F1") (pintype "output"))
      (node (ref "C19") (pin "K2") (pinfunction "IN2_K2") (pintype "input"))
    )
    (net (code "997") (name "Net-(C15C-OUT)") (class "Default")
      (node (ref "C15") (pin "F2") (pinfunction "OUT_F2") (pintype "output"))
      (node (ref "C19") (pin "L2") (pinfunction "IN3_L2") (pintype "input"))
    )
    (net (code "998") (name "Net-(C15F-OUT)") (class "Default")
      (node (ref "C15") (pin "K1") (pinfunction "OUT_K1") (pintype "output"))
      (node (ref "C19") (pin "K1") (pinfunction "IN1_K1") (pintype "input"))
    )
    (net (code "999") (name "Net-(C15G-OUT)") (class "Default")
      (node (ref "C15") (pin "K2") (pinfunction "OUT_K2") (pintype "output"))
      (node (ref "C19") (pin "L1") (pinfunction "IN2_L1") (pintype "input"))
    )
    (net (code "1000") (name "Net-(C15H-OUT)") (class "Default")
      (node (ref "C15") (pin "N1") (pinfunction "OUT_N1") (pintype "output"))
      (node (ref "C19") (pin "M1") (pinfunction "IN3_M1") (pintype "input"))
    )
    (net (code "1001") (name "Net-(C15I-OUT)") (class "Default")
      (node (ref "C15") (pin "N2") (pinfunction "OUT_N2") (pintype "output"))
      (node (ref "C19") (pin "N2") (pinfunction "IN1_N2") (pintype "input"))
    )
    (net (code "1002") (name "Net-(C15J-OUT)") (class "Default")
      (node (ref "C15") (pin "S1") (pinfunction "OUT_S1") (pintype "output"))
      (node (ref "C19") (pin "P2") (pinfunction "IN2_P2") (pintype "input"))
    )
    (net (code "1003") (name "Net-(C15K-OUT)") (class "Default")
      (node (ref "C15") (pin "S2") (pinfunction "OUT_S2") (pintype "output"))
      (node (ref "C19") (pin "R2") (pinfunction "IN3_R2") (pintype "input"))
    )
    (net (code "1004") (name "Net-(C15N-OUT)") (class "Default")
      (node (ref "C15") (pin "V2") (pinfunction "OUT_V2") (pintype "output"))
      (node (ref "C20") (pin "R2") (pinfunction "IN3_R2") (pintype "input"))
    )
    (net (code "1005") (name "Net-(C16A-OUT)") (class "Default")
      (node (ref "C16") (pin "C1") (pinfunction "OUT_C1") (pintype "output"))
      (node (ref "C19") (pin "P1") (pinfunction "IN1_P1") (pintype "input"))
    )
    (net (code "1006") (name "Net-(C16B-OUT)") (class "Default")
      (node (ref "C16") (pin "F1") (pinfunction "OUT_F1") (pintype "output"))
      (node (ref "C19") (pin "R1") (pinfunction "IN2_R1") (pintype "input"))
    )
    (net (code "1007") (name "Net-(C16C-OUT)") (class "Default")
      (node (ref "C16") (pin "F2") (pinfunction "OUT_F2") (pintype "output"))
      (node (ref "C19") (pin "S1") (pinfunction "IN3_S1") (pintype "input"))
    )
    (net (code "1008") (name "Net-(C16F-OUT)") (class "Default")
      (node (ref "C16") (pin "K1") (pinfunction "OUT_K1") (pintype "output"))
      (node (ref "C19") (pin "T2") (pinfunction "IN1_T2") (pintype "input"))
    )
    (net (code "1009") (name "Net-(C16G-OUT)") (class "Default")
      (node (ref "C16") (pin "K2") (pinfunction "OUT_K2") (pintype "output"))
      (node (ref "C19") (pin "U2") (pinfunction "IN2_U2") (pintype "input"))
    )
    (net (code "1010") (name "Net-(C16H-OUT)") (class "Default")
      (node (ref "C16") (pin "N1") (pinfunction "OUT_N1") (pintype "output"))
      (node (ref "C19") (pin "V2") (pinfunction "IN3_V2") (pintype "input"))
    )
    (net (code "1011") (name "Net-(C16I-OUT)") (class "Default")
      (node (ref "C16") (pin "N2") (pinfunction "OUT_N2") (pintype "output"))
      (node (ref "C20") (pin "A1") (pinfunction "IN1_A1") (pintype "input"))
    )
    (net (code "1012") (name "Net-(C16J-OUT)") (class "Default")
      (node (ref "C16") (pin "S1") (pinfunction "OUT_S1") (pintype "output"))
      (node (ref "C20") (pin "B1") (pinfunction "IN2_B1") (pintype "input"))
    )
    (net (code "1013") (name "Net-(C16K-OUT)") (class "Default")
      (node (ref "C16") (pin "S2") (pinfunction "OUT_S2") (pintype "output"))
      (node (ref "C20") (pin "C1") (pinfunction "IN3_C1") (pintype "input"))
    )
    (net (code "1014") (name "Net-(C16N-OUT)") (class "Default")
      (node (ref "C16") (pin "V2") (pinfunction "OUT_V2") (pintype "output"))
      (node (ref "C20") (pin "S1") (pinfunction "IN3_S1") (pintype "input"))
    )
    (net (code "1015") (name "Net-(C17A-OUT)") (class "Default")
      (node (ref "C17") (pin "C1") (pinfunction "OUT_C1") (pintype "output"))
      (node (ref "C20") (pin "D2") (pinfunction "IN1_D2") (pintype "input"))
    )
    (net (code "1016") (name "Net-(C17B-OUT)") (class "Default")
      (node (ref "C17") (pin "F1") (pinfunction "OUT_F1") (pintype "output"))
      (node (ref "C20") (pin "E2") (pinfunction "IN2_E2") (pintype "input"))
    )
    (net (code "1017") (name "Net-(C17C-OUT)") (class "Default")
      (node (ref "C17") (pin "F2") (pinfunction "OUT_F2") (pintype "output"))
      (node (ref "C20") (pin "F2") (pinfunction "IN3_F2") (pintype "input"))
    )
    (net (code "1018") (name "Net-(C17F-OUT)") (class "Default")
      (node (ref "C17") (pin "K1") (pinfunction "OUT_K1") (pintype "output"))
      (node (ref "C20") (pin "E1") (pinfunction "IN1_E1") (pintype "input"))
    )
    (net (code "1019") (name "Net-(C17G-OUT)") (class "Default")
      (node (ref "C17") (pin "K2") (pinfunction "OUT_K2") (pintype "output"))
      (node (ref "C20") (pin "F1") (pinfunction "IN2_F1") (pintype "input"))
    )
    (net (code "1020") (name "Net-(C17H-OUT)") (class "Default")
      (node (ref "C17") (pin "N1") (pinfunction "OUT_N1") (pintype "output"))
      (node (ref "C20") (pin "H1") (pinfunction "IN3_H1") (pintype "input"))
    )
    (net (code "1021") (name "Net-(C17I-OUT)") (class "Default")
      (node (ref "C17") (pin "N2") (pinfunction "OUT_N2") (pintype "output"))
      (node (ref "C20") (pin "J2") (pinfunction "IN1_J2") (pintype "input"))
    )
    (net (code "1022") (name "Net-(C17J-OUT)") (class "Default")
      (node (ref "C17") (pin "S1") (pinfunction "OUT_S1") (pintype "output"))
      (node (ref "C20") (pin "K2") (pinfunction "IN2_K2") (pintype "input"))
    )
    (net (code "1023") (name "Net-(C17K-IN2)") (class "Default")
      (node (ref "C17") (pin "R2") (pinfunction "IN2_R2") (pintype "input"))
      (node (ref "D23") (pin "T2") (pinfunction "OUT_T2") (pintype "output"))
    )
    (net (code "1024") (name "Net-(C17K-OUT)") (class "Default")
      (node (ref "C17") (pin "S2") (pinfunction "OUT_S2") (pintype "output"))
      (node (ref "C20") (pin "L2") (pinfunction "IN3_L2") (pintype "input"))
    )
    (net (code "1025") (name "Net-(C17N-OUT)") (class "Default")
      (node (ref "C17") (pin "V2") (pinfunction "OUT_V2") (pintype "output"))
      (node (ref "C20") (pin "V2") (pinfunction "IN3_V2") (pintype "input"))
    )
    (net (code "1026") (name "Net-(C18A-IN2)") (class "Default")
      (node (ref "C18") (pin "B1") (pinfunction "IN2_B1") (pintype "input"))
      (node (ref "C21") (pin "E2") (pinfunction "IN2_E2") (pintype "input"))
      (node (ref "D22") (pin "E1") (pinfunction "OUT_E1") (pintype "open_collector"))
    )
    (net (code "1027") (name "Net-(C18B-IN2)") (class "Default")
      (node (ref "C18") (pin "E1") (pinfunction "IN2_E1") (pintype "input"))
      (node (ref "C21") (pin "K2") (pinfunction "IN2_K2") (pintype "input"))
      (node (ref "D19") (pin "D1") (pinfunction "OUT_D1") (pintype "output"))
    )
    (net (code "1028") (name "Net-(C18B-OUT)") (class "Default")
      (node (ref "C18") (pin "F1") (pinfunction "OUT_F1") (pintype "output"))
      (node (ref "C21") (pin "F1") (pinfunction "IN2_F1") (pintype "input"))
    )
    (net (code "1029") (name "Net-(C18C-IN2)") (class "Default")
      (node (ref "C18") (pin "E2") (pinfunction "IN2_E2") (pintype "input"))
      (node (ref "C18") (pin "K1") (pinfunction "OUT_K1") (pintype "output"))
      (node (ref "C21") (pin "P2") (pinfunction "IN2_P2") (pintype "input"))
    )
    (net (code "1030") (name "Net-(C18C-OUT)") (class "Default")
      (node (ref "C18") (pin "F2") (pinfunction "OUT_F2") (pintype "output"))
      (node (ref "C21") (pin "L1") (pinfunction "IN2_L1") (pintype "input"))
    )
    (net (code "1031") (name "Net-(C18H-IN1)") (class "Default")
      (node (ref "C18") (pin "L1") (pinfunction "IN1_L1") (pintype "input"))
      (node (ref "C18") (pin "N2") (pinfunction "OUT_N2") (pintype "output"))
    )
    (net (code "1032") (name "Net-(C18H-IN2)") (class "Default")
      (node (ref "C18") (pin "M1") (pinfunction "IN2_M1") (pintype "input"))
      (node (ref "C18") (pin "S1") (pinfunction "OUT_S1") (pintype "output"))
    )
    (net (code "1033") (name "Net-(C18H-OUT)") (class "Default")
      (node (ref "C18") (pin "N1") (pinfunction "OUT_N1") (pintype "output"))
      (node (ref "C22") (pin "P1") (pinfunction "D_P1") (pintype "input"))
    )
    (net (code "1034") (name "Net-(C19A-OUT)") (class "Default")
      (node (ref "C19") (pin "D1") (pinfunction "OUT_D1") (pintype "output"))
      (node (ref "C23") (pin "C1") (pinfunction "D_C1") (pintype "input"))
    )
    (net (code "1035") (name "Net-(C19D-OUT)") (class "Default")
      (node (ref "C19") (pin "H2") (pinfunction "OUT_H2") (pintype "output"))
      (node (ref "C23") (pin "E2") (pinfunction "D_E2") (pintype "input"))
    )
    (net (code "1036") (name "Net-(C19E-OUT)") (class "Default")
      (node (ref "C19") (pin "J1") (pinfunction "OUT_J1") (pintype "output"))
      (node (ref "C23") (pin "J1") (pinfunction "D_J1") (pintype "input"))
    )
    (net (code "1037") (name "Net-(C19F-OUT)") (class "Default")
      (node (ref "C19") (pin "M2") (pinfunction "OUT_M2") (pintype "output"))
      (node (ref "C23") (pin "M2") (pinfunction "D_M2") (pintype "input"))
    )
    (net (code "1038") (name "Net-(C19G-OUT)") (class "Default")
      (node (ref "C19") (pin "N1") (pinfunction "OUT_N1") (pintype "output"))
      (node (ref "C23") (pin "P1") (pinfunction "D_P1") (pintype "input"))
    )
    (net (code "1039") (name "Net-(C19H-OUT)") (class "Default")
      (node (ref "C19") (pin "S2") (pinfunction "OUT_S2") (pintype "output"))
      (node (ref "C23") (pin "T2") (pinfunction "D_T2") (pintype "input"))
    )
    (net (code "1040") (name "Net-(C19I-OUT)") (class "Default")
      (node (ref "C19") (pin "U1") (pinfunction "OUT_U1") (pintype "output"))
      (node (ref "C24") (pin "C1") (pinfunction "D_C1") (pintype "input"))
    )
    (net (code "1041") (name "Net-(C19J-OUT)") (class "Default")
      (node (ref "C19") (pin "V1") (pinfunction "OUT_V1") (pintype "output"))
      (node (ref "C24") (pin "E2") (pinfunction "D_E2") (pintype "input"))
    )
    (net (code "1042") (name "Net-(C20A-OUT)") (class "Default")
      (node (ref "C20") (pin "D1") (pinfunction "OUT_D1") (pintype "output"))
      (node (ref "C24") (pin "J1") (pinfunction "D_J1") (pintype "input"))
    )
    (net (code "1043") (name "Net-(C20D-OUT)") (class "Default")
      (node (ref "C20") (pin "H2") (pinfunction "OUT_H2") (pintype "output"))
      (node (ref "C24") (pin "M2") (pinfunction "D_M2") (pintype "input"))
    )
    (net (code "1044") (name "Net-(C20E-OUT)") (class "Default")
      (node (ref "C20") (pin "J1") (pinfunction "OUT_J1") (pintype "output"))
      (node (ref "C24") (pin "P1") (pinfunction "D_P1") (pintype "input"))
    )
    (net (code "1045") (name "Net-(C20F-OUT)") (class "Default")
      (node (ref "C20") (pin "M2") (pinfunction "OUT_M2") (pintype "output"))
      (node (ref "C24") (pin "T2") (pinfunction "D_T2") (pintype "input"))
    )
    (net (code "1046") (name "Net-(C20G-IN1)") (class "Default")
      (node (ref "C20") (pin "K1") (pinfunction "IN1_K1") (pintype "input"))
      (node (ref "C21") (pin "D1") (pinfunction "OUT_D1") (pintype "output"))
    )
    (net (code "1047") (name "Net-(C20G-IN2)") (class "Default")
      (node (ref "C20") (pin "L1") (pinfunction "IN2_L1") (pintype "input"))
      (node (ref "C21") (pin "H2") (pinfunction "OUT_H2") (pintype "output"))
    )
    (net (code "1048") (name "Net-(C20G-OUT)") (class "Default")
      (node (ref "C20") (pin "N1") (pinfunction "OUT_N1") (pintype "output"))
      (node (ref "C22") (pin "C1") (pinfunction "D_C1") (pintype "input"))
    )
    (net (code "1049") (name "Net-(C20H-IN1)") (class "Default")
      (node (ref "C20") (pin "N2") (pinfunction "IN1_N2") (pintype "input"))
      (node (ref "C21") (pin "J1") (pinfunction "OUT_J1") (pintype "output"))
    )
    (net (code "1050") (name "Net-(C20H-IN2)") (class "Default")
      (node (ref "C20") (pin "P2") (pinfunction "IN2_P2") (pintype "input"))
      (node (ref "C21") (pin "M2") (pinfunction "OUT_M2") (pintype "output"))
    )
    (net (code "1051") (name "Net-(C20H-OUT)") (class "Default")
      (node (ref "C20") (pin "S2") (pinfunction "OUT_S2") (pintype "output"))
      (node (ref "C22") (pin "E2") (pinfunction "D_E2") (pintype "input"))
    )
    (net (code "1052") (name "Net-(C20I-IN1)") (class "Default")
      (node (ref "C20") (pin "P1") (pinfunction "IN1_P1") (pintype "input"))
      (node (ref "C21") (pin "N1") (pinfunction "OUT_N1") (pintype "output"))
    )
    (net (code "1053") (name "Net-(C20I-IN2)") (class "Default")
      (node (ref "C20") (pin "R1") (pinfunction "IN2_R1") (pintype "input"))
      (node (ref "C21") (pin "S2") (pinfunction "OUT_S2") (pintype "output"))
    )
    (net (code "1054") (name "Net-(C20I-OUT)") (class "Default")
      (node (ref "C20") (pin "U1") (pinfunction "OUT_U1") (pintype "output"))
      (node (ref "C22") (pin "J1") (pinfunction "D_J1") (pintype "input"))
    )
    (net (code "1055") (name "Net-(C20J-IN1)") (class "Default")
      (node (ref "C20") (pin "T2") (pinfunction "IN1_T2") (pintype "input"))
      (node (ref "C21") (pin "U1") (pinfunction "OUT_U1") (pintype "output"))
    )
    (net (code "1056") (name "Net-(C20J-IN2)") (class "Default")
      (node (ref "C20") (pin "U2") (pinfunction "IN2_U2") (pintype "input"))
      (node (ref "C21") (pin "V1") (pinfunction "OUT_V1") (pintype "output"))
    )
    (net (code "1057") (name "Net-(C20J-OUT)") (class "Default")
      (node (ref "C20") (pin "V1") (pinfunction "OUT_V1") (pintype "output"))
      (node (ref "C22") (pin "M2") (pinfunction "D_M2") (pintype "input"))
    )
    (net (code "1058") (name "Net-(CD27A-C2)") (class "Default")
      (node (ref "C25") (pin "K2") (pinfunction "K2_K2") (pintype "passive"))
      (node (ref "CD27") (pin "AC2") (pinfunction "C2_AC2") (pintype "passive"))
    )
    (net (code "1059") (name "Net-(CD27A-D2)") (class "Default")
      (node (ref "C25") (pin "J2") (pinfunction "J2_J2") (pintype "passive"))
      (node (ref "CD27") (pin "AD2") (pinfunction "D2_AD2") (pintype "passive"))
    )
    (net (code "1060") (name "Net-(CD27A-E2)") (class "Default")
      (node (ref "C25") (pin "M2") (pinfunction "M2_M2") (pintype "passive"))
      (node (ref "CD27") (pin "AE2") (pinfunction "E2_AE2") (pintype "passive"))
    )
    (net (code "1061") (name "Net-(CD27A-F2)") (class "Default")
      (node (ref "C25") (pin "L2") (pinfunction "L2_L2") (pintype "passive"))
      (node (ref "CD27") (pin "AF2") (pinfunction "F2_AF2") (pintype "passive"))
    )
    (net (code "1062") (name "Net-(CD27A-H2)") (class "Default")
      (node (ref "C25") (pin "P2") (pinfunction "P2_P2") (pintype "passive"))
      (node (ref "CD27") (pin "AH2") (pinfunction "H2_AH2") (pintype "passive"))
    )
    (net (code "1063") (name "Net-(CD27A-J2)") (class "Default")
      (node (ref "C25") (pin "N2") (pinfunction "N2_N2") (pintype "passive"))
      (node (ref "CD27") (pin "AJ2") (pinfunction "J2_AJ2") (pintype "passive"))
    )
    (net (code "1064") (name "Net-(CD27A-K2)") (class "Default")
      (node (ref "C25") (pin "S2") (pinfunction "S2_S2") (pintype "passive"))
      (node (ref "CD27") (pin "AK2") (pinfunction "K2_AK2") (pintype "passive"))
    )
    (net (code "1065") (name "Net-(CD27A-L2)") (class "Default")
      (node (ref "C25") (pin "R2") (pinfunction "R2_R2") (pintype "passive"))
      (node (ref "CD27") (pin "AL2") (pinfunction "L2_AL2") (pintype "passive"))
    )
    (net (code "1066") (name "Net-(CD27A-M2)") (class "Default")
      (node (ref "C26") (pin "K2") (pinfunction "K2_K2") (pintype "passive"))
      (node (ref "CD27") (pin "AM2") (pinfunction "M2_AM2") (pintype "passive"))
    )
    (net (code "1067") (name "Net-(CD27A-N2)") (class "Default")
      (node (ref "C26") (pin "J2") (pinfunction "J2_J2") (pintype "passive"))
      (node (ref "CD27") (pin "AN2") (pinfunction "N2_AN2") (pintype "passive"))
    )
    (net (code "1068") (name "Net-(CD27A-P2)") (class "Default")
      (node (ref "C26") (pin "M2") (pinfunction "M2_M2") (pintype "passive"))
      (node (ref "CD27") (pin "AP2") (pinfunction "P2_AP2") (pintype "passive"))
    )
    (net (code "1069") (name "Net-(CD27A-R2)") (class "Default")
      (node (ref "C26") (pin "L2") (pinfunction "L2_L2") (pintype "passive"))
      (node (ref "CD27") (pin "AR2") (pinfunction "R2_AR2") (pintype "passive"))
    )
    (net (code "1070") (name "Net-(CD27A-S2)") (class "Default")
      (node (ref "C26") (pin "P2") (pinfunction "P2_P2") (pintype "passive"))
      (node (ref "CD27") (pin "AS2") (pinfunction "S2_AS2") (pintype "passive"))
    )
    (net (code "1071") (name "Net-(CD27A-T2)") (class "Default")
      (node (ref "C26") (pin "N2") (pinfunction "N2_N2") (pintype "passive"))
      (node (ref "CD27") (pin "AT2") (pinfunction "T2_AT2") (pintype "passive"))
    )
    (net (code "1072") (name "Net-(CD27A-U2)") (class "Default")
      (node (ref "C26") (pin "S2") (pinfunction "S2_S2") (pintype "passive"))
      (node (ref "CD27") (pin "AU2") (pinfunction "U2_AU2") (pintype "passive"))
    )
    (net (code "1073") (name "Net-(CD27A-V2)") (class "Default")
      (node (ref "C26") (pin "R2") (pinfunction "R2_R2") (pintype "passive"))
      (node (ref "CD27") (pin "AV2") (pinfunction "V2_AV2") (pintype "passive"))
    )
    (net (code "1074") (name "Net-(CD27B-C2)") (class "Default")
      (node (ref "CD27") (pin "BC2") (pinfunction "C2_BC2") (pintype "passive"))
      (node (ref "D25") (pin "R2") (pinfunction "R2_R2") (pintype "passive"))
    )
    (net (code "1075") (name "Net-(CD27B-D2)") (class "Default")
      (node (ref "CD27") (pin "BD2") (pinfunction "D2_BD2") (pintype "passive"))
      (node (ref "D25") (pin "S2") (pinfunction "S2_S2") (pintype "passive"))
    )
    (net (code "1076") (name "Net-(CD27B-E2)") (class "Default")
      (node (ref "CD27") (pin "BE2") (pinfunction "E2_BE2") (pintype "passive"))
      (node (ref "D25") (pin "N2") (pinfunction "N2_N2") (pintype "passive"))
    )
    (net (code "1077") (name "Net-(CD27B-F2)") (class "Default")
      (node (ref "CD27") (pin "BF2") (pinfunction "F2_BF2") (pintype "passive"))
      (node (ref "D25") (pin "P2") (pinfunction "P2_P2") (pintype "passive"))
    )
    (net (code "1078") (name "Net-(CD27B-H2)") (class "Default")
      (node (ref "CD27") (pin "BH2") (pinfunction "H2_BH2") (pintype "passive"))
      (node (ref "D25") (pin "L2") (pinfunction "L2_L2") (pintype "passive"))
    )
    (net (code "1079") (name "Net-(CD27B-J2)") (class "Default")
      (node (ref "CD27") (pin "BJ2") (pinfunction "J2_BJ2") (pintype "passive"))
      (node (ref "D25") (pin "M2") (pinfunction "M2_M2") (pintype "passive"))
    )
    (net (code "1080") (name "Net-(CD27B-K2)") (class "Default")
      (node (ref "CD27") (pin "BK2") (pinfunction "K2_BK2") (pintype "passive"))
      (node (ref "D25") (pin "J2") (pinfunction "J2_J2") (pintype "passive"))
    )
    (net (code "1081") (name "Net-(CD27B-L2)") (class "Default")
      (node (ref "CD27") (pin "BL2") (pinfunction "L2_BL2") (pintype "passive"))
      (node (ref "D25") (pin "K2") (pinfunction "K2_K2") (pintype "passive"))
    )
    (net (code "1082") (name "Net-(CD27B-M2)") (class "Default")
      (node (ref "CD27") (pin "BM2") (pinfunction "M2_BM2") (pintype "passive"))
      (node (ref "D26") (pin "R2") (pinfunction "R2_R2") (pintype "passive"))
    )
    (net (code "1083") (name "Net-(CD27B-N2)") (class "Default")
      (node (ref "CD27") (pin "BN2") (pinfunction "N2_BN2") (pintype "passive"))
      (node (ref "D26") (pin "S2") (pinfunction "S2_S2") (pintype "passive"))
    )
    (net (code "1084") (name "Net-(CD27B-P2)") (class "Default")
      (node (ref "CD27") (pin "BP2") (pinfunction "P2_BP2") (pintype "passive"))
      (node (ref "D26") (pin "N2") (pinfunction "N2_N2") (pintype "passive"))
    )
    (net (code "1085") (name "Net-(CD27B-R2)") (class "Default")
      (node (ref "CD27") (pin "BR2") (pinfunction "R2_BR2") (pintype "passive"))
      (node (ref "D26") (pin "P2") (pinfunction "P2_P2") (pintype "passive"))
    )
    (net (code "1086") (name "Net-(CD27B-S2)") (class "Default")
      (node (ref "CD27") (pin "BS2") (pinfunction "S2_BS2") (pintype "passive"))
      (node (ref "D26") (pin "L2") (pinfunction "L2_L2") (pintype "passive"))
    )
    (net (code "1087") (name "Net-(CD27B-T2)") (class "Default")
      (node (ref "CD27") (pin "BT2") (pinfunction "T2_BT2") (pintype "passive"))
      (node (ref "D26") (pin "M2") (pinfunction "M2_M2") (pintype "passive"))
    )
    (net (code "1088") (name "Net-(CD27B-U2)") (class "Default")
      (node (ref "CD27") (pin "BU2") (pinfunction "U2_BU2") (pintype "passive"))
      (node (ref "D26") (pin "J2") (pinfunction "J2_J2") (pintype "passive"))
    )
    (net (code "1089") (name "Net-(CD27B-V2)") (class "Default")
      (node (ref "CD27") (pin "BV2") (pinfunction "V2_BV2") (pintype "passive"))
      (node (ref "D26") (pin "K2") (pinfunction "K2_K2") (pintype "passive"))
    )
    (net (code "1090") (name "Net-(CD29A-C2)") (class "Default")
      (node (ref "C30") (pin "K2") (pinfunction "K2_K2") (pintype "passive"))
      (node (ref "CD29") (pin "AC2") (pinfunction "C2_AC2") (pintype "passive"))
    )
    (net (code "1091") (name "Net-(CD29A-D2)") (class "Default")
      (node (ref "C30") (pin "J2") (pinfunction "J2_J2") (pintype "passive"))
      (node (ref "CD29") (pin "AD2") (pinfunction "D2_AD2") (pintype "passive"))
    )
    (net (code "1092") (name "Net-(CD29A-E2)") (class "Default")
      (node (ref "C30") (pin "M2") (pinfunction "M2_M2") (pintype "passive"))
      (node (ref "CD29") (pin "AE2") (pinfunction "E2_AE2") (pintype "passive"))
    )
    (net (code "1093") (name "Net-(CD29A-F2)") (class "Default")
      (node (ref "C30") (pin "L2") (pinfunction "L2_L2") (pintype "passive"))
      (node (ref "CD29") (pin "AF2") (pinfunction "F2_AF2") (pintype "passive"))
    )
    (net (code "1094") (name "Net-(CD29A-H2)") (class "Default")
      (node (ref "C30") (pin "P2") (pinfunction "P2_P2") (pintype "passive"))
      (node (ref "CD29") (pin "AH2") (pinfunction "H2_AH2") (pintype "passive"))
    )
    (net (code "1095") (name "Net-(CD29A-J2)") (class "Default")
      (node (ref "C30") (pin "N2") (pinfunction "N2_N2") (pintype "passive"))
      (node (ref "CD29") (pin "AJ2") (pinfunction "J2_AJ2") (pintype "passive"))
    )
    (net (code "1096") (name "Net-(CD29A-K2)") (class "Default")
      (node (ref "C30") (pin "S2") (pinfunction "S2_S2") (pintype "passive"))
      (node (ref "CD29") (pin "AK2") (pinfunction "K2_AK2") (pintype "passive"))
    )
    (net (code "1097") (name "Net-(CD29A-L2)") (class "Default")
      (node (ref "C30") (pin "R2") (pinfunction "R2_R2") (pintype "passive"))
      (node (ref "CD29") (pin "AL2") (pinfunction "L2_AL2") (pintype "passive"))
    )
    (net (code "1098") (name "Net-(CD29A-M2)") (class "Default")
      (node (ref "C31") (pin "K2") (pinfunction "K2_K2") (pintype "passive"))
      (node (ref "CD29") (pin "AM2") (pinfunction "M2_AM2") (pintype "passive"))
    )
    (net (code "1099") (name "Net-(CD29A-N2)") (class "Default")
      (node (ref "C31") (pin "J2") (pinfunction "J2_J2") (pintype "passive"))
      (node (ref "CD29") (pin "AN2") (pinfunction "N2_AN2") (pintype "passive"))
    )
    (net (code "1100") (name "Net-(CD29A-P2)") (class "Default")
      (node (ref "C31") (pin "M2") (pinfunction "M2_M2") (pintype "passive"))
      (node (ref "CD29") (pin "AP2") (pinfunction "P2_AP2") (pintype "passive"))
    )
    (net (code "1101") (name "Net-(CD29A-R2)") (class "Default")
      (node (ref "C31") (pin "L2") (pinfunction "L2_L2") (pintype "passive"))
      (node (ref "CD29") (pin "AR2") (pinfunction "R2_AR2") (pintype "passive"))
    )
    (net (code "1102") (name "Net-(CD29A-S2)") (class "Default")
      (node (ref "C31") (pin "P2") (pinfunction "P2_P2") (pintype "passive"))
      (node (ref "CD29") (pin "AS2") (pinfunction "S2_AS2") (pintype "passive"))
    )
    (net (code "1103") (name "Net-(CD29A-T2)") (class "Default")
      (node (ref "C31") (pin "N2") (pinfunction "N2_N2") (pintype "passive"))
      (node (ref "CD29") (pin "AT2") (pinfunction "T2_AT2") (pintype "passive"))
    )
    (net (code "1104") (name "Net-(CD29A-U2)") (class "Default")
      (node (ref "C31") (pin "S2") (pinfunction "S2_S2") (pintype "passive"))
      (node (ref "CD29") (pin "AU2") (pinfunction "U2_AU2") (pintype "passive"))
    )
    (net (code "1105") (name "Net-(CD29A-V2)") (class "Default")
      (node (ref "C31") (pin "R2") (pinfunction "R2_R2") (pintype "passive"))
      (node (ref "CD29") (pin "AV2") (pinfunction "V2_AV2") (pintype "passive"))
    )
    (net (code "1106") (name "Net-(CD29B-C2)") (class "Default")
      (node (ref "CD29") (pin "BC2") (pinfunction "C2_BC2") (pintype "passive"))
      (node (ref "D30") (pin "R2") (pinfunction "R2_R2") (pintype "passive"))
    )
    (net (code "1107") (name "Net-(CD29B-D2)") (class "Default")
      (node (ref "CD29") (pin "BD2") (pinfunction "D2_BD2") (pintype "passive"))
      (node (ref "D30") (pin "S2") (pinfunction "S2_S2") (pintype "passive"))
    )
    (net (code "1108") (name "Net-(CD29B-E2)") (class "Default")
      (node (ref "CD29") (pin "BE2") (pinfunction "E2_BE2") (pintype "passive"))
      (node (ref "D30") (pin "N2") (pinfunction "N2_N2") (pintype "passive"))
    )
    (net (code "1109") (name "Net-(CD29B-F2)") (class "Default")
      (node (ref "CD29") (pin "BF2") (pinfunction "F2_BF2") (pintype "passive"))
      (node (ref "D30") (pin "P2") (pinfunction "P2_P2") (pintype "passive"))
    )
    (net (code "1110") (name "Net-(CD29B-H2)") (class "Default")
      (node (ref "CD29") (pin "BH2") (pinfunction "H2_BH2") (pintype "passive"))
      (node (ref "D30") (pin "L2") (pinfunction "L2_L2") (pintype "passive"))
    )
    (net (code "1111") (name "Net-(CD29B-J2)") (class "Default")
      (node (ref "CD29") (pin "BJ2") (pinfunction "J2_BJ2") (pintype "passive"))
      (node (ref "D30") (pin "M2") (pinfunction "M2_M2") (pintype "passive"))
    )
    (net (code "1112") (name "Net-(CD29B-K2)") (class "Default")
      (node (ref "CD29") (pin "BK2") (pinfunction "K2_BK2") (pintype "passive"))
      (node (ref "D30") (pin "J2") (pinfunction "J2_J2") (pintype "passive"))
    )
    (net (code "1113") (name "Net-(CD29B-L2)") (class "Default")
      (node (ref "CD29") (pin "BL2") (pinfunction "L2_BL2") (pintype "passive"))
      (node (ref "D30") (pin "K2") (pinfunction "K2_K2") (pintype "passive"))
    )
    (net (code "1114") (name "Net-(CD29B-M2)") (class "Default")
      (node (ref "CD29") (pin "BM2") (pinfunction "M2_BM2") (pintype "passive"))
      (node (ref "D31") (pin "R2") (pinfunction "R2_R2") (pintype "passive"))
    )
    (net (code "1115") (name "Net-(CD29B-N2)") (class "Default")
      (node (ref "CD29") (pin "BN2") (pinfunction "N2_BN2") (pintype "passive"))
      (node (ref "D31") (pin "S2") (pinfunction "S2_S2") (pintype "passive"))
    )
    (net (code "1116") (name "Net-(CD29B-P2)") (class "Default")
      (node (ref "CD29") (pin "BP2") (pinfunction "P2_BP2") (pintype "passive"))
      (node (ref "D31") (pin "N2") (pinfunction "N2_N2") (pintype "passive"))
    )
    (net (code "1117") (name "Net-(CD29B-R2)") (class "Default")
      (node (ref "CD29") (pin "BR2") (pinfunction "R2_BR2") (pintype "passive"))
      (node (ref "D31") (pin "P2") (pinfunction "P2_P2") (pintype "passive"))
    )
    (net (code "1118") (name "Net-(CD29B-S2)") (class "Default")
      (node (ref "CD29") (pin "BS2") (pinfunction "S2_BS2") (pintype "passive"))
      (node (ref "D31") (pin "L2") (pinfunction "L2_L2") (pintype "passive"))
    )
    (net (code "1119") (name "Net-(CD29B-T2)") (class "Default")
      (node (ref "CD29") (pin "BT2") (pinfunction "T2_BT2") (pintype "passive"))
      (node (ref "D31") (pin "M2") (pinfunction "M2_M2") (pintype "passive"))
    )
    (net (code "1120") (name "Net-(CD29B-U2)") (class "Default")
      (node (ref "CD29") (pin "BU2") (pinfunction "U2_BU2") (pintype "passive"))
      (node (ref "D31") (pin "J2") (pinfunction "J2_J2") (pintype "passive"))
    )
    (net (code "1121") (name "Net-(CD29B-V2)") (class "Default")
      (node (ref "CD29") (pin "BV2") (pinfunction "V2_BV2") (pintype "passive"))
      (node (ref "D31") (pin "K2") (pinfunction "K2_K2") (pintype "passive"))
    )
    (net (code "1122") (name "Net-(CD34A-C2)") (class "Default")
      (node (ref "C32") (pin "K2") (pinfunction "K2_K2") (pintype "passive"))
      (node (ref "CD34") (pin "AC2") (pinfunction "C2_AC2") (pintype "passive"))
    )
    (net (code "1123") (name "Net-(CD34A-D2)") (class "Default")
      (node (ref "C32") (pin "J2") (pinfunction "J2_J2") (pintype "passive"))
      (node (ref "CD34") (pin "AD2") (pinfunction "D2_AD2") (pintype "passive"))
    )
    (net (code "1124") (name "Net-(CD34A-E2)") (class "Default")
      (node (ref "C32") (pin "M2") (pinfunction "M2_M2") (pintype "passive"))
      (node (ref "CD34") (pin "AE2") (pinfunction "E2_AE2") (pintype "passive"))
    )
    (net (code "1125") (name "Net-(CD34A-F2)") (class "Default")
      (node (ref "C32") (pin "L2") (pinfunction "L2_L2") (pintype "passive"))
      (node (ref "CD34") (pin "AF2") (pinfunction "F2_AF2") (pintype "passive"))
    )
    (net (code "1126") (name "Net-(CD34A-H2)") (class "Default")
      (node (ref "C32") (pin "P2") (pinfunction "P2_P2") (pintype "passive"))
      (node (ref "CD34") (pin "AH2") (pinfunction "H2_AH2") (pintype "passive"))
    )
    (net (code "1127") (name "Net-(CD34A-J2)") (class "Default")
      (node (ref "C32") (pin "N2") (pinfunction "N2_N2") (pintype "passive"))
      (node (ref "CD34") (pin "AJ2") (pinfunction "J2_AJ2") (pintype "passive"))
    )
    (net (code "1128") (name "Net-(CD34A-K2)") (class "Default")
      (node (ref "C32") (pin "S2") (pinfunction "S2_S2") (pintype "passive"))
      (node (ref "CD34") (pin "AK2") (pinfunction "K2_AK2") (pintype "passive"))
    )
    (net (code "1129") (name "Net-(CD34A-L2)") (class "Default")
      (node (ref "C32") (pin "R2") (pinfunction "R2_R2") (pintype "passive"))
      (node (ref "CD34") (pin "AL2") (pinfunction "L2_AL2") (pintype "passive"))
    )
    (net (code "1130") (name "Net-(CD34A-M2)") (class "Default")
      (node (ref "C33") (pin "K2") (pinfunction "K2_K2") (pintype "passive"))
      (node (ref "CD34") (pin "AM2") (pinfunction "M2_AM2") (pintype "passive"))
    )
    (net (code "1131") (name "Net-(CD34A-N2)") (class "Default")
      (node (ref "C33") (pin "J2") (pinfunction "J2_J2") (pintype "passive"))
      (node (ref "CD34") (pin "AN2") (pinfunction "N2_AN2") (pintype "passive"))
    )
    (net (code "1132") (name "Net-(CD34A-P2)") (class "Default")
      (node (ref "C33") (pin "M2") (pinfunction "M2_M2") (pintype "passive"))
      (node (ref "CD34") (pin "AP2") (pinfunction "P2_AP2") (pintype "passive"))
    )
    (net (code "1133") (name "Net-(CD34A-R2)") (class "Default")
      (node (ref "C33") (pin "L2") (pinfunction "L2_L2") (pintype "passive"))
      (node (ref "CD34") (pin "AR2") (pinfunction "R2_AR2") (pintype "passive"))
    )
    (net (code "1134") (name "Net-(CD34A-S2)") (class "Default")
      (node (ref "C33") (pin "P2") (pinfunction "P2_P2") (pintype "passive"))
      (node (ref "CD34") (pin "AS2") (pinfunction "S2_AS2") (pintype "passive"))
    )
    (net (code "1135") (name "Net-(CD34A-T2)") (class "Default")
      (node (ref "C33") (pin "N2") (pinfunction "N2_N2") (pintype "passive"))
      (node (ref "CD34") (pin "AT2") (pinfunction "T2_AT2") (pintype "passive"))
    )
    (net (code "1136") (name "Net-(CD34A-U2)") (class "Default")
      (node (ref "C33") (pin "S2") (pinfunction "S2_S2") (pintype "passive"))
      (node (ref "CD34") (pin "AU2") (pinfunction "U2_AU2") (pintype "passive"))
    )
    (net (code "1137") (name "Net-(CD34A-V2)") (class "Default")
      (node (ref "C33") (pin "R2") (pinfunction "R2_R2") (pintype "passive"))
      (node (ref "CD34") (pin "AV2") (pinfunction "V2_AV2") (pintype "passive"))
    )
    (net (code "1138") (name "Net-(CD34B-C2)") (class "Default")
      (node (ref "CD34") (pin "BC2") (pinfunction "C2_BC2") (pintype "passive"))
      (node (ref "D32") (pin "R2") (pinfunction "R2_R2") (pintype "passive"))
    )
    (net (code "1139") (name "Net-(CD34B-D2)") (class "Default")
      (node (ref "CD34") (pin "BD2") (pinfunction "D2_BD2") (pintype "passive"))
      (node (ref "D32") (pin "S2") (pinfunction "S2_S2") (pintype "passive"))
    )
    (net (code "1140") (name "Net-(CD34B-E2)") (class "Default")
      (node (ref "CD34") (pin "BE2") (pinfunction "E2_BE2") (pintype "passive"))
      (node (ref "D32") (pin "N2") (pinfunction "N2_N2") (pintype "passive"))
    )
    (net (code "1141") (name "Net-(CD34B-F2)") (class "Default")
      (node (ref "CD34") (pin "BF2") (pinfunction "F2_BF2") (pintype "passive"))
      (node (ref "D32") (pin "P2") (pinfunction "P2_P2") (pintype "passive"))
    )
    (net (code "1142") (name "Net-(CD34B-H2)") (class "Default")
      (node (ref "CD34") (pin "BH2") (pinfunction "H2_BH2") (pintype "passive"))
      (node (ref "D32") (pin "L2") (pinfunction "L2_L2") (pintype "passive"))
    )
    (net (code "1143") (name "Net-(CD34B-J2)") (class "Default")
      (node (ref "CD34") (pin "BJ2") (pinfunction "J2_BJ2") (pintype "passive"))
      (node (ref "D32") (pin "M2") (pinfunction "M2_M2") (pintype "passive"))
    )
    (net (code "1144") (name "Net-(CD34B-K2)") (class "Default")
      (node (ref "CD34") (pin "BK2") (pinfunction "K2_BK2") (pintype "passive"))
      (node (ref "D32") (pin "J2") (pinfunction "J2_J2") (pintype "passive"))
    )
    (net (code "1145") (name "Net-(CD34B-L2)") (class "Default")
      (node (ref "CD34") (pin "BL2") (pinfunction "L2_BL2") (pintype "passive"))
      (node (ref "D32") (pin "K2") (pinfunction "K2_K2") (pintype "passive"))
    )
    (net (code "1146") (name "Net-(CD34B-M2)") (class "Default")
      (node (ref "CD34") (pin "BM2") (pinfunction "M2_BM2") (pintype "passive"))
      (node (ref "D33") (pin "R2") (pinfunction "R2_R2") (pintype "passive"))
    )
    (net (code "1147") (name "Net-(CD34B-N2)") (class "Default")
      (node (ref "CD34") (pin "BN2") (pinfunction "N2_BN2") (pintype "passive"))
      (node (ref "D33") (pin "S2") (pinfunction "S2_S2") (pintype "passive"))
    )
    (net (code "1148") (name "Net-(CD34B-P2)") (class "Default")
      (node (ref "CD34") (pin "BP2") (pinfunction "P2_BP2") (pintype "passive"))
      (node (ref "D33") (pin "N2") (pinfunction "N2_N2") (pintype "passive"))
    )
    (net (code "1149") (name "Net-(CD34B-R2)") (class "Default")
      (node (ref "CD34") (pin "BR2") (pinfunction "R2_BR2") (pintype "passive"))
      (node (ref "D33") (pin "P2") (pinfunction "P2_P2") (pintype "passive"))
    )
    (net (code "1150") (name "Net-(CD34B-S2)") (class "Default")
      (node (ref "CD34") (pin "BS2") (pinfunction "S2_BS2") (pintype "passive"))
      (node (ref "D33") (pin "L2") (pinfunction "L2_L2") (pintype "passive"))
    )
    (net (code "1151") (name "Net-(CD34B-T2)") (class "Default")
      (node (ref "CD34") (pin "BT2") (pinfunction "T2_BT2") (pintype "passive"))
      (node (ref "D33") (pin "M2") (pinfunction "M2_M2") (pintype "passive"))
    )
    (net (code "1152") (name "Net-(CD34B-U2)") (class "Default")
      (node (ref "CD34") (pin "BU2") (pinfunction "U2_BU2") (pintype "passive"))
      (node (ref "D33") (pin "J2") (pinfunction "J2_J2") (pintype "passive"))
    )
    (net (code "1153") (name "Net-(CD34B-V2)") (class "Default")
      (node (ref "CD34") (pin "BV2") (pinfunction "V2_BV2") (pintype "passive"))
      (node (ref "D33") (pin "K2") (pinfunction "K2_K2") (pintype "passive"))
    )
    (net (code "1154") (name "Net-(CD36A-C2)") (class "Default")
      (node (ref "C37") (pin "K2") (pinfunction "K2_K2") (pintype "passive"))
      (node (ref "CD36") (pin "AC2") (pinfunction "C2_AC2") (pintype "passive"))
    )
    (net (code "1155") (name "Net-(CD36A-D2)") (class "Default")
      (node (ref "C37") (pin "J2") (pinfunction "J2_J2") (pintype "passive"))
      (node (ref "CD36") (pin "AD2") (pinfunction "D2_AD2") (pintype "passive"))
    )
    (net (code "1156") (name "Net-(CD36A-E2)") (class "Default")
      (node (ref "C37") (pin "M2") (pinfunction "M2_M2") (pintype "passive"))
      (node (ref "CD36") (pin "AE2") (pinfunction "E2_AE2") (pintype "passive"))
    )
    (net (code "1157") (name "Net-(CD36A-F2)") (class "Default")
      (node (ref "C37") (pin "L2") (pinfunction "L2_L2") (pintype "passive"))
      (node (ref "CD36") (pin "AF2") (pinfunction "F2_AF2") (pintype "passive"))
    )
    (net (code "1158") (name "Net-(CD36A-H2)") (class "Default")
      (node (ref "C37") (pin "P2") (pinfunction "P2_P2") (pintype "passive"))
      (node (ref "CD36") (pin "AH2") (pinfunction "H2_AH2") (pintype "passive"))
    )
    (net (code "1159") (name "Net-(CD36A-J2)") (class "Default")
      (node (ref "C37") (pin "N2") (pinfunction "N2_N2") (pintype "passive"))
      (node (ref "CD36") (pin "AJ2") (pinfunction "J2_AJ2") (pintype "passive"))
    )
    (net (code "1160") (name "Net-(CD36A-K2)") (class "Default")
      (node (ref "C37") (pin "S2") (pinfunction "S2_S2") (pintype "passive"))
      (node (ref "CD36") (pin "AK2") (pinfunction "K2_AK2") (pintype "passive"))
    )
    (net (code "1161") (name "Net-(CD36A-L2)") (class "Default")
      (node (ref "C37") (pin "R2") (pinfunction "R2_R2") (pintype "passive"))
      (node (ref "CD36") (pin "AL2") (pinfunction "L2_AL2") (pintype "passive"))
    )
    (net (code "1162") (name "Net-(CD36A-M2)") (class "Default")
      (node (ref "C38") (pin "K2") (pinfunction "K2_K2") (pintype "passive"))
      (node (ref "CD36") (pin "AM2") (pinfunction "M2_AM2") (pintype "passive"))
    )
    (net (code "1163") (name "Net-(CD36A-N2)") (class "Default")
      (node (ref "C38") (pin "J2") (pinfunction "J2_J2") (pintype "passive"))
      (node (ref "CD36") (pin "AN2") (pinfunction "N2_AN2") (pintype "passive"))
    )
    (net (code "1164") (name "Net-(CD36A-P2)") (class "Default")
      (node (ref "C38") (pin "M2") (pinfunction "M2_M2") (pintype "passive"))
      (node (ref "CD36") (pin "AP2") (pinfunction "P2_AP2") (pintype "passive"))
    )
    (net (code "1165") (name "Net-(CD36A-R2)") (class "Default")
      (node (ref "C38") (pin "L2") (pinfunction "L2_L2") (pintype "passive"))
      (node (ref "CD36") (pin "AR2") (pinfunction "R2_AR2") (pintype "passive"))
    )
    (net (code "1166") (name "Net-(CD36A-S2)") (class "Default")
      (node (ref "C38") (pin "P2") (pinfunction "P2_P2") (pintype "passive"))
      (node (ref "CD36") (pin "AS2") (pinfunction "S2_AS2") (pintype "passive"))
    )
    (net (code "1167") (name "Net-(CD36A-T2)") (class "Default")
      (node (ref "C38") (pin "N2") (pinfunction "N2_N2") (pintype "passive"))
      (node (ref "CD36") (pin "AT2") (pinfunction "T2_AT2") (pintype "passive"))
    )
    (net (code "1168") (name "Net-(CD36A-U2)") (class "Default")
      (node (ref "C38") (pin "S2") (pinfunction "S2_S2") (pintype "passive"))
      (node (ref "CD36") (pin "AU2") (pinfunction "U2_AU2") (pintype "passive"))
    )
    (net (code "1169") (name "Net-(CD36A-V2)") (class "Default")
      (node (ref "C38") (pin "R2") (pinfunction "R2_R2") (pintype "passive"))
      (node (ref "CD36") (pin "AV2") (pinfunction "V2_AV2") (pintype "passive"))
    )
    (net (code "1170") (name "Net-(CD36B-C2)") (class "Default")
      (node (ref "CD36") (pin "BC2") (pinfunction "C2_BC2") (pintype "passive"))
      (node (ref "D37") (pin "R2") (pinfunction "R2_R2") (pintype "passive"))
    )
    (net (code "1171") (name "Net-(CD36B-D2)") (class "Default")
      (node (ref "CD36") (pin "BD2") (pinfunction "D2_BD2") (pintype "passive"))
      (node (ref "D37") (pin "S2") (pinfunction "S2_S2") (pintype "passive"))
    )
    (net (code "1172") (name "Net-(CD36B-E2)") (class "Default")
      (node (ref "CD36") (pin "BE2") (pinfunction "E2_BE2") (pintype "passive"))
      (node (ref "D37") (pin "N2") (pinfunction "N2_N2") (pintype "passive"))
    )
    (net (code "1173") (name "Net-(CD36B-F2)") (class "Default")
      (node (ref "CD36") (pin "BF2") (pinfunction "F2_BF2") (pintype "passive"))
      (node (ref "D37") (pin "P2") (pinfunction "P2_P2") (pintype "passive"))
    )
    (net (code "1174") (name "Net-(CD36B-H2)") (class "Default")
      (node (ref "CD36") (pin "BH2") (pinfunction "H2_BH2") (pintype "passive"))
      (node (ref "D37") (pin "L2") (pinfunction "L2_L2") (pintype "passive"))
    )
    (net (code "1175") (name "Net-(CD36B-J2)") (class "Default")
      (node (ref "CD36") (pin "BJ2") (pinfunction "J2_BJ2") (pintype "passive"))
      (node (ref "D37") (pin "M2") (pinfunction "M2_M2") (pintype "passive"))
    )
    (net (code "1176") (name "Net-(CD36B-K2)") (class "Default")
      (node (ref "CD36") (pin "BK2") (pinfunction "K2_BK2") (pintype "passive"))
      (node (ref "D37") (pin "J2") (pinfunction "J2_J2") (pintype "passive"))
    )
    (net (code "1177") (name "Net-(CD36B-L2)") (class "Default")
      (node (ref "CD36") (pin "BL2") (pinfunction "L2_BL2") (pintype "passive"))
      (node (ref "D37") (pin "K2") (pinfunction "K2_K2") (pintype "passive"))
    )
    (net (code "1178") (name "Net-(CD36B-M2)") (class "Default")
      (node (ref "CD36") (pin "BM2") (pinfunction "M2_BM2") (pintype "passive"))
      (node (ref "D38") (pin "R2") (pinfunction "R2_R2") (pintype "passive"))
    )
    (net (code "1179") (name "Net-(CD36B-N2)") (class "Default")
      (node (ref "CD36") (pin "BN2") (pinfunction "N2_BN2") (pintype "passive"))
      (node (ref "D38") (pin "S2") (pinfunction "S2_S2") (pintype "passive"))
    )
    (net (code "1180") (name "Net-(CD36B-P2)") (class "Default")
      (node (ref "CD36") (pin "BP2") (pinfunction "P2_BP2") (pintype "passive"))
      (node (ref "D38") (pin "N2") (pinfunction "N2_N2") (pintype "passive"))
    )
    (net (code "1181") (name "Net-(CD36B-R2)") (class "Default")
      (node (ref "CD36") (pin "BR2") (pinfunction "R2_BR2") (pintype "passive"))
      (node (ref "D38") (pin "P2") (pinfunction "P2_P2") (pintype "passive"))
    )
    (net (code "1182") (name "Net-(CD36B-S2)") (class "Default")
      (node (ref "CD36") (pin "BS2") (pinfunction "S2_BS2") (pintype "passive"))
      (node (ref "D38") (pin "L2") (pinfunction "L2_L2") (pintype "passive"))
    )
    (net (code "1183") (name "Net-(CD36B-T2)") (class "Default")
      (node (ref "CD36") (pin "BT2") (pinfunction "T2_BT2") (pintype "passive"))
      (node (ref "D38") (pin "M2") (pinfunction "M2_M2") (pintype "passive"))
    )
    (net (code "1184") (name "Net-(CD36B-U2)") (class "Default")
      (node (ref "CD36") (pin "BU2") (pinfunction "U2_BU2") (pintype "passive"))
      (node (ref "D38") (pin "J2") (pinfunction "J2_J2") (pintype "passive"))
    )
    (net (code "1185") (name "Net-(CD36B-V2)") (class "Default")
      (node (ref "CD36") (pin "BV2") (pinfunction "V2_BV2") (pintype "passive"))
      (node (ref "D38") (pin "K2") (pinfunction "K2_K2") (pintype "passive"))
    )
    (net (code "1186") (name "Net-(D06A-IN)") (class "Default")
      (node (ref "D06") (pin "E1") (pinfunction "IN_E1") (pintype "input"))
      (node (ref "D06") (pin "R2") (pinfunction "R2_R2") (pintype "output"))
    )
    (net (code "1187") (name "Net-(D07A-IN1)") (class "Default")
      (node (ref "D07") (pin "A1") (pinfunction "IN1_A1") (pintype "input"))
      (node (ref "D07") (pin "D1") (pinfunction "IN1_D1") (pintype "input"))
      (node (ref "D07") (pin "F2") (pinfunction "OUT_F2") (pintype "output"))
    )
    (net (code "1188") (name "Net-(D07F-IN2)") (class "Default")
      (node (ref "D06") (pin "H2") (pinfunction "H2_H2") (pintype "input"))
      (node (ref "D07") (pin "J1") (pinfunction "IN2_J1") (pintype "input"))
      (node (ref "D07") (pin "S2") (pinfunction "OUT_S2") (pintype "output"))
    )
    (net (code "1189") (name "Net-(D07G-IN2)") (class "Default")
      (node (ref "D07") (pin "J2") (pinfunction "IN2_J2") (pintype "input"))
      (node (ref "D08") (pin "F1") (pinfunction "OUT_F1") (pintype "output"))
    )
    (net (code "1190") (name "Net-(D07G-OUT)") (class "Default")
      (node (ref "D07") (pin "K2") (pinfunction "OUT_K2") (pintype "output"))
      (node (ref "E09") (pin "H1") (pinfunction "IN1_H1") (pintype "input"))
    )
    (net (code "1191") (name "Net-(D07H-OUT)") (class "Default")
      (node (ref "D07") (pin "M2") (pinfunction "IN2_M2") (pintype "input"))
      (node (ref "D07") (pin "N1") (pinfunction "OUT_N1") (pintype "output"))
    )
    (net (code "1192") (name "Net-(D07I-OUT)") (class "Default")
      (node (ref "D07") (pin "N2") (pinfunction "OUT_N2") (pintype "output"))
      (node (ref "D08") (pin "H2") (pinfunction "H2_H2") (pintype "input"))
    )
    (net (code "1193") (name "Net-(D07J-OUT)") (class "Default")
      (node (ref "D07") (pin "S1") (pinfunction "OUT_S1") (pintype "output"))
      (node (ref "E09") (pin "D1") (pinfunction "IN1_D1") (pintype "input"))
    )
    (net (code "1194") (name "Net-(D07K-IN2)") (class "Default")
      (node (ref "D07") (pin "R2") (pinfunction "IN2_R2") (pintype "input"))
      (node (ref "D07") (pin "V2") (pinfunction "OUT_V2") (pintype "output"))
    )
    (net (code "1195") (name "Net-(D08A-IN)") (class "Default")
      (node (ref "D08") (pin "E1") (pinfunction "IN_E1") (pintype "input"))
      (node (ref "D08") (pin "R2") (pinfunction "R2_R2") (pintype "output"))
    )
    (net (code "1196") (name "Net-(D09I-OUT)") (class "Default")
      (node (ref "D09") (pin "T2") (pinfunction "IN1_T2") (pintype "input"))
      (node (ref "D09") (pin "U1") (pinfunction "OUT_U1") (pintype "output"))
    )
    (net (code "1197") (name "Net-(D12B-IN1)") (class "Default")
      (node (ref "D12") (pin "D1") (pinfunction "IN1_D1") (pintype "input"))
      (node (ref "D12") (pin "F2") (pinfunction "OUT_F2") (pintype "output"))
    )
    (net (code "1198") (name "Net-(D12B-OUT)") (class "Default")
      (node (ref "D12") (pin "F1") (pinfunction "OUT_F1") (pintype "output"))
      (node (ref "D23") (pin "S1") (pinfunction "IN1A_S1") (pintype "input"))
    )
    (net (code "1199") (name "Net-(D12H-OUT)") (class "Default")
      (node (ref "D12") (pin "N1") (pinfunction "OUT_N1") (pintype "output"))
      (node (ref "D24") (pin "U2") (pinfunction "S_U2") (pintype "input"))
    )
    (net (code "1200") (name "Net-(D12I-OUT)") (class "Default")
      (node (ref "D12") (pin "N2") (pinfunction "OUT_N2") (pintype "output"))
      (node (ref "D24") (pin "T2") (pinfunction "D_T2") (pintype "input"))
    )
    (net (code "1201") (name "Net-(D12J-OUT)") (class "Default")
      (node (ref "D12") (pin "S1") (pinfunction "OUT_S1") (pintype "output"))
      (node (ref "D24") (pin "S2") (pinfunction "C_S2") (pintype "input"))
    )
    (net (code "1202") (name "Net-(D12K-OUT)") (class "Default")
      (node (ref "D12") (pin "S2") (pinfunction "OUT_S2") (pintype "output"))
      (node (ref "D22") (pin "U2") (pinfunction "IN4_U2") (pintype "input"))
    )
    (net (code "1203") (name "Net-(D13B-OUT)") (class "Default")
      (node (ref "D13") (pin "F1") (pinfunction "OUT_F1") (pintype "output"))
      (node (ref "D17") (pin "R1") (pinfunction "IN2_R1") (pintype "input"))
    )
    (net (code "1204") (name "Net-(D13C-OUT)") (class "Default")
      (node (ref "D13") (pin "F2") (pinfunction "OUT_F2") (pintype "output"))
      (node (ref "D17") (pin "R2") (pinfunction "IN3_R2") (pintype "input"))
    )
    (net (code "1205") (name "Net-(D13G-IN1)") (class "Default")
      (node (ref "D13") (pin "H2") (pinfunction "IN1_H2") (pintype "input"))
      (node (ref "D20") (pin "S1") (pinfunction "OUT_S1") (pintype "output"))
    )
    (net (code "1206") (name "Net-(D13H-IN1)") (class "Default")
      (node (ref "D13") (pin "L1") (pinfunction "IN1_L1") (pintype "input"))
      (node (ref "D13") (pin "S1") (pinfunction "OUT_S1") (pintype "output"))
    )
    (net (code "1207") (name "Net-(D13N-OUT)") (class "Default")
      (node (ref "D13") (pin "V2") (pinfunction "OUT_V2") (pintype "output"))
      (node (ref "D16") (pin "L1") (pinfunction "IN1_L1") (pintype "input"))
    )
    (net (code "1208") (name "Net-(D14B-OUT)") (class "Default")
      (node (ref "C13") (pin "H2") (pinfunction "H2_H2") (pintype "input"))
      (node (ref "D14") (pin "F1") (pinfunction "OUT_F1") (pintype "output"))
      (node (ref "D24") (pin "L2") (pinfunction "C_L2") (pintype "input"))
    )
    (net (code "1209") (name "Net-(D14C-OUT)") (class "Default")
      (node (ref "D14") (pin "F2") (pinfunction "OUT_F2") (pintype "output"))
      (node (ref "D14") (pin "J2") (pinfunction "IN2_J2") (pintype "input"))
    )
    (net (code "1210") (name "Net-(D14G-IN1)") (class "Default")
      (node (ref "D14") (pin "H2") (pinfunction "IN1_H2") (pintype "input"))
      (node (ref "D14") (pin "N2") (pinfunction "OUT_N2") (pintype "output"))
    )
    (net (code "1211") (name "Net-(D14H-OUT)") (class "Default")
      (node (ref "D14") (pin "N1") (pinfunction "OUT_N1") (pintype "output"))
      (node (ref "D19") (pin "F2") (pinfunction "IN3_F2") (pintype "input"))
    )
    (net (code "1212") (name "Net-(D14J-IN2)") (class "Default")
      (node (ref "D14") (pin "R1") (pinfunction "IN2_R1") (pintype "input"))
      (node (ref "D14") (pin "S2") (pinfunction "OUT_S2") (pintype "output"))
    )
    (net (code "1213") (name "Net-(D14J-OUT)") (class "Default")
      (node (ref "D14") (pin "S1") (pinfunction "OUT_S1") (pintype "output"))
      (node (ref "D24") (pin "B1") (pinfunction "C_B1") (pintype "input"))
      (node (ref "D24") (pin "D2") (pinfunction "C_D2") (pintype "input"))
      (node (ref "D24") (pin "H1") (pinfunction "C_H1") (pintype "input"))
    )
    (net (code "1214") (name "Net-(D14N-OUT)") (class "Default")
      (node (ref "D14") (pin "V2") (pinfunction "OUT_V2") (pintype "output"))
      (node (ref "D22") (pin "S2") (pinfunction "IN2_S2") (pintype "input"))
    )
    (net (code "1215") (name "Net-(D15A-OUT)") (class "Default")
      (node (ref "D15") (pin "C1") (pinfunction "OUT_C1") (pintype "output"))
      (node (ref "D17") (pin "D2") (pinfunction "IN1_D2") (pintype "input"))
    )
    (net (code "1216") (name "Net-(D15B-OUT)") (class "Default")
      (node (ref "D15") (pin "F1") (pinfunction "OUT_F1") (pintype "output"))
      (node (ref "D17") (pin "F2") (pinfunction "IN3_F2") (pintype "input"))
    )
    (net (code "1217") (name "Net-(D15C-IN2)") (class "Default")
      (node (ref "D15") (pin "E2") (pinfunction "IN2_E2") (pintype "input"))
      (node (ref "D21") (pin "E1") (pinfunction "OUT_E1") (pintype "output"))
    )
    (net (code "1218") (name "Net-(D15G-OUT)") (class "Default")
      (node (ref "D15") (pin "K2") (pinfunction "OUT_K2") (pintype "output"))
      (node (ref "D15") (pin "L1") (pinfunction "IN1_L1") (pintype "input"))
    )
    (net (code "1219") (name "Net-(D15H-OUT)") (class "Default")
      (node (ref "D15") (pin "N1") (pinfunction "OUT_N1") (pintype "output"))
      (node (ref "D24") (pin "M2") (pinfunction "D_M2") (pintype "input"))
    )
    (net (code "1220") (name "Net-(D15I-IN1)") (class "Default")
      (node (ref "D15") (pin "L2") (pinfunction "IN1_L2") (pintype "input"))
      (node (ref "D21") (pin "J2") (pinfunction "OUT_J2") (pintype "output"))
    )
    (net (code "1221") (name "Net-(D15K-OUT)") (class "Default")
      (node (ref "D15") (pin "S2") (pinfunction "OUT_S2") (pintype "output"))
      (node (ref "D20") (pin "K1") (pinfunction "IN4_K1") (pintype "input"))
    )
    (net (code "1222") (name "Net-(D15N-IN1)") (class "Default")
      (node (ref "D15") (pin "T2") (pinfunction "IN1_T2") (pintype "input"))
      (node (ref "D17") (pin "S1") (pinfunction "IN3_S1") (pintype "input"))
      (node (ref "D18") (pin "D1") (pinfunction "OUT_D1") (pintype "output"))
    )
    (net (code "1223") (name "Net-(D16A-IN2)") (class "Default")
      (node (ref "D16") (pin "B1") (pinfunction "IN2_B1") (pintype "input"))
      (node (ref "D21") (pin "P2") (pinfunction "OUT_P2") (pintype "output"))
    )
    (net (code "1224") (name "Net-(D16A-OUT)") (class "Default")
      (node (ref "D16") (pin "C1") (pinfunction "OUT_C1") (pintype "output"))
      (node (ref "D21") (pin "A1") (pinfunction "IN1_A1") (pintype "input"))
    )
    (net (code "1225") (name "Net-(D16B-IN2)") (class "Default")
      (node (ref "D16") (pin "E1") (pinfunction "IN2_E1") (pintype "input"))
      (node (ref "D21") (pin "S1") (pinfunction "OUT_S1") (pintype "output"))
    )
    (net (code "1226") (name "Net-(D16B-OUT)") (class "Default")
      (node (ref "D16") (pin "F1") (pinfunction "OUT_F1") (pintype "output"))
      (node (ref "D21") (pin "B1") (pinfunction "IN2_B1") (pintype "input"))
    )
    (net (code "1227") (name "Net-(D16C-IN2)") (class "Default")
      (node (ref "D16") (pin "E2") (pinfunction "IN2_E2") (pintype "input"))
      (node (ref "D21") (pin "V2") (pinfunction "OUT_V2") (pintype "output"))
    )
    (net (code "1228") (name "Net-(D16C-OUT)") (class "Default")
      (node (ref "D16") (pin "F2") (pinfunction "OUT_F2") (pintype "output"))
      (node (ref "D21") (pin "C1") (pinfunction "IN3_C1") (pintype "input"))
    )
    (net (code "1229") (name "Net-(D16F-IN1)") (class "Default")
      (node (ref "D16") (pin "H1") (pinfunction "IN1_H1") (pintype "input"))
      (node (ref "D19") (pin "J1") (pinfunction "OUT_J1") (pintype "output"))
    )
    (net (code "1230") (name "Net-(D16F-IN2)") (class "Default")
      (node (ref "D16") (pin "J1") (pinfunction "IN2_J1") (pintype "input"))
      (node (ref "D19") (pin "M2") (pinfunction "OUT_M2") (pintype "output"))
    )
    (net (code "1231") (name "Net-(D16G-OUT)") (class "Default")
      (node (ref "D16") (pin "K2") (pinfunction "OUT_K2") (pintype "output"))
      (node (ref "D19") (pin "D2") (pinfunction "IN1_D2") (pintype "input"))
    )
    (net (code "1232") (name "Net-(D16H-OUT)") (class "Default")
      (node (ref "D16") (pin "L2") (pinfunction "IN1_L2") (pintype "input"))
      (node (ref "D16") (pin "N1") (pinfunction "OUT_N1") (pintype "output"))
      (node (ref "D18") (pin "P2") (pinfunction "IN2_P2") (pintype "input"))
    )
    (net (code "1233") (name "Net-(D16I-OUT)") (class "Default")
      (node (ref "D16") (pin "N2") (pinfunction "OUT_N2") (pintype "output"))
      (node (ref "D18") (pin "R1") (pinfunction "IN2_R1") (pintype "input"))
    )
    (net (code "1234") (name "Net-(D17D-IN2)") (class "Default")
      (node (ref "D17") (pin "E2") (pinfunction "IN2_E2") (pintype "input"))
      (node (ref "D20") (pin "E1") (pinfunction "OUT_E1") (pintype "output"))
    )
    (net (code "1235") (name "Net-(D17E-OUT)") (class "Default")
      (node (ref "D17") (pin "J1") (pinfunction "OUT_J1") (pintype "output"))
      (node (ref "D17") (pin "K2") (pinfunction "IN2_K2") (pintype "input"))
      (node (ref "D20") (pin "F2") (pinfunction "IN3_F2") (pintype "input"))
    )
    (net (code "1236") (name "Net-(D17G-IN2)") (class "Default")
      (node (ref "D17") (pin "L1") (pinfunction "IN2_L1") (pintype "input"))
      (node (ref "D17") (pin "S2") (pinfunction "OUT_S2") (pintype "output"))
    )
    (net (code "1237") (name "Net-(D17H-IN2)") (class "Default")
      (node (ref "D17") (pin "P2") (pinfunction "IN2_P2") (pintype "input"))
      (node (ref "D23") (pin "V2") (pinfunction "OUT_V2") (pintype "output"))
    )
    (net (code "1238") (name "Net-(D18D-OUT)") (class "Default")
      (node (ref "D18") (pin "H2") (pinfunction "OUT_H2") (pintype "output"))
      (node (ref "D22") (pin "F1") (pinfunction "IN1_F1") (pintype "input"))
    )
    (net (code "1239") (name "Net-(D18E-OUT)") (class "Default")
      (node (ref "D18") (pin "J1") (pinfunction "OUT_J1") (pintype "output"))
      (node (ref "D22") (pin "K2") (pinfunction "IN1_K2") (pintype "input"))
    )
    (net (code "1240") (name "Net-(D18G-OUT)") (class "Default")
      (node (ref "D18") (pin "N1") (pinfunction "OUT_N1") (pintype "output"))
      (node (ref "D22") (pin "R1") (pinfunction "IN4_R1") (pintype "input"))
    )
    (net (code "1241") (name "Net-(D19D-IN2)") (class "Default")
      (node (ref "D19") (pin "E2") (pinfunction "IN2_E2") (pintype "input"))
      (node (ref "D19") (pin "N1") (pinfunction "OUT_N1") (pintype "output"))
    )
    (net (code "1242") (name "Net-(D19D-OUT)") (class "Default")
      (node (ref "D19") (pin "H2") (pinfunction "OUT_H2") (pintype "output"))
      (node (ref "D23") (pin "P1") (pinfunction "IN5C_P1") (pintype "input"))
    )
    (net (code "1243") (name "Net-(D20E-IN2)") (class "Default")
      (node (ref "D20") (pin "H1") (pinfunction "IN2_H1") (pintype "input"))
      (node (ref "D20") (pin "P2") (pinfunction "OUT_P2") (pintype "output"))
    )
    (net (code "1244") (name "Net-(E09A-OUT)") (class "Default")
      (node (ref "E09") (pin "C1") (pinfunction "OUT_C1") (pintype "output"))
      (node (ref "E09") (pin "E1") (pinfunction "IN2_E1") (pintype "input"))
    )
    (net (code "1245") (name "Net-(E09C-OUT)") (class "Default")
      (node (ref "E09") (pin "F2") (pinfunction "OUT_F2") (pintype "output"))
      (node (ref "E09") (pin "J1") (pinfunction "IN2_J1") (pintype "input"))
    )
    (net (code "1246") (name "Net-(E09F-OUT)") (class "Default")
      (node (ref "A23") (pin "H2") (pinfunction "H2_H2") (pintype "input"))
      (node (ref "E09") (pin "K1") (pinfunction "OUT_K1") (pintype "output"))
    )
    (net (code "1247") (name "Net-(E09G-OUT)") (class "Default")
      (node (ref "E09") (pin "K2") (pinfunction "OUT_K2") (pintype "output"))
      (node (ref "F11") (pin "K2") (pinfunction "IN1_K2") (pintype "input"))
    )
    (net (code "1248") (name "Net-(E11J-IN1)") (class "Default")
      (node (ref "E11") (pin "P1") (pinfunction "IN1_P1") (pintype "input"))
      (node (ref "F11") (pin "L1") (pinfunction "OUT_L1") (pintype "output"))
    )
    (net (code "1249") (name "Net-(E11N-OUT)") (class "Default")
      (node (ref "E11") (pin "V2") (pinfunction "OUT_V2") (pintype "output"))
      (node (ref "E12") (pin "R2") (pinfunction "IN2_R2") (pintype "input"))
    )
    (net (code "1250") (name "Net-(E12A-IN1)") (class "Default")
      (node (ref "E12") (pin "A1") (pinfunction "IN1_A1") (pintype "input"))
      (node (ref "E12") (pin "F1") (pinfunction "OUT_F1") (pintype "output"))
    )
    (net (code "1251") (name "Net-(E12A-OUT)") (class "Default")
      (node (ref "E12") (pin "C1") (pinfunction "OUT_C1") (pintype "output"))
      (node (ref "E18") (pin "K1") (pinfunction "S_K1") (pintype "input"))
    )
    (net (code "1252") (name "Net-(E12C-OUT)") (class "Default")
      (node (ref "E12") (pin "F2") (pinfunction "OUT_F2") (pintype "output"))
      (node (ref "E16") (pin "H2") (pinfunction "H2_H2") (pintype "input"))
    )
    (net (code "1253") (name "Net-(E12J-IN1)") (class "Default")
      (node (ref "E12") (pin "P1") (pinfunction "IN1_P1") (pintype "input"))
      (node (ref "F19") (pin "P2") (pinfunction "OUT_P2") (pintype "output"))
    )
    (net (code "1254") (name "Net-(E12K-OUT)") (class "Default")
      (node (ref "E12") (pin "S2") (pinfunction "OUT_S2") (pintype "output"))
      (node (ref "F21") (pin "A1") (pinfunction "IN1_A1") (pintype "input"))
    )
    (net (code "1255") (name "Net-(E12N-IN2)") (class "Default")
      (node (ref "E12") (pin "U2") (pinfunction "IN2_U2") (pintype "input"))
      (node (ref "F19") (pin "S1") (pinfunction "OUT_S1") (pintype "output"))
    )
    (net (code "1256") (name "Net-(E13C-OUT)") (class "Default")
      (node (ref "E13") (pin "R1") (pinfunction "OUT_R1") (pintype "output"))
      (node (ref "E18") (pin "M2") (pinfunction "D_M2") (pintype "input"))
    )
    (net (code "1257") (name "Net-(E14A-OUT)") (class "Default")
      (node (ref "E14") (pin "D1") (pinfunction "OUT_D1") (pintype "output"))
      (node (ref "E15") (pin "D2") (pinfunction "IN1_D2") (pintype "input"))
      (node (ref "E15") (pin "E1") (pinfunction "IN2_E1") (pintype "input"))
      (node (ref "F08") (pin "J2") (pinfunction "IN2_J2") (pintype "input"))
    )
    (net (code "1258") (name "Net-(E14D-OUT)") (class "Default")
      (node (ref "E14") (pin "H2") (pinfunction "OUT_H2") (pintype "output"))
      (node (ref "F09") (pin "K2") (pinfunction "IN5_K2") (pintype "input"))
    )
    (net (code "1259") (name "Net-(E14E-IN1)") (class "Default")
      (node (ref "E14") (pin "E1") (pinfunction "IN1_E1") (pintype "input"))
      (node (ref "F19") (pin "K1") (pinfunction "IN4_K1") (pintype "input"))
      (node (ref "F21") (pin "S2") (pinfunction "OUT_S2") (pintype "output"))
      (node (ref "F21") (pin "U2") (pinfunction "IN2_U2") (pintype "input"))
    )
    (net (code "1260") (name "Net-(E14E-IN2)") (class "Default")
      (node (ref "E14") (pin "F1") (pinfunction "IN2_F1") (pintype "input"))
      (node (ref "F19") (pin "J1") (pinfunction "IN3_J1") (pintype "input"))
      (node (ref "F21") (pin "S1") (pinfunction "OUT_S1") (pintype "output"))
      (node (ref "F21") (pin "T2") (pinfunction "IN1_T2") (pintype "input"))
    )
    (net (code "1261") (name "Net-(E14G-OUT)") (class "Default")
      (node (ref "E14") (pin "N1") (pinfunction "OUT_N1") (pintype "output"))
      (node (ref "E14") (pin "N2") (pinfunction "IN1_N2") (pintype "input"))
    )
    (net (code "1262") (name "Net-(E14I-OUT)") (class "Default")
      (node (ref "E14") (pin "U1") (pinfunction "OUT_U1") (pintype "output"))
      (node (ref "F12") (pin "H2") (pinfunction "H2_H2") (pintype "input"))
    )
    (net (code "1263") (name "Net-(E14J-OUT)") (class "Default")
      (node (ref "E14") (pin "V1") (pinfunction "OUT_V1") (pintype "output"))
      (node (ref "E15") (pin "T2") (pinfunction "IN1_T2") (pintype "input"))
    )
    (net (code "1264") (name "Net-(E15A-OUT)") (class "Default")
      (node (ref "E15") (pin "C1") (pinfunction "OUT_C1") (pintype "output"))
      (node (ref "E15") (pin "D1") (pinfunction "IN1_D1") (pintype "input"))
      (node (ref "F08") (pin "H2") (pinfunction "IN1_H2") (pintype "input"))
    )
    (net (code "1265") (name "Net-(E15C-IN2)") (class "Default")
      (node (ref "E15") (pin "E2") (pinfunction "IN2_E2") (pintype "input"))
      (node (ref "E15") (pin "K1") (pinfunction "OUT_K1") (pintype "output"))
    )
    (net (code "1266") (name "Net-(E15H-OUT)") (class "Default")
      (node (ref "E15") (pin "N1") (pinfunction "OUT_N1") (pintype "output"))
      (node (ref "E19") (pin "F2") (pinfunction "S_F2") (pintype "input"))
      (node (ref "F08") (pin "N2") (pinfunction "IN1_N2") (pintype "input"))
    )
    (net (code "1267") (name "Net-(E15K-OUT)") (class "Default")
      (node (ref "E15") (pin "S2") (pinfunction "OUT_S2") (pintype "output"))
      (node (ref "F13") (pin "H2") (pinfunction "H2_H2") (pintype "input"))
    )
    (net (code "1268") (name "Net-(E16A-IN)") (class "Default")
      (node (ref "E16") (pin "E1") (pinfunction "IN_E1") (pintype "input"))
      (node (ref "E16") (pin "R2") (pinfunction "R2_R2") (pintype "output"))
    )
    (net (code "1269") (name "Net-(E16A-OUT)") (class "Default")
      (node (ref "E16") (pin "F1") (pinfunction "OUT_F1") (pintype "output"))
      (node (ref "E18") (pin "H1") (pinfunction "C_H1") (pintype "input"))
    )
    (net (code "1270") (name "Net-(E17A-IN)") (class "Default")
      (node (ref "E17") (pin "E1") (pinfunction "IN_E1") (pintype "input"))
      (node (ref "E17") (pin "M2") (pinfunction "M2_M2") (pintype "output"))
    )
    (net (code "1271") (name "Net-(E17E-IN)") (class "Default")
      (node (ref "E17") (pin "H1") (pinfunction "IN_H1") (pintype "input"))
      (node (ref "E17") (pin "U2") (pinfunction "U2_U2") (pintype "output"))
    )
    (net (code "1272") (name "Net-(E18G-C)") (class "Default")
      (node (ref "E18") (pin "N1") (pinfunction "C_N1") (pintype "input"))
      (node (ref "E25") (pin "U1") (pinfunction "OUT_U1") (pintype "output"))
    )
    (net (code "1273") (name "Net-(E18G-D)") (class "Default")
      (node (ref "E18") (pin "P1") (pinfunction "D_P1") (pintype "input"))
      (node (ref "E28") (pin "T2") (pinfunction "OUT_T2") (pintype "output"))
    )
    (net (code "1274") (name "Net-(E20A-C)") (class "Default")
      (node (ref "E20") (pin "B1") (pinfunction "C_B1") (pintype "input"))
      (node (ref "E20") (pin "D2") (pinfunction "C_D2") (pintype "input"))
      (node (ref "E20") (pin "H1") (pinfunction "C_H1") (pintype "input"))
      (node (ref "E22") (pin "S1") (pinfunction "OUT_S1") (pintype "output"))
    )
    (net (code "1275") (name "Net-(E20A-D)") (class "Default")
      (node (ref "E20") (pin "C1") (pinfunction "D_C1") (pintype "input"))
      (node (ref "F22") (pin "C1") (pinfunction "OUT_C1") (pintype "output"))
    )
    (net (code "1276") (name "Net-(E20A-R)") (class "Default")
      (node (ref "E20") (pin "A1") (pinfunction "R_A1") (pintype "input"))
      (node (ref "E24") (pin "K2") (pinfunction "OUT_K2") (pintype "output"))
    )
    (net (code "1277") (name "Net-(E23A-S)") (class "Default")
      (node (ref "E23") (pin "D1") (pinfunction "S_D1") (pintype "input"))
      (node (ref "F22") (pin "F2") (pinfunction "OUT_F2") (pintype "output"))
    )
    (net (code "1278") (name "Net-(E24A-OUT)") (class "Default")
      (node (ref "E24") (pin "C1") (pinfunction "OUT_C1") (pintype "output"))
      (node (ref "E25") (pin "A1") (pinfunction "IN1_A1") (pintype "input"))
    )
    (net (code "1279") (name "Net-(E24B-OUT)") (class "Default")
      (node (ref "E24") (pin "F1") (pinfunction "OUT_F1") (pintype "output"))
      (node (ref "F23") (pin "E2") (pinfunction "IN2_E2") (pintype "input"))
    )
    (net (code "1280") (name "Net-(E24F-IN1)") (class "Default")
      (node (ref "E24") (pin "H1") (pinfunction "IN1_H1") (pintype "input"))
      (node (ref "E25") (pin "J1") (pinfunction "OUT_J1") (pintype "output"))
    )
    (net (code "1281") (name "Net-(E24H-OUT)") (class "Default")
      (node (ref "E24") (pin "N1") (pinfunction "OUT_N1") (pintype "output"))
      (node (ref "E25") (pin "K1") (pinfunction "IN1_K1") (pintype "input"))
    )
    (net (code "1282") (name "Net-(E24I-IN1)") (class "Default")
      (node (ref "E24") (pin "L2") (pinfunction "IN1_L2") (pintype "input"))
      (node (ref "F24") (pin "P2") (pinfunction "OUT_P2") (pintype "output"))
    )
    (net (code "1283") (name "Net-(E24I-OUT)") (class "Default")
      (node (ref "E24") (pin "N2") (pinfunction "OUT_N2") (pintype "output"))
      (node (ref "F23") (pin "A1") (pinfunction "IN1_A1") (pintype "input"))
    )
    (net (code "1284") (name "Net-(E24J-IN2)") (class "Default")
      (node (ref "E24") (pin "R1") (pinfunction "IN2_R1") (pintype "input"))
      (node (ref "F24") (pin "S1") (pinfunction "OUT_S1") (pintype "output"))
    )
    (net (code "1285") (name "Net-(E24K-IN2)") (class "Default")
      (node (ref "E24") (pin "R2") (pinfunction "IN2_R2") (pintype "input"))
      (node (ref "F24") (pin "V2") (pinfunction "OUT_V2") (pintype "output"))
    )
    (net (code "1286") (name "Net-(E24N-OUT)") (class "Default")
      (node (ref "E24") (pin "V2") (pinfunction "OUT_V2") (pintype "output"))
      (node (ref "E25") (pin "M1") (pinfunction "IN3_M1") (pintype "input"))
    )
    (net (code "1287") (name "Net-(E25G-IN2)") (class "Default")
      (node (ref "E25") (pin "L1") (pinfunction "IN2_L1") (pintype "input"))
      (node (ref "F23") (pin "E1") (pinfunction "OUT_E1") (pintype "output"))
    )
    (net (code "1288") (name "Net-(E25G-OUT)") (class "Default")
      (node (ref "E25") (pin "N1") (pinfunction "OUT_N1") (pintype "output"))
      (node (ref "E25") (pin "P2") (pinfunction "IN2_P2") (pintype "input"))
    )
    (net (code "1289") (name "Net-(E25H-OUT)") (class "Default")
      (node (ref "E25") (pin "S2") (pinfunction "OUT_S2") (pintype "output"))
      (node (ref "E28") (pin "N2") (pinfunction "IN4A_N2") (pintype "input"))
      (node (ref "F25") (pin "L2") (pinfunction "IN1_L2") (pintype "input"))
    )
    (net (code "1290") (name "Net-(E25I-IN1)") (class "Default")
      (node (ref "E25") (pin "P1") (pinfunction "IN1_P1") (pintype "input"))
      (node (ref "E25") (pin "V1") (pinfunction "OUT_V1") (pintype "output"))
    )
    (net (code "1291") (name "Net-(E25I-IN3)") (class "Default")
      (node (ref "E25") (pin "S1") (pinfunction "IN3_S1") (pintype "input"))
      (node (ref "F25") (pin "V2") (pinfunction "OUT_V2") (pintype "output"))
    )
    (net (code "1292") (name "Net-(E26C-OUT)") (class "Default")
      (node (ref "E26") (pin "R1") (pinfunction "OUT_R1") (pintype "output"))
      (node (ref "E32") (pin "F2") (pinfunction "IN3_F2") (pintype "input"))
    )
    (net (code "1293") (name "Net-(E26D-IN1C)") (class "Default")
      (node (ref "E26") (pin "F2") (pinfunction "IN1C_F2") (pintype "input"))
      (node (ref "F26") (pin "V1") (pinfunction "OUT_V1") (pintype "output"))
    )
    (net (code "1294") (name "Net-(E26D-OUT)") (class "Default")
      (node (ref "E26") (pin "T2") (pinfunction "OUT_T2") (pintype "output"))
      (node (ref "E32") (pin "L2") (pinfunction "IN2_L2") (pintype "input"))
    )
    (net (code "1295") (name "Net-(E27C-IN4A)") (class "Default")
      (node (ref "E27") (pin "K1") (pinfunction "IN4A_K1") (pintype "input"))
      (node (ref "F11") (pin "S1") (pinfunction "OUT_S1") (pintype "output"))
    )
    (net (code "1296") (name "Net-(E27C-OUT)") (class "Default")
      (node (ref "E27") (pin "R1") (pinfunction "OUT_R1") (pintype "output"))
      (node (ref "F27") (pin "L2") (pinfunction "IN2_L2") (pintype "input"))
    )
    (net (code "1297") (name "Net-(E27D-OUT)") (class "Default")
      (node (ref "E27") (pin "T2") (pinfunction "OUT_T2") (pintype "output"))
      (node (ref "F27") (pin "M2") (pinfunction "IN3_M2") (pintype "input"))
    )
    (net (code "1298") (name "Net-(E28D-IN3A)") (class "Default")
      (node (ref "E28") (pin "L2") (pinfunction "IN3A_L2") (pintype "input"))
      (node (ref "F25") (pin "N2") (pinfunction "OUT_N2") (pintype "output"))
    )
    (net (code "1299") (name "Net-(E29C-IN2B)") (class "Default")
      (node (ref "E29") (pin "F1") (pinfunction "IN2B_F1") (pintype "input"))
      (node (ref "E29") (pin "T2") (pinfunction "OUT_T2") (pintype "output"))
    )
    (net (code "1300") (name "Net-(E29C-OUT)") (class "Default")
      (node (ref "E29") (pin "R1") (pinfunction "OUT_R1") (pintype "output"))
      (node (ref "F31") (pin "B1") (pinfunction "IN2_B1") (pintype "input"))
    )
    (net (code "1301") (name "Net-(E30C-OUT)") (class "Default")
      (node (ref "E30") (pin "R1") (pinfunction "OUT_R1") (pintype "output"))
      (node (ref "F31") (pin "H1") (pinfunction "IN2_H1") (pintype "input"))
      (node (ref "F31") (pin "K2") (pinfunction "IN1_K2") (pintype "input"))
    )
    (net (code "1302") (name "Net-(E30D-IN3B)") (class "Default")
      (node (ref "E30") (pin "M2") (pinfunction "IN3B_M2") (pintype "input"))
      (node (ref "E30") (pin "V2") (pinfunction "OUT_V2") (pintype "output"))
    )
    (net (code "1303") (name "Net-(E30D-OUT)") (class "Default")
      (node (ref "E30") (pin "T2") (pinfunction "OUT_T2") (pintype "output"))
      (node (ref "E32") (pin "N1") (pinfunction "IN2_N1") (pintype "input"))
    )
    (net (code "1304") (name "Net-(E31A-IN1)") (class "Default")
      (node (ref "E31") (pin "A1") (pinfunction "IN1_A1") (pintype "input"))
      (node (ref "F26") (pin "H2") (pinfunction "OUT_H2") (pintype "output"))
    )
    (net (code "1305") (name "Net-(E31D-IN4)") (class "Default")
      (node (ref "E31") (pin "H2") (pinfunction "IN4_H2") (pintype "input"))
      (node (ref "F26") (pin "D1") (pinfunction "OUT_D1") (pintype "output"))
    )
    (net (code "1306") (name "Net-(E31E-IN3)") (class "Default")
      (node (ref "E31") (pin "J1") (pinfunction "IN3_J1") (pintype "input"))
      (node (ref "F26") (pin "J1") (pinfunction "OUT_J1") (pintype "output"))
    )
    (net (code "1307") (name "Net-(E31F-IN3)") (class "Default")
      (node (ref "E31") (pin "M2") (pinfunction "IN3_M2") (pintype "input"))
      (node (ref "F26") (pin "M2") (pinfunction "OUT_M2") (pintype "output"))
    )
    (net (code "1308") (name "Net-(E31G-IN1)") (class "Default")
      (node (ref "E31") (pin "M1") (pinfunction "IN1_M1") (pintype "input"))
      (node (ref "F26") (pin "N1") (pinfunction "OUT_N1") (pintype "output"))
    )
    (net (code "1309") (name "Net-(E31G-IN2)") (class "Default")
      (node (ref "E31") (pin "N1") (pinfunction "IN2_N1") (pintype "input"))
      (node (ref "F24") (pin "E1") (pinfunction "OUT_E1") (pintype "output"))
    )
    (net (code "1310") (name "Net-(E32A-IN1)") (class "Default")
      (node (ref "E32") (pin "A1") (pinfunction "IN1_A1") (pintype "input"))
      (node (ref "F32") (pin "F1") (pinfunction "OUT_F1") (pintype "output"))
    )
    (net (code "1311") (name "Net-(E32A-IN4)") (class "Default")
      (node (ref "E32") (pin "D1") (pinfunction "IN4_D1") (pintype "input"))
      (node (ref "F32") (pin "F2") (pinfunction "OUT_F2") (pintype "output"))
    )
    (net (code "1312") (name "Net-(E32D-IN2)") (class "Default")
      (node (ref "E32") (pin "E2") (pinfunction "IN2_E2") (pintype "input"))
      (node (ref "F32") (pin "N2") (pinfunction "OUT_N2") (pintype "output"))
    )
    (net (code "1313") (name "Net-(E32D-IN4)") (class "Default")
      (node (ref "E32") (pin "H2") (pinfunction "IN4_H2") (pintype "input"))
      (node (ref "F26") (pin "S2") (pinfunction "OUT_S2") (pintype "output"))
    )
    (net (code "1314") (name "Net-(E32E-IN4)") (class "Default")
      (node (ref "E32") (pin "K1") (pinfunction "IN4_K1") (pintype "input"))
      (node (ref "F32") (pin "K1") (pinfunction "OUT_K1") (pintype "output"))
    )
    (net (code "1315") (name "Net-(E32J-IN3)") (class "Default")
      (node (ref "E32") (pin "T2") (pinfunction "IN3_T2") (pintype "input"))
      (node (ref "F32") (pin "K2") (pinfunction "OUT_K2") (pintype "output"))
    )
    (net (code "1316") (name "Net-(E33A-S)") (class "Default")
      (node (ref "E33") (pin "D1") (pinfunction "S_D1") (pintype "input"))
      (node (ref "F20") (pin "C1") (pinfunction "OUT_C1") (pintype "output"))
    )
    (net (code "1317") (name "Net-(E33D-D)") (class "Default")
      (node (ref "E33") (pin "E2") (pinfunction "D_E2") (pintype "input"))
      (node (ref "F21") (pin "C1") (pinfunction "OUT_C1") (pintype "output"))
    )
    (net (code "1318") (name "Net-(E33E-D)") (class "Default")
      (node (ref "E33") (pin "J1") (pinfunction "D_J1") (pintype "input"))
      (node (ref "F11") (pin "V2") (pinfunction "OUT_V2") (pintype "output"))
    )
    (net (code "1319") (name "Net-(E33F-C)") (class "Default")
      (node (ref "E33") (pin "L2") (pinfunction "C_L2") (pintype "input"))
      (node (ref "F21") (pin "F2") (pinfunction "OUT_F2") (pintype "output"))
    )
    (net (code "1320") (name "Net-(E33G-C)") (class "Default")
      (node (ref "E33") (pin "N1") (pinfunction "C_N1") (pintype "input"))
      (node (ref "F21") (pin "K2") (pinfunction "OUT_K2") (pintype "output"))
    )
    (net (code "1321") (name "Net-(E33H-D)") (class "Default")
      (node (ref "E33") (pin "T2") (pinfunction "D_T2") (pintype "input"))
      (node (ref "F33") (pin "R1") (pinfunction "OUT_R1") (pintype "output"))
    )
    (net (code "1322") (name "Net-(EF10C-CS2)") (class "Default")
      (node (ref "EF10") (pin "AS2") (pinfunction "CS2_AS2") (pintype "input"))
      (node (ref "F19") (pin "J2") (pinfunction "OUT_J2") (pintype "output"))
    )
    (net (code "1323") (name "Net-(EF34-PadBJ1)") (class "Default")
      (node (ref "EF34") (pin "BJ1") (pinfunction "BJ1_BJ1") (pintype "input"))
      (node (ref "EF35") (pin "BK2") (pinfunction "BK2_BK2") (pintype "output"))
    )
    (net (code "1324") (name "Net-(EF35-PadBJ1)") (class "Default")
      (node (ref "EF35") (pin "BJ1") (pinfunction "BJ1_BJ1") (pintype "input"))
      (node (ref "EF36") (pin "BK2") (pinfunction "BK2_BK2") (pintype "output"))
    )
    (net (code "1325") (name "Net-(EF37-PadBJ1)") (class "Default")
      (node (ref "EF37") (pin "BJ1") (pinfunction "BJ1_BJ1") (pintype "input"))
      (node (ref "EF38") (pin "BK2") (pinfunction "BK2_BK2") (pintype "output"))
    )
    (net (code "1326") (name "Net-(EF38-PadBJ1)") (class "Default")
      (node (ref "EF38") (pin "BJ1") (pinfunction "BJ1_BJ1") (pintype "input"))
      (node (ref "EF39") (pin "BK2") (pinfunction "BK2_BK2") (pintype "output"))
    )
    (net (code "1327") (name "Net-(F11F-IN3)") (class "Default")
      (node (ref "F11") (pin "M2") (pinfunction "IN3_M2") (pintype "input"))
      (node (ref "F27") (pin "E1") (pinfunction "OUT_E1") (pintype "output"))
      (node (ref "F31") (pin "E2") (pinfunction "IN2_E2") (pintype "input"))
    )
    (net (code "1328") (name "Net-(F11F-IN4)") (class "Default")
      (node (ref "F11") (pin "N2") (pinfunction "IN4_N2") (pintype "input"))
      (node (ref "F27") (pin "J2") (pinfunction "OUT_J2") (pintype "output"))
      (node (ref "F31") (pin "H2") (pinfunction "IN4_H2") (pintype "input"))
    )
    (net (code "1329") (name "Net-(F12A-IN)") (class "Default")
      (node (ref "F12") (pin "E1") (pinfunction "IN_E1") (pintype "input"))
      (node (ref "F12") (pin "T2") (pinfunction "T2_T2") (pintype "output"))
    )
    (net (code "1330") (name "Net-(F13A-IN)") (class "Default")
      (node (ref "F13") (pin "E1") (pinfunction "IN_E1") (pintype "input"))
      (node (ref "F13") (pin "T2") (pinfunction "T2_T2") (pintype "output"))
    )
    (net (code "1331") (name "Net-(F13A-OUT)") (class "Default")
      (node (ref "F13") (pin "F1") (pinfunction "OUT_F1") (pintype "output"))
      (node (ref "F14") (pin "H2") (pinfunction "H2_H2") (pintype "input"))
    )
    (net (code "1332") (name "Net-(F13E-IN)") (class "Default")
      (node (ref "F13") (pin "H1") (pinfunction "IN_H1") (pintype "input"))
      (node (ref "F13") (pin "M2") (pinfunction "M2_M2") (pintype "output"))
    )
    (net (code "1333") (name "Net-(F13E-OUT)") (class "Default")
      (node (ref "F13") (pin "J1") (pinfunction "OUT_J1") (pintype "output"))
      (node (ref "F20") (pin "D2") (pinfunction "IN1_D2") (pintype "input"))
    )
    (net (code "1334") (name "Net-(F14A-IN)") (class "Default")
      (node (ref "F14") (pin "E1") (pinfunction "IN_E1") (pintype "input"))
      (node (ref "F14") (pin "T2") (pinfunction "T2_T2") (pintype "output"))
    )
    (net (code "1335") (name "Net-(F14A-OUT)") (class "Default")
      (node (ref "F14") (pin "F1") (pinfunction "OUT_F1") (pintype "output"))
      (node (ref "F15") (pin "H2") (pinfunction "H2_H2") (pintype "input"))
    )
    (net (code "1336") (name "Net-(F14E-IN)") (class "Default")
      (node (ref "F14") (pin "H1") (pinfunction "IN_H1") (pintype "input"))
      (node (ref "F14") (pin "S2") (pinfunction "S2_S2") (pintype "output"))
    )
    (net (code "1337") (name "Net-(F15A-IN)") (class "Default")
      (node (ref "F15") (pin "E1") (pinfunction "IN_E1") (pintype "input"))
      (node (ref "F15") (pin "T2") (pinfunction "T2_T2") (pintype "output"))
    )
    (net (code "1338") (name "Net-(F15E-IN)") (class "Default")
      (node (ref "F15") (pin "H1") (pinfunction "IN_H1") (pintype "input"))
      (node (ref "F15") (pin "M2") (pinfunction "M2_M2") (pintype "output"))
    )
    (net (code "1339") (name "Net-(F15E-OUT)") (class "Default")
      (node (ref "F15") (pin "J1") (pinfunction "OUT_J1") (pintype "output"))
      (node (ref "F20") (pin "H1") (pinfunction "IN1_H1") (pintype "input"))
    )
    (net (code "1340") (name "Net-(F16A-IN)") (class "Default")
      (node (ref "F16") (pin "E1") (pinfunction "IN_E1") (pintype "input"))
      (node (ref "F16") (pin "T2") (pinfunction "T2_T2") (pintype "output"))
    )
    (net (code "1341") (name "Net-(F16A-OUT)") (class "Default")
      (node (ref "F16") (pin "F1") (pinfunction "OUT_F1") (pintype "output"))
      (node (ref "F17") (pin "H2") (pinfunction "H2_H2") (pintype "input"))
    )
    (net (code "1342") (name "Net-(F16E-IN)") (class "Default")
      (node (ref "F16") (pin "H1") (pinfunction "IN_H1") (pintype "input"))
      (node (ref "F16") (pin "S2") (pinfunction "S2_S2") (pintype "output"))
    )
    (net (code "1343") (name "Net-(F17A-IN)") (class "Default")
      (node (ref "F17") (pin "E1") (pinfunction "IN_E1") (pintype "input"))
      (node (ref "F17") (pin "T2") (pinfunction "T2_T2") (pintype "output"))
    )
    (net (code "1344") (name "Net-(F17E-IN)") (class "Default")
      (node (ref "F17") (pin "H1") (pinfunction "IN_H1") (pintype "input"))
      (node (ref "F17") (pin "M2") (pinfunction "M2_M2") (pintype "output"))
    )
    (net (code "1345") (name "Net-(F17E-OUT)") (class "Default")
      (node (ref "F17") (pin "J1") (pinfunction "OUT_J1") (pintype "output"))
      (node (ref "F20") (pin "H2") (pinfunction "IN1_H2") (pintype "input"))
    )
    (net (code "1346") (name "Net-(F18A-IN)") (class "Default")
      (node (ref "F18") (pin "E1") (pinfunction "IN_E1") (pintype "input"))
      (node (ref "F18") (pin "T2") (pinfunction "T2_T2") (pintype "output"))
    )
    (net (code "1347") (name "Net-(F18E-IN)") (class "Default")
      (node (ref "F18") (pin "H1") (pinfunction "IN_H1") (pintype "input"))
      (node (ref "F18") (pin "S2") (pinfunction "S2_S2") (pintype "output"))
    )
    (net (code "1348") (name "Net-(F19A-IN1)") (class "Default")
      (node (ref "F19") (pin "A1") (pinfunction "IN1_A1") (pintype "input"))
      (node (ref "F20") (pin "N1") (pinfunction "OUT_N1") (pintype "output"))
    )
    (net (code "1349") (name "Net-(F19E-IN2)") (class "Default")
      (node (ref "F19") (pin "H1") (pinfunction "IN2_H1") (pintype "input"))
      (node (ref "F21") (pin "N2") (pinfunction "OUT_N2") (pintype "output"))
    )
    (net (code "1350") (name "Net-(F19E-OUT)") (class "Default")
      (node (ref "F19") (pin "L1") (pinfunction "OUT_L1") (pintype "output"))
      (node (ref "F21") (pin "H2") (pinfunction "IN1_H2") (pintype "input"))
    )
    (net (code "1351") (name "Net-(F19J-OUT)") (class "Default")
      (node (ref "F19") (pin "V2") (pinfunction "OUT_V2") (pintype "output"))
      (node (ref "F21") (pin "P1") (pinfunction "IN1_P1") (pintype "input"))
    )
    (net (code "1352") (name "Net-(F20A-IN2)") (class "Default")
      (node (ref "F20") (pin "B1") (pinfunction "IN2_B1") (pintype "input"))
      (node (ref "F20") (pin "F1") (pinfunction "OUT_F1") (pintype "output"))
    )
    (net (code "1353") (name "Net-(F20H-IN1)") (class "Default")
      (node (ref "F20") (pin "L1") (pinfunction "IN1_L1") (pintype "input"))
      (node (ref "F20") (pin "S1") (pinfunction "OUT_S1") (pintype "output"))
    )
    (net (code "1354") (name "Net-(F20I-OUT)") (class "Default")
      (node (ref "F20") (pin "N2") (pinfunction "OUT_N2") (pintype "output"))
      (node (ref "F30") (pin "A1") (pinfunction "IN1_A1") (pintype "input"))
    )
    (net (code "1355") (name "Net-(F20K-IN1)") (class "Default")
      (node (ref "F20") (pin "P2") (pinfunction "IN1_P2") (pintype "input"))
      (node (ref "F20") (pin "V2") (pinfunction "OUT_V2") (pintype "output"))
    )
    (net (code "1356") (name "Net-(F21C-IN1)") (class "Default")
      (node (ref "F21") (pin "D2") (pinfunction "IN1_D2") (pintype "input"))
      (node (ref "F21") (pin "K1") (pinfunction "OUT_K1") (pintype "output"))
    )
    (net (code "1357") (name "Net-(F21K-IN2)") (class "Default")
      (node (ref "F21") (pin "R2") (pinfunction "IN2_R2") (pintype "input"))
      (node (ref "F23") (pin "V2") (pinfunction "OUT_V2") (pintype "output"))
    )
    (net (code "1358") (name "Net-(F22J-OUT)") (class "Default")
      (node (ref "F22") (pin "P2") (pinfunction "IN1_P2") (pintype "input"))
      (node (ref "F22") (pin "S1") (pinfunction "OUT_S1") (pintype "output"))
    )
    (net (code "1359") (name "Net-(F23D-IN3)") (class "Default")
      (node (ref "F23") (pin "F2") (pinfunction "IN3_F2") (pintype "input"))
      (node (ref "F23") (pin "L1") (pinfunction "OUT_L1") (pintype "output"))
    )
    (net (code "1360") (name "Net-(F24D-OUT)") (class "Default")
      (node (ref "F24") (pin "J2") (pinfunction "OUT_J2") (pintype "output"))
      (node (ref "F25") (pin "D2") (pinfunction "IN1_D2") (pintype "input"))
    )
    (net (code "1361") (name "Net-(F24E-OUT)") (class "Default")
      (node (ref "F24") (pin "L1") (pinfunction "OUT_L1") (pintype "output"))
      (node (ref "F25") (pin "H1") (pinfunction "IN1_H1") (pintype "input"))
    )
    (net (code "1362") (name "Net-(F25C-OUT)") (class "Default")
      (node (ref "F25") (pin "F2") (pinfunction "OUT_F2") (pintype "output"))
      (node (ref "F27") (pin "M1") (pinfunction "IN1_M1") (pintype "input"))
    )
    (net (code "1363") (name "Net-(F25F-OUT)") (class "Default")
      (node (ref "F25") (pin "K1") (pinfunction "OUT_K1") (pintype "output"))
      (node (ref "F27") (pin "N1") (pinfunction "IN2_N1") (pintype "input"))
    )
    (net (code "1364") (name "Net-(F25G-IN1)") (class "Default")
      (node (ref "F25") (pin "H2") (pinfunction "IN1_H2") (pintype "input"))
      (node (ref "F25") (pin "N1") (pinfunction "OUT_N1") (pintype "output"))
    )
    (net (code "1365") (name "Net-(F25G-OUT)") (class "Default")
      (node (ref "F25") (pin "K2") (pinfunction "OUT_K2") (pintype "output"))
      (node (ref "F27") (pin "P1") (pinfunction "IN3_P1") (pintype "input"))
    )
    (net (code "1366") (name "Net-(F27D-IN2)") (class "Default")
      (node (ref "F27") (pin "E2") (pinfunction "IN2_E2") (pintype "input"))
      (node (ref "F29") (pin "F1") (pinfunction "OUT_F1") (pintype "output"))
    )
    (net (code "1367") (name "Net-(F27E-OUT)") (class "Default")
      (node (ref "F27") (pin "L1") (pinfunction "OUT_L1") (pintype "output"))
      (node (ref "F29") (pin "J1") (pinfunction "IN2_J1") (pintype "input"))
    )
    (net (code "1368") (name "Net-(F27F-OUT)") (class "Default")
      (node (ref "F27") (pin "P2") (pinfunction "OUT_P2") (pintype "output"))
      (node (ref "F32") (pin "A1") (pinfunction "IN1_A1") (pintype "input"))
    )
    (net (code "1369") (name "Net-(F28D-OUT)") (class "Default")
      (node (ref "F28") (pin "H2") (pinfunction "OUT_H2") (pintype "output"))
      (node (ref "F31") (pin "F1") (pinfunction "IN1_F1") (pintype "input"))
    )
    (net (code "1370") (name "Net-(F28F-OUT)") (class "Default")
      (node (ref "F28") (pin "M2") (pinfunction "OUT_M2") (pintype "output"))
      (node (ref "F32") (pin "M1") (pinfunction "IN2_M1") (pintype "input"))
    )
    (net (code "1371") (name "Net-(F28G-OUT)") (class "Default")
      (node (ref "F28") (pin "N1") (pinfunction "OUT_N1") (pintype "output"))
      (node (ref "F30") (pin "F1") (pinfunction "IN1_F1") (pintype "input"))
    )
    (net (code "1372") (name "Net-(F28I-OUT)") (class "Default")
      (node (ref "F28") (pin "U1") (pinfunction "OUT_U1") (pintype "output"))
      (node (ref "F33") (pin "A1") (pinfunction "IN1A_A1") (pintype "input"))
    )
    (net (code "1373") (name "Net-(F29H-OUT)") (class "Default")
      (node (ref "F29") (pin "N1") (pinfunction "OUT_N1") (pintype "output"))
      (node (ref "F30") (pin "K2") (pinfunction "IN1_K2") (pintype "input"))
    )
    (net (code "1374") (name "Net-(F29I-IN1)") (class "Default")
      (node (ref "F29") (pin "L2") (pinfunction "IN1_L2") (pintype "input"))
      (node (ref "F29") (pin "V2") (pinfunction "OUT_V2") (pintype "output"))
    )
    (net (code "1375") (name "Net-(F29J-OUT)") (class "Default")
      (node (ref "F29") (pin "S1") (pinfunction "OUT_S1") (pintype "output"))
      (node (ref "F30") (pin "M1") (pinfunction "IN1_M1") (pintype "input"))
    )
    (net (code "1376") (name "Net-(F32K-IN2)") (class "Default")
      (node (ref "F32") (pin "R2") (pinfunction "IN2_R2") (pintype "input"))
      (node (ref "F33") (pin "S1") (pinfunction "IN1A_S1") (pintype "input"))
      (node (ref "F33") (pin "T2") (pinfunction "OUT_T2") (pintype "output"))
    )
    (net (code "1377") (name "Net-(F32K-OUT)") (class "Default")
      (node (ref "F32") (pin "S2") (pinfunction "OUT_S2") (pintype "output"))
      (node (ref "F33") (pin "V1") (pinfunction "IN2A_V1") (pintype "input"))
    )
    (net (code "1378") (name "Net-(H07A-OUT)") (class "Default")
      (node (ref "H07") (pin "D2") (pinfunction "OUT_D2") (pintype "output"))
      (node (ref "J01") (pin "D2") (pinfunction "P$2_D2") (pintype "bidirectional"))
    )
    (net (code "1379") (name "Net-(H07B-OUT)") (class "Default")
      (node (ref "H07") (pin "K2") (pinfunction "OUT_K2") (pintype "output"))
      (node (ref "J01") (pin "E2") (pinfunction "P$2_E2") (pintype "bidirectional"))
    )
    (net (code "1380") (name "Net-(H07C-OUT)") (class "Default")
      (node (ref "H07") (pin "S2") (pinfunction "OUT_S2") (pintype "output"))
      (node (ref "J01") (pin "H2") (pinfunction "P$2_H2") (pintype "bidirectional"))
    )
    (net (code "1381") (name "Net-(H08A-OUT)") (class "Default")
      (node (ref "H08") (pin "D2") (pinfunction "OUT_D2") (pintype "output"))
      (node (ref "J01") (pin "K2") (pinfunction "P$2_K2") (pintype "bidirectional"))
    )
    (net (code "1382") (name "Net-(H08B-OUT)") (class "Default")
      (node (ref "H08") (pin "K2") (pinfunction "OUT_K2") (pintype "output"))
      (node (ref "J01") (pin "M2") (pinfunction "P$2_M2") (pintype "bidirectional"))
    )
    (net (code "1383") (name "Net-(H08C-OUT)") (class "Default")
      (node (ref "H08") (pin "S2") (pinfunction "OUT_S2") (pintype "output"))
      (node (ref "J01") (pin "P2") (pinfunction "P$2_P2") (pintype "bidirectional"))
    )
    (net (code "1384") (name "Net-(H09A-OUT)") (class "Default")
      (node (ref "H09") (pin "D2") (pinfunction "OUT_D2") (pintype "output"))
      (node (ref "J01") (pin "S2") (pinfunction "P$2_S2") (pintype "bidirectional"))
    )
    (net (code "1385") (name "Net-(H09B-OUT)") (class "Default")
      (node (ref "H09") (pin "K2") (pinfunction "OUT_K2") (pintype "output"))
      (node (ref "J01") (pin "T2") (pinfunction "P$2_T2") (pintype "bidirectional"))
    )
    (net (code "1386") (name "Net-(H09C-OUT)") (class "Default")
      (node (ref "H09") (pin "S2") (pinfunction "OUT_S2") (pintype "output"))
      (node (ref "J01") (pin "V2") (pinfunction "P$2_V2") (pintype "bidirectional"))
    )
    (net (code "1387") (name "Net-(H10A-OUT)") (class "Default")
      (node (ref "H10") (pin "D2") (pinfunction "OUT_D2") (pintype "output"))
      (node (ref "J02") (pin "D2") (pinfunction "P$2_D2") (pintype "bidirectional"))
    )
    (net (code "1388") (name "Net-(H10B-OUT)") (class "Default")
      (node (ref "H10") (pin "K2") (pinfunction "OUT_K2") (pintype "output"))
      (node (ref "J02") (pin "E2") (pinfunction "P$2_E2") (pintype "bidirectional"))
    )
    (net (code "1389") (name "Net-(H10C-OUT)") (class "Default")
      (node (ref "H10") (pin "S2") (pinfunction "OUT_S2") (pintype "output"))
      (node (ref "J02") (pin "H2") (pinfunction "P$2_H2") (pintype "bidirectional"))
    )
    (net (code "1390") (name "Net-(H11A-OUT)") (class "Default")
      (node (ref "H11") (pin "D2") (pinfunction "OUT_D2") (pintype "output"))
      (node (ref "J02") (pin "K2") (pinfunction "P$2_K2") (pintype "bidirectional"))
    )
    (net (code "1391") (name "Net-(H11B-OUT)") (class "Default")
      (node (ref "H11") (pin "K2") (pinfunction "OUT_K2") (pintype "output"))
      (node (ref "J02") (pin "M2") (pinfunction "P$2_M2") (pintype "bidirectional"))
    )
    (net (code "1392") (name "Net-(H11C-OUT)") (class "Default")
      (node (ref "H11") (pin "S2") (pinfunction "OUT_S2") (pintype "output"))
      (node (ref "J02") (pin "P2") (pinfunction "P$2_P2") (pintype "bidirectional"))
    )
    (net (code "1393") (name "Net-(H12A-OUT)") (class "Default")
      (node (ref "H12") (pin "D2") (pinfunction "OUT_D2") (pintype "output"))
      (node (ref "J02") (pin "S2") (pinfunction "P$2_S2") (pintype "bidirectional"))
    )
    (net (code "1394") (name "Net-(H12B-OUT)") (class "Default")
      (node (ref "H12") (pin "K2") (pinfunction "OUT_K2") (pintype "output"))
      (node (ref "J02") (pin "T2") (pinfunction "P$2_T2") (pintype "bidirectional"))
    )
    (net (code "1395") (name "Net-(H12C-OUT)") (class "Default")
      (node (ref "H12") (pin "S2") (pinfunction "OUT_S2") (pintype "output"))
      (node (ref "J02") (pin "V2") (pinfunction "P$2_V2") (pintype "bidirectional"))
    )
    (net (code "1396") (name "Net-(H13A-OUT)") (class "Default")
      (node (ref "H13") (pin "D2") (pinfunction "OUT_D2") (pintype "output"))
      (node (ref "J03") (pin "D2") (pinfunction "P$2_D2") (pintype "bidirectional"))
    )
    (net (code "1397") (name "Net-(H13B-OUT)") (class "Default")
      (node (ref "H13") (pin "K2") (pinfunction "OUT_K2") (pintype "output"))
      (node (ref "J03") (pin "E2") (pinfunction "P$2_E2") (pintype "bidirectional"))
    )
    (net (code "1398") (name "Net-(H13C-OUT)") (class "Default")
      (node (ref "H13") (pin "S2") (pinfunction "OUT_S2") (pintype "output"))
      (node (ref "J03") (pin "H2") (pinfunction "P$2_H2") (pintype "bidirectional"))
    )
    (net (code "1399") (name "Net-(H14A-OUT)") (class "Default")
      (node (ref "H14") (pin "D2") (pinfunction "OUT_D2") (pintype "output"))
      (node (ref "J03") (pin "K2") (pinfunction "P$2_K2") (pintype "bidirectional"))
    )
    (net (code "1400") (name "Net-(H14B-OUT)") (class "Default")
      (node (ref "H14") (pin "K2") (pinfunction "OUT_K2") (pintype "output"))
      (node (ref "J03") (pin "M2") (pinfunction "P$2_M2") (pintype "bidirectional"))
    )
    (net (code "1401") (name "Net-(H14C-OUT)") (class "Default")
      (node (ref "H14") (pin "S2") (pinfunction "OUT_S2") (pintype "output"))
      (node (ref "J03") (pin "P2") (pinfunction "P$2_P2") (pintype "bidirectional"))
    )
    (net (code "1402") (name "Net-(H15A-OUT)") (class "Default")
      (node (ref "H15") (pin "D2") (pinfunction "OUT_D2") (pintype "output"))
      (node (ref "J03") (pin "S2") (pinfunction "P$2_S2") (pintype "bidirectional"))
    )
    (net (code "1403") (name "Net-(H15B-OUT)") (class "Default")
      (node (ref "H15") (pin "K2") (pinfunction "OUT_K2") (pintype "output"))
      (node (ref "J03") (pin "T2") (pinfunction "P$2_T2") (pintype "bidirectional"))
    )
    (net (code "1404") (name "Net-(H15C-OUT)") (class "Default")
      (node (ref "H15") (pin "S2") (pinfunction "OUT_S2") (pintype "output"))
      (node (ref "J03") (pin "V2") (pinfunction "P$2_V2") (pintype "bidirectional"))
    )
    (net (code "1405") (name "Net-(H16A-OUT)") (class "Default")
      (node (ref "H16") (pin "D2") (pinfunction "OUT_D2") (pintype "output"))
      (node (ref "J04") (pin "D2") (pinfunction "P$2_D2") (pintype "bidirectional"))
    )
    (net (code "1406") (name "Net-(H16B-OUT)") (class "Default")
      (node (ref "H16") (pin "K2") (pinfunction "OUT_K2") (pintype "output"))
      (node (ref "J04") (pin "E2") (pinfunction "P$2_E2") (pintype "bidirectional"))
    )
    (net (code "1407") (name "Net-(H16C-OUT)") (class "Default")
      (node (ref "H16") (pin "S2") (pinfunction "OUT_S2") (pintype "output"))
      (node (ref "J04") (pin "H2") (pinfunction "P$2_H2") (pintype "bidirectional"))
    )
    (net (code "1408") (name "Net-(H17A-OUT)") (class "Default")
      (node (ref "H17") (pin "D2") (pinfunction "OUT_D2") (pintype "output"))
      (node (ref "J04") (pin "K2") (pinfunction "P$2_K2") (pintype "bidirectional"))
    )
    (net (code "1409") (name "Net-(H17B-OUT)") (class "Default")
      (node (ref "H17") (pin "K2") (pinfunction "OUT_K2") (pintype "output"))
      (node (ref "J04") (pin "M2") (pinfunction "P$2_M2") (pintype "bidirectional"))
    )
    (net (code "1410") (name "Net-(H17C-OUT)") (class "Default")
      (node (ref "H17") (pin "S2") (pinfunction "OUT_S2") (pintype "output"))
      (node (ref "J04") (pin "P2") (pinfunction "P$2_P2") (pintype "bidirectional"))
    )
    (net (code "1411") (name "Net-(H18A-OUT)") (class "Default")
      (node (ref "H18") (pin "D2") (pinfunction "OUT_D2") (pintype "output"))
      (node (ref "J04") (pin "S2") (pinfunction "P$2_S2") (pintype "bidirectional"))
    )
    (net (code "1412") (name "Net-(H18B-OUT)") (class "Default")
      (node (ref "H18") (pin "K2") (pinfunction "OUT_K2") (pintype "output"))
      (node (ref "J04") (pin "T2") (pinfunction "P$2_T2") (pintype "bidirectional"))
    )
    (net (code "1413") (name "Net-(H18C-OUT)") (class "Default")
      (node (ref "H18") (pin "S2") (pinfunction "OUT_S2") (pintype "output"))
      (node (ref "J04") (pin "V2") (pinfunction "P$2_V2") (pintype "bidirectional"))
    )
    (net (code "1414") (name "Net-(H19A-OUT)") (class "Default")
      (node (ref "H19") (pin "D2") (pinfunction "OUT_D2") (pintype "output"))
      (node (ref "J06") (pin "S2") (pinfunction "P$2_S2") (pintype "bidirectional"))
    )
    (net (code "1415") (name "Net-(H19B-OUT)") (class "Default")
      (node (ref "H19") (pin "K2") (pinfunction "OUT_K2") (pintype "output"))
      (node (ref "J06") (pin "T2") (pinfunction "P$2_T2") (pintype "bidirectional"))
    )
    (net (code "1416") (name "Net-(H19C-OUT)") (class "Default")
      (node (ref "H19") (pin "S2") (pinfunction "OUT_S2") (pintype "output"))
      (node (ref "J10") (pin "P2") (pinfunction "P$2_P2") (pintype "bidirectional"))
    )
    (net (code "1417") (name "Net-(H20A-OUT)") (class "Default")
      (node (ref "H20") (pin "D2") (pinfunction "OUT_D2") (pintype "output"))
      (node (ref "J08") (pin "P2") (pinfunction "P$2_P2") (pintype "bidirectional"))
    )
    (net (code "1418") (name "Net-(H20B-OUT)") (class "Default")
      (node (ref "H20") (pin "K2") (pinfunction "OUT_K2") (pintype "output"))
      (node (ref "J08") (pin "S2") (pinfunction "P$2_S2") (pintype "bidirectional"))
    )
    (net (code "1419") (name "Net-(HJ28-PadAU1)") (class "Default")
      (node (ref "HJ28") (pin "AU1") (pinfunction "AU1_AU1") (pintype "input"))
      (node (ref "HJ28") (pin "BV1") (pinfunction "BV1_BV1") (pintype "output"))
    )
    (net (code "1420") (name "Net-(J05A-P$2)") (class "Default")
      (node (ref "J05") (pin "D2") (pinfunction "P$2_D2") (pintype "bidirectional"))
      (node (ref "J13") (pin "A1") (pinfunction "IN_A1") (pintype "input"))
    )
    (net (code "1421") (name "Net-(J05B-P$2)") (class "Default")
      (node (ref "J05") (pin "E2") (pinfunction "P$2_E2") (pintype "bidirectional"))
      (node (ref "J13") (pin "D2") (pinfunction "IN_D2") (pintype "input"))
    )
    (net (code "1422") (name "Net-(J05J-P$2)") (class "Default")
      (node (ref "J05") (pin "H2") (pinfunction "P$2_H2") (pintype "bidirectional"))
      (node (ref "J13") (pin "F1") (pinfunction "IN_F1") (pintype "input"))
    )
    (net (code "1423") (name "Net-(J05K-P$2)") (class "Default")
      (node (ref "J05") (pin "K2") (pinfunction "P$2_K2") (pintype "bidirectional"))
      (node (ref "J13") (pin "K2") (pinfunction "IN_K2") (pintype "input"))
    )
    (net (code "1424") (name "Net-(J05L-P$2)") (class "Default")
      (node (ref "J05") (pin "M2") (pinfunction "P$2_M2") (pintype "bidirectional"))
      (node (ref "J13") (pin "M1") (pinfunction "IN_M1") (pintype "input"))
    )
    (net (code "1425") (name "Net-(J05M-P$2)") (class "Default")
      (node (ref "J05") (pin "P2") (pinfunction "P$2_P2") (pintype "bidirectional"))
      (node (ref "J13") (pin "R2") (pinfunction "IN_R2") (pintype "input"))
    )
    (net (code "1426") (name "Net-(J05N-P$2)") (class "Default")
      (node (ref "J05") (pin "S2") (pinfunction "P$2_S2") (pintype "bidirectional"))
      (node (ref "J14") (pin "A1") (pinfunction "IN_A1") (pintype "input"))
    )
    (net (code "1427") (name "Net-(J05O-P$2)") (class "Default")
      (node (ref "J05") (pin "T2") (pinfunction "P$2_T2") (pintype "bidirectional"))
      (node (ref "J14") (pin "D2") (pinfunction "IN_D2") (pintype "input"))
    )
    (net (code "1428") (name "Net-(J05P-P$2)") (class "Default")
      (node (ref "J05") (pin "V2") (pinfunction "P$2_V2") (pintype "bidirectional"))
      (node (ref "J14") (pin "F1") (pinfunction "IN_F1") (pintype "input"))
    )
    (net (code "1429") (name "Net-(J06A-P$2)") (class "Default")
      (node (ref "J06") (pin "D2") (pinfunction "P$2_D2") (pintype "bidirectional"))
      (node (ref "J14") (pin "K2") (pinfunction "IN_K2") (pintype "input"))
    )
    (net (code "1430") (name "Net-(J06B-P$2)") (class "Default")
      (node (ref "J06") (pin "E2") (pinfunction "P$2_E2") (pintype "bidirectional"))
      (node (ref "J14") (pin "M1") (pinfunction "IN_M1") (pintype "input"))
    )
    (net (code "1431") (name "Net-(J06J-P$2)") (class "Default")
      (node (ref "J06") (pin "H2") (pinfunction "P$2_H2") (pintype "bidirectional"))
      (node (ref "J14") (pin "R2") (pinfunction "IN_R2") (pintype "input"))
    )
    (net (code "1432") (name "Net-(J06K-P$2)") (class "Default")
      (node (ref "J06") (pin "K2") (pinfunction "P$2_K2") (pintype "bidirectional"))
      (node (ref "J15") (pin "A1") (pinfunction "IN_A1") (pintype "input"))
    )
    (net (code "1433") (name "Net-(J06L-P$2)") (class "Default")
      (node (ref "J06") (pin "M2") (pinfunction "P$2_M2") (pintype "bidirectional"))
      (node (ref "J15") (pin "D2") (pinfunction "IN_D2") (pintype "input"))
    )
    (net (code "1434") (name "Net-(J06M-P$2)") (class "Default")
      (node (ref "J06") (pin "P2") (pinfunction "P$2_P2") (pintype "bidirectional"))
      (node (ref "J15") (pin "F1") (pinfunction "IN_F1") (pintype "input"))
    )
    (net (code "1435") (name "Net-(J06P-P$2)") (class "Default")
      (node (ref "J06") (pin "V2") (pinfunction "P$2_V2") (pintype "bidirectional"))
      (node (ref "J15") (pin "K2") (pinfunction "IN_K2") (pintype "input"))
    )
    (net (code "1436") (name "Net-(J07A-P$2)") (class "Default")
      (node (ref "J07") (pin "D2") (pinfunction "P$2_D2") (pintype "bidirectional"))
      (node (ref "J16") (pin "A1") (pinfunction "IN_A1") (pintype "input"))
    )
    (net (code "1437") (name "Net-(J07B-P$2)") (class "Default")
      (node (ref "J07") (pin "E2") (pinfunction "P$2_E2") (pintype "bidirectional"))
      (node (ref "J16") (pin "D2") (pinfunction "IN_D2") (pintype "input"))
    )
    (net (code "1438") (name "Net-(J07J-P$2)") (class "Default")
      (node (ref "J07") (pin "H2") (pinfunction "P$2_H2") (pintype "bidirectional"))
      (node (ref "J16") (pin "F1") (pinfunction "IN_F1") (pintype "input"))
    )
    (net (code "1439") (name "Net-(J07K-P$2)") (class "Default")
      (node (ref "J07") (pin "K2") (pinfunction "P$2_K2") (pintype "bidirectional"))
      (node (ref "J16") (pin "K2") (pinfunction "IN_K2") (pintype "input"))
    )
    (net (code "1440") (name "Net-(J07L-P$2)") (class "Default")
      (node (ref "J07") (pin "M2") (pinfunction "P$2_M2") (pintype "bidirectional"))
      (node (ref "J16") (pin "M1") (pinfunction "IN_M1") (pintype "input"))
    )
    (net (code "1441") (name "Net-(J07M-P$2)") (class "Default")
      (node (ref "J07") (pin "P2") (pinfunction "P$2_P2") (pintype "bidirectional"))
      (node (ref "J16") (pin "R2") (pinfunction "IN_R2") (pintype "input"))
    )
    (net (code "1442") (name "Net-(J07N-P$2)") (class "Default")
      (node (ref "J07") (pin "S2") (pinfunction "P$2_S2") (pintype "bidirectional"))
      (node (ref "J17") (pin "A1") (pinfunction "IN_A1") (pintype "input"))
    )
    (net (code "1443") (name "Net-(J07O-P$2)") (class "Default")
      (node (ref "J07") (pin "T2") (pinfunction "P$2_T2") (pintype "bidirectional"))
      (node (ref "J17") (pin "D2") (pinfunction "IN_D2") (pintype "input"))
    )
    (net (code "1444") (name "Net-(J07P-P$2)") (class "Default")
      (node (ref "J07") (pin "V2") (pinfunction "P$2_V2") (pintype "bidirectional"))
      (node (ref "J17") (pin "F1") (pinfunction "IN_F1") (pintype "input"))
    )
    (net (code "1445") (name "Net-(J08A-P$2)") (class "Default")
      (node (ref "J08") (pin "D2") (pinfunction "P$2_D2") (pintype "bidirectional"))
      (node (ref "J17") (pin "K2") (pinfunction "IN_K2") (pintype "input"))
    )
    (net (code "1446") (name "Net-(J08B-P$2)") (class "Default")
      (node (ref "J08") (pin "E2") (pinfunction "P$2_E2") (pintype "bidirectional"))
      (node (ref "J17") (pin "M1") (pinfunction "IN_M1") (pintype "input"))
    )
    (net (code "1447") (name "Net-(J08J-P$2)") (class "Default")
      (node (ref "J08") (pin "H2") (pinfunction "P$2_H2") (pintype "bidirectional"))
      (node (ref "J17") (pin "R2") (pinfunction "IN_R2") (pintype "input"))
    )
    (net (code "1448") (name "Net-(J08K-P$2)") (class "Default")
      (node (ref "J08") (pin "K2") (pinfunction "P$2_K2") (pintype "bidirectional"))
      (node (ref "J15") (pin "M1") (pinfunction "IN_M1") (pintype "input"))
    )
    (net (code "1449") (name "Net-(J08L-P$2)") (class "Default")
      (node (ref "J08") (pin "M2") (pinfunction "P$2_M2") (pintype "bidirectional"))
      (node (ref "J15") (pin "R2") (pinfunction "IN_R2") (pintype "input"))
    )
    (net (code "1450") (name "Net-(J08O-P$2)") (class "Default")
      (node (ref "J08") (pin "T2") (pinfunction "P$2_T2") (pintype "bidirectional"))
      (node (ref "J20") (pin "A1") (pinfunction "IN_A1") (pintype "input"))
    )
    (net (code "1451") (name "Net-(J09A-P$2)") (class "Default")
      (node (ref "J09") (pin "D2") (pinfunction "P$2_D2") (pintype "bidirectional"))
      (node (ref "J18") (pin "A1") (pinfunction "IN_A1") (pintype "input"))
    )
    (net (code "1452") (name "Net-(J09B-P$2)") (class "Default")
      (node (ref "J09") (pin "E2") (pinfunction "P$2_E2") (pintype "bidirectional"))
      (node (ref "J18") (pin "D2") (pinfunction "IN_D2") (pintype "input"))
    )
    (net (code "1453") (name "Net-(J09J-P$2)") (class "Default")
      (node (ref "J09") (pin "H2") (pinfunction "P$2_H2") (pintype "bidirectional"))
      (node (ref "J18") (pin "F1") (pinfunction "IN_F1") (pintype "input"))
    )
    (net (code "1454") (name "Net-(J09K-P$2)") (class "Default")
      (node (ref "J09") (pin "K2") (pinfunction "P$2_K2") (pintype "bidirectional"))
      (node (ref "J18") (pin "K2") (pinfunction "IN_K2") (pintype "input"))
    )
    (net (code "1455") (name "Net-(J09L-P$2)") (class "Default")
      (node (ref "J09") (pin "M2") (pinfunction "P$2_M2") (pintype "bidirectional"))
      (node (ref "J18") (pin "M1") (pinfunction "IN_M1") (pintype "input"))
    )
    (net (code "1456") (name "Net-(J09M-P$2)") (class "Default")
      (node (ref "J09") (pin "P2") (pinfunction "P$2_P2") (pintype "bidirectional"))
      (node (ref "J18") (pin "R2") (pinfunction "IN_R2") (pintype "input"))
    )
    (net (code "1457") (name "Net-(J09N-P$2)") (class "Default")
      (node (ref "J09") (pin "S2") (pinfunction "P$2_S2") (pintype "bidirectional"))
      (node (ref "J19") (pin "A1") (pinfunction "IN_A1") (pintype "input"))
    )
    (net (code "1458") (name "Net-(J09O-P$2)") (class "Default")
      (node (ref "J09") (pin "T2") (pinfunction "P$2_T2") (pintype "bidirectional"))
      (node (ref "J19") (pin "D2") (pinfunction "IN_D2") (pintype "input"))
    )
    (net (code "1459") (name "Net-(J09P-P$2)") (class "Default")
      (node (ref "J09") (pin "V2") (pinfunction "P$2_V2") (pintype "bidirectional"))
      (node (ref "J19") (pin "F1") (pinfunction "IN_F1") (pintype "input"))
    )
    (net (code "1460") (name "Net-(J10A-P$2)") (class "Default")
      (node (ref "J10") (pin "D2") (pinfunction "P$2_D2") (pintype "bidirectional"))
      (node (ref "J19") (pin "K2") (pinfunction "IN_K2") (pintype "input"))
    )
    (net (code "1461") (name "Net-(J10B-P$2)") (class "Default")
      (node (ref "J10") (pin "E2") (pinfunction "P$2_E2") (pintype "bidirectional"))
      (node (ref "J19") (pin "M1") (pinfunction "IN_M1") (pintype "input"))
    )
    (net (code "1462") (name "Net-(J10J-P$2)") (class "Default")
      (node (ref "J10") (pin "H2") (pinfunction "P$2_H2") (pintype "bidirectional"))
      (node (ref "J19") (pin "R2") (pinfunction "IN_R2") (pintype "input"))
    )
    (net (code "1463") (name "Net-(J10K-P$2)") (class "Default")
      (node (ref "J10") (pin "K2") (pinfunction "P$2_K2") (pintype "bidirectional"))
      (node (ref "J20") (pin "D2") (pinfunction "IN_D2") (pintype "input"))
    )
    (net (code "1464") (name "Net-(J10L-P$2)") (class "Default")
      (node (ref "J10") (pin "M2") (pinfunction "P$2_M2") (pintype "bidirectional"))
      (node (ref "J20") (pin "F1") (pinfunction "IN_F1") (pintype "input"))
    )
    (net (code "1465") (name "Net-(J10N-P$2)") (class "Default")
      (node (ref "J10") (pin "S2") (pinfunction "P$2_S2") (pintype "bidirectional"))
      (node (ref "J11") (pin "D2") (pinfunction "P$2_D2") (pintype "bidirectional"))
      (node (ref "J20") (pin "R2") (pinfunction "IN_R2") (pintype "input"))
    )
    (net (code "1466") (name "Net-(J10O-P$2)") (class "Default")
      (node (ref "J10") (pin "T2") (pinfunction "P$2_T2") (pintype "bidirectional"))
      (node (ref "J11") (pin "E2") (pinfunction "P$2_E2") (pintype "bidirectional"))
      (node (ref "J20") (pin "M1") (pinfunction "IN_M1") (pintype "input"))
    )
    (net (code "1467") (name "Net-(J10P-P$2)") (class "Default")
      (node (ref "J10") (pin "V2") (pinfunction "P$2_V2") (pintype "bidirectional"))
      (node (ref "J11") (pin "H2") (pinfunction "P$2_H2") (pintype "bidirectional"))
      (node (ref "J20") (pin "K2") (pinfunction "IN_K2") (pintype "input"))
    )
    (net (code "1468") (name "Net-(J15G-IN2)") (class "Default")
      (node (ref "J15") (pin "L2") (pinfunction "IN2_L2") (pintype "passive"))
      (node (ref "J15") (pin "M2") (pinfunction "IN3_M2") (pintype "input"))
      (node (ref "J15") (pin "N2") (pinfunction "IN4_N2") (pintype "input"))
    )
    (net (code "1469") (name "Net-(J15H-IN2)") (class "Default")
      (node (ref "J15") (pin "N1") (pinfunction "IN2_N1") (pintype "passive"))
      (node (ref "J15") (pin "P1") (pinfunction "IN3_P1") (pintype "input"))
      (node (ref "J15") (pin "R1") (pinfunction "IN4_R1") (pintype "input"))
    )
    (net (code "1470") (name "Net-(J15I-IN2)") (class "Default")
      (node (ref "J15") (pin "S2") (pinfunction "IN2_S2") (pintype "passive"))
      (node (ref "J15") (pin "T2") (pinfunction "IN3_T2") (pintype "input"))
      (node (ref "J15") (pin "U2") (pinfunction "IN4_U2") (pintype "input"))
    )
    (net (code "1471") (name "Net-(J16A-IN2)") (class "Default")
      (node (ref "J16") (pin "B1") (pinfunction "IN2_B1") (pintype "passive"))
      (node (ref "J16") (pin "C1") (pinfunction "IN3_C1") (pintype "input"))
      (node (ref "J16") (pin "D1") (pinfunction "IN4_D1") (pintype "input"))
    )
    (net (code "1472") (name "Net-(J16E-IN2)") (class "Default")
      (node (ref "J16") (pin "E2") (pinfunction "IN2_E2") (pintype "passive"))
      (node (ref "J16") (pin "F2") (pinfunction "IN3_F2") (pintype "input"))
      (node (ref "J16") (pin "H2") (pinfunction "IN4_H2") (pintype "input"))
    )
    (net (code "1473") (name "Net-(J16F-IN2)") (class "Default")
      (node (ref "J16") (pin "H1") (pinfunction "IN2_H1") (pintype "passive"))
      (node (ref "J16") (pin "J1") (pinfunction "IN3_J1") (pintype "input"))
      (node (ref "J16") (pin "K1") (pinfunction "IN4_K1") (pintype "input"))
    )
    (net (code "1474") (name "Net-(J16G-IN2)") (class "Default")
      (node (ref "J16") (pin "L2") (pinfunction "IN2_L2") (pintype "passive"))
      (node (ref "J16") (pin "M2") (pinfunction "IN3_M2") (pintype "input"))
      (node (ref "J16") (pin "N2") (pinfunction "IN4_N2") (pintype "input"))
    )
    (net (code "1475") (name "Net-(J16H-IN2)") (class "Default")
      (node (ref "J16") (pin "N1") (pinfunction "IN2_N1") (pintype "passive"))
      (node (ref "J16") (pin "P1") (pinfunction "IN3_P1") (pintype "input"))
      (node (ref "J16") (pin "R1") (pinfunction "IN4_R1") (pintype "input"))
    )
    (net (code "1476") (name "Net-(J16I-IN2)") (class "Default")
      (node (ref "J16") (pin "S2") (pinfunction "IN2_S2") (pintype "passive"))
      (node (ref "J16") (pin "T2") (pinfunction "IN3_T2") (pintype "input"))
      (node (ref "J16") (pin "U2") (pinfunction "IN4_U2") (pintype "input"))
    )
    (net (code "1477") (name "Net-(J17A-IN2)") (class "Default")
      (node (ref "J17") (pin "B1") (pinfunction "IN2_B1") (pintype "passive"))
      (node (ref "J17") (pin "C1") (pinfunction "IN3_C1") (pintype "input"))
      (node (ref "J17") (pin "D1") (pinfunction "IN4_D1") (pintype "input"))
    )
    (net (code "1478") (name "Net-(J17E-IN2)") (class "Default")
      (node (ref "J17") (pin "E2") (pinfunction "IN2_E2") (pintype "passive"))
      (node (ref "J17") (pin "F2") (pinfunction "IN3_F2") (pintype "input"))
      (node (ref "J17") (pin "H2") (pinfunction "IN4_H2") (pintype "input"))
    )
    (net (code "1479") (name "Net-(J17F-IN2)") (class "Default")
      (node (ref "J17") (pin "H1") (pinfunction "IN2_H1") (pintype "passive"))
      (node (ref "J17") (pin "J1") (pinfunction "IN3_J1") (pintype "input"))
      (node (ref "J17") (pin "K1") (pinfunction "IN4_K1") (pintype "input"))
    )
    (net (code "1480") (name "Net-(J17G-IN2)") (class "Default")
      (node (ref "J17") (pin "L2") (pinfunction "IN2_L2") (pintype "passive"))
      (node (ref "J17") (pin "M2") (pinfunction "IN3_M2") (pintype "input"))
      (node (ref "J17") (pin "N2") (pinfunction "IN4_N2") (pintype "input"))
    )
    (net (code "1481") (name "Net-(J17H-IN2)") (class "Default")
      (node (ref "J17") (pin "N1") (pinfunction "IN2_N1") (pintype "passive"))
      (node (ref "J17") (pin "P1") (pinfunction "IN3_P1") (pintype "input"))
      (node (ref "J17") (pin "R1") (pinfunction "IN4_R1") (pintype "input"))
    )
    (net (code "1482") (name "Net-(J17I-IN2)") (class "Default")
      (node (ref "J17") (pin "S2") (pinfunction "IN2_S2") (pintype "passive"))
      (node (ref "J17") (pin "T2") (pinfunction "IN3_T2") (pintype "input"))
      (node (ref "J17") (pin "U2") (pinfunction "IN4_U2") (pintype "input"))
    )
    (net (code "1483") (name "Net-(J18A-IN2)") (class "Default")
      (node (ref "J18") (pin "B1") (pinfunction "IN2_B1") (pintype "passive"))
      (node (ref "J18") (pin "C1") (pinfunction "IN3_C1") (pintype "input"))
      (node (ref "J18") (pin "D1") (pinfunction "IN4_D1") (pintype "input"))
    )
    (net (code "1484") (name "Net-(J18E-IN2)") (class "Default")
      (node (ref "J18") (pin "E2") (pinfunction "IN2_E2") (pintype "passive"))
      (node (ref "J18") (pin "F2") (pinfunction "IN3_F2") (pintype "input"))
      (node (ref "J18") (pin "H2") (pinfunction "IN4_H2") (pintype "input"))
    )
    (net (code "1485") (name "Net-(J18F-IN2)") (class "Default")
      (node (ref "J18") (pin "H1") (pinfunction "IN2_H1") (pintype "passive"))
      (node (ref "J18") (pin "J1") (pinfunction "IN3_J1") (pintype "input"))
      (node (ref "J18") (pin "K1") (pinfunction "IN4_K1") (pintype "input"))
    )
    (net (code "1486") (name "Net-(J18G-IN2)") (class "Default")
      (node (ref "J18") (pin "L2") (pinfunction "IN2_L2") (pintype "passive"))
      (node (ref "J18") (pin "M2") (pinfunction "IN3_M2") (pintype "input"))
      (node (ref "J18") (pin "N2") (pinfunction "IN4_N2") (pintype "input"))
    )
    (net (code "1487") (name "Net-(J18H-IN2)") (class "Default")
      (node (ref "J18") (pin "N1") (pinfunction "IN2_N1") (pintype "passive"))
      (node (ref "J18") (pin "P1") (pinfunction "IN3_P1") (pintype "input"))
      (node (ref "J18") (pin "R1") (pinfunction "IN4_R1") (pintype "input"))
    )
    (net (code "1488") (name "Net-(J18I-IN2)") (class "Default")
      (node (ref "J18") (pin "S2") (pinfunction "IN2_S2") (pintype "passive"))
      (node (ref "J18") (pin "T2") (pinfunction "IN3_T2") (pintype "input"))
      (node (ref "J18") (pin "U2") (pinfunction "IN4_U2") (pintype "input"))
    )
    (net (code "1489") (name "Net-(J19A-IN2)") (class "Default")
      (node (ref "J19") (pin "B1") (pinfunction "IN2_B1") (pintype "passive"))
      (node (ref "J19") (pin "C1") (pinfunction "IN3_C1") (pintype "input"))
      (node (ref "J19") (pin "D1") (pinfunction "IN4_D1") (pintype "input"))
    )
    (net (code "1490") (name "Net-(J19E-IN2)") (class "Default")
      (node (ref "J19") (pin "E2") (pinfunction "IN2_E2") (pintype "passive"))
      (node (ref "J19") (pin "F2") (pinfunction "IN3_F2") (pintype "input"))
      (node (ref "J19") (pin "H2") (pinfunction "IN4_H2") (pintype "input"))
    )
    (net (code "1491") (name "Net-(J19F-IN2)") (class "Default")
      (node (ref "J19") (pin "H1") (pinfunction "IN2_H1") (pintype "passive"))
      (node (ref "J19") (pin "J1") (pinfunction "IN3_J1") (pintype "input"))
      (node (ref "J19") (pin "K1") (pinfunction "IN4_K1") (pintype "input"))
    )
    (net (code "1492") (name "Net-(J19G-IN2)") (class "Default")
      (node (ref "J19") (pin "L2") (pinfunction "IN2_L2") (pintype "passive"))
      (node (ref "J19") (pin "M2") (pinfunction "IN3_M2") (pintype "input"))
      (node (ref "J19") (pin "N2") (pinfunction "IN4_N2") (pintype "input"))
    )
    (net (code "1493") (name "Net-(J19H-IN2)") (class "Default")
      (node (ref "J19") (pin "N1") (pinfunction "IN2_N1") (pintype "passive"))
      (node (ref "J19") (pin "P1") (pinfunction "IN3_P1") (pintype "input"))
      (node (ref "J19") (pin "R1") (pinfunction "IN4_R1") (pintype "input"))
    )
    (net (code "1494") (name "Net-(J19I-IN2)") (class "Default")
      (node (ref "J19") (pin "S2") (pinfunction "IN2_S2") (pintype "passive"))
      (node (ref "J19") (pin "T2") (pinfunction "IN3_T2") (pintype "input"))
      (node (ref "J19") (pin "U2") (pinfunction "IN4_U2") (pintype "input"))
    )
    (net (code "1495") (name "Net-(J20A-IN2)") (class "Default")
      (node (ref "J20") (pin "B1") (pinfunction "IN2_B1") (pintype "passive"))
      (node (ref "J20") (pin "C1") (pinfunction "IN3_C1") (pintype "input"))
      (node (ref "J20") (pin "D1") (pinfunction "IN4_D1") (pintype "input"))
    )
    (net (code "1496") (name "Net-(J20E-IN2)") (class "Default")
      (node (ref "J20") (pin "E2") (pinfunction "IN2_E2") (pintype "passive"))
      (node (ref "J20") (pin "F2") (pinfunction "IN3_F2") (pintype "input"))
      (node (ref "J20") (pin "H2") (pinfunction "IN4_H2") (pintype "input"))
    )
    (net (code "1497") (name "Net-(J20F-IN2)") (class "Default")
      (node (ref "J20") (pin "H1") (pinfunction "IN2_H1") (pintype "passive"))
      (node (ref "J20") (pin "J1") (pinfunction "IN3_J1") (pintype "input"))
      (node (ref "J20") (pin "K1") (pinfunction "IN4_K1") (pintype "input"))
    )
    (net (code "1498") (name "Net-(J20G-IN2)") (class "Default")
      (node (ref "J20") (pin "L2") (pinfunction "IN2_L2") (pintype "passive"))
      (node (ref "J20") (pin "M2") (pinfunction "IN3_M2") (pintype "input"))
      (node (ref "J20") (pin "N2") (pinfunction "IN4_N2") (pintype "input"))
    )
    (net (code "1499") (name "Net-(J20H-IN2)") (class "Default")
      (node (ref "J20") (pin "N1") (pinfunction "IN2_N1") (pintype "passive"))
      (node (ref "J20") (pin "P1") (pinfunction "IN3_P1") (pintype "input"))
      (node (ref "J20") (pin "R1") (pinfunction "IN4_R1") (pintype "input"))
    )
    (net (code "1500") (name "Net-(J20I-IN2)") (class "Default")
      (node (ref "J20") (pin "S2") (pinfunction "IN2_S2") (pintype "passive"))
      (node (ref "J20") (pin "T2") (pinfunction "IN3_T2") (pintype "input"))
      (node (ref "J20") (pin "U2") (pinfunction "IN4_U2") (pintype "input"))
    )
    (net (code "1501") (name "OP1") (class "Default")
      (node (ref "E27") (pin "H1") (pinfunction "IN3A_H1") (pintype "input"))
      (node (ref "E28") (pin "C1") (pinfunction "IN1C_C1") (pintype "input"))
      (node (ref "E28") (pin "N1") (pinfunction "IN5B_N1") (pintype "input"))
      (node (ref "E30") (pin "L2") (pinfunction "IN3A_L2") (pintype "input"))
      (node (ref "F25") (pin "C1") (pinfunction "OUT_C1") (pintype "output"))
      (node (ref "F26") (pin "B1") (pinfunction "IN2_B1") (pintype "input"))
      (node (ref "F26") (pin "E2") (pinfunction "IN2_E2") (pintype "input"))
      (node (ref "F26") (pin "F1") (pinfunction "IN2_F1") (pintype "input"))
      (node (ref "F26") (pin "K2") (pinfunction "IN2_K2") (pintype "input"))
      (node (ref "F26") (pin "L1") (pinfunction "IN2_L1") (pintype "input"))
      (node (ref "F29") (pin "T2") (pinfunction "IN1_T2") (pintype "input"))
      (node (ref "F32") (pin "H2") (pinfunction "IN1_H2") (pintype "input"))
    )
    (net (code "1502") (name "OP1_") (class "Default")
      (node (ref "F24") (pin "A1") (pinfunction "IN1_A1") (pintype "input"))
      (node (ref "F25") (pin "A1") (pinfunction "IN1_A1") (pintype "input"))
      (node (ref "F27") (pin "V2") (pinfunction "OUT_V2") (pintype "output"))
    )
    (net (code "1503") (name "OP2") (class "Default")
      (node (ref "B04") (pin "E2") (pinfunction "IN2_E2") (pintype "input"))
      (node (ref "D18") (pin "E2") (pinfunction "IN2_E2") (pintype "input"))
      (node (ref "D18") (pin "F1") (pinfunction "IN2_F1") (pintype "input"))
      (node (ref "D21") (pin "K1") (pinfunction "IN4_K1") (pintype "input"))
      (node (ref "E13") (pin "C1") (pinfunction "IN1C_C1") (pintype "input"))
      (node (ref "E25") (pin "R2") (pinfunction "IN3_R2") (pintype "input"))
      (node (ref "E28") (pin "P2") (pinfunction "IN4B_P2") (pintype "input"))
      (node (ref "E30") (pin "D2") (pinfunction "IN1A_D2") (pintype "input"))
      (node (ref "F28") (pin "N2") (pinfunction "IN1_N2") (pintype "input"))
      (node (ref "F29") (pin "K1") (pinfunction "OUT_K1") (pintype "output"))
    )
    (net (code "1504") (name "OPR") (class "Default")
      (node (ref "D13") (pin "L2") (pinfunction "IN1_L2") (pintype "input"))
      (node (ref "D14") (pin "D2") (pinfunction "IN1_D2") (pintype "input"))
      (node (ref "D20") (pin "N1") (pinfunction "IN2_N1") (pintype "input"))
      (node (ref "D21") (pin "F2") (pinfunction "IN3_F2") (pintype "input"))
      (node (ref "E22") (pin "S2") (pinfunction "OUT_S2") (pintype "output"))
      (node (ref "E25") (pin "V2") (pinfunction "IN3_V2") (pintype "input"))
      (node (ref "E26") (pin "S2") (pinfunction "IN4D_S2") (pintype "input"))
      (node (ref "F27") (pin "F1") (pinfunction "IN1_F1") (pintype "input"))
      (node (ref "F27") (pin "R2") (pinfunction "IN1_R2") (pintype "input"))
    )
    (net (code "1505") (name "OPR_") (class "Default")
      (node (ref "D40") (pin "D2") (pinfunction "P$2_D2") (pintype "bidirectional"))
      (node (ref "E21") (pin "V1") (pinfunction "OUT_V1") (pintype "output"))
      (node (ref "E22") (pin "P2") (pinfunction "IN1_P2") (pintype "input"))
    )
    (net (code "1506") (name "OSR_") (class "Default")
      (node (ref "A06") (pin "E2") (pinfunction "IN2_E2") (pintype "input"))
      (node (ref "F28") (pin "S2") (pinfunction "OUT_S2") (pintype "output"))
    )
    (net (code "1507") (name "OUT_STOP2_") (class "Default")
      (node (ref "EF02") (pin "BN1") (pinfunction "BN1_BN1") (pintype "output"))
      (node (ref "EF02") (pin "BN2") (pinfunction "BN2_BN2") (pintype "input"))
    )
    (net (code "1508") (name "OVERFLOW") (class "Default")
      (node (ref "H30") (pin "V1") (pinfunction "V1_V1") (pintype "input"))
      (node (ref "HJ31") (pin "BS1") (pinfunction "BS1_BS1") (pintype "output"))
    )
    (net (code "1509") (name "PAUSE_") (class "Default")
      (node (ref "D40") (pin "M1") (pinfunction "P$2_M1") (pintype "bidirectional"))
      (node (ref "E14") (pin "B1") (pinfunction "IN2_B1") (pintype "input"))
      (node (ref "E18") (pin "M1") (pinfunction "0_M1") (pintype "output"))
    )
    (net (code "1510") (name "PC00_") (class "Default")
      (node (ref "E40") (pin "J2") (pinfunction "P$2_J2") (pintype "bidirectional"))
      (node (ref "EF34") (pin "AR2") (pinfunction "AR2_AR2") (pintype "output"))
    )
    (net (code "1511") (name "PC01_") (class "Default")
      (node (ref "E40") (pin "S1") (pinfunction "P$2_S1") (pintype "bidirectional"))
      (node (ref "EF34") (pin "AP2") (pinfunction "AP2_AP2") (pintype "output"))
    )
    (net (code "1512") (name "PC02_") (class "Default")
      (node (ref "E40") (pin "P2") (pinfunction "P$2_P2") (pintype "bidirectional"))
      (node (ref "EF35") (pin "AR2") (pinfunction "AR2_AR2") (pintype "output"))
    )
    (net (code "1513") (name "PC03_") (class "Default")
      (node (ref "E40") (pin "N1") (pinfunction "P$2_N1") (pintype "bidirectional"))
      (node (ref "EF35") (pin "AP2") (pinfunction "AP2_AP2") (pintype "output"))
    )
    (net (code "1514") (name "PC04_") (class "Default")
      (node (ref "E40") (pin "C1") (pinfunction "P$2_C1") (pintype "bidirectional"))
      (node (ref "EF36") (pin "AR2") (pinfunction "AR2_AR2") (pintype "output"))
    )
    (net (code "1515") (name "PC05_") (class "Default")
      (node (ref "E40") (pin "D1") (pinfunction "P$2_D1") (pintype "bidirectional"))
      (node (ref "EF36") (pin "AP2") (pinfunction "AP2_AP2") (pintype "output"))
    )
    (net (code "1516") (name "PC06_") (class "Default")
      (node (ref "EF37") (pin "AR2") (pinfunction "AR2_AR2") (pintype "output"))
      (node (ref "F40") (pin "J2") (pinfunction "P$2_J2") (pintype "bidirectional"))
    )
    (net (code "1517") (name "PC07_") (class "Default")
      (node (ref "EF37") (pin "AP2") (pinfunction "AP2_AP2") (pintype "output"))
      (node (ref "F40") (pin "S1") (pinfunction "P$2_S1") (pintype "bidirectional"))
    )
    (net (code "1518") (name "PC08_") (class "Default")
      (node (ref "EF38") (pin "AR2") (pinfunction "AR2_AR2") (pintype "output"))
      (node (ref "F40") (pin "P2") (pinfunction "P$2_P2") (pintype "bidirectional"))
    )
    (net (code "1519") (name "PC09_") (class "Default")
      (node (ref "EF38") (pin "AP2") (pinfunction "AP2_AP2") (pintype "output"))
      (node (ref "F40") (pin "N1") (pinfunction "P$2_N1") (pintype "bidirectional"))
    )
    (net (code "1520") (name "PC10_") (class "Default")
      (node (ref "EF39") (pin "AR2") (pinfunction "AR2_AR2") (pintype "output"))
      (node (ref "F40") (pin "C1") (pinfunction "P$2_C1") (pintype "bidirectional"))
    )
    (net (code "1521") (name "PC11_") (class "Default")
      (node (ref "EF39") (pin "AP2") (pinfunction "AP2_AP2") (pintype "output"))
      (node (ref "F40") (pin "D1") (pinfunction "P$2_D1") (pintype "bidirectional"))
    )
    (net (code "1522") (name "PC_ENABLE") (class "Default")
      (node (ref "EF34") (pin "BS2") (pinfunction "BS2_BS2") (pintype "input"))
      (node (ref "EF35") (pin "BS2") (pinfunction "BS2_BS2") (pintype "input"))
      (node (ref "EF36") (pin "BS2") (pinfunction "BS2_BS2") (pintype "input"))
      (node (ref "EF37") (pin "BS2") (pinfunction "BS2_BS2") (pintype "input"))
      (node (ref "EF38") (pin "BS2") (pinfunction "BS2_BS2") (pintype "input"))
      (node (ref "EF39") (pin "BS2") (pinfunction "BS2_BS2") (pintype "input"))
      (node (ref "F30") (pin "E1") (pinfunction "OUT_E1") (pintype "open_collector"))
    )
    (net (code "1523") (name "PC_ENABLE_") (class "Default")
      (node (ref "F09") (pin "M2") (pinfunction "IN7_M2") (pintype "input"))
      (node (ref "F11") (pin "P1") (pinfunction "IN3_P1") (pintype "input"))
      (node (ref "F27") (pin "H2") (pinfunction "IN4_H2") (pintype "input"))
      (node (ref "F32") (pin "N1") (pinfunction "OUT_N1") (pintype "output"))
    )
    (net (code "1524") (name "PC_INCREMENT") (class "Default")
      (node (ref "E26") (pin "F1") (pinfunction "IN2B_F1") (pintype "input"))
      (node (ref "E27") (pin "F1") (pinfunction "IN2B_F1") (pintype "input"))
      (node (ref "E30") (pin "F1") (pinfunction "IN2B_F1") (pintype "input"))
      (node (ref "F28") (pin "V1") (pinfunction "OUT_V1") (pintype "output"))
    )
    (net (code "1525") (name "PC_LOAD") (class "Default")
      (node (ref "A15") (pin "H1") (pinfunction "IN1_H1") (pintype "input"))
      (node (ref "E32") (pin "J2") (pinfunction "OUT_J2") (pintype "open_collector"))
      (node (ref "EF34") (pin "AN2") (pinfunction "AN2_AN2") (pintype "input"))
      (node (ref "EF35") (pin "AN2") (pinfunction "AN2_AN2") (pintype "input"))
      (node (ref "EF36") (pin "AN2") (pinfunction "AN2_AN2") (pintype "input"))
      (node (ref "EF37") (pin "AN2") (pinfunction "AN2_AN2") (pintype "input"))
      (node (ref "EF38") (pin "AN2") (pinfunction "AN2_AN2") (pintype "input"))
      (node (ref "EF39") (pin "AN2") (pinfunction "AN2_AN2") (pintype "input"))
      (node (ref "F25") (pin "P1") (pinfunction "IN1_P1") (pintype "input"))
    )
    (net (code "1526") (name "PC_LOADXSR_ENABLE_") (class "Default")
      (node (ref "A15") (pin "K1") (pinfunction "OUT_K1") (pintype "output"))
      (node (ref "A17") (pin "A1") (pinfunction "IN1_A1") (pintype "input"))
      (node (ref "A17") (pin "R2") (pinfunction "IN2_R2") (pintype "input"))
      (node (ref "A18") (pin "A1") (pinfunction "IN1_A1") (pintype "input"))
      (node (ref "B06") (pin "H1") (pinfunction "IN1_H1") (pintype "input"))
    )
    (net (code "1527") (name "PC_LOAD_") (class "Default")
      (node (ref "B04") (pin "M1") (pinfunction "IN3_M1") (pintype "input"))
      (node (ref "E18") (pin "R1") (pinfunction "S_R1") (pintype "input"))
      (node (ref "F25") (pin "S1") (pinfunction "OUT_S1") (pintype "output"))
    )
    (net (code "1528") (name "PEN_DOWN") (class "Default")
      (node (ref "D02") (pin "V2") (pinfunction "P$2_V2") (pintype "bidirectional"))
      (node (ref "HJ29") (pin "AV2") (pinfunction "AV2_AV2") (pintype "output"))
    )
    (net (code "1529") (name "PEN_LEFT") (class "Default")
      (node (ref "D02") (pin "R2") (pinfunction "P$2_R2") (pintype "bidirectional"))
      (node (ref "HJ29") (pin "AL2") (pinfunction "AL2_AL2") (pintype "output"))
    )
    (net (code "1530") (name "PEN_RIGHT") (class "Default")
      (node (ref "D02") (pin "P2") (pinfunction "P$2_P2") (pintype "bidirectional"))
      (node (ref "HJ29") (pin "AJ2") (pinfunction "AJ2_AJ2") (pintype "output"))
    )
    (net (code "1531") (name "PEN_STROBE") (class "Default")
      (node (ref "HJ23") (pin "AJ1") (pinfunction "AJ1_AJ1") (pintype "output"))
      (node (ref "HJ23") (pin "AK1") (pinfunction "AK1_AK1") (pintype "input"))
    )
    (net (code "1532") (name "PEN_UP") (class "Default")
      (node (ref "D02") (pin "U2") (pinfunction "P$2_U2") (pintype "bidirectional"))
      (node (ref "HJ29") (pin "AT2") (pinfunction "AT2_AT2") (pintype "output"))
    )
    (net (code "1533") (name "POWER_CLEAR_") (class "Default")
      (node (ref "AB02") (pin "AS2") (pinfunction "AS2_AS2") (pintype "bidirectional"))
      (node (ref "B21") (pin "T2") (pinfunction "IN1_T2") (pintype "input"))
      (node (ref "B21") (pin "U2") (pinfunction "IN2_U2") (pintype "input"))
    )
    (net (code "1534") (name "POWER_OK_") (class "Default")
      (node (ref "AB02") (pin "AJ2") (pinfunction "AJ2_AJ2") (pintype "bidirectional"))
      (node (ref "E13") (pin "L1") (pinfunction "IN4B_L1") (pintype "input"))
    )
    (net (code "1535") (name "PROCESSOR_IOT_") (class "Default")
      (node (ref "F19") (pin "D1") (pinfunction "IN4_D1") (pintype "input"))
      (node (ref "F21") (pin "V2") (pinfunction "OUT_V2") (pintype "output"))
    )
    (net (code "1536") (name "PUN_FEED_SWITCH_") (class "Default")
      (node (ref "C01") (pin "U2") (pinfunction "P$2_U2") (pintype "bidirectional"))
      (node (ref "HJ28") (pin "AT2") (pinfunction "AT2_AT2") (pintype "input"))
    )
    (net (code "1537") (name "PWR") (class "Default")
      (node (ref "D01") (pin "U2") (pinfunction "P$2_U2") (pintype "bidirectional"))
      (node (ref "HJ26") (pin "BR2") (pinfunction "BR2_BR2") (pintype "output"))
    )
    (net (code "1538") (name "PWR_LOW_") (class "Default")
      (node (ref "A04") (pin "R2") (pinfunction "R2_R2") (pintype "output"))
      (node (ref "F19") (pin "M1") (pinfunction "IN1_M1") (pintype "input"))
    )
    (net (code "1539") (name "PWR_SKIP_") (class "Default")
      (node (ref "A04") (pin "L2") (pinfunction "L2_L2") (pintype "output"))
      (node (ref "F19") (pin "M2") (pinfunction "IN3_M2") (pintype "input"))
    )
    (net (code "1540") (name "R0") (class "Default")
      (node (ref "C09") (pin "L2") (pinfunction "IN1_L2") (pintype "input"))
      (node (ref "D05") (pin "J2") (pinfunction "OUT_J2") (pintype "output"))
      (node (ref "D10") (pin "R2") (pinfunction "IN1_R2") (pintype "input"))
    )
    (net (code "1541") (name "R0_") (class "Default")
      (node (ref "C09") (pin "N2") (pinfunction "OUT_N2") (pintype "output"))
      (node (ref "D10") (pin "M1") (pinfunction "IN1_M1") (pintype "input"))
    )
    (net (code "1542") (name "RDR_ENABLE_") (class "Default")
      (node (ref "HJ26") (pin "BK2") (pinfunction "BK2_BK2") (pintype "output"))
      (node (ref "HJ27") (pin "AK2") (pinfunction "AK_AK2") (pintype "input"))
    )
    (net (code "1543") (name "RDR_FEED_SWITCH") (class "Default")
      (node (ref "D01") (pin "V2") (pinfunction "P$2_V2") (pintype "bidirectional"))
      (node (ref "HJ26") (pin "BM1") (pinfunction "BM1_BM1") (pintype "input"))
      (node (ref "HJ27") (pin "BP2") (pinfunction "BP_BP2") (pintype "input"))
    )
    (net (code "1544") (name "RDR_RUN_") (class "Default")
      (node (ref "HJ26") (pin "AK1") (pinfunction "AK1_AK1") (pintype "output"))
      (node (ref "HJ27") (pin "BS2") (pinfunction "BS_BS2") (pintype "input"))
    )
    (net (code "1545") (name "RDR_SHIFT") (class "Default")
      (node (ref "HJ26") (pin "BJ1") (pinfunction "BJ1_BJ1") (pintype "input"))
      (node (ref "HJ27") (pin "AS2") (pinfunction "AS_AS2") (pintype "output"))
    )
    (net (code "1546") (name "RDR_SHIFT_") (class "Default")
      (node (ref "HJ26") (pin "BD1") (pinfunction "BD1_BD1") (pintype "input"))
      (node (ref "HJ27") (pin "AT2") (pinfunction "AT_AT2") (pintype "output"))
    )
    (net (code "1547") (name "RD_HOLE1") (class "Default")
      (node (ref "D01") (pin "D2") (pinfunction "P$2_D2") (pintype "bidirectional"))
      (node (ref "HJ26") (pin "AD2") (pinfunction "AD2_AD2") (pintype "input"))
    )
    (net (code "1548") (name "RD_HOLE2") (class "Default")
      (node (ref "D01") (pin "E2") (pinfunction "P$2_E2") (pintype "bidirectional"))
      (node (ref "HJ26") (pin "AD1") (pinfunction "AD1_AD1") (pintype "input"))
    )
    (net (code "1549") (name "RD_HOLE3") (class "Default")
      (node (ref "D01") (pin "F2") (pinfunction "P$2_F2") (pintype "bidirectional"))
      (node (ref "HJ26") (pin "AE2") (pinfunction "AE2_AE2") (pintype "input"))
    )
    (net (code "1550") (name "RD_HOLE4") (class "Default")
      (node (ref "D01") (pin "H2") (pinfunction "P$2_H2") (pintype "bidirectional"))
      (node (ref "HJ26") (pin "AE1") (pinfunction "AE1_AE1") (pintype "input"))
    )
    (net (code "1551") (name "RD_HOLE5") (class "Default")
      (node (ref "D01") (pin "J2") (pinfunction "P$2_J2") (pintype "bidirectional"))
      (node (ref "HJ26") (pin "AH2") (pinfunction "AH2_AH2") (pintype "input"))
    )
    (net (code "1552") (name "RD_HOLE6") (class "Default")
      (node (ref "D01") (pin "K2") (pinfunction "P$2_K2") (pintype "bidirectional"))
      (node (ref "HJ26") (pin "AH1") (pinfunction "AH1_AH1") (pintype "input"))
    )
    (net (code "1553") (name "RD_HOLE7") (class "Default")
      (node (ref "D01") (pin "L2") (pinfunction "P$2_L2") (pintype "bidirectional"))
      (node (ref "HJ26") (pin "AF2") (pinfunction "AF2_AF2") (pintype "input"))
    )
    (net (code "1554") (name "RD_HOLE8") (class "Default")
      (node (ref "D01") (pin "M2") (pinfunction "P$2_M2") (pintype "bidirectional"))
      (node (ref "HJ26") (pin "AF1") (pinfunction "AF1_AF1") (pintype "input"))
    )
    (net (code "1555") (name "READ") (class "Default")
      (node (ref "B22") (pin "L1") (pinfunction "1_L1") (pintype "output"))
      (node (ref "C39") (pin "D2") (pinfunction "D2_D2") (pintype "input"))
      (node (ref "C39") (pin "M2") (pinfunction "M2_M2") (pintype "input"))
      (node (ref "D39") (pin "D2") (pinfunction "D2_D2") (pintype "input"))
      (node (ref "D39") (pin "M2") (pinfunction "M2_M2") (pintype "input"))
    )
    (net (code "1556") (name "READER_RUN_") (class "Default")
      (node (ref "EF01") (pin "AU2") (pinfunction "AU2_AU2") (pintype "output"))
      (node (ref "J12") (pin "M2") (pinfunction "P$2_M2") (pintype "bidirectional"))
    )
    (net (code "1557") (name "RESTART") (class "Default")
      (node (ref "A04") (pin "N2") (pinfunction "N2_N2") (pintype "output"))
      (node (ref "E12") (pin "L2") (pinfunction "IN1_L2") (pintype "input"))
    )
    (net (code "1558") (name "RESTART_") (class "Default")
      (node (ref "A04") (pin "U1") (pinfunction "U1_U1") (pintype "output"))
      (node (ref "E11") (pin "E1") (pinfunction "IN2_E1") (pintype "input"))
      (node (ref "E14") (pin "D2") (pinfunction "IN1_D2") (pintype "input"))
      (node (ref "E14") (pin "K2") (pinfunction "IN2_K2") (pintype "input"))
      (node (ref "EF10") (pin "AR2") (pinfunction "CR2_AR2") (pintype "input"))
    )
    (net (code "1559") (name "RIB") (class "Default")
      (node (ref "A05") (pin "H2") (pinfunction "IN1_H2") (pintype "input"))
      (node (ref "A11") (pin "D2") (pinfunction "IN1_D2") (pintype "input"))
      (node (ref "A11") (pin "L1") (pinfunction "IN1_L1") (pintype "input"))
      (node (ref "A11") (pin "P2") (pinfunction "IN1_P2") (pintype "input"))
      (node (ref "A13") (pin "H2") (pinfunction "IN1_H2") (pintype "input"))
      (node (ref "A13") (pin "L2") (pinfunction "IN1_L2") (pintype "input"))
      (node (ref "A13") (pin "P2") (pinfunction "IN1_P2") (pintype "input"))
      (node (ref "A14") (pin "N2") (pinfunction "OUT_N2") (pintype "output"))
    )
    (net (code "1560") (name "RIGHT_SHIFT") (class "Default")
      (node (ref "C14") (pin "A1") (pinfunction "IN1_A1") (pintype "input"))
      (node (ref "C14") (pin "H1") (pinfunction "IN1_H1") (pintype "input"))
      (node (ref "C14") (pin "L2") (pinfunction "IN1_L2") (pintype "input"))
      (node (ref "C15") (pin "A1") (pinfunction "IN1_A1") (pintype "input"))
      (node (ref "C15") (pin "H1") (pinfunction "IN1_H1") (pintype "input"))
      (node (ref "C15") (pin "L2") (pinfunction "IN1_L2") (pintype "input"))
      (node (ref "C16") (pin "A1") (pinfunction "IN1_A1") (pintype "input"))
      (node (ref "C16") (pin "H1") (pinfunction "IN1_H1") (pintype "input"))
      (node (ref "C16") (pin "L2") (pinfunction "IN1_L2") (pintype "input"))
      (node (ref "C17") (pin "A1") (pinfunction "IN1_A1") (pintype "input"))
      (node (ref "C17") (pin "H1") (pinfunction "IN1_H1") (pintype "input"))
      (node (ref "C17") (pin "L2") (pinfunction "IN1_L2") (pintype "input"))
      (node (ref "E31") (pin "L1") (pinfunction "OUT_L1") (pintype "open_collector"))
      (node (ref "EF34") (pin "AD2") (pinfunction "AD2_AD2") (pintype "input"))
      (node (ref "EF35") (pin "AD2") (pinfunction "AD2_AD2") (pintype "input"))
      (node (ref "EF36") (pin "AD2") (pinfunction "AD2_AD2") (pintype "input"))
      (node (ref "EF37") (pin "AD2") (pinfunction "AD2_AD2") (pintype "input"))
      (node (ref "EF38") (pin "AD2") (pinfunction "AD2_AD2") (pintype "input"))
      (node (ref "EF39") (pin "AD2") (pinfunction "AD2_AD2") (pintype "input"))
      (node (ref "F33") (pin "D1") (pinfunction "IN1D_D1") (pintype "input"))
    )
    (net (code "1561") (name "RMF_") (class "Default")
      (node (ref "A06") (pin "V2") (pinfunction "OUT_V2") (pintype "output"))
      (node (ref "A13") (pin "B1") (pinfunction "IN2_B1") (pintype "input"))
      (node (ref "A15") (pin "L2") (pinfunction "IN1_L2") (pintype "input"))
      (node (ref "A15") (pin "M1") (pinfunction "IN2_M1") (pintype "input"))
      (node (ref "B06") (pin "E1") (pinfunction "IN2_E1") (pintype "input"))
    )
    (net (code "1562") (name "RUN") (class "Default")
      (node (ref "B10") (pin "J2") (pinfunction "J2_J2") (pintype "input"))
      (node (ref "E14") (pin "C1") (pinfunction "IN3_C1") (pintype "input"))
      (node (ref "E18") (pin "P2") (pinfunction "1_P2") (pintype "output"))
    )
    (net (code "1563") (name "RUN_") (class "Default")
      (node (ref "D40") (pin "F1") (pinfunction "P$2_F1") (pintype "bidirectional"))
      (node (ref "E18") (pin "R2") (pinfunction "0_R2") (pintype "output"))
      (node (ref "EF10") (pin "AP2") (pinfunction "CP2_AP2") (pintype "input"))
      (node (ref "F21") (pin "E1") (pinfunction "IN2_E1") (pintype "input"))
      (node (ref "H19") (pin "H2") (pinfunction "IN2_H2") (pintype "input"))
    )
    (net (code "1564") (name "RX_DATA") (class "Default")
      (node (ref "EF01") (pin "BM2") (pinfunction "BM2_BM2") (pintype "input"))
      (node (ref "J12") (pin "E2") (pinfunction "P$2_E2") (pintype "bidirectional"))
    )
    (net (code "1565") (name "S") (class "Default")
      (node (ref "C07") (pin "U2") (pinfunction "IN2_U2") (pintype "input"))
      (node (ref "C10") (pin "R1") (pinfunction "IN2_R1") (pintype "input"))
      (node (ref "C11") (pin "L2") (pinfunction "IN3_L2") (pintype "input"))
      (node (ref "C11") (pin "P2") (pinfunction "IN2_P2") (pintype "input"))
      (node (ref "D07") (pin "L1") (pinfunction "IN1_L1") (pintype "input"))
      (node (ref "D07") (pin "T2") (pinfunction "IN1_T2") (pintype "input"))
      (node (ref "D09") (pin "A1") (pinfunction "IN1_A1") (pintype "input"))
      (node (ref "D10") (pin "D2") (pinfunction "IN1_D2") (pintype "input"))
      (node (ref "D10") (pin "K1") (pinfunction "IN4_K1") (pintype "input"))
      (node (ref "D11") (pin "F1") (pinfunction "0_F1") (pintype "output"))
    )
    (net (code "1566") (name "SC0") (class "Default")
      (node (ref "C21") (pin "F2") (pinfunction "IN3_F2") (pintype "input"))
      (node (ref "C22") (pin "E1") (pinfunction "1_E1") (pintype "output"))
      (node (ref "D23") (pin "L1") (pinfunction "IN4B_L1") (pintype "input"))
      (node (ref "EF37") (pin "BN1") (pinfunction "BN1_BN1") (pintype "input"))
    )
    (net (code "1567") (name "SC0_") (class "Default")
      (node (ref "C21") (pin "C1") (pinfunction "IN3_C1") (pintype "input"))
      (node (ref "C22") (pin "F1") (pinfunction "0_F1") (pintype "output"))
      (node (ref "C40") (pin "S2") (pinfunction "P$2_S2") (pintype "bidirectional"))
    )
    (net (code "1568") (name "SC0_3_0") (class "Default")
      (node (ref "C18") (pin "S2") (pinfunction "OUT_S2") (pintype "output"))
      (node (ref "D13") (pin "P2") (pinfunction "IN1_P2") (pintype "input"))
      (node (ref "D19") (pin "E1") (pinfunction "IN1_E1") (pintype "input"))
      (node (ref "D23") (pin "F2") (pinfunction "IN1C_F2") (pintype "input"))
    )
    (net (code "1569") (name "SC0_3_0_") (class "Default")
      (node (ref "C18") (pin "P2") (pinfunction "IN1_P2") (pintype "input"))
      (node (ref "D17") (pin "N2") (pinfunction "IN1_N2") (pintype "input"))
      (node (ref "D22") (pin "J2") (pinfunction "OUT_J2") (pintype "open_collector"))
    )
    (net (code "1570") (name "SC1") (class "Default")
      (node (ref "C21") (pin "L2") (pinfunction "IN3_L2") (pintype "input"))
      (node (ref "C22") (pin "H2") (pinfunction "1_H2") (pintype "output"))
      (node (ref "D17") (pin "E1") (pinfunction "IN1_E1") (pintype "input"))
      (node (ref "D19") (pin "J2") (pinfunction "IN1_J2") (pintype "input"))
      (node (ref "D20") (pin "L2") (pinfunction "IN2_L2") (pintype "input"))
      (node (ref "D22") (pin "A1") (pinfunction "IN1_A1") (pintype "input"))
      (node (ref "D23") (pin "B1") (pinfunction "IN1B_B1") (pintype "input"))
      (node (ref "EF38") (pin "BD1") (pinfunction "BD1_BD1") (pintype "input"))
    )
    (net (code "1571") (name "SC1_") (class "Default")
      (node (ref "C21") (pin "H1") (pinfunction "IN3_H1") (pintype "input"))
      (node (ref "C22") (pin "J2") (pinfunction "0_J2") (pintype "output"))
      (node (ref "C40") (pin "M2") (pinfunction "P$2_M2") (pintype "bidirectional"))
      (node (ref "D22") (pin "E2") (pinfunction "IN2_E2") (pintype "input"))
    )
    (net (code "1572") (name "SC2") (class "Default")
      (node (ref "C21") (pin "R2") (pinfunction "IN3_R2") (pintype "input"))
      (node (ref "C22") (pin "L1") (pinfunction "1_L1") (pintype "output"))
      (node (ref "D17") (pin "H1") (pinfunction "IN3_H1") (pintype "input"))
      (node (ref "D19") (pin "A1") (pinfunction "IN1_A1") (pintype "input"))
      (node (ref "D19") (pin "L2") (pinfunction "IN3_L2") (pintype "input"))
      (node (ref "D22") (pin "B1") (pinfunction "IN2_B1") (pintype "input"))
      (node (ref "EF38") (pin "BN1") (pinfunction "BN1_BN1") (pintype "input"))
    )
    (net (code "1573") (name "SC2_") (class "Default")
      (node (ref "C21") (pin "M1") (pinfunction "IN3_M1") (pintype "input"))
      (node (ref "C22") (pin "M1") (pinfunction "0_M1") (pintype "output"))
      (node (ref "C40") (pin "N2") (pinfunction "P$2_N2") (pintype "bidirectional"))
      (node (ref "D22") (pin "F2") (pinfunction "IN3_F2") (pintype "input"))
    )
    (net (code "1574") (name "SC3") (class "Default")
      (node (ref "C18") (pin "H1") (pinfunction "IN1_H1") (pintype "input"))
      (node (ref "C21") (pin "U2") (pinfunction "IN2_U2") (pintype "input"))
      (node (ref "C22") (pin "P2") (pinfunction "1_P2") (pintype "output"))
      (node (ref "D19") (pin "B1") (pinfunction "IN2_B1") (pintype "input"))
      (node (ref "D22") (pin "C1") (pinfunction "IN3_C1") (pintype "input"))
      (node (ref "D23") (pin "C1") (pinfunction "IN1C_C1") (pintype "input"))
      (node (ref "EF39") (pin "BD1") (pinfunction "BD1_BD1") (pintype "input"))
    )
    (net (code "1575") (name "SC3_") (class "Default")
      (node (ref "C21") (pin "P1") (pinfunction "IN1_P1") (pintype "input"))
      (node (ref "C22") (pin "R2") (pinfunction "0_R2") (pintype "output"))
      (node (ref "C40") (pin "L2") (pinfunction "P$2_L2") (pintype "bidirectional"))
      (node (ref "D22") (pin "H2") (pinfunction "IN4_H2") (pintype "input"))
    )
    (net (code "1576") (name "SC4") (class "Default")
      (node (ref "C18") (pin "J1") (pinfunction "IN2_J1") (pintype "input"))
      (node (ref "C21") (pin "S1") (pinfunction "IN3_S1") (pintype "input"))
      (node (ref "C22") (pin "S1") (pinfunction "1_S1") (pintype "output"))
      (node (ref "D19") (pin "C1") (pinfunction "IN3_C1") (pintype "input"))
      (node (ref "D19") (pin "K2") (pinfunction "IN2_K2") (pintype "input"))
      (node (ref "D22") (pin "D1") (pinfunction "IN4_D1") (pintype "input"))
      (node (ref "D23") (pin "D1") (pinfunction "IN1D_D1") (pintype "input"))
      (node (ref "EF39") (pin "BN1") (pinfunction "BN1_BN1") (pintype "input"))
    )
    (net (code "1577") (name "SC4_") (class "Default")
      (node (ref "C18") (pin "M2") (pinfunction "IN2_M2") (pintype "input"))
      (node (ref "C21") (pin "V2") (pinfunction "IN3_V2") (pintype "input"))
      (node (ref "C22") (pin "U1") (pinfunction "0_U1") (pintype "output"))
      (node (ref "C40") (pin "F1") (pinfunction "P$2_F1") (pintype "bidirectional"))
      (node (ref "D13") (pin "R2") (pinfunction "IN2_R2") (pintype "input"))
      (node (ref "D19") (pin "H1") (pinfunction "IN3_H1") (pintype "input"))
      (node (ref "D23") (pin "H2") (pinfunction "IN1D_H2") (pintype "input"))
    )
    (net (code "1578") (name "SCL_") (class "Default")
      (node (ref "D14") (pin "J1") (pinfunction "IN2_J1") (pintype "input"))
      (node (ref "D17") (pin "T2") (pinfunction "IN1_T2") (pintype "input"))
      (node (ref "D19") (pin "S2") (pinfunction "OUT_S2") (pintype "output"))
    )
    (net (code "1579") (name "SC_0_") (class "Default")
      (node (ref "D13") (pin "S2") (pinfunction "OUT_S2") (pintype "output"))
      (node (ref "D13") (pin "T2") (pinfunction "IN1_T2") (pintype "input"))
    )
    (net (code "1580") (name "SC_ENABLE") (class "Default")
      (node (ref "D22") (pin "P2") (pinfunction "OUT_P2") (pintype "open_collector"))
      (node (ref "EF34") (pin "BF2") (pinfunction "BF2_BF2") (pintype "input"))
      (node (ref "EF35") (pin "BF2") (pinfunction "BF2_BF2") (pintype "input"))
      (node (ref "EF36") (pin "BF2") (pinfunction "BF2_BF2") (pintype "input"))
      (node (ref "EF37") (pin "BF2") (pinfunction "BF2_BF2") (pintype "input"))
      (node (ref "EF38") (pin "BF2") (pinfunction "BF2_BF2") (pintype "input"))
      (node (ref "EF39") (pin "BF2") (pinfunction "BF2_BF2") (pintype "input"))
    )
    (net (code "1581") (name "SC_FULL") (class "Default")
      (node (ref "C18") (pin "C1") (pinfunction "OUT_C1") (pintype "output"))
      (node (ref "C21") (pin "B1") (pinfunction "IN2_B1") (pintype "input"))
      (node (ref "D23") (pin "K1") (pinfunction "IN4A_K1") (pintype "input"))
    )
    (net (code "1582") (name "SC_LOAD") (class "Default")
      (node (ref "C22") (pin "B1") (pinfunction "C_B1") (pintype "input"))
      (node (ref "C22") (pin "D2") (pinfunction "C_D2") (pintype "input"))
      (node (ref "C22") (pin "H1") (pinfunction "C_H1") (pintype "input"))
      (node (ref "C22") (pin "L2") (pinfunction "C_L2") (pintype "input"))
      (node (ref "C22") (pin "N1") (pinfunction "C_N1") (pintype "input"))
      (node (ref "D22") (pin "V2") (pinfunction "OUT_V2") (pintype "open_collector"))
    )
    (net (code "1583") (name "SF0") (class "Default")
      (node (ref "A11") (pin "E2") (pinfunction "IN2_E2") (pintype "input"))
      (node (ref "A18") (pin "J1") (pinfunction "IN2_J1") (pintype "input"))
      (node (ref "B19") (pin "E1") (pinfunction "1_E1") (pintype "output"))
    )
    (net (code "1584") (name "SF1") (class "Default")
      (node (ref "A11") (pin "M1") (pinfunction "IN2_M1") (pintype "input"))
      (node (ref "A18") (pin "M2") (pinfunction "IN2_M2") (pintype "input"))
      (node (ref "B19") (pin "H2") (pinfunction "1_H2") (pintype "output"))
    )
    (net (code "1585") (name "SF2") (class "Default")
      (node (ref "A11") (pin "R2") (pinfunction "IN2_R2") (pintype "input"))
      (node (ref "A18") (pin "U2") (pinfunction "IN2_U2") (pintype "input"))
      (node (ref "B19") (pin "L1") (pinfunction "1_L1") (pintype "output"))
    )
    (net (code "1586") (name "SF3") (class "Default")
      (node (ref "A12") (pin "J1") (pinfunction "IN2_J1") (pintype "input"))
      (node (ref "A13") (pin "J2") (pinfunction "IN2_J2") (pintype "input"))
      (node (ref "B19") (pin "P2") (pinfunction "1_P2") (pintype "output"))
    )
    (net (code "1587") (name "SF4") (class "Default")
      (node (ref "A12") (pin "M2") (pinfunction "IN2_M2") (pintype "input"))
      (node (ref "A13") (pin "M2") (pinfunction "IN2_M2") (pintype "input"))
      (node (ref "B19") (pin "S1") (pinfunction "1_S1") (pintype "output"))
    )
    (net (code "1588") (name "SF5") (class "Default")
      (node (ref "A12") (pin "U2") (pinfunction "IN2_U2") (pintype "input"))
      (node (ref "A13") (pin "R2") (pinfunction "IN2_R2") (pintype "input"))
      (node (ref "B19") (pin "V2") (pinfunction "1_V2") (pintype "output"))
    )
    (net (code "1589") (name "SF_ENABLE") (class "Default")
      (node (ref "A12") (pin "H1") (pinfunction "IN1_H1") (pintype "input"))
      (node (ref "A12") (pin "L2") (pinfunction "IN1_L2") (pintype "input"))
      (node (ref "A12") (pin "T2") (pinfunction "IN1_T2") (pintype "input"))
      (node (ref "A15") (pin "N2") (pinfunction "OUT_N2") (pintype "output"))
      (node (ref "A18") (pin "H1") (pinfunction "IN1_H1") (pintype "input"))
      (node (ref "A18") (pin "L2") (pinfunction "IN1_L2") (pintype "input"))
      (node (ref "A18") (pin "T2") (pinfunction "IN1_T2") (pintype "input"))
      (node (ref "B06") (pin "R1") (pinfunction "IN2_R1") (pintype "input"))
    )
    (net (code "1590") (name "SHUT_DOWN_") (class "Default")
      (node (ref "A04") (pin "U2") (pinfunction "U2_U2") (pintype "input"))
      (node (ref "AB02") (pin "AF2") (pinfunction "AF2_AF2") (pintype "output"))
    )
    (net (code "1591") (name "SINT") (class "Default")
      (node (ref "A05") (pin "V2") (pinfunction "OUT_V2") (pintype "output"))
      (node (ref "B04") (pin "L2") (pinfunction "IN3_L2") (pintype "input"))
    )
    (net (code "1592") (name "SKIP_") (class "Default")
      (node (ref "B04") (pin "U2") (pinfunction "IN2_U2") (pintype "input"))
      (node (ref "E18") (pin "S1") (pinfunction "1_S1") (pintype "output"))
      (node (ref "F25") (pin "U2") (pinfunction "IN2_U2") (pintype "input"))
    )
    (net (code "1593") (name "SKIP_OR") (class "Default")
      (node (ref "B04") (pin "V1") (pinfunction "OUT_V1") (pintype "output"))
      (node (ref "E27") (pin "L1") (pinfunction "IN4B_L1") (pintype "input"))
    )
    (net (code "1594") (name "SLICE") (class "Default")
      (node (ref "A30") (pin "S2") (pinfunction "S2_S2") (pintype "passive"))
      (node (ref "A31") (pin "S2") (pinfunction "S2_S2") (pintype "passive"))
      (node (ref "A32") (pin "S2") (pinfunction "S2_S2") (pintype "passive"))
      (node (ref "A33") (pin "S2") (pinfunction "S2_S2") (pintype "passive"))
      (node (ref "B31") (pin "S2") (pinfunction "S2_S2") (pintype "passive"))
      (node (ref "B32") (pin "S2") (pinfunction "S2_S2") (pintype "passive"))
      (node (ref "B33") (pin "S2") (pinfunction "S2_S2") (pintype "passive"))
    )
    (net (code "1595") (name "SLOW_CYCLE") (class "Default")
      (node (ref "E12") (pin "N1") (pinfunction "OUT_N1") (pintype "output"))
      (node (ref "E15") (pin "R1") (pinfunction "IN2_R1") (pintype "input"))
    )
    (net (code "1596") (name "SLOW_CYCLE_") (class "Default")
      (node (ref "E12") (pin "M1") (pinfunction "IN2_M1") (pintype "input"))
      (node (ref "E14") (pin "M1") (pinfunction "IN3_M1") (pintype "input"))
      (node (ref "F19") (pin "E1") (pinfunction "OUT_E1") (pintype "output"))
    )
    (net (code "1597") (name "SPECIAL_CYCLE_") (class "Default")
      (node (ref "E24") (pin "K1") (pinfunction "OUT_K1") (pintype "output"))
      (node (ref "F23") (pin "M1") (pinfunction "IN1_M1") (pintype "input"))
      (node (ref "F23") (pin "M2") (pinfunction "IN3_M2") (pintype "input"))
    )
    (net (code "1598") (name "SR00") (class "Default")
      (node (ref "A40") (pin "L2") (pinfunction "P$2_L2") (pintype "bidirectional"))
      (node (ref "EF34") (pin "BE1") (pinfunction "BE1_BE1") (pintype "input"))
    )
    (net (code "1599") (name "SR01") (class "Default")
      (node (ref "A40") (pin "M2") (pinfunction "P$2_M2") (pintype "bidirectional"))
      (node (ref "EF34") (pin "BD2") (pinfunction "BD2_BD2") (pintype "input"))
    )
    (net (code "1600") (name "SR02") (class "Default")
      (node (ref "A40") (pin "R2") (pinfunction "P$2_R2") (pintype "bidirectional"))
      (node (ref "EF35") (pin "BE1") (pinfunction "BE1_BE1") (pintype "input"))
    )
    (net (code "1601") (name "SR03") (class "Default")
      (node (ref "A40") (pin "S2") (pinfunction "P$2_S2") (pintype "bidirectional"))
      (node (ref "EF35") (pin "BD2") (pinfunction "BD2_BD2") (pintype "input"))
    )
    (net (code "1602") (name "SR04") (class "Default")
      (node (ref "A40") (pin "T2") (pinfunction "P$2_T2") (pintype "bidirectional"))
      (node (ref "EF36") (pin "BE1") (pinfunction "BE1_BE1") (pintype "input"))
    )
    (net (code "1603") (name "SR05") (class "Default")
      (node (ref "A40") (pin "U2") (pinfunction "P$2_U2") (pintype "bidirectional"))
      (node (ref "EF36") (pin "BD2") (pinfunction "BD2_BD2") (pintype "input"))
    )
    (net (code "1604") (name "SR06") (class "Default")
      (node (ref "A40") (pin "V2") (pinfunction "P$2_V2") (pintype "bidirectional"))
      (node (ref "EF37") (pin "BE1") (pinfunction "BE1_BE1") (pintype "input"))
    )
    (net (code "1605") (name "SR07") (class "Default")
      (node (ref "B40") (pin "D2") (pinfunction "P$2_D2") (pintype "bidirectional"))
      (node (ref "EF37") (pin "BD2") (pinfunction "BD2_BD2") (pintype "input"))
    )
    (net (code "1606") (name "SR08") (class "Default")
      (node (ref "B40") (pin "E2") (pinfunction "P$2_E2") (pintype "bidirectional"))
      (node (ref "EF38") (pin "BE1") (pinfunction "BE1_BE1") (pintype "input"))
    )
    (net (code "1607") (name "SR09") (class "Default")
      (node (ref "B40") (pin "F2") (pinfunction "P$2_F2") (pintype "bidirectional"))
      (node (ref "EF38") (pin "BD2") (pinfunction "BD2_BD2") (pintype "input"))
    )
    (net (code "1608") (name "SR10") (class "Default")
      (node (ref "B40") (pin "H2") (pinfunction "P$2_H2") (pintype "bidirectional"))
      (node (ref "EF39") (pin "BE1") (pinfunction "BE1_BE1") (pintype "input"))
    )
    (net (code "1609") (name "SR11") (class "Default")
      (node (ref "B40") (pin "J2") (pinfunction "P$2_J2") (pintype "bidirectional"))
      (node (ref "EF39") (pin "BD2") (pinfunction "BD2_BD2") (pintype "input"))
    )
    (net (code "1610") (name "SR_ENABLE") (class "Default")
      (node (ref "A12") (pin "D1") (pinfunction "IN1_D1") (pintype "input"))
      (node (ref "A12") (pin "H2") (pinfunction "IN1_H2") (pintype "input"))
      (node (ref "A12") (pin "P1") (pinfunction "IN1_P1") (pintype "input"))
      (node (ref "A18") (pin "D1") (pinfunction "IN1_D1") (pintype "input"))
      (node (ref "A18") (pin "H2") (pinfunction "IN1_H2") (pintype "input"))
      (node (ref "A18") (pin "P1") (pinfunction "IN1_P1") (pintype "input"))
      (node (ref "EF34") (pin "BC1") (pinfunction "BC1_BC1") (pintype "input"))
      (node (ref "EF35") (pin "BC1") (pinfunction "BC1_BC1") (pintype "input"))
      (node (ref "EF36") (pin "BC1") (pinfunction "BC1_BC1") (pintype "input"))
      (node (ref "EF37") (pin "BC1") (pinfunction "BC1_BC1") (pintype "input"))
      (node (ref "EF38") (pin "BC1") (pinfunction "BC1_BC1") (pintype "input"))
      (node (ref "EF39") (pin "BC1") (pinfunction "BC1_BC1") (pintype "input"))
      (node (ref "F30") (pin "S1") (pinfunction "OUT_S1") (pintype "open_collector"))
    )
    (net (code "1611") (name "STOP_COMPLETE") (class "Default")
      (node (ref "HJ26") (pin "BN2") (pinfunction "BN2_BN2") (pintype "input"))
      (node (ref "HJ27") (pin "BR2") (pinfunction "BR_BR2") (pintype "output"))
    )
    (net (code "1612") (name "STOP_OK") (class "Default")
      (node (ref "A04") (pin "P2") (pinfunction "P2_P2") (pintype "output"))
      (node (ref "AB02") (pin "AH2") (pinfunction "AH2_AH2") (pintype "input"))
      (node (ref "E13") (pin "K1") (pinfunction "IN4A_K1") (pintype "input"))
    )
    (net (code "1613") (name "STORE_") (class "Default")
      (node (ref "D07") (pin "D2") (pinfunction "IN1_D2") (pintype "input"))
      (node (ref "D09") (pin "P1") (pinfunction "IN1_P1") (pintype "input"))
      (node (ref "D10") (pin "S1") (pinfunction "OUT_S1") (pintype "output"))
      (node (ref "F31") (pin "C1") (pinfunction "IN3_C1") (pintype "input"))
    )
    (net (code "1614") (name "STROBE_") (class "Default")
      (node (ref "B10") (pin "E2") (pinfunction "E2_E2") (pintype "open_collector"))
      (node (ref "B23") (pin "T2") (pinfunction "T_T2") (pintype "open_collector"))
      (node (ref "B24") (pin "T2") (pinfunction "T_T2") (pintype "open_collector"))
      (node (ref "E15") (pin "H2") (pinfunction "IN1_H2") (pintype "input"))
      (node (ref "E18") (pin "A1") (pinfunction "R_A1") (pintype "input"))
      (node (ref "E19") (pin "D1") (pinfunction "S_D1") (pintype "input"))
      (node (ref "EF10") (pin "BE2") (pinfunction "P$1_BE2") (pintype "passive"))
      (node (ref "F20") (pin "D1") (pinfunction "IN1_D1") (pintype "input"))
      (node (ref "H05") (pin "P2") (pinfunction "P$2_P2") (pintype "bidirectional"))
    )
    (net (code "1615") (name "STROBE_FIELD0") (class "Default")
      (node (ref "A30") (pin "D1") (pinfunction "D1_D1") (pintype "input"))
      (node (ref "A31") (pin "D1") (pinfunction "D1_D1") (pintype "input"))
      (node (ref "A32") (pin "D1") (pinfunction "D1_D1") (pintype "input"))
      (node (ref "A33") (pin "D1") (pinfunction "D1_D1") (pintype "input"))
      (node (ref "B23") (pin "S2") (pinfunction "S_S2") (pintype "output"))
      (node (ref "B31") (pin "D1") (pinfunction "D1_D1") (pintype "input"))
      (node (ref "B32") (pin "D1") (pinfunction "D1_D1") (pintype "input"))
      (node (ref "B33") (pin "D1") (pinfunction "D1_D1") (pintype "input"))
    )
    (net (code "1616") (name "STROBE_FIELD1") (class "Default")
      (node (ref "A30") (pin "R1") (pinfunction "R1_R1") (pintype "input"))
      (node (ref "A31") (pin "R1") (pinfunction "R1_R1") (pintype "input"))
      (node (ref "A32") (pin "R1") (pinfunction "R1_R1") (pintype "input"))
      (node (ref "A33") (pin "R1") (pinfunction "R1_R1") (pintype "input"))
      (node (ref "B24") (pin "S2") (pinfunction "S_S2") (pintype "output"))
      (node (ref "B31") (pin "R1") (pinfunction "R1_R1") (pintype "input"))
      (node (ref "B32") (pin "R1") (pinfunction "R1_R1") (pintype "input"))
      (node (ref "B33") (pin "R1") (pinfunction "R1_R1") (pintype "input"))
    )
    (net (code "1617") (name "SYNC_PUN") (class "Default")
      (node (ref "C01") (pin "F2") (pinfunction "P$2_F2") (pintype "bidirectional"))
      (node (ref "HJ28") (pin "AV2") (pinfunction "AV2_AV2") (pintype "input"))
    )
    (net (code "1618") (name "S_") (class "Default")
      (node (ref "D09") (pin "R2") (pinfunction "IN3_R2") (pintype "input"))
      (node (ref "D11") (pin "E1") (pinfunction "1_E1") (pintype "output"))
      (node (ref "E09") (pin "A1") (pinfunction "IN1_A1") (pintype "input"))
      (node (ref "E09") (pin "D2") (pinfunction "IN1_D2") (pintype "input"))
    )
    (net (code "1619") (name "S_FEED_HOLE") (class "Default")
      (node (ref "D01") (pin "N2") (pinfunction "P$2_N2") (pintype "bidirectional"))
      (node (ref "HJ26") (pin "BM2") (pinfunction "BM2_BM2") (pintype "input"))
    )
    (net (code "1620") (name "S_SET_") (class "Default")
      (node (ref "C11") (pin "C1") (pinfunction "IN3_C1") (pintype "input"))
      (node (ref "D10") (pin "E1") (pinfunction "OUT_E1") (pintype "output"))
      (node (ref "D11") (pin "C1") (pinfunction "D_C1") (pintype "input"))
    )
    (net (code "1621") (name "S_UF") (class "Default")
      (node (ref "A05") (pin "J2") (pinfunction "IN2_J2") (pintype "input"))
      (node (ref "B05") (pin "S1") (pinfunction "1_S1") (pintype "output"))
      (node (ref "B06") (pin "P1") (pinfunction "IN1_P1") (pintype "input"))
    )
    (net (code "1622") (name "TAD") (class "Default")
      (node (ref "E22") (pin "F1") (pinfunction "OUT_F1") (pintype "output"))
      (node (ref "F28") (pin "A1") (pinfunction "IN1_A1") (pintype "input"))
    )
    (net (code "1623") (name "TAD_") (class "Default")
      (node (ref "D40") (pin "T2") (pinfunction "P$2_T2") (pintype "bidirectional"))
      (node (ref "E21") (pin "D1") (pinfunction "OUT_D1") (pintype "output"))
      (node (ref "E22") (pin "D1") (pinfunction "IN1_D1") (pintype "input"))
      (node (ref "F26") (pin "U2") (pinfunction "IN2_U2") (pintype "input"))
    )
    (net (code "1624") (name "TELEPRINTER_FLAG_") (class "Default")
      (node (ref "EF02") (pin "BK2") (pinfunction "BK2_BK2") (pintype "output"))
      (node (ref "F19") (pin "R1") (pinfunction "IN4_R1") (pintype "input"))
    )
    (net (code "1625") (name "TP1") (class "Default")
      (node (ref "D07") (pin "U2") (pinfunction "IN2_U2") (pintype "input"))
      (node (ref "E09") (pin "B1") (pinfunction "IN2_B1") (pintype "input"))
      (node (ref "E15") (pin "K2") (pinfunction "OUT_K2") (pintype "output"))
      (node (ref "E20") (pin "L2") (pinfunction "C_L2") (pintype "input"))
      (node (ref "E26") (pin "E1") (pinfunction "IN2A_E1") (pintype "input"))
      (node (ref "E26") (pin "S1") (pinfunction "IN1A_S1") (pintype "input"))
    )
    (net (code "1626") (name "TP2") (class "Default")
      (node (ref "E15") (pin "L1") (pinfunction "IN1_L1") (pintype "input"))
      (node (ref "E17") (pin "F1") (pinfunction "OUT_F1") (pintype "output"))
      (node (ref "E19") (pin "B1") (pinfunction "C_B1") (pintype "input"))
      (node (ref "E22") (pin "L1") (pinfunction "IN1_L1") (pintype "input"))
      (node (ref "E33") (pin "D2") (pinfunction "C_D2") (pintype "input"))
      (node (ref "F25") (pin "P2") (pinfunction "IN1_P2") (pintype "input"))
      (node (ref "F32") (pin "J1") (pinfunction "IN2_J1") (pintype "input"))
    )
    (net (code "1627") (name "TP2E_") (class "Default")
      (node (ref "B04") (pin "K1") (pinfunction "IN1_K1") (pintype "input"))
      (node (ref "B04") (pin "L1") (pinfunction "IN2_L1") (pintype "input"))
      (node (ref "E25") (pin "R1") (pinfunction "IN2_R1") (pintype "input"))
      (node (ref "F25") (pin "S2") (pinfunction "OUT_S2") (pintype "output"))
    )
    (net (code "1628") (name "TP3") (class "Default")
      (node (ref "A13") (pin "D2") (pinfunction "IN1_D2") (pintype "input"))
      (node (ref "A14") (pin "P2") (pinfunction "IN1_P2") (pintype "input"))
      (node (ref "A19") (pin "L1") (pinfunction "IN1_L1") (pintype "input"))
      (node (ref "A20") (pin "B1") (pinfunction "IN2_B1") (pintype "input"))
      (node (ref "B04") (pin "K2") (pinfunction "IN2_K2") (pintype "input"))
      (node (ref "B05") (pin "L2") (pinfunction "C_L2") (pintype "input"))
      (node (ref "B09") (pin "T2") (pinfunction "IN1_T2") (pintype "input"))
      (node (ref "B10") (pin "V2") (pinfunction "V2_V2") (pintype "input"))
      (node (ref "C08") (pin "J2") (pinfunction "IN2_J2") (pintype "input"))
      (node (ref "D09") (pin "U2") (pinfunction "IN2_U2") (pintype "input"))
      (node (ref "D12") (pin "P2") (pinfunction "IN1_P2") (pintype "input"))
      (node (ref "D14") (pin "P2") (pinfunction "IN1_P2") (pintype "input"))
      (node (ref "D14") (pin "T2") (pinfunction "IN1_T2") (pintype "input"))
      (node (ref "D17") (pin "U2") (pinfunction "IN2_U2") (pintype "input"))
      (node (ref "D18") (pin "M1") (pinfunction "IN3_M1") (pintype "input"))
      (node (ref "E14") (pin "K1") (pinfunction "IN1_K1") (pintype "input"))
      (node (ref "E15") (pin "P1") (pinfunction "IN1_P1") (pintype "input"))
      (node (ref "E17") (pin "J1") (pinfunction "OUT_J1") (pintype "output"))
      (node (ref "E18") (pin "L2") (pinfunction "C_L2") (pintype "input"))
      (node (ref "E19") (pin "D2") (pinfunction "C_D2") (pintype "input"))
      (node (ref "E25") (pin "T2") (pinfunction "IN1_T2") (pintype "input"))
      (node (ref "E26") (pin "A1") (pinfunction "IN1A_A1") (pintype "input"))
      (node (ref "E26") (pin "E2") (pinfunction "IN1B_E2") (pintype "input"))
      (node (ref "E26") (pin "H1") (pinfunction "IN3A_H1") (pintype "input"))
      (node (ref "E26") (pin "M1") (pinfunction "IN5A_M1") (pintype "input"))
      (node (ref "E26") (pin "P2") (pinfunction "IN4B_P2") (pintype "input"))
      (node (ref "F26") (pin "N2") (pinfunction "IN1_N2") (pintype "input"))
    )
    (net (code "1629") (name "TP4") (class "Default")
      (node (ref "D11") (pin "B1") (pinfunction "C_B1") (pintype "input"))
      (node (ref "D11") (pin "D2") (pinfunction "C_D2") (pintype "input"))
      (node (ref "E15") (pin "F2") (pinfunction "OUT_F2") (pintype "output"))
      (node (ref "E18") (pin "B1") (pinfunction "C_B1") (pintype "input"))
      (node (ref "E19") (pin "H1") (pinfunction "C_H1") (pintype "input"))
      (node (ref "E23") (pin "B1") (pinfunction "C_B1") (pintype "input"))
      (node (ref "E23") (pin "D2") (pinfunction "C_D2") (pintype "input"))
      (node (ref "E23") (pin "H1") (pinfunction "C_H1") (pintype "input"))
      (node (ref "E23") (pin "L2") (pinfunction "C_L2") (pintype "input"))
      (node (ref "E23") (pin "N1") (pinfunction "C_N1") (pintype "input"))
      (node (ref "E23") (pin "S2") (pinfunction "C_S2") (pintype "input"))
      (node (ref "E24") (pin "H2") (pinfunction "IN1_H2") (pintype "input"))
      (node (ref "E33") (pin "B1") (pinfunction "C_B1") (pintype "input"))
      (node (ref "F32") (pin "D2") (pinfunction "IN1_D2") (pintype "input"))
    )
    (net (code "1630") (name "TS1") (class "Default")
      (node (ref "C07") (pin "V2") (pinfunction "IN1_V2") (pintype "input"))
      (node (ref "E18") (pin "E1") (pinfunction "1_E1") (pintype "output"))
      (node (ref "E27") (pin "E1") (pinfunction "IN2A_E1") (pintype "input"))
      (node (ref "E30") (pin "E1") (pinfunction "IN2A_E1") (pintype "input"))
    )
    (net (code "1631") (name "TS1_") (class "Default")
      (node (ref "E18") (pin "F1") (pinfunction "0_F1") (pintype "output"))
      (node (ref "H12") (pin "N2") (pinfunction "IN2_N2") (pintype "input"))
    )
    (net (code "1632") (name "TS2") (class "Default")
      (node (ref "C11") (pin "H1") (pinfunction "IN3_H1") (pintype "input"))
      (node (ref "C11") (pin "J2") (pinfunction "IN1_J2") (pintype "input"))
      (node (ref "D09") (pin "B1") (pinfunction "IN2_B1") (pintype "input"))
      (node (ref "D10") (pin "F1") (pinfunction "IN1_F1") (pintype "input"))
      (node (ref "E19") (pin "E1") (pinfunction "1_E1") (pintype "output"))
      (node (ref "E27") (pin "A1") (pinfunction "IN1A_A1") (pintype "input"))
      (node (ref "E27") (pin "P2") (pinfunction "IN4B_P2") (pintype "input"))
      (node (ref "E28") (pin "D2") (pinfunction "IN1A_D2") (pintype "input"))
      (node (ref "E29") (pin "E1") (pinfunction "IN2A_E1") (pintype "input"))
      (node (ref "E30") (pin "P2") (pinfunction "IN4B_P2") (pintype "input"))
      (node (ref "F28") (pin "E1") (pinfunction "IN1_E1") (pintype "input"))
      (node (ref "F28") (pin "K1") (pinfunction "IN1_K1") (pintype "input"))
    )
    (net (code "1633") (name "TS3") (class "Default")
      (node (ref "C11") (pin "K1") (pinfunction "IN1_K1") (pintype "input"))
      (node (ref "C11") (pin "N2") (pinfunction "IN1_N2") (pintype "input"))
      (node (ref "C12") (pin "E2") (pinfunction "IN2_E2") (pintype "input"))
      (node (ref "D09") (pin "D2") (pinfunction "IN1_D2") (pintype "input"))
      (node (ref "D10") (pin "P1") (pinfunction "IN3_P1") (pintype "input"))
      (node (ref "D10") (pin "T2") (pinfunction "IN3_T2") (pintype "input"))
      (node (ref "E19") (pin "H2") (pinfunction "1_H2") (pintype "output"))
      (node (ref "E27") (pin "M1") (pinfunction "IN5A_M1") (pintype "input"))
      (node (ref "E29") (pin "A1") (pinfunction "IN1A_A1") (pintype "input"))
      (node (ref "E30") (pin "M1") (pinfunction "IN5A_M1") (pintype "input"))
      (node (ref "F26") (pin "R1") (pinfunction "IN2_R1") (pintype "input"))
      (node (ref "F27") (pin "A1") (pinfunction "IN1_A1") (pintype "input"))
      (node (ref "F27") (pin "H1") (pinfunction "IN2_H1") (pintype "input"))
      (node (ref "F27") (pin "S2") (pinfunction "IN2_S2") (pintype "input"))
      (node (ref "F28") (pin "B1") (pinfunction "IN2_B1") (pintype "input"))
    )
    (net (code "1634") (name "TS3_") (class "Default")
      (node (ref "E19") (pin "J2") (pinfunction "0_J2") (pintype "output"))
      (node (ref "H12") (pin "H2") (pinfunction "IN2_H2") (pintype "input"))
    )
    (net (code "1635") (name "TS4") (class "Default")
      (node (ref "C12") (pin "L2") (pinfunction "IN2_L2") (pintype "input"))
      (node (ref "E19") (pin "L1") (pinfunction "1_L1") (pintype "output"))
      (node (ref "E29") (pin "K1") (pinfunction "IN4A_K1") (pintype "input"))
      (node (ref "E29") (pin "M1") (pinfunction "IN5A_M1") (pintype "input"))
      (node (ref "E30") (pin "H1") (pinfunction "IN3A_H1") (pintype "input"))
      (node (ref "F27") (pin "D2") (pinfunction "IN1_D2") (pintype "input"))
      (node (ref "F29") (pin "L1") (pinfunction "IN1_L1") (pintype "input"))
      (node (ref "F32") (pin "L1") (pinfunction "IN1_L1") (pintype "input"))
    )
    (net (code "1636") (name "TS4_") (class "Default")
      (node (ref "A19") (pin "J1") (pinfunction "IN2_J1") (pintype "input"))
      (node (ref "E19") (pin "M1") (pinfunction "0_M1") (pintype "output"))
    )
    (net (code "1637") (name "TT0_") (class "Default")
      (node (ref "EF01") (pin "AK2") (pinfunction "AK2_AK2") (pintype "output"))
      (node (ref "J13") (pin "P1") (pinfunction "IN3_P1") (pintype "input"))
    )
    (net (code "1638") (name "TT1_") (class "Default")
      (node (ref "EF01") (pin "AR2") (pinfunction "AR2_AR2") (pintype "output"))
      (node (ref "J13") (pin "T2") (pinfunction "IN3_T2") (pintype "input"))
    )
    (net (code "1639") (name "TT2_") (class "Default")
      (node (ref "EF01") (pin "AS2") (pinfunction "AS2_AS2") (pintype "output"))
      (node (ref "J14") (pin "C1") (pinfunction "IN3_C1") (pintype "input"))
    )
    (net (code "1640") (name "TT3_") (class "Default")
      (node (ref "EF01") (pin "AL1") (pinfunction "AL1_AL1") (pintype "output"))
      (node (ref "J14") (pin "F2") (pinfunction "IN3_F2") (pintype "input"))
    )
    (net (code "1641") (name "TT4_") (class "Default")
      (node (ref "EF01") (pin "AM1") (pinfunction "AM1_AM1") (pintype "output"))
      (node (ref "J14") (pin "J1") (pinfunction "IN3_J1") (pintype "input"))
    )
    (net (code "1642") (name "TT5_") (class "Default")
      (node (ref "EF01") (pin "AP2") (pinfunction "AP2_AP2") (pintype "output"))
      (node (ref "J14") (pin "M2") (pinfunction "IN3_M2") (pintype "input"))
    )
    (net (code "1643") (name "TT6_") (class "Default")
      (node (ref "EF01") (pin "AT2") (pinfunction "AT2_AT2") (pintype "output"))
      (node (ref "J14") (pin "P1") (pinfunction "IN3_P1") (pintype "input"))
    )
    (net (code "1644") (name "TT7_") (class "Default")
      (node (ref "EF01") (pin "AN2") (pinfunction "AN2_AN2") (pintype "output"))
      (node (ref "J14") (pin "T2") (pinfunction "IN3_T2") (pintype "input"))
    )
    (net (code "1645") (name "TTI2") (class "Default")
      (node (ref "EF01") (pin "AJ2") (pinfunction "AJ2_AJ2") (pintype "output"))
      (node (ref "EF01") (pin "AK1") (pinfunction "AK1_AK1") (pintype "input"))
    )
    (net (code "1646") (name "TTI_CLOCK") (class "Default")
      (node (ref "EF01") (pin "AN1") (pinfunction "AN1_AN1") (pintype "input"))
      (node (ref "F03") (pin "R2") (pinfunction "R2_R2") (pintype "output"))
    )
    (net (code "1647") (name "TTI_DATA") (class "Default")
      (node (ref "EF01") (pin "AM2") (pinfunction "AM2_AM2") (pintype "output"))
      (node (ref "EF01") (pin "AR1") (pinfunction "AR1_AR1") (pintype "input"))
    )
    (net (code "1648") (name "TTI_SKIP_") (class "Default")
      (node (ref "EF01") (pin "BH2") (pinfunction "BH2_BH2") (pintype "output"))
      (node (ref "F19") (pin "K2") (pinfunction "IN1_K2") (pintype "input"))
    )
    (net (code "1649") (name "TTO_CLOCK_") (class "Default")
      (node (ref "EF02") (pin "BP2") (pinfunction "BP2_BP2") (pintype "input"))
      (node (ref "F03") (pin "K2") (pinfunction "K2_K2") (pintype "output"))
    )
    (net (code "1650") (name "TTO_SKIP_") (class "Default")
      (node (ref "EF02") (pin "BJ2") (pinfunction "BJ2_BJ2") (pintype "output"))
      (node (ref "F19") (pin "L2") (pinfunction "IN2_L2") (pintype "input"))
    )
    (net (code "1651") (name "TT_AC_CLR_") (class "Default")
      (node (ref "EF01") (pin "BE2") (pinfunction "BE2_BE2") (pintype "output"))
      (node (ref "J15") (pin "J1") (pinfunction "IN3_J1") (pintype "input"))
    )
    (net (code "1652") (name "TT_AC_LOAD_") (class "Default")
      (node (ref "D09") (pin "V1") (pinfunction "OUT_V1") (pintype "output"))
      (node (ref "E32") (pin "M2") (pinfunction "IN3_M2") (pintype "input"))
    )
    (net (code "1653") (name "TT_CARRY_INSERT") (class "Default")
      (node (ref "C09") (pin "P1") (pinfunction "IN1_P1") (pintype "input"))
      (node (ref "D09") (pin "N1") (pinfunction "OUT_N1") (pintype "output"))
      (node (ref "E26") (pin "J1") (pinfunction "IN3B_J1") (pintype "input"))
    )
    (net (code "1654") (name "TT_CARRY_INSERT_") (class "Default")
      (node (ref "C09") (pin "S1") (pinfunction "OUT_S1") (pintype "output"))
      (node (ref "E31") (pin "P1") (pinfunction "IN3_P1") (pintype "input"))
      (node (ref "F09") (pin "N2") (pinfunction "IN8_N2") (pintype "input"))
      (node (ref "F27") (pin "N2") (pinfunction "IN4_N2") (pintype "input"))
    )
    (net (code "1655") (name "TT_CARRY_INSERT_C_") (class "Default")
      (node (ref "D09") (pin "H2") (pinfunction "OUT_H2") (pintype "output"))
      (node (ref "D09") (pin "K1") (pinfunction "IN1_K1") (pintype "input"))
    )
    (net (code "1656") (name "TT_CARRY_INSERT_S") (class "Default")
      (node (ref "C09") (pin "S2") (pinfunction "OUT_S2") (pintype "output"))
      (node (ref "EF39") (pin "BE2") (pinfunction "BE2_BE2") (pintype "input"))
    )
    (net (code "1657") (name "TT_CARRY_INSERT_S_") (class "Default")
      (node (ref "C09") (pin "P2") (pinfunction "IN1_P2") (pintype "input"))
      (node (ref "C11") (pin "S2") (pinfunction "OUT_S2") (pintype "output"))
      (node (ref "D09") (pin "L1") (pinfunction "IN2_L1") (pintype "input"))
    )
    (net (code "1658") (name "TT_CYCLE_") (class "Default")
      (node (ref "C10") (pin "N1") (pinfunction "OUT_N1") (pintype "output"))
      (node (ref "F28") (pin "V2") (pinfunction "IN3_V2") (pintype "input"))
    )
    (net (code "1659") (name "TT_DATA") (class "Default")
      (node (ref "C10") (pin "N2") (pinfunction "OUT_N2") (pintype "output"))
      (node (ref "F33") (pin "H2") (pinfunction "IN1D_H2") (pintype "input"))
    )
    (net (code "1660") (name "TT_INCREMENT_") (class "Default")
      (node (ref "D10") (pin "L1") (pinfunction "OUT_L1") (pintype "output"))
      (node (ref "F25") (pin "E2") (pinfunction "IN2_E2") (pintype "input"))
      (node (ref "F25") (pin "J1") (pinfunction "IN2_J1") (pintype "input"))
      (node (ref "F25") (pin "J2") (pinfunction "IN2_J2") (pintype "input"))
    )
    (net (code "1661") (name "TT_INST") (class "Default")
      (node (ref "C10") (pin "F2") (pinfunction "OUT_F2") (pintype "output"))
      (node (ref "C11") (pin "M1") (pinfunction "IN3_M1") (pintype "input"))
      (node (ref "D10") (pin "A1") (pinfunction "IN1_A1") (pintype "input"))
    )
    (net (code "1662") (name "TT_INST_") (class "Default")
      (node (ref "C10") (pin "E2") (pinfunction "IN2_E2") (pintype "input"))
      (node (ref "C10") (pin "M1") (pinfunction "IN2_M1") (pintype "input"))
      (node (ref "D09") (pin "P2") (pinfunction "IN2_P2") (pintype "input"))
      (node (ref "D10") (pin "P2") (pinfunction "OUT_P2") (pintype "output"))
      (node (ref "F19") (pin "C1") (pinfunction "IN3_C1") (pintype "input"))
      (node (ref "F28") (pin "S1") (pinfunction "IN3_S1") (pintype "input"))
      (node (ref "F33") (pin "F2") (pinfunction "IN1C_F2") (pintype "input"))
      (node (ref "H19") (pin "N2") (pinfunction "IN2_N2") (pintype "input"))
    )
    (net (code "1663") (name "TT_INT_") (class "Default")
      (node (ref "E12") (pin "V2") (pinfunction "OUT_V2") (pintype "output"))
      (node (ref "J15") (pin "F2") (pinfunction "IN3_F2") (pintype "input"))
    )
    (net (code "1664") (name "TT_IO_ENABLE_") (class "Default")
      (node (ref "C11") (pin "F2") (pinfunction "IN3_F2") (pintype "input"))
      (node (ref "C11") (pin "N1") (pinfunction "OUT_N1") (pintype "output"))
      (node (ref "D09") (pin "S1") (pinfunction "IN3_S1") (pintype "input"))
      (node (ref "F30") (pin "H2") (pinfunction "IN4_H2") (pintype "input"))
    )
    (net (code "1665") (name "TT_LINE_SHIFT_") (class "Default")
      (node (ref "C09") (pin "D2") (pinfunction "IN1_D2") (pintype "input"))
      (node (ref "C11") (pin "M2") (pinfunction "OUT_M2") (pintype "output"))
      (node (ref "EF34") (pin "AB2") (pinfunction "AB2_AB2") (pintype "input"))
      (node (ref "EF35") (pin "AB2") (pinfunction "AB2_AB2") (pintype "input"))
      (node (ref "EF36") (pin "AB2") (pinfunction "AB2_AB2") (pintype "input"))
      (node (ref "EF37") (pin "AB2") (pinfunction "AB2_AB2") (pintype "input"))
      (node (ref "EF38") (pin "AB2") (pinfunction "AB2_AB2") (pintype "input"))
      (node (ref "EF39") (pin "AB2") (pinfunction "AB2_AB2") (pintype "input"))
    )
    (net (code "1666") (name "TT_L_DISABLE") (class "Default")
      (node (ref "C10") (pin "L1") (pinfunction "IN1_L1") (pintype "input"))
      (node (ref "D09") (pin "S2") (pinfunction "OUT_S2") (pintype "output"))
      (node (ref "E28") (pin "J1") (pinfunction "IN3B_J1") (pintype "input"))
    )
    (net (code "1667") (name "TT_RIGHT_SHIFT_ENABLE") (class "Default")
      (node (ref "C10") (pin "E1") (pinfunction "IN2_E1") (pintype "input"))
      (node (ref "C11") (pin "H2") (pinfunction "OUT_H2") (pintype "output"))
    )
    (net (code "1668") (name "TT_RIGHT_SHIFT_ENABLE_") (class "Default")
      (node (ref "C09") (pin "E2") (pinfunction "IN2_E2") (pintype "input"))
      (node (ref "C10") (pin "F1") (pinfunction "OUT_F1") (pintype "output"))
      (node (ref "E31") (pin "H1") (pinfunction "IN2_H1") (pintype "input"))
    )
    (net (code "1669") (name "TT_SET_") (class "Default")
      (node (ref "C10") (pin "C1") (pinfunction "OUT_C1") (pintype "output"))
      (node (ref "E25") (pin "E1") (pinfunction "IN1_E1") (pintype "input"))
      (node (ref "F28") (pin "L2") (pinfunction "IN3_L2") (pintype "input"))
    )
    (net (code "1670") (name "TT_SHIFT_ENABLE") (class "Default")
      (node (ref "C09") (pin "F2") (pinfunction "OUT_F2") (pintype "output"))
      (node (ref "C09") (pin "H1") (pinfunction "IN1_H1") (pintype "input"))
      (node (ref "F33") (pin "E2") (pinfunction "IN1B_E2") (pintype "input"))
    )
    (net (code "1671") (name "TT_SHIFT_ENABLE_") (class "Default")
      (node (ref "C09") (pin "K1") (pinfunction "OUT_K1") (pintype "output"))
      (node (ref "F24") (pin "B1") (pinfunction "IN2_B1") (pintype "input"))
    )
    (net (code "1672") (name "TT_SKIP_") (class "Default")
      (node (ref "E12") (pin "S1") (pinfunction "OUT_S1") (pintype "output"))
      (node (ref "J15") (pin "C1") (pinfunction "IN3_C1") (pintype "input"))
    )
    (net (code "1673") (name "TX_DATA") (class "Default")
      (node (ref "EF02") (pin "AV2") (pinfunction "AV2_AV2") (pintype "output"))
      (node (ref "J12") (pin "H2") (pinfunction "P$2_H2") (pintype "bidirectional"))
    )
    (net (code "1674") (name "UB") (class "Default")
      (node (ref "B05") (pin "E1") (pinfunction "1_E1") (pintype "output"))
      (node (ref "B06") (pin "P2") (pinfunction "IN1_P2") (pintype "input"))
    )
    (net (code "1675") (name "UF") (class "Default")
      (node (ref "A05") (pin "M1") (pinfunction "IN2_M1") (pintype "input"))
      (node (ref "B05") (pin "H2") (pinfunction "1_H2") (pintype "output"))
      (node (ref "B05") (pin "P1") (pinfunction "D_P1") (pintype "input"))
    )
    (net (code "1676") (name "UF_") (class "Default")
      (node (ref "A06") (pin "J1") (pinfunction "IN2_J1") (pintype "input"))
      (node (ref "B05") (pin "J2") (pinfunction "0_J2") (pintype "output"))
      (node (ref "E13") (pin "D1") (pinfunction "IN1D_D1") (pintype "input"))
      (node (ref "F11") (pin "D1") (pinfunction "IN4_D1") (pintype "input"))
    )
    (net (code "1677") (name "UINT") (class "Default")
      (node (ref "A05") (pin "M2") (pinfunction "IN2_M2") (pintype "input"))
      (node (ref "B04") (pin "J2") (pinfunction "IN1_J2") (pintype "input"))
      (node (ref "B05") (pin "P2") (pinfunction "1_P2") (pintype "output"))
    )
    (net (code "1678") (name "UINT_") (class "Default")
      (node (ref "A05") (pin "S2") (pinfunction "OUT_S2") (pintype "output"))
      (node (ref "F19") (pin "N1") (pinfunction "IN2_N1") (pintype "input"))
    )
    (net (code "1679") (name "USF_") (class "Default")
      (node (ref "B04") (pin "T2") (pinfunction "IN1_T2") (pintype "input"))
      (node (ref "B05") (pin "V1") (pinfunction "0_V1") (pintype "output"))
    )
    (net (code "1680") (name "VCC") (class "Default")
      (node (ref "A40") (pin "A2") (pinfunction "P$2_A2") (pintype "bidirectional"))
      (node (ref "B40") (pin "A2") (pinfunction "P$2_A2") (pintype "bidirectional"))
      (node (ref "C40") (pin "A2") (pinfunction "P$2_A2") (pintype "bidirectional"))
      (node (ref "D03") (pin "A2") (pinfunction "P$2_A2") (pintype "bidirectional"))
      (node (ref "E40") (pin "A2") (pinfunction "P$2_A2") (pintype "bidirectional"))
      (node (ref "F40") (pin "A2") (pinfunction "P$2_A2") (pintype "bidirectional"))
    )
    (net (code "1681") (name "WC_OVERFLOW_") (class "Default")
      (node (ref "E33") (pin "H2") (pinfunction "1_H2") (pintype "output"))
      (node (ref "H19") (pin "U2") (pinfunction "IN2_U2") (pintype "input"))
    )
    (net (code "1682") (name "WC_SET") (class "Default")
      (node (ref "E23") (pin "M2") (pinfunction "D_M2") (pintype "input"))
      (node (ref "F22") (pin "N2") (pinfunction "OUT_N2") (pintype "output"))
    )
    (net (code "1683") (name "WC_SET_") (class "Default")
      (node (ref "A19") (pin "A1") (pinfunction "IN1_A1") (pintype "input"))
      (node (ref "F22") (pin "L2") (pinfunction "IN1_L2") (pintype "input"))
      (node (ref "F22") (pin "R1") (pinfunction "IN2_R1") (pintype "input"))
      (node (ref "F22") (pin "V2") (pinfunction "OUT_V2") (pintype "output"))
    )
    (net (code "1684") (name "WORD_COUNT") (class "Default")
      (node (ref "E23") (pin "P1") (pinfunction "D_P1") (pintype "input"))
      (node (ref "E23") (pin "P2") (pinfunction "1_P2") (pintype "output"))
      (node (ref "E27") (pin "D2") (pinfunction "IN1A_D2") (pintype "input"))
      (node (ref "E30") (pin "J1") (pinfunction "IN3B_J1") (pintype "input"))
    )
    (net (code "1685") (name "WORD_COUNT_") (class "Default")
      (node (ref "A19") (pin "B1") (pinfunction "IN2_B1") (pintype "input"))
      (node (ref "D40") (pin "A1") (pinfunction "P$2_A1") (pintype "bidirectional"))
      (node (ref "E12") (pin "P2") (pinfunction "IN1_P2") (pintype "input"))
      (node (ref "E23") (pin "R2") (pinfunction "0_R2") (pintype "output"))
      (node (ref "E25") (pin "H1") (pinfunction "IN3_H1") (pintype "input"))
    )
    (net (code "1686") (name "WRITE") (class "Default")
      (node (ref "B22") (pin "S1") (pinfunction "1_S1") (pintype "output"))
      (node (ref "C39") (pin "A1") (pinfunction "A1_A1") (pintype "input"))
      (node (ref "C39") (pin "E2") (pinfunction "E2_E2") (pintype "input"))
      (node (ref "C39") (pin "N2") (pinfunction "N2_N2") (pintype "input"))
    )
    (net (code "1687") (name "X_AXIS") (class "Default")
      (node (ref "D03") (pin "D2") (pinfunction "P$2_D2") (pintype "bidirectional"))
      (node (ref "HJ24") (pin "BS2") (pinfunction "BS2_BS2") (pintype "output"))
    )
    (net (code "1688") (name "X_RW_RETURN") (class "Default")
      (node (ref "B39") (pin "D2") (pinfunction "P$2_D2") (pintype "passive"))
      (node (ref "D25") (pin "T2") (pinfunction "T2_T2") (pintype "input"))
      (node (ref "D26") (pin "T2") (pinfunction "T2_T2") (pintype "input"))
      (node (ref "D32") (pin "T2") (pinfunction "T2_T2") (pintype "input"))
      (node (ref "D33") (pin "T2") (pinfunction "T2_T2") (pintype "input"))
      (node (ref "D39") (pin "F2") (pinfunction "F2_F2") (pintype "passive"))
      (node (ref "D39") (pin "K1") (pinfunction "K1_K1") (pintype "passive"))
    )
    (net (code "1689") (name "X_RW_SOURCE") (class "Default")
      (node (ref "A39") (pin "D2") (pinfunction "P$2_D2") (pintype "passive"))
      (node (ref "C30") (pin "T2") (pinfunction "T2_T2") (pintype "input"))
      (node (ref "C31") (pin "T2") (pinfunction "T2_T2") (pintype "input"))
      (node (ref "C37") (pin "T2") (pinfunction "T2_T2") (pintype "input"))
      (node (ref "C38") (pin "T2") (pinfunction "T2_T2") (pintype "input"))
      (node (ref "C39") (pin "F2") (pinfunction "F2_F2") (pintype "passive"))
      (node (ref "C39") (pin "K1") (pinfunction "K1_K1") (pintype "passive"))
    )
    (net (code "1690") (name "X_STROBE") (class "Default")
      (node (ref "HJ23") (pin "AS1") (pinfunction "AS1_AS1") (pintype "output"))
      (node (ref "HJ24") (pin "AD2") (pinfunction "AD2_AD2") (pintype "bidirectional"))
    )
    (net (code "1691") (name "Y_AXIS") (class "Default")
      (node (ref "D03") (pin "E2") (pinfunction "P$2_E2") (pintype "bidirectional"))
      (node (ref "HJ25") (pin "BS2") (pinfunction "BS2_BS2") (pintype "output"))
    )
    (net (code "1692") (name "Y_RW_RETURN") (class "Default")
      (node (ref "A38") (pin "D2") (pinfunction "P$2_D2") (pintype "passive"))
      (node (ref "D30") (pin "T2") (pinfunction "T2_T2") (pintype "input"))
      (node (ref "D31") (pin "T2") (pinfunction "T2_T2") (pintype "input"))
      (node (ref "D37") (pin "T2") (pinfunction "T2_T2") (pintype "input"))
      (node (ref "D38") (pin "T2") (pinfunction "T2_T2") (pintype "input"))
      (node (ref "D39") (pin "P2") (pinfunction "P2_P2") (pintype "passive"))
      (node (ref "D39") (pin "S1") (pinfunction "S1_S1") (pintype "passive"))
    )
    (net (code "1693") (name "Y_RW_SOURCE") (class "Default")
      (node (ref "B38") (pin "D2") (pinfunction "P$2_D2") (pintype "passive"))
      (node (ref "C25") (pin "T2") (pinfunction "T2_T2") (pintype "input"))
      (node (ref "C26") (pin "T2") (pinfunction "T2_T2") (pintype "input"))
      (node (ref "C32") (pin "T2") (pinfunction "T2_T2") (pintype "input"))
      (node (ref "C33") (pin "T2") (pinfunction "T2_T2") (pintype "input"))
      (node (ref "C39") (pin "P2") (pinfunction "P2_P2") (pintype "passive"))
      (node (ref "C39") (pin "S1") (pinfunction "S1_S1") (pintype "passive"))
    )
    (net (code "1694") (name "Y_STROBE") (class "Default")
      (node (ref "HJ23") (pin "AP2") (pinfunction "AP2_AP2") (pintype "output"))
      (node (ref "HJ25") (pin "AD2") (pinfunction "AD2_AD2") (pintype "bidirectional"))
    )
    (net (code "1695") (name "ZONE01_INDEX") (class "Default")
      (node (ref "HJ32") (pin "AK2") (pinfunction "AK2_AK2") (pintype "input"))
      (node (ref "HJ34") (pin "BD2") (pinfunction "P$2_BD2") (pintype "bidirectional"))
    )
    (net (code "1696") (name "ZONE02_INDEX") (class "Default")
      (node (ref "HJ32") (pin "AR2") (pinfunction "AR2_AR2") (pintype "input"))
      (node (ref "HJ34") (pin "BE2") (pinfunction "P$2_BE2") (pintype "bidirectional"))
    )
    (net (code "1697") (name "ZONE03_INDEX") (class "Default")
      (node (ref "HJ32") (pin "AP2") (pinfunction "AP2_AP2") (pintype "input"))
      (node (ref "HJ34") (pin "BF2") (pinfunction "P$2_BF2") (pintype "bidirectional"))
    )
    (net (code "1698") (name "ZONE04_INDEX") (class "Default")
      (node (ref "HJ32") (pin "BE2") (pinfunction "BE2_BE2") (pintype "input"))
      (node (ref "HJ34") (pin "BJ2") (pinfunction "P$2_BJ2") (pintype "bidirectional"))
    )
    (net (code "1699") (name "ZONE05_INDEX") (class "Default")
      (node (ref "HJ32") (pin "AS2") (pinfunction "AS2_AS2") (pintype "input"))
      (node (ref "HJ34") (pin "BK2") (pinfunction "P$2_BK2") (pintype "bidirectional"))
    )
    (net (code "1700") (name "ZONE06_INDEX") (class "Default")
      (node (ref "HJ32") (pin "BS1") (pinfunction "BS1_BS1") (pintype "input"))
      (node (ref "HJ34") (pin "BL2") (pinfunction "P$2_BL2") (pintype "bidirectional"))
    )
    (net (code "1701") (name "ZONE07_INDEX") (class "Default")
      (node (ref "HJ32") (pin "BR1") (pinfunction "BR1_BR1") (pintype "input"))
      (node (ref "HJ34") (pin "BM2") (pinfunction "P$2_BM2") (pintype "bidirectional"))
    )
    (net (code "1702") (name "ZONE08_INDEX") (class "Default")
      (node (ref "HJ32") (pin "BK2") (pinfunction "BK2_BK2") (pintype "input"))
      (node (ref "HJ34") (pin "BN2") (pinfunction "P$2_BN2") (pintype "bidirectional"))
    )
    (net (code "1703") (name "ZONE09_INDEX") (class "Default")
      (node (ref "HJ32") (pin "BL2") (pinfunction "BL2_BL2") (pintype "input"))
      (node (ref "HJ34") (pin "BS2") (pinfunction "P$2_BS2") (pintype "bidirectional"))
    )
    (net (code "1704") (name "ZONE10_INDEX") (class "Default")
      (node (ref "HJ32") (pin "AL2") (pinfunction "AL2_AL2") (pintype "input"))
      (node (ref "HJ34") (pin "BT2") (pinfunction "P$2_BT2") (pintype "bidirectional"))
    )
    (net (code "1705") (name "ZONE11_INDEX") (class "Default")
      (node (ref "HJ32") (pin "AE1") (pinfunction "AE1_AE1") (pintype "input"))
      (node (ref "HJ34") (pin "BU2") (pinfunction "P$2_BU2") (pintype "bidirectional"))
    )
    (net (code "1706") (name "ZONE12_INDEX") (class "Default")
      (node (ref "HJ32") (pin "AE2") (pinfunction "AE2_AE2") (pintype "input"))
      (node (ref "HJ34") (pin "BV2") (pinfunction "P$2_BV2") (pintype "bidirectional"))
    )
    (net (code "1707") (name "Z_AXIS") (class "Default")
      (node (ref "D03") (pin "F2") (pinfunction "P$2_F2") (pintype "bidirectional"))
      (node (ref "HJ23") (pin "AE2") (pinfunction "AE2_AE2") (pintype "output"))
    )
    (net (code "1708") (name "unconnected-(A04-PadT2)") (class "Default")
      (node (ref "A04") (pin "T2") (pinfunction "T2_T2") (pintype "output"))
    )
    (net (code "1709") (name "unconnected-(A08C-ODD-PadK1)") (class "Default")
      (node (ref "A08") (pin "K1") (pinfunction "ODD_K1") (pintype "output"))
    )
    (net (code "1710") (name "unconnected-(A10C-EVEN-PadL1)") (class "Default")
      (node (ref "A10") (pin "L1") (pinfunction "EVEN_L1") (pintype "output"))
    )
    (net (code "1711") (name "unconnected-(A21-PadJ2)") (class "Default")
      (node (ref "A21") (pin "J2") (pinfunction "J2_J2") (pintype "output"))
    )
    (net (code "1712") (name "unconnected-(A21-PadK2)") (class "Default")
      (node (ref "A21") (pin "K2") (pinfunction "K2_K2") (pintype "output"))
    )
    (net (code "1713") (name "unconnected-(A21-PadM2)") (class "Default")
      (node (ref "A21") (pin "M2") (pinfunction "M2_M2") (pintype "output"))
    )
    (net (code "1714") (name "unconnected-(A21-PadP2)") (class "Default")
      (node (ref "A21") (pin "P2") (pinfunction "P2_P2") (pintype "output"))
    )
    (net (code "1715") (name "unconnected-(A21-PadR2)") (class "Default")
      (node (ref "A21") (pin "R2") (pinfunction "R2_R2") (pintype "output"))
    )
    (net (code "1716") (name "unconnected-(A21-PadS2)") (class "Default")
      (node (ref "A21") (pin "S2") (pinfunction "S2_S2") (pintype "output"))
    )
    (net (code "1717") (name "unconnected-(A21-PadT2)") (class "Default")
      (node (ref "A21") (pin "T2") (pinfunction "T2_T2") (pintype "output"))
    )
    (net (code "1718") (name "unconnected-(A21-PadU2)") (class "Default")
      (node (ref "A21") (pin "U2") (pinfunction "U2_U2") (pintype "output"))
    )
    (net (code "1719") (name "unconnected-(A21-PadV2)") (class "Default")
      (node (ref "A21") (pin "V2") (pinfunction "V2_V2") (pintype "output"))
    )
    (net (code "1720") (name "unconnected-(A22-PadJ2)") (class "Default")
      (node (ref "A22") (pin "J2") (pinfunction "J2_J2") (pintype "output"))
    )
    (net (code "1721") (name "unconnected-(A22-PadK2)") (class "Default")
      (node (ref "A22") (pin "K2") (pinfunction "K2_K2") (pintype "output"))
    )
    (net (code "1722") (name "unconnected-(A22-PadL2)") (class "Default")
      (node (ref "A22") (pin "L2") (pinfunction "L2_L2") (pintype "output"))
    )
    (net (code "1723") (name "unconnected-(A22-PadM2)") (class "Default")
      (node (ref "A22") (pin "M2") (pinfunction "M2_M2") (pintype "output"))
    )
    (net (code "1724") (name "unconnected-(A22-PadN2)") (class "Default")
      (node (ref "A22") (pin "N2") (pinfunction "N2_N2") (pintype "output"))
    )
    (net (code "1725") (name "unconnected-(A22-PadP2)") (class "Default")
      (node (ref "A22") (pin "P2") (pinfunction "P2_P2") (pintype "output"))
    )
    (net (code "1726") (name "unconnected-(A22-PadS2)") (class "Default")
      (node (ref "A22") (pin "S2") (pinfunction "S2_S2") (pintype "output"))
    )
    (net (code "1727") (name "unconnected-(A22-PadT2)") (class "Default")
      (node (ref "A22") (pin "T2") (pinfunction "T2_T2") (pintype "output"))
    )
    (net (code "1728") (name "unconnected-(A22-PadU2)") (class "Default")
      (node (ref "A22") (pin "U2") (pinfunction "U2_U2") (pintype "output"))
    )
    (net (code "1729") (name "unconnected-(A22-PadV2)") (class "Default")
      (node (ref "A22") (pin "V2") (pinfunction "V2_V2") (pintype "output"))
    )
    (net (code "1730") (name "unconnected-(A23-PadJ2)") (class "Default")
      (node (ref "A23") (pin "J2") (pinfunction "J2_J2") (pintype "output"))
    )
    (net (code "1731") (name "unconnected-(A23-PadK2)") (class "Default")
      (node (ref "A23") (pin "K2") (pinfunction "K2_K2") (pintype "output"))
    )
    (net (code "1732") (name "unconnected-(A23-PadL2)") (class "Default")
      (node (ref "A23") (pin "L2") (pinfunction "L2_L2") (pintype "output"))
    )
    (net (code "1733") (name "unconnected-(A23-PadP2)") (class "Default")
      (node (ref "A23") (pin "P2") (pinfunction "P2_P2") (pintype "output"))
    )
    (net (code "1734") (name "unconnected-(A23-PadR2)") (class "Default")
      (node (ref "A23") (pin "R2") (pinfunction "R2_R2") (pintype "output"))
    )
    (net (code "1735") (name "unconnected-(A23-PadS2)") (class "Default")
      (node (ref "A23") (pin "S2") (pinfunction "S2_S2") (pintype "output"))
    )
    (net (code "1736") (name "unconnected-(A23-PadT2)") (class "Default")
      (node (ref "A23") (pin "T2") (pinfunction "T2_T2") (pintype "output"))
    )
    (net (code "1737") (name "unconnected-(A23-PadU2)") (class "Default")
      (node (ref "A23") (pin "U2") (pinfunction "U2_U2") (pintype "output"))
    )
    (net (code "1738") (name "unconnected-(A23-PadV2)") (class "Default")
      (node (ref "A23") (pin "V2") (pinfunction "V2_V2") (pintype "output"))
    )
    (net (code "1739") (name "unconnected-(A24-PadJ2)") (class "Default")
      (node (ref "A24") (pin "J2") (pinfunction "J2_J2") (pintype "output"))
    )
    (net (code "1740") (name "unconnected-(A24-PadK2)") (class "Default")
      (node (ref "A24") (pin "K2") (pinfunction "K2_K2") (pintype "output"))
    )
    (net (code "1741") (name "unconnected-(A24-PadL2)") (class "Default")
      (node (ref "A24") (pin "L2") (pinfunction "L2_L2") (pintype "output"))
    )
    (net (code "1742") (name "unconnected-(A24-PadM2)") (class "Default")
      (node (ref "A24") (pin "M2") (pinfunction "M2_M2") (pintype "output"))
    )
    (net (code "1743") (name "unconnected-(A24-PadN2)") (class "Default")
      (node (ref "A24") (pin "N2") (pinfunction "N2_N2") (pintype "output"))
    )
    (net (code "1744") (name "unconnected-(A24-PadP2)") (class "Default")
      (node (ref "A24") (pin "P2") (pinfunction "P2_P2") (pintype "output"))
    )
    (net (code "1745") (name "unconnected-(A24-PadR2)") (class "Default")
      (node (ref "A24") (pin "R2") (pinfunction "R2_R2") (pintype "output"))
    )
    (net (code "1746") (name "unconnected-(A24-PadS2)") (class "Default")
      (node (ref "A24") (pin "S2") (pinfunction "S2_S2") (pintype "output"))
    )
    (net (code "1747") (name "unconnected-(A24-PadU2)") (class "Default")
      (node (ref "A24") (pin "U2") (pinfunction "U2_U2") (pintype "output"))
    )
    (net (code "1748") (name "unconnected-(A24-PadV2)") (class "Default")
      (node (ref "A24") (pin "V2") (pinfunction "V2_V2") (pintype "output"))
    )
    (net (code "1749") (name "unconnected-(A30-PadC1)") (class "Default")
      (node (ref "A30") (pin "C1") (pinfunction "C1_C1") (pintype "output"))
    )
    (net (code "1750") (name "unconnected-(A30-PadE1)") (class "Default")
      (node (ref "A30") (pin "E1") (pinfunction "E1_E1") (pintype "output"))
    )
    (net (code "1751") (name "unconnected-(A30-PadF2)") (class "Default")
      (node (ref "A30") (pin "F2") (pinfunction "F2_F2") (pintype "input"))
    )
    (net (code "1752") (name "unconnected-(A30-PadH2)") (class "Default")
      (node (ref "A30") (pin "H2") (pinfunction "H2_H2") (pintype "input"))
    )
    (net (code "1753") (name "unconnected-(A30-PadJ2)") (class "Default")
      (node (ref "A30") (pin "J2") (pinfunction "J2_J2") (pintype "output"))
    )
    (net (code "1754") (name "unconnected-(A30-PadK2)") (class "Default")
      (node (ref "A30") (pin "K2") (pinfunction "K2_K2") (pintype "output"))
    )
    (net (code "1755") (name "unconnected-(A30-PadN1)") (class "Default")
      (node (ref "A30") (pin "N1") (pinfunction "N1_N1") (pintype "input"))
    )
    (net (code "1756") (name "unconnected-(A30-PadP1)") (class "Default")
      (node (ref "A30") (pin "P1") (pinfunction "P1_P1") (pintype "input"))
    )
    (net (code "1757") (name "unconnected-(A30-PadR2)") (class "Default")
      (node (ref "A30") (pin "R2") (pinfunction "R2_R2") (pintype "output"))
    )
    (net (code "1758") (name "unconnected-(A30-PadS1)") (class "Default")
      (node (ref "A30") (pin "S1") (pinfunction "S1_S1") (pintype "output"))
    )
    (net (code "1759") (name "unconnected-(A30-PadU2)") (class "Default")
      (node (ref "A30") (pin "U2") (pinfunction "U2_U2") (pintype "open_collector"))
    )
    (net (code "1760") (name "unconnected-(A31-PadC1)") (class "Default")
      (node (ref "A31") (pin "C1") (pinfunction "C1_C1") (pintype "output"))
    )
    (net (code "1761") (name "unconnected-(A31-PadE1)") (class "Default")
      (node (ref "A31") (pin "E1") (pinfunction "E1_E1") (pintype "output"))
    )
    (net (code "1762") (name "unconnected-(A31-PadJ2)") (class "Default")
      (node (ref "A31") (pin "J2") (pinfunction "J2_J2") (pintype "output"))
    )
    (net (code "1763") (name "unconnected-(A31-PadK2)") (class "Default")
      (node (ref "A31") (pin "K2") (pinfunction "K2_K2") (pintype "output"))
    )
    (net (code "1764") (name "unconnected-(A31-PadR2)") (class "Default")
      (node (ref "A31") (pin "R2") (pinfunction "R2_R2") (pintype "output"))
    )
    (net (code "1765") (name "unconnected-(A31-PadS1)") (class "Default")
      (node (ref "A31") (pin "S1") (pinfunction "S1_S1") (pintype "output"))
    )
    (net (code "1766") (name "unconnected-(A32-PadC1)") (class "Default")
      (node (ref "A32") (pin "C1") (pinfunction "C1_C1") (pintype "output"))
    )
    (net (code "1767") (name "unconnected-(A32-PadE1)") (class "Default")
      (node (ref "A32") (pin "E1") (pinfunction "E1_E1") (pintype "output"))
    )
    (net (code "1768") (name "unconnected-(A32-PadJ2)") (class "Default")
      (node (ref "A32") (pin "J2") (pinfunction "J2_J2") (pintype "output"))
    )
    (net (code "1769") (name "unconnected-(A32-PadK2)") (class "Default")
      (node (ref "A32") (pin "K2") (pinfunction "K2_K2") (pintype "output"))
    )
    (net (code "1770") (name "unconnected-(A32-PadR2)") (class "Default")
      (node (ref "A32") (pin "R2") (pinfunction "R2_R2") (pintype "output"))
    )
    (net (code "1771") (name "unconnected-(A32-PadS1)") (class "Default")
      (node (ref "A32") (pin "S1") (pinfunction "S1_S1") (pintype "output"))
    )
    (net (code "1772") (name "unconnected-(A33-PadC1)") (class "Default")
      (node (ref "A33") (pin "C1") (pinfunction "C1_C1") (pintype "output"))
    )
    (net (code "1773") (name "unconnected-(A33-PadE1)") (class "Default")
      (node (ref "A33") (pin "E1") (pinfunction "E1_E1") (pintype "output"))
    )
    (net (code "1774") (name "unconnected-(A33-PadJ2)") (class "Default")
      (node (ref "A33") (pin "J2") (pinfunction "J2_J2") (pintype "output"))
    )
    (net (code "1775") (name "unconnected-(A33-PadK2)") (class "Default")
      (node (ref "A33") (pin "K2") (pinfunction "K2_K2") (pintype "output"))
    )
    (net (code "1776") (name "unconnected-(A33-PadR2)") (class "Default")
      (node (ref "A33") (pin "R2") (pinfunction "R2_R2") (pintype "output"))
    )
    (net (code "1777") (name "unconnected-(A33-PadS1)") (class "Default")
      (node (ref "A33") (pin "S1") (pinfunction "S1_S1") (pintype "output"))
    )
    (net (code "1778") (name "unconnected-(A37-PadD1)") (class "Default")
      (node (ref "A37") (pin "D1") (pinfunction "D1_D1") (pintype "input"))
    )
    (net (code "1779") (name "unconnected-(A37-PadE1)") (class "Default")
      (node (ref "A37") (pin "E1") (pinfunction "E1_E1") (pintype "passive"))
    )
    (net (code "1780") (name "unconnected-(A37-PadK1)") (class "Default")
      (node (ref "A37") (pin "K1") (pinfunction "K1_K1") (pintype "passive"))
    )
    (net (code "1781") (name "unconnected-(A37-PadL1)") (class "Default")
      (node (ref "A37") (pin "L1") (pinfunction "L1_L1") (pintype "input"))
    )
    (net (code "1782") (name "unconnected-(A37-PadM1)") (class "Default")
      (node (ref "A37") (pin "M1") (pinfunction "M1_M1") (pintype "passive"))
    )
    (net (code "1783") (name "unconnected-(A37-PadS1)") (class "Default")
      (node (ref "A37") (pin "S1") (pinfunction "S1_S1") (pintype "passive"))
    )
    (net (code "1784") (name "unconnected-(A37-PadU2)") (class "Default")
      (node (ref "A37") (pin "U2") (pinfunction "U2_U2") (pintype "passive"))
    )
    (net (code "1785") (name "unconnected-(B05A-0-PadF1)") (class "Default")
      (node (ref "B05") (pin "F1") (pinfunction "0_F1") (pintype "output"))
    )
    (net (code "1786") (name "unconnected-(B05G-0-PadU1)") (class "Default")
      (node (ref "B05") (pin "U1") (pinfunction "0_U1") (pintype "output"))
    )
    (net (code "1787") (name "unconnected-(B05H-1-PadV2)") (class "Default")
      (node (ref "B05") (pin "V2") (pinfunction "1_V2") (pintype "output"))
    )
    (net (code "1788") (name "unconnected-(B11A-1-PadE1)") (class "Default")
      (node (ref "B11") (pin "E1") (pinfunction "1_E1") (pintype "output"))
    )
    (net (code "1789") (name "unconnected-(B11D-1-PadH2)") (class "Default")
      (node (ref "B11") (pin "H2") (pinfunction "1_H2") (pintype "output"))
    )
    (net (code "1790") (name "unconnected-(B11E-1-PadL1)") (class "Default")
      (node (ref "B11") (pin "L1") (pinfunction "1_L1") (pintype "output"))
    )
    (net (code "1791") (name "unconnected-(B17F-0-PadR2)") (class "Default")
      (node (ref "B17") (pin "R2") (pinfunction "0_R2") (pintype "output"))
    )
    (net (code "1792") (name "unconnected-(B17G-0-PadU1)") (class "Default")
      (node (ref "B17") (pin "U1") (pinfunction "0_U1") (pintype "output"))
    )
    (net (code "1793") (name "unconnected-(B17H-0-PadV1)") (class "Default")
      (node (ref "B17") (pin "V1") (pinfunction "0_V1") (pintype "output"))
    )
    (net (code "1794") (name "unconnected-(B18F-0-PadR2)") (class "Default")
      (node (ref "B18") (pin "R2") (pinfunction "0_R2") (pintype "output"))
    )
    (net (code "1795") (name "unconnected-(B18G-0-PadU1)") (class "Default")
      (node (ref "B18") (pin "U1") (pinfunction "0_U1") (pintype "output"))
    )
    (net (code "1796") (name "unconnected-(B18H-0-PadV1)") (class "Default")
      (node (ref "B18") (pin "V1") (pinfunction "0_V1") (pintype "output"))
    )
    (net (code "1797") (name "unconnected-(B19A-0-PadF1)") (class "Default")
      (node (ref "B19") (pin "F1") (pinfunction "0_F1") (pintype "output"))
    )
    (net (code "1798") (name "unconnected-(B19D-0-PadJ2)") (class "Default")
      (node (ref "B19") (pin "J2") (pinfunction "0_J2") (pintype "output"))
    )
    (net (code "1799") (name "unconnected-(B19E-0-PadM1)") (class "Default")
      (node (ref "B19") (pin "M1") (pinfunction "0_M1") (pintype "output"))
    )
    (net (code "1800") (name "unconnected-(B19F-0-PadR2)") (class "Default")
      (node (ref "B19") (pin "R2") (pinfunction "0_R2") (pintype "output"))
    )
    (net (code "1801") (name "unconnected-(B19G-0-PadU1)") (class "Default")
      (node (ref "B19") (pin "U1") (pinfunction "0_U1") (pintype "output"))
    )
    (net (code "1802") (name "unconnected-(B19H-0-PadV1)") (class "Default")
      (node (ref "B19") (pin "V1") (pinfunction "0_V1") (pintype "output"))
    )
    (net (code "1803") (name "unconnected-(B22A-1-PadE1)") (class "Default")
      (node (ref "B22") (pin "E1") (pinfunction "1_E1") (pintype "output"))
    )
    (net (code "1804") (name "unconnected-(B22E-0-PadM1)") (class "Default")
      (node (ref "B22") (pin "M1") (pinfunction "0_M1") (pintype "output"))
    )
    (net (code "1805") (name "unconnected-(B22F-1-PadP2)") (class "Default")
      (node (ref "B22") (pin "P2") (pinfunction "1_P2") (pintype "output"))
    )
    (net (code "1806") (name "unconnected-(B22G-0-PadU1)") (class "Default")
      (node (ref "B22") (pin "U1") (pinfunction "0_U1") (pintype "output"))
    )
    (net (code "1807") (name "unconnected-(B31-PadC1)") (class "Default")
      (node (ref "B31") (pin "C1") (pinfunction "C1_C1") (pintype "output"))
    )
    (net (code "1808") (name "unconnected-(B31-PadE1)") (class "Default")
      (node (ref "B31") (pin "E1") (pinfunction "E1_E1") (pintype "output"))
    )
    (net (code "1809") (name "unconnected-(B31-PadJ2)") (class "Default")
      (node (ref "B31") (pin "J2") (pinfunction "J2_J2") (pintype "output"))
    )
    (net (code "1810") (name "unconnected-(B31-PadK2)") (class "Default")
      (node (ref "B31") (pin "K2") (pinfunction "K2_K2") (pintype "output"))
    )
    (net (code "1811") (name "unconnected-(B31-PadR2)") (class "Default")
      (node (ref "B31") (pin "R2") (pinfunction "R2_R2") (pintype "output"))
    )
    (net (code "1812") (name "unconnected-(B31-PadS1)") (class "Default")
      (node (ref "B31") (pin "S1") (pinfunction "S1_S1") (pintype "output"))
    )
    (net (code "1813") (name "unconnected-(B32-PadC1)") (class "Default")
      (node (ref "B32") (pin "C1") (pinfunction "C1_C1") (pintype "output"))
    )
    (net (code "1814") (name "unconnected-(B32-PadE1)") (class "Default")
      (node (ref "B32") (pin "E1") (pinfunction "E1_E1") (pintype "output"))
    )
    (net (code "1815") (name "unconnected-(B32-PadJ2)") (class "Default")
      (node (ref "B32") (pin "J2") (pinfunction "J2_J2") (pintype "output"))
    )
    (net (code "1816") (name "unconnected-(B32-PadK2)") (class "Default")
      (node (ref "B32") (pin "K2") (pinfunction "K2_K2") (pintype "output"))
    )
    (net (code "1817") (name "unconnected-(B32-PadR2)") (class "Default")
      (node (ref "B32") (pin "R2") (pinfunction "R2_R2") (pintype "output"))
    )
    (net (code "1818") (name "unconnected-(B32-PadS1)") (class "Default")
      (node (ref "B32") (pin "S1") (pinfunction "S1_S1") (pintype "output"))
    )
    (net (code "1819") (name "unconnected-(B33-PadC1)") (class "Default")
      (node (ref "B33") (pin "C1") (pinfunction "C1_C1") (pintype "output"))
    )
    (net (code "1820") (name "unconnected-(B33-PadE1)") (class "Default")
      (node (ref "B33") (pin "E1") (pinfunction "E1_E1") (pintype "output"))
    )
    (net (code "1821") (name "unconnected-(B33-PadJ2)") (class "Default")
      (node (ref "B33") (pin "J2") (pinfunction "J2_J2") (pintype "output"))
    )
    (net (code "1822") (name "unconnected-(B33-PadK2)") (class "Default")
      (node (ref "B33") (pin "K2") (pinfunction "K2_K2") (pintype "output"))
    )
    (net (code "1823") (name "unconnected-(B33-PadR2)") (class "Default")
      (node (ref "B33") (pin "R2") (pinfunction "R2_R2") (pintype "output"))
    )
    (net (code "1824") (name "unconnected-(B33-PadS1)") (class "Default")
      (node (ref "B33") (pin "S1") (pinfunction "S1_S1") (pintype "output"))
    )
    (net (code "1825") (name "unconnected-(C13-PadJ2)") (class "Default")
      (node (ref "C13") (pin "J2") (pinfunction "J2_J2") (pintype "output"))
    )
    (net (code "1826") (name "unconnected-(C13-PadK2)") (class "Default")
      (node (ref "C13") (pin "K2") (pinfunction "K2_K2") (pintype "output"))
    )
    (net (code "1827") (name "unconnected-(C13-PadL2)") (class "Default")
      (node (ref "C13") (pin "L2") (pinfunction "L2_L2") (pintype "output"))
    )
    (net (code "1828") (name "unconnected-(C13-PadM2)") (class "Default")
      (node (ref "C13") (pin "M2") (pinfunction "M2_M2") (pintype "output"))
    )
    (net (code "1829") (name "unconnected-(C13-PadN2)") (class "Default")
      (node (ref "C13") (pin "N2") (pinfunction "N2_N2") (pintype "output"))
    )
    (net (code "1830") (name "unconnected-(C13-PadR2)") (class "Default")
      (node (ref "C13") (pin "R2") (pinfunction "R2_R2") (pintype "output"))
    )
    (net (code "1831") (name "unconnected-(C13-PadT2)") (class "Default")
      (node (ref "C13") (pin "T2") (pinfunction "T2_T2") (pintype "output"))
    )
    (net (code "1832") (name "unconnected-(C13-PadU2)") (class "Default")
      (node (ref "C13") (pin "U2") (pinfunction "U2_U2") (pintype "output"))
    )
    (net (code "1833") (name "unconnected-(C13-PadV2)") (class "Default")
      (node (ref "C13") (pin "V2") (pinfunction "V2_V2") (pintype "output"))
    )
    (net (code "1834") (name "unconnected-(C22H-0-PadV1)") (class "Default")
      (node (ref "C22") (pin "V1") (pinfunction "0_V1") (pintype "output"))
    )
    (net (code "1835") (name "unconnected-(D06-PadJ2)") (class "Default")
      (node (ref "D06") (pin "J2") (pinfunction "J2_J2") (pintype "output"))
    )
    (net (code "1836") (name "unconnected-(D06-PadK2)") (class "Default")
      (node (ref "D06") (pin "K2") (pinfunction "K2_K2") (pintype "output"))
    )
    (net (code "1837") (name "unconnected-(D06-PadL2)") (class "Default")
      (node (ref "D06") (pin "L2") (pinfunction "L2_L2") (pintype "output"))
    )
    (net (code "1838") (name "unconnected-(D06-PadM2)") (class "Default")
      (node (ref "D06") (pin "M2") (pinfunction "M2_M2") (pintype "output"))
    )
    (net (code "1839") (name "unconnected-(D06-PadN2)") (class "Default")
      (node (ref "D06") (pin "N2") (pinfunction "N2_N2") (pintype "output"))
    )
    (net (code "1840") (name "unconnected-(D06-PadP2)") (class "Default")
      (node (ref "D06") (pin "P2") (pinfunction "P2_P2") (pintype "output"))
    )
    (net (code "1841") (name "unconnected-(D06-PadS2)") (class "Default")
      (node (ref "D06") (pin "S2") (pinfunction "S2_S2") (pintype "output"))
    )
    (net (code "1842") (name "unconnected-(D06-PadT2)") (class "Default")
      (node (ref "D06") (pin "T2") (pinfunction "T2_T2") (pintype "output"))
    )
    (net (code "1843") (name "unconnected-(D06-PadU2)") (class "Default")
      (node (ref "D06") (pin "U2") (pinfunction "U2_U2") (pintype "output"))
    )
    (net (code "1844") (name "unconnected-(D06-PadV2)") (class "Default")
      (node (ref "D06") (pin "V2") (pinfunction "V2_V2") (pintype "output"))
    )
    (net (code "1845") (name "unconnected-(D08-PadJ2)") (class "Default")
      (node (ref "D08") (pin "J2") (pinfunction "J2_J2") (pintype "output"))
    )
    (net (code "1846") (name "unconnected-(D08-PadK2)") (class "Default")
      (node (ref "D08") (pin "K2") (pinfunction "K2_K2") (pintype "output"))
    )
    (net (code "1847") (name "unconnected-(D08-PadL2)") (class "Default")
      (node (ref "D08") (pin "L2") (pinfunction "L2_L2") (pintype "output"))
    )
    (net (code "1848") (name "unconnected-(D08-PadM2)") (class "Default")
      (node (ref "D08") (pin "M2") (pinfunction "M2_M2") (pintype "output"))
    )
    (net (code "1849") (name "unconnected-(D08-PadN2)") (class "Default")
      (node (ref "D08") (pin "N2") (pinfunction "N2_N2") (pintype "output"))
    )
    (net (code "1850") (name "unconnected-(D08-PadP2)") (class "Default")
      (node (ref "D08") (pin "P2") (pinfunction "P2_P2") (pintype "output"))
    )
    (net (code "1851") (name "unconnected-(D08-PadS2)") (class "Default")
      (node (ref "D08") (pin "S2") (pinfunction "S2_S2") (pintype "output"))
    )
    (net (code "1852") (name "unconnected-(D08-PadT2)") (class "Default")
      (node (ref "D08") (pin "T2") (pinfunction "T2_T2") (pintype "output"))
    )
    (net (code "1853") (name "unconnected-(D08-PadU2)") (class "Default")
      (node (ref "D08") (pin "U2") (pinfunction "U2_U2") (pintype "output"))
    )
    (net (code "1854") (name "unconnected-(D08-PadV2)") (class "Default")
      (node (ref "D08") (pin "V2") (pinfunction "V2_V2") (pintype "output"))
    )
    (net (code "1855") (name "unconnected-(D24H-0-PadV1)") (class "Default")
      (node (ref "D24") (pin "V1") (pinfunction "0_V1") (pintype "output"))
    )
    (net (code "1856") (name "unconnected-(E16-PadJ2)") (class "Default")
      (node (ref "E16") (pin "J2") (pinfunction "J2_J2") (pintype "output"))
    )
    (net (code "1857") (name "unconnected-(E16-PadK2)") (class "Default")
      (node (ref "E16") (pin "K2") (pinfunction "K2_K2") (pintype "output"))
    )
    (net (code "1858") (name "unconnected-(E16-PadL2)") (class "Default")
      (node (ref "E16") (pin "L2") (pinfunction "L2_L2") (pintype "output"))
    )
    (net (code "1859") (name "unconnected-(E16-PadM2)") (class "Default")
      (node (ref "E16") (pin "M2") (pinfunction "M2_M2") (pintype "output"))
    )
    (net (code "1860") (name "unconnected-(E16-PadN2)") (class "Default")
      (node (ref "E16") (pin "N2") (pinfunction "N2_N2") (pintype "output"))
    )
    (net (code "1861") (name "unconnected-(E16-PadP2)") (class "Default")
      (node (ref "E16") (pin "P2") (pinfunction "P2_P2") (pintype "output"))
    )
    (net (code "1862") (name "unconnected-(E16-PadS2)") (class "Default")
      (node (ref "E16") (pin "S2") (pinfunction "S2_S2") (pintype "output"))
    )
    (net (code "1863") (name "unconnected-(E16-PadT2)") (class "Default")
      (node (ref "E16") (pin "T2") (pinfunction "T2_T2") (pintype "output"))
    )
    (net (code "1864") (name "unconnected-(E16-PadU2)") (class "Default")
      (node (ref "E16") (pin "U2") (pinfunction "U2_U2") (pintype "output"))
    )
    (net (code "1865") (name "unconnected-(E16-PadV2)") (class "Default")
      (node (ref "E16") (pin "V2") (pinfunction "V2_V2") (pintype "output"))
    )
    (net (code "1866") (name "unconnected-(E17-PadJ2)") (class "Default")
      (node (ref "E17") (pin "J2") (pinfunction "J2_J2") (pintype "output"))
    )
    (net (code "1867") (name "unconnected-(E17-PadK2)") (class "Default")
      (node (ref "E17") (pin "K2") (pinfunction "K2_K2") (pintype "output"))
    )
    (net (code "1868") (name "unconnected-(E17-PadL2)") (class "Default")
      (node (ref "E17") (pin "L2") (pinfunction "L2_L2") (pintype "output"))
    )
    (net (code "1869") (name "unconnected-(E17-PadN2)") (class "Default")
      (node (ref "E17") (pin "N2") (pinfunction "N2_N2") (pintype "output"))
    )
    (net (code "1870") (name "unconnected-(E17-PadP2)") (class "Default")
      (node (ref "E17") (pin "P2") (pinfunction "P2_P2") (pintype "output"))
    )
    (net (code "1871") (name "unconnected-(E17-PadR2)") (class "Default")
      (node (ref "E17") (pin "R2") (pinfunction "R2_R2") (pintype "output"))
    )
    (net (code "1872") (name "unconnected-(E17-PadS2)") (class "Default")
      (node (ref "E17") (pin "S2") (pinfunction "S2_S2") (pintype "output"))
    )
    (net (code "1873") (name "unconnected-(E17-PadT2)") (class "Default")
      (node (ref "E17") (pin "T2") (pinfunction "T2_T2") (pintype "output"))
    )
    (net (code "1874") (name "unconnected-(E17-PadV2)") (class "Default")
      (node (ref "E17") (pin "V2") (pinfunction "V2_V2") (pintype "output"))
    )
    (net (code "1875") (name "unconnected-(E18D-0-PadJ2)") (class "Default")
      (node (ref "E18") (pin "J2") (pinfunction "0_J2") (pintype "output"))
    )
    (net (code "1876") (name "unconnected-(E18E-1-PadL1)") (class "Default")
      (node (ref "E18") (pin "L1") (pinfunction "1_L1") (pintype "output"))
    )
    (net (code "1877") (name "unconnected-(E18G-0-PadU1)") (class "Default")
      (node (ref "E18") (pin "U1") (pinfunction "0_U1") (pintype "output"))
    )
    (net (code "1878") (name "unconnected-(E19A-0-PadF1)") (class "Default")
      (node (ref "E19") (pin "F1") (pinfunction "0_F1") (pintype "output"))
    )
    (net (code "1879") (name "unconnected-(E20F-0-PadR2)") (class "Default")
      (node (ref "E20") (pin "R2") (pinfunction "0_R2") (pintype "output"))
    )
    (net (code "1880") (name "unconnected-(E20G-0-PadU1)") (class "Default")
      (node (ref "E20") (pin "U1") (pinfunction "0_U1") (pintype "output"))
    )
    (net (code "1881") (name "unconnected-(E22N-OUT-PadV2)") (class "Default")
      (node (ref "E22") (pin "V2") (pinfunction "OUT_V2") (pintype "output"))
    )
    (net (code "1882") (name "unconnected-(E23A-1-PadE1)") (class "Default")
      (node (ref "E23") (pin "E1") (pinfunction "1_E1") (pintype "output"))
    )
    (net (code "1883") (name "unconnected-(E23E-1-PadL1)") (class "Default")
      (node (ref "E23") (pin "L1") (pinfunction "1_L1") (pintype "output"))
    )
    (net (code "1884") (name "unconnected-(E33A-0-PadF1)") (class "Default")
      (node (ref "E33") (pin "F1") (pinfunction "0_F1") (pintype "output"))
    )
    (net (code "1885") (name "unconnected-(E33D-0-PadJ2)") (class "Default")
      (node (ref "E33") (pin "J2") (pinfunction "0_J2") (pintype "output"))
    )
    (net (code "1886") (name "unconnected-(E33E-1-PadL1)") (class "Default")
      (node (ref "E33") (pin "L1") (pinfunction "1_L1") (pintype "output"))
    )
    (net (code "1887") (name "unconnected-(E33F-1-PadP2)") (class "Default")
      (node (ref "E33") (pin "P2") (pinfunction "1_P2") (pintype "output"))
    )
    (net (code "1888") (name "unconnected-(EF01-PadAD1)") (class "Default")
      (node (ref "EF01") (pin "AD1") (pinfunction "AD1_AD1") (pintype "output"))
    )
    (net (code "1889") (name "unconnected-(EF01-PadAS1)") (class "Default")
      (node (ref "EF01") (pin "AS1") (pinfunction "AS1_AS1") (pintype "output"))
    )
    (net (code "1890") (name "unconnected-(EF01-PadBK2)") (class "Default")
      (node (ref "EF01") (pin "BK2") (pinfunction "BK2_BK2") (pintype "output"))
    )
    (net (code "1891") (name "unconnected-(EF01-PadBN2)") (class "Default")
      (node (ref "EF01") (pin "BN2") (pinfunction "BN2_BN2") (pintype "output"))
    )
    (net (code "1892") (name "unconnected-(EF01-PadBS1)") (class "Default")
      (node (ref "EF01") (pin "BS1") (pinfunction "BS1_BS1") (pintype "output"))
    )
    (net (code "1893") (name "unconnected-(EF01-PadBS2)") (class "Default")
      (node (ref "EF01") (pin "BS2") (pinfunction "BS2_BS2") (pintype "output"))
    )
    (net (code "1894") (name "unconnected-(EF01-PadBU2)") (class "Default")
      (node (ref "EF01") (pin "BU2") (pinfunction "BU2_BU2") (pintype "output"))
    )
    (net (code "1895") (name "unconnected-(EF02-PadAD1)") (class "Default")
      (node (ref "EF02") (pin "AD1") (pinfunction "AD1_AD1") (pintype "output"))
    )
    (net (code "1896") (name "unconnected-(EF02-PadAD2)") (class "Default")
      (node (ref "EF02") (pin "AD2") (pinfunction "AD2_AD2") (pintype "output"))
    )
    (net (code "1897") (name "unconnected-(EF02-PadAJ1)") (class "Default")
      (node (ref "EF02") (pin "AJ1") (pinfunction "AJ1_AJ1") (pintype "output"))
    )
    (net (code "1898") (name "unconnected-(EF02-PadAR1)") (class "Default")
      (node (ref "EF02") (pin "AR1") (pinfunction "AR1_AR1") (pintype "output"))
    )
    (net (code "1899") (name "unconnected-(EF02-PadBP1)") (class "Default")
      (node (ref "EF02") (pin "BP1") (pinfunction "BP1_BP1") (pintype "output"))
    )
    (net (code "1900") (name "unconnected-(EF02-PadBR2)") (class "Default")
      (node (ref "EF02") (pin "BR2") (pinfunction "BR2_BR2") (pintype "output"))
    )
    (net (code "1901") (name "unconnected-(EF10C-CN2-PadAN2)") (class "Default")
      (node (ref "EF10") (pin "AN2") (pinfunction "CN2_AN2") (pintype "output"))
    )
    (net (code "1902") (name "unconnected-(EF34-PadAJ1)") (class "Default")
      (node (ref "EF34") (pin "AJ1") (pinfunction "AJ1_AJ1") (pintype "output"))
    )
    (net (code "1903") (name "unconnected-(EF34-PadAK2)") (class "Default")
      (node (ref "EF34") (pin "AK2") (pinfunction "AK2_AK2") (pintype "output"))
    )
    (net (code "1904") (name "unconnected-(EF34-PadAN1)") (class "Default")
      (node (ref "EF34") (pin "AN1") (pinfunction "AN1_AN1") (pintype "output"))
    )
    (net (code "1905") (name "unconnected-(EF34-PadAP1)") (class "Default")
      (node (ref "EF34") (pin "AP1") (pinfunction "AP1_AP1") (pintype "output"))
    )
    (net (code "1906") (name "unconnected-(EF35-PadAJ1)") (class "Default")
      (node (ref "EF35") (pin "AJ1") (pinfunction "AJ1_AJ1") (pintype "output"))
    )
    (net (code "1907") (name "unconnected-(EF35-PadAK2)") (class "Default")
      (node (ref "EF35") (pin "AK2") (pinfunction "AK2_AK2") (pintype "output"))
    )
    (net (code "1908") (name "unconnected-(EF35-PadAN1)") (class "Default")
      (node (ref "EF35") (pin "AN1") (pinfunction "AN1_AN1") (pintype "output"))
    )
    (net (code "1909") (name "unconnected-(EF35-PadAP1)") (class "Default")
      (node (ref "EF35") (pin "AP1") (pinfunction "AP1_AP1") (pintype "output"))
    )
    (net (code "1910") (name "unconnected-(EF36-PadAJ1)") (class "Default")
      (node (ref "EF36") (pin "AJ1") (pinfunction "AJ1_AJ1") (pintype "output"))
    )
    (net (code "1911") (name "unconnected-(EF36-PadAK2)") (class "Default")
      (node (ref "EF36") (pin "AK2") (pinfunction "AK2_AK2") (pintype "output"))
    )
    (net (code "1912") (name "unconnected-(EF36-PadAN1)") (class "Default")
      (node (ref "EF36") (pin "AN1") (pinfunction "AN1_AN1") (pintype "output"))
    )
    (net (code "1913") (name "unconnected-(EF36-PadAP1)") (class "Default")
      (node (ref "EF36") (pin "AP1") (pinfunction "AP1_AP1") (pintype "output"))
    )
    (net (code "1914") (name "unconnected-(EF37-PadAJ1)") (class "Default")
      (node (ref "EF37") (pin "AJ1") (pinfunction "AJ1_AJ1") (pintype "output"))
    )
    (net (code "1915") (name "unconnected-(EF37-PadAK2)") (class "Default")
      (node (ref "EF37") (pin "AK2") (pinfunction "AK2_AK2") (pintype "output"))
    )
    (net (code "1916") (name "unconnected-(EF37-PadAN1)") (class "Default")
      (node (ref "EF37") (pin "AN1") (pinfunction "AN1_AN1") (pintype "output"))
    )
    (net (code "1917") (name "unconnected-(EF37-PadAP1)") (class "Default")
      (node (ref "EF37") (pin "AP1") (pinfunction "AP1_AP1") (pintype "output"))
    )
    (net (code "1918") (name "unconnected-(EF38-PadAJ1)") (class "Default")
      (node (ref "EF38") (pin "AJ1") (pinfunction "AJ1_AJ1") (pintype "output"))
    )
    (net (code "1919") (name "unconnected-(EF38-PadAK2)") (class "Default")
      (node (ref "EF38") (pin "AK2") (pinfunction "AK2_AK2") (pintype "output"))
    )
    (net (code "1920") (name "unconnected-(EF38-PadAN1)") (class "Default")
      (node (ref "EF38") (pin "AN1") (pinfunction "AN1_AN1") (pintype "output"))
    )
    (net (code "1921") (name "unconnected-(EF38-PadAP1)") (class "Default")
      (node (ref "EF38") (pin "AP1") (pinfunction "AP1_AP1") (pintype "output"))
    )
    (net (code "1922") (name "unconnected-(EF39-PadAJ1)") (class "Default")
      (node (ref "EF39") (pin "AJ1") (pinfunction "AJ1_AJ1") (pintype "output"))
    )
    (net (code "1923") (name "unconnected-(EF39-PadAK2)") (class "Default")
      (node (ref "EF39") (pin "AK2") (pinfunction "AK2_AK2") (pintype "output"))
    )
    (net (code "1924") (name "unconnected-(EF39-PadAN1)") (class "Default")
      (node (ref "EF39") (pin "AN1") (pinfunction "AN1_AN1") (pintype "output"))
    )
    (net (code "1925") (name "unconnected-(EF39-PadAP1)") (class "Default")
      (node (ref "EF39") (pin "AP1") (pinfunction "AP1_AP1") (pintype "output"))
    )
    (net (code "1926") (name "unconnected-(F03-PadL2)") (class "Default")
      (node (ref "F03") (pin "L2") (pinfunction "L2_L2") (pintype "output"))
    )
    (net (code "1927") (name "unconnected-(F03-PadM2)") (class "Default")
      (node (ref "F03") (pin "M2") (pinfunction "M2_M2") (pintype "output"))
    )
    (net (code "1928") (name "unconnected-(F03-PadN2)") (class "Default")
      (node (ref "F03") (pin "N2") (pinfunction "N2_N2") (pintype "output"))
    )
    (net (code "1929") (name "unconnected-(F12-PadJ2)") (class "Default")
      (node (ref "F12") (pin "J2") (pinfunction "J2_J2") (pintype "output"))
    )
    (net (code "1930") (name "unconnected-(F12-PadK2)") (class "Default")
      (node (ref "F12") (pin "K2") (pinfunction "K2_K2") (pintype "output"))
    )
    (net (code "1931") (name "unconnected-(F12-PadL2)") (class "Default")
      (node (ref "F12") (pin "L2") (pinfunction "L2_L2") (pintype "output"))
    )
    (net (code "1932") (name "unconnected-(F12-PadM2)") (class "Default")
      (node (ref "F12") (pin "M2") (pinfunction "M2_M2") (pintype "output"))
    )
    (net (code "1933") (name "unconnected-(F12-PadN2)") (class "Default")
      (node (ref "F12") (pin "N2") (pinfunction "N2_N2") (pintype "output"))
    )
    (net (code "1934") (name "unconnected-(F12-PadP2)") (class "Default")
      (node (ref "F12") (pin "P2") (pinfunction "P2_P2") (pintype "output"))
    )
    (net (code "1935") (name "unconnected-(F12-PadR2)") (class "Default")
      (node (ref "F12") (pin "R2") (pinfunction "R2_R2") (pintype "output"))
    )
    (net (code "1936") (name "unconnected-(F12-PadS2)") (class "Default")
      (node (ref "F12") (pin "S2") (pinfunction "S2_S2") (pintype "output"))
    )
    (net (code "1937") (name "unconnected-(F12-PadU2)") (class "Default")
      (node (ref "F12") (pin "U2") (pinfunction "U2_U2") (pintype "output"))
    )
    (net (code "1938") (name "unconnected-(F12-PadV2)") (class "Default")
      (node (ref "F12") (pin "V2") (pinfunction "V2_V2") (pintype "output"))
    )
    (net (code "1939") (name "unconnected-(F13-PadJ2)") (class "Default")
      (node (ref "F13") (pin "J2") (pinfunction "J2_J2") (pintype "output"))
    )
    (net (code "1940") (name "unconnected-(F13-PadK2)") (class "Default")
      (node (ref "F13") (pin "K2") (pinfunction "K2_K2") (pintype "output"))
    )
    (net (code "1941") (name "unconnected-(F13-PadL2)") (class "Default")
      (node (ref "F13") (pin "L2") (pinfunction "L2_L2") (pintype "output"))
    )
    (net (code "1942") (name "unconnected-(F13-PadN2)") (class "Default")
      (node (ref "F13") (pin "N2") (pinfunction "N2_N2") (pintype "output"))
    )
    (net (code "1943") (name "unconnected-(F13-PadP2)") (class "Default")
      (node (ref "F13") (pin "P2") (pinfunction "P2_P2") (pintype "output"))
    )
    (net (code "1944") (name "unconnected-(F13-PadR2)") (class "Default")
      (node (ref "F13") (pin "R2") (pinfunction "R2_R2") (pintype "output"))
    )
    (net (code "1945") (name "unconnected-(F13-PadS2)") (class "Default")
      (node (ref "F13") (pin "S2") (pinfunction "S2_S2") (pintype "output"))
    )
    (net (code "1946") (name "unconnected-(F13-PadU2)") (class "Default")
      (node (ref "F13") (pin "U2") (pinfunction "U2_U2") (pintype "output"))
    )
    (net (code "1947") (name "unconnected-(F13-PadV2)") (class "Default")
      (node (ref "F13") (pin "V2") (pinfunction "V2_V2") (pintype "output"))
    )
    (net (code "1948") (name "unconnected-(F14-PadJ2)") (class "Default")
      (node (ref "F14") (pin "J2") (pinfunction "J2_J2") (pintype "output"))
    )
    (net (code "1949") (name "unconnected-(F14-PadK2)") (class "Default")
      (node (ref "F14") (pin "K2") (pinfunction "K2_K2") (pintype "output"))
    )
    (net (code "1950") (name "unconnected-(F14-PadL2)") (class "Default")
      (node (ref "F14") (pin "L2") (pinfunction "L2_L2") (pintype "output"))
    )
    (net (code "1951") (name "unconnected-(F14-PadM2)") (class "Default")
      (node (ref "F14") (pin "M2") (pinfunction "M2_M2") (pintype "output"))
    )
    (net (code "1952") (name "unconnected-(F14-PadN2)") (class "Default")
      (node (ref "F14") (pin "N2") (pinfunction "N2_N2") (pintype "output"))
    )
    (net (code "1953") (name "unconnected-(F14-PadP2)") (class "Default")
      (node (ref "F14") (pin "P2") (pinfunction "P2_P2") (pintype "output"))
    )
    (net (code "1954") (name "unconnected-(F14-PadR2)") (class "Default")
      (node (ref "F14") (pin "R2") (pinfunction "R2_R2") (pintype "output"))
    )
    (net (code "1955") (name "unconnected-(F14-PadU2)") (class "Default")
      (node (ref "F14") (pin "U2") (pinfunction "U2_U2") (pintype "output"))
    )
    (net (code "1956") (name "unconnected-(F14-PadV2)") (class "Default")
      (node (ref "F14") (pin "V2") (pinfunction "V2_V2") (pintype "output"))
    )
    (net (code "1957") (name "unconnected-(F15-PadJ2)") (class "Default")
      (node (ref "F15") (pin "J2") (pinfunction "J2_J2") (pintype "output"))
    )
    (net (code "1958") (name "unconnected-(F15-PadK2)") (class "Default")
      (node (ref "F15") (pin "K2") (pinfunction "K2_K2") (pintype "output"))
    )
    (net (code "1959") (name "unconnected-(F15-PadL2)") (class "Default")
      (node (ref "F15") (pin "L2") (pinfunction "L2_L2") (pintype "output"))
    )
    (net (code "1960") (name "unconnected-(F15-PadN2)") (class "Default")
      (node (ref "F15") (pin "N2") (pinfunction "N2_N2") (pintype "output"))
    )
    (net (code "1961") (name "unconnected-(F15-PadP2)") (class "Default")
      (node (ref "F15") (pin "P2") (pinfunction "P2_P2") (pintype "output"))
    )
    (net (code "1962") (name "unconnected-(F15-PadR2)") (class "Default")
      (node (ref "F15") (pin "R2") (pinfunction "R2_R2") (pintype "output"))
    )
    (net (code "1963") (name "unconnected-(F15-PadS2)") (class "Default")
      (node (ref "F15") (pin "S2") (pinfunction "S2_S2") (pintype "output"))
    )
    (net (code "1964") (name "unconnected-(F15-PadU2)") (class "Default")
      (node (ref "F15") (pin "U2") (pinfunction "U2_U2") (pintype "output"))
    )
    (net (code "1965") (name "unconnected-(F15-PadV2)") (class "Default")
      (node (ref "F15") (pin "V2") (pinfunction "V2_V2") (pintype "output"))
    )
    (net (code "1966") (name "unconnected-(F16-PadJ2)") (class "Default")
      (node (ref "F16") (pin "J2") (pinfunction "J2_J2") (pintype "output"))
    )
    (net (code "1967") (name "unconnected-(F16-PadK2)") (class "Default")
      (node (ref "F16") (pin "K2") (pinfunction "K2_K2") (pintype "output"))
    )
    (net (code "1968") (name "unconnected-(F16-PadL2)") (class "Default")
      (node (ref "F16") (pin "L2") (pinfunction "L2_L2") (pintype "output"))
    )
    (net (code "1969") (name "unconnected-(F16-PadM2)") (class "Default")
      (node (ref "F16") (pin "M2") (pinfunction "M2_M2") (pintype "output"))
    )
    (net (code "1970") (name "unconnected-(F16-PadN2)") (class "Default")
      (node (ref "F16") (pin "N2") (pinfunction "N2_N2") (pintype "output"))
    )
    (net (code "1971") (name "unconnected-(F16-PadP2)") (class "Default")
      (node (ref "F16") (pin "P2") (pinfunction "P2_P2") (pintype "output"))
    )
    (net (code "1972") (name "unconnected-(F16-PadR2)") (class "Default")
      (node (ref "F16") (pin "R2") (pinfunction "R2_R2") (pintype "output"))
    )
    (net (code "1973") (name "unconnected-(F16-PadU2)") (class "Default")
      (node (ref "F16") (pin "U2") (pinfunction "U2_U2") (pintype "output"))
    )
    (net (code "1974") (name "unconnected-(F16-PadV2)") (class "Default")
      (node (ref "F16") (pin "V2") (pinfunction "V2_V2") (pintype "output"))
    )
    (net (code "1975") (name "unconnected-(F17-PadJ2)") (class "Default")
      (node (ref "F17") (pin "J2") (pinfunction "J2_J2") (pintype "output"))
    )
    (net (code "1976") (name "unconnected-(F17-PadK2)") (class "Default")
      (node (ref "F17") (pin "K2") (pinfunction "K2_K2") (pintype "output"))
    )
    (net (code "1977") (name "unconnected-(F17-PadL2)") (class "Default")
      (node (ref "F17") (pin "L2") (pinfunction "L2_L2") (pintype "output"))
    )
    (net (code "1978") (name "unconnected-(F17-PadN2)") (class "Default")
      (node (ref "F17") (pin "N2") (pinfunction "N2_N2") (pintype "output"))
    )
    (net (code "1979") (name "unconnected-(F17-PadP2)") (class "Default")
      (node (ref "F17") (pin "P2") (pinfunction "P2_P2") (pintype "output"))
    )
    (net (code "1980") (name "unconnected-(F17-PadR2)") (class "Default")
      (node (ref "F17") (pin "R2") (pinfunction "R2_R2") (pintype "output"))
    )
    (net (code "1981") (name "unconnected-(F17-PadS2)") (class "Default")
      (node (ref "F17") (pin "S2") (pinfunction "S2_S2") (pintype "output"))
    )
    (net (code "1982") (name "unconnected-(F17-PadU2)") (class "Default")
      (node (ref "F17") (pin "U2") (pinfunction "U2_U2") (pintype "output"))
    )
    (net (code "1983") (name "unconnected-(F17-PadV2)") (class "Default")
      (node (ref "F17") (pin "V2") (pinfunction "V2_V2") (pintype "output"))
    )
    (net (code "1984") (name "unconnected-(F18-PadJ2)") (class "Default")
      (node (ref "F18") (pin "J2") (pinfunction "J2_J2") (pintype "output"))
    )
    (net (code "1985") (name "unconnected-(F18-PadK2)") (class "Default")
      (node (ref "F18") (pin "K2") (pinfunction "K2_K2") (pintype "output"))
    )
    (net (code "1986") (name "unconnected-(F18-PadL2)") (class "Default")
      (node (ref "F18") (pin "L2") (pinfunction "L2_L2") (pintype "output"))
    )
    (net (code "1987") (name "unconnected-(F18-PadM2)") (class "Default")
      (node (ref "F18") (pin "M2") (pinfunction "M2_M2") (pintype "output"))
    )
    (net (code "1988") (name "unconnected-(F18-PadN2)") (class "Default")
      (node (ref "F18") (pin "N2") (pinfunction "N2_N2") (pintype "output"))
    )
    (net (code "1989") (name "unconnected-(F18-PadP2)") (class "Default")
      (node (ref "F18") (pin "P2") (pinfunction "P2_P2") (pintype "output"))
    )
    (net (code "1990") (name "unconnected-(F18-PadR2)") (class "Default")
      (node (ref "F18") (pin "R2") (pinfunction "R2_R2") (pintype "output"))
    )
    (net (code "1991") (name "unconnected-(F18-PadU2)") (class "Default")
      (node (ref "F18") (pin "U2") (pinfunction "U2_U2") (pintype "output"))
    )
    (net (code "1992") (name "unconnected-(F18-PadV2)") (class "Default")
      (node (ref "F18") (pin "V2") (pinfunction "V2_V2") (pintype "output"))
    )
    (net (code "1993") (name "unconnected-(H30-PadD1)") (class "Default")
      (node (ref "H30") (pin "D1") (pinfunction "D1_D1") (pintype "output"))
    )
    (net (code "1994") (name "unconnected-(H30-PadE1)") (class "Default")
      (node (ref "H30") (pin "E1") (pinfunction "E1_E1") (pintype "output"))
    )
    (net (code "1995") (name "unconnected-(H30-PadK1)") (class "Default")
      (node (ref "H30") (pin "K1") (pinfunction "K1_K1") (pintype "output"))
    )
    (net (code "1996") (name "unconnected-(HJ26-PadAJ1)") (class "Default")
      (node (ref "HJ26") (pin "AJ1") (pinfunction "AJ1_AJ1") (pintype "output"))
    )
    (net (code "1997") (name "unconnected-(HJ26-PadAJ2)") (class "Default")
      (node (ref "HJ26") (pin "AJ2") (pinfunction "AJ2_AJ2") (pintype "output"))
    )
    (net (code "1998") (name "unconnected-(HJ26-PadAM2)") (class "Default")
      (node (ref "HJ26") (pin "AM2") (pinfunction "AM2_AM2") (pintype "output"))
    )
    (net (code "1999") (name "unconnected-(HJ26-PadAT2)") (class "Default")
      (node (ref "HJ26") (pin "AT2") (pinfunction "AT2_AT2") (pintype "output"))
    )
    (net (code "2000") (name "unconnected-(HJ27D-AM-PadAM2)") (class "Default")
      (node (ref "HJ27") (pin "AM2") (pinfunction "AM_AM2") (pintype "output"))
    )
    (net (code "2001") (name "unconnected-(HJ27D-AP-PadAP2)") (class "Default")
      (node (ref "HJ27") (pin "AP2") (pinfunction "AP_AP2") (pintype "output"))
    )
    (net (code "2002") (name "unconnected-(HJ28-PadAJ1)") (class "Default")
      (node (ref "HJ28") (pin "AJ1") (pinfunction "AJ1_AJ1") (pintype "output"))
    )
    (net (code "2003") (name "unconnected-(HJ28-PadAJ2)") (class "Default")
      (node (ref "HJ28") (pin "AJ2") (pinfunction "AJ2_AJ2") (pintype "output"))
    )
    (net (code "2004") (name "unconnected-(HJ28-PadAS1)") (class "Default")
      (node (ref "HJ28") (pin "AS1") (pinfunction "AS1_AS1") (pintype "output"))
    )
    (net (code "2005") (name "unconnected-(HJ28-PadAU2)") (class "Default")
      (node (ref "HJ28") (pin "AU2") (pinfunction "AU2_AU2") (pintype "output"))
    )
    (net (code "2006") (name "unconnected-(HJ29-PadAM2)") (class "Default")
      (node (ref "HJ29") (pin "AM2") (pinfunction "AM2_AM2") (pintype "output"))
    )
    (net (code "2007") (name "unconnected-(HJ29-PadAP2)") (class "Default")
      (node (ref "HJ29") (pin "AP2") (pinfunction "AP2_AP2") (pintype "output"))
    )
    (net (code "2008") (name "unconnected-(HJ29-PadAU2)") (class "Default")
      (node (ref "HJ29") (pin "AU2") (pinfunction "AU2_AU2") (pintype "output"))
    )
    (net (code "2009") (name "unconnected-(HJ29-PadBD2)") (class "Default")
      (node (ref "HJ29") (pin "BD2") (pinfunction "BD2_BD2") (pintype "output"))
    )
    (net (code "2010") (name "unconnected-(HJ29-PadBJ2)") (class "Default")
      (node (ref "HJ29") (pin "BJ2") (pinfunction "BJ2_BJ2") (pintype "output"))
    )
    (net (code "2011") (name "unconnected-(HJ29-PadBK2)") (class "Default")
      (node (ref "HJ29") (pin "BK2") (pinfunction "BK2_BK2") (pintype "output"))
    )
    (net (code "2012") (name "unconnected-(HJ29-PadBS2)") (class "Default")
      (node (ref "HJ29") (pin "BS2") (pinfunction "BS2_BS2") (pintype "output"))
    )
    (net (code "2013") (name "unconnected-(HJ31-PadAE2)") (class "Default")
      (node (ref "HJ31") (pin "AE2") (pinfunction "AE2_AE2") (pintype "output"))
    )
    (net (code "2014") (name "unconnected-(HJ31-PadBF1)") (class "Default")
      (node (ref "HJ31") (pin "BF1") (pinfunction "BF1_BF1") (pintype "output"))
    )
    (net (code "2015") (name "unconnected-(HJ31-PadBH1)") (class "Default")
      (node (ref "HJ31") (pin "BH1") (pinfunction "BH1_BH1") (pintype "output"))
    )
    (net (code "2016") (name "unconnected-(HJ31-PadBH2)") (class "Default")
      (node (ref "HJ31") (pin "BH2") (pinfunction "BH2_BH2") (pintype "output"))
    )
    (net (code "2017") (name "unconnected-(HJ31-PadBM1)") (class "Default")
      (node (ref "HJ31") (pin "BM1") (pinfunction "BM1_BM1") (pintype "output"))
    )
    (net (code "2018") (name "unconnected-(HJ31-PadBR1)") (class "Default")
      (node (ref "HJ31") (pin "BR1") (pinfunction "BR1_BR1") (pintype "output"))
    )
    (net (code "2019") (name "unconnected-(J33-PadH1)") (class "Default")
      (node (ref "J33") (pin "H1") (pinfunction "H1_H1") (pintype "output"))
    )
    (net (code "2020") (name "unconnected-(J33-PadJ2)") (class "Default")
      (node (ref "J33") (pin "J2") (pinfunction "J2_J2") (pintype "output"))
    )
    (net (code "2021") (name "unconnected-(J33-PadL1)") (class "Default")
      (node (ref "J33") (pin "L1") (pinfunction "L1_L1") (pintype "output"))
    )
    (net (code "2022") (name "unconnected-(J33-PadM1)") (class "Default")
      (node (ref "J33") (pin "M1") (pinfunction "M1_M1") (pintype "output"))
    )
    (net (code "2023") (name "unconnected-(J33-PadS1)") (class "Default")
      (node (ref "J33") (pin "S1") (pinfunction "S1_S1") (pintype "output"))
    )
    (net (code "2024") (name "unconnected-(J33-PadT2)") (class "Default")
      (node (ref "J33") (pin "T2") (pinfunction "T2_T2") (pintype "output"))
    )
    (net (code "2025") (name "unconnected-(J33-PadU1)") (class "Default")
      (node (ref "J33") (pin "U1") (pinfunction "U1_U1") (pintype "output"))
    )
  )
)
